# proto4-1pp.net
KiCad netlist of a schematic drawn in EAGLE
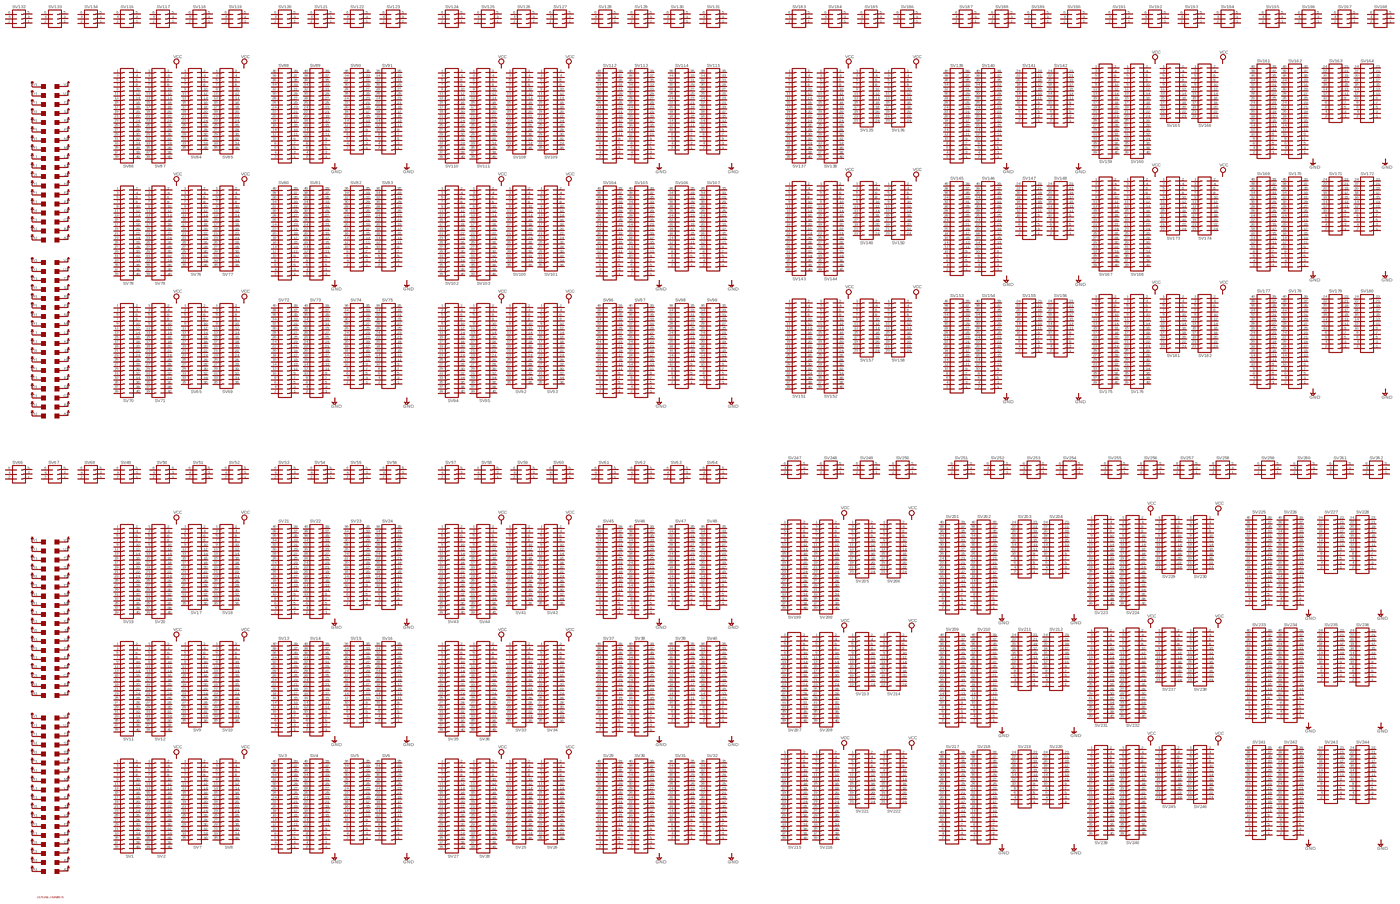
[diagram p0: schematic, sheet 1, overview]
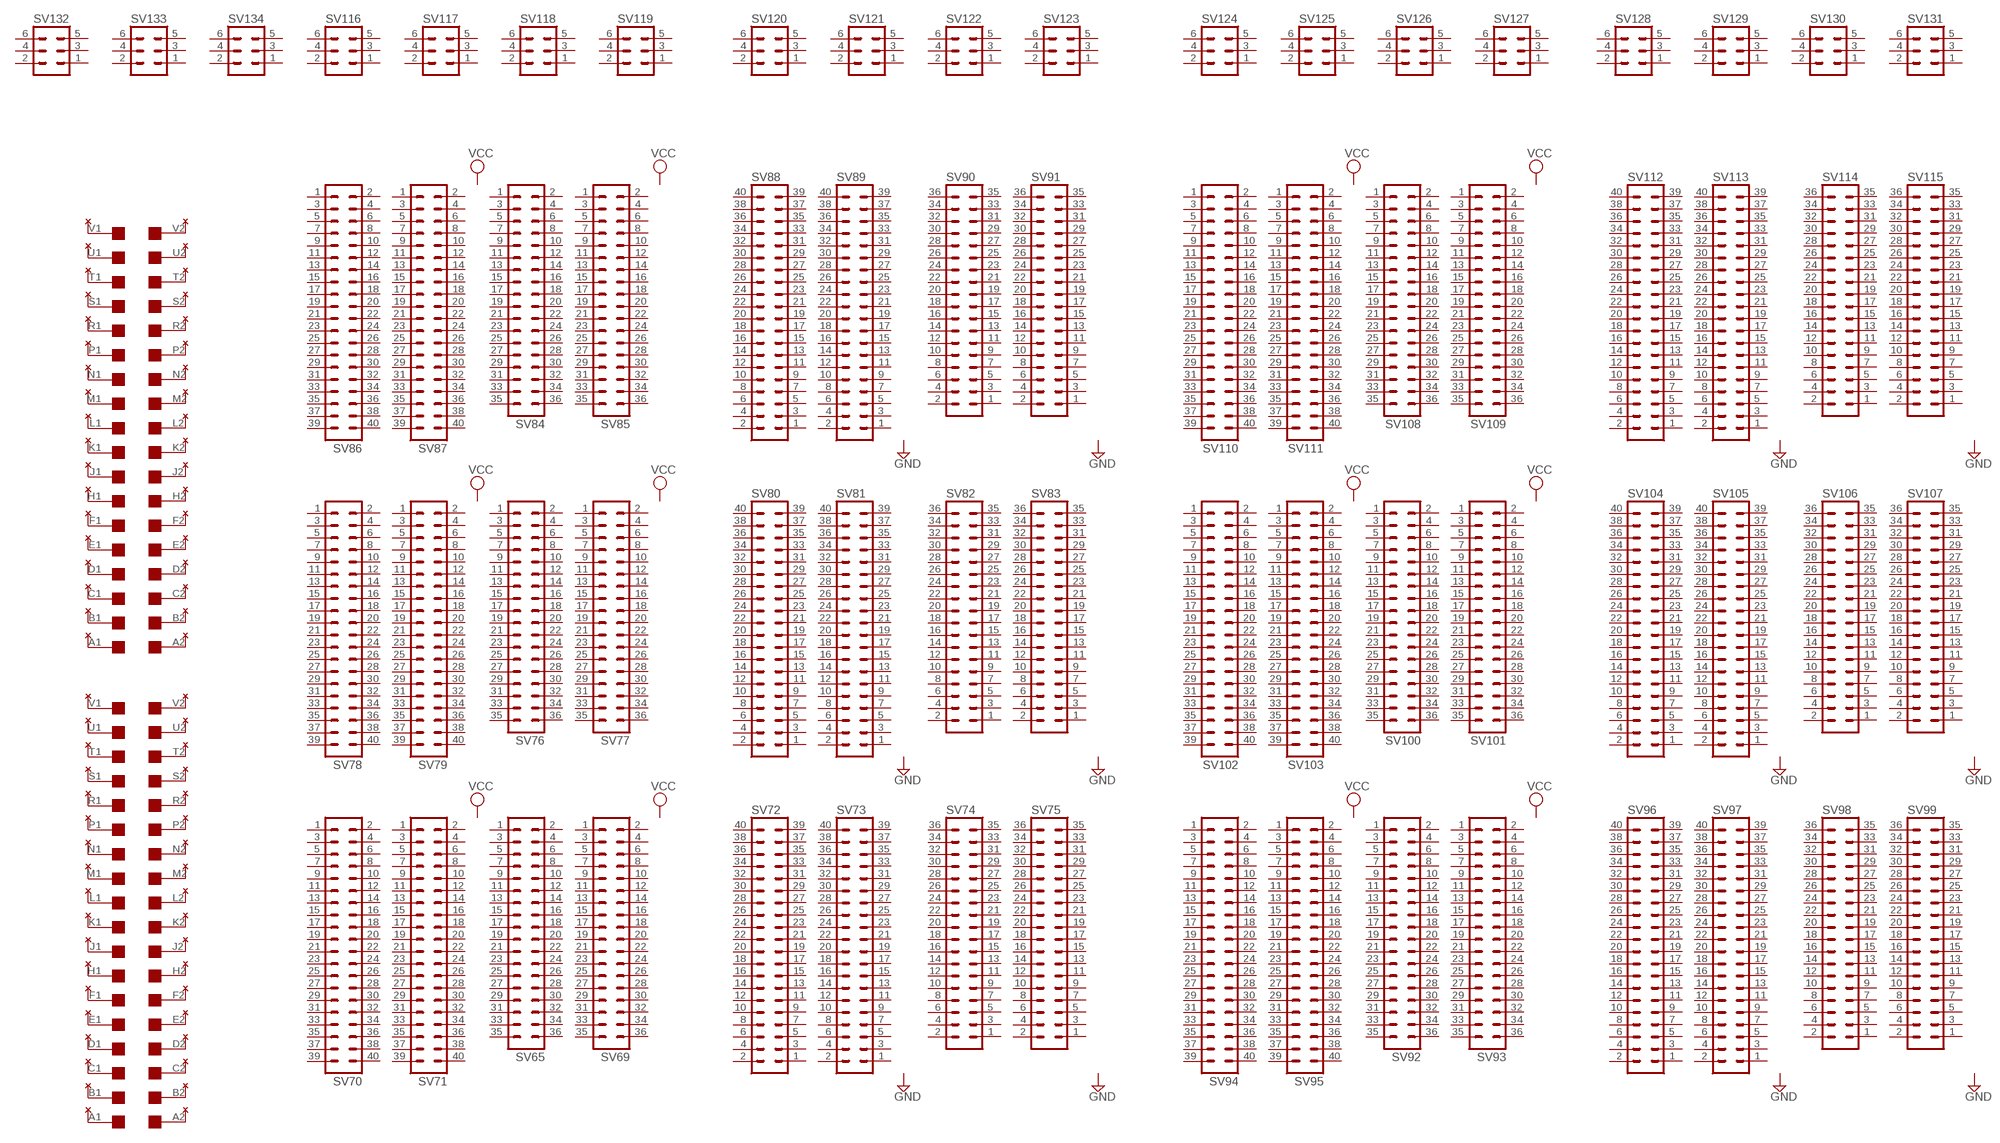
[diagram p1: schematic, sheet 1, part 1 of 4]
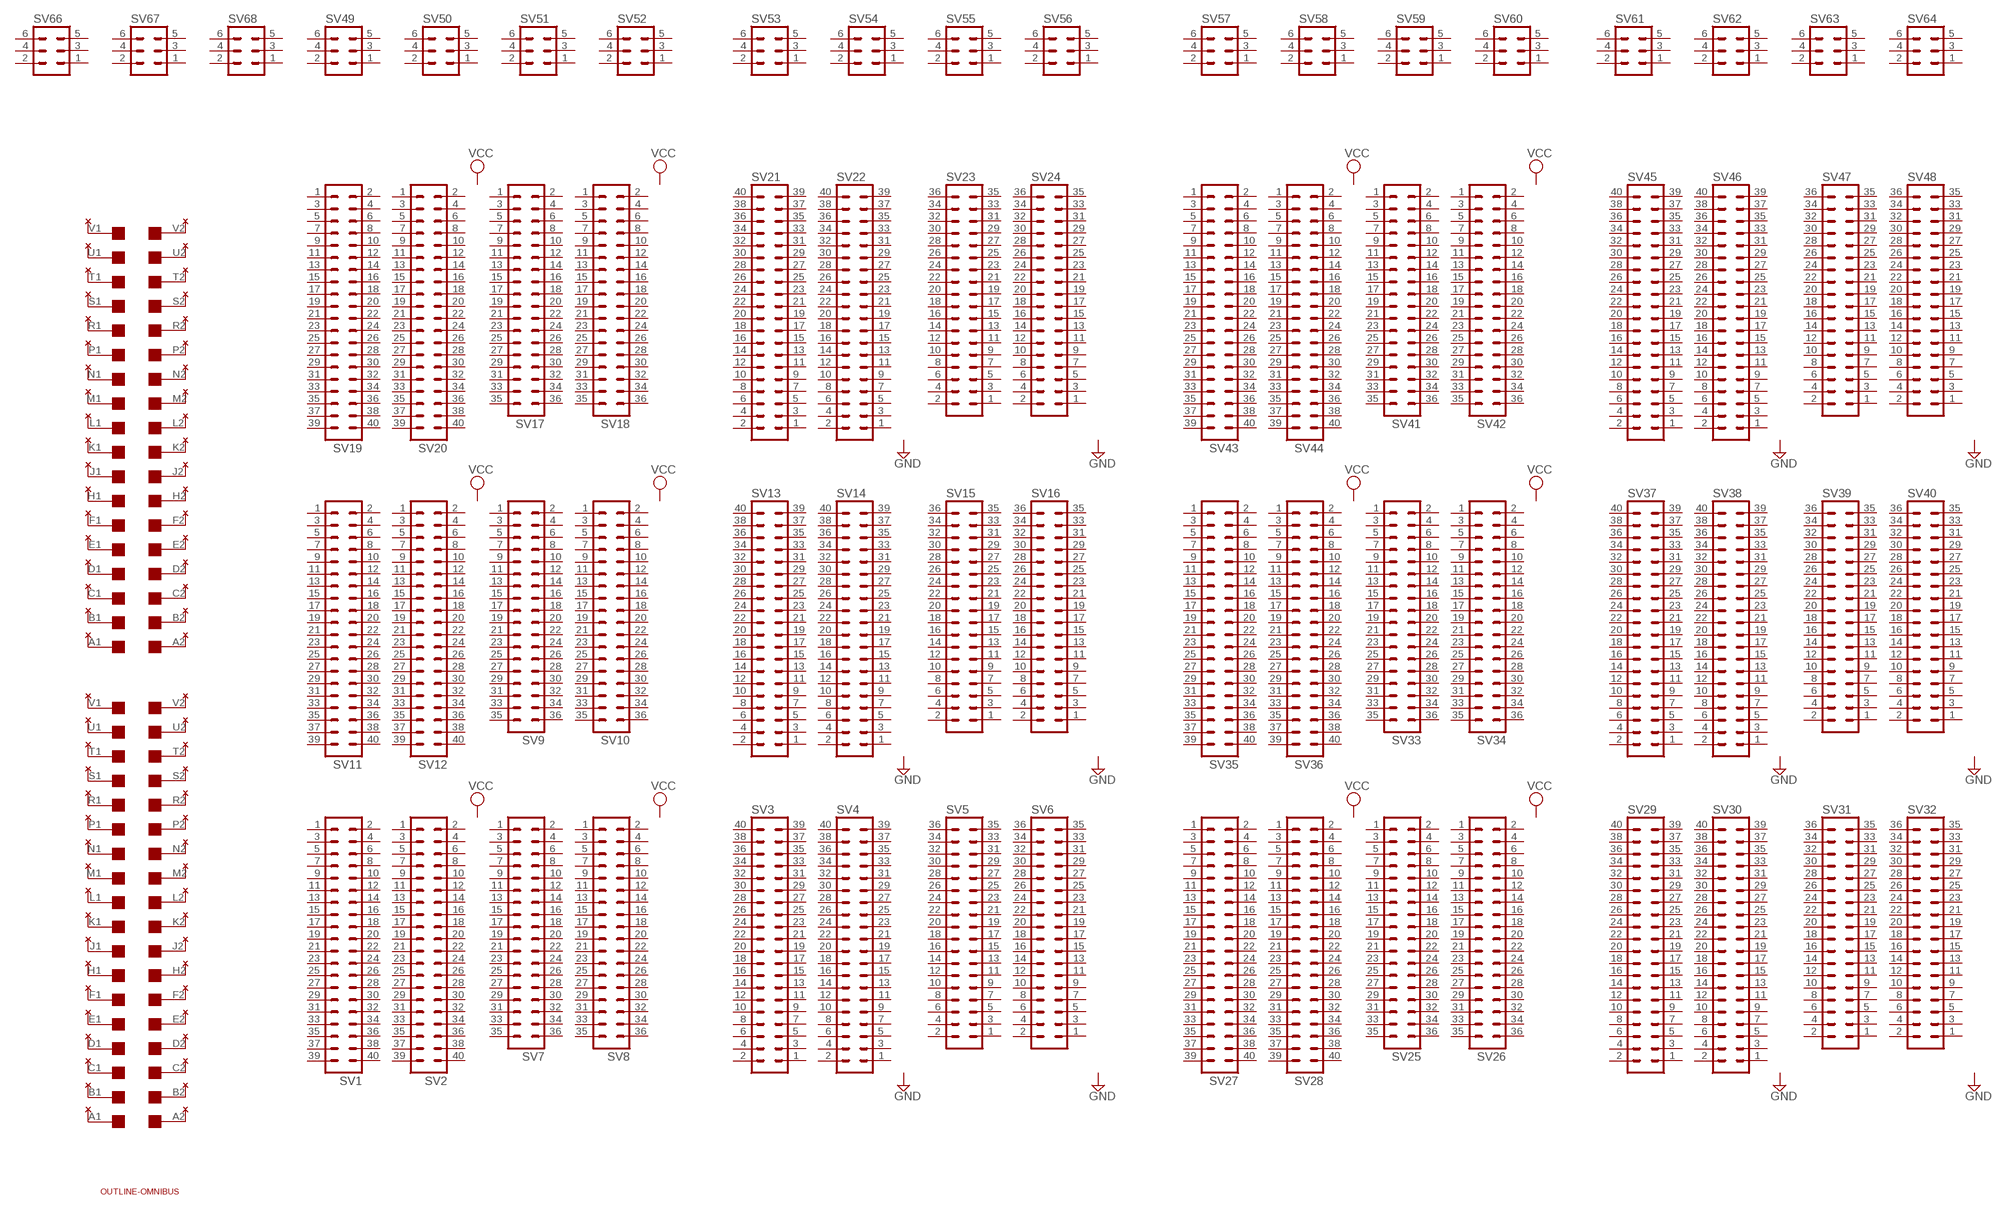
[diagram p2: schematic, sheet 1, part 2 of 4]
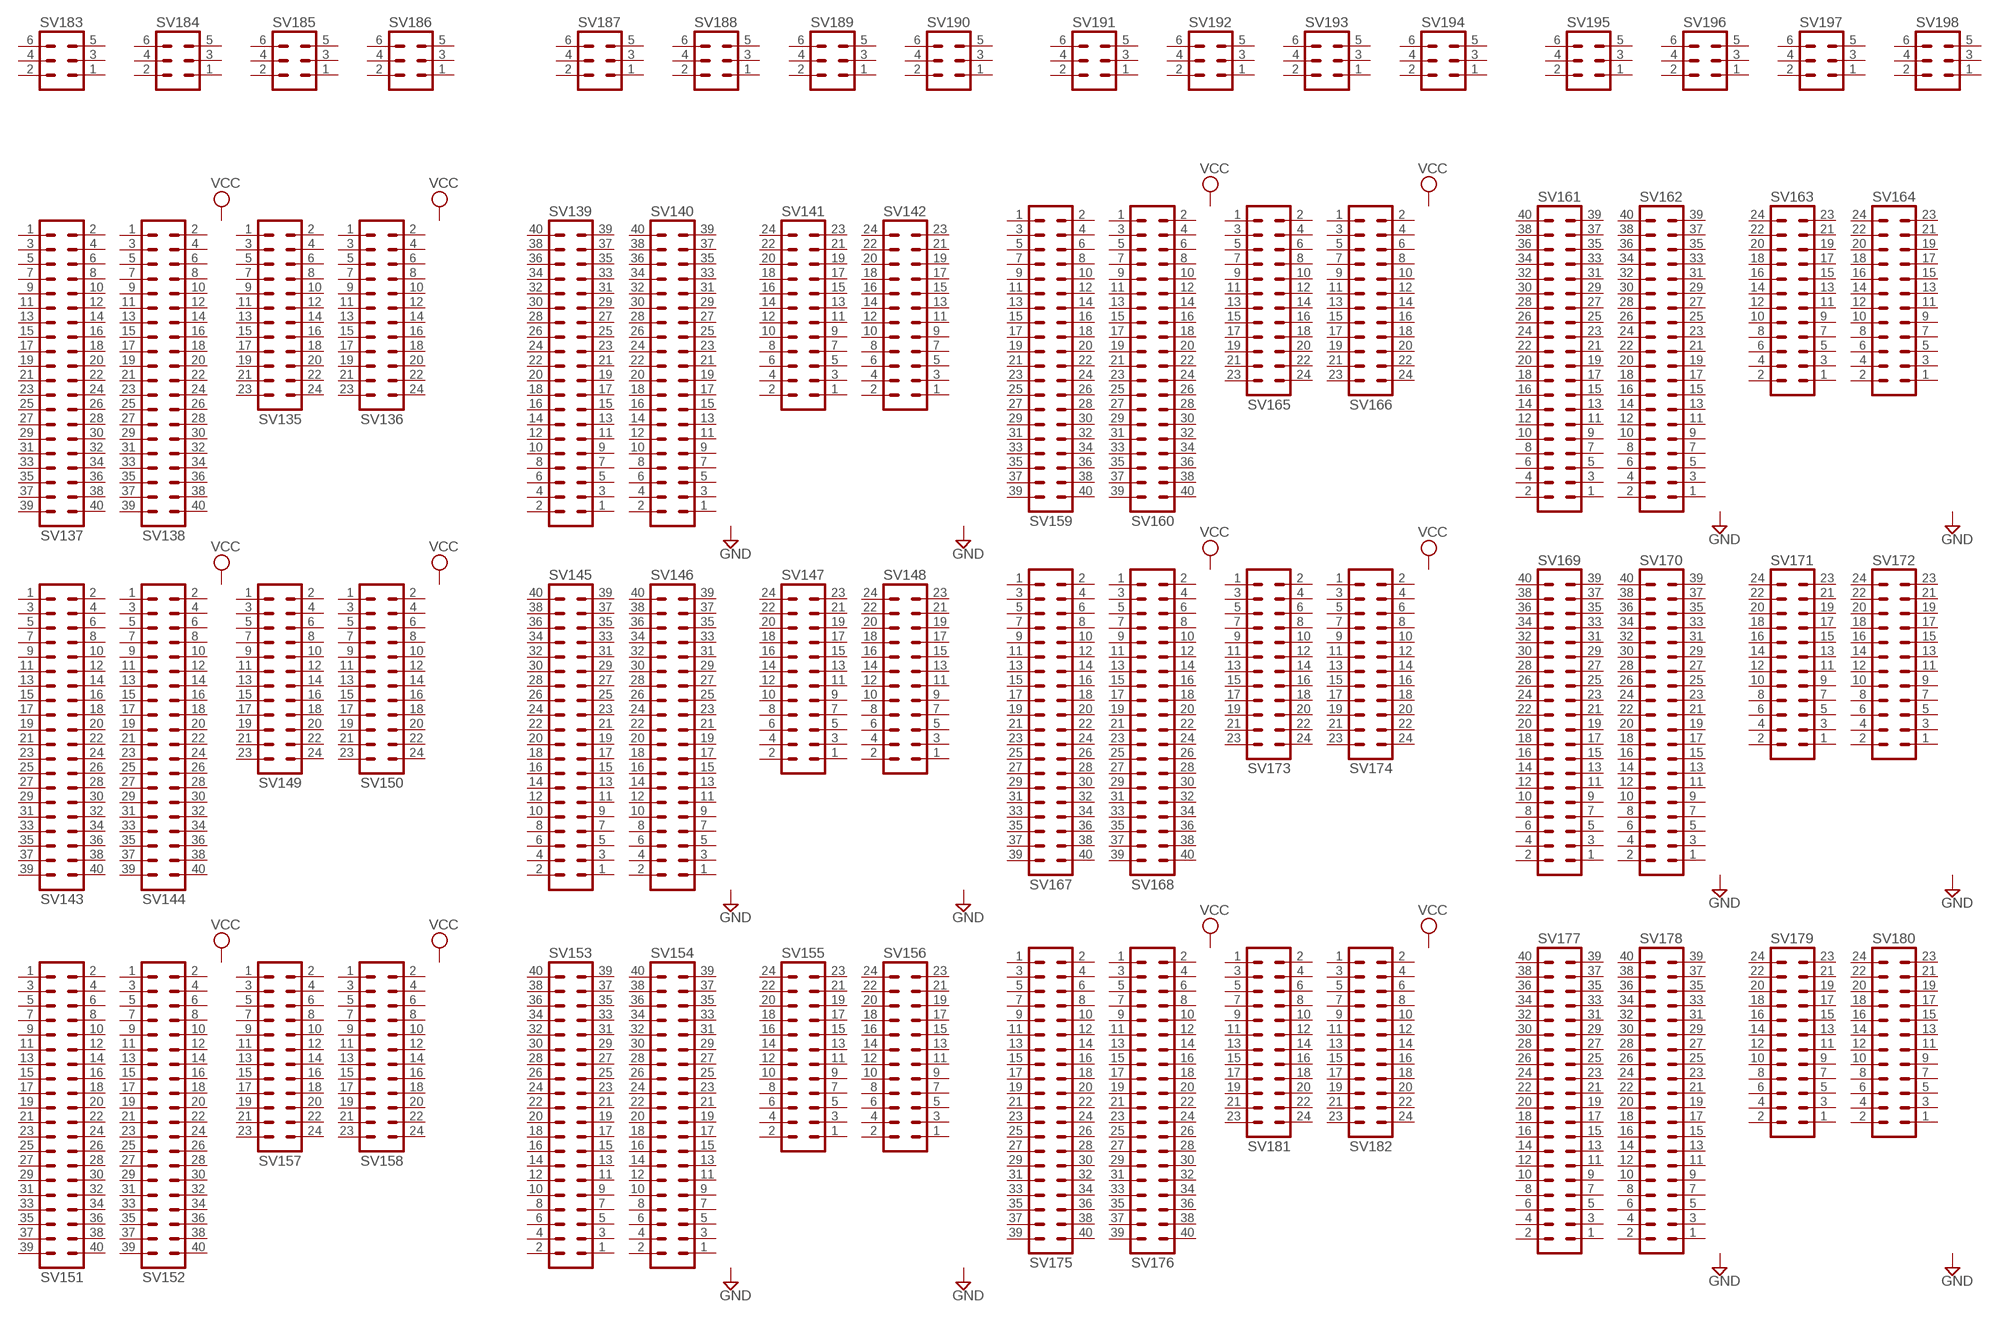
[diagram p3: schematic, sheet 1, part 3 of 4]
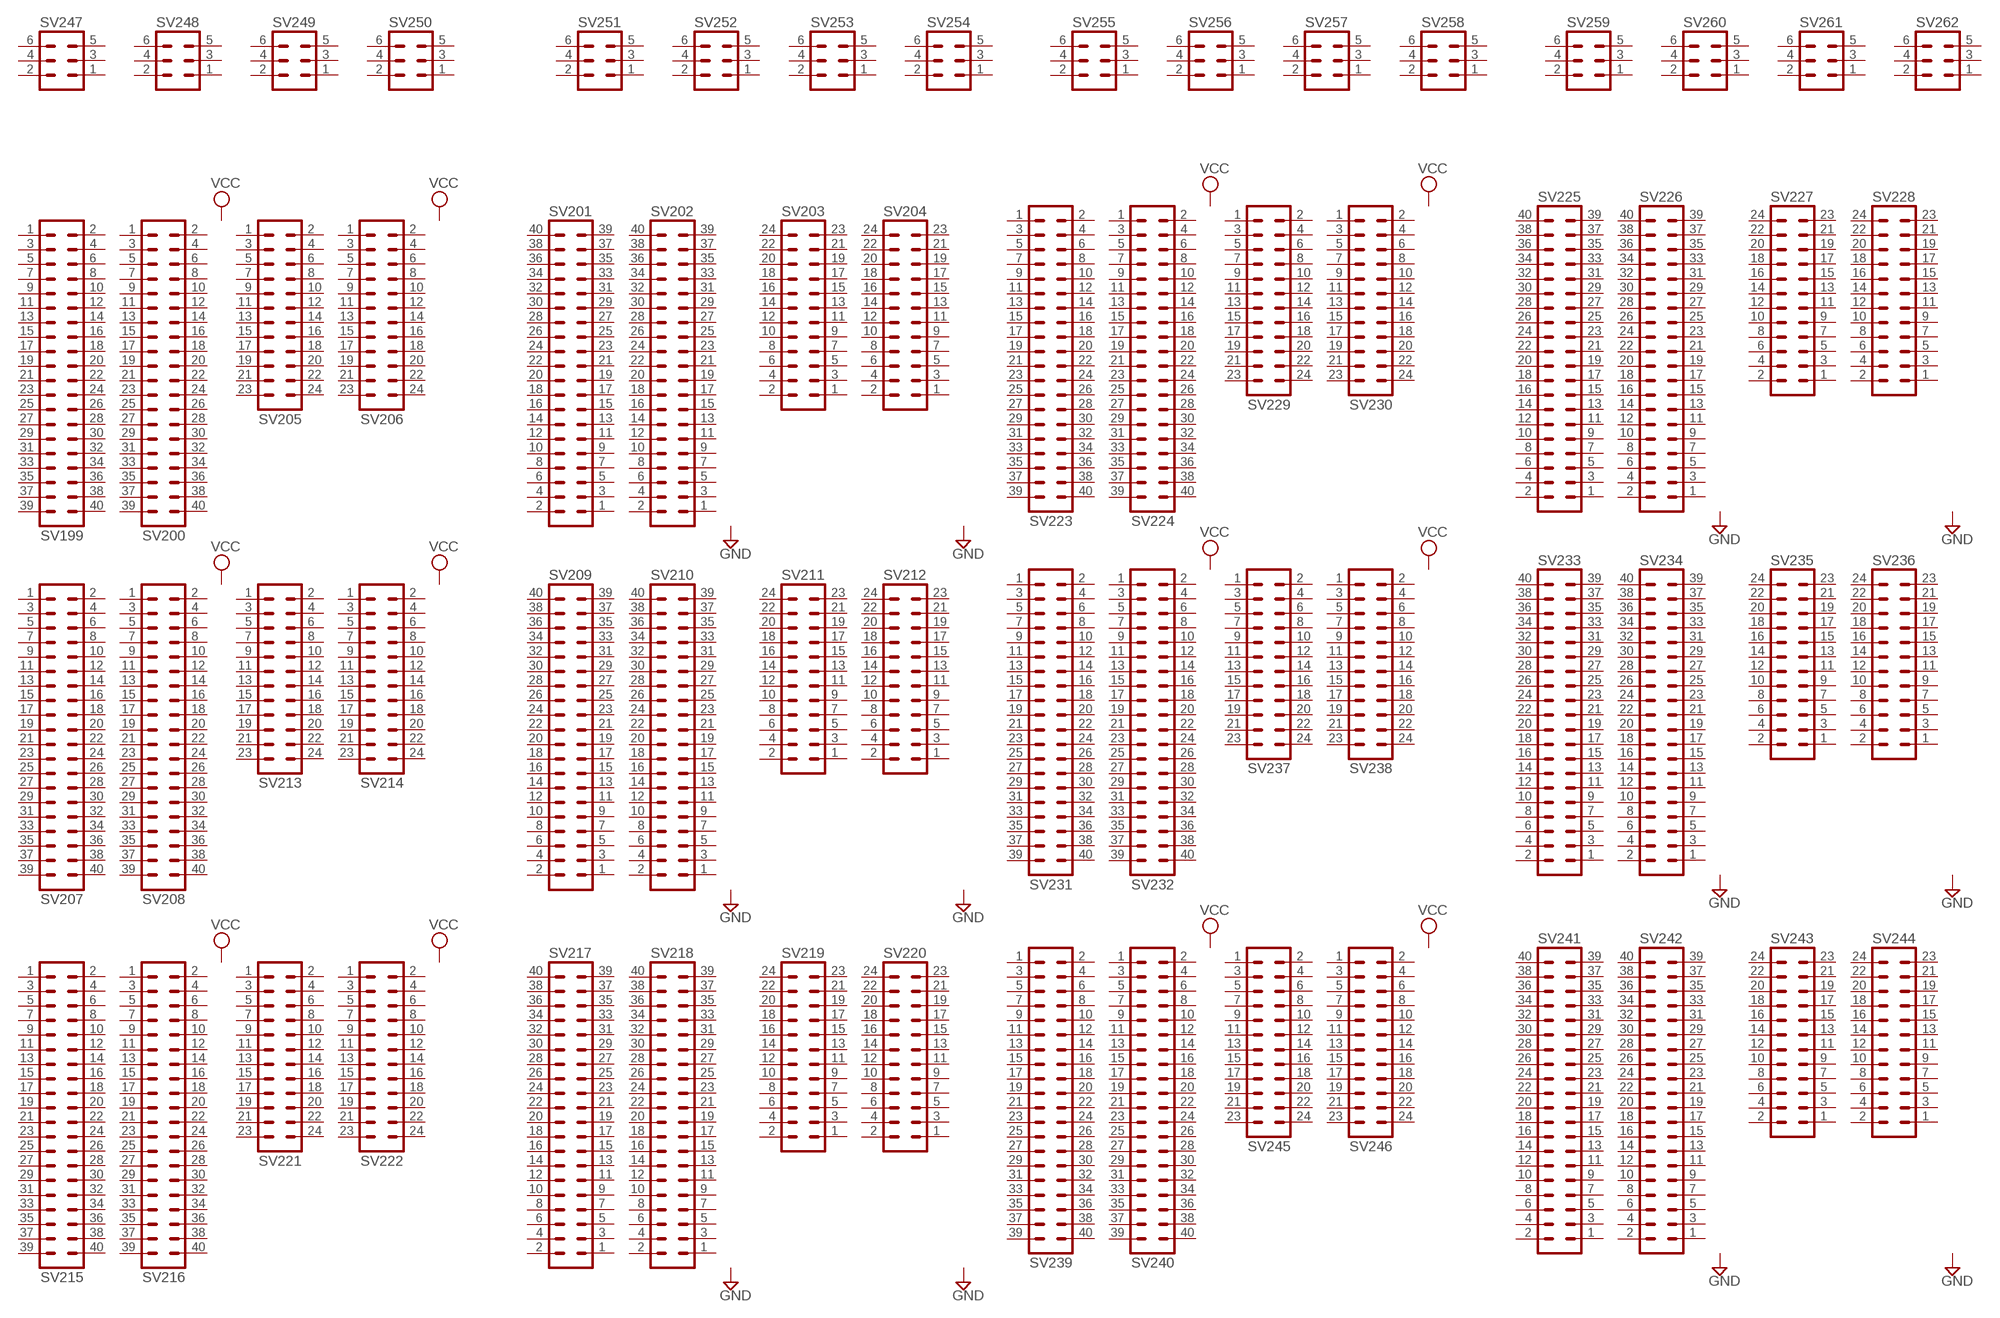
[diagram p4: schematic, sheet 1, part 4 of 4]

(export (version "E")
  (design (tool "Eeschema 10.0.6"))
  (components
    (comp (ref "A")
      (value "EDGE-2CONNECTOR")
      (footprint "eagle-import:EDGE-CON2")
      (libsource (lib "eagle-import") (part "EDGE-2CONNECTOR"))
    )
    (comp (ref "A1")
      (value "EDGE-2CONNECTOR")
      (footprint "eagle-import:EDGE-CON2")
      (libsource (lib "eagle-import") (part "EDGE-2CONNECTOR"))
    )
    (comp (ref "B")
      (value "EDGE-2CONNECTOR")
      (footprint "eagle-import:EDGE-CON2")
      (libsource (lib "eagle-import") (part "EDGE-2CONNECTOR"))
    )
    (comp (ref "B1")
      (value "EDGE-2CONNECTOR")
      (footprint "eagle-import:EDGE-CON2")
      (libsource (lib "eagle-import") (part "EDGE-2CONNECTOR"))
    )
    (comp (ref "SV1")
      (value "MA20-2")
      (footprint "eagle-import:MA20-2")
      (libsource (lib "eagle-import") (part "MA20-2"))
    )
    (comp (ref "SV2")
      (value "MA20-2")
      (footprint "eagle-import:MA20-2")
      (libsource (lib "eagle-import") (part "MA20-2"))
    )
    (comp (ref "SV3")
      (value "MA20-2")
      (footprint "eagle-import:MA20-2")
      (libsource (lib "eagle-import") (part "MA20-2"))
    )
    (comp (ref "SV4")
      (value "MA20-2")
      (footprint "eagle-import:MA20-2")
      (libsource (lib "eagle-import") (part "MA20-2"))
    )
    (comp (ref "SV5")
      (value "MA18-2")
      (footprint "eagle-import:MA18-2")
      (libsource (lib "eagle-import") (part "MA18-2"))
    )
    (comp (ref "SV6")
      (value "MA18-2")
      (footprint "eagle-import:MA18-2")
      (libsource (lib "eagle-import") (part "MA18-2"))
    )
    (comp (ref "SV7")
      (value "MA18-2")
      (footprint "eagle-import:MA18-2")
      (libsource (lib "eagle-import") (part "MA18-2"))
    )
    (comp (ref "SV8")
      (value "MA18-2")
      (footprint "eagle-import:MA18-2")
      (libsource (lib "eagle-import") (part "MA18-2"))
    )
    (comp (ref "SV9")
      (value "MA18-2")
      (footprint "eagle-import:MA18-2")
      (libsource (lib "eagle-import") (part "MA18-2"))
    )
    (comp (ref "SV10")
      (value "MA18-2")
      (footprint "eagle-import:MA18-2")
      (libsource (lib "eagle-import") (part "MA18-2"))
    )
    (comp (ref "SV11")
      (value "MA20-2")
      (footprint "eagle-import:MA20-2")
      (libsource (lib "eagle-import") (part "MA20-2"))
    )
    (comp (ref "SV12")
      (value "MA20-2")
      (footprint "eagle-import:MA20-2")
      (libsource (lib "eagle-import") (part "MA20-2"))
    )
    (comp (ref "SV13")
      (value "MA20-2")
      (footprint "eagle-import:MA20-2")
      (libsource (lib "eagle-import") (part "MA20-2"))
    )
    (comp (ref "SV14")
      (value "MA20-2")
      (footprint "eagle-import:MA20-2")
      (libsource (lib "eagle-import") (part "MA20-2"))
    )
    (comp (ref "SV15")
      (value "MA18-2")
      (footprint "eagle-import:MA18-2")
      (libsource (lib "eagle-import") (part "MA18-2"))
    )
    (comp (ref "SV16")
      (value "MA18-2")
      (footprint "eagle-import:MA18-2")
      (libsource (lib "eagle-import") (part "MA18-2"))
    )
    (comp (ref "SV17")
      (value "MA18-2")
      (footprint "eagle-import:MA18-2")
      (libsource (lib "eagle-import") (part "MA18-2"))
    )
    (comp (ref "SV18")
      (value "MA18-2")
      (footprint "eagle-import:MA18-2")
      (libsource (lib "eagle-import") (part "MA18-2"))
    )
    (comp (ref "SV19")
      (value "MA20-2")
      (footprint "eagle-import:MA20-2")
      (libsource (lib "eagle-import") (part "MA20-2"))
    )
    (comp (ref "SV20")
      (value "MA20-2")
      (footprint "eagle-import:MA20-2")
      (libsource (lib "eagle-import") (part "MA20-2"))
    )
    (comp (ref "SV21")
      (value "MA20-2")
      (footprint "eagle-import:MA20-2")
      (libsource (lib "eagle-import") (part "MA20-2"))
    )
    (comp (ref "SV22")
      (value "MA20-2")
      (footprint "eagle-import:MA20-2")
      (libsource (lib "eagle-import") (part "MA20-2"))
    )
    (comp (ref "SV23")
      (value "MA18-2")
      (footprint "eagle-import:MA18-2")
      (libsource (lib "eagle-import") (part "MA18-2"))
    )
    (comp (ref "SV24")
      (value "MA18-2")
      (footprint "eagle-import:MA18-2")
      (libsource (lib "eagle-import") (part "MA18-2"))
    )
    (comp (ref "SV25")
      (value "MA18-2")
      (footprint "eagle-import:MA18-2")
      (libsource (lib "eagle-import") (part "MA18-2"))
    )
    (comp (ref "SV26")
      (value "MA18-2")
      (footprint "eagle-import:MA18-2")
      (libsource (lib "eagle-import") (part "MA18-2"))
    )
    (comp (ref "SV27")
      (value "MA20-2")
      (footprint "eagle-import:MA20-2")
      (libsource (lib "eagle-import") (part "MA20-2"))
    )
    (comp (ref "SV28")
      (value "MA20-2")
      (footprint "eagle-import:MA20-2")
      (libsource (lib "eagle-import") (part "MA20-2"))
    )
    (comp (ref "SV29")
      (value "MA20-2")
      (footprint "eagle-import:MA20-2")
      (libsource (lib "eagle-import") (part "MA20-2"))
    )
    (comp (ref "SV30")
      (value "MA20-2")
      (footprint "eagle-import:MA20-2")
      (libsource (lib "eagle-import") (part "MA20-2"))
    )
    (comp (ref "SV31")
      (value "MA18-2")
      (footprint "eagle-import:MA18-2")
      (libsource (lib "eagle-import") (part "MA18-2"))
    )
    (comp (ref "SV32")
      (value "MA18-2")
      (footprint "eagle-import:MA18-2")
      (libsource (lib "eagle-import") (part "MA18-2"))
    )
    (comp (ref "SV33")
      (value "MA18-2")
      (footprint "eagle-import:MA18-2")
      (libsource (lib "eagle-import") (part "MA18-2"))
    )
    (comp (ref "SV34")
      (value "MA18-2")
      (footprint "eagle-import:MA18-2")
      (libsource (lib "eagle-import") (part "MA18-2"))
    )
    (comp (ref "SV35")
      (value "MA20-2")
      (footprint "eagle-import:MA20-2")
      (libsource (lib "eagle-import") (part "MA20-2"))
    )
    (comp (ref "SV36")
      (value "MA20-2")
      (footprint "eagle-import:MA20-2")
      (libsource (lib "eagle-import") (part "MA20-2"))
    )
    (comp (ref "SV37")
      (value "MA20-2")
      (footprint "eagle-import:MA20-2")
      (libsource (lib "eagle-import") (part "MA20-2"))
    )
    (comp (ref "SV38")
      (value "MA20-2")
      (footprint "eagle-import:MA20-2")
      (libsource (lib "eagle-import") (part "MA20-2"))
    )
    (comp (ref "SV39")
      (value "MA18-2")
      (footprint "eagle-import:MA18-2")
      (libsource (lib "eagle-import") (part "MA18-2"))
    )
    (comp (ref "SV40")
      (value "MA18-2")
      (footprint "eagle-import:MA18-2")
      (libsource (lib "eagle-import") (part "MA18-2"))
    )
    (comp (ref "SV41")
      (value "MA18-2")
      (footprint "eagle-import:MA18-2")
      (libsource (lib "eagle-import") (part "MA18-2"))
    )
    (comp (ref "SV42")
      (value "MA18-2")
      (footprint "eagle-import:MA18-2")
      (libsource (lib "eagle-import") (part "MA18-2"))
    )
    (comp (ref "SV43")
      (value "MA20-2")
      (footprint "eagle-import:MA20-2")
      (libsource (lib "eagle-import") (part "MA20-2"))
    )
    (comp (ref "SV44")
      (value "MA20-2")
      (footprint "eagle-import:MA20-2")
      (libsource (lib "eagle-import") (part "MA20-2"))
    )
    (comp (ref "SV45")
      (value "MA20-2")
      (footprint "eagle-import:MA20-2")
      (libsource (lib "eagle-import") (part "MA20-2"))
    )
    (comp (ref "SV46")
      (value "MA20-2")
      (footprint "eagle-import:MA20-2")
      (libsource (lib "eagle-import") (part "MA20-2"))
    )
    (comp (ref "SV47")
      (value "MA18-2")
      (footprint "eagle-import:MA18-2")
      (libsource (lib "eagle-import") (part "MA18-2"))
    )
    (comp (ref "SV48")
      (value "MA18-2")
      (footprint "eagle-import:MA18-2")
      (libsource (lib "eagle-import") (part "MA18-2"))
    )
    (comp (ref "SV49")
      (value "MA03-2")
      (footprint "eagle-import:MA03-2")
      (libsource (lib "eagle-import") (part "MA03-2"))
    )
    (comp (ref "SV50")
      (value "MA03-2")
      (footprint "eagle-import:MA03-2")
      (libsource (lib "eagle-import") (part "MA03-2"))
    )
    (comp (ref "SV51")
      (value "MA03-2")
      (footprint "eagle-import:MA03-2")
      (libsource (lib "eagle-import") (part "MA03-2"))
    )
    (comp (ref "SV52")
      (value "MA03-2")
      (footprint "eagle-import:MA03-2")
      (libsource (lib "eagle-import") (part "MA03-2"))
    )
    (comp (ref "SV53")
      (value "MA03-2")
      (footprint "eagle-import:MA03-2")
      (libsource (lib "eagle-import") (part "MA03-2"))
    )
    (comp (ref "SV54")
      (value "MA03-2")
      (footprint "eagle-import:MA03-2")
      (libsource (lib "eagle-import") (part "MA03-2"))
    )
    (comp (ref "SV55")
      (value "MA03-2")
      (footprint "eagle-import:MA03-2")
      (libsource (lib "eagle-import") (part "MA03-2"))
    )
    (comp (ref "SV56")
      (value "MA03-2")
      (footprint "eagle-import:MA03-2")
      (libsource (lib "eagle-import") (part "MA03-2"))
    )
    (comp (ref "SV57")
      (value "MA03-2")
      (footprint "eagle-import:MA03-2")
      (libsource (lib "eagle-import") (part "MA03-2"))
    )
    (comp (ref "SV58")
      (value "MA03-2")
      (footprint "eagle-import:MA03-2")
      (libsource (lib "eagle-import") (part "MA03-2"))
    )
    (comp (ref "SV59")
      (value "MA03-2")
      (footprint "eagle-import:MA03-2")
      (libsource (lib "eagle-import") (part "MA03-2"))
    )
    (comp (ref "SV60")
      (value "MA03-2")
      (footprint "eagle-import:MA03-2")
      (libsource (lib "eagle-import") (part "MA03-2"))
    )
    (comp (ref "SV61")
      (value "MA03-2")
      (footprint "eagle-import:MA03-2")
      (libsource (lib "eagle-import") (part "MA03-2"))
    )
    (comp (ref "SV62")
      (value "MA03-2")
      (footprint "eagle-import:MA03-2")
      (libsource (lib "eagle-import") (part "MA03-2"))
    )
    (comp (ref "SV63")
      (value "MA03-2")
      (footprint "eagle-import:MA03-2")
      (libsource (lib "eagle-import") (part "MA03-2"))
    )
    (comp (ref "SV64")
      (value "MA03-2")
      (footprint "eagle-import:MA03-2")
      (libsource (lib "eagle-import") (part "MA03-2"))
    )
    (comp (ref "SV65")
      (value "MA18-2")
      (footprint "eagle-import:MA18-2")
      (libsource (lib "eagle-import") (part "MA18-2"))
    )
    (comp (ref "SV66")
      (value "MA03-2")
      (footprint "eagle-import:MA03-2")
      (libsource (lib "eagle-import") (part "MA03-2"))
    )
    (comp (ref "SV67")
      (value "MA03-2")
      (footprint "eagle-import:MA03-2")
      (libsource (lib "eagle-import") (part "MA03-2"))
    )
    (comp (ref "SV68")
      (value "MA03-2")
      (footprint "eagle-import:MA03-2")
      (libsource (lib "eagle-import") (part "MA03-2"))
    )
    (comp (ref "SV69")
      (value "MA18-2")
      (footprint "eagle-import:MA18-2")
      (libsource (lib "eagle-import") (part "MA18-2"))
    )
    (comp (ref "SV70")
      (value "MA20-2")
      (footprint "eagle-import:MA20-2")
      (libsource (lib "eagle-import") (part "MA20-2"))
    )
    (comp (ref "SV71")
      (value "MA20-2")
      (footprint "eagle-import:MA20-2")
      (libsource (lib "eagle-import") (part "MA20-2"))
    )
    (comp (ref "SV72")
      (value "MA20-2")
      (footprint "eagle-import:MA20-2")
      (libsource (lib "eagle-import") (part "MA20-2"))
    )
    (comp (ref "SV73")
      (value "MA20-2")
      (footprint "eagle-import:MA20-2")
      (libsource (lib "eagle-import") (part "MA20-2"))
    )
    (comp (ref "SV74")
      (value "MA18-2")
      (footprint "eagle-import:MA18-2")
      (libsource (lib "eagle-import") (part "MA18-2"))
    )
    (comp (ref "SV75")
      (value "MA18-2")
      (footprint "eagle-import:MA18-2")
      (libsource (lib "eagle-import") (part "MA18-2"))
    )
    (comp (ref "SV76")
      (value "MA18-2")
      (footprint "eagle-import:MA18-2")
      (libsource (lib "eagle-import") (part "MA18-2"))
    )
    (comp (ref "SV77")
      (value "MA18-2")
      (footprint "eagle-import:MA18-2")
      (libsource (lib "eagle-import") (part "MA18-2"))
    )
    (comp (ref "SV78")
      (value "MA20-2")
      (footprint "eagle-import:MA20-2")
      (libsource (lib "eagle-import") (part "MA20-2"))
    )
    (comp (ref "SV79")
      (value "MA20-2")
      (footprint "eagle-import:MA20-2")
      (libsource (lib "eagle-import") (part "MA20-2"))
    )
    (comp (ref "SV80")
      (value "MA20-2")
      (footprint "eagle-import:MA20-2")
      (libsource (lib "eagle-import") (part "MA20-2"))
    )
    (comp (ref "SV81")
      (value "MA20-2")
      (footprint "eagle-import:MA20-2")
      (libsource (lib "eagle-import") (part "MA20-2"))
    )
    (comp (ref "SV82")
      (value "MA18-2")
      (footprint "eagle-import:MA18-2")
      (libsource (lib "eagle-import") (part "MA18-2"))
    )
    (comp (ref "SV83")
      (value "MA18-2")
      (footprint "eagle-import:MA18-2")
      (libsource (lib "eagle-import") (part "MA18-2"))
    )
    (comp (ref "SV84")
      (value "MA18-2")
      (footprint "eagle-import:MA18-2")
      (libsource (lib "eagle-import") (part "MA18-2"))
    )
    (comp (ref "SV85")
      (value "MA18-2")
      (footprint "eagle-import:MA18-2")
      (libsource (lib "eagle-import") (part "MA18-2"))
    )
    (comp (ref "SV86")
      (value "MA20-2")
      (footprint "eagle-import:MA20-2")
      (libsource (lib "eagle-import") (part "MA20-2"))
    )
    (comp (ref "SV87")
      (value "MA20-2")
      (footprint "eagle-import:MA20-2")
      (libsource (lib "eagle-import") (part "MA20-2"))
    )
    (comp (ref "SV88")
      (value "MA20-2")
      (footprint "eagle-import:MA20-2")
      (libsource (lib "eagle-import") (part "MA20-2"))
    )
    (comp (ref "SV89")
      (value "MA20-2")
      (footprint "eagle-import:MA20-2")
      (libsource (lib "eagle-import") (part "MA20-2"))
    )
    (comp (ref "SV90")
      (value "MA18-2")
      (footprint "eagle-import:MA18-2")
      (libsource (lib "eagle-import") (part "MA18-2"))
    )
    (comp (ref "SV91")
      (value "MA18-2")
      (footprint "eagle-import:MA18-2")
      (libsource (lib "eagle-import") (part "MA18-2"))
    )
    (comp (ref "SV92")
      (value "MA18-2")
      (footprint "eagle-import:MA18-2")
      (libsource (lib "eagle-import") (part "MA18-2"))
    )
    (comp (ref "SV93")
      (value "MA18-2")
      (footprint "eagle-import:MA18-2")
      (libsource (lib "eagle-import") (part "MA18-2"))
    )
    (comp (ref "SV94")
      (value "MA20-2")
      (footprint "eagle-import:MA20-2")
      (libsource (lib "eagle-import") (part "MA20-2"))
    )
    (comp (ref "SV95")
      (value "MA20-2")
      (footprint "eagle-import:MA20-2")
      (libsource (lib "eagle-import") (part "MA20-2"))
    )
    (comp (ref "SV96")
      (value "MA20-2")
      (footprint "eagle-import:MA20-2")
      (libsource (lib "eagle-import") (part "MA20-2"))
    )
    (comp (ref "SV97")
      (value "MA20-2")
      (footprint "eagle-import:MA20-2")
      (libsource (lib "eagle-import") (part "MA20-2"))
    )
    (comp (ref "SV98")
      (value "MA18-2")
      (footprint "eagle-import:MA18-2")
      (libsource (lib "eagle-import") (part "MA18-2"))
    )
    (comp (ref "SV99")
      (value "MA18-2")
      (footprint "eagle-import:MA18-2")
      (libsource (lib "eagle-import") (part "MA18-2"))
    )
    (comp (ref "SV100")
      (value "MA18-2")
      (footprint "eagle-import:MA18-2")
      (libsource (lib "eagle-import") (part "MA18-2"))
    )
    (comp (ref "SV101")
      (value "MA18-2")
      (footprint "eagle-import:MA18-2")
      (libsource (lib "eagle-import") (part "MA18-2"))
    )
    (comp (ref "SV102")
      (value "MA20-2")
      (footprint "eagle-import:MA20-2")
      (libsource (lib "eagle-import") (part "MA20-2"))
    )
    (comp (ref "SV103")
      (value "MA20-2")
      (footprint "eagle-import:MA20-2")
      (libsource (lib "eagle-import") (part "MA20-2"))
    )
    (comp (ref "SV104")
      (value "MA20-2")
      (footprint "eagle-import:MA20-2")
      (libsource (lib "eagle-import") (part "MA20-2"))
    )
    (comp (ref "SV105")
      (value "MA20-2")
      (footprint "eagle-import:MA20-2")
      (libsource (lib "eagle-import") (part "MA20-2"))
    )
    (comp (ref "SV106")
      (value "MA18-2")
      (footprint "eagle-import:MA18-2")
      (libsource (lib "eagle-import") (part "MA18-2"))
    )
    (comp (ref "SV107")
      (value "MA18-2")
      (footprint "eagle-import:MA18-2")
      (libsource (lib "eagle-import") (part "MA18-2"))
    )
    (comp (ref "SV108")
      (value "MA18-2")
      (footprint "eagle-import:MA18-2")
      (libsource (lib "eagle-import") (part "MA18-2"))
    )
    (comp (ref "SV109")
      (value "MA18-2")
      (footprint "eagle-import:MA18-2")
      (libsource (lib "eagle-import") (part "MA18-2"))
    )
    (comp (ref "SV110")
      (value "MA20-2")
      (footprint "eagle-import:MA20-2")
      (libsource (lib "eagle-import") (part "MA20-2"))
    )
    (comp (ref "SV111")
      (value "MA20-2")
      (footprint "eagle-import:MA20-2")
      (libsource (lib "eagle-import") (part "MA20-2"))
    )
    (comp (ref "SV112")
      (value "MA20-2")
      (footprint "eagle-import:MA20-2")
      (libsource (lib "eagle-import") (part "MA20-2"))
    )
    (comp (ref "SV113")
      (value "MA20-2")
      (footprint "eagle-import:MA20-2")
      (libsource (lib "eagle-import") (part "MA20-2"))
    )
    (comp (ref "SV114")
      (value "MA18-2")
      (footprint "eagle-import:MA18-2")
      (libsource (lib "eagle-import") (part "MA18-2"))
    )
    (comp (ref "SV115")
      (value "MA18-2")
      (footprint "eagle-import:MA18-2")
      (libsource (lib "eagle-import") (part "MA18-2"))
    )
    (comp (ref "SV116")
      (value "MA03-2")
      (footprint "eagle-import:MA03-2")
      (libsource (lib "eagle-import") (part "MA03-2"))
    )
    (comp (ref "SV117")
      (value "MA03-2")
      (footprint "eagle-import:MA03-2")
      (libsource (lib "eagle-import") (part "MA03-2"))
    )
    (comp (ref "SV118")
      (value "MA03-2")
      (footprint "eagle-import:MA03-2")
      (libsource (lib "eagle-import") (part "MA03-2"))
    )
    (comp (ref "SV119")
      (value "MA03-2")
      (footprint "eagle-import:MA03-2")
      (libsource (lib "eagle-import") (part "MA03-2"))
    )
    (comp (ref "SV120")
      (value "MA03-2")
      (footprint "eagle-import:MA03-2")
      (libsource (lib "eagle-import") (part "MA03-2"))
    )
    (comp (ref "SV121")
      (value "MA03-2")
      (footprint "eagle-import:MA03-2")
      (libsource (lib "eagle-import") (part "MA03-2"))
    )
    (comp (ref "SV122")
      (value "MA03-2")
      (footprint "eagle-import:MA03-2")
      (libsource (lib "eagle-import") (part "MA03-2"))
    )
    (comp (ref "SV123")
      (value "MA03-2")
      (footprint "eagle-import:MA03-2")
      (libsource (lib "eagle-import") (part "MA03-2"))
    )
    (comp (ref "SV124")
      (value "MA03-2")
      (footprint "eagle-import:MA03-2")
      (libsource (lib "eagle-import") (part "MA03-2"))
    )
    (comp (ref "SV125")
      (value "MA03-2")
      (footprint "eagle-import:MA03-2")
      (libsource (lib "eagle-import") (part "MA03-2"))
    )
    (comp (ref "SV126")
      (value "MA03-2")
      (footprint "eagle-import:MA03-2")
      (libsource (lib "eagle-import") (part "MA03-2"))
    )
    (comp (ref "SV127")
      (value "MA03-2")
      (footprint "eagle-import:MA03-2")
      (libsource (lib "eagle-import") (part "MA03-2"))
    )
    (comp (ref "SV128")
      (value "MA03-2")
      (footprint "eagle-import:MA03-2")
      (libsource (lib "eagle-import") (part "MA03-2"))
    )
    (comp (ref "SV129")
      (value "MA03-2")
      (footprint "eagle-import:MA03-2")
      (libsource (lib "eagle-import") (part "MA03-2"))
    )
    (comp (ref "SV130")
      (value "MA03-2")
      (footprint "eagle-import:MA03-2")
      (libsource (lib "eagle-import") (part "MA03-2"))
    )
    (comp (ref "SV131")
      (value "MA03-2")
      (footprint "eagle-import:MA03-2")
      (libsource (lib "eagle-import") (part "MA03-2"))
    )
    (comp (ref "SV132")
      (value "MA03-2")
      (footprint "eagle-import:MA03-2")
      (libsource (lib "eagle-import") (part "MA03-2"))
    )
    (comp (ref "SV133")
      (value "MA03-2")
      (footprint "eagle-import:MA03-2")
      (libsource (lib "eagle-import") (part "MA03-2"))
    )
    (comp (ref "SV134")
      (value "MA03-2")
      (footprint "eagle-import:MA03-2")
      (libsource (lib "eagle-import") (part "MA03-2"))
    )
    (comp (ref "SV135")
      (value "MA12-2")
      (footprint "eagle-import:MA12-2")
      (libsource (lib "eagle-import") (part "MA12-2"))
    )
    (comp (ref "SV136")
      (value "MA12-2")
      (footprint "eagle-import:MA12-2")
      (libsource (lib "eagle-import") (part "MA12-2"))
    )
    (comp (ref "SV137")
      (value "MA20-2")
      (footprint "eagle-import:MA20-2")
      (libsource (lib "eagle-import") (part "MA20-2"))
    )
    (comp (ref "SV138")
      (value "MA20-2")
      (footprint "eagle-import:MA20-2")
      (libsource (lib "eagle-import") (part "MA20-2"))
    )
    (comp (ref "SV139")
      (value "MA20-2")
      (footprint "eagle-import:MA20-2")
      (libsource (lib "eagle-import") (part "MA20-2"))
    )
    (comp (ref "SV140")
      (value "MA20-2")
      (footprint "eagle-import:MA20-2")
      (libsource (lib "eagle-import") (part "MA20-2"))
    )
    (comp (ref "SV141")
      (value "MA12-2")
      (footprint "eagle-import:MA12-2")
      (libsource (lib "eagle-import") (part "MA12-2"))
    )
    (comp (ref "SV142")
      (value "MA12-2")
      (footprint "eagle-import:MA12-2")
      (libsource (lib "eagle-import") (part "MA12-2"))
    )
    (comp (ref "SV143")
      (value "MA20-2")
      (footprint "eagle-import:MA20-2")
      (libsource (lib "eagle-import") (part "MA20-2"))
    )
    (comp (ref "SV144")
      (value "MA20-2")
      (footprint "eagle-import:MA20-2")
      (libsource (lib "eagle-import") (part "MA20-2"))
    )
    (comp (ref "SV145")
      (value "MA20-2")
      (footprint "eagle-import:MA20-2")
      (libsource (lib "eagle-import") (part "MA20-2"))
    )
    (comp (ref "SV146")
      (value "MA20-2")
      (footprint "eagle-import:MA20-2")
      (libsource (lib "eagle-import") (part "MA20-2"))
    )
    (comp (ref "SV147")
      (value "MA12-2")
      (footprint "eagle-import:MA12-2")
      (libsource (lib "eagle-import") (part "MA12-2"))
    )
    (comp (ref "SV148")
      (value "MA12-2")
      (footprint "eagle-import:MA12-2")
      (libsource (lib "eagle-import") (part "MA12-2"))
    )
    (comp (ref "SV149")
      (value "MA12-2")
      (footprint "eagle-import:MA12-2")
      (libsource (lib "eagle-import") (part "MA12-2"))
    )
    (comp (ref "SV150")
      (value "MA12-2")
      (footprint "eagle-import:MA12-2")
      (libsource (lib "eagle-import") (part "MA12-2"))
    )
    (comp (ref "SV151")
      (value "MA20-2")
      (footprint "eagle-import:MA20-2")
      (libsource (lib "eagle-import") (part "MA20-2"))
    )
    (comp (ref "SV152")
      (value "MA20-2")
      (footprint "eagle-import:MA20-2")
      (libsource (lib "eagle-import") (part "MA20-2"))
    )
    (comp (ref "SV153")
      (value "MA20-2")
      (footprint "eagle-import:MA20-2")
      (libsource (lib "eagle-import") (part "MA20-2"))
    )
    (comp (ref "SV154")
      (value "MA20-2")
      (footprint "eagle-import:MA20-2")
      (libsource (lib "eagle-import") (part "MA20-2"))
    )
    (comp (ref "SV155")
      (value "MA12-2")
      (footprint "eagle-import:MA12-2")
      (libsource (lib "eagle-import") (part "MA12-2"))
    )
    (comp (ref "SV156")
      (value "MA12-2")
      (footprint "eagle-import:MA12-2")
      (libsource (lib "eagle-import") (part "MA12-2"))
    )
    (comp (ref "SV157")
      (value "MA12-2")
      (footprint "eagle-import:MA12-2")
      (libsource (lib "eagle-import") (part "MA12-2"))
    )
    (comp (ref "SV158")
      (value "MA12-2")
      (footprint "eagle-import:MA12-2")
      (libsource (lib "eagle-import") (part "MA12-2"))
    )
    (comp (ref "SV159")
      (value "MA20-2")
      (footprint "eagle-import:MA20-2")
      (libsource (lib "eagle-import") (part "MA20-2"))
    )
    (comp (ref "SV160")
      (value "MA20-2")
      (footprint "eagle-import:MA20-2")
      (libsource (lib "eagle-import") (part "MA20-2"))
    )
    (comp (ref "SV161")
      (value "MA20-2")
      (footprint "eagle-import:MA20-2")
      (libsource (lib "eagle-import") (part "MA20-2"))
    )
    (comp (ref "SV162")
      (value "MA20-2")
      (footprint "eagle-import:MA20-2")
      (libsource (lib "eagle-import") (part "MA20-2"))
    )
    (comp (ref "SV163")
      (value "MA12-2")
      (footprint "eagle-import:MA12-2")
      (libsource (lib "eagle-import") (part "MA12-2"))
    )
    (comp (ref "SV164")
      (value "MA12-2")
      (footprint "eagle-import:MA12-2")
      (libsource (lib "eagle-import") (part "MA12-2"))
    )
    (comp (ref "SV165")
      (value "MA12-2")
      (footprint "eagle-import:MA12-2")
      (libsource (lib "eagle-import") (part "MA12-2"))
    )
    (comp (ref "SV166")
      (value "MA12-2")
      (footprint "eagle-import:MA12-2")
      (libsource (lib "eagle-import") (part "MA12-2"))
    )
    (comp (ref "SV167")
      (value "MA20-2")
      (footprint "eagle-import:MA20-2")
      (libsource (lib "eagle-import") (part "MA20-2"))
    )
    (comp (ref "SV168")
      (value "MA20-2")
      (footprint "eagle-import:MA20-2")
      (libsource (lib "eagle-import") (part "MA20-2"))
    )
    (comp (ref "SV169")
      (value "MA20-2")
      (footprint "eagle-import:MA20-2")
      (libsource (lib "eagle-import") (part "MA20-2"))
    )
    (comp (ref "SV170")
      (value "MA20-2")
      (footprint "eagle-import:MA20-2")
      (libsource (lib "eagle-import") (part "MA20-2"))
    )
    (comp (ref "SV171")
      (value "MA12-2")
      (footprint "eagle-import:MA12-2")
      (libsource (lib "eagle-import") (part "MA12-2"))
    )
    (comp (ref "SV172")
      (value "MA12-2")
      (footprint "eagle-import:MA12-2")
      (libsource (lib "eagle-import") (part "MA12-2"))
    )
    (comp (ref "SV173")
      (value "MA12-2")
      (footprint "eagle-import:MA12-2")
      (libsource (lib "eagle-import") (part "MA12-2"))
    )
    (comp (ref "SV174")
      (value "MA12-2")
      (footprint "eagle-import:MA12-2")
      (libsource (lib "eagle-import") (part "MA12-2"))
    )
    (comp (ref "SV175")
      (value "MA20-2")
      (footprint "eagle-import:MA20-2")
      (libsource (lib "eagle-import") (part "MA20-2"))
    )
    (comp (ref "SV176")
      (value "MA20-2")
      (footprint "eagle-import:MA20-2")
      (libsource (lib "eagle-import") (part "MA20-2"))
    )
    (comp (ref "SV177")
      (value "MA20-2")
      (footprint "eagle-import:MA20-2")
      (libsource (lib "eagle-import") (part "MA20-2"))
    )
    (comp (ref "SV178")
      (value "MA20-2")
      (footprint "eagle-import:MA20-2")
      (libsource (lib "eagle-import") (part "MA20-2"))
    )
    (comp (ref "SV179")
      (value "MA12-2")
      (footprint "eagle-import:MA12-2")
      (libsource (lib "eagle-import") (part "MA12-2"))
    )
    (comp (ref "SV180")
      (value "MA12-2")
      (footprint "eagle-import:MA12-2")
      (libsource (lib "eagle-import") (part "MA12-2"))
    )
    (comp (ref "SV181")
      (value "MA12-2")
      (footprint "eagle-import:MA12-2")
      (libsource (lib "eagle-import") (part "MA12-2"))
    )
    (comp (ref "SV182")
      (value "MA12-2")
      (footprint "eagle-import:MA12-2")
      (libsource (lib "eagle-import") (part "MA12-2"))
    )
    (comp (ref "SV183")
      (value "MA03-2")
      (footprint "eagle-import:MA03-2")
      (libsource (lib "eagle-import") (part "MA03-2"))
    )
    (comp (ref "SV184")
      (value "MA03-2")
      (footprint "eagle-import:MA03-2")
      (libsource (lib "eagle-import") (part "MA03-2"))
    )
    (comp (ref "SV185")
      (value "MA03-2")
      (footprint "eagle-import:MA03-2")
      (libsource (lib "eagle-import") (part "MA03-2"))
    )
    (comp (ref "SV186")
      (value "MA03-2")
      (footprint "eagle-import:MA03-2")
      (libsource (lib "eagle-import") (part "MA03-2"))
    )
    (comp (ref "SV187")
      (value "MA03-2")
      (footprint "eagle-import:MA03-2")
      (libsource (lib "eagle-import") (part "MA03-2"))
    )
    (comp (ref "SV188")
      (value "MA03-2")
      (footprint "eagle-import:MA03-2")
      (libsource (lib "eagle-import") (part "MA03-2"))
    )
    (comp (ref "SV189")
      (value "MA03-2")
      (footprint "eagle-import:MA03-2")
      (libsource (lib "eagle-import") (part "MA03-2"))
    )
    (comp (ref "SV190")
      (value "MA03-2")
      (footprint "eagle-import:MA03-2")
      (libsource (lib "eagle-import") (part "MA03-2"))
    )
    (comp (ref "SV191")
      (value "MA03-2")
      (footprint "eagle-import:MA03-2")
      (libsource (lib "eagle-import") (part "MA03-2"))
    )
    (comp (ref "SV192")
      (value "MA03-2")
      (footprint "eagle-import:MA03-2")
      (libsource (lib "eagle-import") (part "MA03-2"))
    )
    (comp (ref "SV193")
      (value "MA03-2")
      (footprint "eagle-import:MA03-2")
      (libsource (lib "eagle-import") (part "MA03-2"))
    )
    (comp (ref "SV194")
      (value "MA03-2")
      (footprint "eagle-import:MA03-2")
      (libsource (lib "eagle-import") (part "MA03-2"))
    )
    (comp (ref "SV195")
      (value "MA03-2")
      (footprint "eagle-import:MA03-2")
      (libsource (lib "eagle-import") (part "MA03-2"))
    )
    (comp (ref "SV196")
      (value "MA03-2")
      (footprint "eagle-import:MA03-2")
      (libsource (lib "eagle-import") (part "MA03-2"))
    )
    (comp (ref "SV197")
      (value "MA03-2")
      (footprint "eagle-import:MA03-2")
      (libsource (lib "eagle-import") (part "MA03-2"))
    )
    (comp (ref "SV198")
      (value "MA03-2")
      (footprint "eagle-import:MA03-2")
      (libsource (lib "eagle-import") (part "MA03-2"))
    )
    (comp (ref "SV199")
      (value "MA20-2")
      (footprint "eagle-import:MA20-2")
      (libsource (lib "eagle-import") (part "MA20-2"))
    )
    (comp (ref "SV200")
      (value "MA20-2")
      (footprint "eagle-import:MA20-2")
      (libsource (lib "eagle-import") (part "MA20-2"))
    )
    (comp (ref "SV201")
      (value "MA20-2")
      (footprint "eagle-import:MA20-2")
      (libsource (lib "eagle-import") (part "MA20-2"))
    )
    (comp (ref "SV202")
      (value "MA20-2")
      (footprint "eagle-import:MA20-2")
      (libsource (lib "eagle-import") (part "MA20-2"))
    )
    (comp (ref "SV203")
      (value "MA12-2")
      (footprint "eagle-import:MA12-2")
      (libsource (lib "eagle-import") (part "MA12-2"))
    )
    (comp (ref "SV204")
      (value "MA12-2")
      (footprint "eagle-import:MA12-2")
      (libsource (lib "eagle-import") (part "MA12-2"))
    )
    (comp (ref "SV205")
      (value "MA12-2")
      (footprint "eagle-import:MA12-2")
      (libsource (lib "eagle-import") (part "MA12-2"))
    )
    (comp (ref "SV206")
      (value "MA12-2")
      (footprint "eagle-import:MA12-2")
      (libsource (lib "eagle-import") (part "MA12-2"))
    )
    (comp (ref "SV207")
      (value "MA20-2")
      (footprint "eagle-import:MA20-2")
      (libsource (lib "eagle-import") (part "MA20-2"))
    )
    (comp (ref "SV208")
      (value "MA20-2")
      (footprint "eagle-import:MA20-2")
      (libsource (lib "eagle-import") (part "MA20-2"))
    )
    (comp (ref "SV209")
      (value "MA20-2")
      (footprint "eagle-import:MA20-2")
      (libsource (lib "eagle-import") (part "MA20-2"))
    )
    (comp (ref "SV210")
      (value "MA20-2")
      (footprint "eagle-import:MA20-2")
      (libsource (lib "eagle-import") (part "MA20-2"))
    )
    (comp (ref "SV211")
      (value "MA12-2")
      (footprint "eagle-import:MA12-2")
      (libsource (lib "eagle-import") (part "MA12-2"))
    )
    (comp (ref "SV212")
      (value "MA12-2")
      (footprint "eagle-import:MA12-2")
      (libsource (lib "eagle-import") (part "MA12-2"))
    )
    (comp (ref "SV213")
      (value "MA12-2")
      (footprint "eagle-import:MA12-2")
      (libsource (lib "eagle-import") (part "MA12-2"))
    )
    (comp (ref "SV214")
      (value "MA12-2")
      (footprint "eagle-import:MA12-2")
      (libsource (lib "eagle-import") (part "MA12-2"))
    )
    (comp (ref "SV215")
      (value "MA20-2")
      (footprint "eagle-import:MA20-2")
      (libsource (lib "eagle-import") (part "MA20-2"))
    )
    (comp (ref "SV216")
      (value "MA20-2")
      (footprint "eagle-import:MA20-2")
      (libsource (lib "eagle-import") (part "MA20-2"))
    )
    (comp (ref "SV217")
      (value "MA20-2")
      (footprint "eagle-import:MA20-2")
      (libsource (lib "eagle-import") (part "MA20-2"))
    )
    (comp (ref "SV218")
      (value "MA20-2")
      (footprint "eagle-import:MA20-2")
      (libsource (lib "eagle-import") (part "MA20-2"))
    )
    (comp (ref "SV219")
      (value "MA12-2")
      (footprint "eagle-import:MA12-2")
      (libsource (lib "eagle-import") (part "MA12-2"))
    )
    (comp (ref "SV220")
      (value "MA12-2")
      (footprint "eagle-import:MA12-2")
      (libsource (lib "eagle-import") (part "MA12-2"))
    )
    (comp (ref "SV221")
      (value "MA12-2")
      (footprint "eagle-import:MA12-2")
      (libsource (lib "eagle-import") (part "MA12-2"))
    )
    (comp (ref "SV222")
      (value "MA12-2")
      (footprint "eagle-import:MA12-2")
      (libsource (lib "eagle-import") (part "MA12-2"))
    )
    (comp (ref "SV223")
      (value "MA20-2")
      (footprint "eagle-import:MA20-2")
      (libsource (lib "eagle-import") (part "MA20-2"))
    )
    (comp (ref "SV224")
      (value "MA20-2")
      (footprint "eagle-import:MA20-2")
      (libsource (lib "eagle-import") (part "MA20-2"))
    )
    (comp (ref "SV225")
      (value "MA20-2")
      (footprint "eagle-import:MA20-2")
      (libsource (lib "eagle-import") (part "MA20-2"))
    )
    (comp (ref "SV226")
      (value "MA20-2")
      (footprint "eagle-import:MA20-2")
      (libsource (lib "eagle-import") (part "MA20-2"))
    )
    (comp (ref "SV227")
      (value "MA12-2")
      (footprint "eagle-import:MA12-2")
      (libsource (lib "eagle-import") (part "MA12-2"))
    )
    (comp (ref "SV228")
      (value "MA12-2")
      (footprint "eagle-import:MA12-2")
      (libsource (lib "eagle-import") (part "MA12-2"))
    )
    (comp (ref "SV229")
      (value "MA12-2")
      (footprint "eagle-import:MA12-2")
      (libsource (lib "eagle-import") (part "MA12-2"))
    )
    (comp (ref "SV230")
      (value "MA12-2")
      (footprint "eagle-import:MA12-2")
      (libsource (lib "eagle-import") (part "MA12-2"))
    )
    (comp (ref "SV231")
      (value "MA20-2")
      (footprint "eagle-import:MA20-2")
      (libsource (lib "eagle-import") (part "MA20-2"))
    )
    (comp (ref "SV232")
      (value "MA20-2")
      (footprint "eagle-import:MA20-2")
      (libsource (lib "eagle-import") (part "MA20-2"))
    )
    (comp (ref "SV233")
      (value "MA20-2")
      (footprint "eagle-import:MA20-2")
      (libsource (lib "eagle-import") (part "MA20-2"))
    )
    (comp (ref "SV234")
      (value "MA20-2")
      (footprint "eagle-import:MA20-2")
      (libsource (lib "eagle-import") (part "MA20-2"))
    )
    (comp (ref "SV235")
      (value "MA12-2")
      (footprint "eagle-import:MA12-2")
      (libsource (lib "eagle-import") (part "MA12-2"))
    )
    (comp (ref "SV236")
      (value "MA12-2")
      (footprint "eagle-import:MA12-2")
      (libsource (lib "eagle-import") (part "MA12-2"))
    )
    (comp (ref "SV237")
      (value "MA12-2")
      (footprint "eagle-import:MA12-2")
      (libsource (lib "eagle-import") (part "MA12-2"))
    )
    (comp (ref "SV238")
      (value "MA12-2")
      (footprint "eagle-import:MA12-2")
      (libsource (lib "eagle-import") (part "MA12-2"))
    )
    (comp (ref "SV239")
      (value "MA20-2")
      (footprint "eagle-import:MA20-2")
      (libsource (lib "eagle-import") (part "MA20-2"))
    )
    (comp (ref "SV240")
      (value "MA20-2")
      (footprint "eagle-import:MA20-2")
      (libsource (lib "eagle-import") (part "MA20-2"))
    )
    (comp (ref "SV241")
      (value "MA20-2")
      (footprint "eagle-import:MA20-2")
      (libsource (lib "eagle-import") (part "MA20-2"))
    )
    (comp (ref "SV242")
      (value "MA20-2")
      (footprint "eagle-import:MA20-2")
      (libsource (lib "eagle-import") (part "MA20-2"))
    )
    (comp (ref "SV243")
      (value "MA12-2")
      (footprint "eagle-import:MA12-2")
      (libsource (lib "eagle-import") (part "MA12-2"))
    )
    (comp (ref "SV244")
      (value "MA12-2")
      (footprint "eagle-import:MA12-2")
      (libsource (lib "eagle-import") (part "MA12-2"))
    )
    (comp (ref "SV245")
      (value "MA12-2")
      (footprint "eagle-import:MA12-2")
      (libsource (lib "eagle-import") (part "MA12-2"))
    )
    (comp (ref "SV246")
      (value "MA12-2")
      (footprint "eagle-import:MA12-2")
      (libsource (lib "eagle-import") (part "MA12-2"))
    )
    (comp (ref "SV247")
      (value "MA03-2")
      (footprint "eagle-import:MA03-2")
      (libsource (lib "eagle-import") (part "MA03-2"))
    )
    (comp (ref "SV248")
      (value "MA03-2")
      (footprint "eagle-import:MA03-2")
      (libsource (lib "eagle-import") (part "MA03-2"))
    )
    (comp (ref "SV249")
      (value "MA03-2")
      (footprint "eagle-import:MA03-2")
      (libsource (lib "eagle-import") (part "MA03-2"))
    )
    (comp (ref "SV250")
      (value "MA03-2")
      (footprint "eagle-import:MA03-2")
      (libsource (lib "eagle-import") (part "MA03-2"))
    )
    (comp (ref "SV251")
      (value "MA03-2")
      (footprint "eagle-import:MA03-2")
      (libsource (lib "eagle-import") (part "MA03-2"))
    )
    (comp (ref "SV252")
      (value "MA03-2")
      (footprint "eagle-import:MA03-2")
      (libsource (lib "eagle-import") (part "MA03-2"))
    )
    (comp (ref "SV253")
      (value "MA03-2")
      (footprint "eagle-import:MA03-2")
      (libsource (lib "eagle-import") (part "MA03-2"))
    )
    (comp (ref "SV254")
      (value "MA03-2")
      (footprint "eagle-import:MA03-2")
      (libsource (lib "eagle-import") (part "MA03-2"))
    )
    (comp (ref "SV255")
      (value "MA03-2")
      (footprint "eagle-import:MA03-2")
      (libsource (lib "eagle-import") (part "MA03-2"))
    )
    (comp (ref "SV256")
      (value "MA03-2")
      (footprint "eagle-import:MA03-2")
      (libsource (lib "eagle-import") (part "MA03-2"))
    )
    (comp (ref "SV257")
      (value "MA03-2")
      (footprint "eagle-import:MA03-2")
      (libsource (lib "eagle-import") (part "MA03-2"))
    )
    (comp (ref "SV258")
      (value "MA03-2")
      (footprint "eagle-import:MA03-2")
      (libsource (lib "eagle-import") (part "MA03-2"))
    )
    (comp (ref "SV259")
      (value "MA03-2")
      (footprint "eagle-import:MA03-2")
      (libsource (lib "eagle-import") (part "MA03-2"))
    )
    (comp (ref "SV260")
      (value "MA03-2")
      (footprint "eagle-import:MA03-2")
      (libsource (lib "eagle-import") (part "MA03-2"))
    )
    (comp (ref "SV261")
      (value "MA03-2")
      (footprint "eagle-import:MA03-2")
      (libsource (lib "eagle-import") (part "MA03-2"))
    )
    (comp (ref "SV262")
      (value "MA03-2")
      (footprint "eagle-import:MA03-2")
      (libsource (lib "eagle-import") (part "MA03-2"))
    )
    (comp (ref "U$1")
      (value "THRU-HOLE2A")
      (footprint "eagle-import:THRU-HOLEA")
      (libsource (lib "eagle-import") (part "THRU-HOLE2A"))
    )
    (comp (ref "U$3")
      (value "THRU-HOLE2A")
      (footprint "eagle-import:THRU-HOLEA")
      (libsource (lib "eagle-import") (part "THRU-HOLE2A"))
    )
    (comp (ref "U$5")
      (value "THRU-HOLE2A")
      (footprint "eagle-import:THRU-HOLEA")
      (libsource (lib "eagle-import") (part "THRU-HOLE2A"))
    )
    (comp (ref "U$6")
      (value "THRU-HOLE2A")
      (footprint "eagle-import:THRU-HOLEA")
      (libsource (lib "eagle-import") (part "THRU-HOLE2A"))
    )
    (comp (ref "U$7")
      (value "OUTLINE-OMNIBUS")
      (footprint "eagle-import:OMNIBUS")
      (libsource (lib "eagle-import") (part "OUTLINE-OMNIBUS"))
    )
  )
  (nets
    (net (code "2") (name "Net-(A1A-1)") (class "Default")
      (node (ref "A1") (pin "A1") (pinfunction "1_A1") (pintype "bidirectional"))
      (node (ref "U$1") (pin "A1") (pinfunction "P$1_A1") (pintype "passive"))
    )
    (net (code "3") (name "Net-(A1AA-1)") (class "Default")
      (node (ref "A1") (pin "R1") (pinfunction "1_R1") (pintype "bidirectional"))
      (node (ref "U$1") (pin "R1") (pinfunction "P$1_R1") (pintype "passive"))
    )
    (net (code "4") (name "Net-(A1AB-1)") (class "Default")
      (node (ref "A1") (pin "R2") (pinfunction "1_R2") (pintype "bidirectional"))
      (node (ref "U$1") (pin "R2") (pinfunction "P$1_R2") (pintype "passive"))
    )
    (net (code "5") (name "Net-(A1AC-1)") (class "Default")
      (node (ref "A1") (pin "S1") (pinfunction "1_S1") (pintype "bidirectional"))
      (node (ref "U$1") (pin "S1") (pinfunction "P$1_S1") (pintype "passive"))
    )
    (net (code "6") (name "Net-(A1AD-1)") (class "Default")
      (node (ref "A1") (pin "S2") (pinfunction "1_S2") (pintype "bidirectional"))
      (node (ref "U$1") (pin "S2") (pinfunction "P$1_S2") (pintype "passive"))
    )
    (net (code "7") (name "Net-(A1AE-1)") (class "Default")
      (node (ref "A1") (pin "T1") (pinfunction "1_T1") (pintype "bidirectional"))
      (node (ref "U$1") (pin "T1") (pinfunction "P$1_T1") (pintype "passive"))
    )
    (net (code "8") (name "Net-(A1AF-1)") (class "Default")
      (node (ref "A1") (pin "T2") (pinfunction "1_T2") (pintype "bidirectional"))
      (node (ref "U$1") (pin "T2") (pinfunction "P$1_T2") (pintype "passive"))
    )
    (net (code "9") (name "Net-(A1AG-1)") (class "Default")
      (node (ref "A1") (pin "U1") (pinfunction "1_U1") (pintype "bidirectional"))
      (node (ref "U$1") (pin "U1") (pinfunction "P$1_U1") (pintype "passive"))
    )
    (net (code "10") (name "Net-(A1AH-1)") (class "Default")
      (node (ref "A1") (pin "U2") (pinfunction "1_U2") (pintype "bidirectional"))
      (node (ref "U$1") (pin "U2") (pinfunction "P$1_U2") (pintype "passive"))
    )
    (net (code "11") (name "Net-(A1AI-1)") (class "Default")
      (node (ref "A1") (pin "V1") (pinfunction "1_V1") (pintype "bidirectional"))
      (node (ref "U$1") (pin "V1") (pinfunction "P$1_V1") (pintype "passive"))
    )
    (net (code "12") (name "Net-(A1AJ-1)") (class "Default")
      (node (ref "A1") (pin "V2") (pinfunction "1_V2") (pintype "bidirectional"))
      (node (ref "U$1") (pin "V2") (pinfunction "P$1_V2") (pintype "passive"))
    )
    (net (code "13") (name "Net-(A1B-1)") (class "Default")
      (node (ref "A1") (pin "A2") (pinfunction "1_A2") (pintype "bidirectional"))
      (node (ref "U$1") (pin "A2") (pinfunction "P$1_A2") (pintype "passive"))
    )
    (net (code "14") (name "Net-(A1C-1)") (class "Default")
      (node (ref "A1") (pin "B1") (pinfunction "1_B1") (pintype "bidirectional"))
      (node (ref "U$1") (pin "B1") (pinfunction "P$1_B1") (pintype "passive"))
    )
    (net (code "15") (name "Net-(A1D-1)") (class "Default")
      (node (ref "A1") (pin "B2") (pinfunction "1_B2") (pintype "bidirectional"))
      (node (ref "U$1") (pin "B2") (pinfunction "P$1_B2") (pintype "passive"))
    )
    (net (code "16") (name "Net-(A1E-1)") (class "Default")
      (node (ref "A1") (pin "C1") (pinfunction "1_C1") (pintype "bidirectional"))
      (node (ref "U$1") (pin "C1") (pinfunction "P$1_C1") (pintype "passive"))
    )
    (net (code "17") (name "Net-(A1F-1)") (class "Default")
      (node (ref "A1") (pin "C2") (pinfunction "1_C2") (pintype "bidirectional"))
      (node (ref "U$1") (pin "C2") (pinfunction "P$1_C2") (pintype "passive"))
    )
    (net (code "18") (name "Net-(A1G-1)") (class "Default")
      (node (ref "A1") (pin "D1") (pinfunction "1_D1") (pintype "bidirectional"))
      (node (ref "U$1") (pin "D1") (pinfunction "P$1_D1") (pintype "passive"))
    )
    (net (code "19") (name "Net-(A1H-1)") (class "Default")
      (node (ref "A1") (pin "D2") (pinfunction "1_D2") (pintype "bidirectional"))
      (node (ref "U$1") (pin "D2") (pinfunction "P$1_D2") (pintype "passive"))
    )
    (net (code "20") (name "Net-(A1I-1)") (class "Default")
      (node (ref "A1") (pin "E1") (pinfunction "1_E1") (pintype "bidirectional"))
      (node (ref "U$1") (pin "E1") (pinfunction "P$1_E1") (pintype "passive"))
    )
    (net (code "21") (name "Net-(A1J-1)") (class "Default")
      (node (ref "A1") (pin "E2") (pinfunction "1_E2") (pintype "bidirectional"))
      (node (ref "U$1") (pin "E2") (pinfunction "P$1_E2") (pintype "passive"))
    )
    (net (code "22") (name "Net-(A1K-1)") (class "Default")
      (node (ref "A1") (pin "F1") (pinfunction "1_F1") (pintype "bidirectional"))
      (node (ref "U$1") (pin "F1") (pinfunction "P$1_F1") (pintype "passive"))
    )
    (net (code "23") (name "Net-(A1L-1)") (class "Default")
      (node (ref "A1") (pin "F2") (pinfunction "1_F2") (pintype "bidirectional"))
      (node (ref "U$1") (pin "F2") (pinfunction "P$1_F2") (pintype "passive"))
    )
    (net (code "24") (name "Net-(A1M-1)") (class "Default")
      (node (ref "A1") (pin "H1") (pinfunction "1_H1") (pintype "bidirectional"))
      (node (ref "U$1") (pin "H1") (pinfunction "P$1_H1") (pintype "passive"))
    )
    (net (code "25") (name "Net-(A1N-1)") (class "Default")
      (node (ref "A1") (pin "H2") (pinfunction "1_H2") (pintype "bidirectional"))
      (node (ref "U$1") (pin "H2") (pinfunction "P$1_H2") (pintype "passive"))
    )
    (net (code "26") (name "Net-(A1O-1)") (class "Default")
      (node (ref "A1") (pin "J1") (pinfunction "1_J1") (pintype "bidirectional"))
      (node (ref "U$1") (pin "J1") (pinfunction "P$1_J1") (pintype "passive"))
    )
    (net (code "27") (name "Net-(A1P-1)") (class "Default")
      (node (ref "A1") (pin "J2") (pinfunction "1_J2") (pintype "bidirectional"))
      (node (ref "U$1") (pin "J2") (pinfunction "P$1_J2") (pintype "passive"))
    )
    (net (code "28") (name "Net-(A1Q-1)") (class "Default")
      (node (ref "A1") (pin "K1") (pinfunction "1_K1") (pintype "bidirectional"))
      (node (ref "U$1") (pin "K1") (pinfunction "P$1_K1") (pintype "passive"))
    )
    (net (code "29") (name "Net-(A1R-1)") (class "Default")
      (node (ref "A1") (pin "K2") (pinfunction "1_K2") (pintype "bidirectional"))
      (node (ref "U$1") (pin "K2") (pinfunction "P$1_K2") (pintype "passive"))
    )
    (net (code "30") (name "Net-(A1S-1)") (class "Default")
      (node (ref "A1") (pin "L1") (pinfunction "1_L1") (pintype "bidirectional"))
      (node (ref "U$1") (pin "L1") (pinfunction "P$1_L1") (pintype "passive"))
    )
    (net (code "31") (name "Net-(A1T-1)") (class "Default")
      (node (ref "A1") (pin "L2") (pinfunction "1_L2") (pintype "bidirectional"))
      (node (ref "U$1") (pin "L2") (pinfunction "P$1_L2") (pintype "passive"))
    )
    (net (code "32") (name "Net-(A1U-1)") (class "Default")
      (node (ref "A1") (pin "M1") (pinfunction "1_M1") (pintype "bidirectional"))
      (node (ref "U$1") (pin "M1") (pinfunction "P$1_M1") (pintype "passive"))
    )
    (net (code "33") (name "Net-(A1V-1)") (class "Default")
      (node (ref "A1") (pin "M2") (pinfunction "1_M2") (pintype "bidirectional"))
      (node (ref "U$1") (pin "M2") (pinfunction "P$1_M2") (pintype "passive"))
    )
    (net (code "34") (name "Net-(A1W-1)") (class "Default")
      (node (ref "A1") (pin "N1") (pinfunction "1_N1") (pintype "bidirectional"))
      (node (ref "U$1") (pin "N1") (pinfunction "P$1_N1") (pintype "passive"))
    )
    (net (code "35") (name "Net-(A1X-1)") (class "Default")
      (node (ref "A1") (pin "N2") (pinfunction "1_N2") (pintype "bidirectional"))
      (node (ref "U$1") (pin "N2") (pinfunction "P$1_N2") (pintype "passive"))
    )
    (net (code "36") (name "Net-(A1Y-1)") (class "Default")
      (node (ref "A1") (pin "P1") (pinfunction "1_P1") (pintype "bidirectional"))
      (node (ref "U$1") (pin "P1") (pinfunction "P$1_P1") (pintype "passive"))
    )
    (net (code "37") (name "Net-(A1Z-1)") (class "Default")
      (node (ref "A1") (pin "P2") (pinfunction "1_P2") (pintype "bidirectional"))
      (node (ref "U$1") (pin "P2") (pinfunction "P$1_P2") (pintype "passive"))
    )
    (net (code "38") (name "Net-(AA-1)") (class "Default")
      (node (ref "A") (pin "A1") (pinfunction "1_A1") (pintype "bidirectional"))
      (node (ref "U$3") (pin "A1") (pinfunction "P$1_A1") (pintype "passive"))
    )
    (net (code "39") (name "Net-(AAA-1)") (class "Default")
      (node (ref "A") (pin "R1") (pinfunction "1_R1") (pintype "bidirectional"))
      (node (ref "U$3") (pin "R1") (pinfunction "P$1_R1") (pintype "passive"))
    )
    (net (code "40") (name "Net-(AAB-1)") (class "Default")
      (node (ref "A") (pin "R2") (pinfunction "1_R2") (pintype "bidirectional"))
      (node (ref "U$3") (pin "R2") (pinfunction "P$1_R2") (pintype "passive"))
    )
    (net (code "41") (name "Net-(AAC-1)") (class "Default")
      (node (ref "A") (pin "S1") (pinfunction "1_S1") (pintype "bidirectional"))
      (node (ref "U$3") (pin "S1") (pinfunction "P$1_S1") (pintype "passive"))
    )
    (net (code "42") (name "Net-(AAD-1)") (class "Default")
      (node (ref "A") (pin "S2") (pinfunction "1_S2") (pintype "bidirectional"))
      (node (ref "U$3") (pin "S2") (pinfunction "P$1_S2") (pintype "passive"))
    )
    (net (code "43") (name "Net-(AAE-1)") (class "Default")
      (node (ref "A") (pin "T1") (pinfunction "1_T1") (pintype "bidirectional"))
      (node (ref "U$3") (pin "T1") (pinfunction "P$1_T1") (pintype "passive"))
    )
    (net (code "44") (name "Net-(AAF-1)") (class "Default")
      (node (ref "A") (pin "T2") (pinfunction "1_T2") (pintype "bidirectional"))
      (node (ref "U$3") (pin "T2") (pinfunction "P$1_T2") (pintype "passive"))
    )
    (net (code "45") (name "Net-(AAG-1)") (class "Default")
      (node (ref "A") (pin "U1") (pinfunction "1_U1") (pintype "bidirectional"))
      (node (ref "U$3") (pin "U1") (pinfunction "P$1_U1") (pintype "passive"))
    )
    (net (code "46") (name "Net-(AAH-1)") (class "Default")
      (node (ref "A") (pin "U2") (pinfunction "1_U2") (pintype "bidirectional"))
      (node (ref "U$3") (pin "U2") (pinfunction "P$1_U2") (pintype "passive"))
    )
    (net (code "47") (name "Net-(AAI-1)") (class "Default")
      (node (ref "A") (pin "V1") (pinfunction "1_V1") (pintype "bidirectional"))
      (node (ref "U$3") (pin "V1") (pinfunction "P$1_V1") (pintype "passive"))
    )
    (net (code "48") (name "Net-(AAJ-1)") (class "Default")
      (node (ref "A") (pin "V2") (pinfunction "1_V2") (pintype "bidirectional"))
      (node (ref "U$3") (pin "V2") (pinfunction "P$1_V2") (pintype "passive"))
    )
    (net (code "49") (name "Net-(AB-1)") (class "Default")
      (node (ref "A") (pin "A2") (pinfunction "1_A2") (pintype "bidirectional"))
      (node (ref "U$3") (pin "A2") (pinfunction "P$1_A2") (pintype "passive"))
    )
    (net (code "50") (name "Net-(AC-1)") (class "Default")
      (node (ref "A") (pin "B1") (pinfunction "1_B1") (pintype "bidirectional"))
      (node (ref "U$3") (pin "B1") (pinfunction "P$1_B1") (pintype "passive"))
    )
    (net (code "51") (name "Net-(AD-1)") (class "Default")
      (node (ref "A") (pin "B2") (pinfunction "1_B2") (pintype "bidirectional"))
      (node (ref "U$3") (pin "B2") (pinfunction "P$1_B2") (pintype "passive"))
    )
    (net (code "52") (name "Net-(AE-1)") (class "Default")
      (node (ref "A") (pin "C1") (pinfunction "1_C1") (pintype "bidirectional"))
      (node (ref "U$3") (pin "C1") (pinfunction "P$1_C1") (pintype "passive"))
    )
    (net (code "53") (name "Net-(AF-1)") (class "Default")
      (node (ref "A") (pin "C2") (pinfunction "1_C2") (pintype "bidirectional"))
      (node (ref "U$3") (pin "C2") (pinfunction "P$1_C2") (pintype "passive"))
    )
    (net (code "54") (name "Net-(AG-1)") (class "Default")
      (node (ref "A") (pin "D1") (pinfunction "1_D1") (pintype "bidirectional"))
      (node (ref "U$3") (pin "D1") (pinfunction "P$1_D1") (pintype "passive"))
    )
    (net (code "55") (name "Net-(AH-1)") (class "Default")
      (node (ref "A") (pin "D2") (pinfunction "1_D2") (pintype "bidirectional"))
      (node (ref "U$3") (pin "D2") (pinfunction "P$1_D2") (pintype "passive"))
    )
    (net (code "56") (name "Net-(AI-1)") (class "Default")
      (node (ref "A") (pin "E1") (pinfunction "1_E1") (pintype "bidirectional"))
      (node (ref "U$3") (pin "E1") (pinfunction "P$1_E1") (pintype "passive"))
    )
    (net (code "57") (name "Net-(AJ-1)") (class "Default")
      (node (ref "A") (pin "E2") (pinfunction "1_E2") (pintype "bidirectional"))
      (node (ref "U$3") (pin "E2") (pinfunction "P$1_E2") (pintype "passive"))
    )
    (net (code "58") (name "Net-(AK-1)") (class "Default")
      (node (ref "A") (pin "F1") (pinfunction "1_F1") (pintype "bidirectional"))
      (node (ref "U$3") (pin "F1") (pinfunction "P$1_F1") (pintype "passive"))
    )
    (net (code "59") (name "Net-(AL-1)") (class "Default")
      (node (ref "A") (pin "F2") (pinfunction "1_F2") (pintype "bidirectional"))
      (node (ref "U$3") (pin "F2") (pinfunction "P$1_F2") (pintype "passive"))
    )
    (net (code "60") (name "Net-(AM-1)") (class "Default")
      (node (ref "A") (pin "H1") (pinfunction "1_H1") (pintype "bidirectional"))
      (node (ref "U$3") (pin "H1") (pinfunction "P$1_H1") (pintype "passive"))
    )
    (net (code "61") (name "Net-(AN-1)") (class "Default")
      (node (ref "A") (pin "H2") (pinfunction "1_H2") (pintype "bidirectional"))
      (node (ref "U$3") (pin "H2") (pinfunction "P$1_H2") (pintype "passive"))
    )
    (net (code "62") (name "Net-(AO-1)") (class "Default")
      (node (ref "A") (pin "J1") (pinfunction "1_J1") (pintype "bidirectional"))
      (node (ref "U$3") (pin "J1") (pinfunction "P$1_J1") (pintype "passive"))
    )
    (net (code "63") (name "Net-(AP-1)") (class "Default")
      (node (ref "A") (pin "J2") (pinfunction "1_J2") (pintype "bidirectional"))
      (node (ref "U$3") (pin "J2") (pinfunction "P$1_J2") (pintype "passive"))
    )
    (net (code "64") (name "Net-(AQ-1)") (class "Default")
      (node (ref "A") (pin "K1") (pinfunction "1_K1") (pintype "bidirectional"))
      (node (ref "U$3") (pin "K1") (pinfunction "P$1_K1") (pintype "passive"))
    )
    (net (code "65") (name "Net-(AR-1)") (class "Default")
      (node (ref "A") (pin "K2") (pinfunction "1_K2") (pintype "bidirectional"))
      (node (ref "U$3") (pin "K2") (pinfunction "P$1_K2") (pintype "passive"))
    )
    (net (code "66") (name "Net-(AS-1)") (class "Default")
      (node (ref "A") (pin "L1") (pinfunction "1_L1") (pintype "bidirectional"))
      (node (ref "U$3") (pin "L1") (pinfunction "P$1_L1") (pintype "passive"))
    )
    (net (code "67") (name "Net-(AT-1)") (class "Default")
      (node (ref "A") (pin "L2") (pinfunction "1_L2") (pintype "bidirectional"))
      (node (ref "U$3") (pin "L2") (pinfunction "P$1_L2") (pintype "passive"))
    )
    (net (code "68") (name "Net-(AU-1)") (class "Default")
      (node (ref "A") (pin "M1") (pinfunction "1_M1") (pintype "bidirectional"))
      (node (ref "U$3") (pin "M1") (pinfunction "P$1_M1") (pintype "passive"))
    )
    (net (code "69") (name "Net-(AV-1)") (class "Default")
      (node (ref "A") (pin "M2") (pinfunction "1_M2") (pintype "bidirectional"))
      (node (ref "U$3") (pin "M2") (pinfunction "P$1_M2") (pintype "passive"))
    )
    (net (code "70") (name "Net-(AW-1)") (class "Default")
      (node (ref "A") (pin "N1") (pinfunction "1_N1") (pintype "bidirectional"))
      (node (ref "U$3") (pin "N1") (pinfunction "P$1_N1") (pintype "passive"))
    )
    (net (code "71") (name "Net-(AX-1)") (class "Default")
      (node (ref "A") (pin "N2") (pinfunction "1_N2") (pintype "bidirectional"))
      (node (ref "U$3") (pin "N2") (pinfunction "P$1_N2") (pintype "passive"))
    )
    (net (code "72") (name "Net-(AY-1)") (class "Default")
      (node (ref "A") (pin "P1") (pinfunction "1_P1") (pintype "bidirectional"))
      (node (ref "U$3") (pin "P1") (pinfunction "P$1_P1") (pintype "passive"))
    )
    (net (code "73") (name "Net-(AZ-1)") (class "Default")
      (node (ref "A") (pin "P2") (pinfunction "1_P2") (pintype "bidirectional"))
      (node (ref "U$3") (pin "P2") (pinfunction "P$1_P2") (pintype "passive"))
    )
    (net (code "74") (name "Net-(B1A-1)") (class "Default")
      (node (ref "B1") (pin "A1") (pinfunction "1_A1") (pintype "bidirectional"))
      (node (ref "U$6") (pin "A1") (pinfunction "P$1_A1") (pintype "passive"))
    )
    (net (code "75") (name "Net-(B1AA-1)") (class "Default")
      (node (ref "B1") (pin "R1") (pinfunction "1_R1") (pintype "bidirectional"))
      (node (ref "U$6") (pin "R1") (pinfunction "P$1_R1") (pintype "passive"))
    )
    (net (code "76") (name "Net-(B1AB-1)") (class "Default")
      (node (ref "B1") (pin "R2") (pinfunction "1_R2") (pintype "bidirectional"))
      (node (ref "U$6") (pin "R2") (pinfunction "P$1_R2") (pintype "passive"))
    )
    (net (code "77") (name "Net-(B1AC-1)") (class "Default")
      (node (ref "B1") (pin "S1") (pinfunction "1_S1") (pintype "bidirectional"))
      (node (ref "U$6") (pin "S1") (pinfunction "P$1_S1") (pintype "passive"))
    )
    (net (code "78") (name "Net-(B1AD-1)") (class "Default")
      (node (ref "B1") (pin "S2") (pinfunction "1_S2") (pintype "bidirectional"))
      (node (ref "U$6") (pin "S2") (pinfunction "P$1_S2") (pintype "passive"))
    )
    (net (code "79") (name "Net-(B1AE-1)") (class "Default")
      (node (ref "B1") (pin "T1") (pinfunction "1_T1") (pintype "bidirectional"))
      (node (ref "U$6") (pin "T1") (pinfunction "P$1_T1") (pintype "passive"))
    )
    (net (code "80") (name "Net-(B1AF-1)") (class "Default")
      (node (ref "B1") (pin "T2") (pinfunction "1_T2") (pintype "bidirectional"))
      (node (ref "U$6") (pin "T2") (pinfunction "P$1_T2") (pintype "passive"))
    )
    (net (code "81") (name "Net-(B1AG-1)") (class "Default")
      (node (ref "B1") (pin "U1") (pinfunction "1_U1") (pintype "bidirectional"))
      (node (ref "U$6") (pin "U1") (pinfunction "P$1_U1") (pintype "passive"))
    )
    (net (code "82") (name "Net-(B1AH-1)") (class "Default")
      (node (ref "B1") (pin "U2") (pinfunction "1_U2") (pintype "bidirectional"))
      (node (ref "U$6") (pin "U2") (pinfunction "P$1_U2") (pintype "passive"))
    )
    (net (code "83") (name "Net-(B1AI-1)") (class "Default")
      (node (ref "B1") (pin "V1") (pinfunction "1_V1") (pintype "bidirectional"))
      (node (ref "U$6") (pin "V1") (pinfunction "P$1_V1") (pintype "passive"))
    )
    (net (code "84") (name "Net-(B1AJ-1)") (class "Default")
      (node (ref "B1") (pin "V2") (pinfunction "1_V2") (pintype "bidirectional"))
      (node (ref "U$6") (pin "V2") (pinfunction "P$1_V2") (pintype "passive"))
    )
    (net (code "85") (name "Net-(B1B-1)") (class "Default")
      (node (ref "B1") (pin "A2") (pinfunction "1_A2") (pintype "bidirectional"))
      (node (ref "U$6") (pin "A2") (pinfunction "P$1_A2") (pintype "passive"))
    )
    (net (code "86") (name "Net-(B1C-1)") (class "Default")
      (node (ref "B1") (pin "B1") (pinfunction "1_B1") (pintype "bidirectional"))
      (node (ref "U$6") (pin "B1") (pinfunction "P$1_B1") (pintype "passive"))
    )
    (net (code "87") (name "Net-(B1D-1)") (class "Default")
      (node (ref "B1") (pin "B2") (pinfunction "1_B2") (pintype "bidirectional"))
      (node (ref "U$6") (pin "B2") (pinfunction "P$1_B2") (pintype "passive"))
    )
    (net (code "88") (name "Net-(B1E-1)") (class "Default")
      (node (ref "B1") (pin "C1") (pinfunction "1_C1") (pintype "bidirectional"))
      (node (ref "U$6") (pin "C1") (pinfunction "P$1_C1") (pintype "passive"))
    )
    (net (code "89") (name "Net-(B1F-1)") (class "Default")
      (node (ref "B1") (pin "C2") (pinfunction "1_C2") (pintype "bidirectional"))
      (node (ref "U$6") (pin "C2") (pinfunction "P$1_C2") (pintype "passive"))
    )
    (net (code "90") (name "Net-(B1G-1)") (class "Default")
      (node (ref "B1") (pin "D1") (pinfunction "1_D1") (pintype "bidirectional"))
      (node (ref "U$6") (pin "D1") (pinfunction "P$1_D1") (pintype "passive"))
    )
    (net (code "91") (name "Net-(B1H-1)") (class "Default")
      (node (ref "B1") (pin "D2") (pinfunction "1_D2") (pintype "bidirectional"))
      (node (ref "U$6") (pin "D2") (pinfunction "P$1_D2") (pintype "passive"))
    )
    (net (code "92") (name "Net-(B1I-1)") (class "Default")
      (node (ref "B1") (pin "E1") (pinfunction "1_E1") (pintype "bidirectional"))
      (node (ref "U$6") (pin "E1") (pinfunction "P$1_E1") (pintype "passive"))
    )
    (net (code "93") (name "Net-(B1J-1)") (class "Default")
      (node (ref "B1") (pin "E2") (pinfunction "1_E2") (pintype "bidirectional"))
      (node (ref "U$6") (pin "E2") (pinfunction "P$1_E2") (pintype "passive"))
    )
    (net (code "94") (name "Net-(B1K-1)") (class "Default")
      (node (ref "B1") (pin "F1") (pinfunction "1_F1") (pintype "bidirectional"))
      (node (ref "U$6") (pin "F1") (pinfunction "P$1_F1") (pintype "passive"))
    )
    (net (code "95") (name "Net-(B1L-1)") (class "Default")
      (node (ref "B1") (pin "F2") (pinfunction "1_F2") (pintype "bidirectional"))
      (node (ref "U$6") (pin "F2") (pinfunction "P$1_F2") (pintype "passive"))
    )
    (net (code "96") (name "Net-(B1M-1)") (class "Default")
      (node (ref "B1") (pin "H1") (pinfunction "1_H1") (pintype "bidirectional"))
      (node (ref "U$6") (pin "H1") (pinfunction "P$1_H1") (pintype "passive"))
    )
    (net (code "97") (name "Net-(B1N-1)") (class "Default")
      (node (ref "B1") (pin "H2") (pinfunction "1_H2") (pintype "bidirectional"))
      (node (ref "U$6") (pin "H2") (pinfunction "P$1_H2") (pintype "passive"))
    )
    (net (code "98") (name "Net-(B1O-1)") (class "Default")
      (node (ref "B1") (pin "J1") (pinfunction "1_J1") (pintype "bidirectional"))
      (node (ref "U$6") (pin "J1") (pinfunction "P$1_J1") (pintype "passive"))
    )
    (net (code "99") (name "Net-(B1P-1)") (class "Default")
      (node (ref "B1") (pin "J2") (pinfunction "1_J2") (pintype "bidirectional"))
      (node (ref "U$6") (pin "J2") (pinfunction "P$1_J2") (pintype "passive"))
    )
    (net (code "100") (name "Net-(B1Q-1)") (class "Default")
      (node (ref "B1") (pin "K1") (pinfunction "1_K1") (pintype "bidirectional"))
      (node (ref "U$6") (pin "K1") (pinfunction "P$1_K1") (pintype "passive"))
    )
    (net (code "101") (name "Net-(B1R-1)") (class "Default")
      (node (ref "B1") (pin "K2") (pinfunction "1_K2") (pintype "bidirectional"))
      (node (ref "U$6") (pin "K2") (pinfunction "P$1_K2") (pintype "passive"))
    )
    (net (code "102") (name "Net-(B1S-1)") (class "Default")
      (node (ref "B1") (pin "L1") (pinfunction "1_L1") (pintype "bidirectional"))
      (node (ref "U$6") (pin "L1") (pinfunction "P$1_L1") (pintype "passive"))
    )
    (net (code "103") (name "Net-(B1T-1)") (class "Default")
      (node (ref "B1") (pin "L2") (pinfunction "1_L2") (pintype "bidirectional"))
      (node (ref "U$6") (pin "L2") (pinfunction "P$1_L2") (pintype "passive"))
    )
    (net (code "104") (name "Net-(B1U-1)") (class "Default")
      (node (ref "B1") (pin "M1") (pinfunction "1_M1") (pintype "bidirectional"))
      (node (ref "U$6") (pin "M1") (pinfunction "P$1_M1") (pintype "passive"))
    )
    (net (code "105") (name "Net-(B1V-1)") (class "Default")
      (node (ref "B1") (pin "M2") (pinfunction "1_M2") (pintype "bidirectional"))
      (node (ref "U$6") (pin "M2") (pinfunction "P$1_M2") (pintype "passive"))
    )
    (net (code "106") (name "Net-(B1W-1)") (class "Default")
      (node (ref "B1") (pin "N1") (pinfunction "1_N1") (pintype "bidirectional"))
      (node (ref "U$6") (pin "N1") (pinfunction "P$1_N1") (pintype "passive"))
    )
    (net (code "107") (name "Net-(B1X-1)") (class "Default")
      (node (ref "B1") (pin "N2") (pinfunction "1_N2") (pintype "bidirectional"))
      (node (ref "U$6") (pin "N2") (pinfunction "P$1_N2") (pintype "passive"))
    )
    (net (code "108") (name "Net-(B1Y-1)") (class "Default")
      (node (ref "B1") (pin "P1") (pinfunction "1_P1") (pintype "bidirectional"))
      (node (ref "U$6") (pin "P1") (pinfunction "P$1_P1") (pintype "passive"))
    )
    (net (code "109") (name "Net-(B1Z-1)") (class "Default")
      (node (ref "B1") (pin "P2") (pinfunction "1_P2") (pintype "bidirectional"))
      (node (ref "U$6") (pin "P2") (pinfunction "P$1_P2") (pintype "passive"))
    )
    (net (code "110") (name "Net-(BA-1)") (class "Default")
      (node (ref "B") (pin "A1") (pinfunction "1_A1") (pintype "bidirectional"))
      (node (ref "U$5") (pin "A1") (pinfunction "P$1_A1") (pintype "passive"))
    )
    (net (code "111") (name "Net-(BAA-1)") (class "Default")
      (node (ref "B") (pin "R1") (pinfunction "1_R1") (pintype "bidirectional"))
      (node (ref "U$5") (pin "R1") (pinfunction "P$1_R1") (pintype "passive"))
    )
    (net (code "112") (name "Net-(BAB-1)") (class "Default")
      (node (ref "B") (pin "R2") (pinfunction "1_R2") (pintype "bidirectional"))
      (node (ref "U$5") (pin "R2") (pinfunction "P$1_R2") (pintype "passive"))
    )
    (net (code "113") (name "Net-(BAC-1)") (class "Default")
      (node (ref "B") (pin "S1") (pinfunction "1_S1") (pintype "bidirectional"))
      (node (ref "U$5") (pin "S1") (pinfunction "P$1_S1") (pintype "passive"))
    )
    (net (code "114") (name "Net-(BAD-1)") (class "Default")
      (node (ref "B") (pin "S2") (pinfunction "1_S2") (pintype "bidirectional"))
      (node (ref "U$5") (pin "S2") (pinfunction "P$1_S2") (pintype "passive"))
    )
    (net (code "115") (name "Net-(BAE-1)") (class "Default")
      (node (ref "B") (pin "T1") (pinfunction "1_T1") (pintype "bidirectional"))
      (node (ref "U$5") (pin "T1") (pinfunction "P$1_T1") (pintype "passive"))
    )
    (net (code "116") (name "Net-(BAF-1)") (class "Default")
      (node (ref "B") (pin "T2") (pinfunction "1_T2") (pintype "bidirectional"))
      (node (ref "U$5") (pin "T2") (pinfunction "P$1_T2") (pintype "passive"))
    )
    (net (code "117") (name "Net-(BAG-1)") (class "Default")
      (node (ref "B") (pin "U1") (pinfunction "1_U1") (pintype "bidirectional"))
      (node (ref "U$5") (pin "U1") (pinfunction "P$1_U1") (pintype "passive"))
    )
    (net (code "118") (name "Net-(BAH-1)") (class "Default")
      (node (ref "B") (pin "U2") (pinfunction "1_U2") (pintype "bidirectional"))
      (node (ref "U$5") (pin "U2") (pinfunction "P$1_U2") (pintype "passive"))
    )
    (net (code "119") (name "Net-(BAI-1)") (class "Default")
      (node (ref "B") (pin "V1") (pinfunction "1_V1") (pintype "bidirectional"))
      (node (ref "U$5") (pin "V1") (pinfunction "P$1_V1") (pintype "passive"))
    )
    (net (code "120") (name "Net-(BAJ-1)") (class "Default")
      (node (ref "B") (pin "V2") (pinfunction "1_V2") (pintype "bidirectional"))
      (node (ref "U$5") (pin "V2") (pinfunction "P$1_V2") (pintype "passive"))
    )
    (net (code "121") (name "Net-(BB-1)") (class "Default")
      (node (ref "B") (pin "A2") (pinfunction "1_A2") (pintype "bidirectional"))
      (node (ref "U$5") (pin "A2") (pinfunction "P$1_A2") (pintype "passive"))
    )
    (net (code "122") (name "Net-(BC-1)") (class "Default")
      (node (ref "B") (pin "B1") (pinfunction "1_B1") (pintype "bidirectional"))
      (node (ref "U$5") (pin "B1") (pinfunction "P$1_B1") (pintype "passive"))
    )
    (net (code "123") (name "Net-(BD-1)") (class "Default")
      (node (ref "B") (pin "B2") (pinfunction "1_B2") (pintype "bidirectional"))
      (node (ref "U$5") (pin "B2") (pinfunction "P$1_B2") (pintype "passive"))
    )
    (net (code "124") (name "Net-(BE-1)") (class "Default")
      (node (ref "B") (pin "C1") (pinfunction "1_C1") (pintype "bidirectional"))
      (node (ref "U$5") (pin "C1") (pinfunction "P$1_C1") (pintype "passive"))
    )
    (net (code "125") (name "Net-(BF-1)") (class "Default")
      (node (ref "B") (pin "C2") (pinfunction "1_C2") (pintype "bidirectional"))
      (node (ref "U$5") (pin "C2") (pinfunction "P$1_C2") (pintype "passive"))
    )
    (net (code "126") (name "Net-(BG-1)") (class "Default")
      (node (ref "B") (pin "D1") (pinfunction "1_D1") (pintype "bidirectional"))
      (node (ref "U$5") (pin "D1") (pinfunction "P$1_D1") (pintype "passive"))
    )
    (net (code "127") (name "Net-(BH-1)") (class "Default")
      (node (ref "B") (pin "D2") (pinfunction "1_D2") (pintype "bidirectional"))
      (node (ref "U$5") (pin "D2") (pinfunction "P$1_D2") (pintype "passive"))
    )
    (net (code "128") (name "Net-(BI-1)") (class "Default")
      (node (ref "B") (pin "E1") (pinfunction "1_E1") (pintype "bidirectional"))
      (node (ref "U$5") (pin "E1") (pinfunction "P$1_E1") (pintype "passive"))
    )
    (net (code "129") (name "Net-(BJ-1)") (class "Default")
      (node (ref "B") (pin "E2") (pinfunction "1_E2") (pintype "bidirectional"))
      (node (ref "U$5") (pin "E2") (pinfunction "P$1_E2") (pintype "passive"))
    )
    (net (code "130") (name "Net-(BK-1)") (class "Default")
      (node (ref "B") (pin "F1") (pinfunction "1_F1") (pintype "bidirectional"))
      (node (ref "U$5") (pin "F1") (pinfunction "P$1_F1") (pintype "passive"))
    )
    (net (code "131") (name "Net-(BL-1)") (class "Default")
      (node (ref "B") (pin "F2") (pinfunction "1_F2") (pintype "bidirectional"))
      (node (ref "U$5") (pin "F2") (pinfunction "P$1_F2") (pintype "passive"))
    )
    (net (code "132") (name "Net-(BM-1)") (class "Default")
      (node (ref "B") (pin "H1") (pinfunction "1_H1") (pintype "bidirectional"))
      (node (ref "U$5") (pin "H1") (pinfunction "P$1_H1") (pintype "passive"))
    )
    (net (code "133") (name "Net-(BN-1)") (class "Default")
      (node (ref "B") (pin "H2") (pinfunction "1_H2") (pintype "bidirectional"))
      (node (ref "U$5") (pin "H2") (pinfunction "P$1_H2") (pintype "passive"))
    )
    (net (code "134") (name "Net-(BO-1)") (class "Default")
      (node (ref "B") (pin "J1") (pinfunction "1_J1") (pintype "bidirectional"))
      (node (ref "U$5") (pin "J1") (pinfunction "P$1_J1") (pintype "passive"))
    )
    (net (code "135") (name "Net-(BP-1)") (class "Default")
      (node (ref "B") (pin "J2") (pinfunction "1_J2") (pintype "bidirectional"))
      (node (ref "U$5") (pin "J2") (pinfunction "P$1_J2") (pintype "passive"))
    )
    (net (code "136") (name "Net-(BQ-1)") (class "Default")
      (node (ref "B") (pin "K1") (pinfunction "1_K1") (pintype "bidirectional"))
      (node (ref "U$5") (pin "K1") (pinfunction "P$1_K1") (pintype "passive"))
    )
    (net (code "137") (name "Net-(BR-1)") (class "Default")
      (node (ref "B") (pin "K2") (pinfunction "1_K2") (pintype "bidirectional"))
      (node (ref "U$5") (pin "K2") (pinfunction "P$1_K2") (pintype "passive"))
    )
    (net (code "138") (name "Net-(BS-1)") (class "Default")
      (node (ref "B") (pin "L1") (pinfunction "1_L1") (pintype "bidirectional"))
      (node (ref "U$5") (pin "L1") (pinfunction "P$1_L1") (pintype "passive"))
    )
    (net (code "139") (name "Net-(BT-1)") (class "Default")
      (node (ref "B") (pin "L2") (pinfunction "1_L2") (pintype "bidirectional"))
      (node (ref "U$5") (pin "L2") (pinfunction "P$1_L2") (pintype "passive"))
    )
    (net (code "140") (name "Net-(BU-1)") (class "Default")
      (node (ref "B") (pin "M1") (pinfunction "1_M1") (pintype "bidirectional"))
      (node (ref "U$5") (pin "M1") (pinfunction "P$1_M1") (pintype "passive"))
    )
    (net (code "141") (name "Net-(BV-1)") (class "Default")
      (node (ref "B") (pin "M2") (pinfunction "1_M2") (pintype "bidirectional"))
      (node (ref "U$5") (pin "M2") (pinfunction "P$1_M2") (pintype "passive"))
    )
    (net (code "142") (name "Net-(BW-1)") (class "Default")
      (node (ref "B") (pin "N1") (pinfunction "1_N1") (pintype "bidirectional"))
      (node (ref "U$5") (pin "N1") (pinfunction "P$1_N1") (pintype "passive"))
    )
    (net (code "143") (name "Net-(BX-1)") (class "Default")
      (node (ref "B") (pin "N2") (pinfunction "1_N2") (pintype "bidirectional"))
      (node (ref "U$5") (pin "N2") (pinfunction "P$1_N2") (pintype "passive"))
    )
    (net (code "144") (name "Net-(BY-1)") (class "Default")
      (node (ref "B") (pin "P1") (pinfunction "1_P1") (pintype "bidirectional"))
      (node (ref "U$5") (pin "P1") (pinfunction "P$1_P1") (pintype "passive"))
    )
    (net (code "145") (name "Net-(BZ-1)") (class "Default")
      (node (ref "B") (pin "P2") (pinfunction "1_P2") (pintype "bidirectional"))
      (node (ref "U$5") (pin "P2") (pinfunction "P$1_P2") (pintype "passive"))
    )
    (net (code "147") (name "unconnected-(SV1-Pad1)") (class "Default")
      (node (ref "SV1") (pin "1") (pinfunction "1_1") (pintype "passive"))
    )
    (net (code "148") (name "unconnected-(SV1-Pad2)") (class "Default")
      (node (ref "SV1") (pin "2") (pinfunction "2_2") (pintype "passive"))
    )
    (net (code "149") (name "unconnected-(SV1-Pad3)") (class "Default")
      (node (ref "SV1") (pin "3") (pinfunction "3_3") (pintype "passive"))
    )
    (net (code "150") (name "unconnected-(SV1-Pad4)") (class "Default")
      (node (ref "SV1") (pin "4") (pinfunction "4_4") (pintype "passive"))
    )
    (net (code "151") (name "unconnected-(SV1-Pad5)") (class "Default")
      (node (ref "SV1") (pin "5") (pinfunction "5_5") (pintype "passive"))
    )
    (net (code "152") (name "unconnected-(SV1-Pad6)") (class "Default")
      (node (ref "SV1") (pin "6") (pinfunction "6_6") (pintype "passive"))
    )
    (net (code "153") (name "unconnected-(SV1-Pad7)") (class "Default")
      (node (ref "SV1") (pin "7") (pinfunction "7_7") (pintype "passive"))
    )
    (net (code "154") (name "unconnected-(SV1-Pad8)") (class "Default")
      (node (ref "SV1") (pin "8") (pinfunction "8_8") (pintype "passive"))
    )
    (net (code "155") (name "unconnected-(SV1-Pad9)") (class "Default")
      (node (ref "SV1") (pin "9") (pinfunction "9_9") (pintype "passive"))
    )
    (net (code "156") (name "unconnected-(SV1-Pad10)") (class "Default")
      (node (ref "SV1") (pin "10") (pinfunction "10_10") (pintype "passive"))
    )
    (net (code "157") (name "unconnected-(SV1-Pad11)") (class "Default")
      (node (ref "SV1") (pin "11") (pinfunction "11_11") (pintype "passive"))
    )
    (net (code "158") (name "unconnected-(SV1-Pad12)") (class "Default")
      (node (ref "SV1") (pin "12") (pinfunction "12_12") (pintype "passive"))
    )
    (net (code "159") (name "unconnected-(SV1-Pad13)") (class "Default")
      (node (ref "SV1") (pin "13") (pinfunction "13_13") (pintype "passive"))
    )
    (net (code "160") (name "unconnected-(SV1-Pad14)") (class "Default")
      (node (ref "SV1") (pin "14") (pinfunction "14_14") (pintype "passive"))
    )
    (net (code "161") (name "unconnected-(SV1-Pad15)") (class "Default")
      (node (ref "SV1") (pin "15") (pinfunction "15_15") (pintype "passive"))
    )
    (net (code "162") (name "unconnected-(SV1-Pad16)") (class "Default")
      (node (ref "SV1") (pin "16") (pinfunction "16_16") (pintype "passive"))
    )
    (net (code "163") (name "unconnected-(SV1-Pad17)") (class "Default")
      (node (ref "SV1") (pin "17") (pinfunction "17_17") (pintype "passive"))
    )
    (net (code "164") (name "unconnected-(SV1-Pad18)") (class "Default")
      (node (ref "SV1") (pin "18") (pinfunction "18_18") (pintype "passive"))
    )
    (net (code "165") (name "unconnected-(SV1-Pad19)") (class "Default")
      (node (ref "SV1") (pin "19") (pinfunction "19_19") (pintype "passive"))
    )
    (net (code "166") (name "unconnected-(SV1-Pad20)") (class "Default")
      (node (ref "SV1") (pin "20") (pinfunction "20_20") (pintype "passive"))
    )
    (net (code "167") (name "unconnected-(SV1-Pad21)") (class "Default")
      (node (ref "SV1") (pin "21") (pinfunction "21_21") (pintype "passive"))
    )
    (net (code "168") (name "unconnected-(SV1-Pad22)") (class "Default")
      (node (ref "SV1") (pin "22") (pinfunction "22_22") (pintype "passive"))
    )
    (net (code "169") (name "unconnected-(SV1-Pad23)") (class "Default")
      (node (ref "SV1") (pin "23") (pinfunction "23_23") (pintype "passive"))
    )
    (net (code "170") (name "unconnected-(SV1-Pad24)") (class "Default")
      (node (ref "SV1") (pin "24") (pinfunction "24_24") (pintype "passive"))
    )
    (net (code "171") (name "unconnected-(SV1-Pad25)") (class "Default")
      (node (ref "SV1") (pin "25") (pinfunction "25_25") (pintype "passive"))
    )
    (net (code "172") (name "unconnected-(SV1-Pad26)") (class "Default")
      (node (ref "SV1") (pin "26") (pinfunction "26_26") (pintype "passive"))
    )
    (net (code "173") (name "unconnected-(SV1-Pad27)") (class "Default")
      (node (ref "SV1") (pin "27") (pinfunction "27_27") (pintype "passive"))
    )
    (net (code "174") (name "unconnected-(SV1-Pad28)") (class "Default")
      (node (ref "SV1") (pin "28") (pinfunction "28_28") (pintype "passive"))
    )
    (net (code "175") (name "unconnected-(SV1-Pad29)") (class "Default")
      (node (ref "SV1") (pin "29") (pinfunction "29_29") (pintype "passive"))
    )
    (net (code "176") (name "unconnected-(SV1-Pad30)") (class "Default")
      (node (ref "SV1") (pin "30") (pinfunction "30_30") (pintype "passive"))
    )
    (net (code "177") (name "unconnected-(SV1-Pad31)") (class "Default")
      (node (ref "SV1") (pin "31") (pinfunction "31_31") (pintype "passive"))
    )
    (net (code "178") (name "unconnected-(SV1-Pad32)") (class "Default")
      (node (ref "SV1") (pin "32") (pinfunction "32_32") (pintype "passive"))
    )
    (net (code "179") (name "unconnected-(SV1-Pad33)") (class "Default")
      (node (ref "SV1") (pin "33") (pinfunction "33_33") (pintype "passive"))
    )
    (net (code "180") (name "unconnected-(SV1-Pad34)") (class "Default")
      (node (ref "SV1") (pin "34") (pinfunction "34_34") (pintype "passive"))
    )
    (net (code "181") (name "unconnected-(SV1-Pad35)") (class "Default")
      (node (ref "SV1") (pin "35") (pinfunction "35_35") (pintype "passive"))
    )
    (net (code "182") (name "unconnected-(SV1-Pad36)") (class "Default")
      (node (ref "SV1") (pin "36") (pinfunction "36_36") (pintype "passive"))
    )
    (net (code "183") (name "unconnected-(SV1-Pad37)") (class "Default")
      (node (ref "SV1") (pin "37") (pinfunction "37_37") (pintype "passive"))
    )
    (net (code "184") (name "unconnected-(SV1-Pad38)") (class "Default")
      (node (ref "SV1") (pin "38") (pinfunction "38_38") (pintype "passive"))
    )
    (net (code "185") (name "unconnected-(SV1-Pad39)") (class "Default")
      (node (ref "SV1") (pin "39") (pinfunction "39_39") (pintype "passive"))
    )
    (net (code "186") (name "unconnected-(SV1-Pad40)") (class "Default")
      (node (ref "SV1") (pin "40") (pinfunction "40_40") (pintype "passive"))
    )
    (net (code "187") (name "unconnected-(SV2-Pad1)") (class "Default")
      (node (ref "SV2") (pin "1") (pinfunction "1_1") (pintype "passive"))
    )
    (net (code "188") (name "unconnected-(SV2-Pad2)") (class "Default")
      (node (ref "SV2") (pin "2") (pinfunction "2_2") (pintype "passive"))
    )
    (net (code "189") (name "unconnected-(SV2-Pad3)") (class "Default")
      (node (ref "SV2") (pin "3") (pinfunction "3_3") (pintype "passive"))
    )
    (net (code "190") (name "unconnected-(SV2-Pad4)") (class "Default")
      (node (ref "SV2") (pin "4") (pinfunction "4_4") (pintype "passive"))
    )
    (net (code "191") (name "unconnected-(SV2-Pad5)") (class "Default")
      (node (ref "SV2") (pin "5") (pinfunction "5_5") (pintype "passive"))
    )
    (net (code "192") (name "unconnected-(SV2-Pad6)") (class "Default")
      (node (ref "SV2") (pin "6") (pinfunction "6_6") (pintype "passive"))
    )
    (net (code "193") (name "unconnected-(SV2-Pad7)") (class "Default")
      (node (ref "SV2") (pin "7") (pinfunction "7_7") (pintype "passive"))
    )
    (net (code "194") (name "unconnected-(SV2-Pad8)") (class "Default")
      (node (ref "SV2") (pin "8") (pinfunction "8_8") (pintype "passive"))
    )
    (net (code "195") (name "unconnected-(SV2-Pad9)") (class "Default")
      (node (ref "SV2") (pin "9") (pinfunction "9_9") (pintype "passive"))
    )
    (net (code "196") (name "unconnected-(SV2-Pad10)") (class "Default")
      (node (ref "SV2") (pin "10") (pinfunction "10_10") (pintype "passive"))
    )
    (net (code "197") (name "unconnected-(SV2-Pad11)") (class "Default")
      (node (ref "SV2") (pin "11") (pinfunction "11_11") (pintype "passive"))
    )
    (net (code "198") (name "unconnected-(SV2-Pad12)") (class "Default")
      (node (ref "SV2") (pin "12") (pinfunction "12_12") (pintype "passive"))
    )
    (net (code "199") (name "unconnected-(SV2-Pad13)") (class "Default")
      (node (ref "SV2") (pin "13") (pinfunction "13_13") (pintype "passive"))
    )
    (net (code "200") (name "unconnected-(SV2-Pad14)") (class "Default")
      (node (ref "SV2") (pin "14") (pinfunction "14_14") (pintype "passive"))
    )
    (net (code "201") (name "unconnected-(SV2-Pad15)") (class "Default")
      (node (ref "SV2") (pin "15") (pinfunction "15_15") (pintype "passive"))
    )
    (net (code "202") (name "unconnected-(SV2-Pad16)") (class "Default")
      (node (ref "SV2") (pin "16") (pinfunction "16_16") (pintype "passive"))
    )
    (net (code "203") (name "unconnected-(SV2-Pad17)") (class "Default")
      (node (ref "SV2") (pin "17") (pinfunction "17_17") (pintype "passive"))
    )
    (net (code "204") (name "unconnected-(SV2-Pad18)") (class "Default")
      (node (ref "SV2") (pin "18") (pinfunction "18_18") (pintype "passive"))
    )
    (net (code "205") (name "unconnected-(SV2-Pad19)") (class "Default")
      (node (ref "SV2") (pin "19") (pinfunction "19_19") (pintype "passive"))
    )
    (net (code "206") (name "unconnected-(SV2-Pad20)") (class "Default")
      (node (ref "SV2") (pin "20") (pinfunction "20_20") (pintype "passive"))
    )
    (net (code "207") (name "unconnected-(SV2-Pad21)") (class "Default")
      (node (ref "SV2") (pin "21") (pinfunction "21_21") (pintype "passive"))
    )
    (net (code "208") (name "unconnected-(SV2-Pad22)") (class "Default")
      (node (ref "SV2") (pin "22") (pinfunction "22_22") (pintype "passive"))
    )
    (net (code "209") (name "unconnected-(SV2-Pad23)") (class "Default")
      (node (ref "SV2") (pin "23") (pinfunction "23_23") (pintype "passive"))
    )
    (net (code "210") (name "unconnected-(SV2-Pad24)") (class "Default")
      (node (ref "SV2") (pin "24") (pinfunction "24_24") (pintype "passive"))
    )
    (net (code "211") (name "unconnected-(SV2-Pad25)") (class "Default")
      (node (ref "SV2") (pin "25") (pinfunction "25_25") (pintype "passive"))
    )
    (net (code "212") (name "unconnected-(SV2-Pad26)") (class "Default")
      (node (ref "SV2") (pin "26") (pinfunction "26_26") (pintype "passive"))
    )
    (net (code "213") (name "unconnected-(SV2-Pad27)") (class "Default")
      (node (ref "SV2") (pin "27") (pinfunction "27_27") (pintype "passive"))
    )
    (net (code "214") (name "unconnected-(SV2-Pad28)") (class "Default")
      (node (ref "SV2") (pin "28") (pinfunction "28_28") (pintype "passive"))
    )
    (net (code "215") (name "unconnected-(SV2-Pad29)") (class "Default")
      (node (ref "SV2") (pin "29") (pinfunction "29_29") (pintype "passive"))
    )
    (net (code "216") (name "unconnected-(SV2-Pad30)") (class "Default")
      (node (ref "SV2") (pin "30") (pinfunction "30_30") (pintype "passive"))
    )
    (net (code "217") (name "unconnected-(SV2-Pad31)") (class "Default")
      (node (ref "SV2") (pin "31") (pinfunction "31_31") (pintype "passive"))
    )
    (net (code "218") (name "unconnected-(SV2-Pad32)") (class "Default")
      (node (ref "SV2") (pin "32") (pinfunction "32_32") (pintype "passive"))
    )
    (net (code "219") (name "unconnected-(SV2-Pad33)") (class "Default")
      (node (ref "SV2") (pin "33") (pinfunction "33_33") (pintype "passive"))
    )
    (net (code "220") (name "unconnected-(SV2-Pad34)") (class "Default")
      (node (ref "SV2") (pin "34") (pinfunction "34_34") (pintype "passive"))
    )
    (net (code "221") (name "unconnected-(SV2-Pad35)") (class "Default")
      (node (ref "SV2") (pin "35") (pinfunction "35_35") (pintype "passive"))
    )
    (net (code "222") (name "unconnected-(SV2-Pad36)") (class "Default")
      (node (ref "SV2") (pin "36") (pinfunction "36_36") (pintype "passive"))
    )
    (net (code "223") (name "unconnected-(SV2-Pad37)") (class "Default")
      (node (ref "SV2") (pin "37") (pinfunction "37_37") (pintype "passive"))
    )
    (net (code "224") (name "unconnected-(SV2-Pad38)") (class "Default")
      (node (ref "SV2") (pin "38") (pinfunction "38_38") (pintype "passive"))
    )
    (net (code "225") (name "unconnected-(SV2-Pad39)") (class "Default")
      (node (ref "SV2") (pin "39") (pinfunction "39_39") (pintype "passive"))
    )
    (net (code "226") (name "unconnected-(SV2-Pad40)") (class "Default")
      (node (ref "SV2") (pin "40") (pinfunction "40_40") (pintype "passive"))
    )
    (net (code "227") (name "unconnected-(SV3-Pad1)") (class "Default")
      (node (ref "SV3") (pin "1") (pinfunction "1_1") (pintype "passive"))
    )
    (net (code "228") (name "unconnected-(SV3-Pad2)") (class "Default")
      (node (ref "SV3") (pin "2") (pinfunction "2_2") (pintype "passive"))
    )
    (net (code "229") (name "unconnected-(SV3-Pad3)") (class "Default")
      (node (ref "SV3") (pin "3") (pinfunction "3_3") (pintype "passive"))
    )
    (net (code "230") (name "unconnected-(SV3-Pad4)") (class "Default")
      (node (ref "SV3") (pin "4") (pinfunction "4_4") (pintype "passive"))
    )
    (net (code "231") (name "unconnected-(SV3-Pad5)") (class "Default")
      (node (ref "SV3") (pin "5") (pinfunction "5_5") (pintype "passive"))
    )
    (net (code "232") (name "unconnected-(SV3-Pad6)") (class "Default")
      (node (ref "SV3") (pin "6") (pinfunction "6_6") (pintype "passive"))
    )
    (net (code "233") (name "unconnected-(SV3-Pad7)") (class "Default")
      (node (ref "SV3") (pin "7") (pinfunction "7_7") (pintype "passive"))
    )
    (net (code "234") (name "unconnected-(SV3-Pad8)") (class "Default")
      (node (ref "SV3") (pin "8") (pinfunction "8_8") (pintype "passive"))
    )
    (net (code "235") (name "unconnected-(SV3-Pad9)") (class "Default")
      (node (ref "SV3") (pin "9") (pinfunction "9_9") (pintype "passive"))
    )
    (net (code "236") (name "unconnected-(SV3-Pad10)") (class "Default")
      (node (ref "SV3") (pin "10") (pinfunction "10_10") (pintype "passive"))
    )
    (net (code "237") (name "unconnected-(SV3-Pad11)") (class "Default")
      (node (ref "SV3") (pin "11") (pinfunction "11_11") (pintype "passive"))
    )
    (net (code "238") (name "unconnected-(SV3-Pad12)") (class "Default")
      (node (ref "SV3") (pin "12") (pinfunction "12_12") (pintype "passive"))
    )
    (net (code "239") (name "unconnected-(SV3-Pad13)") (class "Default")
      (node (ref "SV3") (pin "13") (pinfunction "13_13") (pintype "passive"))
    )
    (net (code "240") (name "unconnected-(SV3-Pad14)") (class "Default")
      (node (ref "SV3") (pin "14") (pinfunction "14_14") (pintype "passive"))
    )
    (net (code "241") (name "unconnected-(SV3-Pad15)") (class "Default")
      (node (ref "SV3") (pin "15") (pinfunction "15_15") (pintype "passive"))
    )
    (net (code "242") (name "unconnected-(SV3-Pad16)") (class "Default")
      (node (ref "SV3") (pin "16") (pinfunction "16_16") (pintype "passive"))
    )
    (net (code "243") (name "unconnected-(SV3-Pad17)") (class "Default")
      (node (ref "SV3") (pin "17") (pinfunction "17_17") (pintype "passive"))
    )
    (net (code "244") (name "unconnected-(SV3-Pad18)") (class "Default")
      (node (ref "SV3") (pin "18") (pinfunction "18_18") (pintype "passive"))
    )
    (net (code "245") (name "unconnected-(SV3-Pad19)") (class "Default")
      (node (ref "SV3") (pin "19") (pinfunction "19_19") (pintype "passive"))
    )
    (net (code "246") (name "unconnected-(SV3-Pad20)") (class "Default")
      (node (ref "SV3") (pin "20") (pinfunction "20_20") (pintype "passive"))
    )
    (net (code "247") (name "unconnected-(SV3-Pad21)") (class "Default")
      (node (ref "SV3") (pin "21") (pinfunction "21_21") (pintype "passive"))
    )
    (net (code "248") (name "unconnected-(SV3-Pad22)") (class "Default")
      (node (ref "SV3") (pin "22") (pinfunction "22_22") (pintype "passive"))
    )
    (net (code "249") (name "unconnected-(SV3-Pad23)") (class "Default")
      (node (ref "SV3") (pin "23") (pinfunction "23_23") (pintype "passive"))
    )
    (net (code "250") (name "unconnected-(SV3-Pad24)") (class "Default")
      (node (ref "SV3") (pin "24") (pinfunction "24_24") (pintype "passive"))
    )
    (net (code "251") (name "unconnected-(SV3-Pad25)") (class "Default")
      (node (ref "SV3") (pin "25") (pinfunction "25_25") (pintype "passive"))
    )
    (net (code "252") (name "unconnected-(SV3-Pad26)") (class "Default")
      (node (ref "SV3") (pin "26") (pinfunction "26_26") (pintype "passive"))
    )
    (net (code "253") (name "unconnected-(SV3-Pad27)") (class "Default")
      (node (ref "SV3") (pin "27") (pinfunction "27_27") (pintype "passive"))
    )
    (net (code "254") (name "unconnected-(SV3-Pad28)") (class "Default")
      (node (ref "SV3") (pin "28") (pinfunction "28_28") (pintype "passive"))
    )
    (net (code "255") (name "unconnected-(SV3-Pad29)") (class "Default")
      (node (ref "SV3") (pin "29") (pinfunction "29_29") (pintype "passive"))
    )
    (net (code "256") (name "unconnected-(SV3-Pad30)") (class "Default")
      (node (ref "SV3") (pin "30") (pinfunction "30_30") (pintype "passive"))
    )
    (net (code "257") (name "unconnected-(SV3-Pad31)") (class "Default")
      (node (ref "SV3") (pin "31") (pinfunction "31_31") (pintype "passive"))
    )
    (net (code "258") (name "unconnected-(SV3-Pad32)") (class "Default")
      (node (ref "SV3") (pin "32") (pinfunction "32_32") (pintype "passive"))
    )
    (net (code "259") (name "unconnected-(SV3-Pad33)") (class "Default")
      (node (ref "SV3") (pin "33") (pinfunction "33_33") (pintype "passive"))
    )
    (net (code "260") (name "unconnected-(SV3-Pad34)") (class "Default")
      (node (ref "SV3") (pin "34") (pinfunction "34_34") (pintype "passive"))
    )
    (net (code "261") (name "unconnected-(SV3-Pad35)") (class "Default")
      (node (ref "SV3") (pin "35") (pinfunction "35_35") (pintype "passive"))
    )
    (net (code "262") (name "unconnected-(SV3-Pad36)") (class "Default")
      (node (ref "SV3") (pin "36") (pinfunction "36_36") (pintype "passive"))
    )
    (net (code "263") (name "unconnected-(SV3-Pad37)") (class "Default")
      (node (ref "SV3") (pin "37") (pinfunction "37_37") (pintype "passive"))
    )
    (net (code "264") (name "unconnected-(SV3-Pad38)") (class "Default")
      (node (ref "SV3") (pin "38") (pinfunction "38_38") (pintype "passive"))
    )
    (net (code "265") (name "unconnected-(SV3-Pad39)") (class "Default")
      (node (ref "SV3") (pin "39") (pinfunction "39_39") (pintype "passive"))
    )
    (net (code "266") (name "unconnected-(SV3-Pad40)") (class "Default")
      (node (ref "SV3") (pin "40") (pinfunction "40_40") (pintype "passive"))
    )
    (net (code "267") (name "unconnected-(SV4-Pad1)") (class "Default")
      (node (ref "SV4") (pin "1") (pinfunction "1_1") (pintype "passive"))
    )
    (net (code "268") (name "unconnected-(SV4-Pad2)") (class "Default")
      (node (ref "SV4") (pin "2") (pinfunction "2_2") (pintype "passive"))
    )
    (net (code "269") (name "unconnected-(SV4-Pad3)") (class "Default")
      (node (ref "SV4") (pin "3") (pinfunction "3_3") (pintype "passive"))
    )
    (net (code "270") (name "unconnected-(SV4-Pad4)") (class "Default")
      (node (ref "SV4") (pin "4") (pinfunction "4_4") (pintype "passive"))
    )
    (net (code "271") (name "unconnected-(SV4-Pad5)") (class "Default")
      (node (ref "SV4") (pin "5") (pinfunction "5_5") (pintype "passive"))
    )
    (net (code "272") (name "unconnected-(SV4-Pad6)") (class "Default")
      (node (ref "SV4") (pin "6") (pinfunction "6_6") (pintype "passive"))
    )
    (net (code "273") (name "unconnected-(SV4-Pad7)") (class "Default")
      (node (ref "SV4") (pin "7") (pinfunction "7_7") (pintype "passive"))
    )
    (net (code "274") (name "unconnected-(SV4-Pad8)") (class "Default")
      (node (ref "SV4") (pin "8") (pinfunction "8_8") (pintype "passive"))
    )
    (net (code "275") (name "unconnected-(SV4-Pad9)") (class "Default")
      (node (ref "SV4") (pin "9") (pinfunction "9_9") (pintype "passive"))
    )
    (net (code "276") (name "unconnected-(SV4-Pad10)") (class "Default")
      (node (ref "SV4") (pin "10") (pinfunction "10_10") (pintype "passive"))
    )
    (net (code "277") (name "unconnected-(SV4-Pad11)") (class "Default")
      (node (ref "SV4") (pin "11") (pinfunction "11_11") (pintype "passive"))
    )
    (net (code "278") (name "unconnected-(SV4-Pad12)") (class "Default")
      (node (ref "SV4") (pin "12") (pinfunction "12_12") (pintype "passive"))
    )
    (net (code "279") (name "unconnected-(SV4-Pad13)") (class "Default")
      (node (ref "SV4") (pin "13") (pinfunction "13_13") (pintype "passive"))
    )
    (net (code "280") (name "unconnected-(SV4-Pad14)") (class "Default")
      (node (ref "SV4") (pin "14") (pinfunction "14_14") (pintype "passive"))
    )
    (net (code "281") (name "unconnected-(SV4-Pad15)") (class "Default")
      (node (ref "SV4") (pin "15") (pinfunction "15_15") (pintype "passive"))
    )
    (net (code "282") (name "unconnected-(SV4-Pad16)") (class "Default")
      (node (ref "SV4") (pin "16") (pinfunction "16_16") (pintype "passive"))
    )
    (net (code "283") (name "unconnected-(SV4-Pad17)") (class "Default")
      (node (ref "SV4") (pin "17") (pinfunction "17_17") (pintype "passive"))
    )
    (net (code "284") (name "unconnected-(SV4-Pad18)") (class "Default")
      (node (ref "SV4") (pin "18") (pinfunction "18_18") (pintype "passive"))
    )
    (net (code "285") (name "unconnected-(SV4-Pad19)") (class "Default")
      (node (ref "SV4") (pin "19") (pinfunction "19_19") (pintype "passive"))
    )
    (net (code "286") (name "unconnected-(SV4-Pad20)") (class "Default")
      (node (ref "SV4") (pin "20") (pinfunction "20_20") (pintype "passive"))
    )
    (net (code "287") (name "unconnected-(SV4-Pad21)") (class "Default")
      (node (ref "SV4") (pin "21") (pinfunction "21_21") (pintype "passive"))
    )
    (net (code "288") (name "unconnected-(SV4-Pad22)") (class "Default")
      (node (ref "SV4") (pin "22") (pinfunction "22_22") (pintype "passive"))
    )
    (net (code "289") (name "unconnected-(SV4-Pad23)") (class "Default")
      (node (ref "SV4") (pin "23") (pinfunction "23_23") (pintype "passive"))
    )
    (net (code "290") (name "unconnected-(SV4-Pad24)") (class "Default")
      (node (ref "SV4") (pin "24") (pinfunction "24_24") (pintype "passive"))
    )
    (net (code "291") (name "unconnected-(SV4-Pad25)") (class "Default")
      (node (ref "SV4") (pin "25") (pinfunction "25_25") (pintype "passive"))
    )
    (net (code "292") (name "unconnected-(SV4-Pad26)") (class "Default")
      (node (ref "SV4") (pin "26") (pinfunction "26_26") (pintype "passive"))
    )
    (net (code "293") (name "unconnected-(SV4-Pad27)") (class "Default")
      (node (ref "SV4") (pin "27") (pinfunction "27_27") (pintype "passive"))
    )
    (net (code "294") (name "unconnected-(SV4-Pad28)") (class "Default")
      (node (ref "SV4") (pin "28") (pinfunction "28_28") (pintype "passive"))
    )
    (net (code "295") (name "unconnected-(SV4-Pad29)") (class "Default")
      (node (ref "SV4") (pin "29") (pinfunction "29_29") (pintype "passive"))
    )
    (net (code "296") (name "unconnected-(SV4-Pad30)") (class "Default")
      (node (ref "SV4") (pin "30") (pinfunction "30_30") (pintype "passive"))
    )
    (net (code "297") (name "unconnected-(SV4-Pad31)") (class "Default")
      (node (ref "SV4") (pin "31") (pinfunction "31_31") (pintype "passive"))
    )
    (net (code "298") (name "unconnected-(SV4-Pad32)") (class "Default")
      (node (ref "SV4") (pin "32") (pinfunction "32_32") (pintype "passive"))
    )
    (net (code "299") (name "unconnected-(SV4-Pad33)") (class "Default")
      (node (ref "SV4") (pin "33") (pinfunction "33_33") (pintype "passive"))
    )
    (net (code "300") (name "unconnected-(SV4-Pad34)") (class "Default")
      (node (ref "SV4") (pin "34") (pinfunction "34_34") (pintype "passive"))
    )
    (net (code "301") (name "unconnected-(SV4-Pad35)") (class "Default")
      (node (ref "SV4") (pin "35") (pinfunction "35_35") (pintype "passive"))
    )
    (net (code "302") (name "unconnected-(SV4-Pad36)") (class "Default")
      (node (ref "SV4") (pin "36") (pinfunction "36_36") (pintype "passive"))
    )
    (net (code "303") (name "unconnected-(SV4-Pad37)") (class "Default")
      (node (ref "SV4") (pin "37") (pinfunction "37_37") (pintype "passive"))
    )
    (net (code "304") (name "unconnected-(SV4-Pad38)") (class "Default")
      (node (ref "SV4") (pin "38") (pinfunction "38_38") (pintype "passive"))
    )
    (net (code "305") (name "unconnected-(SV4-Pad39)") (class "Default")
      (node (ref "SV4") (pin "39") (pinfunction "39_39") (pintype "passive"))
    )
    (net (code "306") (name "unconnected-(SV4-Pad40)") (class "Default")
      (node (ref "SV4") (pin "40") (pinfunction "40_40") (pintype "passive"))
    )
    (net (code "307") (name "unconnected-(SV5-Pad1)") (class "Default")
      (node (ref "SV5") (pin "1") (pinfunction "1_1") (pintype "passive"))
    )
    (net (code "308") (name "unconnected-(SV5-Pad2)") (class "Default")
      (node (ref "SV5") (pin "2") (pinfunction "2_2") (pintype "passive"))
    )
    (net (code "309") (name "unconnected-(SV5-Pad3)") (class "Default")
      (node (ref "SV5") (pin "3") (pinfunction "3_3") (pintype "passive"))
    )
    (net (code "310") (name "unconnected-(SV5-Pad4)") (class "Default")
      (node (ref "SV5") (pin "4") (pinfunction "4_4") (pintype "passive"))
    )
    (net (code "311") (name "unconnected-(SV5-Pad5)") (class "Default")
      (node (ref "SV5") (pin "5") (pinfunction "5_5") (pintype "passive"))
    )
    (net (code "312") (name "unconnected-(SV5-Pad6)") (class "Default")
      (node (ref "SV5") (pin "6") (pinfunction "6_6") (pintype "passive"))
    )
    (net (code "313") (name "unconnected-(SV5-Pad7)") (class "Default")
      (node (ref "SV5") (pin "7") (pinfunction "7_7") (pintype "passive"))
    )
    (net (code "314") (name "unconnected-(SV5-Pad8)") (class "Default")
      (node (ref "SV5") (pin "8") (pinfunction "8_8") (pintype "passive"))
    )
    (net (code "315") (name "unconnected-(SV5-Pad9)") (class "Default")
      (node (ref "SV5") (pin "9") (pinfunction "9_9") (pintype "passive"))
    )
    (net (code "316") (name "unconnected-(SV5-Pad10)") (class "Default")
      (node (ref "SV5") (pin "10") (pinfunction "10_10") (pintype "passive"))
    )
    (net (code "317") (name "unconnected-(SV5-Pad11)") (class "Default")
      (node (ref "SV5") (pin "11") (pinfunction "11_11") (pintype "passive"))
    )
    (net (code "318") (name "unconnected-(SV5-Pad12)") (class "Default")
      (node (ref "SV5") (pin "12") (pinfunction "12_12") (pintype "passive"))
    )
    (net (code "319") (name "unconnected-(SV5-Pad13)") (class "Default")
      (node (ref "SV5") (pin "13") (pinfunction "13_13") (pintype "passive"))
    )
    (net (code "320") (name "unconnected-(SV5-Pad14)") (class "Default")
      (node (ref "SV5") (pin "14") (pinfunction "14_14") (pintype "passive"))
    )
    (net (code "321") (name "unconnected-(SV5-Pad15)") (class "Default")
      (node (ref "SV5") (pin "15") (pinfunction "15_15") (pintype "passive"))
    )
    (net (code "322") (name "unconnected-(SV5-Pad16)") (class "Default")
      (node (ref "SV5") (pin "16") (pinfunction "16_16") (pintype "passive"))
    )
    (net (code "323") (name "unconnected-(SV5-Pad17)") (class "Default")
      (node (ref "SV5") (pin "17") (pinfunction "17_17") (pintype "passive"))
    )
    (net (code "324") (name "unconnected-(SV5-Pad18)") (class "Default")
      (node (ref "SV5") (pin "18") (pinfunction "18_18") (pintype "passive"))
    )
    (net (code "325") (name "unconnected-(SV5-Pad19)") (class "Default")
      (node (ref "SV5") (pin "19") (pinfunction "19_19") (pintype "passive"))
    )
    (net (code "326") (name "unconnected-(SV5-Pad20)") (class "Default")
      (node (ref "SV5") (pin "20") (pinfunction "20_20") (pintype "passive"))
    )
    (net (code "327") (name "unconnected-(SV5-Pad21)") (class "Default")
      (node (ref "SV5") (pin "21") (pinfunction "21_21") (pintype "passive"))
    )
    (net (code "328") (name "unconnected-(SV5-Pad22)") (class "Default")
      (node (ref "SV5") (pin "22") (pinfunction "22_22") (pintype "passive"))
    )
    (net (code "329") (name "unconnected-(SV5-Pad23)") (class "Default")
      (node (ref "SV5") (pin "23") (pinfunction "23_23") (pintype "passive"))
    )
    (net (code "330") (name "unconnected-(SV5-Pad24)") (class "Default")
      (node (ref "SV5") (pin "24") (pinfunction "24_24") (pintype "passive"))
    )
    (net (code "331") (name "unconnected-(SV5-Pad25)") (class "Default")
      (node (ref "SV5") (pin "25") (pinfunction "25_25") (pintype "passive"))
    )
    (net (code "332") (name "unconnected-(SV5-Pad26)") (class "Default")
      (node (ref "SV5") (pin "26") (pinfunction "26_26") (pintype "passive"))
    )
    (net (code "333") (name "unconnected-(SV5-Pad27)") (class "Default")
      (node (ref "SV5") (pin "27") (pinfunction "27_27") (pintype "passive"))
    )
    (net (code "334") (name "unconnected-(SV5-Pad28)") (class "Default")
      (node (ref "SV5") (pin "28") (pinfunction "28_28") (pintype "passive"))
    )
    (net (code "335") (name "unconnected-(SV5-Pad29)") (class "Default")
      (node (ref "SV5") (pin "29") (pinfunction "29_29") (pintype "passive"))
    )
    (net (code "336") (name "unconnected-(SV5-Pad30)") (class "Default")
      (node (ref "SV5") (pin "30") (pinfunction "30_30") (pintype "passive"))
    )
    (net (code "337") (name "unconnected-(SV5-Pad31)") (class "Default")
      (node (ref "SV5") (pin "31") (pinfunction "31_31") (pintype "passive"))
    )
    (net (code "338") (name "unconnected-(SV5-Pad32)") (class "Default")
      (node (ref "SV5") (pin "32") (pinfunction "32_32") (pintype "passive"))
    )
    (net (code "339") (name "unconnected-(SV5-Pad33)") (class "Default")
      (node (ref "SV5") (pin "33") (pinfunction "33_33") (pintype "passive"))
    )
    (net (code "340") (name "unconnected-(SV5-Pad34)") (class "Default")
      (node (ref "SV5") (pin "34") (pinfunction "34_34") (pintype "passive"))
    )
    (net (code "341") (name "unconnected-(SV5-Pad35)") (class "Default")
      (node (ref "SV5") (pin "35") (pinfunction "35_35") (pintype "passive"))
    )
    (net (code "342") (name "unconnected-(SV5-Pad36)") (class "Default")
      (node (ref "SV5") (pin "36") (pinfunction "36_36") (pintype "passive"))
    )
    (net (code "343") (name "unconnected-(SV6-Pad1)") (class "Default")
      (node (ref "SV6") (pin "1") (pinfunction "1_1") (pintype "passive"))
    )
    (net (code "344") (name "unconnected-(SV6-Pad2)") (class "Default")
      (node (ref "SV6") (pin "2") (pinfunction "2_2") (pintype "passive"))
    )
    (net (code "345") (name "unconnected-(SV6-Pad3)") (class "Default")
      (node (ref "SV6") (pin "3") (pinfunction "3_3") (pintype "passive"))
    )
    (net (code "346") (name "unconnected-(SV6-Pad4)") (class "Default")
      (node (ref "SV6") (pin "4") (pinfunction "4_4") (pintype "passive"))
    )
    (net (code "347") (name "unconnected-(SV6-Pad5)") (class "Default")
      (node (ref "SV6") (pin "5") (pinfunction "5_5") (pintype "passive"))
    )
    (net (code "348") (name "unconnected-(SV6-Pad6)") (class "Default")
      (node (ref "SV6") (pin "6") (pinfunction "6_6") (pintype "passive"))
    )
    (net (code "349") (name "unconnected-(SV6-Pad7)") (class "Default")
      (node (ref "SV6") (pin "7") (pinfunction "7_7") (pintype "passive"))
    )
    (net (code "350") (name "unconnected-(SV6-Pad8)") (class "Default")
      (node (ref "SV6") (pin "8") (pinfunction "8_8") (pintype "passive"))
    )
    (net (code "351") (name "unconnected-(SV6-Pad9)") (class "Default")
      (node (ref "SV6") (pin "9") (pinfunction "9_9") (pintype "passive"))
    )
    (net (code "352") (name "unconnected-(SV6-Pad10)") (class "Default")
      (node (ref "SV6") (pin "10") (pinfunction "10_10") (pintype "passive"))
    )
    (net (code "353") (name "unconnected-(SV6-Pad11)") (class "Default")
      (node (ref "SV6") (pin "11") (pinfunction "11_11") (pintype "passive"))
    )
    (net (code "354") (name "unconnected-(SV6-Pad12)") (class "Default")
      (node (ref "SV6") (pin "12") (pinfunction "12_12") (pintype "passive"))
    )
    (net (code "355") (name "unconnected-(SV6-Pad13)") (class "Default")
      (node (ref "SV6") (pin "13") (pinfunction "13_13") (pintype "passive"))
    )
    (net (code "356") (name "unconnected-(SV6-Pad14)") (class "Default")
      (node (ref "SV6") (pin "14") (pinfunction "14_14") (pintype "passive"))
    )
    (net (code "357") (name "unconnected-(SV6-Pad15)") (class "Default")
      (node (ref "SV6") (pin "15") (pinfunction "15_15") (pintype "passive"))
    )
    (net (code "358") (name "unconnected-(SV6-Pad16)") (class "Default")
      (node (ref "SV6") (pin "16") (pinfunction "16_16") (pintype "passive"))
    )
    (net (code "359") (name "unconnected-(SV6-Pad17)") (class "Default")
      (node (ref "SV6") (pin "17") (pinfunction "17_17") (pintype "passive"))
    )
    (net (code "360") (name "unconnected-(SV6-Pad18)") (class "Default")
      (node (ref "SV6") (pin "18") (pinfunction "18_18") (pintype "passive"))
    )
    (net (code "361") (name "unconnected-(SV6-Pad19)") (class "Default")
      (node (ref "SV6") (pin "19") (pinfunction "19_19") (pintype "passive"))
    )
    (net (code "362") (name "unconnected-(SV6-Pad20)") (class "Default")
      (node (ref "SV6") (pin "20") (pinfunction "20_20") (pintype "passive"))
    )
    (net (code "363") (name "unconnected-(SV6-Pad21)") (class "Default")
      (node (ref "SV6") (pin "21") (pinfunction "21_21") (pintype "passive"))
    )
    (net (code "364") (name "unconnected-(SV6-Pad22)") (class "Default")
      (node (ref "SV6") (pin "22") (pinfunction "22_22") (pintype "passive"))
    )
    (net (code "365") (name "unconnected-(SV6-Pad23)") (class "Default")
      (node (ref "SV6") (pin "23") (pinfunction "23_23") (pintype "passive"))
    )
    (net (code "366") (name "unconnected-(SV6-Pad24)") (class "Default")
      (node (ref "SV6") (pin "24") (pinfunction "24_24") (pintype "passive"))
    )
    (net (code "367") (name "unconnected-(SV6-Pad25)") (class "Default")
      (node (ref "SV6") (pin "25") (pinfunction "25_25") (pintype "passive"))
    )
    (net (code "368") (name "unconnected-(SV6-Pad26)") (class "Default")
      (node (ref "SV6") (pin "26") (pinfunction "26_26") (pintype "passive"))
    )
    (net (code "369") (name "unconnected-(SV6-Pad27)") (class "Default")
      (node (ref "SV6") (pin "27") (pinfunction "27_27") (pintype "passive"))
    )
    (net (code "370") (name "unconnected-(SV6-Pad28)") (class "Default")
      (node (ref "SV6") (pin "28") (pinfunction "28_28") (pintype "passive"))
    )
    (net (code "371") (name "unconnected-(SV6-Pad29)") (class "Default")
      (node (ref "SV6") (pin "29") (pinfunction "29_29") (pintype "passive"))
    )
    (net (code "372") (name "unconnected-(SV6-Pad30)") (class "Default")
      (node (ref "SV6") (pin "30") (pinfunction "30_30") (pintype "passive"))
    )
    (net (code "373") (name "unconnected-(SV6-Pad31)") (class "Default")
      (node (ref "SV6") (pin "31") (pinfunction "31_31") (pintype "passive"))
    )
    (net (code "374") (name "unconnected-(SV6-Pad32)") (class "Default")
      (node (ref "SV6") (pin "32") (pinfunction "32_32") (pintype "passive"))
    )
    (net (code "375") (name "unconnected-(SV6-Pad33)") (class "Default")
      (node (ref "SV6") (pin "33") (pinfunction "33_33") (pintype "passive"))
    )
    (net (code "376") (name "unconnected-(SV6-Pad34)") (class "Default")
      (node (ref "SV6") (pin "34") (pinfunction "34_34") (pintype "passive"))
    )
    (net (code "377") (name "unconnected-(SV6-Pad35)") (class "Default")
      (node (ref "SV6") (pin "35") (pinfunction "35_35") (pintype "passive"))
    )
    (net (code "378") (name "unconnected-(SV6-Pad36)") (class "Default")
      (node (ref "SV6") (pin "36") (pinfunction "36_36") (pintype "passive"))
    )
    (net (code "379") (name "unconnected-(SV7-Pad1)") (class "Default")
      (node (ref "SV7") (pin "1") (pinfunction "1_1") (pintype "passive"))
    )
    (net (code "380") (name "unconnected-(SV7-Pad2)") (class "Default")
      (node (ref "SV7") (pin "2") (pinfunction "2_2") (pintype "passive"))
    )
    (net (code "381") (name "unconnected-(SV7-Pad3)") (class "Default")
      (node (ref "SV7") (pin "3") (pinfunction "3_3") (pintype "passive"))
    )
    (net (code "382") (name "unconnected-(SV7-Pad4)") (class "Default")
      (node (ref "SV7") (pin "4") (pinfunction "4_4") (pintype "passive"))
    )
    (net (code "383") (name "unconnected-(SV7-Pad5)") (class "Default")
      (node (ref "SV7") (pin "5") (pinfunction "5_5") (pintype "passive"))
    )
    (net (code "384") (name "unconnected-(SV7-Pad6)") (class "Default")
      (node (ref "SV7") (pin "6") (pinfunction "6_6") (pintype "passive"))
    )
    (net (code "385") (name "unconnected-(SV7-Pad7)") (class "Default")
      (node (ref "SV7") (pin "7") (pinfunction "7_7") (pintype "passive"))
    )
    (net (code "386") (name "unconnected-(SV7-Pad8)") (class "Default")
      (node (ref "SV7") (pin "8") (pinfunction "8_8") (pintype "passive"))
    )
    (net (code "387") (name "unconnected-(SV7-Pad9)") (class "Default")
      (node (ref "SV7") (pin "9") (pinfunction "9_9") (pintype "passive"))
    )
    (net (code "388") (name "unconnected-(SV7-Pad10)") (class "Default")
      (node (ref "SV7") (pin "10") (pinfunction "10_10") (pintype "passive"))
    )
    (net (code "389") (name "unconnected-(SV7-Pad11)") (class "Default")
      (node (ref "SV7") (pin "11") (pinfunction "11_11") (pintype "passive"))
    )
    (net (code "390") (name "unconnected-(SV7-Pad12)") (class "Default")
      (node (ref "SV7") (pin "12") (pinfunction "12_12") (pintype "passive"))
    )
    (net (code "391") (name "unconnected-(SV7-Pad13)") (class "Default")
      (node (ref "SV7") (pin "13") (pinfunction "13_13") (pintype "passive"))
    )
    (net (code "392") (name "unconnected-(SV7-Pad14)") (class "Default")
      (node (ref "SV7") (pin "14") (pinfunction "14_14") (pintype "passive"))
    )
    (net (code "393") (name "unconnected-(SV7-Pad15)") (class "Default")
      (node (ref "SV7") (pin "15") (pinfunction "15_15") (pintype "passive"))
    )
    (net (code "394") (name "unconnected-(SV7-Pad16)") (class "Default")
      (node (ref "SV7") (pin "16") (pinfunction "16_16") (pintype "passive"))
    )
    (net (code "395") (name "unconnected-(SV7-Pad17)") (class "Default")
      (node (ref "SV7") (pin "17") (pinfunction "17_17") (pintype "passive"))
    )
    (net (code "396") (name "unconnected-(SV7-Pad18)") (class "Default")
      (node (ref "SV7") (pin "18") (pinfunction "18_18") (pintype "passive"))
    )
    (net (code "397") (name "unconnected-(SV7-Pad19)") (class "Default")
      (node (ref "SV7") (pin "19") (pinfunction "19_19") (pintype "passive"))
    )
    (net (code "398") (name "unconnected-(SV7-Pad20)") (class "Default")
      (node (ref "SV7") (pin "20") (pinfunction "20_20") (pintype "passive"))
    )
    (net (code "399") (name "unconnected-(SV7-Pad21)") (class "Default")
      (node (ref "SV7") (pin "21") (pinfunction "21_21") (pintype "passive"))
    )
    (net (code "400") (name "unconnected-(SV7-Pad22)") (class "Default")
      (node (ref "SV7") (pin "22") (pinfunction "22_22") (pintype "passive"))
    )
    (net (code "401") (name "unconnected-(SV7-Pad23)") (class "Default")
      (node (ref "SV7") (pin "23") (pinfunction "23_23") (pintype "passive"))
    )
    (net (code "402") (name "unconnected-(SV7-Pad24)") (class "Default")
      (node (ref "SV7") (pin "24") (pinfunction "24_24") (pintype "passive"))
    )
    (net (code "403") (name "unconnected-(SV7-Pad25)") (class "Default")
      (node (ref "SV7") (pin "25") (pinfunction "25_25") (pintype "passive"))
    )
    (net (code "404") (name "unconnected-(SV7-Pad26)") (class "Default")
      (node (ref "SV7") (pin "26") (pinfunction "26_26") (pintype "passive"))
    )
    (net (code "405") (name "unconnected-(SV7-Pad27)") (class "Default")
      (node (ref "SV7") (pin "27") (pinfunction "27_27") (pintype "passive"))
    )
    (net (code "406") (name "unconnected-(SV7-Pad28)") (class "Default")
      (node (ref "SV7") (pin "28") (pinfunction "28_28") (pintype "passive"))
    )
    (net (code "407") (name "unconnected-(SV7-Pad29)") (class "Default")
      (node (ref "SV7") (pin "29") (pinfunction "29_29") (pintype "passive"))
    )
    (net (code "408") (name "unconnected-(SV7-Pad30)") (class "Default")
      (node (ref "SV7") (pin "30") (pinfunction "30_30") (pintype "passive"))
    )
    (net (code "409") (name "unconnected-(SV7-Pad31)") (class "Default")
      (node (ref "SV7") (pin "31") (pinfunction "31_31") (pintype "passive"))
    )
    (net (code "410") (name "unconnected-(SV7-Pad32)") (class "Default")
      (node (ref "SV7") (pin "32") (pinfunction "32_32") (pintype "passive"))
    )
    (net (code "411") (name "unconnected-(SV7-Pad33)") (class "Default")
      (node (ref "SV7") (pin "33") (pinfunction "33_33") (pintype "passive"))
    )
    (net (code "412") (name "unconnected-(SV7-Pad34)") (class "Default")
      (node (ref "SV7") (pin "34") (pinfunction "34_34") (pintype "passive"))
    )
    (net (code "413") (name "unconnected-(SV7-Pad35)") (class "Default")
      (node (ref "SV7") (pin "35") (pinfunction "35_35") (pintype "passive"))
    )
    (net (code "414") (name "unconnected-(SV7-Pad36)") (class "Default")
      (node (ref "SV7") (pin "36") (pinfunction "36_36") (pintype "passive"))
    )
    (net (code "415") (name "unconnected-(SV8-Pad1)") (class "Default")
      (node (ref "SV8") (pin "1") (pinfunction "1_1") (pintype "passive"))
    )
    (net (code "416") (name "unconnected-(SV8-Pad2)") (class "Default")
      (node (ref "SV8") (pin "2") (pinfunction "2_2") (pintype "passive"))
    )
    (net (code "417") (name "unconnected-(SV8-Pad3)") (class "Default")
      (node (ref "SV8") (pin "3") (pinfunction "3_3") (pintype "passive"))
    )
    (net (code "418") (name "unconnected-(SV8-Pad4)") (class "Default")
      (node (ref "SV8") (pin "4") (pinfunction "4_4") (pintype "passive"))
    )
    (net (code "419") (name "unconnected-(SV8-Pad5)") (class "Default")
      (node (ref "SV8") (pin "5") (pinfunction "5_5") (pintype "passive"))
    )
    (net (code "420") (name "unconnected-(SV8-Pad6)") (class "Default")
      (node (ref "SV8") (pin "6") (pinfunction "6_6") (pintype "passive"))
    )
    (net (code "421") (name "unconnected-(SV8-Pad7)") (class "Default")
      (node (ref "SV8") (pin "7") (pinfunction "7_7") (pintype "passive"))
    )
    (net (code "422") (name "unconnected-(SV8-Pad8)") (class "Default")
      (node (ref "SV8") (pin "8") (pinfunction "8_8") (pintype "passive"))
    )
    (net (code "423") (name "unconnected-(SV8-Pad9)") (class "Default")
      (node (ref "SV8") (pin "9") (pinfunction "9_9") (pintype "passive"))
    )
    (net (code "424") (name "unconnected-(SV8-Pad10)") (class "Default")
      (node (ref "SV8") (pin "10") (pinfunction "10_10") (pintype "passive"))
    )
    (net (code "425") (name "unconnected-(SV8-Pad11)") (class "Default")
      (node (ref "SV8") (pin "11") (pinfunction "11_11") (pintype "passive"))
    )
    (net (code "426") (name "unconnected-(SV8-Pad12)") (class "Default")
      (node (ref "SV8") (pin "12") (pinfunction "12_12") (pintype "passive"))
    )
    (net (code "427") (name "unconnected-(SV8-Pad13)") (class "Default")
      (node (ref "SV8") (pin "13") (pinfunction "13_13") (pintype "passive"))
    )
    (net (code "428") (name "unconnected-(SV8-Pad14)") (class "Default")
      (node (ref "SV8") (pin "14") (pinfunction "14_14") (pintype "passive"))
    )
    (net (code "429") (name "unconnected-(SV8-Pad15)") (class "Default")
      (node (ref "SV8") (pin "15") (pinfunction "15_15") (pintype "passive"))
    )
    (net (code "430") (name "unconnected-(SV8-Pad16)") (class "Default")
      (node (ref "SV8") (pin "16") (pinfunction "16_16") (pintype "passive"))
    )
    (net (code "431") (name "unconnected-(SV8-Pad17)") (class "Default")
      (node (ref "SV8") (pin "17") (pinfunction "17_17") (pintype "passive"))
    )
    (net (code "432") (name "unconnected-(SV8-Pad18)") (class "Default")
      (node (ref "SV8") (pin "18") (pinfunction "18_18") (pintype "passive"))
    )
    (net (code "433") (name "unconnected-(SV8-Pad19)") (class "Default")
      (node (ref "SV8") (pin "19") (pinfunction "19_19") (pintype "passive"))
    )
    (net (code "434") (name "unconnected-(SV8-Pad20)") (class "Default")
      (node (ref "SV8") (pin "20") (pinfunction "20_20") (pintype "passive"))
    )
    (net (code "435") (name "unconnected-(SV8-Pad21)") (class "Default")
      (node (ref "SV8") (pin "21") (pinfunction "21_21") (pintype "passive"))
    )
    (net (code "436") (name "unconnected-(SV8-Pad22)") (class "Default")
      (node (ref "SV8") (pin "22") (pinfunction "22_22") (pintype "passive"))
    )
    (net (code "437") (name "unconnected-(SV8-Pad23)") (class "Default")
      (node (ref "SV8") (pin "23") (pinfunction "23_23") (pintype "passive"))
    )
    (net (code "438") (name "unconnected-(SV8-Pad24)") (class "Default")
      (node (ref "SV8") (pin "24") (pinfunction "24_24") (pintype "passive"))
    )
    (net (code "439") (name "unconnected-(SV8-Pad25)") (class "Default")
      (node (ref "SV8") (pin "25") (pinfunction "25_25") (pintype "passive"))
    )
    (net (code "440") (name "unconnected-(SV8-Pad26)") (class "Default")
      (node (ref "SV8") (pin "26") (pinfunction "26_26") (pintype "passive"))
    )
    (net (code "441") (name "unconnected-(SV8-Pad27)") (class "Default")
      (node (ref "SV8") (pin "27") (pinfunction "27_27") (pintype "passive"))
    )
    (net (code "442") (name "unconnected-(SV8-Pad28)") (class "Default")
      (node (ref "SV8") (pin "28") (pinfunction "28_28") (pintype "passive"))
    )
    (net (code "443") (name "unconnected-(SV8-Pad29)") (class "Default")
      (node (ref "SV8") (pin "29") (pinfunction "29_29") (pintype "passive"))
    )
    (net (code "444") (name "unconnected-(SV8-Pad30)") (class "Default")
      (node (ref "SV8") (pin "30") (pinfunction "30_30") (pintype "passive"))
    )
    (net (code "445") (name "unconnected-(SV8-Pad31)") (class "Default")
      (node (ref "SV8") (pin "31") (pinfunction "31_31") (pintype "passive"))
    )
    (net (code "446") (name "unconnected-(SV8-Pad32)") (class "Default")
      (node (ref "SV8") (pin "32") (pinfunction "32_32") (pintype "passive"))
    )
    (net (code "447") (name "unconnected-(SV8-Pad33)") (class "Default")
      (node (ref "SV8") (pin "33") (pinfunction "33_33") (pintype "passive"))
    )
    (net (code "448") (name "unconnected-(SV8-Pad34)") (class "Default")
      (node (ref "SV8") (pin "34") (pinfunction "34_34") (pintype "passive"))
    )
    (net (code "449") (name "unconnected-(SV8-Pad35)") (class "Default")
      (node (ref "SV8") (pin "35") (pinfunction "35_35") (pintype "passive"))
    )
    (net (code "450") (name "unconnected-(SV8-Pad36)") (class "Default")
      (node (ref "SV8") (pin "36") (pinfunction "36_36") (pintype "passive"))
    )
    (net (code "451") (name "unconnected-(SV9-Pad1)") (class "Default")
      (node (ref "SV9") (pin "1") (pinfunction "1_1") (pintype "passive"))
    )
    (net (code "452") (name "unconnected-(SV9-Pad2)") (class "Default")
      (node (ref "SV9") (pin "2") (pinfunction "2_2") (pintype "passive"))
    )
    (net (code "453") (name "unconnected-(SV9-Pad3)") (class "Default")
      (node (ref "SV9") (pin "3") (pinfunction "3_3") (pintype "passive"))
    )
    (net (code "454") (name "unconnected-(SV9-Pad4)") (class "Default")
      (node (ref "SV9") (pin "4") (pinfunction "4_4") (pintype "passive"))
    )
    (net (code "455") (name "unconnected-(SV9-Pad5)") (class "Default")
      (node (ref "SV9") (pin "5") (pinfunction "5_5") (pintype "passive"))
    )
    (net (code "456") (name "unconnected-(SV9-Pad6)") (class "Default")
      (node (ref "SV9") (pin "6") (pinfunction "6_6") (pintype "passive"))
    )
    (net (code "457") (name "unconnected-(SV9-Pad7)") (class "Default")
      (node (ref "SV9") (pin "7") (pinfunction "7_7") (pintype "passive"))
    )
    (net (code "458") (name "unconnected-(SV9-Pad8)") (class "Default")
      (node (ref "SV9") (pin "8") (pinfunction "8_8") (pintype "passive"))
    )
    (net (code "459") (name "unconnected-(SV9-Pad9)") (class "Default")
      (node (ref "SV9") (pin "9") (pinfunction "9_9") (pintype "passive"))
    )
    (net (code "460") (name "unconnected-(SV9-Pad10)") (class "Default")
      (node (ref "SV9") (pin "10") (pinfunction "10_10") (pintype "passive"))
    )
    (net (code "461") (name "unconnected-(SV9-Pad11)") (class "Default")
      (node (ref "SV9") (pin "11") (pinfunction "11_11") (pintype "passive"))
    )
    (net (code "462") (name "unconnected-(SV9-Pad12)") (class "Default")
      (node (ref "SV9") (pin "12") (pinfunction "12_12") (pintype "passive"))
    )
    (net (code "463") (name "unconnected-(SV9-Pad13)") (class "Default")
      (node (ref "SV9") (pin "13") (pinfunction "13_13") (pintype "passive"))
    )
    (net (code "464") (name "unconnected-(SV9-Pad14)") (class "Default")
      (node (ref "SV9") (pin "14") (pinfunction "14_14") (pintype "passive"))
    )
    (net (code "465") (name "unconnected-(SV9-Pad15)") (class "Default")
      (node (ref "SV9") (pin "15") (pinfunction "15_15") (pintype "passive"))
    )
    (net (code "466") (name "unconnected-(SV9-Pad16)") (class "Default")
      (node (ref "SV9") (pin "16") (pinfunction "16_16") (pintype "passive"))
    )
    (net (code "467") (name "unconnected-(SV9-Pad17)") (class "Default")
      (node (ref "SV9") (pin "17") (pinfunction "17_17") (pintype "passive"))
    )
    (net (code "468") (name "unconnected-(SV9-Pad18)") (class "Default")
      (node (ref "SV9") (pin "18") (pinfunction "18_18") (pintype "passive"))
    )
    (net (code "469") (name "unconnected-(SV9-Pad19)") (class "Default")
      (node (ref "SV9") (pin "19") (pinfunction "19_19") (pintype "passive"))
    )
    (net (code "470") (name "unconnected-(SV9-Pad20)") (class "Default")
      (node (ref "SV9") (pin "20") (pinfunction "20_20") (pintype "passive"))
    )
    (net (code "471") (name "unconnected-(SV9-Pad21)") (class "Default")
      (node (ref "SV9") (pin "21") (pinfunction "21_21") (pintype "passive"))
    )
    (net (code "472") (name "unconnected-(SV9-Pad22)") (class "Default")
      (node (ref "SV9") (pin "22") (pinfunction "22_22") (pintype "passive"))
    )
    (net (code "473") (name "unconnected-(SV9-Pad23)") (class "Default")
      (node (ref "SV9") (pin "23") (pinfunction "23_23") (pintype "passive"))
    )
    (net (code "474") (name "unconnected-(SV9-Pad24)") (class "Default")
      (node (ref "SV9") (pin "24") (pinfunction "24_24") (pintype "passive"))
    )
    (net (code "475") (name "unconnected-(SV9-Pad25)") (class "Default")
      (node (ref "SV9") (pin "25") (pinfunction "25_25") (pintype "passive"))
    )
    (net (code "476") (name "unconnected-(SV9-Pad26)") (class "Default")
      (node (ref "SV9") (pin "26") (pinfunction "26_26") (pintype "passive"))
    )
    (net (code "477") (name "unconnected-(SV9-Pad27)") (class "Default")
      (node (ref "SV9") (pin "27") (pinfunction "27_27") (pintype "passive"))
    )
    (net (code "478") (name "unconnected-(SV9-Pad28)") (class "Default")
      (node (ref "SV9") (pin "28") (pinfunction "28_28") (pintype "passive"))
    )
    (net (code "479") (name "unconnected-(SV9-Pad29)") (class "Default")
      (node (ref "SV9") (pin "29") (pinfunction "29_29") (pintype "passive"))
    )
    (net (code "480") (name "unconnected-(SV9-Pad30)") (class "Default")
      (node (ref "SV9") (pin "30") (pinfunction "30_30") (pintype "passive"))
    )
    (net (code "481") (name "unconnected-(SV9-Pad31)") (class "Default")
      (node (ref "SV9") (pin "31") (pinfunction "31_31") (pintype "passive"))
    )
    (net (code "482") (name "unconnected-(SV9-Pad32)") (class "Default")
      (node (ref "SV9") (pin "32") (pinfunction "32_32") (pintype "passive"))
    )
    (net (code "483") (name "unconnected-(SV9-Pad33)") (class "Default")
      (node (ref "SV9") (pin "33") (pinfunction "33_33") (pintype "passive"))
    )
    (net (code "484") (name "unconnected-(SV9-Pad34)") (class "Default")
      (node (ref "SV9") (pin "34") (pinfunction "34_34") (pintype "passive"))
    )
    (net (code "485") (name "unconnected-(SV9-Pad35)") (class "Default")
      (node (ref "SV9") (pin "35") (pinfunction "35_35") (pintype "passive"))
    )
    (net (code "486") (name "unconnected-(SV9-Pad36)") (class "Default")
      (node (ref "SV9") (pin "36") (pinfunction "36_36") (pintype "passive"))
    )
    (net (code "487") (name "unconnected-(SV10-Pad1)") (class "Default")
      (node (ref "SV10") (pin "1") (pinfunction "1_1") (pintype "passive"))
    )
    (net (code "488") (name "unconnected-(SV10-Pad2)") (class "Default")
      (node (ref "SV10") (pin "2") (pinfunction "2_2") (pintype "passive"))
    )
    (net (code "489") (name "unconnected-(SV10-Pad3)") (class "Default")
      (node (ref "SV10") (pin "3") (pinfunction "3_3") (pintype "passive"))
    )
    (net (code "490") (name "unconnected-(SV10-Pad4)") (class "Default")
      (node (ref "SV10") (pin "4") (pinfunction "4_4") (pintype "passive"))
    )
    (net (code "491") (name "unconnected-(SV10-Pad5)") (class "Default")
      (node (ref "SV10") (pin "5") (pinfunction "5_5") (pintype "passive"))
    )
    (net (code "492") (name "unconnected-(SV10-Pad6)") (class "Default")
      (node (ref "SV10") (pin "6") (pinfunction "6_6") (pintype "passive"))
    )
    (net (code "493") (name "unconnected-(SV10-Pad7)") (class "Default")
      (node (ref "SV10") (pin "7") (pinfunction "7_7") (pintype "passive"))
    )
    (net (code "494") (name "unconnected-(SV10-Pad8)") (class "Default")
      (node (ref "SV10") (pin "8") (pinfunction "8_8") (pintype "passive"))
    )
    (net (code "495") (name "unconnected-(SV10-Pad9)") (class "Default")
      (node (ref "SV10") (pin "9") (pinfunction "9_9") (pintype "passive"))
    )
    (net (code "496") (name "unconnected-(SV10-Pad10)") (class "Default")
      (node (ref "SV10") (pin "10") (pinfunction "10_10") (pintype "passive"))
    )
    (net (code "497") (name "unconnected-(SV10-Pad11)") (class "Default")
      (node (ref "SV10") (pin "11") (pinfunction "11_11") (pintype "passive"))
    )
    (net (code "498") (name "unconnected-(SV10-Pad12)") (class "Default")
      (node (ref "SV10") (pin "12") (pinfunction "12_12") (pintype "passive"))
    )
    (net (code "499") (name "unconnected-(SV10-Pad13)") (class "Default")
      (node (ref "SV10") (pin "13") (pinfunction "13_13") (pintype "passive"))
    )
    (net (code "500") (name "unconnected-(SV10-Pad14)") (class "Default")
      (node (ref "SV10") (pin "14") (pinfunction "14_14") (pintype "passive"))
    )
    (net (code "501") (name "unconnected-(SV10-Pad15)") (class "Default")
      (node (ref "SV10") (pin "15") (pinfunction "15_15") (pintype "passive"))
    )
    (net (code "502") (name "unconnected-(SV10-Pad16)") (class "Default")
      (node (ref "SV10") (pin "16") (pinfunction "16_16") (pintype "passive"))
    )
    (net (code "503") (name "unconnected-(SV10-Pad17)") (class "Default")
      (node (ref "SV10") (pin "17") (pinfunction "17_17") (pintype "passive"))
    )
    (net (code "504") (name "unconnected-(SV10-Pad18)") (class "Default")
      (node (ref "SV10") (pin "18") (pinfunction "18_18") (pintype "passive"))
    )
    (net (code "505") (name "unconnected-(SV10-Pad19)") (class "Default")
      (node (ref "SV10") (pin "19") (pinfunction "19_19") (pintype "passive"))
    )
    (net (code "506") (name "unconnected-(SV10-Pad20)") (class "Default")
      (node (ref "SV10") (pin "20") (pinfunction "20_20") (pintype "passive"))
    )
    (net (code "507") (name "unconnected-(SV10-Pad21)") (class "Default")
      (node (ref "SV10") (pin "21") (pinfunction "21_21") (pintype "passive"))
    )
    (net (code "508") (name "unconnected-(SV10-Pad22)") (class "Default")
      (node (ref "SV10") (pin "22") (pinfunction "22_22") (pintype "passive"))
    )
    (net (code "509") (name "unconnected-(SV10-Pad23)") (class "Default")
      (node (ref "SV10") (pin "23") (pinfunction "23_23") (pintype "passive"))
    )
    (net (code "510") (name "unconnected-(SV10-Pad24)") (class "Default")
      (node (ref "SV10") (pin "24") (pinfunction "24_24") (pintype "passive"))
    )
    (net (code "511") (name "unconnected-(SV10-Pad25)") (class "Default")
      (node (ref "SV10") (pin "25") (pinfunction "25_25") (pintype "passive"))
    )
    (net (code "512") (name "unconnected-(SV10-Pad26)") (class "Default")
      (node (ref "SV10") (pin "26") (pinfunction "26_26") (pintype "passive"))
    )
    (net (code "513") (name "unconnected-(SV10-Pad27)") (class "Default")
      (node (ref "SV10") (pin "27") (pinfunction "27_27") (pintype "passive"))
    )
    (net (code "514") (name "unconnected-(SV10-Pad28)") (class "Default")
      (node (ref "SV10") (pin "28") (pinfunction "28_28") (pintype "passive"))
    )
    (net (code "515") (name "unconnected-(SV10-Pad29)") (class "Default")
      (node (ref "SV10") (pin "29") (pinfunction "29_29") (pintype "passive"))
    )
    (net (code "516") (name "unconnected-(SV10-Pad30)") (class "Default")
      (node (ref "SV10") (pin "30") (pinfunction "30_30") (pintype "passive"))
    )
    (net (code "517") (name "unconnected-(SV10-Pad31)") (class "Default")
      (node (ref "SV10") (pin "31") (pinfunction "31_31") (pintype "passive"))
    )
    (net (code "518") (name "unconnected-(SV10-Pad32)") (class "Default")
      (node (ref "SV10") (pin "32") (pinfunction "32_32") (pintype "passive"))
    )
    (net (code "519") (name "unconnected-(SV10-Pad33)") (class "Default")
      (node (ref "SV10") (pin "33") (pinfunction "33_33") (pintype "passive"))
    )
    (net (code "520") (name "unconnected-(SV10-Pad34)") (class "Default")
      (node (ref "SV10") (pin "34") (pinfunction "34_34") (pintype "passive"))
    )
    (net (code "521") (name "unconnected-(SV10-Pad35)") (class "Default")
      (node (ref "SV10") (pin "35") (pinfunction "35_35") (pintype "passive"))
    )
    (net (code "522") (name "unconnected-(SV10-Pad36)") (class "Default")
      (node (ref "SV10") (pin "36") (pinfunction "36_36") (pintype "passive"))
    )
    (net (code "523") (name "unconnected-(SV11-Pad1)") (class "Default")
      (node (ref "SV11") (pin "1") (pinfunction "1_1") (pintype "passive"))
    )
    (net (code "524") (name "unconnected-(SV11-Pad2)") (class "Default")
      (node (ref "SV11") (pin "2") (pinfunction "2_2") (pintype "passive"))
    )
    (net (code "525") (name "unconnected-(SV11-Pad3)") (class "Default")
      (node (ref "SV11") (pin "3") (pinfunction "3_3") (pintype "passive"))
    )
    (net (code "526") (name "unconnected-(SV11-Pad4)") (class "Default")
      (node (ref "SV11") (pin "4") (pinfunction "4_4") (pintype "passive"))
    )
    (net (code "527") (name "unconnected-(SV11-Pad5)") (class "Default")
      (node (ref "SV11") (pin "5") (pinfunction "5_5") (pintype "passive"))
    )
    (net (code "528") (name "unconnected-(SV11-Pad6)") (class "Default")
      (node (ref "SV11") (pin "6") (pinfunction "6_6") (pintype "passive"))
    )
    (net (code "529") (name "unconnected-(SV11-Pad7)") (class "Default")
      (node (ref "SV11") (pin "7") (pinfunction "7_7") (pintype "passive"))
    )
    (net (code "530") (name "unconnected-(SV11-Pad8)") (class "Default")
      (node (ref "SV11") (pin "8") (pinfunction "8_8") (pintype "passive"))
    )
    (net (code "531") (name "unconnected-(SV11-Pad9)") (class "Default")
      (node (ref "SV11") (pin "9") (pinfunction "9_9") (pintype "passive"))
    )
    (net (code "532") (name "unconnected-(SV11-Pad10)") (class "Default")
      (node (ref "SV11") (pin "10") (pinfunction "10_10") (pintype "passive"))
    )
    (net (code "533") (name "unconnected-(SV11-Pad11)") (class "Default")
      (node (ref "SV11") (pin "11") (pinfunction "11_11") (pintype "passive"))
    )
    (net (code "534") (name "unconnected-(SV11-Pad12)") (class "Default")
      (node (ref "SV11") (pin "12") (pinfunction "12_12") (pintype "passive"))
    )
    (net (code "535") (name "unconnected-(SV11-Pad13)") (class "Default")
      (node (ref "SV11") (pin "13") (pinfunction "13_13") (pintype "passive"))
    )
    (net (code "536") (name "unconnected-(SV11-Pad14)") (class "Default")
      (node (ref "SV11") (pin "14") (pinfunction "14_14") (pintype "passive"))
    )
    (net (code "537") (name "unconnected-(SV11-Pad15)") (class "Default")
      (node (ref "SV11") (pin "15") (pinfunction "15_15") (pintype "passive"))
    )
    (net (code "538") (name "unconnected-(SV11-Pad16)") (class "Default")
      (node (ref "SV11") (pin "16") (pinfunction "16_16") (pintype "passive"))
    )
    (net (code "539") (name "unconnected-(SV11-Pad17)") (class "Default")
      (node (ref "SV11") (pin "17") (pinfunction "17_17") (pintype "passive"))
    )
    (net (code "540") (name "unconnected-(SV11-Pad18)") (class "Default")
      (node (ref "SV11") (pin "18") (pinfunction "18_18") (pintype "passive"))
    )
    (net (code "541") (name "unconnected-(SV11-Pad19)") (class "Default")
      (node (ref "SV11") (pin "19") (pinfunction "19_19") (pintype "passive"))
    )
    (net (code "542") (name "unconnected-(SV11-Pad20)") (class "Default")
      (node (ref "SV11") (pin "20") (pinfunction "20_20") (pintype "passive"))
    )
    (net (code "543") (name "unconnected-(SV11-Pad21)") (class "Default")
      (node (ref "SV11") (pin "21") (pinfunction "21_21") (pintype "passive"))
    )
    (net (code "544") (name "unconnected-(SV11-Pad22)") (class "Default")
      (node (ref "SV11") (pin "22") (pinfunction "22_22") (pintype "passive"))
    )
    (net (code "545") (name "unconnected-(SV11-Pad23)") (class "Default")
      (node (ref "SV11") (pin "23") (pinfunction "23_23") (pintype "passive"))
    )
    (net (code "546") (name "unconnected-(SV11-Pad24)") (class "Default")
      (node (ref "SV11") (pin "24") (pinfunction "24_24") (pintype "passive"))
    )
    (net (code "547") (name "unconnected-(SV11-Pad25)") (class "Default")
      (node (ref "SV11") (pin "25") (pinfunction "25_25") (pintype "passive"))
    )
    (net (code "548") (name "unconnected-(SV11-Pad26)") (class "Default")
      (node (ref "SV11") (pin "26") (pinfunction "26_26") (pintype "passive"))
    )
    (net (code "549") (name "unconnected-(SV11-Pad27)") (class "Default")
      (node (ref "SV11") (pin "27") (pinfunction "27_27") (pintype "passive"))
    )
    (net (code "550") (name "unconnected-(SV11-Pad28)") (class "Default")
      (node (ref "SV11") (pin "28") (pinfunction "28_28") (pintype "passive"))
    )
    (net (code "551") (name "unconnected-(SV11-Pad29)") (class "Default")
      (node (ref "SV11") (pin "29") (pinfunction "29_29") (pintype "passive"))
    )
    (net (code "552") (name "unconnected-(SV11-Pad30)") (class "Default")
      (node (ref "SV11") (pin "30") (pinfunction "30_30") (pintype "passive"))
    )
    (net (code "553") (name "unconnected-(SV11-Pad31)") (class "Default")
      (node (ref "SV11") (pin "31") (pinfunction "31_31") (pintype "passive"))
    )
    (net (code "554") (name "unconnected-(SV11-Pad32)") (class "Default")
      (node (ref "SV11") (pin "32") (pinfunction "32_32") (pintype "passive"))
    )
    (net (code "555") (name "unconnected-(SV11-Pad33)") (class "Default")
      (node (ref "SV11") (pin "33") (pinfunction "33_33") (pintype "passive"))
    )
    (net (code "556") (name "unconnected-(SV11-Pad34)") (class "Default")
      (node (ref "SV11") (pin "34") (pinfunction "34_34") (pintype "passive"))
    )
    (net (code "557") (name "unconnected-(SV11-Pad35)") (class "Default")
      (node (ref "SV11") (pin "35") (pinfunction "35_35") (pintype "passive"))
    )
    (net (code "558") (name "unconnected-(SV11-Pad36)") (class "Default")
      (node (ref "SV11") (pin "36") (pinfunction "36_36") (pintype "passive"))
    )
    (net (code "559") (name "unconnected-(SV11-Pad37)") (class "Default")
      (node (ref "SV11") (pin "37") (pinfunction "37_37") (pintype "passive"))
    )
    (net (code "560") (name "unconnected-(SV11-Pad38)") (class "Default")
      (node (ref "SV11") (pin "38") (pinfunction "38_38") (pintype "passive"))
    )
    (net (code "561") (name "unconnected-(SV11-Pad39)") (class "Default")
      (node (ref "SV11") (pin "39") (pinfunction "39_39") (pintype "passive"))
    )
    (net (code "562") (name "unconnected-(SV11-Pad40)") (class "Default")
      (node (ref "SV11") (pin "40") (pinfunction "40_40") (pintype "passive"))
    )
    (net (code "563") (name "unconnected-(SV12-Pad1)") (class "Default")
      (node (ref "SV12") (pin "1") (pinfunction "1_1") (pintype "passive"))
    )
    (net (code "564") (name "unconnected-(SV12-Pad2)") (class "Default")
      (node (ref "SV12") (pin "2") (pinfunction "2_2") (pintype "passive"))
    )
    (net (code "565") (name "unconnected-(SV12-Pad3)") (class "Default")
      (node (ref "SV12") (pin "3") (pinfunction "3_3") (pintype "passive"))
    )
    (net (code "566") (name "unconnected-(SV12-Pad4)") (class "Default")
      (node (ref "SV12") (pin "4") (pinfunction "4_4") (pintype "passive"))
    )
    (net (code "567") (name "unconnected-(SV12-Pad5)") (class "Default")
      (node (ref "SV12") (pin "5") (pinfunction "5_5") (pintype "passive"))
    )
    (net (code "568") (name "unconnected-(SV12-Pad6)") (class "Default")
      (node (ref "SV12") (pin "6") (pinfunction "6_6") (pintype "passive"))
    )
    (net (code "569") (name "unconnected-(SV12-Pad7)") (class "Default")
      (node (ref "SV12") (pin "7") (pinfunction "7_7") (pintype "passive"))
    )
    (net (code "570") (name "unconnected-(SV12-Pad8)") (class "Default")
      (node (ref "SV12") (pin "8") (pinfunction "8_8") (pintype "passive"))
    )
    (net (code "571") (name "unconnected-(SV12-Pad9)") (class "Default")
      (node (ref "SV12") (pin "9") (pinfunction "9_9") (pintype "passive"))
    )
    (net (code "572") (name "unconnected-(SV12-Pad10)") (class "Default")
      (node (ref "SV12") (pin "10") (pinfunction "10_10") (pintype "passive"))
    )
    (net (code "573") (name "unconnected-(SV12-Pad11)") (class "Default")
      (node (ref "SV12") (pin "11") (pinfunction "11_11") (pintype "passive"))
    )
    (net (code "574") (name "unconnected-(SV12-Pad12)") (class "Default")
      (node (ref "SV12") (pin "12") (pinfunction "12_12") (pintype "passive"))
    )
    (net (code "575") (name "unconnected-(SV12-Pad13)") (class "Default")
      (node (ref "SV12") (pin "13") (pinfunction "13_13") (pintype "passive"))
    )
    (net (code "576") (name "unconnected-(SV12-Pad14)") (class "Default")
      (node (ref "SV12") (pin "14") (pinfunction "14_14") (pintype "passive"))
    )
    (net (code "577") (name "unconnected-(SV12-Pad15)") (class "Default")
      (node (ref "SV12") (pin "15") (pinfunction "15_15") (pintype "passive"))
    )
    (net (code "578") (name "unconnected-(SV12-Pad16)") (class "Default")
      (node (ref "SV12") (pin "16") (pinfunction "16_16") (pintype "passive"))
    )
    (net (code "579") (name "unconnected-(SV12-Pad17)") (class "Default")
      (node (ref "SV12") (pin "17") (pinfunction "17_17") (pintype "passive"))
    )
    (net (code "580") (name "unconnected-(SV12-Pad18)") (class "Default")
      (node (ref "SV12") (pin "18") (pinfunction "18_18") (pintype "passive"))
    )
    (net (code "581") (name "unconnected-(SV12-Pad19)") (class "Default")
      (node (ref "SV12") (pin "19") (pinfunction "19_19") (pintype "passive"))
    )
    (net (code "582") (name "unconnected-(SV12-Pad20)") (class "Default")
      (node (ref "SV12") (pin "20") (pinfunction "20_20") (pintype "passive"))
    )
    (net (code "583") (name "unconnected-(SV12-Pad21)") (class "Default")
      (node (ref "SV12") (pin "21") (pinfunction "21_21") (pintype "passive"))
    )
    (net (code "584") (name "unconnected-(SV12-Pad22)") (class "Default")
      (node (ref "SV12") (pin "22") (pinfunction "22_22") (pintype "passive"))
    )
    (net (code "585") (name "unconnected-(SV12-Pad23)") (class "Default")
      (node (ref "SV12") (pin "23") (pinfunction "23_23") (pintype "passive"))
    )
    (net (code "586") (name "unconnected-(SV12-Pad24)") (class "Default")
      (node (ref "SV12") (pin "24") (pinfunction "24_24") (pintype "passive"))
    )
    (net (code "587") (name "unconnected-(SV12-Pad25)") (class "Default")
      (node (ref "SV12") (pin "25") (pinfunction "25_25") (pintype "passive"))
    )
    (net (code "588") (name "unconnected-(SV12-Pad26)") (class "Default")
      (node (ref "SV12") (pin "26") (pinfunction "26_26") (pintype "passive"))
    )
    (net (code "589") (name "unconnected-(SV12-Pad27)") (class "Default")
      (node (ref "SV12") (pin "27") (pinfunction "27_27") (pintype "passive"))
    )
    (net (code "590") (name "unconnected-(SV12-Pad28)") (class "Default")
      (node (ref "SV12") (pin "28") (pinfunction "28_28") (pintype "passive"))
    )
    (net (code "591") (name "unconnected-(SV12-Pad29)") (class "Default")
      (node (ref "SV12") (pin "29") (pinfunction "29_29") (pintype "passive"))
    )
    (net (code "592") (name "unconnected-(SV12-Pad30)") (class "Default")
      (node (ref "SV12") (pin "30") (pinfunction "30_30") (pintype "passive"))
    )
    (net (code "593") (name "unconnected-(SV12-Pad31)") (class "Default")
      (node (ref "SV12") (pin "31") (pinfunction "31_31") (pintype "passive"))
    )
    (net (code "594") (name "unconnected-(SV12-Pad32)") (class "Default")
      (node (ref "SV12") (pin "32") (pinfunction "32_32") (pintype "passive"))
    )
    (net (code "595") (name "unconnected-(SV12-Pad33)") (class "Default")
      (node (ref "SV12") (pin "33") (pinfunction "33_33") (pintype "passive"))
    )
    (net (code "596") (name "unconnected-(SV12-Pad34)") (class "Default")
      (node (ref "SV12") (pin "34") (pinfunction "34_34") (pintype "passive"))
    )
    (net (code "597") (name "unconnected-(SV12-Pad35)") (class "Default")
      (node (ref "SV12") (pin "35") (pinfunction "35_35") (pintype "passive"))
    )
    (net (code "598") (name "unconnected-(SV12-Pad36)") (class "Default")
      (node (ref "SV12") (pin "36") (pinfunction "36_36") (pintype "passive"))
    )
    (net (code "599") (name "unconnected-(SV12-Pad37)") (class "Default")
      (node (ref "SV12") (pin "37") (pinfunction "37_37") (pintype "passive"))
    )
    (net (code "600") (name "unconnected-(SV12-Pad38)") (class "Default")
      (node (ref "SV12") (pin "38") (pinfunction "38_38") (pintype "passive"))
    )
    (net (code "601") (name "unconnected-(SV12-Pad39)") (class "Default")
      (node (ref "SV12") (pin "39") (pinfunction "39_39") (pintype "passive"))
    )
    (net (code "602") (name "unconnected-(SV12-Pad40)") (class "Default")
      (node (ref "SV12") (pin "40") (pinfunction "40_40") (pintype "passive"))
    )
    (net (code "603") (name "unconnected-(SV13-Pad1)") (class "Default")
      (node (ref "SV13") (pin "1") (pinfunction "1_1") (pintype "passive"))
    )
    (net (code "604") (name "unconnected-(SV13-Pad2)") (class "Default")
      (node (ref "SV13") (pin "2") (pinfunction "2_2") (pintype "passive"))
    )
    (net (code "605") (name "unconnected-(SV13-Pad3)") (class "Default")
      (node (ref "SV13") (pin "3") (pinfunction "3_3") (pintype "passive"))
    )
    (net (code "606") (name "unconnected-(SV13-Pad4)") (class "Default")
      (node (ref "SV13") (pin "4") (pinfunction "4_4") (pintype "passive"))
    )
    (net (code "607") (name "unconnected-(SV13-Pad5)") (class "Default")
      (node (ref "SV13") (pin "5") (pinfunction "5_5") (pintype "passive"))
    )
    (net (code "608") (name "unconnected-(SV13-Pad6)") (class "Default")
      (node (ref "SV13") (pin "6") (pinfunction "6_6") (pintype "passive"))
    )
    (net (code "609") (name "unconnected-(SV13-Pad7)") (class "Default")
      (node (ref "SV13") (pin "7") (pinfunction "7_7") (pintype "passive"))
    )
    (net (code "610") (name "unconnected-(SV13-Pad8)") (class "Default")
      (node (ref "SV13") (pin "8") (pinfunction "8_8") (pintype "passive"))
    )
    (net (code "611") (name "unconnected-(SV13-Pad9)") (class "Default")
      (node (ref "SV13") (pin "9") (pinfunction "9_9") (pintype "passive"))
    )
    (net (code "612") (name "unconnected-(SV13-Pad10)") (class "Default")
      (node (ref "SV13") (pin "10") (pinfunction "10_10") (pintype "passive"))
    )
    (net (code "613") (name "unconnected-(SV13-Pad11)") (class "Default")
      (node (ref "SV13") (pin "11") (pinfunction "11_11") (pintype "passive"))
    )
    (net (code "614") (name "unconnected-(SV13-Pad12)") (class "Default")
      (node (ref "SV13") (pin "12") (pinfunction "12_12") (pintype "passive"))
    )
    (net (code "615") (name "unconnected-(SV13-Pad13)") (class "Default")
      (node (ref "SV13") (pin "13") (pinfunction "13_13") (pintype "passive"))
    )
    (net (code "616") (name "unconnected-(SV13-Pad14)") (class "Default")
      (node (ref "SV13") (pin "14") (pinfunction "14_14") (pintype "passive"))
    )
    (net (code "617") (name "unconnected-(SV13-Pad15)") (class "Default")
      (node (ref "SV13") (pin "15") (pinfunction "15_15") (pintype "passive"))
    )
    (net (code "618") (name "unconnected-(SV13-Pad16)") (class "Default")
      (node (ref "SV13") (pin "16") (pinfunction "16_16") (pintype "passive"))
    )
    (net (code "619") (name "unconnected-(SV13-Pad17)") (class "Default")
      (node (ref "SV13") (pin "17") (pinfunction "17_17") (pintype "passive"))
    )
    (net (code "620") (name "unconnected-(SV13-Pad18)") (class "Default")
      (node (ref "SV13") (pin "18") (pinfunction "18_18") (pintype "passive"))
    )
    (net (code "621") (name "unconnected-(SV13-Pad19)") (class "Default")
      (node (ref "SV13") (pin "19") (pinfunction "19_19") (pintype "passive"))
    )
    (net (code "622") (name "unconnected-(SV13-Pad20)") (class "Default")
      (node (ref "SV13") (pin "20") (pinfunction "20_20") (pintype "passive"))
    )
    (net (code "623") (name "unconnected-(SV13-Pad21)") (class "Default")
      (node (ref "SV13") (pin "21") (pinfunction "21_21") (pintype "passive"))
    )
    (net (code "624") (name "unconnected-(SV13-Pad22)") (class "Default")
      (node (ref "SV13") (pin "22") (pinfunction "22_22") (pintype "passive"))
    )
    (net (code "625") (name "unconnected-(SV13-Pad23)") (class "Default")
      (node (ref "SV13") (pin "23") (pinfunction "23_23") (pintype "passive"))
    )
    (net (code "626") (name "unconnected-(SV13-Pad24)") (class "Default")
      (node (ref "SV13") (pin "24") (pinfunction "24_24") (pintype "passive"))
    )
    (net (code "627") (name "unconnected-(SV13-Pad25)") (class "Default")
      (node (ref "SV13") (pin "25") (pinfunction "25_25") (pintype "passive"))
    )
    (net (code "628") (name "unconnected-(SV13-Pad26)") (class "Default")
      (node (ref "SV13") (pin "26") (pinfunction "26_26") (pintype "passive"))
    )
    (net (code "629") (name "unconnected-(SV13-Pad27)") (class "Default")
      (node (ref "SV13") (pin "27") (pinfunction "27_27") (pintype "passive"))
    )
    (net (code "630") (name "unconnected-(SV13-Pad28)") (class "Default")
      (node (ref "SV13") (pin "28") (pinfunction "28_28") (pintype "passive"))
    )
    (net (code "631") (name "unconnected-(SV13-Pad29)") (class "Default")
      (node (ref "SV13") (pin "29") (pinfunction "29_29") (pintype "passive"))
    )
    (net (code "632") (name "unconnected-(SV13-Pad30)") (class "Default")
      (node (ref "SV13") (pin "30") (pinfunction "30_30") (pintype "passive"))
    )
    (net (code "633") (name "unconnected-(SV13-Pad31)") (class "Default")
      (node (ref "SV13") (pin "31") (pinfunction "31_31") (pintype "passive"))
    )
    (net (code "634") (name "unconnected-(SV13-Pad32)") (class "Default")
      (node (ref "SV13") (pin "32") (pinfunction "32_32") (pintype "passive"))
    )
    (net (code "635") (name "unconnected-(SV13-Pad33)") (class "Default")
      (node (ref "SV13") (pin "33") (pinfunction "33_33") (pintype "passive"))
    )
    (net (code "636") (name "unconnected-(SV13-Pad34)") (class "Default")
      (node (ref "SV13") (pin "34") (pinfunction "34_34") (pintype "passive"))
    )
    (net (code "637") (name "unconnected-(SV13-Pad35)") (class "Default")
      (node (ref "SV13") (pin "35") (pinfunction "35_35") (pintype "passive"))
    )
    (net (code "638") (name "unconnected-(SV13-Pad36)") (class "Default")
      (node (ref "SV13") (pin "36") (pinfunction "36_36") (pintype "passive"))
    )
    (net (code "639") (name "unconnected-(SV13-Pad37)") (class "Default")
      (node (ref "SV13") (pin "37") (pinfunction "37_37") (pintype "passive"))
    )
    (net (code "640") (name "unconnected-(SV13-Pad38)") (class "Default")
      (node (ref "SV13") (pin "38") (pinfunction "38_38") (pintype "passive"))
    )
    (net (code "641") (name "unconnected-(SV13-Pad39)") (class "Default")
      (node (ref "SV13") (pin "39") (pinfunction "39_39") (pintype "passive"))
    )
    (net (code "642") (name "unconnected-(SV13-Pad40)") (class "Default")
      (node (ref "SV13") (pin "40") (pinfunction "40_40") (pintype "passive"))
    )
    (net (code "643") (name "unconnected-(SV14-Pad1)") (class "Default")
      (node (ref "SV14") (pin "1") (pinfunction "1_1") (pintype "passive"))
    )
    (net (code "644") (name "unconnected-(SV14-Pad2)") (class "Default")
      (node (ref "SV14") (pin "2") (pinfunction "2_2") (pintype "passive"))
    )
    (net (code "645") (name "unconnected-(SV14-Pad3)") (class "Default")
      (node (ref "SV14") (pin "3") (pinfunction "3_3") (pintype "passive"))
    )
    (net (code "646") (name "unconnected-(SV14-Pad4)") (class "Default")
      (node (ref "SV14") (pin "4") (pinfunction "4_4") (pintype "passive"))
    )
    (net (code "647") (name "unconnected-(SV14-Pad5)") (class "Default")
      (node (ref "SV14") (pin "5") (pinfunction "5_5") (pintype "passive"))
    )
    (net (code "648") (name "unconnected-(SV14-Pad6)") (class "Default")
      (node (ref "SV14") (pin "6") (pinfunction "6_6") (pintype "passive"))
    )
    (net (code "649") (name "unconnected-(SV14-Pad7)") (class "Default")
      (node (ref "SV14") (pin "7") (pinfunction "7_7") (pintype "passive"))
    )
    (net (code "650") (name "unconnected-(SV14-Pad8)") (class "Default")
      (node (ref "SV14") (pin "8") (pinfunction "8_8") (pintype "passive"))
    )
    (net (code "651") (name "unconnected-(SV14-Pad9)") (class "Default")
      (node (ref "SV14") (pin "9") (pinfunction "9_9") (pintype "passive"))
    )
    (net (code "652") (name "unconnected-(SV14-Pad10)") (class "Default")
      (node (ref "SV14") (pin "10") (pinfunction "10_10") (pintype "passive"))
    )
    (net (code "653") (name "unconnected-(SV14-Pad11)") (class "Default")
      (node (ref "SV14") (pin "11") (pinfunction "11_11") (pintype "passive"))
    )
    (net (code "654") (name "unconnected-(SV14-Pad12)") (class "Default")
      (node (ref "SV14") (pin "12") (pinfunction "12_12") (pintype "passive"))
    )
    (net (code "655") (name "unconnected-(SV14-Pad13)") (class "Default")
      (node (ref "SV14") (pin "13") (pinfunction "13_13") (pintype "passive"))
    )
    (net (code "656") (name "unconnected-(SV14-Pad14)") (class "Default")
      (node (ref "SV14") (pin "14") (pinfunction "14_14") (pintype "passive"))
    )
    (net (code "657") (name "unconnected-(SV14-Pad15)") (class "Default")
      (node (ref "SV14") (pin "15") (pinfunction "15_15") (pintype "passive"))
    )
    (net (code "658") (name "unconnected-(SV14-Pad16)") (class "Default")
      (node (ref "SV14") (pin "16") (pinfunction "16_16") (pintype "passive"))
    )
    (net (code "659") (name "unconnected-(SV14-Pad17)") (class "Default")
      (node (ref "SV14") (pin "17") (pinfunction "17_17") (pintype "passive"))
    )
    (net (code "660") (name "unconnected-(SV14-Pad18)") (class "Default")
      (node (ref "SV14") (pin "18") (pinfunction "18_18") (pintype "passive"))
    )
    (net (code "661") (name "unconnected-(SV14-Pad19)") (class "Default")
      (node (ref "SV14") (pin "19") (pinfunction "19_19") (pintype "passive"))
    )
    (net (code "662") (name "unconnected-(SV14-Pad20)") (class "Default")
      (node (ref "SV14") (pin "20") (pinfunction "20_20") (pintype "passive"))
    )
    (net (code "663") (name "unconnected-(SV14-Pad21)") (class "Default")
      (node (ref "SV14") (pin "21") (pinfunction "21_21") (pintype "passive"))
    )
    (net (code "664") (name "unconnected-(SV14-Pad22)") (class "Default")
      (node (ref "SV14") (pin "22") (pinfunction "22_22") (pintype "passive"))
    )
    (net (code "665") (name "unconnected-(SV14-Pad23)") (class "Default")
      (node (ref "SV14") (pin "23") (pinfunction "23_23") (pintype "passive"))
    )
    (net (code "666") (name "unconnected-(SV14-Pad24)") (class "Default")
      (node (ref "SV14") (pin "24") (pinfunction "24_24") (pintype "passive"))
    )
    (net (code "667") (name "unconnected-(SV14-Pad25)") (class "Default")
      (node (ref "SV14") (pin "25") (pinfunction "25_25") (pintype "passive"))
    )
    (net (code "668") (name "unconnected-(SV14-Pad26)") (class "Default")
      (node (ref "SV14") (pin "26") (pinfunction "26_26") (pintype "passive"))
    )
    (net (code "669") (name "unconnected-(SV14-Pad27)") (class "Default")
      (node (ref "SV14") (pin "27") (pinfunction "27_27") (pintype "passive"))
    )
    (net (code "670") (name "unconnected-(SV14-Pad28)") (class "Default")
      (node (ref "SV14") (pin "28") (pinfunction "28_28") (pintype "passive"))
    )
    (net (code "671") (name "unconnected-(SV14-Pad29)") (class "Default")
      (node (ref "SV14") (pin "29") (pinfunction "29_29") (pintype "passive"))
    )
    (net (code "672") (name "unconnected-(SV14-Pad30)") (class "Default")
      (node (ref "SV14") (pin "30") (pinfunction "30_30") (pintype "passive"))
    )
    (net (code "673") (name "unconnected-(SV14-Pad31)") (class "Default")
      (node (ref "SV14") (pin "31") (pinfunction "31_31") (pintype "passive"))
    )
    (net (code "674") (name "unconnected-(SV14-Pad32)") (class "Default")
      (node (ref "SV14") (pin "32") (pinfunction "32_32") (pintype "passive"))
    )
    (net (code "675") (name "unconnected-(SV14-Pad33)") (class "Default")
      (node (ref "SV14") (pin "33") (pinfunction "33_33") (pintype "passive"))
    )
    (net (code "676") (name "unconnected-(SV14-Pad34)") (class "Default")
      (node (ref "SV14") (pin "34") (pinfunction "34_34") (pintype "passive"))
    )
    (net (code "677") (name "unconnected-(SV14-Pad35)") (class "Default")
      (node (ref "SV14") (pin "35") (pinfunction "35_35") (pintype "passive"))
    )
    (net (code "678") (name "unconnected-(SV14-Pad36)") (class "Default")
      (node (ref "SV14") (pin "36") (pinfunction "36_36") (pintype "passive"))
    )
    (net (code "679") (name "unconnected-(SV14-Pad37)") (class "Default")
      (node (ref "SV14") (pin "37") (pinfunction "37_37") (pintype "passive"))
    )
    (net (code "680") (name "unconnected-(SV14-Pad38)") (class "Default")
      (node (ref "SV14") (pin "38") (pinfunction "38_38") (pintype "passive"))
    )
    (net (code "681") (name "unconnected-(SV14-Pad39)") (class "Default")
      (node (ref "SV14") (pin "39") (pinfunction "39_39") (pintype "passive"))
    )
    (net (code "682") (name "unconnected-(SV14-Pad40)") (class "Default")
      (node (ref "SV14") (pin "40") (pinfunction "40_40") (pintype "passive"))
    )
    (net (code "683") (name "unconnected-(SV15-Pad1)") (class "Default")
      (node (ref "SV15") (pin "1") (pinfunction "1_1") (pintype "passive"))
    )
    (net (code "684") (name "unconnected-(SV15-Pad2)") (class "Default")
      (node (ref "SV15") (pin "2") (pinfunction "2_2") (pintype "passive"))
    )
    (net (code "685") (name "unconnected-(SV15-Pad3)") (class "Default")
      (node (ref "SV15") (pin "3") (pinfunction "3_3") (pintype "passive"))
    )
    (net (code "686") (name "unconnected-(SV15-Pad4)") (class "Default")
      (node (ref "SV15") (pin "4") (pinfunction "4_4") (pintype "passive"))
    )
    (net (code "687") (name "unconnected-(SV15-Pad5)") (class "Default")
      (node (ref "SV15") (pin "5") (pinfunction "5_5") (pintype "passive"))
    )
    (net (code "688") (name "unconnected-(SV15-Pad6)") (class "Default")
      (node (ref "SV15") (pin "6") (pinfunction "6_6") (pintype "passive"))
    )
    (net (code "689") (name "unconnected-(SV15-Pad7)") (class "Default")
      (node (ref "SV15") (pin "7") (pinfunction "7_7") (pintype "passive"))
    )
    (net (code "690") (name "unconnected-(SV15-Pad8)") (class "Default")
      (node (ref "SV15") (pin "8") (pinfunction "8_8") (pintype "passive"))
    )
    (net (code "691") (name "unconnected-(SV15-Pad9)") (class "Default")
      (node (ref "SV15") (pin "9") (pinfunction "9_9") (pintype "passive"))
    )
    (net (code "692") (name "unconnected-(SV15-Pad10)") (class "Default")
      (node (ref "SV15") (pin "10") (pinfunction "10_10") (pintype "passive"))
    )
    (net (code "693") (name "unconnected-(SV15-Pad11)") (class "Default")
      (node (ref "SV15") (pin "11") (pinfunction "11_11") (pintype "passive"))
    )
    (net (code "694") (name "unconnected-(SV15-Pad12)") (class "Default")
      (node (ref "SV15") (pin "12") (pinfunction "12_12") (pintype "passive"))
    )
    (net (code "695") (name "unconnected-(SV15-Pad13)") (class "Default")
      (node (ref "SV15") (pin "13") (pinfunction "13_13") (pintype "passive"))
    )
    (net (code "696") (name "unconnected-(SV15-Pad14)") (class "Default")
      (node (ref "SV15") (pin "14") (pinfunction "14_14") (pintype "passive"))
    )
    (net (code "697") (name "unconnected-(SV15-Pad15)") (class "Default")
      (node (ref "SV15") (pin "15") (pinfunction "15_15") (pintype "passive"))
    )
    (net (code "698") (name "unconnected-(SV15-Pad16)") (class "Default")
      (node (ref "SV15") (pin "16") (pinfunction "16_16") (pintype "passive"))
    )
    (net (code "699") (name "unconnected-(SV15-Pad17)") (class "Default")
      (node (ref "SV15") (pin "17") (pinfunction "17_17") (pintype "passive"))
    )
    (net (code "700") (name "unconnected-(SV15-Pad18)") (class "Default")
      (node (ref "SV15") (pin "18") (pinfunction "18_18") (pintype "passive"))
    )
    (net (code "701") (name "unconnected-(SV15-Pad19)") (class "Default")
      (node (ref "SV15") (pin "19") (pinfunction "19_19") (pintype "passive"))
    )
    (net (code "702") (name "unconnected-(SV15-Pad20)") (class "Default")
      (node (ref "SV15") (pin "20") (pinfunction "20_20") (pintype "passive"))
    )
    (net (code "703") (name "unconnected-(SV15-Pad21)") (class "Default")
      (node (ref "SV15") (pin "21") (pinfunction "21_21") (pintype "passive"))
    )
    (net (code "704") (name "unconnected-(SV15-Pad22)") (class "Default")
      (node (ref "SV15") (pin "22") (pinfunction "22_22") (pintype "passive"))
    )
    (net (code "705") (name "unconnected-(SV15-Pad23)") (class "Default")
      (node (ref "SV15") (pin "23") (pinfunction "23_23") (pintype "passive"))
    )
    (net (code "706") (name "unconnected-(SV15-Pad24)") (class "Default")
      (node (ref "SV15") (pin "24") (pinfunction "24_24") (pintype "passive"))
    )
    (net (code "707") (name "unconnected-(SV15-Pad25)") (class "Default")
      (node (ref "SV15") (pin "25") (pinfunction "25_25") (pintype "passive"))
    )
    (net (code "708") (name "unconnected-(SV15-Pad26)") (class "Default")
      (node (ref "SV15") (pin "26") (pinfunction "26_26") (pintype "passive"))
    )
    (net (code "709") (name "unconnected-(SV15-Pad27)") (class "Default")
      (node (ref "SV15") (pin "27") (pinfunction "27_27") (pintype "passive"))
    )
    (net (code "710") (name "unconnected-(SV15-Pad28)") (class "Default")
      (node (ref "SV15") (pin "28") (pinfunction "28_28") (pintype "passive"))
    )
    (net (code "711") (name "unconnected-(SV15-Pad29)") (class "Default")
      (node (ref "SV15") (pin "29") (pinfunction "29_29") (pintype "passive"))
    )
    (net (code "712") (name "unconnected-(SV15-Pad30)") (class "Default")
      (node (ref "SV15") (pin "30") (pinfunction "30_30") (pintype "passive"))
    )
    (net (code "713") (name "unconnected-(SV15-Pad31)") (class "Default")
      (node (ref "SV15") (pin "31") (pinfunction "31_31") (pintype "passive"))
    )
    (net (code "714") (name "unconnected-(SV15-Pad32)") (class "Default")
      (node (ref "SV15") (pin "32") (pinfunction "32_32") (pintype "passive"))
    )
    (net (code "715") (name "unconnected-(SV15-Pad33)") (class "Default")
      (node (ref "SV15") (pin "33") (pinfunction "33_33") (pintype "passive"))
    )
    (net (code "716") (name "unconnected-(SV15-Pad34)") (class "Default")
      (node (ref "SV15") (pin "34") (pinfunction "34_34") (pintype "passive"))
    )
    (net (code "717") (name "unconnected-(SV15-Pad35)") (class "Default")
      (node (ref "SV15") (pin "35") (pinfunction "35_35") (pintype "passive"))
    )
    (net (code "718") (name "unconnected-(SV15-Pad36)") (class "Default")
      (node (ref "SV15") (pin "36") (pinfunction "36_36") (pintype "passive"))
    )
    (net (code "719") (name "unconnected-(SV16-Pad1)") (class "Default")
      (node (ref "SV16") (pin "1") (pinfunction "1_1") (pintype "passive"))
    )
    (net (code "720") (name "unconnected-(SV16-Pad2)") (class "Default")
      (node (ref "SV16") (pin "2") (pinfunction "2_2") (pintype "passive"))
    )
    (net (code "721") (name "unconnected-(SV16-Pad3)") (class "Default")
      (node (ref "SV16") (pin "3") (pinfunction "3_3") (pintype "passive"))
    )
    (net (code "722") (name "unconnected-(SV16-Pad4)") (class "Default")
      (node (ref "SV16") (pin "4") (pinfunction "4_4") (pintype "passive"))
    )
    (net (code "723") (name "unconnected-(SV16-Pad5)") (class "Default")
      (node (ref "SV16") (pin "5") (pinfunction "5_5") (pintype "passive"))
    )
    (net (code "724") (name "unconnected-(SV16-Pad6)") (class "Default")
      (node (ref "SV16") (pin "6") (pinfunction "6_6") (pintype "passive"))
    )
    (net (code "725") (name "unconnected-(SV16-Pad7)") (class "Default")
      (node (ref "SV16") (pin "7") (pinfunction "7_7") (pintype "passive"))
    )
    (net (code "726") (name "unconnected-(SV16-Pad8)") (class "Default")
      (node (ref "SV16") (pin "8") (pinfunction "8_8") (pintype "passive"))
    )
    (net (code "727") (name "unconnected-(SV16-Pad9)") (class "Default")
      (node (ref "SV16") (pin "9") (pinfunction "9_9") (pintype "passive"))
    )
    (net (code "728") (name "unconnected-(SV16-Pad10)") (class "Default")
      (node (ref "SV16") (pin "10") (pinfunction "10_10") (pintype "passive"))
    )
    (net (code "729") (name "unconnected-(SV16-Pad11)") (class "Default")
      (node (ref "SV16") (pin "11") (pinfunction "11_11") (pintype "passive"))
    )
    (net (code "730") (name "unconnected-(SV16-Pad12)") (class "Default")
      (node (ref "SV16") (pin "12") (pinfunction "12_12") (pintype "passive"))
    )
    (net (code "731") (name "unconnected-(SV16-Pad13)") (class "Default")
      (node (ref "SV16") (pin "13") (pinfunction "13_13") (pintype "passive"))
    )
    (net (code "732") (name "unconnected-(SV16-Pad14)") (class "Default")
      (node (ref "SV16") (pin "14") (pinfunction "14_14") (pintype "passive"))
    )
    (net (code "733") (name "unconnected-(SV16-Pad15)") (class "Default")
      (node (ref "SV16") (pin "15") (pinfunction "15_15") (pintype "passive"))
    )
    (net (code "734") (name "unconnected-(SV16-Pad16)") (class "Default")
      (node (ref "SV16") (pin "16") (pinfunction "16_16") (pintype "passive"))
    )
    (net (code "735") (name "unconnected-(SV16-Pad17)") (class "Default")
      (node (ref "SV16") (pin "17") (pinfunction "17_17") (pintype "passive"))
    )
    (net (code "736") (name "unconnected-(SV16-Pad18)") (class "Default")
      (node (ref "SV16") (pin "18") (pinfunction "18_18") (pintype "passive"))
    )
    (net (code "737") (name "unconnected-(SV16-Pad19)") (class "Default")
      (node (ref "SV16") (pin "19") (pinfunction "19_19") (pintype "passive"))
    )
    (net (code "738") (name "unconnected-(SV16-Pad20)") (class "Default")
      (node (ref "SV16") (pin "20") (pinfunction "20_20") (pintype "passive"))
    )
    (net (code "739") (name "unconnected-(SV16-Pad21)") (class "Default")
      (node (ref "SV16") (pin "21") (pinfunction "21_21") (pintype "passive"))
    )
    (net (code "740") (name "unconnected-(SV16-Pad22)") (class "Default")
      (node (ref "SV16") (pin "22") (pinfunction "22_22") (pintype "passive"))
    )
    (net (code "741") (name "unconnected-(SV16-Pad23)") (class "Default")
      (node (ref "SV16") (pin "23") (pinfunction "23_23") (pintype "passive"))
    )
    (net (code "742") (name "unconnected-(SV16-Pad24)") (class "Default")
      (node (ref "SV16") (pin "24") (pinfunction "24_24") (pintype "passive"))
    )
    (net (code "743") (name "unconnected-(SV16-Pad25)") (class "Default")
      (node (ref "SV16") (pin "25") (pinfunction "25_25") (pintype "passive"))
    )
    (net (code "744") (name "unconnected-(SV16-Pad26)") (class "Default")
      (node (ref "SV16") (pin "26") (pinfunction "26_26") (pintype "passive"))
    )
    (net (code "745") (name "unconnected-(SV16-Pad27)") (class "Default")
      (node (ref "SV16") (pin "27") (pinfunction "27_27") (pintype "passive"))
    )
    (net (code "746") (name "unconnected-(SV16-Pad28)") (class "Default")
      (node (ref "SV16") (pin "28") (pinfunction "28_28") (pintype "passive"))
    )
    (net (code "747") (name "unconnected-(SV16-Pad29)") (class "Default")
      (node (ref "SV16") (pin "29") (pinfunction "29_29") (pintype "passive"))
    )
    (net (code "748") (name "unconnected-(SV16-Pad30)") (class "Default")
      (node (ref "SV16") (pin "30") (pinfunction "30_30") (pintype "passive"))
    )
    (net (code "749") (name "unconnected-(SV16-Pad31)") (class "Default")
      (node (ref "SV16") (pin "31") (pinfunction "31_31") (pintype "passive"))
    )
    (net (code "750") (name "unconnected-(SV16-Pad32)") (class "Default")
      (node (ref "SV16") (pin "32") (pinfunction "32_32") (pintype "passive"))
    )
    (net (code "751") (name "unconnected-(SV16-Pad33)") (class "Default")
      (node (ref "SV16") (pin "33") (pinfunction "33_33") (pintype "passive"))
    )
    (net (code "752") (name "unconnected-(SV16-Pad34)") (class "Default")
      (node (ref "SV16") (pin "34") (pinfunction "34_34") (pintype "passive"))
    )
    (net (code "753") (name "unconnected-(SV16-Pad35)") (class "Default")
      (node (ref "SV16") (pin "35") (pinfunction "35_35") (pintype "passive"))
    )
    (net (code "754") (name "unconnected-(SV16-Pad36)") (class "Default")
      (node (ref "SV16") (pin "36") (pinfunction "36_36") (pintype "passive"))
    )
    (net (code "755") (name "unconnected-(SV17-Pad1)") (class "Default")
      (node (ref "SV17") (pin "1") (pinfunction "1_1") (pintype "passive"))
    )
    (net (code "756") (name "unconnected-(SV17-Pad2)") (class "Default")
      (node (ref "SV17") (pin "2") (pinfunction "2_2") (pintype "passive"))
    )
    (net (code "757") (name "unconnected-(SV17-Pad3)") (class "Default")
      (node (ref "SV17") (pin "3") (pinfunction "3_3") (pintype "passive"))
    )
    (net (code "758") (name "unconnected-(SV17-Pad4)") (class "Default")
      (node (ref "SV17") (pin "4") (pinfunction "4_4") (pintype "passive"))
    )
    (net (code "759") (name "unconnected-(SV17-Pad5)") (class "Default")
      (node (ref "SV17") (pin "5") (pinfunction "5_5") (pintype "passive"))
    )
    (net (code "760") (name "unconnected-(SV17-Pad6)") (class "Default")
      (node (ref "SV17") (pin "6") (pinfunction "6_6") (pintype "passive"))
    )
    (net (code "761") (name "unconnected-(SV17-Pad7)") (class "Default")
      (node (ref "SV17") (pin "7") (pinfunction "7_7") (pintype "passive"))
    )
    (net (code "762") (name "unconnected-(SV17-Pad8)") (class "Default")
      (node (ref "SV17") (pin "8") (pinfunction "8_8") (pintype "passive"))
    )
    (net (code "763") (name "unconnected-(SV17-Pad9)") (class "Default")
      (node (ref "SV17") (pin "9") (pinfunction "9_9") (pintype "passive"))
    )
    (net (code "764") (name "unconnected-(SV17-Pad10)") (class "Default")
      (node (ref "SV17") (pin "10") (pinfunction "10_10") (pintype "passive"))
    )
    (net (code "765") (name "unconnected-(SV17-Pad11)") (class "Default")
      (node (ref "SV17") (pin "11") (pinfunction "11_11") (pintype "passive"))
    )
    (net (code "766") (name "unconnected-(SV17-Pad12)") (class "Default")
      (node (ref "SV17") (pin "12") (pinfunction "12_12") (pintype "passive"))
    )
    (net (code "767") (name "unconnected-(SV17-Pad13)") (class "Default")
      (node (ref "SV17") (pin "13") (pinfunction "13_13") (pintype "passive"))
    )
    (net (code "768") (name "unconnected-(SV17-Pad14)") (class "Default")
      (node (ref "SV17") (pin "14") (pinfunction "14_14") (pintype "passive"))
    )
    (net (code "769") (name "unconnected-(SV17-Pad15)") (class "Default")
      (node (ref "SV17") (pin "15") (pinfunction "15_15") (pintype "passive"))
    )
    (net (code "770") (name "unconnected-(SV17-Pad16)") (class "Default")
      (node (ref "SV17") (pin "16") (pinfunction "16_16") (pintype "passive"))
    )
    (net (code "771") (name "unconnected-(SV17-Pad17)") (class "Default")
      (node (ref "SV17") (pin "17") (pinfunction "17_17") (pintype "passive"))
    )
    (net (code "772") (name "unconnected-(SV17-Pad18)") (class "Default")
      (node (ref "SV17") (pin "18") (pinfunction "18_18") (pintype "passive"))
    )
    (net (code "773") (name "unconnected-(SV17-Pad19)") (class "Default")
      (node (ref "SV17") (pin "19") (pinfunction "19_19") (pintype "passive"))
    )
    (net (code "774") (name "unconnected-(SV17-Pad20)") (class "Default")
      (node (ref "SV17") (pin "20") (pinfunction "20_20") (pintype "passive"))
    )
    (net (code "775") (name "unconnected-(SV17-Pad21)") (class "Default")
      (node (ref "SV17") (pin "21") (pinfunction "21_21") (pintype "passive"))
    )
    (net (code "776") (name "unconnected-(SV17-Pad22)") (class "Default")
      (node (ref "SV17") (pin "22") (pinfunction "22_22") (pintype "passive"))
    )
    (net (code "777") (name "unconnected-(SV17-Pad23)") (class "Default")
      (node (ref "SV17") (pin "23") (pinfunction "23_23") (pintype "passive"))
    )
    (net (code "778") (name "unconnected-(SV17-Pad24)") (class "Default")
      (node (ref "SV17") (pin "24") (pinfunction "24_24") (pintype "passive"))
    )
    (net (code "779") (name "unconnected-(SV17-Pad25)") (class "Default")
      (node (ref "SV17") (pin "25") (pinfunction "25_25") (pintype "passive"))
    )
    (net (code "780") (name "unconnected-(SV17-Pad26)") (class "Default")
      (node (ref "SV17") (pin "26") (pinfunction "26_26") (pintype "passive"))
    )
    (net (code "781") (name "unconnected-(SV17-Pad27)") (class "Default")
      (node (ref "SV17") (pin "27") (pinfunction "27_27") (pintype "passive"))
    )
    (net (code "782") (name "unconnected-(SV17-Pad28)") (class "Default")
      (node (ref "SV17") (pin "28") (pinfunction "28_28") (pintype "passive"))
    )
    (net (code "783") (name "unconnected-(SV17-Pad29)") (class "Default")
      (node (ref "SV17") (pin "29") (pinfunction "29_29") (pintype "passive"))
    )
    (net (code "784") (name "unconnected-(SV17-Pad30)") (class "Default")
      (node (ref "SV17") (pin "30") (pinfunction "30_30") (pintype "passive"))
    )
    (net (code "785") (name "unconnected-(SV17-Pad31)") (class "Default")
      (node (ref "SV17") (pin "31") (pinfunction "31_31") (pintype "passive"))
    )
    (net (code "786") (name "unconnected-(SV17-Pad32)") (class "Default")
      (node (ref "SV17") (pin "32") (pinfunction "32_32") (pintype "passive"))
    )
    (net (code "787") (name "unconnected-(SV17-Pad33)") (class "Default")
      (node (ref "SV17") (pin "33") (pinfunction "33_33") (pintype "passive"))
    )
    (net (code "788") (name "unconnected-(SV17-Pad34)") (class "Default")
      (node (ref "SV17") (pin "34") (pinfunction "34_34") (pintype "passive"))
    )
    (net (code "789") (name "unconnected-(SV17-Pad35)") (class "Default")
      (node (ref "SV17") (pin "35") (pinfunction "35_35") (pintype "passive"))
    )
    (net (code "790") (name "unconnected-(SV17-Pad36)") (class "Default")
      (node (ref "SV17") (pin "36") (pinfunction "36_36") (pintype "passive"))
    )
    (net (code "791") (name "unconnected-(SV18-Pad1)") (class "Default")
      (node (ref "SV18") (pin "1") (pinfunction "1_1") (pintype "passive"))
    )
    (net (code "792") (name "unconnected-(SV18-Pad2)") (class "Default")
      (node (ref "SV18") (pin "2") (pinfunction "2_2") (pintype "passive"))
    )
    (net (code "793") (name "unconnected-(SV18-Pad3)") (class "Default")
      (node (ref "SV18") (pin "3") (pinfunction "3_3") (pintype "passive"))
    )
    (net (code "794") (name "unconnected-(SV18-Pad4)") (class "Default")
      (node (ref "SV18") (pin "4") (pinfunction "4_4") (pintype "passive"))
    )
    (net (code "795") (name "unconnected-(SV18-Pad5)") (class "Default")
      (node (ref "SV18") (pin "5") (pinfunction "5_5") (pintype "passive"))
    )
    (net (code "796") (name "unconnected-(SV18-Pad6)") (class "Default")
      (node (ref "SV18") (pin "6") (pinfunction "6_6") (pintype "passive"))
    )
    (net (code "797") (name "unconnected-(SV18-Pad7)") (class "Default")
      (node (ref "SV18") (pin "7") (pinfunction "7_7") (pintype "passive"))
    )
    (net (code "798") (name "unconnected-(SV18-Pad8)") (class "Default")
      (node (ref "SV18") (pin "8") (pinfunction "8_8") (pintype "passive"))
    )
    (net (code "799") (name "unconnected-(SV18-Pad9)") (class "Default")
      (node (ref "SV18") (pin "9") (pinfunction "9_9") (pintype "passive"))
    )
    (net (code "800") (name "unconnected-(SV18-Pad10)") (class "Default")
      (node (ref "SV18") (pin "10") (pinfunction "10_10") (pintype "passive"))
    )
    (net (code "801") (name "unconnected-(SV18-Pad11)") (class "Default")
      (node (ref "SV18") (pin "11") (pinfunction "11_11") (pintype "passive"))
    )
    (net (code "802") (name "unconnected-(SV18-Pad12)") (class "Default")
      (node (ref "SV18") (pin "12") (pinfunction "12_12") (pintype "passive"))
    )
    (net (code "803") (name "unconnected-(SV18-Pad13)") (class "Default")
      (node (ref "SV18") (pin "13") (pinfunction "13_13") (pintype "passive"))
    )
    (net (code "804") (name "unconnected-(SV18-Pad14)") (class "Default")
      (node (ref "SV18") (pin "14") (pinfunction "14_14") (pintype "passive"))
    )
    (net (code "805") (name "unconnected-(SV18-Pad15)") (class "Default")
      (node (ref "SV18") (pin "15") (pinfunction "15_15") (pintype "passive"))
    )
    (net (code "806") (name "unconnected-(SV18-Pad16)") (class "Default")
      (node (ref "SV18") (pin "16") (pinfunction "16_16") (pintype "passive"))
    )
    (net (code "807") (name "unconnected-(SV18-Pad17)") (class "Default")
      (node (ref "SV18") (pin "17") (pinfunction "17_17") (pintype "passive"))
    )
    (net (code "808") (name "unconnected-(SV18-Pad18)") (class "Default")
      (node (ref "SV18") (pin "18") (pinfunction "18_18") (pintype "passive"))
    )
    (net (code "809") (name "unconnected-(SV18-Pad19)") (class "Default")
      (node (ref "SV18") (pin "19") (pinfunction "19_19") (pintype "passive"))
    )
    (net (code "810") (name "unconnected-(SV18-Pad20)") (class "Default")
      (node (ref "SV18") (pin "20") (pinfunction "20_20") (pintype "passive"))
    )
    (net (code "811") (name "unconnected-(SV18-Pad21)") (class "Default")
      (node (ref "SV18") (pin "21") (pinfunction "21_21") (pintype "passive"))
    )
    (net (code "812") (name "unconnected-(SV18-Pad22)") (class "Default")
      (node (ref "SV18") (pin "22") (pinfunction "22_22") (pintype "passive"))
    )
    (net (code "813") (name "unconnected-(SV18-Pad23)") (class "Default")
      (node (ref "SV18") (pin "23") (pinfunction "23_23") (pintype "passive"))
    )
    (net (code "814") (name "unconnected-(SV18-Pad24)") (class "Default")
      (node (ref "SV18") (pin "24") (pinfunction "24_24") (pintype "passive"))
    )
    (net (code "815") (name "unconnected-(SV18-Pad25)") (class "Default")
      (node (ref "SV18") (pin "25") (pinfunction "25_25") (pintype "passive"))
    )
    (net (code "816") (name "unconnected-(SV18-Pad26)") (class "Default")
      (node (ref "SV18") (pin "26") (pinfunction "26_26") (pintype "passive"))
    )
    (net (code "817") (name "unconnected-(SV18-Pad27)") (class "Default")
      (node (ref "SV18") (pin "27") (pinfunction "27_27") (pintype "passive"))
    )
    (net (code "818") (name "unconnected-(SV18-Pad28)") (class "Default")
      (node (ref "SV18") (pin "28") (pinfunction "28_28") (pintype "passive"))
    )
    (net (code "819") (name "unconnected-(SV18-Pad29)") (class "Default")
      (node (ref "SV18") (pin "29") (pinfunction "29_29") (pintype "passive"))
    )
    (net (code "820") (name "unconnected-(SV18-Pad30)") (class "Default")
      (node (ref "SV18") (pin "30") (pinfunction "30_30") (pintype "passive"))
    )
    (net (code "821") (name "unconnected-(SV18-Pad31)") (class "Default")
      (node (ref "SV18") (pin "31") (pinfunction "31_31") (pintype "passive"))
    )
    (net (code "822") (name "unconnected-(SV18-Pad32)") (class "Default")
      (node (ref "SV18") (pin "32") (pinfunction "32_32") (pintype "passive"))
    )
    (net (code "823") (name "unconnected-(SV18-Pad33)") (class "Default")
      (node (ref "SV18") (pin "33") (pinfunction "33_33") (pintype "passive"))
    )
    (net (code "824") (name "unconnected-(SV18-Pad34)") (class "Default")
      (node (ref "SV18") (pin "34") (pinfunction "34_34") (pintype "passive"))
    )
    (net (code "825") (name "unconnected-(SV18-Pad35)") (class "Default")
      (node (ref "SV18") (pin "35") (pinfunction "35_35") (pintype "passive"))
    )
    (net (code "826") (name "unconnected-(SV18-Pad36)") (class "Default")
      (node (ref "SV18") (pin "36") (pinfunction "36_36") (pintype "passive"))
    )
    (net (code "827") (name "unconnected-(SV19-Pad1)") (class "Default")
      (node (ref "SV19") (pin "1") (pinfunction "1_1") (pintype "passive"))
    )
    (net (code "828") (name "unconnected-(SV19-Pad2)") (class "Default")
      (node (ref "SV19") (pin "2") (pinfunction "2_2") (pintype "passive"))
    )
    (net (code "829") (name "unconnected-(SV19-Pad3)") (class "Default")
      (node (ref "SV19") (pin "3") (pinfunction "3_3") (pintype "passive"))
    )
    (net (code "830") (name "unconnected-(SV19-Pad4)") (class "Default")
      (node (ref "SV19") (pin "4") (pinfunction "4_4") (pintype "passive"))
    )
    (net (code "831") (name "unconnected-(SV19-Pad5)") (class "Default")
      (node (ref "SV19") (pin "5") (pinfunction "5_5") (pintype "passive"))
    )
    (net (code "832") (name "unconnected-(SV19-Pad6)") (class "Default")
      (node (ref "SV19") (pin "6") (pinfunction "6_6") (pintype "passive"))
    )
    (net (code "833") (name "unconnected-(SV19-Pad7)") (class "Default")
      (node (ref "SV19") (pin "7") (pinfunction "7_7") (pintype "passive"))
    )
    (net (code "834") (name "unconnected-(SV19-Pad8)") (class "Default")
      (node (ref "SV19") (pin "8") (pinfunction "8_8") (pintype "passive"))
    )
    (net (code "835") (name "unconnected-(SV19-Pad9)") (class "Default")
      (node (ref "SV19") (pin "9") (pinfunction "9_9") (pintype "passive"))
    )
    (net (code "836") (name "unconnected-(SV19-Pad10)") (class "Default")
      (node (ref "SV19") (pin "10") (pinfunction "10_10") (pintype "passive"))
    )
    (net (code "837") (name "unconnected-(SV19-Pad11)") (class "Default")
      (node (ref "SV19") (pin "11") (pinfunction "11_11") (pintype "passive"))
    )
    (net (code "838") (name "unconnected-(SV19-Pad12)") (class "Default")
      (node (ref "SV19") (pin "12") (pinfunction "12_12") (pintype "passive"))
    )
    (net (code "839") (name "unconnected-(SV19-Pad13)") (class "Default")
      (node (ref "SV19") (pin "13") (pinfunction "13_13") (pintype "passive"))
    )
    (net (code "840") (name "unconnected-(SV19-Pad14)") (class "Default")
      (node (ref "SV19") (pin "14") (pinfunction "14_14") (pintype "passive"))
    )
    (net (code "841") (name "unconnected-(SV19-Pad15)") (class "Default")
      (node (ref "SV19") (pin "15") (pinfunction "15_15") (pintype "passive"))
    )
    (net (code "842") (name "unconnected-(SV19-Pad16)") (class "Default")
      (node (ref "SV19") (pin "16") (pinfunction "16_16") (pintype "passive"))
    )
    (net (code "843") (name "unconnected-(SV19-Pad17)") (class "Default")
      (node (ref "SV19") (pin "17") (pinfunction "17_17") (pintype "passive"))
    )
    (net (code "844") (name "unconnected-(SV19-Pad18)") (class "Default")
      (node (ref "SV19") (pin "18") (pinfunction "18_18") (pintype "passive"))
    )
    (net (code "845") (name "unconnected-(SV19-Pad19)") (class "Default")
      (node (ref "SV19") (pin "19") (pinfunction "19_19") (pintype "passive"))
    )
    (net (code "846") (name "unconnected-(SV19-Pad20)") (class "Default")
      (node (ref "SV19") (pin "20") (pinfunction "20_20") (pintype "passive"))
    )
    (net (code "847") (name "unconnected-(SV19-Pad21)") (class "Default")
      (node (ref "SV19") (pin "21") (pinfunction "21_21") (pintype "passive"))
    )
    (net (code "848") (name "unconnected-(SV19-Pad22)") (class "Default")
      (node (ref "SV19") (pin "22") (pinfunction "22_22") (pintype "passive"))
    )
    (net (code "849") (name "unconnected-(SV19-Pad23)") (class "Default")
      (node (ref "SV19") (pin "23") (pinfunction "23_23") (pintype "passive"))
    )
    (net (code "850") (name "unconnected-(SV19-Pad24)") (class "Default")
      (node (ref "SV19") (pin "24") (pinfunction "24_24") (pintype "passive"))
    )
    (net (code "851") (name "unconnected-(SV19-Pad25)") (class "Default")
      (node (ref "SV19") (pin "25") (pinfunction "25_25") (pintype "passive"))
    )
    (net (code "852") (name "unconnected-(SV19-Pad26)") (class "Default")
      (node (ref "SV19") (pin "26") (pinfunction "26_26") (pintype "passive"))
    )
    (net (code "853") (name "unconnected-(SV19-Pad27)") (class "Default")
      (node (ref "SV19") (pin "27") (pinfunction "27_27") (pintype "passive"))
    )
    (net (code "854") (name "unconnected-(SV19-Pad28)") (class "Default")
      (node (ref "SV19") (pin "28") (pinfunction "28_28") (pintype "passive"))
    )
    (net (code "855") (name "unconnected-(SV19-Pad29)") (class "Default")
      (node (ref "SV19") (pin "29") (pinfunction "29_29") (pintype "passive"))
    )
    (net (code "856") (name "unconnected-(SV19-Pad30)") (class "Default")
      (node (ref "SV19") (pin "30") (pinfunction "30_30") (pintype "passive"))
    )
    (net (code "857") (name "unconnected-(SV19-Pad31)") (class "Default")
      (node (ref "SV19") (pin "31") (pinfunction "31_31") (pintype "passive"))
    )
    (net (code "858") (name "unconnected-(SV19-Pad32)") (class "Default")
      (node (ref "SV19") (pin "32") (pinfunction "32_32") (pintype "passive"))
    )
    (net (code "859") (name "unconnected-(SV19-Pad33)") (class "Default")
      (node (ref "SV19") (pin "33") (pinfunction "33_33") (pintype "passive"))
    )
    (net (code "860") (name "unconnected-(SV19-Pad34)") (class "Default")
      (node (ref "SV19") (pin "34") (pinfunction "34_34") (pintype "passive"))
    )
    (net (code "861") (name "unconnected-(SV19-Pad35)") (class "Default")
      (node (ref "SV19") (pin "35") (pinfunction "35_35") (pintype "passive"))
    )
    (net (code "862") (name "unconnected-(SV19-Pad36)") (class "Default")
      (node (ref "SV19") (pin "36") (pinfunction "36_36") (pintype "passive"))
    )
    (net (code "863") (name "unconnected-(SV19-Pad37)") (class "Default")
      (node (ref "SV19") (pin "37") (pinfunction "37_37") (pintype "passive"))
    )
    (net (code "864") (name "unconnected-(SV19-Pad38)") (class "Default")
      (node (ref "SV19") (pin "38") (pinfunction "38_38") (pintype "passive"))
    )
    (net (code "865") (name "unconnected-(SV19-Pad39)") (class "Default")
      (node (ref "SV19") (pin "39") (pinfunction "39_39") (pintype "passive"))
    )
    (net (code "866") (name "unconnected-(SV19-Pad40)") (class "Default")
      (node (ref "SV19") (pin "40") (pinfunction "40_40") (pintype "passive"))
    )
    (net (code "867") (name "unconnected-(SV20-Pad1)") (class "Default")
      (node (ref "SV20") (pin "1") (pinfunction "1_1") (pintype "passive"))
    )
    (net (code "868") (name "unconnected-(SV20-Pad2)") (class "Default")
      (node (ref "SV20") (pin "2") (pinfunction "2_2") (pintype "passive"))
    )
    (net (code "869") (name "unconnected-(SV20-Pad3)") (class "Default")
      (node (ref "SV20") (pin "3") (pinfunction "3_3") (pintype "passive"))
    )
    (net (code "870") (name "unconnected-(SV20-Pad4)") (class "Default")
      (node (ref "SV20") (pin "4") (pinfunction "4_4") (pintype "passive"))
    )
    (net (code "871") (name "unconnected-(SV20-Pad5)") (class "Default")
      (node (ref "SV20") (pin "5") (pinfunction "5_5") (pintype "passive"))
    )
    (net (code "872") (name "unconnected-(SV20-Pad6)") (class "Default")
      (node (ref "SV20") (pin "6") (pinfunction "6_6") (pintype "passive"))
    )
    (net (code "873") (name "unconnected-(SV20-Pad7)") (class "Default")
      (node (ref "SV20") (pin "7") (pinfunction "7_7") (pintype "passive"))
    )
    (net (code "874") (name "unconnected-(SV20-Pad8)") (class "Default")
      (node (ref "SV20") (pin "8") (pinfunction "8_8") (pintype "passive"))
    )
    (net (code "875") (name "unconnected-(SV20-Pad9)") (class "Default")
      (node (ref "SV20") (pin "9") (pinfunction "9_9") (pintype "passive"))
    )
    (net (code "876") (name "unconnected-(SV20-Pad10)") (class "Default")
      (node (ref "SV20") (pin "10") (pinfunction "10_10") (pintype "passive"))
    )
    (net (code "877") (name "unconnected-(SV20-Pad11)") (class "Default")
      (node (ref "SV20") (pin "11") (pinfunction "11_11") (pintype "passive"))
    )
    (net (code "878") (name "unconnected-(SV20-Pad12)") (class "Default")
      (node (ref "SV20") (pin "12") (pinfunction "12_12") (pintype "passive"))
    )
    (net (code "879") (name "unconnected-(SV20-Pad13)") (class "Default")
      (node (ref "SV20") (pin "13") (pinfunction "13_13") (pintype "passive"))
    )
    (net (code "880") (name "unconnected-(SV20-Pad14)") (class "Default")
      (node (ref "SV20") (pin "14") (pinfunction "14_14") (pintype "passive"))
    )
    (net (code "881") (name "unconnected-(SV20-Pad15)") (class "Default")
      (node (ref "SV20") (pin "15") (pinfunction "15_15") (pintype "passive"))
    )
    (net (code "882") (name "unconnected-(SV20-Pad16)") (class "Default")
      (node (ref "SV20") (pin "16") (pinfunction "16_16") (pintype "passive"))
    )
    (net (code "883") (name "unconnected-(SV20-Pad17)") (class "Default")
      (node (ref "SV20") (pin "17") (pinfunction "17_17") (pintype "passive"))
    )
    (net (code "884") (name "unconnected-(SV20-Pad18)") (class "Default")
      (node (ref "SV20") (pin "18") (pinfunction "18_18") (pintype "passive"))
    )
    (net (code "885") (name "unconnected-(SV20-Pad19)") (class "Default")
      (node (ref "SV20") (pin "19") (pinfunction "19_19") (pintype "passive"))
    )
    (net (code "886") (name "unconnected-(SV20-Pad20)") (class "Default")
      (node (ref "SV20") (pin "20") (pinfunction "20_20") (pintype "passive"))
    )
    (net (code "887") (name "unconnected-(SV20-Pad21)") (class "Default")
      (node (ref "SV20") (pin "21") (pinfunction "21_21") (pintype "passive"))
    )
    (net (code "888") (name "unconnected-(SV20-Pad22)") (class "Default")
      (node (ref "SV20") (pin "22") (pinfunction "22_22") (pintype "passive"))
    )
    (net (code "889") (name "unconnected-(SV20-Pad23)") (class "Default")
      (node (ref "SV20") (pin "23") (pinfunction "23_23") (pintype "passive"))
    )
    (net (code "890") (name "unconnected-(SV20-Pad24)") (class "Default")
      (node (ref "SV20") (pin "24") (pinfunction "24_24") (pintype "passive"))
    )
    (net (code "891") (name "unconnected-(SV20-Pad25)") (class "Default")
      (node (ref "SV20") (pin "25") (pinfunction "25_25") (pintype "passive"))
    )
    (net (code "892") (name "unconnected-(SV20-Pad26)") (class "Default")
      (node (ref "SV20") (pin "26") (pinfunction "26_26") (pintype "passive"))
    )
    (net (code "893") (name "unconnected-(SV20-Pad27)") (class "Default")
      (node (ref "SV20") (pin "27") (pinfunction "27_27") (pintype "passive"))
    )
    (net (code "894") (name "unconnected-(SV20-Pad28)") (class "Default")
      (node (ref "SV20") (pin "28") (pinfunction "28_28") (pintype "passive"))
    )
    (net (code "895") (name "unconnected-(SV20-Pad29)") (class "Default")
      (node (ref "SV20") (pin "29") (pinfunction "29_29") (pintype "passive"))
    )
    (net (code "896") (name "unconnected-(SV20-Pad30)") (class "Default")
      (node (ref "SV20") (pin "30") (pinfunction "30_30") (pintype "passive"))
    )
    (net (code "897") (name "unconnected-(SV20-Pad31)") (class "Default")
      (node (ref "SV20") (pin "31") (pinfunction "31_31") (pintype "passive"))
    )
    (net (code "898") (name "unconnected-(SV20-Pad32)") (class "Default")
      (node (ref "SV20") (pin "32") (pinfunction "32_32") (pintype "passive"))
    )
    (net (code "899") (name "unconnected-(SV20-Pad33)") (class "Default")
      (node (ref "SV20") (pin "33") (pinfunction "33_33") (pintype "passive"))
    )
    (net (code "900") (name "unconnected-(SV20-Pad34)") (class "Default")
      (node (ref "SV20") (pin "34") (pinfunction "34_34") (pintype "passive"))
    )
    (net (code "901") (name "unconnected-(SV20-Pad35)") (class "Default")
      (node (ref "SV20") (pin "35") (pinfunction "35_35") (pintype "passive"))
    )
    (net (code "902") (name "unconnected-(SV20-Pad36)") (class "Default")
      (node (ref "SV20") (pin "36") (pinfunction "36_36") (pintype "passive"))
    )
    (net (code "903") (name "unconnected-(SV20-Pad37)") (class "Default")
      (node (ref "SV20") (pin "37") (pinfunction "37_37") (pintype "passive"))
    )
    (net (code "904") (name "unconnected-(SV20-Pad38)") (class "Default")
      (node (ref "SV20") (pin "38") (pinfunction "38_38") (pintype "passive"))
    )
    (net (code "905") (name "unconnected-(SV20-Pad39)") (class "Default")
      (node (ref "SV20") (pin "39") (pinfunction "39_39") (pintype "passive"))
    )
    (net (code "906") (name "unconnected-(SV20-Pad40)") (class "Default")
      (node (ref "SV20") (pin "40") (pinfunction "40_40") (pintype "passive"))
    )
    (net (code "907") (name "unconnected-(SV21-Pad1)") (class "Default")
      (node (ref "SV21") (pin "1") (pinfunction "1_1") (pintype "passive"))
    )
    (net (code "908") (name "unconnected-(SV21-Pad2)") (class "Default")
      (node (ref "SV21") (pin "2") (pinfunction "2_2") (pintype "passive"))
    )
    (net (code "909") (name "unconnected-(SV21-Pad3)") (class "Default")
      (node (ref "SV21") (pin "3") (pinfunction "3_3") (pintype "passive"))
    )
    (net (code "910") (name "unconnected-(SV21-Pad4)") (class "Default")
      (node (ref "SV21") (pin "4") (pinfunction "4_4") (pintype "passive"))
    )
    (net (code "911") (name "unconnected-(SV21-Pad5)") (class "Default")
      (node (ref "SV21") (pin "5") (pinfunction "5_5") (pintype "passive"))
    )
    (net (code "912") (name "unconnected-(SV21-Pad6)") (class "Default")
      (node (ref "SV21") (pin "6") (pinfunction "6_6") (pintype "passive"))
    )
    (net (code "913") (name "unconnected-(SV21-Pad7)") (class "Default")
      (node (ref "SV21") (pin "7") (pinfunction "7_7") (pintype "passive"))
    )
    (net (code "914") (name "unconnected-(SV21-Pad8)") (class "Default")
      (node (ref "SV21") (pin "8") (pinfunction "8_8") (pintype "passive"))
    )
    (net (code "915") (name "unconnected-(SV21-Pad9)") (class "Default")
      (node (ref "SV21") (pin "9") (pinfunction "9_9") (pintype "passive"))
    )
    (net (code "916") (name "unconnected-(SV21-Pad10)") (class "Default")
      (node (ref "SV21") (pin "10") (pinfunction "10_10") (pintype "passive"))
    )
    (net (code "917") (name "unconnected-(SV21-Pad11)") (class "Default")
      (node (ref "SV21") (pin "11") (pinfunction "11_11") (pintype "passive"))
    )
    (net (code "918") (name "unconnected-(SV21-Pad12)") (class "Default")
      (node (ref "SV21") (pin "12") (pinfunction "12_12") (pintype "passive"))
    )
    (net (code "919") (name "unconnected-(SV21-Pad13)") (class "Default")
      (node (ref "SV21") (pin "13") (pinfunction "13_13") (pintype "passive"))
    )
    (net (code "920") (name "unconnected-(SV21-Pad14)") (class "Default")
      (node (ref "SV21") (pin "14") (pinfunction "14_14") (pintype "passive"))
    )
    (net (code "921") (name "unconnected-(SV21-Pad15)") (class "Default")
      (node (ref "SV21") (pin "15") (pinfunction "15_15") (pintype "passive"))
    )
    (net (code "922") (name "unconnected-(SV21-Pad16)") (class "Default")
      (node (ref "SV21") (pin "16") (pinfunction "16_16") (pintype "passive"))
    )
    (net (code "923") (name "unconnected-(SV21-Pad17)") (class "Default")
      (node (ref "SV21") (pin "17") (pinfunction "17_17") (pintype "passive"))
    )
    (net (code "924") (name "unconnected-(SV21-Pad18)") (class "Default")
      (node (ref "SV21") (pin "18") (pinfunction "18_18") (pintype "passive"))
    )
    (net (code "925") (name "unconnected-(SV21-Pad19)") (class "Default")
      (node (ref "SV21") (pin "19") (pinfunction "19_19") (pintype "passive"))
    )
    (net (code "926") (name "unconnected-(SV21-Pad20)") (class "Default")
      (node (ref "SV21") (pin "20") (pinfunction "20_20") (pintype "passive"))
    )
    (net (code "927") (name "unconnected-(SV21-Pad21)") (class "Default")
      (node (ref "SV21") (pin "21") (pinfunction "21_21") (pintype "passive"))
    )
    (net (code "928") (name "unconnected-(SV21-Pad22)") (class "Default")
      (node (ref "SV21") (pin "22") (pinfunction "22_22") (pintype "passive"))
    )
    (net (code "929") (name "unconnected-(SV21-Pad23)") (class "Default")
      (node (ref "SV21") (pin "23") (pinfunction "23_23") (pintype "passive"))
    )
    (net (code "930") (name "unconnected-(SV21-Pad24)") (class "Default")
      (node (ref "SV21") (pin "24") (pinfunction "24_24") (pintype "passive"))
    )
    (net (code "931") (name "unconnected-(SV21-Pad25)") (class "Default")
      (node (ref "SV21") (pin "25") (pinfunction "25_25") (pintype "passive"))
    )
    (net (code "932") (name "unconnected-(SV21-Pad26)") (class "Default")
      (node (ref "SV21") (pin "26") (pinfunction "26_26") (pintype "passive"))
    )
    (net (code "933") (name "unconnected-(SV21-Pad27)") (class "Default")
      (node (ref "SV21") (pin "27") (pinfunction "27_27") (pintype "passive"))
    )
    (net (code "934") (name "unconnected-(SV21-Pad28)") (class "Default")
      (node (ref "SV21") (pin "28") (pinfunction "28_28") (pintype "passive"))
    )
    (net (code "935") (name "unconnected-(SV21-Pad29)") (class "Default")
      (node (ref "SV21") (pin "29") (pinfunction "29_29") (pintype "passive"))
    )
    (net (code "936") (name "unconnected-(SV21-Pad30)") (class "Default")
      (node (ref "SV21") (pin "30") (pinfunction "30_30") (pintype "passive"))
    )
    (net (code "937") (name "unconnected-(SV21-Pad31)") (class "Default")
      (node (ref "SV21") (pin "31") (pinfunction "31_31") (pintype "passive"))
    )
    (net (code "938") (name "unconnected-(SV21-Pad32)") (class "Default")
      (node (ref "SV21") (pin "32") (pinfunction "32_32") (pintype "passive"))
    )
    (net (code "939") (name "unconnected-(SV21-Pad33)") (class "Default")
      (node (ref "SV21") (pin "33") (pinfunction "33_33") (pintype "passive"))
    )
    (net (code "940") (name "unconnected-(SV21-Pad34)") (class "Default")
      (node (ref "SV21") (pin "34") (pinfunction "34_34") (pintype "passive"))
    )
    (net (code "941") (name "unconnected-(SV21-Pad35)") (class "Default")
      (node (ref "SV21") (pin "35") (pinfunction "35_35") (pintype "passive"))
    )
    (net (code "942") (name "unconnected-(SV21-Pad36)") (class "Default")
      (node (ref "SV21") (pin "36") (pinfunction "36_36") (pintype "passive"))
    )
    (net (code "943") (name "unconnected-(SV21-Pad37)") (class "Default")
      (node (ref "SV21") (pin "37") (pinfunction "37_37") (pintype "passive"))
    )
    (net (code "944") (name "unconnected-(SV21-Pad38)") (class "Default")
      (node (ref "SV21") (pin "38") (pinfunction "38_38") (pintype "passive"))
    )
    (net (code "945") (name "unconnected-(SV21-Pad39)") (class "Default")
      (node (ref "SV21") (pin "39") (pinfunction "39_39") (pintype "passive"))
    )
    (net (code "946") (name "unconnected-(SV21-Pad40)") (class "Default")
      (node (ref "SV21") (pin "40") (pinfunction "40_40") (pintype "passive"))
    )
    (net (code "947") (name "unconnected-(SV22-Pad1)") (class "Default")
      (node (ref "SV22") (pin "1") (pinfunction "1_1") (pintype "passive"))
    )
    (net (code "948") (name "unconnected-(SV22-Pad2)") (class "Default")
      (node (ref "SV22") (pin "2") (pinfunction "2_2") (pintype "passive"))
    )
    (net (code "949") (name "unconnected-(SV22-Pad3)") (class "Default")
      (node (ref "SV22") (pin "3") (pinfunction "3_3") (pintype "passive"))
    )
    (net (code "950") (name "unconnected-(SV22-Pad4)") (class "Default")
      (node (ref "SV22") (pin "4") (pinfunction "4_4") (pintype "passive"))
    )
    (net (code "951") (name "unconnected-(SV22-Pad5)") (class "Default")
      (node (ref "SV22") (pin "5") (pinfunction "5_5") (pintype "passive"))
    )
    (net (code "952") (name "unconnected-(SV22-Pad6)") (class "Default")
      (node (ref "SV22") (pin "6") (pinfunction "6_6") (pintype "passive"))
    )
    (net (code "953") (name "unconnected-(SV22-Pad7)") (class "Default")
      (node (ref "SV22") (pin "7") (pinfunction "7_7") (pintype "passive"))
    )
    (net (code "954") (name "unconnected-(SV22-Pad8)") (class "Default")
      (node (ref "SV22") (pin "8") (pinfunction "8_8") (pintype "passive"))
    )
    (net (code "955") (name "unconnected-(SV22-Pad9)") (class "Default")
      (node (ref "SV22") (pin "9") (pinfunction "9_9") (pintype "passive"))
    )
    (net (code "956") (name "unconnected-(SV22-Pad10)") (class "Default")
      (node (ref "SV22") (pin "10") (pinfunction "10_10") (pintype "passive"))
    )
    (net (code "957") (name "unconnected-(SV22-Pad11)") (class "Default")
      (node (ref "SV22") (pin "11") (pinfunction "11_11") (pintype "passive"))
    )
    (net (code "958") (name "unconnected-(SV22-Pad12)") (class "Default")
      (node (ref "SV22") (pin "12") (pinfunction "12_12") (pintype "passive"))
    )
    (net (code "959") (name "unconnected-(SV22-Pad13)") (class "Default")
      (node (ref "SV22") (pin "13") (pinfunction "13_13") (pintype "passive"))
    )
    (net (code "960") (name "unconnected-(SV22-Pad14)") (class "Default")
      (node (ref "SV22") (pin "14") (pinfunction "14_14") (pintype "passive"))
    )
    (net (code "961") (name "unconnected-(SV22-Pad15)") (class "Default")
      (node (ref "SV22") (pin "15") (pinfunction "15_15") (pintype "passive"))
    )
    (net (code "962") (name "unconnected-(SV22-Pad16)") (class "Default")
      (node (ref "SV22") (pin "16") (pinfunction "16_16") (pintype "passive"))
    )
    (net (code "963") (name "unconnected-(SV22-Pad17)") (class "Default")
      (node (ref "SV22") (pin "17") (pinfunction "17_17") (pintype "passive"))
    )
    (net (code "964") (name "unconnected-(SV22-Pad18)") (class "Default")
      (node (ref "SV22") (pin "18") (pinfunction "18_18") (pintype "passive"))
    )
    (net (code "965") (name "unconnected-(SV22-Pad19)") (class "Default")
      (node (ref "SV22") (pin "19") (pinfunction "19_19") (pintype "passive"))
    )
    (net (code "966") (name "unconnected-(SV22-Pad20)") (class "Default")
      (node (ref "SV22") (pin "20") (pinfunction "20_20") (pintype "passive"))
    )
    (net (code "967") (name "unconnected-(SV22-Pad21)") (class "Default")
      (node (ref "SV22") (pin "21") (pinfunction "21_21") (pintype "passive"))
    )
    (net (code "968") (name "unconnected-(SV22-Pad22)") (class "Default")
      (node (ref "SV22") (pin "22") (pinfunction "22_22") (pintype "passive"))
    )
    (net (code "969") (name "unconnected-(SV22-Pad23)") (class "Default")
      (node (ref "SV22") (pin "23") (pinfunction "23_23") (pintype "passive"))
    )
    (net (code "970") (name "unconnected-(SV22-Pad24)") (class "Default")
      (node (ref "SV22") (pin "24") (pinfunction "24_24") (pintype "passive"))
    )
    (net (code "971") (name "unconnected-(SV22-Pad25)") (class "Default")
      (node (ref "SV22") (pin "25") (pinfunction "25_25") (pintype "passive"))
    )
    (net (code "972") (name "unconnected-(SV22-Pad26)") (class "Default")
      (node (ref "SV22") (pin "26") (pinfunction "26_26") (pintype "passive"))
    )
    (net (code "973") (name "unconnected-(SV22-Pad27)") (class "Default")
      (node (ref "SV22") (pin "27") (pinfunction "27_27") (pintype "passive"))
    )
    (net (code "974") (name "unconnected-(SV22-Pad28)") (class "Default")
      (node (ref "SV22") (pin "28") (pinfunction "28_28") (pintype "passive"))
    )
    (net (code "975") (name "unconnected-(SV22-Pad29)") (class "Default")
      (node (ref "SV22") (pin "29") (pinfunction "29_29") (pintype "passive"))
    )
    (net (code "976") (name "unconnected-(SV22-Pad30)") (class "Default")
      (node (ref "SV22") (pin "30") (pinfunction "30_30") (pintype "passive"))
    )
    (net (code "977") (name "unconnected-(SV22-Pad31)") (class "Default")
      (node (ref "SV22") (pin "31") (pinfunction "31_31") (pintype "passive"))
    )
    (net (code "978") (name "unconnected-(SV22-Pad32)") (class "Default")
      (node (ref "SV22") (pin "32") (pinfunction "32_32") (pintype "passive"))
    )
    (net (code "979") (name "unconnected-(SV22-Pad33)") (class "Default")
      (node (ref "SV22") (pin "33") (pinfunction "33_33") (pintype "passive"))
    )
    (net (code "980") (name "unconnected-(SV22-Pad34)") (class "Default")
      (node (ref "SV22") (pin "34") (pinfunction "34_34") (pintype "passive"))
    )
    (net (code "981") (name "unconnected-(SV22-Pad35)") (class "Default")
      (node (ref "SV22") (pin "35") (pinfunction "35_35") (pintype "passive"))
    )
    (net (code "982") (name "unconnected-(SV22-Pad36)") (class "Default")
      (node (ref "SV22") (pin "36") (pinfunction "36_36") (pintype "passive"))
    )
    (net (code "983") (name "unconnected-(SV22-Pad37)") (class "Default")
      (node (ref "SV22") (pin "37") (pinfunction "37_37") (pintype "passive"))
    )
    (net (code "984") (name "unconnected-(SV22-Pad38)") (class "Default")
      (node (ref "SV22") (pin "38") (pinfunction "38_38") (pintype "passive"))
    )
    (net (code "985") (name "unconnected-(SV22-Pad39)") (class "Default")
      (node (ref "SV22") (pin "39") (pinfunction "39_39") (pintype "passive"))
    )
    (net (code "986") (name "unconnected-(SV22-Pad40)") (class "Default")
      (node (ref "SV22") (pin "40") (pinfunction "40_40") (pintype "passive"))
    )
    (net (code "987") (name "unconnected-(SV23-Pad1)") (class "Default")
      (node (ref "SV23") (pin "1") (pinfunction "1_1") (pintype "passive"))
    )
    (net (code "988") (name "unconnected-(SV23-Pad2)") (class "Default")
      (node (ref "SV23") (pin "2") (pinfunction "2_2") (pintype "passive"))
    )
    (net (code "989") (name "unconnected-(SV23-Pad3)") (class "Default")
      (node (ref "SV23") (pin "3") (pinfunction "3_3") (pintype "passive"))
    )
    (net (code "990") (name "unconnected-(SV23-Pad4)") (class "Default")
      (node (ref "SV23") (pin "4") (pinfunction "4_4") (pintype "passive"))
    )
    (net (code "991") (name "unconnected-(SV23-Pad5)") (class "Default")
      (node (ref "SV23") (pin "5") (pinfunction "5_5") (pintype "passive"))
    )
    (net (code "992") (name "unconnected-(SV23-Pad6)") (class "Default")
      (node (ref "SV23") (pin "6") (pinfunction "6_6") (pintype "passive"))
    )
    (net (code "993") (name "unconnected-(SV23-Pad7)") (class "Default")
      (node (ref "SV23") (pin "7") (pinfunction "7_7") (pintype "passive"))
    )
    (net (code "994") (name "unconnected-(SV23-Pad8)") (class "Default")
      (node (ref "SV23") (pin "8") (pinfunction "8_8") (pintype "passive"))
    )
    (net (code "995") (name "unconnected-(SV23-Pad9)") (class "Default")
      (node (ref "SV23") (pin "9") (pinfunction "9_9") (pintype "passive"))
    )
    (net (code "996") (name "unconnected-(SV23-Pad10)") (class "Default")
      (node (ref "SV23") (pin "10") (pinfunction "10_10") (pintype "passive"))
    )
    (net (code "997") (name "unconnected-(SV23-Pad11)") (class "Default")
      (node (ref "SV23") (pin "11") (pinfunction "11_11") (pintype "passive"))
    )
    (net (code "998") (name "unconnected-(SV23-Pad12)") (class "Default")
      (node (ref "SV23") (pin "12") (pinfunction "12_12") (pintype "passive"))
    )
    (net (code "999") (name "unconnected-(SV23-Pad13)") (class "Default")
      (node (ref "SV23") (pin "13") (pinfunction "13_13") (pintype "passive"))
    )
    (net (code "1000") (name "unconnected-(SV23-Pad14)") (class "Default")
      (node (ref "SV23") (pin "14") (pinfunction "14_14") (pintype "passive"))
    )
    (net (code "1001") (name "unconnected-(SV23-Pad15)") (class "Default")
      (node (ref "SV23") (pin "15") (pinfunction "15_15") (pintype "passive"))
    )
    (net (code "1002") (name "unconnected-(SV23-Pad16)") (class "Default")
      (node (ref "SV23") (pin "16") (pinfunction "16_16") (pintype "passive"))
    )
    (net (code "1003") (name "unconnected-(SV23-Pad17)") (class "Default")
      (node (ref "SV23") (pin "17") (pinfunction "17_17") (pintype "passive"))
    )
    (net (code "1004") (name "unconnected-(SV23-Pad18)") (class "Default")
      (node (ref "SV23") (pin "18") (pinfunction "18_18") (pintype "passive"))
    )
    (net (code "1005") (name "unconnected-(SV23-Pad19)") (class "Default")
      (node (ref "SV23") (pin "19") (pinfunction "19_19") (pintype "passive"))
    )
    (net (code "1006") (name "unconnected-(SV23-Pad20)") (class "Default")
      (node (ref "SV23") (pin "20") (pinfunction "20_20") (pintype "passive"))
    )
    (net (code "1007") (name "unconnected-(SV23-Pad21)") (class "Default")
      (node (ref "SV23") (pin "21") (pinfunction "21_21") (pintype "passive"))
    )
    (net (code "1008") (name "unconnected-(SV23-Pad22)") (class "Default")
      (node (ref "SV23") (pin "22") (pinfunction "22_22") (pintype "passive"))
    )
    (net (code "1009") (name "unconnected-(SV23-Pad23)") (class "Default")
      (node (ref "SV23") (pin "23") (pinfunction "23_23") (pintype "passive"))
    )
    (net (code "1010") (name "unconnected-(SV23-Pad24)") (class "Default")
      (node (ref "SV23") (pin "24") (pinfunction "24_24") (pintype "passive"))
    )
    (net (code "1011") (name "unconnected-(SV23-Pad25)") (class "Default")
      (node (ref "SV23") (pin "25") (pinfunction "25_25") (pintype "passive"))
    )
    (net (code "1012") (name "unconnected-(SV23-Pad26)") (class "Default")
      (node (ref "SV23") (pin "26") (pinfunction "26_26") (pintype "passive"))
    )
    (net (code "1013") (name "unconnected-(SV23-Pad27)") (class "Default")
      (node (ref "SV23") (pin "27") (pinfunction "27_27") (pintype "passive"))
    )
    (net (code "1014") (name "unconnected-(SV23-Pad28)") (class "Default")
      (node (ref "SV23") (pin "28") (pinfunction "28_28") (pintype "passive"))
    )
    (net (code "1015") (name "unconnected-(SV23-Pad29)") (class "Default")
      (node (ref "SV23") (pin "29") (pinfunction "29_29") (pintype "passive"))
    )
    (net (code "1016") (name "unconnected-(SV23-Pad30)") (class "Default")
      (node (ref "SV23") (pin "30") (pinfunction "30_30") (pintype "passive"))
    )
    (net (code "1017") (name "unconnected-(SV23-Pad31)") (class "Default")
      (node (ref "SV23") (pin "31") (pinfunction "31_31") (pintype "passive"))
    )
    (net (code "1018") (name "unconnected-(SV23-Pad32)") (class "Default")
      (node (ref "SV23") (pin "32") (pinfunction "32_32") (pintype "passive"))
    )
    (net (code "1019") (name "unconnected-(SV23-Pad33)") (class "Default")
      (node (ref "SV23") (pin "33") (pinfunction "33_33") (pintype "passive"))
    )
    (net (code "1020") (name "unconnected-(SV23-Pad34)") (class "Default")
      (node (ref "SV23") (pin "34") (pinfunction "34_34") (pintype "passive"))
    )
    (net (code "1021") (name "unconnected-(SV23-Pad35)") (class "Default")
      (node (ref "SV23") (pin "35") (pinfunction "35_35") (pintype "passive"))
    )
    (net (code "1022") (name "unconnected-(SV23-Pad36)") (class "Default")
      (node (ref "SV23") (pin "36") (pinfunction "36_36") (pintype "passive"))
    )
    (net (code "1023") (name "unconnected-(SV24-Pad1)") (class "Default")
      (node (ref "SV24") (pin "1") (pinfunction "1_1") (pintype "passive"))
    )
    (net (code "1024") (name "unconnected-(SV24-Pad2)") (class "Default")
      (node (ref "SV24") (pin "2") (pinfunction "2_2") (pintype "passive"))
    )
    (net (code "1025") (name "unconnected-(SV24-Pad3)") (class "Default")
      (node (ref "SV24") (pin "3") (pinfunction "3_3") (pintype "passive"))
    )
    (net (code "1026") (name "unconnected-(SV24-Pad4)") (class "Default")
      (node (ref "SV24") (pin "4") (pinfunction "4_4") (pintype "passive"))
    )
    (net (code "1027") (name "unconnected-(SV24-Pad5)") (class "Default")
      (node (ref "SV24") (pin "5") (pinfunction "5_5") (pintype "passive"))
    )
    (net (code "1028") (name "unconnected-(SV24-Pad6)") (class "Default")
      (node (ref "SV24") (pin "6") (pinfunction "6_6") (pintype "passive"))
    )
    (net (code "1029") (name "unconnected-(SV24-Pad7)") (class "Default")
      (node (ref "SV24") (pin "7") (pinfunction "7_7") (pintype "passive"))
    )
    (net (code "1030") (name "unconnected-(SV24-Pad8)") (class "Default")
      (node (ref "SV24") (pin "8") (pinfunction "8_8") (pintype "passive"))
    )
    (net (code "1031") (name "unconnected-(SV24-Pad9)") (class "Default")
      (node (ref "SV24") (pin "9") (pinfunction "9_9") (pintype "passive"))
    )
    (net (code "1032") (name "unconnected-(SV24-Pad10)") (class "Default")
      (node (ref "SV24") (pin "10") (pinfunction "10_10") (pintype "passive"))
    )
    (net (code "1033") (name "unconnected-(SV24-Pad11)") (class "Default")
      (node (ref "SV24") (pin "11") (pinfunction "11_11") (pintype "passive"))
    )
    (net (code "1034") (name "unconnected-(SV24-Pad12)") (class "Default")
      (node (ref "SV24") (pin "12") (pinfunction "12_12") (pintype "passive"))
    )
    (net (code "1035") (name "unconnected-(SV24-Pad13)") (class "Default")
      (node (ref "SV24") (pin "13") (pinfunction "13_13") (pintype "passive"))
    )
    (net (code "1036") (name "unconnected-(SV24-Pad14)") (class "Default")
      (node (ref "SV24") (pin "14") (pinfunction "14_14") (pintype "passive"))
    )
    (net (code "1037") (name "unconnected-(SV24-Pad15)") (class "Default")
      (node (ref "SV24") (pin "15") (pinfunction "15_15") (pintype "passive"))
    )
    (net (code "1038") (name "unconnected-(SV24-Pad16)") (class "Default")
      (node (ref "SV24") (pin "16") (pinfunction "16_16") (pintype "passive"))
    )
    (net (code "1039") (name "unconnected-(SV24-Pad17)") (class "Default")
      (node (ref "SV24") (pin "17") (pinfunction "17_17") (pintype "passive"))
    )
    (net (code "1040") (name "unconnected-(SV24-Pad18)") (class "Default")
      (node (ref "SV24") (pin "18") (pinfunction "18_18") (pintype "passive"))
    )
    (net (code "1041") (name "unconnected-(SV24-Pad19)") (class "Default")
      (node (ref "SV24") (pin "19") (pinfunction "19_19") (pintype "passive"))
    )
    (net (code "1042") (name "unconnected-(SV24-Pad20)") (class "Default")
      (node (ref "SV24") (pin "20") (pinfunction "20_20") (pintype "passive"))
    )
    (net (code "1043") (name "unconnected-(SV24-Pad21)") (class "Default")
      (node (ref "SV24") (pin "21") (pinfunction "21_21") (pintype "passive"))
    )
    (net (code "1044") (name "unconnected-(SV24-Pad22)") (class "Default")
      (node (ref "SV24") (pin "22") (pinfunction "22_22") (pintype "passive"))
    )
    (net (code "1045") (name "unconnected-(SV24-Pad23)") (class "Default")
      (node (ref "SV24") (pin "23") (pinfunction "23_23") (pintype "passive"))
    )
    (net (code "1046") (name "unconnected-(SV24-Pad24)") (class "Default")
      (node (ref "SV24") (pin "24") (pinfunction "24_24") (pintype "passive"))
    )
    (net (code "1047") (name "unconnected-(SV24-Pad25)") (class "Default")
      (node (ref "SV24") (pin "25") (pinfunction "25_25") (pintype "passive"))
    )
    (net (code "1048") (name "unconnected-(SV24-Pad26)") (class "Default")
      (node (ref "SV24") (pin "26") (pinfunction "26_26") (pintype "passive"))
    )
    (net (code "1049") (name "unconnected-(SV24-Pad27)") (class "Default")
      (node (ref "SV24") (pin "27") (pinfunction "27_27") (pintype "passive"))
    )
    (net (code "1050") (name "unconnected-(SV24-Pad28)") (class "Default")
      (node (ref "SV24") (pin "28") (pinfunction "28_28") (pintype "passive"))
    )
    (net (code "1051") (name "unconnected-(SV24-Pad29)") (class "Default")
      (node (ref "SV24") (pin "29") (pinfunction "29_29") (pintype "passive"))
    )
    (net (code "1052") (name "unconnected-(SV24-Pad30)") (class "Default")
      (node (ref "SV24") (pin "30") (pinfunction "30_30") (pintype "passive"))
    )
    (net (code "1053") (name "unconnected-(SV24-Pad31)") (class "Default")
      (node (ref "SV24") (pin "31") (pinfunction "31_31") (pintype "passive"))
    )
    (net (code "1054") (name "unconnected-(SV24-Pad32)") (class "Default")
      (node (ref "SV24") (pin "32") (pinfunction "32_32") (pintype "passive"))
    )
    (net (code "1055") (name "unconnected-(SV24-Pad33)") (class "Default")
      (node (ref "SV24") (pin "33") (pinfunction "33_33") (pintype "passive"))
    )
    (net (code "1056") (name "unconnected-(SV24-Pad34)") (class "Default")
      (node (ref "SV24") (pin "34") (pinfunction "34_34") (pintype "passive"))
    )
    (net (code "1057") (name "unconnected-(SV24-Pad35)") (class "Default")
      (node (ref "SV24") (pin "35") (pinfunction "35_35") (pintype "passive"))
    )
    (net (code "1058") (name "unconnected-(SV24-Pad36)") (class "Default")
      (node (ref "SV24") (pin "36") (pinfunction "36_36") (pintype "passive"))
    )
    (net (code "1059") (name "unconnected-(SV25-Pad1)") (class "Default")
      (node (ref "SV25") (pin "1") (pinfunction "1_1") (pintype "passive"))
    )
    (net (code "1060") (name "unconnected-(SV25-Pad2)") (class "Default")
      (node (ref "SV25") (pin "2") (pinfunction "2_2") (pintype "passive"))
    )
    (net (code "1061") (name "unconnected-(SV25-Pad3)") (class "Default")
      (node (ref "SV25") (pin "3") (pinfunction "3_3") (pintype "passive"))
    )
    (net (code "1062") (name "unconnected-(SV25-Pad4)") (class "Default")
      (node (ref "SV25") (pin "4") (pinfunction "4_4") (pintype "passive"))
    )
    (net (code "1063") (name "unconnected-(SV25-Pad5)") (class "Default")
      (node (ref "SV25") (pin "5") (pinfunction "5_5") (pintype "passive"))
    )
    (net (code "1064") (name "unconnected-(SV25-Pad6)") (class "Default")
      (node (ref "SV25") (pin "6") (pinfunction "6_6") (pintype "passive"))
    )
    (net (code "1065") (name "unconnected-(SV25-Pad7)") (class "Default")
      (node (ref "SV25") (pin "7") (pinfunction "7_7") (pintype "passive"))
    )
    (net (code "1066") (name "unconnected-(SV25-Pad8)") (class "Default")
      (node (ref "SV25") (pin "8") (pinfunction "8_8") (pintype "passive"))
    )
    (net (code "1067") (name "unconnected-(SV25-Pad9)") (class "Default")
      (node (ref "SV25") (pin "9") (pinfunction "9_9") (pintype "passive"))
    )
    (net (code "1068") (name "unconnected-(SV25-Pad10)") (class "Default")
      (node (ref "SV25") (pin "10") (pinfunction "10_10") (pintype "passive"))
    )
    (net (code "1069") (name "unconnected-(SV25-Pad11)") (class "Default")
      (node (ref "SV25") (pin "11") (pinfunction "11_11") (pintype "passive"))
    )
    (net (code "1070") (name "unconnected-(SV25-Pad12)") (class "Default")
      (node (ref "SV25") (pin "12") (pinfunction "12_12") (pintype "passive"))
    )
    (net (code "1071") (name "unconnected-(SV25-Pad13)") (class "Default")
      (node (ref "SV25") (pin "13") (pinfunction "13_13") (pintype "passive"))
    )
    (net (code "1072") (name "unconnected-(SV25-Pad14)") (class "Default")
      (node (ref "SV25") (pin "14") (pinfunction "14_14") (pintype "passive"))
    )
    (net (code "1073") (name "unconnected-(SV25-Pad15)") (class "Default")
      (node (ref "SV25") (pin "15") (pinfunction "15_15") (pintype "passive"))
    )
    (net (code "1074") (name "unconnected-(SV25-Pad16)") (class "Default")
      (node (ref "SV25") (pin "16") (pinfunction "16_16") (pintype "passive"))
    )
    (net (code "1075") (name "unconnected-(SV25-Pad17)") (class "Default")
      (node (ref "SV25") (pin "17") (pinfunction "17_17") (pintype "passive"))
    )
    (net (code "1076") (name "unconnected-(SV25-Pad18)") (class "Default")
      (node (ref "SV25") (pin "18") (pinfunction "18_18") (pintype "passive"))
    )
    (net (code "1077") (name "unconnected-(SV25-Pad19)") (class "Default")
      (node (ref "SV25") (pin "19") (pinfunction "19_19") (pintype "passive"))
    )
    (net (code "1078") (name "unconnected-(SV25-Pad20)") (class "Default")
      (node (ref "SV25") (pin "20") (pinfunction "20_20") (pintype "passive"))
    )
    (net (code "1079") (name "unconnected-(SV25-Pad21)") (class "Default")
      (node (ref "SV25") (pin "21") (pinfunction "21_21") (pintype "passive"))
    )
    (net (code "1080") (name "unconnected-(SV25-Pad22)") (class "Default")
      (node (ref "SV25") (pin "22") (pinfunction "22_22") (pintype "passive"))
    )
    (net (code "1081") (name "unconnected-(SV25-Pad23)") (class "Default")
      (node (ref "SV25") (pin "23") (pinfunction "23_23") (pintype "passive"))
    )
    (net (code "1082") (name "unconnected-(SV25-Pad24)") (class "Default")
      (node (ref "SV25") (pin "24") (pinfunction "24_24") (pintype "passive"))
    )
    (net (code "1083") (name "unconnected-(SV25-Pad25)") (class "Default")
      (node (ref "SV25") (pin "25") (pinfunction "25_25") (pintype "passive"))
    )
    (net (code "1084") (name "unconnected-(SV25-Pad26)") (class "Default")
      (node (ref "SV25") (pin "26") (pinfunction "26_26") (pintype "passive"))
    )
    (net (code "1085") (name "unconnected-(SV25-Pad27)") (class "Default")
      (node (ref "SV25") (pin "27") (pinfunction "27_27") (pintype "passive"))
    )
    (net (code "1086") (name "unconnected-(SV25-Pad28)") (class "Default")
      (node (ref "SV25") (pin "28") (pinfunction "28_28") (pintype "passive"))
    )
    (net (code "1087") (name "unconnected-(SV25-Pad29)") (class "Default")
      (node (ref "SV25") (pin "29") (pinfunction "29_29") (pintype "passive"))
    )
    (net (code "1088") (name "unconnected-(SV25-Pad30)") (class "Default")
      (node (ref "SV25") (pin "30") (pinfunction "30_30") (pintype "passive"))
    )
    (net (code "1089") (name "unconnected-(SV25-Pad31)") (class "Default")
      (node (ref "SV25") (pin "31") (pinfunction "31_31") (pintype "passive"))
    )
    (net (code "1090") (name "unconnected-(SV25-Pad32)") (class "Default")
      (node (ref "SV25") (pin "32") (pinfunction "32_32") (pintype "passive"))
    )
    (net (code "1091") (name "unconnected-(SV25-Pad33)") (class "Default")
      (node (ref "SV25") (pin "33") (pinfunction "33_33") (pintype "passive"))
    )
    (net (code "1092") (name "unconnected-(SV25-Pad34)") (class "Default")
      (node (ref "SV25") (pin "34") (pinfunction "34_34") (pintype "passive"))
    )
    (net (code "1093") (name "unconnected-(SV25-Pad35)") (class "Default")
      (node (ref "SV25") (pin "35") (pinfunction "35_35") (pintype "passive"))
    )
    (net (code "1094") (name "unconnected-(SV25-Pad36)") (class "Default")
      (node (ref "SV25") (pin "36") (pinfunction "36_36") (pintype "passive"))
    )
    (net (code "1095") (name "unconnected-(SV26-Pad1)") (class "Default")
      (node (ref "SV26") (pin "1") (pinfunction "1_1") (pintype "passive"))
    )
    (net (code "1096") (name "unconnected-(SV26-Pad2)") (class "Default")
      (node (ref "SV26") (pin "2") (pinfunction "2_2") (pintype "passive"))
    )
    (net (code "1097") (name "unconnected-(SV26-Pad3)") (class "Default")
      (node (ref "SV26") (pin "3") (pinfunction "3_3") (pintype "passive"))
    )
    (net (code "1098") (name "unconnected-(SV26-Pad4)") (class "Default")
      (node (ref "SV26") (pin "4") (pinfunction "4_4") (pintype "passive"))
    )
    (net (code "1099") (name "unconnected-(SV26-Pad5)") (class "Default")
      (node (ref "SV26") (pin "5") (pinfunction "5_5") (pintype "passive"))
    )
    (net (code "1100") (name "unconnected-(SV26-Pad6)") (class "Default")
      (node (ref "SV26") (pin "6") (pinfunction "6_6") (pintype "passive"))
    )
    (net (code "1101") (name "unconnected-(SV26-Pad7)") (class "Default")
      (node (ref "SV26") (pin "7") (pinfunction "7_7") (pintype "passive"))
    )
    (net (code "1102") (name "unconnected-(SV26-Pad8)") (class "Default")
      (node (ref "SV26") (pin "8") (pinfunction "8_8") (pintype "passive"))
    )
    (net (code "1103") (name "unconnected-(SV26-Pad9)") (class "Default")
      (node (ref "SV26") (pin "9") (pinfunction "9_9") (pintype "passive"))
    )
    (net (code "1104") (name "unconnected-(SV26-Pad10)") (class "Default")
      (node (ref "SV26") (pin "10") (pinfunction "10_10") (pintype "passive"))
    )
    (net (code "1105") (name "unconnected-(SV26-Pad11)") (class "Default")
      (node (ref "SV26") (pin "11") (pinfunction "11_11") (pintype "passive"))
    )
    (net (code "1106") (name "unconnected-(SV26-Pad12)") (class "Default")
      (node (ref "SV26") (pin "12") (pinfunction "12_12") (pintype "passive"))
    )
    (net (code "1107") (name "unconnected-(SV26-Pad13)") (class "Default")
      (node (ref "SV26") (pin "13") (pinfunction "13_13") (pintype "passive"))
    )
    (net (code "1108") (name "unconnected-(SV26-Pad14)") (class "Default")
      (node (ref "SV26") (pin "14") (pinfunction "14_14") (pintype "passive"))
    )
    (net (code "1109") (name "unconnected-(SV26-Pad15)") (class "Default")
      (node (ref "SV26") (pin "15") (pinfunction "15_15") (pintype "passive"))
    )
    (net (code "1110") (name "unconnected-(SV26-Pad16)") (class "Default")
      (node (ref "SV26") (pin "16") (pinfunction "16_16") (pintype "passive"))
    )
    (net (code "1111") (name "unconnected-(SV26-Pad17)") (class "Default")
      (node (ref "SV26") (pin "17") (pinfunction "17_17") (pintype "passive"))
    )
    (net (code "1112") (name "unconnected-(SV26-Pad18)") (class "Default")
      (node (ref "SV26") (pin "18") (pinfunction "18_18") (pintype "passive"))
    )
    (net (code "1113") (name "unconnected-(SV26-Pad19)") (class "Default")
      (node (ref "SV26") (pin "19") (pinfunction "19_19") (pintype "passive"))
    )
    (net (code "1114") (name "unconnected-(SV26-Pad20)") (class "Default")
      (node (ref "SV26") (pin "20") (pinfunction "20_20") (pintype "passive"))
    )
    (net (code "1115") (name "unconnected-(SV26-Pad21)") (class "Default")
      (node (ref "SV26") (pin "21") (pinfunction "21_21") (pintype "passive"))
    )
    (net (code "1116") (name "unconnected-(SV26-Pad22)") (class "Default")
      (node (ref "SV26") (pin "22") (pinfunction "22_22") (pintype "passive"))
    )
    (net (code "1117") (name "unconnected-(SV26-Pad23)") (class "Default")
      (node (ref "SV26") (pin "23") (pinfunction "23_23") (pintype "passive"))
    )
    (net (code "1118") (name "unconnected-(SV26-Pad24)") (class "Default")
      (node (ref "SV26") (pin "24") (pinfunction "24_24") (pintype "passive"))
    )
    (net (code "1119") (name "unconnected-(SV26-Pad25)") (class "Default")
      (node (ref "SV26") (pin "25") (pinfunction "25_25") (pintype "passive"))
    )
    (net (code "1120") (name "unconnected-(SV26-Pad26)") (class "Default")
      (node (ref "SV26") (pin "26") (pinfunction "26_26") (pintype "passive"))
    )
    (net (code "1121") (name "unconnected-(SV26-Pad27)") (class "Default")
      (node (ref "SV26") (pin "27") (pinfunction "27_27") (pintype "passive"))
    )
    (net (code "1122") (name "unconnected-(SV26-Pad28)") (class "Default")
      (node (ref "SV26") (pin "28") (pinfunction "28_28") (pintype "passive"))
    )
    (net (code "1123") (name "unconnected-(SV26-Pad29)") (class "Default")
      (node (ref "SV26") (pin "29") (pinfunction "29_29") (pintype "passive"))
    )
    (net (code "1124") (name "unconnected-(SV26-Pad30)") (class "Default")
      (node (ref "SV26") (pin "30") (pinfunction "30_30") (pintype "passive"))
    )
    (net (code "1125") (name "unconnected-(SV26-Pad31)") (class "Default")
      (node (ref "SV26") (pin "31") (pinfunction "31_31") (pintype "passive"))
    )
    (net (code "1126") (name "unconnected-(SV26-Pad32)") (class "Default")
      (node (ref "SV26") (pin "32") (pinfunction "32_32") (pintype "passive"))
    )
    (net (code "1127") (name "unconnected-(SV26-Pad33)") (class "Default")
      (node (ref "SV26") (pin "33") (pinfunction "33_33") (pintype "passive"))
    )
    (net (code "1128") (name "unconnected-(SV26-Pad34)") (class "Default")
      (node (ref "SV26") (pin "34") (pinfunction "34_34") (pintype "passive"))
    )
    (net (code "1129") (name "unconnected-(SV26-Pad35)") (class "Default")
      (node (ref "SV26") (pin "35") (pinfunction "35_35") (pintype "passive"))
    )
    (net (code "1130") (name "unconnected-(SV26-Pad36)") (class "Default")
      (node (ref "SV26") (pin "36") (pinfunction "36_36") (pintype "passive"))
    )
    (net (code "1131") (name "unconnected-(SV27-Pad1)") (class "Default")
      (node (ref "SV27") (pin "1") (pinfunction "1_1") (pintype "passive"))
    )
    (net (code "1132") (name "unconnected-(SV27-Pad2)") (class "Default")
      (node (ref "SV27") (pin "2") (pinfunction "2_2") (pintype "passive"))
    )
    (net (code "1133") (name "unconnected-(SV27-Pad3)") (class "Default")
      (node (ref "SV27") (pin "3") (pinfunction "3_3") (pintype "passive"))
    )
    (net (code "1134") (name "unconnected-(SV27-Pad4)") (class "Default")
      (node (ref "SV27") (pin "4") (pinfunction "4_4") (pintype "passive"))
    )
    (net (code "1135") (name "unconnected-(SV27-Pad5)") (class "Default")
      (node (ref "SV27") (pin "5") (pinfunction "5_5") (pintype "passive"))
    )
    (net (code "1136") (name "unconnected-(SV27-Pad6)") (class "Default")
      (node (ref "SV27") (pin "6") (pinfunction "6_6") (pintype "passive"))
    )
    (net (code "1137") (name "unconnected-(SV27-Pad7)") (class "Default")
      (node (ref "SV27") (pin "7") (pinfunction "7_7") (pintype "passive"))
    )
    (net (code "1138") (name "unconnected-(SV27-Pad8)") (class "Default")
      (node (ref "SV27") (pin "8") (pinfunction "8_8") (pintype "passive"))
    )
    (net (code "1139") (name "unconnected-(SV27-Pad9)") (class "Default")
      (node (ref "SV27") (pin "9") (pinfunction "9_9") (pintype "passive"))
    )
    (net (code "1140") (name "unconnected-(SV27-Pad10)") (class "Default")
      (node (ref "SV27") (pin "10") (pinfunction "10_10") (pintype "passive"))
    )
    (net (code "1141") (name "unconnected-(SV27-Pad11)") (class "Default")
      (node (ref "SV27") (pin "11") (pinfunction "11_11") (pintype "passive"))
    )
    (net (code "1142") (name "unconnected-(SV27-Pad12)") (class "Default")
      (node (ref "SV27") (pin "12") (pinfunction "12_12") (pintype "passive"))
    )
    (net (code "1143") (name "unconnected-(SV27-Pad13)") (class "Default")
      (node (ref "SV27") (pin "13") (pinfunction "13_13") (pintype "passive"))
    )
    (net (code "1144") (name "unconnected-(SV27-Pad14)") (class "Default")
      (node (ref "SV27") (pin "14") (pinfunction "14_14") (pintype "passive"))
    )
    (net (code "1145") (name "unconnected-(SV27-Pad15)") (class "Default")
      (node (ref "SV27") (pin "15") (pinfunction "15_15") (pintype "passive"))
    )
    (net (code "1146") (name "unconnected-(SV27-Pad16)") (class "Default")
      (node (ref "SV27") (pin "16") (pinfunction "16_16") (pintype "passive"))
    )
    (net (code "1147") (name "unconnected-(SV27-Pad17)") (class "Default")
      (node (ref "SV27") (pin "17") (pinfunction "17_17") (pintype "passive"))
    )
    (net (code "1148") (name "unconnected-(SV27-Pad18)") (class "Default")
      (node (ref "SV27") (pin "18") (pinfunction "18_18") (pintype "passive"))
    )
    (net (code "1149") (name "unconnected-(SV27-Pad19)") (class "Default")
      (node (ref "SV27") (pin "19") (pinfunction "19_19") (pintype "passive"))
    )
    (net (code "1150") (name "unconnected-(SV27-Pad20)") (class "Default")
      (node (ref "SV27") (pin "20") (pinfunction "20_20") (pintype "passive"))
    )
    (net (code "1151") (name "unconnected-(SV27-Pad21)") (class "Default")
      (node (ref "SV27") (pin "21") (pinfunction "21_21") (pintype "passive"))
    )
    (net (code "1152") (name "unconnected-(SV27-Pad22)") (class "Default")
      (node (ref "SV27") (pin "22") (pinfunction "22_22") (pintype "passive"))
    )
    (net (code "1153") (name "unconnected-(SV27-Pad23)") (class "Default")
      (node (ref "SV27") (pin "23") (pinfunction "23_23") (pintype "passive"))
    )
    (net (code "1154") (name "unconnected-(SV27-Pad24)") (class "Default")
      (node (ref "SV27") (pin "24") (pinfunction "24_24") (pintype "passive"))
    )
    (net (code "1155") (name "unconnected-(SV27-Pad25)") (class "Default")
      (node (ref "SV27") (pin "25") (pinfunction "25_25") (pintype "passive"))
    )
    (net (code "1156") (name "unconnected-(SV27-Pad26)") (class "Default")
      (node (ref "SV27") (pin "26") (pinfunction "26_26") (pintype "passive"))
    )
    (net (code "1157") (name "unconnected-(SV27-Pad27)") (class "Default")
      (node (ref "SV27") (pin "27") (pinfunction "27_27") (pintype "passive"))
    )
    (net (code "1158") (name "unconnected-(SV27-Pad28)") (class "Default")
      (node (ref "SV27") (pin "28") (pinfunction "28_28") (pintype "passive"))
    )
    (net (code "1159") (name "unconnected-(SV27-Pad29)") (class "Default")
      (node (ref "SV27") (pin "29") (pinfunction "29_29") (pintype "passive"))
    )
    (net (code "1160") (name "unconnected-(SV27-Pad30)") (class "Default")
      (node (ref "SV27") (pin "30") (pinfunction "30_30") (pintype "passive"))
    )
    (net (code "1161") (name "unconnected-(SV27-Pad31)") (class "Default")
      (node (ref "SV27") (pin "31") (pinfunction "31_31") (pintype "passive"))
    )
    (net (code "1162") (name "unconnected-(SV27-Pad32)") (class "Default")
      (node (ref "SV27") (pin "32") (pinfunction "32_32") (pintype "passive"))
    )
    (net (code "1163") (name "unconnected-(SV27-Pad33)") (class "Default")
      (node (ref "SV27") (pin "33") (pinfunction "33_33") (pintype "passive"))
    )
    (net (code "1164") (name "unconnected-(SV27-Pad34)") (class "Default")
      (node (ref "SV27") (pin "34") (pinfunction "34_34") (pintype "passive"))
    )
    (net (code "1165") (name "unconnected-(SV27-Pad35)") (class "Default")
      (node (ref "SV27") (pin "35") (pinfunction "35_35") (pintype "passive"))
    )
    (net (code "1166") (name "unconnected-(SV27-Pad36)") (class "Default")
      (node (ref "SV27") (pin "36") (pinfunction "36_36") (pintype "passive"))
    )
    (net (code "1167") (name "unconnected-(SV27-Pad37)") (class "Default")
      (node (ref "SV27") (pin "37") (pinfunction "37_37") (pintype "passive"))
    )
    (net (code "1168") (name "unconnected-(SV27-Pad38)") (class "Default")
      (node (ref "SV27") (pin "38") (pinfunction "38_38") (pintype "passive"))
    )
    (net (code "1169") (name "unconnected-(SV27-Pad39)") (class "Default")
      (node (ref "SV27") (pin "39") (pinfunction "39_39") (pintype "passive"))
    )
    (net (code "1170") (name "unconnected-(SV27-Pad40)") (class "Default")
      (node (ref "SV27") (pin "40") (pinfunction "40_40") (pintype "passive"))
    )
    (net (code "1171") (name "unconnected-(SV28-Pad1)") (class "Default")
      (node (ref "SV28") (pin "1") (pinfunction "1_1") (pintype "passive"))
    )
    (net (code "1172") (name "unconnected-(SV28-Pad2)") (class "Default")
      (node (ref "SV28") (pin "2") (pinfunction "2_2") (pintype "passive"))
    )
    (net (code "1173") (name "unconnected-(SV28-Pad3)") (class "Default")
      (node (ref "SV28") (pin "3") (pinfunction "3_3") (pintype "passive"))
    )
    (net (code "1174") (name "unconnected-(SV28-Pad4)") (class "Default")
      (node (ref "SV28") (pin "4") (pinfunction "4_4") (pintype "passive"))
    )
    (net (code "1175") (name "unconnected-(SV28-Pad5)") (class "Default")
      (node (ref "SV28") (pin "5") (pinfunction "5_5") (pintype "passive"))
    )
    (net (code "1176") (name "unconnected-(SV28-Pad6)") (class "Default")
      (node (ref "SV28") (pin "6") (pinfunction "6_6") (pintype "passive"))
    )
    (net (code "1177") (name "unconnected-(SV28-Pad7)") (class "Default")
      (node (ref "SV28") (pin "7") (pinfunction "7_7") (pintype "passive"))
    )
    (net (code "1178") (name "unconnected-(SV28-Pad8)") (class "Default")
      (node (ref "SV28") (pin "8") (pinfunction "8_8") (pintype "passive"))
    )
    (net (code "1179") (name "unconnected-(SV28-Pad9)") (class "Default")
      (node (ref "SV28") (pin "9") (pinfunction "9_9") (pintype "passive"))
    )
    (net (code "1180") (name "unconnected-(SV28-Pad10)") (class "Default")
      (node (ref "SV28") (pin "10") (pinfunction "10_10") (pintype "passive"))
    )
    (net (code "1181") (name "unconnected-(SV28-Pad11)") (class "Default")
      (node (ref "SV28") (pin "11") (pinfunction "11_11") (pintype "passive"))
    )
    (net (code "1182") (name "unconnected-(SV28-Pad12)") (class "Default")
      (node (ref "SV28") (pin "12") (pinfunction "12_12") (pintype "passive"))
    )
    (net (code "1183") (name "unconnected-(SV28-Pad13)") (class "Default")
      (node (ref "SV28") (pin "13") (pinfunction "13_13") (pintype "passive"))
    )
    (net (code "1184") (name "unconnected-(SV28-Pad14)") (class "Default")
      (node (ref "SV28") (pin "14") (pinfunction "14_14") (pintype "passive"))
    )
    (net (code "1185") (name "unconnected-(SV28-Pad15)") (class "Default")
      (node (ref "SV28") (pin "15") (pinfunction "15_15") (pintype "passive"))
    )
    (net (code "1186") (name "unconnected-(SV28-Pad16)") (class "Default")
      (node (ref "SV28") (pin "16") (pinfunction "16_16") (pintype "passive"))
    )
    (net (code "1187") (name "unconnected-(SV28-Pad17)") (class "Default")
      (node (ref "SV28") (pin "17") (pinfunction "17_17") (pintype "passive"))
    )
    (net (code "1188") (name "unconnected-(SV28-Pad18)") (class "Default")
      (node (ref "SV28") (pin "18") (pinfunction "18_18") (pintype "passive"))
    )
    (net (code "1189") (name "unconnected-(SV28-Pad19)") (class "Default")
      (node (ref "SV28") (pin "19") (pinfunction "19_19") (pintype "passive"))
    )
    (net (code "1190") (name "unconnected-(SV28-Pad20)") (class "Default")
      (node (ref "SV28") (pin "20") (pinfunction "20_20") (pintype "passive"))
    )
    (net (code "1191") (name "unconnected-(SV28-Pad21)") (class "Default")
      (node (ref "SV28") (pin "21") (pinfunction "21_21") (pintype "passive"))
    )
    (net (code "1192") (name "unconnected-(SV28-Pad22)") (class "Default")
      (node (ref "SV28") (pin "22") (pinfunction "22_22") (pintype "passive"))
    )
    (net (code "1193") (name "unconnected-(SV28-Pad23)") (class "Default")
      (node (ref "SV28") (pin "23") (pinfunction "23_23") (pintype "passive"))
    )
    (net (code "1194") (name "unconnected-(SV28-Pad24)") (class "Default")
      (node (ref "SV28") (pin "24") (pinfunction "24_24") (pintype "passive"))
    )
    (net (code "1195") (name "unconnected-(SV28-Pad25)") (class "Default")
      (node (ref "SV28") (pin "25") (pinfunction "25_25") (pintype "passive"))
    )
    (net (code "1196") (name "unconnected-(SV28-Pad26)") (class "Default")
      (node (ref "SV28") (pin "26") (pinfunction "26_26") (pintype "passive"))
    )
    (net (code "1197") (name "unconnected-(SV28-Pad27)") (class "Default")
      (node (ref "SV28") (pin "27") (pinfunction "27_27") (pintype "passive"))
    )
    (net (code "1198") (name "unconnected-(SV28-Pad28)") (class "Default")
      (node (ref "SV28") (pin "28") (pinfunction "28_28") (pintype "passive"))
    )
    (net (code "1199") (name "unconnected-(SV28-Pad29)") (class "Default")
      (node (ref "SV28") (pin "29") (pinfunction "29_29") (pintype "passive"))
    )
    (net (code "1200") (name "unconnected-(SV28-Pad30)") (class "Default")
      (node (ref "SV28") (pin "30") (pinfunction "30_30") (pintype "passive"))
    )
    (net (code "1201") (name "unconnected-(SV28-Pad31)") (class "Default")
      (node (ref "SV28") (pin "31") (pinfunction "31_31") (pintype "passive"))
    )
    (net (code "1202") (name "unconnected-(SV28-Pad32)") (class "Default")
      (node (ref "SV28") (pin "32") (pinfunction "32_32") (pintype "passive"))
    )
    (net (code "1203") (name "unconnected-(SV28-Pad33)") (class "Default")
      (node (ref "SV28") (pin "33") (pinfunction "33_33") (pintype "passive"))
    )
    (net (code "1204") (name "unconnected-(SV28-Pad34)") (class "Default")
      (node (ref "SV28") (pin "34") (pinfunction "34_34") (pintype "passive"))
    )
    (net (code "1205") (name "unconnected-(SV28-Pad35)") (class "Default")
      (node (ref "SV28") (pin "35") (pinfunction "35_35") (pintype "passive"))
    )
    (net (code "1206") (name "unconnected-(SV28-Pad36)") (class "Default")
      (node (ref "SV28") (pin "36") (pinfunction "36_36") (pintype "passive"))
    )
    (net (code "1207") (name "unconnected-(SV28-Pad37)") (class "Default")
      (node (ref "SV28") (pin "37") (pinfunction "37_37") (pintype "passive"))
    )
    (net (code "1208") (name "unconnected-(SV28-Pad38)") (class "Default")
      (node (ref "SV28") (pin "38") (pinfunction "38_38") (pintype "passive"))
    )
    (net (code "1209") (name "unconnected-(SV28-Pad39)") (class "Default")
      (node (ref "SV28") (pin "39") (pinfunction "39_39") (pintype "passive"))
    )
    (net (code "1210") (name "unconnected-(SV28-Pad40)") (class "Default")
      (node (ref "SV28") (pin "40") (pinfunction "40_40") (pintype "passive"))
    )
    (net (code "1211") (name "unconnected-(SV29-Pad1)") (class "Default")
      (node (ref "SV29") (pin "1") (pinfunction "1_1") (pintype "passive"))
    )
    (net (code "1212") (name "unconnected-(SV29-Pad2)") (class "Default")
      (node (ref "SV29") (pin "2") (pinfunction "2_2") (pintype "passive"))
    )
    (net (code "1213") (name "unconnected-(SV29-Pad3)") (class "Default")
      (node (ref "SV29") (pin "3") (pinfunction "3_3") (pintype "passive"))
    )
    (net (code "1214") (name "unconnected-(SV29-Pad4)") (class "Default")
      (node (ref "SV29") (pin "4") (pinfunction "4_4") (pintype "passive"))
    )
    (net (code "1215") (name "unconnected-(SV29-Pad5)") (class "Default")
      (node (ref "SV29") (pin "5") (pinfunction "5_5") (pintype "passive"))
    )
    (net (code "1216") (name "unconnected-(SV29-Pad6)") (class "Default")
      (node (ref "SV29") (pin "6") (pinfunction "6_6") (pintype "passive"))
    )
    (net (code "1217") (name "unconnected-(SV29-Pad7)") (class "Default")
      (node (ref "SV29") (pin "7") (pinfunction "7_7") (pintype "passive"))
    )
    (net (code "1218") (name "unconnected-(SV29-Pad8)") (class "Default")
      (node (ref "SV29") (pin "8") (pinfunction "8_8") (pintype "passive"))
    )
    (net (code "1219") (name "unconnected-(SV29-Pad9)") (class "Default")
      (node (ref "SV29") (pin "9") (pinfunction "9_9") (pintype "passive"))
    )
    (net (code "1220") (name "unconnected-(SV29-Pad10)") (class "Default")
      (node (ref "SV29") (pin "10") (pinfunction "10_10") (pintype "passive"))
    )
    (net (code "1221") (name "unconnected-(SV29-Pad11)") (class "Default")
      (node (ref "SV29") (pin "11") (pinfunction "11_11") (pintype "passive"))
    )
    (net (code "1222") (name "unconnected-(SV29-Pad12)") (class "Default")
      (node (ref "SV29") (pin "12") (pinfunction "12_12") (pintype "passive"))
    )
    (net (code "1223") (name "unconnected-(SV29-Pad13)") (class "Default")
      (node (ref "SV29") (pin "13") (pinfunction "13_13") (pintype "passive"))
    )
    (net (code "1224") (name "unconnected-(SV29-Pad14)") (class "Default")
      (node (ref "SV29") (pin "14") (pinfunction "14_14") (pintype "passive"))
    )
    (net (code "1225") (name "unconnected-(SV29-Pad15)") (class "Default")
      (node (ref "SV29") (pin "15") (pinfunction "15_15") (pintype "passive"))
    )
    (net (code "1226") (name "unconnected-(SV29-Pad16)") (class "Default")
      (node (ref "SV29") (pin "16") (pinfunction "16_16") (pintype "passive"))
    )
    (net (code "1227") (name "unconnected-(SV29-Pad17)") (class "Default")
      (node (ref "SV29") (pin "17") (pinfunction "17_17") (pintype "passive"))
    )
    (net (code "1228") (name "unconnected-(SV29-Pad18)") (class "Default")
      (node (ref "SV29") (pin "18") (pinfunction "18_18") (pintype "passive"))
    )
    (net (code "1229") (name "unconnected-(SV29-Pad19)") (class "Default")
      (node (ref "SV29") (pin "19") (pinfunction "19_19") (pintype "passive"))
    )
    (net (code "1230") (name "unconnected-(SV29-Pad20)") (class "Default")
      (node (ref "SV29") (pin "20") (pinfunction "20_20") (pintype "passive"))
    )
    (net (code "1231") (name "unconnected-(SV29-Pad21)") (class "Default")
      (node (ref "SV29") (pin "21") (pinfunction "21_21") (pintype "passive"))
    )
    (net (code "1232") (name "unconnected-(SV29-Pad22)") (class "Default")
      (node (ref "SV29") (pin "22") (pinfunction "22_22") (pintype "passive"))
    )
    (net (code "1233") (name "unconnected-(SV29-Pad23)") (class "Default")
      (node (ref "SV29") (pin "23") (pinfunction "23_23") (pintype "passive"))
    )
    (net (code "1234") (name "unconnected-(SV29-Pad24)") (class "Default")
      (node (ref "SV29") (pin "24") (pinfunction "24_24") (pintype "passive"))
    )
    (net (code "1235") (name "unconnected-(SV29-Pad25)") (class "Default")
      (node (ref "SV29") (pin "25") (pinfunction "25_25") (pintype "passive"))
    )
    (net (code "1236") (name "unconnected-(SV29-Pad26)") (class "Default")
      (node (ref "SV29") (pin "26") (pinfunction "26_26") (pintype "passive"))
    )
    (net (code "1237") (name "unconnected-(SV29-Pad27)") (class "Default")
      (node (ref "SV29") (pin "27") (pinfunction "27_27") (pintype "passive"))
    )
    (net (code "1238") (name "unconnected-(SV29-Pad28)") (class "Default")
      (node (ref "SV29") (pin "28") (pinfunction "28_28") (pintype "passive"))
    )
    (net (code "1239") (name "unconnected-(SV29-Pad29)") (class "Default")
      (node (ref "SV29") (pin "29") (pinfunction "29_29") (pintype "passive"))
    )
    (net (code "1240") (name "unconnected-(SV29-Pad30)") (class "Default")
      (node (ref "SV29") (pin "30") (pinfunction "30_30") (pintype "passive"))
    )
    (net (code "1241") (name "unconnected-(SV29-Pad31)") (class "Default")
      (node (ref "SV29") (pin "31") (pinfunction "31_31") (pintype "passive"))
    )
    (net (code "1242") (name "unconnected-(SV29-Pad32)") (class "Default")
      (node (ref "SV29") (pin "32") (pinfunction "32_32") (pintype "passive"))
    )
    (net (code "1243") (name "unconnected-(SV29-Pad33)") (class "Default")
      (node (ref "SV29") (pin "33") (pinfunction "33_33") (pintype "passive"))
    )
    (net (code "1244") (name "unconnected-(SV29-Pad34)") (class "Default")
      (node (ref "SV29") (pin "34") (pinfunction "34_34") (pintype "passive"))
    )
    (net (code "1245") (name "unconnected-(SV29-Pad35)") (class "Default")
      (node (ref "SV29") (pin "35") (pinfunction "35_35") (pintype "passive"))
    )
    (net (code "1246") (name "unconnected-(SV29-Pad36)") (class "Default")
      (node (ref "SV29") (pin "36") (pinfunction "36_36") (pintype "passive"))
    )
    (net (code "1247") (name "unconnected-(SV29-Pad37)") (class "Default")
      (node (ref "SV29") (pin "37") (pinfunction "37_37") (pintype "passive"))
    )
    (net (code "1248") (name "unconnected-(SV29-Pad38)") (class "Default")
      (node (ref "SV29") (pin "38") (pinfunction "38_38") (pintype "passive"))
    )
    (net (code "1249") (name "unconnected-(SV29-Pad39)") (class "Default")
      (node (ref "SV29") (pin "39") (pinfunction "39_39") (pintype "passive"))
    )
    (net (code "1250") (name "unconnected-(SV29-Pad40)") (class "Default")
      (node (ref "SV29") (pin "40") (pinfunction "40_40") (pintype "passive"))
    )
    (net (code "1251") (name "unconnected-(SV30-Pad1)") (class "Default")
      (node (ref "SV30") (pin "1") (pinfunction "1_1") (pintype "passive"))
    )
    (net (code "1252") (name "unconnected-(SV30-Pad2)") (class "Default")
      (node (ref "SV30") (pin "2") (pinfunction "2_2") (pintype "passive"))
    )
    (net (code "1253") (name "unconnected-(SV30-Pad3)") (class "Default")
      (node (ref "SV30") (pin "3") (pinfunction "3_3") (pintype "passive"))
    )
    (net (code "1254") (name "unconnected-(SV30-Pad4)") (class "Default")
      (node (ref "SV30") (pin "4") (pinfunction "4_4") (pintype "passive"))
    )
    (net (code "1255") (name "unconnected-(SV30-Pad5)") (class "Default")
      (node (ref "SV30") (pin "5") (pinfunction "5_5") (pintype "passive"))
    )
    (net (code "1256") (name "unconnected-(SV30-Pad6)") (class "Default")
      (node (ref "SV30") (pin "6") (pinfunction "6_6") (pintype "passive"))
    )
    (net (code "1257") (name "unconnected-(SV30-Pad7)") (class "Default")
      (node (ref "SV30") (pin "7") (pinfunction "7_7") (pintype "passive"))
    )
    (net (code "1258") (name "unconnected-(SV30-Pad8)") (class "Default")
      (node (ref "SV30") (pin "8") (pinfunction "8_8") (pintype "passive"))
    )
    (net (code "1259") (name "unconnected-(SV30-Pad9)") (class "Default")
      (node (ref "SV30") (pin "9") (pinfunction "9_9") (pintype "passive"))
    )
    (net (code "1260") (name "unconnected-(SV30-Pad10)") (class "Default")
      (node (ref "SV30") (pin "10") (pinfunction "10_10") (pintype "passive"))
    )
    (net (code "1261") (name "unconnected-(SV30-Pad11)") (class "Default")
      (node (ref "SV30") (pin "11") (pinfunction "11_11") (pintype "passive"))
    )
    (net (code "1262") (name "unconnected-(SV30-Pad12)") (class "Default")
      (node (ref "SV30") (pin "12") (pinfunction "12_12") (pintype "passive"))
    )
    (net (code "1263") (name "unconnected-(SV30-Pad13)") (class "Default")
      (node (ref "SV30") (pin "13") (pinfunction "13_13") (pintype "passive"))
    )
    (net (code "1264") (name "unconnected-(SV30-Pad14)") (class "Default")
      (node (ref "SV30") (pin "14") (pinfunction "14_14") (pintype "passive"))
    )
    (net (code "1265") (name "unconnected-(SV30-Pad15)") (class "Default")
      (node (ref "SV30") (pin "15") (pinfunction "15_15") (pintype "passive"))
    )
    (net (code "1266") (name "unconnected-(SV30-Pad16)") (class "Default")
      (node (ref "SV30") (pin "16") (pinfunction "16_16") (pintype "passive"))
    )
    (net (code "1267") (name "unconnected-(SV30-Pad17)") (class "Default")
      (node (ref "SV30") (pin "17") (pinfunction "17_17") (pintype "passive"))
    )
    (net (code "1268") (name "unconnected-(SV30-Pad18)") (class "Default")
      (node (ref "SV30") (pin "18") (pinfunction "18_18") (pintype "passive"))
    )
    (net (code "1269") (name "unconnected-(SV30-Pad19)") (class "Default")
      (node (ref "SV30") (pin "19") (pinfunction "19_19") (pintype "passive"))
    )
    (net (code "1270") (name "unconnected-(SV30-Pad20)") (class "Default")
      (node (ref "SV30") (pin "20") (pinfunction "20_20") (pintype "passive"))
    )
    (net (code "1271") (name "unconnected-(SV30-Pad21)") (class "Default")
      (node (ref "SV30") (pin "21") (pinfunction "21_21") (pintype "passive"))
    )
    (net (code "1272") (name "unconnected-(SV30-Pad22)") (class "Default")
      (node (ref "SV30") (pin "22") (pinfunction "22_22") (pintype "passive"))
    )
    (net (code "1273") (name "unconnected-(SV30-Pad23)") (class "Default")
      (node (ref "SV30") (pin "23") (pinfunction "23_23") (pintype "passive"))
    )
    (net (code "1274") (name "unconnected-(SV30-Pad24)") (class "Default")
      (node (ref "SV30") (pin "24") (pinfunction "24_24") (pintype "passive"))
    )
    (net (code "1275") (name "unconnected-(SV30-Pad25)") (class "Default")
      (node (ref "SV30") (pin "25") (pinfunction "25_25") (pintype "passive"))
    )
    (net (code "1276") (name "unconnected-(SV30-Pad26)") (class "Default")
      (node (ref "SV30") (pin "26") (pinfunction "26_26") (pintype "passive"))
    )
    (net (code "1277") (name "unconnected-(SV30-Pad27)") (class "Default")
      (node (ref "SV30") (pin "27") (pinfunction "27_27") (pintype "passive"))
    )
    (net (code "1278") (name "unconnected-(SV30-Pad28)") (class "Default")
      (node (ref "SV30") (pin "28") (pinfunction "28_28") (pintype "passive"))
    )
    (net (code "1279") (name "unconnected-(SV30-Pad29)") (class "Default")
      (node (ref "SV30") (pin "29") (pinfunction "29_29") (pintype "passive"))
    )
    (net (code "1280") (name "unconnected-(SV30-Pad30)") (class "Default")
      (node (ref "SV30") (pin "30") (pinfunction "30_30") (pintype "passive"))
    )
    (net (code "1281") (name "unconnected-(SV30-Pad31)") (class "Default")
      (node (ref "SV30") (pin "31") (pinfunction "31_31") (pintype "passive"))
    )
    (net (code "1282") (name "unconnected-(SV30-Pad32)") (class "Default")
      (node (ref "SV30") (pin "32") (pinfunction "32_32") (pintype "passive"))
    )
    (net (code "1283") (name "unconnected-(SV30-Pad33)") (class "Default")
      (node (ref "SV30") (pin "33") (pinfunction "33_33") (pintype "passive"))
    )
    (net (code "1284") (name "unconnected-(SV30-Pad34)") (class "Default")
      (node (ref "SV30") (pin "34") (pinfunction "34_34") (pintype "passive"))
    )
    (net (code "1285") (name "unconnected-(SV30-Pad35)") (class "Default")
      (node (ref "SV30") (pin "35") (pinfunction "35_35") (pintype "passive"))
    )
    (net (code "1286") (name "unconnected-(SV30-Pad36)") (class "Default")
      (node (ref "SV30") (pin "36") (pinfunction "36_36") (pintype "passive"))
    )
    (net (code "1287") (name "unconnected-(SV30-Pad37)") (class "Default")
      (node (ref "SV30") (pin "37") (pinfunction "37_37") (pintype "passive"))
    )
    (net (code "1288") (name "unconnected-(SV30-Pad38)") (class "Default")
      (node (ref "SV30") (pin "38") (pinfunction "38_38") (pintype "passive"))
    )
    (net (code "1289") (name "unconnected-(SV30-Pad39)") (class "Default")
      (node (ref "SV30") (pin "39") (pinfunction "39_39") (pintype "passive"))
    )
    (net (code "1290") (name "unconnected-(SV30-Pad40)") (class "Default")
      (node (ref "SV30") (pin "40") (pinfunction "40_40") (pintype "passive"))
    )
    (net (code "1291") (name "unconnected-(SV31-Pad1)") (class "Default")
      (node (ref "SV31") (pin "1") (pinfunction "1_1") (pintype "passive"))
    )
    (net (code "1292") (name "unconnected-(SV31-Pad2)") (class "Default")
      (node (ref "SV31") (pin "2") (pinfunction "2_2") (pintype "passive"))
    )
    (net (code "1293") (name "unconnected-(SV31-Pad3)") (class "Default")
      (node (ref "SV31") (pin "3") (pinfunction "3_3") (pintype "passive"))
    )
    (net (code "1294") (name "unconnected-(SV31-Pad4)") (class "Default")
      (node (ref "SV31") (pin "4") (pinfunction "4_4") (pintype "passive"))
    )
    (net (code "1295") (name "unconnected-(SV31-Pad5)") (class "Default")
      (node (ref "SV31") (pin "5") (pinfunction "5_5") (pintype "passive"))
    )
    (net (code "1296") (name "unconnected-(SV31-Pad6)") (class "Default")
      (node (ref "SV31") (pin "6") (pinfunction "6_6") (pintype "passive"))
    )
    (net (code "1297") (name "unconnected-(SV31-Pad7)") (class "Default")
      (node (ref "SV31") (pin "7") (pinfunction "7_7") (pintype "passive"))
    )
    (net (code "1298") (name "unconnected-(SV31-Pad8)") (class "Default")
      (node (ref "SV31") (pin "8") (pinfunction "8_8") (pintype "passive"))
    )
    (net (code "1299") (name "unconnected-(SV31-Pad9)") (class "Default")
      (node (ref "SV31") (pin "9") (pinfunction "9_9") (pintype "passive"))
    )
    (net (code "1300") (name "unconnected-(SV31-Pad10)") (class "Default")
      (node (ref "SV31") (pin "10") (pinfunction "10_10") (pintype "passive"))
    )
    (net (code "1301") (name "unconnected-(SV31-Pad11)") (class "Default")
      (node (ref "SV31") (pin "11") (pinfunction "11_11") (pintype "passive"))
    )
    (net (code "1302") (name "unconnected-(SV31-Pad12)") (class "Default")
      (node (ref "SV31") (pin "12") (pinfunction "12_12") (pintype "passive"))
    )
    (net (code "1303") (name "unconnected-(SV31-Pad13)") (class "Default")
      (node (ref "SV31") (pin "13") (pinfunction "13_13") (pintype "passive"))
    )
    (net (code "1304") (name "unconnected-(SV31-Pad14)") (class "Default")
      (node (ref "SV31") (pin "14") (pinfunction "14_14") (pintype "passive"))
    )
    (net (code "1305") (name "unconnected-(SV31-Pad15)") (class "Default")
      (node (ref "SV31") (pin "15") (pinfunction "15_15") (pintype "passive"))
    )
    (net (code "1306") (name "unconnected-(SV31-Pad16)") (class "Default")
      (node (ref "SV31") (pin "16") (pinfunction "16_16") (pintype "passive"))
    )
    (net (code "1307") (name "unconnected-(SV31-Pad17)") (class "Default")
      (node (ref "SV31") (pin "17") (pinfunction "17_17") (pintype "passive"))
    )
    (net (code "1308") (name "unconnected-(SV31-Pad18)") (class "Default")
      (node (ref "SV31") (pin "18") (pinfunction "18_18") (pintype "passive"))
    )
    (net (code "1309") (name "unconnected-(SV31-Pad19)") (class "Default")
      (node (ref "SV31") (pin "19") (pinfunction "19_19") (pintype "passive"))
    )
    (net (code "1310") (name "unconnected-(SV31-Pad20)") (class "Default")
      (node (ref "SV31") (pin "20") (pinfunction "20_20") (pintype "passive"))
    )
    (net (code "1311") (name "unconnected-(SV31-Pad21)") (class "Default")
      (node (ref "SV31") (pin "21") (pinfunction "21_21") (pintype "passive"))
    )
    (net (code "1312") (name "unconnected-(SV31-Pad22)") (class "Default")
      (node (ref "SV31") (pin "22") (pinfunction "22_22") (pintype "passive"))
    )
    (net (code "1313") (name "unconnected-(SV31-Pad23)") (class "Default")
      (node (ref "SV31") (pin "23") (pinfunction "23_23") (pintype "passive"))
    )
    (net (code "1314") (name "unconnected-(SV31-Pad24)") (class "Default")
      (node (ref "SV31") (pin "24") (pinfunction "24_24") (pintype "passive"))
    )
    (net (code "1315") (name "unconnected-(SV31-Pad25)") (class "Default")
      (node (ref "SV31") (pin "25") (pinfunction "25_25") (pintype "passive"))
    )
    (net (code "1316") (name "unconnected-(SV31-Pad26)") (class "Default")
      (node (ref "SV31") (pin "26") (pinfunction "26_26") (pintype "passive"))
    )
    (net (code "1317") (name "unconnected-(SV31-Pad27)") (class "Default")
      (node (ref "SV31") (pin "27") (pinfunction "27_27") (pintype "passive"))
    )
    (net (code "1318") (name "unconnected-(SV31-Pad28)") (class "Default")
      (node (ref "SV31") (pin "28") (pinfunction "28_28") (pintype "passive"))
    )
    (net (code "1319") (name "unconnected-(SV31-Pad29)") (class "Default")
      (node (ref "SV31") (pin "29") (pinfunction "29_29") (pintype "passive"))
    )
    (net (code "1320") (name "unconnected-(SV31-Pad30)") (class "Default")
      (node (ref "SV31") (pin "30") (pinfunction "30_30") (pintype "passive"))
    )
    (net (code "1321") (name "unconnected-(SV31-Pad31)") (class "Default")
      (node (ref "SV31") (pin "31") (pinfunction "31_31") (pintype "passive"))
    )
    (net (code "1322") (name "unconnected-(SV31-Pad32)") (class "Default")
      (node (ref "SV31") (pin "32") (pinfunction "32_32") (pintype "passive"))
    )
    (net (code "1323") (name "unconnected-(SV31-Pad33)") (class "Default")
      (node (ref "SV31") (pin "33") (pinfunction "33_33") (pintype "passive"))
    )
    (net (code "1324") (name "unconnected-(SV31-Pad34)") (class "Default")
      (node (ref "SV31") (pin "34") (pinfunction "34_34") (pintype "passive"))
    )
    (net (code "1325") (name "unconnected-(SV31-Pad35)") (class "Default")
      (node (ref "SV31") (pin "35") (pinfunction "35_35") (pintype "passive"))
    )
    (net (code "1326") (name "unconnected-(SV31-Pad36)") (class "Default")
      (node (ref "SV31") (pin "36") (pinfunction "36_36") (pintype "passive"))
    )
    (net (code "1327") (name "unconnected-(SV32-Pad1)") (class "Default")
      (node (ref "SV32") (pin "1") (pinfunction "1_1") (pintype "passive"))
    )
    (net (code "1328") (name "unconnected-(SV32-Pad2)") (class "Default")
      (node (ref "SV32") (pin "2") (pinfunction "2_2") (pintype "passive"))
    )
    (net (code "1329") (name "unconnected-(SV32-Pad3)") (class "Default")
      (node (ref "SV32") (pin "3") (pinfunction "3_3") (pintype "passive"))
    )
    (net (code "1330") (name "unconnected-(SV32-Pad4)") (class "Default")
      (node (ref "SV32") (pin "4") (pinfunction "4_4") (pintype "passive"))
    )
    (net (code "1331") (name "unconnected-(SV32-Pad5)") (class "Default")
      (node (ref "SV32") (pin "5") (pinfunction "5_5") (pintype "passive"))
    )
    (net (code "1332") (name "unconnected-(SV32-Pad6)") (class "Default")
      (node (ref "SV32") (pin "6") (pinfunction "6_6") (pintype "passive"))
    )
    (net (code "1333") (name "unconnected-(SV32-Pad7)") (class "Default")
      (node (ref "SV32") (pin "7") (pinfunction "7_7") (pintype "passive"))
    )
    (net (code "1334") (name "unconnected-(SV32-Pad8)") (class "Default")
      (node (ref "SV32") (pin "8") (pinfunction "8_8") (pintype "passive"))
    )
    (net (code "1335") (name "unconnected-(SV32-Pad9)") (class "Default")
      (node (ref "SV32") (pin "9") (pinfunction "9_9") (pintype "passive"))
    )
    (net (code "1336") (name "unconnected-(SV32-Pad10)") (class "Default")
      (node (ref "SV32") (pin "10") (pinfunction "10_10") (pintype "passive"))
    )
    (net (code "1337") (name "unconnected-(SV32-Pad11)") (class "Default")
      (node (ref "SV32") (pin "11") (pinfunction "11_11") (pintype "passive"))
    )
    (net (code "1338") (name "unconnected-(SV32-Pad12)") (class "Default")
      (node (ref "SV32") (pin "12") (pinfunction "12_12") (pintype "passive"))
    )
    (net (code "1339") (name "unconnected-(SV32-Pad13)") (class "Default")
      (node (ref "SV32") (pin "13") (pinfunction "13_13") (pintype "passive"))
    )
    (net (code "1340") (name "unconnected-(SV32-Pad14)") (class "Default")
      (node (ref "SV32") (pin "14") (pinfunction "14_14") (pintype "passive"))
    )
    (net (code "1341") (name "unconnected-(SV32-Pad15)") (class "Default")
      (node (ref "SV32") (pin "15") (pinfunction "15_15") (pintype "passive"))
    )
    (net (code "1342") (name "unconnected-(SV32-Pad16)") (class "Default")
      (node (ref "SV32") (pin "16") (pinfunction "16_16") (pintype "passive"))
    )
    (net (code "1343") (name "unconnected-(SV32-Pad17)") (class "Default")
      (node (ref "SV32") (pin "17") (pinfunction "17_17") (pintype "passive"))
    )
    (net (code "1344") (name "unconnected-(SV32-Pad18)") (class "Default")
      (node (ref "SV32") (pin "18") (pinfunction "18_18") (pintype "passive"))
    )
    (net (code "1345") (name "unconnected-(SV32-Pad19)") (class "Default")
      (node (ref "SV32") (pin "19") (pinfunction "19_19") (pintype "passive"))
    )
    (net (code "1346") (name "unconnected-(SV32-Pad20)") (class "Default")
      (node (ref "SV32") (pin "20") (pinfunction "20_20") (pintype "passive"))
    )
    (net (code "1347") (name "unconnected-(SV32-Pad21)") (class "Default")
      (node (ref "SV32") (pin "21") (pinfunction "21_21") (pintype "passive"))
    )
    (net (code "1348") (name "unconnected-(SV32-Pad22)") (class "Default")
      (node (ref "SV32") (pin "22") (pinfunction "22_22") (pintype "passive"))
    )
    (net (code "1349") (name "unconnected-(SV32-Pad23)") (class "Default")
      (node (ref "SV32") (pin "23") (pinfunction "23_23") (pintype "passive"))
    )
    (net (code "1350") (name "unconnected-(SV32-Pad24)") (class "Default")
      (node (ref "SV32") (pin "24") (pinfunction "24_24") (pintype "passive"))
    )
    (net (code "1351") (name "unconnected-(SV32-Pad25)") (class "Default")
      (node (ref "SV32") (pin "25") (pinfunction "25_25") (pintype "passive"))
    )
    (net (code "1352") (name "unconnected-(SV32-Pad26)") (class "Default")
      (node (ref "SV32") (pin "26") (pinfunction "26_26") (pintype "passive"))
    )
    (net (code "1353") (name "unconnected-(SV32-Pad27)") (class "Default")
      (node (ref "SV32") (pin "27") (pinfunction "27_27") (pintype "passive"))
    )
    (net (code "1354") (name "unconnected-(SV32-Pad28)") (class "Default")
      (node (ref "SV32") (pin "28") (pinfunction "28_28") (pintype "passive"))
    )
    (net (code "1355") (name "unconnected-(SV32-Pad29)") (class "Default")
      (node (ref "SV32") (pin "29") (pinfunction "29_29") (pintype "passive"))
    )
    (net (code "1356") (name "unconnected-(SV32-Pad30)") (class "Default")
      (node (ref "SV32") (pin "30") (pinfunction "30_30") (pintype "passive"))
    )
    (net (code "1357") (name "unconnected-(SV32-Pad31)") (class "Default")
      (node (ref "SV32") (pin "31") (pinfunction "31_31") (pintype "passive"))
    )
    (net (code "1358") (name "unconnected-(SV32-Pad32)") (class "Default")
      (node (ref "SV32") (pin "32") (pinfunction "32_32") (pintype "passive"))
    )
    (net (code "1359") (name "unconnected-(SV32-Pad33)") (class "Default")
      (node (ref "SV32") (pin "33") (pinfunction "33_33") (pintype "passive"))
    )
    (net (code "1360") (name "unconnected-(SV32-Pad34)") (class "Default")
      (node (ref "SV32") (pin "34") (pinfunction "34_34") (pintype "passive"))
    )
    (net (code "1361") (name "unconnected-(SV32-Pad35)") (class "Default")
      (node (ref "SV32") (pin "35") (pinfunction "35_35") (pintype "passive"))
    )
    (net (code "1362") (name "unconnected-(SV32-Pad36)") (class "Default")
      (node (ref "SV32") (pin "36") (pinfunction "36_36") (pintype "passive"))
    )
    (net (code "1363") (name "unconnected-(SV33-Pad1)") (class "Default")
      (node (ref "SV33") (pin "1") (pinfunction "1_1") (pintype "passive"))
    )
    (net (code "1364") (name "unconnected-(SV33-Pad2)") (class "Default")
      (node (ref "SV33") (pin "2") (pinfunction "2_2") (pintype "passive"))
    )
    (net (code "1365") (name "unconnected-(SV33-Pad3)") (class "Default")
      (node (ref "SV33") (pin "3") (pinfunction "3_3") (pintype "passive"))
    )
    (net (code "1366") (name "unconnected-(SV33-Pad4)") (class "Default")
      (node (ref "SV33") (pin "4") (pinfunction "4_4") (pintype "passive"))
    )
    (net (code "1367") (name "unconnected-(SV33-Pad5)") (class "Default")
      (node (ref "SV33") (pin "5") (pinfunction "5_5") (pintype "passive"))
    )
    (net (code "1368") (name "unconnected-(SV33-Pad6)") (class "Default")
      (node (ref "SV33") (pin "6") (pinfunction "6_6") (pintype "passive"))
    )
    (net (code "1369") (name "unconnected-(SV33-Pad7)") (class "Default")
      (node (ref "SV33") (pin "7") (pinfunction "7_7") (pintype "passive"))
    )
    (net (code "1370") (name "unconnected-(SV33-Pad8)") (class "Default")
      (node (ref "SV33") (pin "8") (pinfunction "8_8") (pintype "passive"))
    )
    (net (code "1371") (name "unconnected-(SV33-Pad9)") (class "Default")
      (node (ref "SV33") (pin "9") (pinfunction "9_9") (pintype "passive"))
    )
    (net (code "1372") (name "unconnected-(SV33-Pad10)") (class "Default")
      (node (ref "SV33") (pin "10") (pinfunction "10_10") (pintype "passive"))
    )
    (net (code "1373") (name "unconnected-(SV33-Pad11)") (class "Default")
      (node (ref "SV33") (pin "11") (pinfunction "11_11") (pintype "passive"))
    )
    (net (code "1374") (name "unconnected-(SV33-Pad12)") (class "Default")
      (node (ref "SV33") (pin "12") (pinfunction "12_12") (pintype "passive"))
    )
    (net (code "1375") (name "unconnected-(SV33-Pad13)") (class "Default")
      (node (ref "SV33") (pin "13") (pinfunction "13_13") (pintype "passive"))
    )
    (net (code "1376") (name "unconnected-(SV33-Pad14)") (class "Default")
      (node (ref "SV33") (pin "14") (pinfunction "14_14") (pintype "passive"))
    )
    (net (code "1377") (name "unconnected-(SV33-Pad15)") (class "Default")
      (node (ref "SV33") (pin "15") (pinfunction "15_15") (pintype "passive"))
    )
    (net (code "1378") (name "unconnected-(SV33-Pad16)") (class "Default")
      (node (ref "SV33") (pin "16") (pinfunction "16_16") (pintype "passive"))
    )
    (net (code "1379") (name "unconnected-(SV33-Pad17)") (class "Default")
      (node (ref "SV33") (pin "17") (pinfunction "17_17") (pintype "passive"))
    )
    (net (code "1380") (name "unconnected-(SV33-Pad18)") (class "Default")
      (node (ref "SV33") (pin "18") (pinfunction "18_18") (pintype "passive"))
    )
    (net (code "1381") (name "unconnected-(SV33-Pad19)") (class "Default")
      (node (ref "SV33") (pin "19") (pinfunction "19_19") (pintype "passive"))
    )
    (net (code "1382") (name "unconnected-(SV33-Pad20)") (class "Default")
      (node (ref "SV33") (pin "20") (pinfunction "20_20") (pintype "passive"))
    )
    (net (code "1383") (name "unconnected-(SV33-Pad21)") (class "Default")
      (node (ref "SV33") (pin "21") (pinfunction "21_21") (pintype "passive"))
    )
    (net (code "1384") (name "unconnected-(SV33-Pad22)") (class "Default")
      (node (ref "SV33") (pin "22") (pinfunction "22_22") (pintype "passive"))
    )
    (net (code "1385") (name "unconnected-(SV33-Pad23)") (class "Default")
      (node (ref "SV33") (pin "23") (pinfunction "23_23") (pintype "passive"))
    )
    (net (code "1386") (name "unconnected-(SV33-Pad24)") (class "Default")
      (node (ref "SV33") (pin "24") (pinfunction "24_24") (pintype "passive"))
    )
    (net (code "1387") (name "unconnected-(SV33-Pad25)") (class "Default")
      (node (ref "SV33") (pin "25") (pinfunction "25_25") (pintype "passive"))
    )
    (net (code "1388") (name "unconnected-(SV33-Pad26)") (class "Default")
      (node (ref "SV33") (pin "26") (pinfunction "26_26") (pintype "passive"))
    )
    (net (code "1389") (name "unconnected-(SV33-Pad27)") (class "Default")
      (node (ref "SV33") (pin "27") (pinfunction "27_27") (pintype "passive"))
    )
    (net (code "1390") (name "unconnected-(SV33-Pad28)") (class "Default")
      (node (ref "SV33") (pin "28") (pinfunction "28_28") (pintype "passive"))
    )
    (net (code "1391") (name "unconnected-(SV33-Pad29)") (class "Default")
      (node (ref "SV33") (pin "29") (pinfunction "29_29") (pintype "passive"))
    )
    (net (code "1392") (name "unconnected-(SV33-Pad30)") (class "Default")
      (node (ref "SV33") (pin "30") (pinfunction "30_30") (pintype "passive"))
    )
    (net (code "1393") (name "unconnected-(SV33-Pad31)") (class "Default")
      (node (ref "SV33") (pin "31") (pinfunction "31_31") (pintype "passive"))
    )
    (net (code "1394") (name "unconnected-(SV33-Pad32)") (class "Default")
      (node (ref "SV33") (pin "32") (pinfunction "32_32") (pintype "passive"))
    )
    (net (code "1395") (name "unconnected-(SV33-Pad33)") (class "Default")
      (node (ref "SV33") (pin "33") (pinfunction "33_33") (pintype "passive"))
    )
    (net (code "1396") (name "unconnected-(SV33-Pad34)") (class "Default")
      (node (ref "SV33") (pin "34") (pinfunction "34_34") (pintype "passive"))
    )
    (net (code "1397") (name "unconnected-(SV33-Pad35)") (class "Default")
      (node (ref "SV33") (pin "35") (pinfunction "35_35") (pintype "passive"))
    )
    (net (code "1398") (name "unconnected-(SV33-Pad36)") (class "Default")
      (node (ref "SV33") (pin "36") (pinfunction "36_36") (pintype "passive"))
    )
    (net (code "1399") (name "unconnected-(SV34-Pad1)") (class "Default")
      (node (ref "SV34") (pin "1") (pinfunction "1_1") (pintype "passive"))
    )
    (net (code "1400") (name "unconnected-(SV34-Pad2)") (class "Default")
      (node (ref "SV34") (pin "2") (pinfunction "2_2") (pintype "passive"))
    )
    (net (code "1401") (name "unconnected-(SV34-Pad3)") (class "Default")
      (node (ref "SV34") (pin "3") (pinfunction "3_3") (pintype "passive"))
    )
    (net (code "1402") (name "unconnected-(SV34-Pad4)") (class "Default")
      (node (ref "SV34") (pin "4") (pinfunction "4_4") (pintype "passive"))
    )
    (net (code "1403") (name "unconnected-(SV34-Pad5)") (class "Default")
      (node (ref "SV34") (pin "5") (pinfunction "5_5") (pintype "passive"))
    )
    (net (code "1404") (name "unconnected-(SV34-Pad6)") (class "Default")
      (node (ref "SV34") (pin "6") (pinfunction "6_6") (pintype "passive"))
    )
    (net (code "1405") (name "unconnected-(SV34-Pad7)") (class "Default")
      (node (ref "SV34") (pin "7") (pinfunction "7_7") (pintype "passive"))
    )
    (net (code "1406") (name "unconnected-(SV34-Pad8)") (class "Default")
      (node (ref "SV34") (pin "8") (pinfunction "8_8") (pintype "passive"))
    )
    (net (code "1407") (name "unconnected-(SV34-Pad9)") (class "Default")
      (node (ref "SV34") (pin "9") (pinfunction "9_9") (pintype "passive"))
    )
    (net (code "1408") (name "unconnected-(SV34-Pad10)") (class "Default")
      (node (ref "SV34") (pin "10") (pinfunction "10_10") (pintype "passive"))
    )
    (net (code "1409") (name "unconnected-(SV34-Pad11)") (class "Default")
      (node (ref "SV34") (pin "11") (pinfunction "11_11") (pintype "passive"))
    )
    (net (code "1410") (name "unconnected-(SV34-Pad12)") (class "Default")
      (node (ref "SV34") (pin "12") (pinfunction "12_12") (pintype "passive"))
    )
    (net (code "1411") (name "unconnected-(SV34-Pad13)") (class "Default")
      (node (ref "SV34") (pin "13") (pinfunction "13_13") (pintype "passive"))
    )
    (net (code "1412") (name "unconnected-(SV34-Pad14)") (class "Default")
      (node (ref "SV34") (pin "14") (pinfunction "14_14") (pintype "passive"))
    )
    (net (code "1413") (name "unconnected-(SV34-Pad15)") (class "Default")
      (node (ref "SV34") (pin "15") (pinfunction "15_15") (pintype "passive"))
    )
    (net (code "1414") (name "unconnected-(SV34-Pad16)") (class "Default")
      (node (ref "SV34") (pin "16") (pinfunction "16_16") (pintype "passive"))
    )
    (net (code "1415") (name "unconnected-(SV34-Pad17)") (class "Default")
      (node (ref "SV34") (pin "17") (pinfunction "17_17") (pintype "passive"))
    )
    (net (code "1416") (name "unconnected-(SV34-Pad18)") (class "Default")
      (node (ref "SV34") (pin "18") (pinfunction "18_18") (pintype "passive"))
    )
    (net (code "1417") (name "unconnected-(SV34-Pad19)") (class "Default")
      (node (ref "SV34") (pin "19") (pinfunction "19_19") (pintype "passive"))
    )
    (net (code "1418") (name "unconnected-(SV34-Pad20)") (class "Default")
      (node (ref "SV34") (pin "20") (pinfunction "20_20") (pintype "passive"))
    )
    (net (code "1419") (name "unconnected-(SV34-Pad21)") (class "Default")
      (node (ref "SV34") (pin "21") (pinfunction "21_21") (pintype "passive"))
    )
    (net (code "1420") (name "unconnected-(SV34-Pad22)") (class "Default")
      (node (ref "SV34") (pin "22") (pinfunction "22_22") (pintype "passive"))
    )
    (net (code "1421") (name "unconnected-(SV34-Pad23)") (class "Default")
      (node (ref "SV34") (pin "23") (pinfunction "23_23") (pintype "passive"))
    )
    (net (code "1422") (name "unconnected-(SV34-Pad24)") (class "Default")
      (node (ref "SV34") (pin "24") (pinfunction "24_24") (pintype "passive"))
    )
    (net (code "1423") (name "unconnected-(SV34-Pad25)") (class "Default")
      (node (ref "SV34") (pin "25") (pinfunction "25_25") (pintype "passive"))
    )
    (net (code "1424") (name "unconnected-(SV34-Pad26)") (class "Default")
      (node (ref "SV34") (pin "26") (pinfunction "26_26") (pintype "passive"))
    )
    (net (code "1425") (name "unconnected-(SV34-Pad27)") (class "Default")
      (node (ref "SV34") (pin "27") (pinfunction "27_27") (pintype "passive"))
    )
    (net (code "1426") (name "unconnected-(SV34-Pad28)") (class "Default")
      (node (ref "SV34") (pin "28") (pinfunction "28_28") (pintype "passive"))
    )
    (net (code "1427") (name "unconnected-(SV34-Pad29)") (class "Default")
      (node (ref "SV34") (pin "29") (pinfunction "29_29") (pintype "passive"))
    )
    (net (code "1428") (name "unconnected-(SV34-Pad30)") (class "Default")
      (node (ref "SV34") (pin "30") (pinfunction "30_30") (pintype "passive"))
    )
    (net (code "1429") (name "unconnected-(SV34-Pad31)") (class "Default")
      (node (ref "SV34") (pin "31") (pinfunction "31_31") (pintype "passive"))
    )
    (net (code "1430") (name "unconnected-(SV34-Pad32)") (class "Default")
      (node (ref "SV34") (pin "32") (pinfunction "32_32") (pintype "passive"))
    )
    (net (code "1431") (name "unconnected-(SV34-Pad33)") (class "Default")
      (node (ref "SV34") (pin "33") (pinfunction "33_33") (pintype "passive"))
    )
    (net (code "1432") (name "unconnected-(SV34-Pad34)") (class "Default")
      (node (ref "SV34") (pin "34") (pinfunction "34_34") (pintype "passive"))
    )
    (net (code "1433") (name "unconnected-(SV34-Pad35)") (class "Default")
      (node (ref "SV34") (pin "35") (pinfunction "35_35") (pintype "passive"))
    )
    (net (code "1434") (name "unconnected-(SV34-Pad36)") (class "Default")
      (node (ref "SV34") (pin "36") (pinfunction "36_36") (pintype "passive"))
    )
    (net (code "1435") (name "unconnected-(SV35-Pad1)") (class "Default")
      (node (ref "SV35") (pin "1") (pinfunction "1_1") (pintype "passive"))
    )
    (net (code "1436") (name "unconnected-(SV35-Pad2)") (class "Default")
      (node (ref "SV35") (pin "2") (pinfunction "2_2") (pintype "passive"))
    )
    (net (code "1437") (name "unconnected-(SV35-Pad3)") (class "Default")
      (node (ref "SV35") (pin "3") (pinfunction "3_3") (pintype "passive"))
    )
    (net (code "1438") (name "unconnected-(SV35-Pad4)") (class "Default")
      (node (ref "SV35") (pin "4") (pinfunction "4_4") (pintype "passive"))
    )
    (net (code "1439") (name "unconnected-(SV35-Pad5)") (class "Default")
      (node (ref "SV35") (pin "5") (pinfunction "5_5") (pintype "passive"))
    )
    (net (code "1440") (name "unconnected-(SV35-Pad6)") (class "Default")
      (node (ref "SV35") (pin "6") (pinfunction "6_6") (pintype "passive"))
    )
    (net (code "1441") (name "unconnected-(SV35-Pad7)") (class "Default")
      (node (ref "SV35") (pin "7") (pinfunction "7_7") (pintype "passive"))
    )
    (net (code "1442") (name "unconnected-(SV35-Pad8)") (class "Default")
      (node (ref "SV35") (pin "8") (pinfunction "8_8") (pintype "passive"))
    )
    (net (code "1443") (name "unconnected-(SV35-Pad9)") (class "Default")
      (node (ref "SV35") (pin "9") (pinfunction "9_9") (pintype "passive"))
    )
    (net (code "1444") (name "unconnected-(SV35-Pad10)") (class "Default")
      (node (ref "SV35") (pin "10") (pinfunction "10_10") (pintype "passive"))
    )
    (net (code "1445") (name "unconnected-(SV35-Pad11)") (class "Default")
      (node (ref "SV35") (pin "11") (pinfunction "11_11") (pintype "passive"))
    )
    (net (code "1446") (name "unconnected-(SV35-Pad12)") (class "Default")
      (node (ref "SV35") (pin "12") (pinfunction "12_12") (pintype "passive"))
    )
    (net (code "1447") (name "unconnected-(SV35-Pad13)") (class "Default")
      (node (ref "SV35") (pin "13") (pinfunction "13_13") (pintype "passive"))
    )
    (net (code "1448") (name "unconnected-(SV35-Pad14)") (class "Default")
      (node (ref "SV35") (pin "14") (pinfunction "14_14") (pintype "passive"))
    )
    (net (code "1449") (name "unconnected-(SV35-Pad15)") (class "Default")
      (node (ref "SV35") (pin "15") (pinfunction "15_15") (pintype "passive"))
    )
    (net (code "1450") (name "unconnected-(SV35-Pad16)") (class "Default")
      (node (ref "SV35") (pin "16") (pinfunction "16_16") (pintype "passive"))
    )
    (net (code "1451") (name "unconnected-(SV35-Pad17)") (class "Default")
      (node (ref "SV35") (pin "17") (pinfunction "17_17") (pintype "passive"))
    )
    (net (code "1452") (name "unconnected-(SV35-Pad18)") (class "Default")
      (node (ref "SV35") (pin "18") (pinfunction "18_18") (pintype "passive"))
    )
    (net (code "1453") (name "unconnected-(SV35-Pad19)") (class "Default")
      (node (ref "SV35") (pin "19") (pinfunction "19_19") (pintype "passive"))
    )
    (net (code "1454") (name "unconnected-(SV35-Pad20)") (class "Default")
      (node (ref "SV35") (pin "20") (pinfunction "20_20") (pintype "passive"))
    )
    (net (code "1455") (name "unconnected-(SV35-Pad21)") (class "Default")
      (node (ref "SV35") (pin "21") (pinfunction "21_21") (pintype "passive"))
    )
    (net (code "1456") (name "unconnected-(SV35-Pad22)") (class "Default")
      (node (ref "SV35") (pin "22") (pinfunction "22_22") (pintype "passive"))
    )
    (net (code "1457") (name "unconnected-(SV35-Pad23)") (class "Default")
      (node (ref "SV35") (pin "23") (pinfunction "23_23") (pintype "passive"))
    )
    (net (code "1458") (name "unconnected-(SV35-Pad24)") (class "Default")
      (node (ref "SV35") (pin "24") (pinfunction "24_24") (pintype "passive"))
    )
    (net (code "1459") (name "unconnected-(SV35-Pad25)") (class "Default")
      (node (ref "SV35") (pin "25") (pinfunction "25_25") (pintype "passive"))
    )
    (net (code "1460") (name "unconnected-(SV35-Pad26)") (class "Default")
      (node (ref "SV35") (pin "26") (pinfunction "26_26") (pintype "passive"))
    )
    (net (code "1461") (name "unconnected-(SV35-Pad27)") (class "Default")
      (node (ref "SV35") (pin "27") (pinfunction "27_27") (pintype "passive"))
    )
    (net (code "1462") (name "unconnected-(SV35-Pad28)") (class "Default")
      (node (ref "SV35") (pin "28") (pinfunction "28_28") (pintype "passive"))
    )
    (net (code "1463") (name "unconnected-(SV35-Pad29)") (class "Default")
      (node (ref "SV35") (pin "29") (pinfunction "29_29") (pintype "passive"))
    )
    (net (code "1464") (name "unconnected-(SV35-Pad30)") (class "Default")
      (node (ref "SV35") (pin "30") (pinfunction "30_30") (pintype "passive"))
    )
    (net (code "1465") (name "unconnected-(SV35-Pad31)") (class "Default")
      (node (ref "SV35") (pin "31") (pinfunction "31_31") (pintype "passive"))
    )
    (net (code "1466") (name "unconnected-(SV35-Pad32)") (class "Default")
      (node (ref "SV35") (pin "32") (pinfunction "32_32") (pintype "passive"))
    )
    (net (code "1467") (name "unconnected-(SV35-Pad33)") (class "Default")
      (node (ref "SV35") (pin "33") (pinfunction "33_33") (pintype "passive"))
    )
    (net (code "1468") (name "unconnected-(SV35-Pad34)") (class "Default")
      (node (ref "SV35") (pin "34") (pinfunction "34_34") (pintype "passive"))
    )
    (net (code "1469") (name "unconnected-(SV35-Pad35)") (class "Default")
      (node (ref "SV35") (pin "35") (pinfunction "35_35") (pintype "passive"))
    )
    (net (code "1470") (name "unconnected-(SV35-Pad36)") (class "Default")
      (node (ref "SV35") (pin "36") (pinfunction "36_36") (pintype "passive"))
    )
    (net (code "1471") (name "unconnected-(SV35-Pad37)") (class "Default")
      (node (ref "SV35") (pin "37") (pinfunction "37_37") (pintype "passive"))
    )
    (net (code "1472") (name "unconnected-(SV35-Pad38)") (class "Default")
      (node (ref "SV35") (pin "38") (pinfunction "38_38") (pintype "passive"))
    )
    (net (code "1473") (name "unconnected-(SV35-Pad39)") (class "Default")
      (node (ref "SV35") (pin "39") (pinfunction "39_39") (pintype "passive"))
    )
    (net (code "1474") (name "unconnected-(SV35-Pad40)") (class "Default")
      (node (ref "SV35") (pin "40") (pinfunction "40_40") (pintype "passive"))
    )
    (net (code "1475") (name "unconnected-(SV36-Pad1)") (class "Default")
      (node (ref "SV36") (pin "1") (pinfunction "1_1") (pintype "passive"))
    )
    (net (code "1476") (name "unconnected-(SV36-Pad2)") (class "Default")
      (node (ref "SV36") (pin "2") (pinfunction "2_2") (pintype "passive"))
    )
    (net (code "1477") (name "unconnected-(SV36-Pad3)") (class "Default")
      (node (ref "SV36") (pin "3") (pinfunction "3_3") (pintype "passive"))
    )
    (net (code "1478") (name "unconnected-(SV36-Pad4)") (class "Default")
      (node (ref "SV36") (pin "4") (pinfunction "4_4") (pintype "passive"))
    )
    (net (code "1479") (name "unconnected-(SV36-Pad5)") (class "Default")
      (node (ref "SV36") (pin "5") (pinfunction "5_5") (pintype "passive"))
    )
    (net (code "1480") (name "unconnected-(SV36-Pad6)") (class "Default")
      (node (ref "SV36") (pin "6") (pinfunction "6_6") (pintype "passive"))
    )
    (net (code "1481") (name "unconnected-(SV36-Pad7)") (class "Default")
      (node (ref "SV36") (pin "7") (pinfunction "7_7") (pintype "passive"))
    )
    (net (code "1482") (name "unconnected-(SV36-Pad8)") (class "Default")
      (node (ref "SV36") (pin "8") (pinfunction "8_8") (pintype "passive"))
    )
    (net (code "1483") (name "unconnected-(SV36-Pad9)") (class "Default")
      (node (ref "SV36") (pin "9") (pinfunction "9_9") (pintype "passive"))
    )
    (net (code "1484") (name "unconnected-(SV36-Pad10)") (class "Default")
      (node (ref "SV36") (pin "10") (pinfunction "10_10") (pintype "passive"))
    )
    (net (code "1485") (name "unconnected-(SV36-Pad11)") (class "Default")
      (node (ref "SV36") (pin "11") (pinfunction "11_11") (pintype "passive"))
    )
    (net (code "1486") (name "unconnected-(SV36-Pad12)") (class "Default")
      (node (ref "SV36") (pin "12") (pinfunction "12_12") (pintype "passive"))
    )
    (net (code "1487") (name "unconnected-(SV36-Pad13)") (class "Default")
      (node (ref "SV36") (pin "13") (pinfunction "13_13") (pintype "passive"))
    )
    (net (code "1488") (name "unconnected-(SV36-Pad14)") (class "Default")
      (node (ref "SV36") (pin "14") (pinfunction "14_14") (pintype "passive"))
    )
    (net (code "1489") (name "unconnected-(SV36-Pad15)") (class "Default")
      (node (ref "SV36") (pin "15") (pinfunction "15_15") (pintype "passive"))
    )
    (net (code "1490") (name "unconnected-(SV36-Pad16)") (class "Default")
      (node (ref "SV36") (pin "16") (pinfunction "16_16") (pintype "passive"))
    )
    (net (code "1491") (name "unconnected-(SV36-Pad17)") (class "Default")
      (node (ref "SV36") (pin "17") (pinfunction "17_17") (pintype "passive"))
    )
    (net (code "1492") (name "unconnected-(SV36-Pad18)") (class "Default")
      (node (ref "SV36") (pin "18") (pinfunction "18_18") (pintype "passive"))
    )
    (net (code "1493") (name "unconnected-(SV36-Pad19)") (class "Default")
      (node (ref "SV36") (pin "19") (pinfunction "19_19") (pintype "passive"))
    )
    (net (code "1494") (name "unconnected-(SV36-Pad20)") (class "Default")
      (node (ref "SV36") (pin "20") (pinfunction "20_20") (pintype "passive"))
    )
    (net (code "1495") (name "unconnected-(SV36-Pad21)") (class "Default")
      (node (ref "SV36") (pin "21") (pinfunction "21_21") (pintype "passive"))
    )
    (net (code "1496") (name "unconnected-(SV36-Pad22)") (class "Default")
      (node (ref "SV36") (pin "22") (pinfunction "22_22") (pintype "passive"))
    )
    (net (code "1497") (name "unconnected-(SV36-Pad23)") (class "Default")
      (node (ref "SV36") (pin "23") (pinfunction "23_23") (pintype "passive"))
    )
    (net (code "1498") (name "unconnected-(SV36-Pad24)") (class "Default")
      (node (ref "SV36") (pin "24") (pinfunction "24_24") (pintype "passive"))
    )
    (net (code "1499") (name "unconnected-(SV36-Pad25)") (class "Default")
      (node (ref "SV36") (pin "25") (pinfunction "25_25") (pintype "passive"))
    )
    (net (code "1500") (name "unconnected-(SV36-Pad26)") (class "Default")
      (node (ref "SV36") (pin "26") (pinfunction "26_26") (pintype "passive"))
    )
    (net (code "1501") (name "unconnected-(SV36-Pad27)") (class "Default")
      (node (ref "SV36") (pin "27") (pinfunction "27_27") (pintype "passive"))
    )
    (net (code "1502") (name "unconnected-(SV36-Pad28)") (class "Default")
      (node (ref "SV36") (pin "28") (pinfunction "28_28") (pintype "passive"))
    )
    (net (code "1503") (name "unconnected-(SV36-Pad29)") (class "Default")
      (node (ref "SV36") (pin "29") (pinfunction "29_29") (pintype "passive"))
    )
    (net (code "1504") (name "unconnected-(SV36-Pad30)") (class "Default")
      (node (ref "SV36") (pin "30") (pinfunction "30_30") (pintype "passive"))
    )
    (net (code "1505") (name "unconnected-(SV36-Pad31)") (class "Default")
      (node (ref "SV36") (pin "31") (pinfunction "31_31") (pintype "passive"))
    )
    (net (code "1506") (name "unconnected-(SV36-Pad32)") (class "Default")
      (node (ref "SV36") (pin "32") (pinfunction "32_32") (pintype "passive"))
    )
    (net (code "1507") (name "unconnected-(SV36-Pad33)") (class "Default")
      (node (ref "SV36") (pin "33") (pinfunction "33_33") (pintype "passive"))
    )
    (net (code "1508") (name "unconnected-(SV36-Pad34)") (class "Default")
      (node (ref "SV36") (pin "34") (pinfunction "34_34") (pintype "passive"))
    )
    (net (code "1509") (name "unconnected-(SV36-Pad35)") (class "Default")
      (node (ref "SV36") (pin "35") (pinfunction "35_35") (pintype "passive"))
    )
    (net (code "1510") (name "unconnected-(SV36-Pad36)") (class "Default")
      (node (ref "SV36") (pin "36") (pinfunction "36_36") (pintype "passive"))
    )
    (net (code "1511") (name "unconnected-(SV36-Pad37)") (class "Default")
      (node (ref "SV36") (pin "37") (pinfunction "37_37") (pintype "passive"))
    )
    (net (code "1512") (name "unconnected-(SV36-Pad38)") (class "Default")
      (node (ref "SV36") (pin "38") (pinfunction "38_38") (pintype "passive"))
    )
    (net (code "1513") (name "unconnected-(SV36-Pad39)") (class "Default")
      (node (ref "SV36") (pin "39") (pinfunction "39_39") (pintype "passive"))
    )
    (net (code "1514") (name "unconnected-(SV36-Pad40)") (class "Default")
      (node (ref "SV36") (pin "40") (pinfunction "40_40") (pintype "passive"))
    )
    (net (code "1515") (name "unconnected-(SV37-Pad1)") (class "Default")
      (node (ref "SV37") (pin "1") (pinfunction "1_1") (pintype "passive"))
    )
    (net (code "1516") (name "unconnected-(SV37-Pad2)") (class "Default")
      (node (ref "SV37") (pin "2") (pinfunction "2_2") (pintype "passive"))
    )
    (net (code "1517") (name "unconnected-(SV37-Pad3)") (class "Default")
      (node (ref "SV37") (pin "3") (pinfunction "3_3") (pintype "passive"))
    )
    (net (code "1518") (name "unconnected-(SV37-Pad4)") (class "Default")
      (node (ref "SV37") (pin "4") (pinfunction "4_4") (pintype "passive"))
    )
    (net (code "1519") (name "unconnected-(SV37-Pad5)") (class "Default")
      (node (ref "SV37") (pin "5") (pinfunction "5_5") (pintype "passive"))
    )
    (net (code "1520") (name "unconnected-(SV37-Pad6)") (class "Default")
      (node (ref "SV37") (pin "6") (pinfunction "6_6") (pintype "passive"))
    )
    (net (code "1521") (name "unconnected-(SV37-Pad7)") (class "Default")
      (node (ref "SV37") (pin "7") (pinfunction "7_7") (pintype "passive"))
    )
    (net (code "1522") (name "unconnected-(SV37-Pad8)") (class "Default")
      (node (ref "SV37") (pin "8") (pinfunction "8_8") (pintype "passive"))
    )
    (net (code "1523") (name "unconnected-(SV37-Pad9)") (class "Default")
      (node (ref "SV37") (pin "9") (pinfunction "9_9") (pintype "passive"))
    )
    (net (code "1524") (name "unconnected-(SV37-Pad10)") (class "Default")
      (node (ref "SV37") (pin "10") (pinfunction "10_10") (pintype "passive"))
    )
    (net (code "1525") (name "unconnected-(SV37-Pad11)") (class "Default")
      (node (ref "SV37") (pin "11") (pinfunction "11_11") (pintype "passive"))
    )
    (net (code "1526") (name "unconnected-(SV37-Pad12)") (class "Default")
      (node (ref "SV37") (pin "12") (pinfunction "12_12") (pintype "passive"))
    )
    (net (code "1527") (name "unconnected-(SV37-Pad13)") (class "Default")
      (node (ref "SV37") (pin "13") (pinfunction "13_13") (pintype "passive"))
    )
    (net (code "1528") (name "unconnected-(SV37-Pad14)") (class "Default")
      (node (ref "SV37") (pin "14") (pinfunction "14_14") (pintype "passive"))
    )
    (net (code "1529") (name "unconnected-(SV37-Pad15)") (class "Default")
      (node (ref "SV37") (pin "15") (pinfunction "15_15") (pintype "passive"))
    )
    (net (code "1530") (name "unconnected-(SV37-Pad16)") (class "Default")
      (node (ref "SV37") (pin "16") (pinfunction "16_16") (pintype "passive"))
    )
    (net (code "1531") (name "unconnected-(SV37-Pad17)") (class "Default")
      (node (ref "SV37") (pin "17") (pinfunction "17_17") (pintype "passive"))
    )
    (net (code "1532") (name "unconnected-(SV37-Pad18)") (class "Default")
      (node (ref "SV37") (pin "18") (pinfunction "18_18") (pintype "passive"))
    )
    (net (code "1533") (name "unconnected-(SV37-Pad19)") (class "Default")
      (node (ref "SV37") (pin "19") (pinfunction "19_19") (pintype "passive"))
    )
    (net (code "1534") (name "unconnected-(SV37-Pad20)") (class "Default")
      (node (ref "SV37") (pin "20") (pinfunction "20_20") (pintype "passive"))
    )
    (net (code "1535") (name "unconnected-(SV37-Pad21)") (class "Default")
      (node (ref "SV37") (pin "21") (pinfunction "21_21") (pintype "passive"))
    )
    (net (code "1536") (name "unconnected-(SV37-Pad22)") (class "Default")
      (node (ref "SV37") (pin "22") (pinfunction "22_22") (pintype "passive"))
    )
    (net (code "1537") (name "unconnected-(SV37-Pad23)") (class "Default")
      (node (ref "SV37") (pin "23") (pinfunction "23_23") (pintype "passive"))
    )
    (net (code "1538") (name "unconnected-(SV37-Pad24)") (class "Default")
      (node (ref "SV37") (pin "24") (pinfunction "24_24") (pintype "passive"))
    )
    (net (code "1539") (name "unconnected-(SV37-Pad25)") (class "Default")
      (node (ref "SV37") (pin "25") (pinfunction "25_25") (pintype "passive"))
    )
    (net (code "1540") (name "unconnected-(SV37-Pad26)") (class "Default")
      (node (ref "SV37") (pin "26") (pinfunction "26_26") (pintype "passive"))
    )
    (net (code "1541") (name "unconnected-(SV37-Pad27)") (class "Default")
      (node (ref "SV37") (pin "27") (pinfunction "27_27") (pintype "passive"))
    )
    (net (code "1542") (name "unconnected-(SV37-Pad28)") (class "Default")
      (node (ref "SV37") (pin "28") (pinfunction "28_28") (pintype "passive"))
    )
    (net (code "1543") (name "unconnected-(SV37-Pad29)") (class "Default")
      (node (ref "SV37") (pin "29") (pinfunction "29_29") (pintype "passive"))
    )
    (net (code "1544") (name "unconnected-(SV37-Pad30)") (class "Default")
      (node (ref "SV37") (pin "30") (pinfunction "30_30") (pintype "passive"))
    )
    (net (code "1545") (name "unconnected-(SV37-Pad31)") (class "Default")
      (node (ref "SV37") (pin "31") (pinfunction "31_31") (pintype "passive"))
    )
    (net (code "1546") (name "unconnected-(SV37-Pad32)") (class "Default")
      (node (ref "SV37") (pin "32") (pinfunction "32_32") (pintype "passive"))
    )
    (net (code "1547") (name "unconnected-(SV37-Pad33)") (class "Default")
      (node (ref "SV37") (pin "33") (pinfunction "33_33") (pintype "passive"))
    )
    (net (code "1548") (name "unconnected-(SV37-Pad34)") (class "Default")
      (node (ref "SV37") (pin "34") (pinfunction "34_34") (pintype "passive"))
    )
    (net (code "1549") (name "unconnected-(SV37-Pad35)") (class "Default")
      (node (ref "SV37") (pin "35") (pinfunction "35_35") (pintype "passive"))
    )
    (net (code "1550") (name "unconnected-(SV37-Pad36)") (class "Default")
      (node (ref "SV37") (pin "36") (pinfunction "36_36") (pintype "passive"))
    )
    (net (code "1551") (name "unconnected-(SV37-Pad37)") (class "Default")
      (node (ref "SV37") (pin "37") (pinfunction "37_37") (pintype "passive"))
    )
    (net (code "1552") (name "unconnected-(SV37-Pad38)") (class "Default")
      (node (ref "SV37") (pin "38") (pinfunction "38_38") (pintype "passive"))
    )
    (net (code "1553") (name "unconnected-(SV37-Pad39)") (class "Default")
      (node (ref "SV37") (pin "39") (pinfunction "39_39") (pintype "passive"))
    )
    (net (code "1554") (name "unconnected-(SV37-Pad40)") (class "Default")
      (node (ref "SV37") (pin "40") (pinfunction "40_40") (pintype "passive"))
    )
    (net (code "1555") (name "unconnected-(SV38-Pad1)") (class "Default")
      (node (ref "SV38") (pin "1") (pinfunction "1_1") (pintype "passive"))
    )
    (net (code "1556") (name "unconnected-(SV38-Pad2)") (class "Default")
      (node (ref "SV38") (pin "2") (pinfunction "2_2") (pintype "passive"))
    )
    (net (code "1557") (name "unconnected-(SV38-Pad3)") (class "Default")
      (node (ref "SV38") (pin "3") (pinfunction "3_3") (pintype "passive"))
    )
    (net (code "1558") (name "unconnected-(SV38-Pad4)") (class "Default")
      (node (ref "SV38") (pin "4") (pinfunction "4_4") (pintype "passive"))
    )
    (net (code "1559") (name "unconnected-(SV38-Pad5)") (class "Default")
      (node (ref "SV38") (pin "5") (pinfunction "5_5") (pintype "passive"))
    )
    (net (code "1560") (name "unconnected-(SV38-Pad6)") (class "Default")
      (node (ref "SV38") (pin "6") (pinfunction "6_6") (pintype "passive"))
    )
    (net (code "1561") (name "unconnected-(SV38-Pad7)") (class "Default")
      (node (ref "SV38") (pin "7") (pinfunction "7_7") (pintype "passive"))
    )
    (net (code "1562") (name "unconnected-(SV38-Pad8)") (class "Default")
      (node (ref "SV38") (pin "8") (pinfunction "8_8") (pintype "passive"))
    )
    (net (code "1563") (name "unconnected-(SV38-Pad9)") (class "Default")
      (node (ref "SV38") (pin "9") (pinfunction "9_9") (pintype "passive"))
    )
    (net (code "1564") (name "unconnected-(SV38-Pad10)") (class "Default")
      (node (ref "SV38") (pin "10") (pinfunction "10_10") (pintype "passive"))
    )
    (net (code "1565") (name "unconnected-(SV38-Pad11)") (class "Default")
      (node (ref "SV38") (pin "11") (pinfunction "11_11") (pintype "passive"))
    )
    (net (code "1566") (name "unconnected-(SV38-Pad12)") (class "Default")
      (node (ref "SV38") (pin "12") (pinfunction "12_12") (pintype "passive"))
    )
    (net (code "1567") (name "unconnected-(SV38-Pad13)") (class "Default")
      (node (ref "SV38") (pin "13") (pinfunction "13_13") (pintype "passive"))
    )
    (net (code "1568") (name "unconnected-(SV38-Pad14)") (class "Default")
      (node (ref "SV38") (pin "14") (pinfunction "14_14") (pintype "passive"))
    )
    (net (code "1569") (name "unconnected-(SV38-Pad15)") (class "Default")
      (node (ref "SV38") (pin "15") (pinfunction "15_15") (pintype "passive"))
    )
    (net (code "1570") (name "unconnected-(SV38-Pad16)") (class "Default")
      (node (ref "SV38") (pin "16") (pinfunction "16_16") (pintype "passive"))
    )
    (net (code "1571") (name "unconnected-(SV38-Pad17)") (class "Default")
      (node (ref "SV38") (pin "17") (pinfunction "17_17") (pintype "passive"))
    )
    (net (code "1572") (name "unconnected-(SV38-Pad18)") (class "Default")
      (node (ref "SV38") (pin "18") (pinfunction "18_18") (pintype "passive"))
    )
    (net (code "1573") (name "unconnected-(SV38-Pad19)") (class "Default")
      (node (ref "SV38") (pin "19") (pinfunction "19_19") (pintype "passive"))
    )
    (net (code "1574") (name "unconnected-(SV38-Pad20)") (class "Default")
      (node (ref "SV38") (pin "20") (pinfunction "20_20") (pintype "passive"))
    )
    (net (code "1575") (name "unconnected-(SV38-Pad21)") (class "Default")
      (node (ref "SV38") (pin "21") (pinfunction "21_21") (pintype "passive"))
    )
    (net (code "1576") (name "unconnected-(SV38-Pad22)") (class "Default")
      (node (ref "SV38") (pin "22") (pinfunction "22_22") (pintype "passive"))
    )
    (net (code "1577") (name "unconnected-(SV38-Pad23)") (class "Default")
      (node (ref "SV38") (pin "23") (pinfunction "23_23") (pintype "passive"))
    )
    (net (code "1578") (name "unconnected-(SV38-Pad24)") (class "Default")
      (node (ref "SV38") (pin "24") (pinfunction "24_24") (pintype "passive"))
    )
    (net (code "1579") (name "unconnected-(SV38-Pad25)") (class "Default")
      (node (ref "SV38") (pin "25") (pinfunction "25_25") (pintype "passive"))
    )
    (net (code "1580") (name "unconnected-(SV38-Pad26)") (class "Default")
      (node (ref "SV38") (pin "26") (pinfunction "26_26") (pintype "passive"))
    )
    (net (code "1581") (name "unconnected-(SV38-Pad27)") (class "Default")
      (node (ref "SV38") (pin "27") (pinfunction "27_27") (pintype "passive"))
    )
    (net (code "1582") (name "unconnected-(SV38-Pad28)") (class "Default")
      (node (ref "SV38") (pin "28") (pinfunction "28_28") (pintype "passive"))
    )
    (net (code "1583") (name "unconnected-(SV38-Pad29)") (class "Default")
      (node (ref "SV38") (pin "29") (pinfunction "29_29") (pintype "passive"))
    )
    (net (code "1584") (name "unconnected-(SV38-Pad30)") (class "Default")
      (node (ref "SV38") (pin "30") (pinfunction "30_30") (pintype "passive"))
    )
    (net (code "1585") (name "unconnected-(SV38-Pad31)") (class "Default")
      (node (ref "SV38") (pin "31") (pinfunction "31_31") (pintype "passive"))
    )
    (net (code "1586") (name "unconnected-(SV38-Pad32)") (class "Default")
      (node (ref "SV38") (pin "32") (pinfunction "32_32") (pintype "passive"))
    )
    (net (code "1587") (name "unconnected-(SV38-Pad33)") (class "Default")
      (node (ref "SV38") (pin "33") (pinfunction "33_33") (pintype "passive"))
    )
    (net (code "1588") (name "unconnected-(SV38-Pad34)") (class "Default")
      (node (ref "SV38") (pin "34") (pinfunction "34_34") (pintype "passive"))
    )
    (net (code "1589") (name "unconnected-(SV38-Pad35)") (class "Default")
      (node (ref "SV38") (pin "35") (pinfunction "35_35") (pintype "passive"))
    )
    (net (code "1590") (name "unconnected-(SV38-Pad36)") (class "Default")
      (node (ref "SV38") (pin "36") (pinfunction "36_36") (pintype "passive"))
    )
    (net (code "1591") (name "unconnected-(SV38-Pad37)") (class "Default")
      (node (ref "SV38") (pin "37") (pinfunction "37_37") (pintype "passive"))
    )
    (net (code "1592") (name "unconnected-(SV38-Pad38)") (class "Default")
      (node (ref "SV38") (pin "38") (pinfunction "38_38") (pintype "passive"))
    )
    (net (code "1593") (name "unconnected-(SV38-Pad39)") (class "Default")
      (node (ref "SV38") (pin "39") (pinfunction "39_39") (pintype "passive"))
    )
    (net (code "1594") (name "unconnected-(SV38-Pad40)") (class "Default")
      (node (ref "SV38") (pin "40") (pinfunction "40_40") (pintype "passive"))
    )
    (net (code "1595") (name "unconnected-(SV39-Pad1)") (class "Default")
      (node (ref "SV39") (pin "1") (pinfunction "1_1") (pintype "passive"))
    )
    (net (code "1596") (name "unconnected-(SV39-Pad2)") (class "Default")
      (node (ref "SV39") (pin "2") (pinfunction "2_2") (pintype "passive"))
    )
    (net (code "1597") (name "unconnected-(SV39-Pad3)") (class "Default")
      (node (ref "SV39") (pin "3") (pinfunction "3_3") (pintype "passive"))
    )
    (net (code "1598") (name "unconnected-(SV39-Pad4)") (class "Default")
      (node (ref "SV39") (pin "4") (pinfunction "4_4") (pintype "passive"))
    )
    (net (code "1599") (name "unconnected-(SV39-Pad5)") (class "Default")
      (node (ref "SV39") (pin "5") (pinfunction "5_5") (pintype "passive"))
    )
    (net (code "1600") (name "unconnected-(SV39-Pad6)") (class "Default")
      (node (ref "SV39") (pin "6") (pinfunction "6_6") (pintype "passive"))
    )
    (net (code "1601") (name "unconnected-(SV39-Pad7)") (class "Default")
      (node (ref "SV39") (pin "7") (pinfunction "7_7") (pintype "passive"))
    )
    (net (code "1602") (name "unconnected-(SV39-Pad8)") (class "Default")
      (node (ref "SV39") (pin "8") (pinfunction "8_8") (pintype "passive"))
    )
    (net (code "1603") (name "unconnected-(SV39-Pad9)") (class "Default")
      (node (ref "SV39") (pin "9") (pinfunction "9_9") (pintype "passive"))
    )
    (net (code "1604") (name "unconnected-(SV39-Pad10)") (class "Default")
      (node (ref "SV39") (pin "10") (pinfunction "10_10") (pintype "passive"))
    )
    (net (code "1605") (name "unconnected-(SV39-Pad11)") (class "Default")
      (node (ref "SV39") (pin "11") (pinfunction "11_11") (pintype "passive"))
    )
    (net (code "1606") (name "unconnected-(SV39-Pad12)") (class "Default")
      (node (ref "SV39") (pin "12") (pinfunction "12_12") (pintype "passive"))
    )
    (net (code "1607") (name "unconnected-(SV39-Pad13)") (class "Default")
      (node (ref "SV39") (pin "13") (pinfunction "13_13") (pintype "passive"))
    )
    (net (code "1608") (name "unconnected-(SV39-Pad14)") (class "Default")
      (node (ref "SV39") (pin "14") (pinfunction "14_14") (pintype "passive"))
    )
    (net (code "1609") (name "unconnected-(SV39-Pad15)") (class "Default")
      (node (ref "SV39") (pin "15") (pinfunction "15_15") (pintype "passive"))
    )
    (net (code "1610") (name "unconnected-(SV39-Pad16)") (class "Default")
      (node (ref "SV39") (pin "16") (pinfunction "16_16") (pintype "passive"))
    )
    (net (code "1611") (name "unconnected-(SV39-Pad17)") (class "Default")
      (node (ref "SV39") (pin "17") (pinfunction "17_17") (pintype "passive"))
    )
    (net (code "1612") (name "unconnected-(SV39-Pad18)") (class "Default")
      (node (ref "SV39") (pin "18") (pinfunction "18_18") (pintype "passive"))
    )
    (net (code "1613") (name "unconnected-(SV39-Pad19)") (class "Default")
      (node (ref "SV39") (pin "19") (pinfunction "19_19") (pintype "passive"))
    )
    (net (code "1614") (name "unconnected-(SV39-Pad20)") (class "Default")
      (node (ref "SV39") (pin "20") (pinfunction "20_20") (pintype "passive"))
    )
    (net (code "1615") (name "unconnected-(SV39-Pad21)") (class "Default")
      (node (ref "SV39") (pin "21") (pinfunction "21_21") (pintype "passive"))
    )
    (net (code "1616") (name "unconnected-(SV39-Pad22)") (class "Default")
      (node (ref "SV39") (pin "22") (pinfunction "22_22") (pintype "passive"))
    )
    (net (code "1617") (name "unconnected-(SV39-Pad23)") (class "Default")
      (node (ref "SV39") (pin "23") (pinfunction "23_23") (pintype "passive"))
    )
    (net (code "1618") (name "unconnected-(SV39-Pad24)") (class "Default")
      (node (ref "SV39") (pin "24") (pinfunction "24_24") (pintype "passive"))
    )
    (net (code "1619") (name "unconnected-(SV39-Pad25)") (class "Default")
      (node (ref "SV39") (pin "25") (pinfunction "25_25") (pintype "passive"))
    )
    (net (code "1620") (name "unconnected-(SV39-Pad26)") (class "Default")
      (node (ref "SV39") (pin "26") (pinfunction "26_26") (pintype "passive"))
    )
    (net (code "1621") (name "unconnected-(SV39-Pad27)") (class "Default")
      (node (ref "SV39") (pin "27") (pinfunction "27_27") (pintype "passive"))
    )
    (net (code "1622") (name "unconnected-(SV39-Pad28)") (class "Default")
      (node (ref "SV39") (pin "28") (pinfunction "28_28") (pintype "passive"))
    )
    (net (code "1623") (name "unconnected-(SV39-Pad29)") (class "Default")
      (node (ref "SV39") (pin "29") (pinfunction "29_29") (pintype "passive"))
    )
    (net (code "1624") (name "unconnected-(SV39-Pad30)") (class "Default")
      (node (ref "SV39") (pin "30") (pinfunction "30_30") (pintype "passive"))
    )
    (net (code "1625") (name "unconnected-(SV39-Pad31)") (class "Default")
      (node (ref "SV39") (pin "31") (pinfunction "31_31") (pintype "passive"))
    )
    (net (code "1626") (name "unconnected-(SV39-Pad32)") (class "Default")
      (node (ref "SV39") (pin "32") (pinfunction "32_32") (pintype "passive"))
    )
    (net (code "1627") (name "unconnected-(SV39-Pad33)") (class "Default")
      (node (ref "SV39") (pin "33") (pinfunction "33_33") (pintype "passive"))
    )
    (net (code "1628") (name "unconnected-(SV39-Pad34)") (class "Default")
      (node (ref "SV39") (pin "34") (pinfunction "34_34") (pintype "passive"))
    )
    (net (code "1629") (name "unconnected-(SV39-Pad35)") (class "Default")
      (node (ref "SV39") (pin "35") (pinfunction "35_35") (pintype "passive"))
    )
    (net (code "1630") (name "unconnected-(SV39-Pad36)") (class "Default")
      (node (ref "SV39") (pin "36") (pinfunction "36_36") (pintype "passive"))
    )
    (net (code "1631") (name "unconnected-(SV40-Pad1)") (class "Default")
      (node (ref "SV40") (pin "1") (pinfunction "1_1") (pintype "passive"))
    )
    (net (code "1632") (name "unconnected-(SV40-Pad2)") (class "Default")
      (node (ref "SV40") (pin "2") (pinfunction "2_2") (pintype "passive"))
    )
    (net (code "1633") (name "unconnected-(SV40-Pad3)") (class "Default")
      (node (ref "SV40") (pin "3") (pinfunction "3_3") (pintype "passive"))
    )
    (net (code "1634") (name "unconnected-(SV40-Pad4)") (class "Default")
      (node (ref "SV40") (pin "4") (pinfunction "4_4") (pintype "passive"))
    )
    (net (code "1635") (name "unconnected-(SV40-Pad5)") (class "Default")
      (node (ref "SV40") (pin "5") (pinfunction "5_5") (pintype "passive"))
    )
    (net (code "1636") (name "unconnected-(SV40-Pad6)") (class "Default")
      (node (ref "SV40") (pin "6") (pinfunction "6_6") (pintype "passive"))
    )
    (net (code "1637") (name "unconnected-(SV40-Pad7)") (class "Default")
      (node (ref "SV40") (pin "7") (pinfunction "7_7") (pintype "passive"))
    )
    (net (code "1638") (name "unconnected-(SV40-Pad8)") (class "Default")
      (node (ref "SV40") (pin "8") (pinfunction "8_8") (pintype "passive"))
    )
    (net (code "1639") (name "unconnected-(SV40-Pad9)") (class "Default")
      (node (ref "SV40") (pin "9") (pinfunction "9_9") (pintype "passive"))
    )
    (net (code "1640") (name "unconnected-(SV40-Pad10)") (class "Default")
      (node (ref "SV40") (pin "10") (pinfunction "10_10") (pintype "passive"))
    )
    (net (code "1641") (name "unconnected-(SV40-Pad11)") (class "Default")
      (node (ref "SV40") (pin "11") (pinfunction "11_11") (pintype "passive"))
    )
    (net (code "1642") (name "unconnected-(SV40-Pad12)") (class "Default")
      (node (ref "SV40") (pin "12") (pinfunction "12_12") (pintype "passive"))
    )
    (net (code "1643") (name "unconnected-(SV40-Pad13)") (class "Default")
      (node (ref "SV40") (pin "13") (pinfunction "13_13") (pintype "passive"))
    )
    (net (code "1644") (name "unconnected-(SV40-Pad14)") (class "Default")
      (node (ref "SV40") (pin "14") (pinfunction "14_14") (pintype "passive"))
    )
    (net (code "1645") (name "unconnected-(SV40-Pad15)") (class "Default")
      (node (ref "SV40") (pin "15") (pinfunction "15_15") (pintype "passive"))
    )
    (net (code "1646") (name "unconnected-(SV40-Pad16)") (class "Default")
      (node (ref "SV40") (pin "16") (pinfunction "16_16") (pintype "passive"))
    )
    (net (code "1647") (name "unconnected-(SV40-Pad17)") (class "Default")
      (node (ref "SV40") (pin "17") (pinfunction "17_17") (pintype "passive"))
    )
    (net (code "1648") (name "unconnected-(SV40-Pad18)") (class "Default")
      (node (ref "SV40") (pin "18") (pinfunction "18_18") (pintype "passive"))
    )
    (net (code "1649") (name "unconnected-(SV40-Pad19)") (class "Default")
      (node (ref "SV40") (pin "19") (pinfunction "19_19") (pintype "passive"))
    )
    (net (code "1650") (name "unconnected-(SV40-Pad20)") (class "Default")
      (node (ref "SV40") (pin "20") (pinfunction "20_20") (pintype "passive"))
    )
    (net (code "1651") (name "unconnected-(SV40-Pad21)") (class "Default")
      (node (ref "SV40") (pin "21") (pinfunction "21_21") (pintype "passive"))
    )
    (net (code "1652") (name "unconnected-(SV40-Pad22)") (class "Default")
      (node (ref "SV40") (pin "22") (pinfunction "22_22") (pintype "passive"))
    )
    (net (code "1653") (name "unconnected-(SV40-Pad23)") (class "Default")
      (node (ref "SV40") (pin "23") (pinfunction "23_23") (pintype "passive"))
    )
    (net (code "1654") (name "unconnected-(SV40-Pad24)") (class "Default")
      (node (ref "SV40") (pin "24") (pinfunction "24_24") (pintype "passive"))
    )
    (net (code "1655") (name "unconnected-(SV40-Pad25)") (class "Default")
      (node (ref "SV40") (pin "25") (pinfunction "25_25") (pintype "passive"))
    )
    (net (code "1656") (name "unconnected-(SV40-Pad26)") (class "Default")
      (node (ref "SV40") (pin "26") (pinfunction "26_26") (pintype "passive"))
    )
    (net (code "1657") (name "unconnected-(SV40-Pad27)") (class "Default")
      (node (ref "SV40") (pin "27") (pinfunction "27_27") (pintype "passive"))
    )
    (net (code "1658") (name "unconnected-(SV40-Pad28)") (class "Default")
      (node (ref "SV40") (pin "28") (pinfunction "28_28") (pintype "passive"))
    )
    (net (code "1659") (name "unconnected-(SV40-Pad29)") (class "Default")
      (node (ref "SV40") (pin "29") (pinfunction "29_29") (pintype "passive"))
    )
    (net (code "1660") (name "unconnected-(SV40-Pad30)") (class "Default")
      (node (ref "SV40") (pin "30") (pinfunction "30_30") (pintype "passive"))
    )
    (net (code "1661") (name "unconnected-(SV40-Pad31)") (class "Default")
      (node (ref "SV40") (pin "31") (pinfunction "31_31") (pintype "passive"))
    )
    (net (code "1662") (name "unconnected-(SV40-Pad32)") (class "Default")
      (node (ref "SV40") (pin "32") (pinfunction "32_32") (pintype "passive"))
    )
    (net (code "1663") (name "unconnected-(SV40-Pad33)") (class "Default")
      (node (ref "SV40") (pin "33") (pinfunction "33_33") (pintype "passive"))
    )
    (net (code "1664") (name "unconnected-(SV40-Pad34)") (class "Default")
      (node (ref "SV40") (pin "34") (pinfunction "34_34") (pintype "passive"))
    )
    (net (code "1665") (name "unconnected-(SV40-Pad35)") (class "Default")
      (node (ref "SV40") (pin "35") (pinfunction "35_35") (pintype "passive"))
    )
    (net (code "1666") (name "unconnected-(SV40-Pad36)") (class "Default")
      (node (ref "SV40") (pin "36") (pinfunction "36_36") (pintype "passive"))
    )
    (net (code "1667") (name "unconnected-(SV41-Pad1)") (class "Default")
      (node (ref "SV41") (pin "1") (pinfunction "1_1") (pintype "passive"))
    )
    (net (code "1668") (name "unconnected-(SV41-Pad2)") (class "Default")
      (node (ref "SV41") (pin "2") (pinfunction "2_2") (pintype "passive"))
    )
    (net (code "1669") (name "unconnected-(SV41-Pad3)") (class "Default")
      (node (ref "SV41") (pin "3") (pinfunction "3_3") (pintype "passive"))
    )
    (net (code "1670") (name "unconnected-(SV41-Pad4)") (class "Default")
      (node (ref "SV41") (pin "4") (pinfunction "4_4") (pintype "passive"))
    )
    (net (code "1671") (name "unconnected-(SV41-Pad5)") (class "Default")
      (node (ref "SV41") (pin "5") (pinfunction "5_5") (pintype "passive"))
    )
    (net (code "1672") (name "unconnected-(SV41-Pad6)") (class "Default")
      (node (ref "SV41") (pin "6") (pinfunction "6_6") (pintype "passive"))
    )
    (net (code "1673") (name "unconnected-(SV41-Pad7)") (class "Default")
      (node (ref "SV41") (pin "7") (pinfunction "7_7") (pintype "passive"))
    )
    (net (code "1674") (name "unconnected-(SV41-Pad8)") (class "Default")
      (node (ref "SV41") (pin "8") (pinfunction "8_8") (pintype "passive"))
    )
    (net (code "1675") (name "unconnected-(SV41-Pad9)") (class "Default")
      (node (ref "SV41") (pin "9") (pinfunction "9_9") (pintype "passive"))
    )
    (net (code "1676") (name "unconnected-(SV41-Pad10)") (class "Default")
      (node (ref "SV41") (pin "10") (pinfunction "10_10") (pintype "passive"))
    )
    (net (code "1677") (name "unconnected-(SV41-Pad11)") (class "Default")
      (node (ref "SV41") (pin "11") (pinfunction "11_11") (pintype "passive"))
    )
    (net (code "1678") (name "unconnected-(SV41-Pad12)") (class "Default")
      (node (ref "SV41") (pin "12") (pinfunction "12_12") (pintype "passive"))
    )
    (net (code "1679") (name "unconnected-(SV41-Pad13)") (class "Default")
      (node (ref "SV41") (pin "13") (pinfunction "13_13") (pintype "passive"))
    )
    (net (code "1680") (name "unconnected-(SV41-Pad14)") (class "Default")
      (node (ref "SV41") (pin "14") (pinfunction "14_14") (pintype "passive"))
    )
    (net (code "1681") (name "unconnected-(SV41-Pad15)") (class "Default")
      (node (ref "SV41") (pin "15") (pinfunction "15_15") (pintype "passive"))
    )
    (net (code "1682") (name "unconnected-(SV41-Pad16)") (class "Default")
      (node (ref "SV41") (pin "16") (pinfunction "16_16") (pintype "passive"))
    )
    (net (code "1683") (name "unconnected-(SV41-Pad17)") (class "Default")
      (node (ref "SV41") (pin "17") (pinfunction "17_17") (pintype "passive"))
    )
    (net (code "1684") (name "unconnected-(SV41-Pad18)") (class "Default")
      (node (ref "SV41") (pin "18") (pinfunction "18_18") (pintype "passive"))
    )
    (net (code "1685") (name "unconnected-(SV41-Pad19)") (class "Default")
      (node (ref "SV41") (pin "19") (pinfunction "19_19") (pintype "passive"))
    )
    (net (code "1686") (name "unconnected-(SV41-Pad20)") (class "Default")
      (node (ref "SV41") (pin "20") (pinfunction "20_20") (pintype "passive"))
    )
    (net (code "1687") (name "unconnected-(SV41-Pad21)") (class "Default")
      (node (ref "SV41") (pin "21") (pinfunction "21_21") (pintype "passive"))
    )
    (net (code "1688") (name "unconnected-(SV41-Pad22)") (class "Default")
      (node (ref "SV41") (pin "22") (pinfunction "22_22") (pintype "passive"))
    )
    (net (code "1689") (name "unconnected-(SV41-Pad23)") (class "Default")
      (node (ref "SV41") (pin "23") (pinfunction "23_23") (pintype "passive"))
    )
    (net (code "1690") (name "unconnected-(SV41-Pad24)") (class "Default")
      (node (ref "SV41") (pin "24") (pinfunction "24_24") (pintype "passive"))
    )
    (net (code "1691") (name "unconnected-(SV41-Pad25)") (class "Default")
      (node (ref "SV41") (pin "25") (pinfunction "25_25") (pintype "passive"))
    )
    (net (code "1692") (name "unconnected-(SV41-Pad26)") (class "Default")
      (node (ref "SV41") (pin "26") (pinfunction "26_26") (pintype "passive"))
    )
    (net (code "1693") (name "unconnected-(SV41-Pad27)") (class "Default")
      (node (ref "SV41") (pin "27") (pinfunction "27_27") (pintype "passive"))
    )
    (net (code "1694") (name "unconnected-(SV41-Pad28)") (class "Default")
      (node (ref "SV41") (pin "28") (pinfunction "28_28") (pintype "passive"))
    )
    (net (code "1695") (name "unconnected-(SV41-Pad29)") (class "Default")
      (node (ref "SV41") (pin "29") (pinfunction "29_29") (pintype "passive"))
    )
    (net (code "1696") (name "unconnected-(SV41-Pad30)") (class "Default")
      (node (ref "SV41") (pin "30") (pinfunction "30_30") (pintype "passive"))
    )
    (net (code "1697") (name "unconnected-(SV41-Pad31)") (class "Default")
      (node (ref "SV41") (pin "31") (pinfunction "31_31") (pintype "passive"))
    )
    (net (code "1698") (name "unconnected-(SV41-Pad32)") (class "Default")
      (node (ref "SV41") (pin "32") (pinfunction "32_32") (pintype "passive"))
    )
    (net (code "1699") (name "unconnected-(SV41-Pad33)") (class "Default")
      (node (ref "SV41") (pin "33") (pinfunction "33_33") (pintype "passive"))
    )
    (net (code "1700") (name "unconnected-(SV41-Pad34)") (class "Default")
      (node (ref "SV41") (pin "34") (pinfunction "34_34") (pintype "passive"))
    )
    (net (code "1701") (name "unconnected-(SV41-Pad35)") (class "Default")
      (node (ref "SV41") (pin "35") (pinfunction "35_35") (pintype "passive"))
    )
    (net (code "1702") (name "unconnected-(SV41-Pad36)") (class "Default")
      (node (ref "SV41") (pin "36") (pinfunction "36_36") (pintype "passive"))
    )
    (net (code "1703") (name "unconnected-(SV42-Pad1)") (class "Default")
      (node (ref "SV42") (pin "1") (pinfunction "1_1") (pintype "passive"))
    )
    (net (code "1704") (name "unconnected-(SV42-Pad2)") (class "Default")
      (node (ref "SV42") (pin "2") (pinfunction "2_2") (pintype "passive"))
    )
    (net (code "1705") (name "unconnected-(SV42-Pad3)") (class "Default")
      (node (ref "SV42") (pin "3") (pinfunction "3_3") (pintype "passive"))
    )
    (net (code "1706") (name "unconnected-(SV42-Pad4)") (class "Default")
      (node (ref "SV42") (pin "4") (pinfunction "4_4") (pintype "passive"))
    )
    (net (code "1707") (name "unconnected-(SV42-Pad5)") (class "Default")
      (node (ref "SV42") (pin "5") (pinfunction "5_5") (pintype "passive"))
    )
    (net (code "1708") (name "unconnected-(SV42-Pad6)") (class "Default")
      (node (ref "SV42") (pin "6") (pinfunction "6_6") (pintype "passive"))
    )
    (net (code "1709") (name "unconnected-(SV42-Pad7)") (class "Default")
      (node (ref "SV42") (pin "7") (pinfunction "7_7") (pintype "passive"))
    )
    (net (code "1710") (name "unconnected-(SV42-Pad8)") (class "Default")
      (node (ref "SV42") (pin "8") (pinfunction "8_8") (pintype "passive"))
    )
    (net (code "1711") (name "unconnected-(SV42-Pad9)") (class "Default")
      (node (ref "SV42") (pin "9") (pinfunction "9_9") (pintype "passive"))
    )
    (net (code "1712") (name "unconnected-(SV42-Pad10)") (class "Default")
      (node (ref "SV42") (pin "10") (pinfunction "10_10") (pintype "passive"))
    )
    (net (code "1713") (name "unconnected-(SV42-Pad11)") (class "Default")
      (node (ref "SV42") (pin "11") (pinfunction "11_11") (pintype "passive"))
    )
    (net (code "1714") (name "unconnected-(SV42-Pad12)") (class "Default")
      (node (ref "SV42") (pin "12") (pinfunction "12_12") (pintype "passive"))
    )
    (net (code "1715") (name "unconnected-(SV42-Pad13)") (class "Default")
      (node (ref "SV42") (pin "13") (pinfunction "13_13") (pintype "passive"))
    )
    (net (code "1716") (name "unconnected-(SV42-Pad14)") (class "Default")
      (node (ref "SV42") (pin "14") (pinfunction "14_14") (pintype "passive"))
    )
    (net (code "1717") (name "unconnected-(SV42-Pad15)") (class "Default")
      (node (ref "SV42") (pin "15") (pinfunction "15_15") (pintype "passive"))
    )
    (net (code "1718") (name "unconnected-(SV42-Pad16)") (class "Default")
      (node (ref "SV42") (pin "16") (pinfunction "16_16") (pintype "passive"))
    )
    (net (code "1719") (name "unconnected-(SV42-Pad17)") (class "Default")
      (node (ref "SV42") (pin "17") (pinfunction "17_17") (pintype "passive"))
    )
    (net (code "1720") (name "unconnected-(SV42-Pad18)") (class "Default")
      (node (ref "SV42") (pin "18") (pinfunction "18_18") (pintype "passive"))
    )
    (net (code "1721") (name "unconnected-(SV42-Pad19)") (class "Default")
      (node (ref "SV42") (pin "19") (pinfunction "19_19") (pintype "passive"))
    )
    (net (code "1722") (name "unconnected-(SV42-Pad20)") (class "Default")
      (node (ref "SV42") (pin "20") (pinfunction "20_20") (pintype "passive"))
    )
    (net (code "1723") (name "unconnected-(SV42-Pad21)") (class "Default")
      (node (ref "SV42") (pin "21") (pinfunction "21_21") (pintype "passive"))
    )
    (net (code "1724") (name "unconnected-(SV42-Pad22)") (class "Default")
      (node (ref "SV42") (pin "22") (pinfunction "22_22") (pintype "passive"))
    )
    (net (code "1725") (name "unconnected-(SV42-Pad23)") (class "Default")
      (node (ref "SV42") (pin "23") (pinfunction "23_23") (pintype "passive"))
    )
    (net (code "1726") (name "unconnected-(SV42-Pad24)") (class "Default")
      (node (ref "SV42") (pin "24") (pinfunction "24_24") (pintype "passive"))
    )
    (net (code "1727") (name "unconnected-(SV42-Pad25)") (class "Default")
      (node (ref "SV42") (pin "25") (pinfunction "25_25") (pintype "passive"))
    )
    (net (code "1728") (name "unconnected-(SV42-Pad26)") (class "Default")
      (node (ref "SV42") (pin "26") (pinfunction "26_26") (pintype "passive"))
    )
    (net (code "1729") (name "unconnected-(SV42-Pad27)") (class "Default")
      (node (ref "SV42") (pin "27") (pinfunction "27_27") (pintype "passive"))
    )
    (net (code "1730") (name "unconnected-(SV42-Pad28)") (class "Default")
      (node (ref "SV42") (pin "28") (pinfunction "28_28") (pintype "passive"))
    )
    (net (code "1731") (name "unconnected-(SV42-Pad29)") (class "Default")
      (node (ref "SV42") (pin "29") (pinfunction "29_29") (pintype "passive"))
    )
    (net (code "1732") (name "unconnected-(SV42-Pad30)") (class "Default")
      (node (ref "SV42") (pin "30") (pinfunction "30_30") (pintype "passive"))
    )
    (net (code "1733") (name "unconnected-(SV42-Pad31)") (class "Default")
      (node (ref "SV42") (pin "31") (pinfunction "31_31") (pintype "passive"))
    )
    (net (code "1734") (name "unconnected-(SV42-Pad32)") (class "Default")
      (node (ref "SV42") (pin "32") (pinfunction "32_32") (pintype "passive"))
    )
    (net (code "1735") (name "unconnected-(SV42-Pad33)") (class "Default")
      (node (ref "SV42") (pin "33") (pinfunction "33_33") (pintype "passive"))
    )
    (net (code "1736") (name "unconnected-(SV42-Pad34)") (class "Default")
      (node (ref "SV42") (pin "34") (pinfunction "34_34") (pintype "passive"))
    )
    (net (code "1737") (name "unconnected-(SV42-Pad35)") (class "Default")
      (node (ref "SV42") (pin "35") (pinfunction "35_35") (pintype "passive"))
    )
    (net (code "1738") (name "unconnected-(SV42-Pad36)") (class "Default")
      (node (ref "SV42") (pin "36") (pinfunction "36_36") (pintype "passive"))
    )
    (net (code "1739") (name "unconnected-(SV43-Pad1)") (class "Default")
      (node (ref "SV43") (pin "1") (pinfunction "1_1") (pintype "passive"))
    )
    (net (code "1740") (name "unconnected-(SV43-Pad2)") (class "Default")
      (node (ref "SV43") (pin "2") (pinfunction "2_2") (pintype "passive"))
    )
    (net (code "1741") (name "unconnected-(SV43-Pad3)") (class "Default")
      (node (ref "SV43") (pin "3") (pinfunction "3_3") (pintype "passive"))
    )
    (net (code "1742") (name "unconnected-(SV43-Pad4)") (class "Default")
      (node (ref "SV43") (pin "4") (pinfunction "4_4") (pintype "passive"))
    )
    (net (code "1743") (name "unconnected-(SV43-Pad5)") (class "Default")
      (node (ref "SV43") (pin "5") (pinfunction "5_5") (pintype "passive"))
    )
    (net (code "1744") (name "unconnected-(SV43-Pad6)") (class "Default")
      (node (ref "SV43") (pin "6") (pinfunction "6_6") (pintype "passive"))
    )
    (net (code "1745") (name "unconnected-(SV43-Pad7)") (class "Default")
      (node (ref "SV43") (pin "7") (pinfunction "7_7") (pintype "passive"))
    )
    (net (code "1746") (name "unconnected-(SV43-Pad8)") (class "Default")
      (node (ref "SV43") (pin "8") (pinfunction "8_8") (pintype "passive"))
    )
    (net (code "1747") (name "unconnected-(SV43-Pad9)") (class "Default")
      (node (ref "SV43") (pin "9") (pinfunction "9_9") (pintype "passive"))
    )
    (net (code "1748") (name "unconnected-(SV43-Pad10)") (class "Default")
      (node (ref "SV43") (pin "10") (pinfunction "10_10") (pintype "passive"))
    )
    (net (code "1749") (name "unconnected-(SV43-Pad11)") (class "Default")
      (node (ref "SV43") (pin "11") (pinfunction "11_11") (pintype "passive"))
    )
    (net (code "1750") (name "unconnected-(SV43-Pad12)") (class "Default")
      (node (ref "SV43") (pin "12") (pinfunction "12_12") (pintype "passive"))
    )
    (net (code "1751") (name "unconnected-(SV43-Pad13)") (class "Default")
      (node (ref "SV43") (pin "13") (pinfunction "13_13") (pintype "passive"))
    )
    (net (code "1752") (name "unconnected-(SV43-Pad14)") (class "Default")
      (node (ref "SV43") (pin "14") (pinfunction "14_14") (pintype "passive"))
    )
    (net (code "1753") (name "unconnected-(SV43-Pad15)") (class "Default")
      (node (ref "SV43") (pin "15") (pinfunction "15_15") (pintype "passive"))
    )
    (net (code "1754") (name "unconnected-(SV43-Pad16)") (class "Default")
      (node (ref "SV43") (pin "16") (pinfunction "16_16") (pintype "passive"))
    )
    (net (code "1755") (name "unconnected-(SV43-Pad17)") (class "Default")
      (node (ref "SV43") (pin "17") (pinfunction "17_17") (pintype "passive"))
    )
    (net (code "1756") (name "unconnected-(SV43-Pad18)") (class "Default")
      (node (ref "SV43") (pin "18") (pinfunction "18_18") (pintype "passive"))
    )
    (net (code "1757") (name "unconnected-(SV43-Pad19)") (class "Default")
      (node (ref "SV43") (pin "19") (pinfunction "19_19") (pintype "passive"))
    )
    (net (code "1758") (name "unconnected-(SV43-Pad20)") (class "Default")
      (node (ref "SV43") (pin "20") (pinfunction "20_20") (pintype "passive"))
    )
    (net (code "1759") (name "unconnected-(SV43-Pad21)") (class "Default")
      (node (ref "SV43") (pin "21") (pinfunction "21_21") (pintype "passive"))
    )
    (net (code "1760") (name "unconnected-(SV43-Pad22)") (class "Default")
      (node (ref "SV43") (pin "22") (pinfunction "22_22") (pintype "passive"))
    )
    (net (code "1761") (name "unconnected-(SV43-Pad23)") (class "Default")
      (node (ref "SV43") (pin "23") (pinfunction "23_23") (pintype "passive"))
    )
    (net (code "1762") (name "unconnected-(SV43-Pad24)") (class "Default")
      (node (ref "SV43") (pin "24") (pinfunction "24_24") (pintype "passive"))
    )
    (net (code "1763") (name "unconnected-(SV43-Pad25)") (class "Default")
      (node (ref "SV43") (pin "25") (pinfunction "25_25") (pintype "passive"))
    )
    (net (code "1764") (name "unconnected-(SV43-Pad26)") (class "Default")
      (node (ref "SV43") (pin "26") (pinfunction "26_26") (pintype "passive"))
    )
    (net (code "1765") (name "unconnected-(SV43-Pad27)") (class "Default")
      (node (ref "SV43") (pin "27") (pinfunction "27_27") (pintype "passive"))
    )
    (net (code "1766") (name "unconnected-(SV43-Pad28)") (class "Default")
      (node (ref "SV43") (pin "28") (pinfunction "28_28") (pintype "passive"))
    )
    (net (code "1767") (name "unconnected-(SV43-Pad29)") (class "Default")
      (node (ref "SV43") (pin "29") (pinfunction "29_29") (pintype "passive"))
    )
    (net (code "1768") (name "unconnected-(SV43-Pad30)") (class "Default")
      (node (ref "SV43") (pin "30") (pinfunction "30_30") (pintype "passive"))
    )
    (net (code "1769") (name "unconnected-(SV43-Pad31)") (class "Default")
      (node (ref "SV43") (pin "31") (pinfunction "31_31") (pintype "passive"))
    )
    (net (code "1770") (name "unconnected-(SV43-Pad32)") (class "Default")
      (node (ref "SV43") (pin "32") (pinfunction "32_32") (pintype "passive"))
    )
    (net (code "1771") (name "unconnected-(SV43-Pad33)") (class "Default")
      (node (ref "SV43") (pin "33") (pinfunction "33_33") (pintype "passive"))
    )
    (net (code "1772") (name "unconnected-(SV43-Pad34)") (class "Default")
      (node (ref "SV43") (pin "34") (pinfunction "34_34") (pintype "passive"))
    )
    (net (code "1773") (name "unconnected-(SV43-Pad35)") (class "Default")
      (node (ref "SV43") (pin "35") (pinfunction "35_35") (pintype "passive"))
    )
    (net (code "1774") (name "unconnected-(SV43-Pad36)") (class "Default")
      (node (ref "SV43") (pin "36") (pinfunction "36_36") (pintype "passive"))
    )
    (net (code "1775") (name "unconnected-(SV43-Pad37)") (class "Default")
      (node (ref "SV43") (pin "37") (pinfunction "37_37") (pintype "passive"))
    )
    (net (code "1776") (name "unconnected-(SV43-Pad38)") (class "Default")
      (node (ref "SV43") (pin "38") (pinfunction "38_38") (pintype "passive"))
    )
    (net (code "1777") (name "unconnected-(SV43-Pad39)") (class "Default")
      (node (ref "SV43") (pin "39") (pinfunction "39_39") (pintype "passive"))
    )
    (net (code "1778") (name "unconnected-(SV43-Pad40)") (class "Default")
      (node (ref "SV43") (pin "40") (pinfunction "40_40") (pintype "passive"))
    )
    (net (code "1779") (name "unconnected-(SV44-Pad1)") (class "Default")
      (node (ref "SV44") (pin "1") (pinfunction "1_1") (pintype "passive"))
    )
    (net (code "1780") (name "unconnected-(SV44-Pad2)") (class "Default")
      (node (ref "SV44") (pin "2") (pinfunction "2_2") (pintype "passive"))
    )
    (net (code "1781") (name "unconnected-(SV44-Pad3)") (class "Default")
      (node (ref "SV44") (pin "3") (pinfunction "3_3") (pintype "passive"))
    )
    (net (code "1782") (name "unconnected-(SV44-Pad4)") (class "Default")
      (node (ref "SV44") (pin "4") (pinfunction "4_4") (pintype "passive"))
    )
    (net (code "1783") (name "unconnected-(SV44-Pad5)") (class "Default")
      (node (ref "SV44") (pin "5") (pinfunction "5_5") (pintype "passive"))
    )
    (net (code "1784") (name "unconnected-(SV44-Pad6)") (class "Default")
      (node (ref "SV44") (pin "6") (pinfunction "6_6") (pintype "passive"))
    )
    (net (code "1785") (name "unconnected-(SV44-Pad7)") (class "Default")
      (node (ref "SV44") (pin "7") (pinfunction "7_7") (pintype "passive"))
    )
    (net (code "1786") (name "unconnected-(SV44-Pad8)") (class "Default")
      (node (ref "SV44") (pin "8") (pinfunction "8_8") (pintype "passive"))
    )
    (net (code "1787") (name "unconnected-(SV44-Pad9)") (class "Default")
      (node (ref "SV44") (pin "9") (pinfunction "9_9") (pintype "passive"))
    )
    (net (code "1788") (name "unconnected-(SV44-Pad10)") (class "Default")
      (node (ref "SV44") (pin "10") (pinfunction "10_10") (pintype "passive"))
    )
    (net (code "1789") (name "unconnected-(SV44-Pad11)") (class "Default")
      (node (ref "SV44") (pin "11") (pinfunction "11_11") (pintype "passive"))
    )
    (net (code "1790") (name "unconnected-(SV44-Pad12)") (class "Default")
      (node (ref "SV44") (pin "12") (pinfunction "12_12") (pintype "passive"))
    )
    (net (code "1791") (name "unconnected-(SV44-Pad13)") (class "Default")
      (node (ref "SV44") (pin "13") (pinfunction "13_13") (pintype "passive"))
    )
    (net (code "1792") (name "unconnected-(SV44-Pad14)") (class "Default")
      (node (ref "SV44") (pin "14") (pinfunction "14_14") (pintype "passive"))
    )
    (net (code "1793") (name "unconnected-(SV44-Pad15)") (class "Default")
      (node (ref "SV44") (pin "15") (pinfunction "15_15") (pintype "passive"))
    )
    (net (code "1794") (name "unconnected-(SV44-Pad16)") (class "Default")
      (node (ref "SV44") (pin "16") (pinfunction "16_16") (pintype "passive"))
    )
    (net (code "1795") (name "unconnected-(SV44-Pad17)") (class "Default")
      (node (ref "SV44") (pin "17") (pinfunction "17_17") (pintype "passive"))
    )
    (net (code "1796") (name "unconnected-(SV44-Pad18)") (class "Default")
      (node (ref "SV44") (pin "18") (pinfunction "18_18") (pintype "passive"))
    )
    (net (code "1797") (name "unconnected-(SV44-Pad19)") (class "Default")
      (node (ref "SV44") (pin "19") (pinfunction "19_19") (pintype "passive"))
    )
    (net (code "1798") (name "unconnected-(SV44-Pad20)") (class "Default")
      (node (ref "SV44") (pin "20") (pinfunction "20_20") (pintype "passive"))
    )
    (net (code "1799") (name "unconnected-(SV44-Pad21)") (class "Default")
      (node (ref "SV44") (pin "21") (pinfunction "21_21") (pintype "passive"))
    )
    (net (code "1800") (name "unconnected-(SV44-Pad22)") (class "Default")
      (node (ref "SV44") (pin "22") (pinfunction "22_22") (pintype "passive"))
    )
    (net (code "1801") (name "unconnected-(SV44-Pad23)") (class "Default")
      (node (ref "SV44") (pin "23") (pinfunction "23_23") (pintype "passive"))
    )
    (net (code "1802") (name "unconnected-(SV44-Pad24)") (class "Default")
      (node (ref "SV44") (pin "24") (pinfunction "24_24") (pintype "passive"))
    )
    (net (code "1803") (name "unconnected-(SV44-Pad25)") (class "Default")
      (node (ref "SV44") (pin "25") (pinfunction "25_25") (pintype "passive"))
    )
    (net (code "1804") (name "unconnected-(SV44-Pad26)") (class "Default")
      (node (ref "SV44") (pin "26") (pinfunction "26_26") (pintype "passive"))
    )
    (net (code "1805") (name "unconnected-(SV44-Pad27)") (class "Default")
      (node (ref "SV44") (pin "27") (pinfunction "27_27") (pintype "passive"))
    )
    (net (code "1806") (name "unconnected-(SV44-Pad28)") (class "Default")
      (node (ref "SV44") (pin "28") (pinfunction "28_28") (pintype "passive"))
    )
    (net (code "1807") (name "unconnected-(SV44-Pad29)") (class "Default")
      (node (ref "SV44") (pin "29") (pinfunction "29_29") (pintype "passive"))
    )
    (net (code "1808") (name "unconnected-(SV44-Pad30)") (class "Default")
      (node (ref "SV44") (pin "30") (pinfunction "30_30") (pintype "passive"))
    )
    (net (code "1809") (name "unconnected-(SV44-Pad31)") (class "Default")
      (node (ref "SV44") (pin "31") (pinfunction "31_31") (pintype "passive"))
    )
    (net (code "1810") (name "unconnected-(SV44-Pad32)") (class "Default")
      (node (ref "SV44") (pin "32") (pinfunction "32_32") (pintype "passive"))
    )
    (net (code "1811") (name "unconnected-(SV44-Pad33)") (class "Default")
      (node (ref "SV44") (pin "33") (pinfunction "33_33") (pintype "passive"))
    )
    (net (code "1812") (name "unconnected-(SV44-Pad34)") (class "Default")
      (node (ref "SV44") (pin "34") (pinfunction "34_34") (pintype "passive"))
    )
    (net (code "1813") (name "unconnected-(SV44-Pad35)") (class "Default")
      (node (ref "SV44") (pin "35") (pinfunction "35_35") (pintype "passive"))
    )
    (net (code "1814") (name "unconnected-(SV44-Pad36)") (class "Default")
      (node (ref "SV44") (pin "36") (pinfunction "36_36") (pintype "passive"))
    )
    (net (code "1815") (name "unconnected-(SV44-Pad37)") (class "Default")
      (node (ref "SV44") (pin "37") (pinfunction "37_37") (pintype "passive"))
    )
    (net (code "1816") (name "unconnected-(SV44-Pad38)") (class "Default")
      (node (ref "SV44") (pin "38") (pinfunction "38_38") (pintype "passive"))
    )
    (net (code "1817") (name "unconnected-(SV44-Pad39)") (class "Default")
      (node (ref "SV44") (pin "39") (pinfunction "39_39") (pintype "passive"))
    )
    (net (code "1818") (name "unconnected-(SV44-Pad40)") (class "Default")
      (node (ref "SV44") (pin "40") (pinfunction "40_40") (pintype "passive"))
    )
    (net (code "1819") (name "unconnected-(SV45-Pad1)") (class "Default")
      (node (ref "SV45") (pin "1") (pinfunction "1_1") (pintype "passive"))
    )
    (net (code "1820") (name "unconnected-(SV45-Pad2)") (class "Default")
      (node (ref "SV45") (pin "2") (pinfunction "2_2") (pintype "passive"))
    )
    (net (code "1821") (name "unconnected-(SV45-Pad3)") (class "Default")
      (node (ref "SV45") (pin "3") (pinfunction "3_3") (pintype "passive"))
    )
    (net (code "1822") (name "unconnected-(SV45-Pad4)") (class "Default")
      (node (ref "SV45") (pin "4") (pinfunction "4_4") (pintype "passive"))
    )
    (net (code "1823") (name "unconnected-(SV45-Pad5)") (class "Default")
      (node (ref "SV45") (pin "5") (pinfunction "5_5") (pintype "passive"))
    )
    (net (code "1824") (name "unconnected-(SV45-Pad6)") (class "Default")
      (node (ref "SV45") (pin "6") (pinfunction "6_6") (pintype "passive"))
    )
    (net (code "1825") (name "unconnected-(SV45-Pad7)") (class "Default")
      (node (ref "SV45") (pin "7") (pinfunction "7_7") (pintype "passive"))
    )
    (net (code "1826") (name "unconnected-(SV45-Pad8)") (class "Default")
      (node (ref "SV45") (pin "8") (pinfunction "8_8") (pintype "passive"))
    )
    (net (code "1827") (name "unconnected-(SV45-Pad9)") (class "Default")
      (node (ref "SV45") (pin "9") (pinfunction "9_9") (pintype "passive"))
    )
    (net (code "1828") (name "unconnected-(SV45-Pad10)") (class "Default")
      (node (ref "SV45") (pin "10") (pinfunction "10_10") (pintype "passive"))
    )
    (net (code "1829") (name "unconnected-(SV45-Pad11)") (class "Default")
      (node (ref "SV45") (pin "11") (pinfunction "11_11") (pintype "passive"))
    )
    (net (code "1830") (name "unconnected-(SV45-Pad12)") (class "Default")
      (node (ref "SV45") (pin "12") (pinfunction "12_12") (pintype "passive"))
    )
    (net (code "1831") (name "unconnected-(SV45-Pad13)") (class "Default")
      (node (ref "SV45") (pin "13") (pinfunction "13_13") (pintype "passive"))
    )
    (net (code "1832") (name "unconnected-(SV45-Pad14)") (class "Default")
      (node (ref "SV45") (pin "14") (pinfunction "14_14") (pintype "passive"))
    )
    (net (code "1833") (name "unconnected-(SV45-Pad15)") (class "Default")
      (node (ref "SV45") (pin "15") (pinfunction "15_15") (pintype "passive"))
    )
    (net (code "1834") (name "unconnected-(SV45-Pad16)") (class "Default")
      (node (ref "SV45") (pin "16") (pinfunction "16_16") (pintype "passive"))
    )
    (net (code "1835") (name "unconnected-(SV45-Pad17)") (class "Default")
      (node (ref "SV45") (pin "17") (pinfunction "17_17") (pintype "passive"))
    )
    (net (code "1836") (name "unconnected-(SV45-Pad18)") (class "Default")
      (node (ref "SV45") (pin "18") (pinfunction "18_18") (pintype "passive"))
    )
    (net (code "1837") (name "unconnected-(SV45-Pad19)") (class "Default")
      (node (ref "SV45") (pin "19") (pinfunction "19_19") (pintype "passive"))
    )
    (net (code "1838") (name "unconnected-(SV45-Pad20)") (class "Default")
      (node (ref "SV45") (pin "20") (pinfunction "20_20") (pintype "passive"))
    )
    (net (code "1839") (name "unconnected-(SV45-Pad21)") (class "Default")
      (node (ref "SV45") (pin "21") (pinfunction "21_21") (pintype "passive"))
    )
    (net (code "1840") (name "unconnected-(SV45-Pad22)") (class "Default")
      (node (ref "SV45") (pin "22") (pinfunction "22_22") (pintype "passive"))
    )
    (net (code "1841") (name "unconnected-(SV45-Pad23)") (class "Default")
      (node (ref "SV45") (pin "23") (pinfunction "23_23") (pintype "passive"))
    )
    (net (code "1842") (name "unconnected-(SV45-Pad24)") (class "Default")
      (node (ref "SV45") (pin "24") (pinfunction "24_24") (pintype "passive"))
    )
    (net (code "1843") (name "unconnected-(SV45-Pad25)") (class "Default")
      (node (ref "SV45") (pin "25") (pinfunction "25_25") (pintype "passive"))
    )
    (net (code "1844") (name "unconnected-(SV45-Pad26)") (class "Default")
      (node (ref "SV45") (pin "26") (pinfunction "26_26") (pintype "passive"))
    )
    (net (code "1845") (name "unconnected-(SV45-Pad27)") (class "Default")
      (node (ref "SV45") (pin "27") (pinfunction "27_27") (pintype "passive"))
    )
    (net (code "1846") (name "unconnected-(SV45-Pad28)") (class "Default")
      (node (ref "SV45") (pin "28") (pinfunction "28_28") (pintype "passive"))
    )
    (net (code "1847") (name "unconnected-(SV45-Pad29)") (class "Default")
      (node (ref "SV45") (pin "29") (pinfunction "29_29") (pintype "passive"))
    )
    (net (code "1848") (name "unconnected-(SV45-Pad30)") (class "Default")
      (node (ref "SV45") (pin "30") (pinfunction "30_30") (pintype "passive"))
    )
    (net (code "1849") (name "unconnected-(SV45-Pad31)") (class "Default")
      (node (ref "SV45") (pin "31") (pinfunction "31_31") (pintype "passive"))
    )
    (net (code "1850") (name "unconnected-(SV45-Pad32)") (class "Default")
      (node (ref "SV45") (pin "32") (pinfunction "32_32") (pintype "passive"))
    )
    (net (code "1851") (name "unconnected-(SV45-Pad33)") (class "Default")
      (node (ref "SV45") (pin "33") (pinfunction "33_33") (pintype "passive"))
    )
    (net (code "1852") (name "unconnected-(SV45-Pad34)") (class "Default")
      (node (ref "SV45") (pin "34") (pinfunction "34_34") (pintype "passive"))
    )
    (net (code "1853") (name "unconnected-(SV45-Pad35)") (class "Default")
      (node (ref "SV45") (pin "35") (pinfunction "35_35") (pintype "passive"))
    )
    (net (code "1854") (name "unconnected-(SV45-Pad36)") (class "Default")
      (node (ref "SV45") (pin "36") (pinfunction "36_36") (pintype "passive"))
    )
    (net (code "1855") (name "unconnected-(SV45-Pad37)") (class "Default")
      (node (ref "SV45") (pin "37") (pinfunction "37_37") (pintype "passive"))
    )
    (net (code "1856") (name "unconnected-(SV45-Pad38)") (class "Default")
      (node (ref "SV45") (pin "38") (pinfunction "38_38") (pintype "passive"))
    )
    (net (code "1857") (name "unconnected-(SV45-Pad39)") (class "Default")
      (node (ref "SV45") (pin "39") (pinfunction "39_39") (pintype "passive"))
    )
    (net (code "1858") (name "unconnected-(SV45-Pad40)") (class "Default")
      (node (ref "SV45") (pin "40") (pinfunction "40_40") (pintype "passive"))
    )
    (net (code "1859") (name "unconnected-(SV46-Pad1)") (class "Default")
      (node (ref "SV46") (pin "1") (pinfunction "1_1") (pintype "passive"))
    )
    (net (code "1860") (name "unconnected-(SV46-Pad2)") (class "Default")
      (node (ref "SV46") (pin "2") (pinfunction "2_2") (pintype "passive"))
    )
    (net (code "1861") (name "unconnected-(SV46-Pad3)") (class "Default")
      (node (ref "SV46") (pin "3") (pinfunction "3_3") (pintype "passive"))
    )
    (net (code "1862") (name "unconnected-(SV46-Pad4)") (class "Default")
      (node (ref "SV46") (pin "4") (pinfunction "4_4") (pintype "passive"))
    )
    (net (code "1863") (name "unconnected-(SV46-Pad5)") (class "Default")
      (node (ref "SV46") (pin "5") (pinfunction "5_5") (pintype "passive"))
    )
    (net (code "1864") (name "unconnected-(SV46-Pad6)") (class "Default")
      (node (ref "SV46") (pin "6") (pinfunction "6_6") (pintype "passive"))
    )
    (net (code "1865") (name "unconnected-(SV46-Pad7)") (class "Default")
      (node (ref "SV46") (pin "7") (pinfunction "7_7") (pintype "passive"))
    )
    (net (code "1866") (name "unconnected-(SV46-Pad8)") (class "Default")
      (node (ref "SV46") (pin "8") (pinfunction "8_8") (pintype "passive"))
    )
    (net (code "1867") (name "unconnected-(SV46-Pad9)") (class "Default")
      (node (ref "SV46") (pin "9") (pinfunction "9_9") (pintype "passive"))
    )
    (net (code "1868") (name "unconnected-(SV46-Pad10)") (class "Default")
      (node (ref "SV46") (pin "10") (pinfunction "10_10") (pintype "passive"))
    )
    (net (code "1869") (name "unconnected-(SV46-Pad11)") (class "Default")
      (node (ref "SV46") (pin "11") (pinfunction "11_11") (pintype "passive"))
    )
    (net (code "1870") (name "unconnected-(SV46-Pad12)") (class "Default")
      (node (ref "SV46") (pin "12") (pinfunction "12_12") (pintype "passive"))
    )
    (net (code "1871") (name "unconnected-(SV46-Pad13)") (class "Default")
      (node (ref "SV46") (pin "13") (pinfunction "13_13") (pintype "passive"))
    )
    (net (code "1872") (name "unconnected-(SV46-Pad14)") (class "Default")
      (node (ref "SV46") (pin "14") (pinfunction "14_14") (pintype "passive"))
    )
    (net (code "1873") (name "unconnected-(SV46-Pad15)") (class "Default")
      (node (ref "SV46") (pin "15") (pinfunction "15_15") (pintype "passive"))
    )
    (net (code "1874") (name "unconnected-(SV46-Pad16)") (class "Default")
      (node (ref "SV46") (pin "16") (pinfunction "16_16") (pintype "passive"))
    )
    (net (code "1875") (name "unconnected-(SV46-Pad17)") (class "Default")
      (node (ref "SV46") (pin "17") (pinfunction "17_17") (pintype "passive"))
    )
    (net (code "1876") (name "unconnected-(SV46-Pad18)") (class "Default")
      (node (ref "SV46") (pin "18") (pinfunction "18_18") (pintype "passive"))
    )
    (net (code "1877") (name "unconnected-(SV46-Pad19)") (class "Default")
      (node (ref "SV46") (pin "19") (pinfunction "19_19") (pintype "passive"))
    )
    (net (code "1878") (name "unconnected-(SV46-Pad20)") (class "Default")
      (node (ref "SV46") (pin "20") (pinfunction "20_20") (pintype "passive"))
    )
    (net (code "1879") (name "unconnected-(SV46-Pad21)") (class "Default")
      (node (ref "SV46") (pin "21") (pinfunction "21_21") (pintype "passive"))
    )
    (net (code "1880") (name "unconnected-(SV46-Pad22)") (class "Default")
      (node (ref "SV46") (pin "22") (pinfunction "22_22") (pintype "passive"))
    )
    (net (code "1881") (name "unconnected-(SV46-Pad23)") (class "Default")
      (node (ref "SV46") (pin "23") (pinfunction "23_23") (pintype "passive"))
    )
    (net (code "1882") (name "unconnected-(SV46-Pad24)") (class "Default")
      (node (ref "SV46") (pin "24") (pinfunction "24_24") (pintype "passive"))
    )
    (net (code "1883") (name "unconnected-(SV46-Pad25)") (class "Default")
      (node (ref "SV46") (pin "25") (pinfunction "25_25") (pintype "passive"))
    )
    (net (code "1884") (name "unconnected-(SV46-Pad26)") (class "Default")
      (node (ref "SV46") (pin "26") (pinfunction "26_26") (pintype "passive"))
    )
    (net (code "1885") (name "unconnected-(SV46-Pad27)") (class "Default")
      (node (ref "SV46") (pin "27") (pinfunction "27_27") (pintype "passive"))
    )
    (net (code "1886") (name "unconnected-(SV46-Pad28)") (class "Default")
      (node (ref "SV46") (pin "28") (pinfunction "28_28") (pintype "passive"))
    )
    (net (code "1887") (name "unconnected-(SV46-Pad29)") (class "Default")
      (node (ref "SV46") (pin "29") (pinfunction "29_29") (pintype "passive"))
    )
    (net (code "1888") (name "unconnected-(SV46-Pad30)") (class "Default")
      (node (ref "SV46") (pin "30") (pinfunction "30_30") (pintype "passive"))
    )
    (net (code "1889") (name "unconnected-(SV46-Pad31)") (class "Default")
      (node (ref "SV46") (pin "31") (pinfunction "31_31") (pintype "passive"))
    )
    (net (code "1890") (name "unconnected-(SV46-Pad32)") (class "Default")
      (node (ref "SV46") (pin "32") (pinfunction "32_32") (pintype "passive"))
    )
    (net (code "1891") (name "unconnected-(SV46-Pad33)") (class "Default")
      (node (ref "SV46") (pin "33") (pinfunction "33_33") (pintype "passive"))
    )
    (net (code "1892") (name "unconnected-(SV46-Pad34)") (class "Default")
      (node (ref "SV46") (pin "34") (pinfunction "34_34") (pintype "passive"))
    )
    (net (code "1893") (name "unconnected-(SV46-Pad35)") (class "Default")
      (node (ref "SV46") (pin "35") (pinfunction "35_35") (pintype "passive"))
    )
    (net (code "1894") (name "unconnected-(SV46-Pad36)") (class "Default")
      (node (ref "SV46") (pin "36") (pinfunction "36_36") (pintype "passive"))
    )
    (net (code "1895") (name "unconnected-(SV46-Pad37)") (class "Default")
      (node (ref "SV46") (pin "37") (pinfunction "37_37") (pintype "passive"))
    )
    (net (code "1896") (name "unconnected-(SV46-Pad38)") (class "Default")
      (node (ref "SV46") (pin "38") (pinfunction "38_38") (pintype "passive"))
    )
    (net (code "1897") (name "unconnected-(SV46-Pad39)") (class "Default")
      (node (ref "SV46") (pin "39") (pinfunction "39_39") (pintype "passive"))
    )
    (net (code "1898") (name "unconnected-(SV46-Pad40)") (class "Default")
      (node (ref "SV46") (pin "40") (pinfunction "40_40") (pintype "passive"))
    )
    (net (code "1899") (name "unconnected-(SV47-Pad1)") (class "Default")
      (node (ref "SV47") (pin "1") (pinfunction "1_1") (pintype "passive"))
    )
    (net (code "1900") (name "unconnected-(SV47-Pad2)") (class "Default")
      (node (ref "SV47") (pin "2") (pinfunction "2_2") (pintype "passive"))
    )
    (net (code "1901") (name "unconnected-(SV47-Pad3)") (class "Default")
      (node (ref "SV47") (pin "3") (pinfunction "3_3") (pintype "passive"))
    )
    (net (code "1902") (name "unconnected-(SV47-Pad4)") (class "Default")
      (node (ref "SV47") (pin "4") (pinfunction "4_4") (pintype "passive"))
    )
    (net (code "1903") (name "unconnected-(SV47-Pad5)") (class "Default")
      (node (ref "SV47") (pin "5") (pinfunction "5_5") (pintype "passive"))
    )
    (net (code "1904") (name "unconnected-(SV47-Pad6)") (class "Default")
      (node (ref "SV47") (pin "6") (pinfunction "6_6") (pintype "passive"))
    )
    (net (code "1905") (name "unconnected-(SV47-Pad7)") (class "Default")
      (node (ref "SV47") (pin "7") (pinfunction "7_7") (pintype "passive"))
    )
    (net (code "1906") (name "unconnected-(SV47-Pad8)") (class "Default")
      (node (ref "SV47") (pin "8") (pinfunction "8_8") (pintype "passive"))
    )
    (net (code "1907") (name "unconnected-(SV47-Pad9)") (class "Default")
      (node (ref "SV47") (pin "9") (pinfunction "9_9") (pintype "passive"))
    )
    (net (code "1908") (name "unconnected-(SV47-Pad10)") (class "Default")
      (node (ref "SV47") (pin "10") (pinfunction "10_10") (pintype "passive"))
    )
    (net (code "1909") (name "unconnected-(SV47-Pad11)") (class "Default")
      (node (ref "SV47") (pin "11") (pinfunction "11_11") (pintype "passive"))
    )
    (net (code "1910") (name "unconnected-(SV47-Pad12)") (class "Default")
      (node (ref "SV47") (pin "12") (pinfunction "12_12") (pintype "passive"))
    )
    (net (code "1911") (name "unconnected-(SV47-Pad13)") (class "Default")
      (node (ref "SV47") (pin "13") (pinfunction "13_13") (pintype "passive"))
    )
    (net (code "1912") (name "unconnected-(SV47-Pad14)") (class "Default")
      (node (ref "SV47") (pin "14") (pinfunction "14_14") (pintype "passive"))
    )
    (net (code "1913") (name "unconnected-(SV47-Pad15)") (class "Default")
      (node (ref "SV47") (pin "15") (pinfunction "15_15") (pintype "passive"))
    )
    (net (code "1914") (name "unconnected-(SV47-Pad16)") (class "Default")
      (node (ref "SV47") (pin "16") (pinfunction "16_16") (pintype "passive"))
    )
    (net (code "1915") (name "unconnected-(SV47-Pad17)") (class "Default")
      (node (ref "SV47") (pin "17") (pinfunction "17_17") (pintype "passive"))
    )
    (net (code "1916") (name "unconnected-(SV47-Pad18)") (class "Default")
      (node (ref "SV47") (pin "18") (pinfunction "18_18") (pintype "passive"))
    )
    (net (code "1917") (name "unconnected-(SV47-Pad19)") (class "Default")
      (node (ref "SV47") (pin "19") (pinfunction "19_19") (pintype "passive"))
    )
    (net (code "1918") (name "unconnected-(SV47-Pad20)") (class "Default")
      (node (ref "SV47") (pin "20") (pinfunction "20_20") (pintype "passive"))
    )
    (net (code "1919") (name "unconnected-(SV47-Pad21)") (class "Default")
      (node (ref "SV47") (pin "21") (pinfunction "21_21") (pintype "passive"))
    )
    (net (code "1920") (name "unconnected-(SV47-Pad22)") (class "Default")
      (node (ref "SV47") (pin "22") (pinfunction "22_22") (pintype "passive"))
    )
    (net (code "1921") (name "unconnected-(SV47-Pad23)") (class "Default")
      (node (ref "SV47") (pin "23") (pinfunction "23_23") (pintype "passive"))
    )
    (net (code "1922") (name "unconnected-(SV47-Pad24)") (class "Default")
      (node (ref "SV47") (pin "24") (pinfunction "24_24") (pintype "passive"))
    )
    (net (code "1923") (name "unconnected-(SV47-Pad25)") (class "Default")
      (node (ref "SV47") (pin "25") (pinfunction "25_25") (pintype "passive"))
    )
    (net (code "1924") (name "unconnected-(SV47-Pad26)") (class "Default")
      (node (ref "SV47") (pin "26") (pinfunction "26_26") (pintype "passive"))
    )
    (net (code "1925") (name "unconnected-(SV47-Pad27)") (class "Default")
      (node (ref "SV47") (pin "27") (pinfunction "27_27") (pintype "passive"))
    )
    (net (code "1926") (name "unconnected-(SV47-Pad28)") (class "Default")
      (node (ref "SV47") (pin "28") (pinfunction "28_28") (pintype "passive"))
    )
    (net (code "1927") (name "unconnected-(SV47-Pad29)") (class "Default")
      (node (ref "SV47") (pin "29") (pinfunction "29_29") (pintype "passive"))
    )
    (net (code "1928") (name "unconnected-(SV47-Pad30)") (class "Default")
      (node (ref "SV47") (pin "30") (pinfunction "30_30") (pintype "passive"))
    )
    (net (code "1929") (name "unconnected-(SV47-Pad31)") (class "Default")
      (node (ref "SV47") (pin "31") (pinfunction "31_31") (pintype "passive"))
    )
    (net (code "1930") (name "unconnected-(SV47-Pad32)") (class "Default")
      (node (ref "SV47") (pin "32") (pinfunction "32_32") (pintype "passive"))
    )
    (net (code "1931") (name "unconnected-(SV47-Pad33)") (class "Default")
      (node (ref "SV47") (pin "33") (pinfunction "33_33") (pintype "passive"))
    )
    (net (code "1932") (name "unconnected-(SV47-Pad34)") (class "Default")
      (node (ref "SV47") (pin "34") (pinfunction "34_34") (pintype "passive"))
    )
    (net (code "1933") (name "unconnected-(SV47-Pad35)") (class "Default")
      (node (ref "SV47") (pin "35") (pinfunction "35_35") (pintype "passive"))
    )
    (net (code "1934") (name "unconnected-(SV47-Pad36)") (class "Default")
      (node (ref "SV47") (pin "36") (pinfunction "36_36") (pintype "passive"))
    )
    (net (code "1935") (name "unconnected-(SV48-Pad1)") (class "Default")
      (node (ref "SV48") (pin "1") (pinfunction "1_1") (pintype "passive"))
    )
    (net (code "1936") (name "unconnected-(SV48-Pad2)") (class "Default")
      (node (ref "SV48") (pin "2") (pinfunction "2_2") (pintype "passive"))
    )
    (net (code "1937") (name "unconnected-(SV48-Pad3)") (class "Default")
      (node (ref "SV48") (pin "3") (pinfunction "3_3") (pintype "passive"))
    )
    (net (code "1938") (name "unconnected-(SV48-Pad4)") (class "Default")
      (node (ref "SV48") (pin "4") (pinfunction "4_4") (pintype "passive"))
    )
    (net (code "1939") (name "unconnected-(SV48-Pad5)") (class "Default")
      (node (ref "SV48") (pin "5") (pinfunction "5_5") (pintype "passive"))
    )
    (net (code "1940") (name "unconnected-(SV48-Pad6)") (class "Default")
      (node (ref "SV48") (pin "6") (pinfunction "6_6") (pintype "passive"))
    )
    (net (code "1941") (name "unconnected-(SV48-Pad7)") (class "Default")
      (node (ref "SV48") (pin "7") (pinfunction "7_7") (pintype "passive"))
    )
    (net (code "1942") (name "unconnected-(SV48-Pad8)") (class "Default")
      (node (ref "SV48") (pin "8") (pinfunction "8_8") (pintype "passive"))
    )
    (net (code "1943") (name "unconnected-(SV48-Pad9)") (class "Default")
      (node (ref "SV48") (pin "9") (pinfunction "9_9") (pintype "passive"))
    )
    (net (code "1944") (name "unconnected-(SV48-Pad10)") (class "Default")
      (node (ref "SV48") (pin "10") (pinfunction "10_10") (pintype "passive"))
    )
    (net (code "1945") (name "unconnected-(SV48-Pad11)") (class "Default")
      (node (ref "SV48") (pin "11") (pinfunction "11_11") (pintype "passive"))
    )
    (net (code "1946") (name "unconnected-(SV48-Pad12)") (class "Default")
      (node (ref "SV48") (pin "12") (pinfunction "12_12") (pintype "passive"))
    )
    (net (code "1947") (name "unconnected-(SV48-Pad13)") (class "Default")
      (node (ref "SV48") (pin "13") (pinfunction "13_13") (pintype "passive"))
    )
    (net (code "1948") (name "unconnected-(SV48-Pad14)") (class "Default")
      (node (ref "SV48") (pin "14") (pinfunction "14_14") (pintype "passive"))
    )
    (net (code "1949") (name "unconnected-(SV48-Pad15)") (class "Default")
      (node (ref "SV48") (pin "15") (pinfunction "15_15") (pintype "passive"))
    )
    (net (code "1950") (name "unconnected-(SV48-Pad16)") (class "Default")
      (node (ref "SV48") (pin "16") (pinfunction "16_16") (pintype "passive"))
    )
    (net (code "1951") (name "unconnected-(SV48-Pad17)") (class "Default")
      (node (ref "SV48") (pin "17") (pinfunction "17_17") (pintype "passive"))
    )
    (net (code "1952") (name "unconnected-(SV48-Pad18)") (class "Default")
      (node (ref "SV48") (pin "18") (pinfunction "18_18") (pintype "passive"))
    )
    (net (code "1953") (name "unconnected-(SV48-Pad19)") (class "Default")
      (node (ref "SV48") (pin "19") (pinfunction "19_19") (pintype "passive"))
    )
    (net (code "1954") (name "unconnected-(SV48-Pad20)") (class "Default")
      (node (ref "SV48") (pin "20") (pinfunction "20_20") (pintype "passive"))
    )
    (net (code "1955") (name "unconnected-(SV48-Pad21)") (class "Default")
      (node (ref "SV48") (pin "21") (pinfunction "21_21") (pintype "passive"))
    )
    (net (code "1956") (name "unconnected-(SV48-Pad22)") (class "Default")
      (node (ref "SV48") (pin "22") (pinfunction "22_22") (pintype "passive"))
    )
    (net (code "1957") (name "unconnected-(SV48-Pad23)") (class "Default")
      (node (ref "SV48") (pin "23") (pinfunction "23_23") (pintype "passive"))
    )
    (net (code "1958") (name "unconnected-(SV48-Pad24)") (class "Default")
      (node (ref "SV48") (pin "24") (pinfunction "24_24") (pintype "passive"))
    )
    (net (code "1959") (name "unconnected-(SV48-Pad25)") (class "Default")
      (node (ref "SV48") (pin "25") (pinfunction "25_25") (pintype "passive"))
    )
    (net (code "1960") (name "unconnected-(SV48-Pad26)") (class "Default")
      (node (ref "SV48") (pin "26") (pinfunction "26_26") (pintype "passive"))
    )
    (net (code "1961") (name "unconnected-(SV48-Pad27)") (class "Default")
      (node (ref "SV48") (pin "27") (pinfunction "27_27") (pintype "passive"))
    )
    (net (code "1962") (name "unconnected-(SV48-Pad28)") (class "Default")
      (node (ref "SV48") (pin "28") (pinfunction "28_28") (pintype "passive"))
    )
    (net (code "1963") (name "unconnected-(SV48-Pad29)") (class "Default")
      (node (ref "SV48") (pin "29") (pinfunction "29_29") (pintype "passive"))
    )
    (net (code "1964") (name "unconnected-(SV48-Pad30)") (class "Default")
      (node (ref "SV48") (pin "30") (pinfunction "30_30") (pintype "passive"))
    )
    (net (code "1965") (name "unconnected-(SV48-Pad31)") (class "Default")
      (node (ref "SV48") (pin "31") (pinfunction "31_31") (pintype "passive"))
    )
    (net (code "1966") (name "unconnected-(SV48-Pad32)") (class "Default")
      (node (ref "SV48") (pin "32") (pinfunction "32_32") (pintype "passive"))
    )
    (net (code "1967") (name "unconnected-(SV48-Pad33)") (class "Default")
      (node (ref "SV48") (pin "33") (pinfunction "33_33") (pintype "passive"))
    )
    (net (code "1968") (name "unconnected-(SV48-Pad34)") (class "Default")
      (node (ref "SV48") (pin "34") (pinfunction "34_34") (pintype "passive"))
    )
    (net (code "1969") (name "unconnected-(SV48-Pad35)") (class "Default")
      (node (ref "SV48") (pin "35") (pinfunction "35_35") (pintype "passive"))
    )
    (net (code "1970") (name "unconnected-(SV48-Pad36)") (class "Default")
      (node (ref "SV48") (pin "36") (pinfunction "36_36") (pintype "passive"))
    )
    (net (code "1971") (name "unconnected-(SV49-Pad1)") (class "Default")
      (node (ref "SV49") (pin "1") (pinfunction "1_1") (pintype "passive"))
    )
    (net (code "1972") (name "unconnected-(SV49-Pad2)") (class "Default")
      (node (ref "SV49") (pin "2") (pinfunction "2_2") (pintype "passive"))
    )
    (net (code "1973") (name "unconnected-(SV49-Pad3)") (class "Default")
      (node (ref "SV49") (pin "3") (pinfunction "3_3") (pintype "passive"))
    )
    (net (code "1974") (name "unconnected-(SV49-Pad4)") (class "Default")
      (node (ref "SV49") (pin "4") (pinfunction "4_4") (pintype "passive"))
    )
    (net (code "1975") (name "unconnected-(SV49-Pad5)") (class "Default")
      (node (ref "SV49") (pin "5") (pinfunction "5_5") (pintype "passive"))
    )
    (net (code "1976") (name "unconnected-(SV49-Pad6)") (class "Default")
      (node (ref "SV49") (pin "6") (pinfunction "6_6") (pintype "passive"))
    )
    (net (code "1977") (name "unconnected-(SV50-Pad1)") (class "Default")
      (node (ref "SV50") (pin "1") (pinfunction "1_1") (pintype "passive"))
    )
    (net (code "1978") (name "unconnected-(SV50-Pad2)") (class "Default")
      (node (ref "SV50") (pin "2") (pinfunction "2_2") (pintype "passive"))
    )
    (net (code "1979") (name "unconnected-(SV50-Pad3)") (class "Default")
      (node (ref "SV50") (pin "3") (pinfunction "3_3") (pintype "passive"))
    )
    (net (code "1980") (name "unconnected-(SV50-Pad4)") (class "Default")
      (node (ref "SV50") (pin "4") (pinfunction "4_4") (pintype "passive"))
    )
    (net (code "1981") (name "unconnected-(SV50-Pad5)") (class "Default")
      (node (ref "SV50") (pin "5") (pinfunction "5_5") (pintype "passive"))
    )
    (net (code "1982") (name "unconnected-(SV50-Pad6)") (class "Default")
      (node (ref "SV50") (pin "6") (pinfunction "6_6") (pintype "passive"))
    )
    (net (code "1983") (name "unconnected-(SV51-Pad1)") (class "Default")
      (node (ref "SV51") (pin "1") (pinfunction "1_1") (pintype "passive"))
    )
    (net (code "1984") (name "unconnected-(SV51-Pad2)") (class "Default")
      (node (ref "SV51") (pin "2") (pinfunction "2_2") (pintype "passive"))
    )
    (net (code "1985") (name "unconnected-(SV51-Pad3)") (class "Default")
      (node (ref "SV51") (pin "3") (pinfunction "3_3") (pintype "passive"))
    )
    (net (code "1986") (name "unconnected-(SV51-Pad4)") (class "Default")
      (node (ref "SV51") (pin "4") (pinfunction "4_4") (pintype "passive"))
    )
    (net (code "1987") (name "unconnected-(SV51-Pad5)") (class "Default")
      (node (ref "SV51") (pin "5") (pinfunction "5_5") (pintype "passive"))
    )
    (net (code "1988") (name "unconnected-(SV51-Pad6)") (class "Default")
      (node (ref "SV51") (pin "6") (pinfunction "6_6") (pintype "passive"))
    )
    (net (code "1989") (name "unconnected-(SV52-Pad1)") (class "Default")
      (node (ref "SV52") (pin "1") (pinfunction "1_1") (pintype "passive"))
    )
    (net (code "1990") (name "unconnected-(SV52-Pad2)") (class "Default")
      (node (ref "SV52") (pin "2") (pinfunction "2_2") (pintype "passive"))
    )
    (net (code "1991") (name "unconnected-(SV52-Pad3)") (class "Default")
      (node (ref "SV52") (pin "3") (pinfunction "3_3") (pintype "passive"))
    )
    (net (code "1992") (name "unconnected-(SV52-Pad4)") (class "Default")
      (node (ref "SV52") (pin "4") (pinfunction "4_4") (pintype "passive"))
    )
    (net (code "1993") (name "unconnected-(SV52-Pad5)") (class "Default")
      (node (ref "SV52") (pin "5") (pinfunction "5_5") (pintype "passive"))
    )
    (net (code "1994") (name "unconnected-(SV52-Pad6)") (class "Default")
      (node (ref "SV52") (pin "6") (pinfunction "6_6") (pintype "passive"))
    )
    (net (code "1995") (name "unconnected-(SV53-Pad1)") (class "Default")
      (node (ref "SV53") (pin "1") (pinfunction "1_1") (pintype "passive"))
    )
    (net (code "1996") (name "unconnected-(SV53-Pad2)") (class "Default")
      (node (ref "SV53") (pin "2") (pinfunction "2_2") (pintype "passive"))
    )
    (net (code "1997") (name "unconnected-(SV53-Pad3)") (class "Default")
      (node (ref "SV53") (pin "3") (pinfunction "3_3") (pintype "passive"))
    )
    (net (code "1998") (name "unconnected-(SV53-Pad4)") (class "Default")
      (node (ref "SV53") (pin "4") (pinfunction "4_4") (pintype "passive"))
    )
    (net (code "1999") (name "unconnected-(SV53-Pad5)") (class "Default")
      (node (ref "SV53") (pin "5") (pinfunction "5_5") (pintype "passive"))
    )
    (net (code "2000") (name "unconnected-(SV53-Pad6)") (class "Default")
      (node (ref "SV53") (pin "6") (pinfunction "6_6") (pintype "passive"))
    )
    (net (code "2001") (name "unconnected-(SV54-Pad1)") (class "Default")
      (node (ref "SV54") (pin "1") (pinfunction "1_1") (pintype "passive"))
    )
    (net (code "2002") (name "unconnected-(SV54-Pad2)") (class "Default")
      (node (ref "SV54") (pin "2") (pinfunction "2_2") (pintype "passive"))
    )
    (net (code "2003") (name "unconnected-(SV54-Pad3)") (class "Default")
      (node (ref "SV54") (pin "3") (pinfunction "3_3") (pintype "passive"))
    )
    (net (code "2004") (name "unconnected-(SV54-Pad4)") (class "Default")
      (node (ref "SV54") (pin "4") (pinfunction "4_4") (pintype "passive"))
    )
    (net (code "2005") (name "unconnected-(SV54-Pad5)") (class "Default")
      (node (ref "SV54") (pin "5") (pinfunction "5_5") (pintype "passive"))
    )
    (net (code "2006") (name "unconnected-(SV54-Pad6)") (class "Default")
      (node (ref "SV54") (pin "6") (pinfunction "6_6") (pintype "passive"))
    )
    (net (code "2007") (name "unconnected-(SV55-Pad1)") (class "Default")
      (node (ref "SV55") (pin "1") (pinfunction "1_1") (pintype "passive"))
    )
    (net (code "2008") (name "unconnected-(SV55-Pad2)") (class "Default")
      (node (ref "SV55") (pin "2") (pinfunction "2_2") (pintype "passive"))
    )
    (net (code "2009") (name "unconnected-(SV55-Pad3)") (class "Default")
      (node (ref "SV55") (pin "3") (pinfunction "3_3") (pintype "passive"))
    )
    (net (code "2010") (name "unconnected-(SV55-Pad4)") (class "Default")
      (node (ref "SV55") (pin "4") (pinfunction "4_4") (pintype "passive"))
    )
    (net (code "2011") (name "unconnected-(SV55-Pad5)") (class "Default")
      (node (ref "SV55") (pin "5") (pinfunction "5_5") (pintype "passive"))
    )
    (net (code "2012") (name "unconnected-(SV55-Pad6)") (class "Default")
      (node (ref "SV55") (pin "6") (pinfunction "6_6") (pintype "passive"))
    )
    (net (code "2013") (name "unconnected-(SV56-Pad1)") (class "Default")
      (node (ref "SV56") (pin "1") (pinfunction "1_1") (pintype "passive"))
    )
    (net (code "2014") (name "unconnected-(SV56-Pad2)") (class "Default")
      (node (ref "SV56") (pin "2") (pinfunction "2_2") (pintype "passive"))
    )
    (net (code "2015") (name "unconnected-(SV56-Pad3)") (class "Default")
      (node (ref "SV56") (pin "3") (pinfunction "3_3") (pintype "passive"))
    )
    (net (code "2016") (name "unconnected-(SV56-Pad4)") (class "Default")
      (node (ref "SV56") (pin "4") (pinfunction "4_4") (pintype "passive"))
    )
    (net (code "2017") (name "unconnected-(SV56-Pad5)") (class "Default")
      (node (ref "SV56") (pin "5") (pinfunction "5_5") (pintype "passive"))
    )
    (net (code "2018") (name "unconnected-(SV56-Pad6)") (class "Default")
      (node (ref "SV56") (pin "6") (pinfunction "6_6") (pintype "passive"))
    )
    (net (code "2019") (name "unconnected-(SV57-Pad1)") (class "Default")
      (node (ref "SV57") (pin "1") (pinfunction "1_1") (pintype "passive"))
    )
    (net (code "2020") (name "unconnected-(SV57-Pad2)") (class "Default")
      (node (ref "SV57") (pin "2") (pinfunction "2_2") (pintype "passive"))
    )
    (net (code "2021") (name "unconnected-(SV57-Pad3)") (class "Default")
      (node (ref "SV57") (pin "3") (pinfunction "3_3") (pintype "passive"))
    )
    (net (code "2022") (name "unconnected-(SV57-Pad4)") (class "Default")
      (node (ref "SV57") (pin "4") (pinfunction "4_4") (pintype "passive"))
    )
    (net (code "2023") (name "unconnected-(SV57-Pad5)") (class "Default")
      (node (ref "SV57") (pin "5") (pinfunction "5_5") (pintype "passive"))
    )
    (net (code "2024") (name "unconnected-(SV57-Pad6)") (class "Default")
      (node (ref "SV57") (pin "6") (pinfunction "6_6") (pintype "passive"))
    )
    (net (code "2025") (name "unconnected-(SV58-Pad1)") (class "Default")
      (node (ref "SV58") (pin "1") (pinfunction "1_1") (pintype "passive"))
    )
    (net (code "2026") (name "unconnected-(SV58-Pad2)") (class "Default")
      (node (ref "SV58") (pin "2") (pinfunction "2_2") (pintype "passive"))
    )
    (net (code "2027") (name "unconnected-(SV58-Pad3)") (class "Default")
      (node (ref "SV58") (pin "3") (pinfunction "3_3") (pintype "passive"))
    )
    (net (code "2028") (name "unconnected-(SV58-Pad4)") (class "Default")
      (node (ref "SV58") (pin "4") (pinfunction "4_4") (pintype "passive"))
    )
    (net (code "2029") (name "unconnected-(SV58-Pad5)") (class "Default")
      (node (ref "SV58") (pin "5") (pinfunction "5_5") (pintype "passive"))
    )
    (net (code "2030") (name "unconnected-(SV58-Pad6)") (class "Default")
      (node (ref "SV58") (pin "6") (pinfunction "6_6") (pintype "passive"))
    )
    (net (code "2031") (name "unconnected-(SV59-Pad1)") (class "Default")
      (node (ref "SV59") (pin "1") (pinfunction "1_1") (pintype "passive"))
    )
    (net (code "2032") (name "unconnected-(SV59-Pad2)") (class "Default")
      (node (ref "SV59") (pin "2") (pinfunction "2_2") (pintype "passive"))
    )
    (net (code "2033") (name "unconnected-(SV59-Pad3)") (class "Default")
      (node (ref "SV59") (pin "3") (pinfunction "3_3") (pintype "passive"))
    )
    (net (code "2034") (name "unconnected-(SV59-Pad4)") (class "Default")
      (node (ref "SV59") (pin "4") (pinfunction "4_4") (pintype "passive"))
    )
    (net (code "2035") (name "unconnected-(SV59-Pad5)") (class "Default")
      (node (ref "SV59") (pin "5") (pinfunction "5_5") (pintype "passive"))
    )
    (net (code "2036") (name "unconnected-(SV59-Pad6)") (class "Default")
      (node (ref "SV59") (pin "6") (pinfunction "6_6") (pintype "passive"))
    )
    (net (code "2037") (name "unconnected-(SV60-Pad1)") (class "Default")
      (node (ref "SV60") (pin "1") (pinfunction "1_1") (pintype "passive"))
    )
    (net (code "2038") (name "unconnected-(SV60-Pad2)") (class "Default")
      (node (ref "SV60") (pin "2") (pinfunction "2_2") (pintype "passive"))
    )
    (net (code "2039") (name "unconnected-(SV60-Pad3)") (class "Default")
      (node (ref "SV60") (pin "3") (pinfunction "3_3") (pintype "passive"))
    )
    (net (code "2040") (name "unconnected-(SV60-Pad4)") (class "Default")
      (node (ref "SV60") (pin "4") (pinfunction "4_4") (pintype "passive"))
    )
    (net (code "2041") (name "unconnected-(SV60-Pad5)") (class "Default")
      (node (ref "SV60") (pin "5") (pinfunction "5_5") (pintype "passive"))
    )
    (net (code "2042") (name "unconnected-(SV60-Pad6)") (class "Default")
      (node (ref "SV60") (pin "6") (pinfunction "6_6") (pintype "passive"))
    )
    (net (code "2043") (name "unconnected-(SV61-Pad1)") (class "Default")
      (node (ref "SV61") (pin "1") (pinfunction "1_1") (pintype "passive"))
    )
    (net (code "2044") (name "unconnected-(SV61-Pad2)") (class "Default")
      (node (ref "SV61") (pin "2") (pinfunction "2_2") (pintype "passive"))
    )
    (net (code "2045") (name "unconnected-(SV61-Pad3)") (class "Default")
      (node (ref "SV61") (pin "3") (pinfunction "3_3") (pintype "passive"))
    )
    (net (code "2046") (name "unconnected-(SV61-Pad4)") (class "Default")
      (node (ref "SV61") (pin "4") (pinfunction "4_4") (pintype "passive"))
    )
    (net (code "2047") (name "unconnected-(SV61-Pad5)") (class "Default")
      (node (ref "SV61") (pin "5") (pinfunction "5_5") (pintype "passive"))
    )
    (net (code "2048") (name "unconnected-(SV61-Pad6)") (class "Default")
      (node (ref "SV61") (pin "6") (pinfunction "6_6") (pintype "passive"))
    )
    (net (code "2049") (name "unconnected-(SV62-Pad1)") (class "Default")
      (node (ref "SV62") (pin "1") (pinfunction "1_1") (pintype "passive"))
    )
    (net (code "2050") (name "unconnected-(SV62-Pad2)") (class "Default")
      (node (ref "SV62") (pin "2") (pinfunction "2_2") (pintype "passive"))
    )
    (net (code "2051") (name "unconnected-(SV62-Pad3)") (class "Default")
      (node (ref "SV62") (pin "3") (pinfunction "3_3") (pintype "passive"))
    )
    (net (code "2052") (name "unconnected-(SV62-Pad4)") (class "Default")
      (node (ref "SV62") (pin "4") (pinfunction "4_4") (pintype "passive"))
    )
    (net (code "2053") (name "unconnected-(SV62-Pad5)") (class "Default")
      (node (ref "SV62") (pin "5") (pinfunction "5_5") (pintype "passive"))
    )
    (net (code "2054") (name "unconnected-(SV62-Pad6)") (class "Default")
      (node (ref "SV62") (pin "6") (pinfunction "6_6") (pintype "passive"))
    )
    (net (code "2055") (name "unconnected-(SV63-Pad1)") (class "Default")
      (node (ref "SV63") (pin "1") (pinfunction "1_1") (pintype "passive"))
    )
    (net (code "2056") (name "unconnected-(SV63-Pad2)") (class "Default")
      (node (ref "SV63") (pin "2") (pinfunction "2_2") (pintype "passive"))
    )
    (net (code "2057") (name "unconnected-(SV63-Pad3)") (class "Default")
      (node (ref "SV63") (pin "3") (pinfunction "3_3") (pintype "passive"))
    )
    (net (code "2058") (name "unconnected-(SV63-Pad4)") (class "Default")
      (node (ref "SV63") (pin "4") (pinfunction "4_4") (pintype "passive"))
    )
    (net (code "2059") (name "unconnected-(SV63-Pad5)") (class "Default")
      (node (ref "SV63") (pin "5") (pinfunction "5_5") (pintype "passive"))
    )
    (net (code "2060") (name "unconnected-(SV63-Pad6)") (class "Default")
      (node (ref "SV63") (pin "6") (pinfunction "6_6") (pintype "passive"))
    )
    (net (code "2061") (name "unconnected-(SV64-Pad1)") (class "Default")
      (node (ref "SV64") (pin "1") (pinfunction "1_1") (pintype "passive"))
    )
    (net (code "2062") (name "unconnected-(SV64-Pad2)") (class "Default")
      (node (ref "SV64") (pin "2") (pinfunction "2_2") (pintype "passive"))
    )
    (net (code "2063") (name "unconnected-(SV64-Pad3)") (class "Default")
      (node (ref "SV64") (pin "3") (pinfunction "3_3") (pintype "passive"))
    )
    (net (code "2064") (name "unconnected-(SV64-Pad4)") (class "Default")
      (node (ref "SV64") (pin "4") (pinfunction "4_4") (pintype "passive"))
    )
    (net (code "2065") (name "unconnected-(SV64-Pad5)") (class "Default")
      (node (ref "SV64") (pin "5") (pinfunction "5_5") (pintype "passive"))
    )
    (net (code "2066") (name "unconnected-(SV64-Pad6)") (class "Default")
      (node (ref "SV64") (pin "6") (pinfunction "6_6") (pintype "passive"))
    )
    (net (code "2067") (name "unconnected-(SV65-Pad1)") (class "Default")
      (node (ref "SV65") (pin "1") (pinfunction "1_1") (pintype "passive"))
    )
    (net (code "2068") (name "unconnected-(SV65-Pad2)") (class "Default")
      (node (ref "SV65") (pin "2") (pinfunction "2_2") (pintype "passive"))
    )
    (net (code "2069") (name "unconnected-(SV65-Pad3)") (class "Default")
      (node (ref "SV65") (pin "3") (pinfunction "3_3") (pintype "passive"))
    )
    (net (code "2070") (name "unconnected-(SV65-Pad4)") (class "Default")
      (node (ref "SV65") (pin "4") (pinfunction "4_4") (pintype "passive"))
    )
    (net (code "2071") (name "unconnected-(SV65-Pad5)") (class "Default")
      (node (ref "SV65") (pin "5") (pinfunction "5_5") (pintype "passive"))
    )
    (net (code "2072") (name "unconnected-(SV65-Pad6)") (class "Default")
      (node (ref "SV65") (pin "6") (pinfunction "6_6") (pintype "passive"))
    )
    (net (code "2073") (name "unconnected-(SV65-Pad7)") (class "Default")
      (node (ref "SV65") (pin "7") (pinfunction "7_7") (pintype "passive"))
    )
    (net (code "2074") (name "unconnected-(SV65-Pad8)") (class "Default")
      (node (ref "SV65") (pin "8") (pinfunction "8_8") (pintype "passive"))
    )
    (net (code "2075") (name "unconnected-(SV65-Pad9)") (class "Default")
      (node (ref "SV65") (pin "9") (pinfunction "9_9") (pintype "passive"))
    )
    (net (code "2076") (name "unconnected-(SV65-Pad10)") (class "Default")
      (node (ref "SV65") (pin "10") (pinfunction "10_10") (pintype "passive"))
    )
    (net (code "2077") (name "unconnected-(SV65-Pad11)") (class "Default")
      (node (ref "SV65") (pin "11") (pinfunction "11_11") (pintype "passive"))
    )
    (net (code "2078") (name "unconnected-(SV65-Pad12)") (class "Default")
      (node (ref "SV65") (pin "12") (pinfunction "12_12") (pintype "passive"))
    )
    (net (code "2079") (name "unconnected-(SV65-Pad13)") (class "Default")
      (node (ref "SV65") (pin "13") (pinfunction "13_13") (pintype "passive"))
    )
    (net (code "2080") (name "unconnected-(SV65-Pad14)") (class "Default")
      (node (ref "SV65") (pin "14") (pinfunction "14_14") (pintype "passive"))
    )
    (net (code "2081") (name "unconnected-(SV65-Pad15)") (class "Default")
      (node (ref "SV65") (pin "15") (pinfunction "15_15") (pintype "passive"))
    )
    (net (code "2082") (name "unconnected-(SV65-Pad16)") (class "Default")
      (node (ref "SV65") (pin "16") (pinfunction "16_16") (pintype "passive"))
    )
    (net (code "2083") (name "unconnected-(SV65-Pad17)") (class "Default")
      (node (ref "SV65") (pin "17") (pinfunction "17_17") (pintype "passive"))
    )
    (net (code "2084") (name "unconnected-(SV65-Pad18)") (class "Default")
      (node (ref "SV65") (pin "18") (pinfunction "18_18") (pintype "passive"))
    )
    (net (code "2085") (name "unconnected-(SV65-Pad19)") (class "Default")
      (node (ref "SV65") (pin "19") (pinfunction "19_19") (pintype "passive"))
    )
    (net (code "2086") (name "unconnected-(SV65-Pad20)") (class "Default")
      (node (ref "SV65") (pin "20") (pinfunction "20_20") (pintype "passive"))
    )
    (net (code "2087") (name "unconnected-(SV65-Pad21)") (class "Default")
      (node (ref "SV65") (pin "21") (pinfunction "21_21") (pintype "passive"))
    )
    (net (code "2088") (name "unconnected-(SV65-Pad22)") (class "Default")
      (node (ref "SV65") (pin "22") (pinfunction "22_22") (pintype "passive"))
    )
    (net (code "2089") (name "unconnected-(SV65-Pad23)") (class "Default")
      (node (ref "SV65") (pin "23") (pinfunction "23_23") (pintype "passive"))
    )
    (net (code "2090") (name "unconnected-(SV65-Pad24)") (class "Default")
      (node (ref "SV65") (pin "24") (pinfunction "24_24") (pintype "passive"))
    )
    (net (code "2091") (name "unconnected-(SV65-Pad25)") (class "Default")
      (node (ref "SV65") (pin "25") (pinfunction "25_25") (pintype "passive"))
    )
    (net (code "2092") (name "unconnected-(SV65-Pad26)") (class "Default")
      (node (ref "SV65") (pin "26") (pinfunction "26_26") (pintype "passive"))
    )
    (net (code "2093") (name "unconnected-(SV65-Pad27)") (class "Default")
      (node (ref "SV65") (pin "27") (pinfunction "27_27") (pintype "passive"))
    )
    (net (code "2094") (name "unconnected-(SV65-Pad28)") (class "Default")
      (node (ref "SV65") (pin "28") (pinfunction "28_28") (pintype "passive"))
    )
    (net (code "2095") (name "unconnected-(SV65-Pad29)") (class "Default")
      (node (ref "SV65") (pin "29") (pinfunction "29_29") (pintype "passive"))
    )
    (net (code "2096") (name "unconnected-(SV65-Pad30)") (class "Default")
      (node (ref "SV65") (pin "30") (pinfunction "30_30") (pintype "passive"))
    )
    (net (code "2097") (name "unconnected-(SV65-Pad31)") (class "Default")
      (node (ref "SV65") (pin "31") (pinfunction "31_31") (pintype "passive"))
    )
    (net (code "2098") (name "unconnected-(SV65-Pad32)") (class "Default")
      (node (ref "SV65") (pin "32") (pinfunction "32_32") (pintype "passive"))
    )
    (net (code "2099") (name "unconnected-(SV65-Pad33)") (class "Default")
      (node (ref "SV65") (pin "33") (pinfunction "33_33") (pintype "passive"))
    )
    (net (code "2100") (name "unconnected-(SV65-Pad34)") (class "Default")
      (node (ref "SV65") (pin "34") (pinfunction "34_34") (pintype "passive"))
    )
    (net (code "2101") (name "unconnected-(SV65-Pad35)") (class "Default")
      (node (ref "SV65") (pin "35") (pinfunction "35_35") (pintype "passive"))
    )
    (net (code "2102") (name "unconnected-(SV65-Pad36)") (class "Default")
      (node (ref "SV65") (pin "36") (pinfunction "36_36") (pintype "passive"))
    )
    (net (code "2103") (name "unconnected-(SV66-Pad1)") (class "Default")
      (node (ref "SV66") (pin "1") (pinfunction "1_1") (pintype "passive"))
    )
    (net (code "2104") (name "unconnected-(SV66-Pad2)") (class "Default")
      (node (ref "SV66") (pin "2") (pinfunction "2_2") (pintype "passive"))
    )
    (net (code "2105") (name "unconnected-(SV66-Pad3)") (class "Default")
      (node (ref "SV66") (pin "3") (pinfunction "3_3") (pintype "passive"))
    )
    (net (code "2106") (name "unconnected-(SV66-Pad4)") (class "Default")
      (node (ref "SV66") (pin "4") (pinfunction "4_4") (pintype "passive"))
    )
    (net (code "2107") (name "unconnected-(SV66-Pad5)") (class "Default")
      (node (ref "SV66") (pin "5") (pinfunction "5_5") (pintype "passive"))
    )
    (net (code "2108") (name "unconnected-(SV66-Pad6)") (class "Default")
      (node (ref "SV66") (pin "6") (pinfunction "6_6") (pintype "passive"))
    )
    (net (code "2109") (name "unconnected-(SV67-Pad1)") (class "Default")
      (node (ref "SV67") (pin "1") (pinfunction "1_1") (pintype "passive"))
    )
    (net (code "2110") (name "unconnected-(SV67-Pad2)") (class "Default")
      (node (ref "SV67") (pin "2") (pinfunction "2_2") (pintype "passive"))
    )
    (net (code "2111") (name "unconnected-(SV67-Pad3)") (class "Default")
      (node (ref "SV67") (pin "3") (pinfunction "3_3") (pintype "passive"))
    )
    (net (code "2112") (name "unconnected-(SV67-Pad4)") (class "Default")
      (node (ref "SV67") (pin "4") (pinfunction "4_4") (pintype "passive"))
    )
    (net (code "2113") (name "unconnected-(SV67-Pad5)") (class "Default")
      (node (ref "SV67") (pin "5") (pinfunction "5_5") (pintype "passive"))
    )
    (net (code "2114") (name "unconnected-(SV67-Pad6)") (class "Default")
      (node (ref "SV67") (pin "6") (pinfunction "6_6") (pintype "passive"))
    )
    (net (code "2115") (name "unconnected-(SV68-Pad1)") (class "Default")
      (node (ref "SV68") (pin "1") (pinfunction "1_1") (pintype "passive"))
    )
    (net (code "2116") (name "unconnected-(SV68-Pad2)") (class "Default")
      (node (ref "SV68") (pin "2") (pinfunction "2_2") (pintype "passive"))
    )
    (net (code "2117") (name "unconnected-(SV68-Pad3)") (class "Default")
      (node (ref "SV68") (pin "3") (pinfunction "3_3") (pintype "passive"))
    )
    (net (code "2118") (name "unconnected-(SV68-Pad4)") (class "Default")
      (node (ref "SV68") (pin "4") (pinfunction "4_4") (pintype "passive"))
    )
    (net (code "2119") (name "unconnected-(SV68-Pad5)") (class "Default")
      (node (ref "SV68") (pin "5") (pinfunction "5_5") (pintype "passive"))
    )
    (net (code "2120") (name "unconnected-(SV68-Pad6)") (class "Default")
      (node (ref "SV68") (pin "6") (pinfunction "6_6") (pintype "passive"))
    )
    (net (code "2121") (name "unconnected-(SV69-Pad1)") (class "Default")
      (node (ref "SV69") (pin "1") (pinfunction "1_1") (pintype "passive"))
    )
    (net (code "2122") (name "unconnected-(SV69-Pad2)") (class "Default")
      (node (ref "SV69") (pin "2") (pinfunction "2_2") (pintype "passive"))
    )
    (net (code "2123") (name "unconnected-(SV69-Pad3)") (class "Default")
      (node (ref "SV69") (pin "3") (pinfunction "3_3") (pintype "passive"))
    )
    (net (code "2124") (name "unconnected-(SV69-Pad4)") (class "Default")
      (node (ref "SV69") (pin "4") (pinfunction "4_4") (pintype "passive"))
    )
    (net (code "2125") (name "unconnected-(SV69-Pad5)") (class "Default")
      (node (ref "SV69") (pin "5") (pinfunction "5_5") (pintype "passive"))
    )
    (net (code "2126") (name "unconnected-(SV69-Pad6)") (class "Default")
      (node (ref "SV69") (pin "6") (pinfunction "6_6") (pintype "passive"))
    )
    (net (code "2127") (name "unconnected-(SV69-Pad7)") (class "Default")
      (node (ref "SV69") (pin "7") (pinfunction "7_7") (pintype "passive"))
    )
    (net (code "2128") (name "unconnected-(SV69-Pad8)") (class "Default")
      (node (ref "SV69") (pin "8") (pinfunction "8_8") (pintype "passive"))
    )
    (net (code "2129") (name "unconnected-(SV69-Pad9)") (class "Default")
      (node (ref "SV69") (pin "9") (pinfunction "9_9") (pintype "passive"))
    )
    (net (code "2130") (name "unconnected-(SV69-Pad10)") (class "Default")
      (node (ref "SV69") (pin "10") (pinfunction "10_10") (pintype "passive"))
    )
    (net (code "2131") (name "unconnected-(SV69-Pad11)") (class "Default")
      (node (ref "SV69") (pin "11") (pinfunction "11_11") (pintype "passive"))
    )
    (net (code "2132") (name "unconnected-(SV69-Pad12)") (class "Default")
      (node (ref "SV69") (pin "12") (pinfunction "12_12") (pintype "passive"))
    )
    (net (code "2133") (name "unconnected-(SV69-Pad13)") (class "Default")
      (node (ref "SV69") (pin "13") (pinfunction "13_13") (pintype "passive"))
    )
    (net (code "2134") (name "unconnected-(SV69-Pad14)") (class "Default")
      (node (ref "SV69") (pin "14") (pinfunction "14_14") (pintype "passive"))
    )
    (net (code "2135") (name "unconnected-(SV69-Pad15)") (class "Default")
      (node (ref "SV69") (pin "15") (pinfunction "15_15") (pintype "passive"))
    )
    (net (code "2136") (name "unconnected-(SV69-Pad16)") (class "Default")
      (node (ref "SV69") (pin "16") (pinfunction "16_16") (pintype "passive"))
    )
    (net (code "2137") (name "unconnected-(SV69-Pad17)") (class "Default")
      (node (ref "SV69") (pin "17") (pinfunction "17_17") (pintype "passive"))
    )
    (net (code "2138") (name "unconnected-(SV69-Pad18)") (class "Default")
      (node (ref "SV69") (pin "18") (pinfunction "18_18") (pintype "passive"))
    )
    (net (code "2139") (name "unconnected-(SV69-Pad19)") (class "Default")
      (node (ref "SV69") (pin "19") (pinfunction "19_19") (pintype "passive"))
    )
    (net (code "2140") (name "unconnected-(SV69-Pad20)") (class "Default")
      (node (ref "SV69") (pin "20") (pinfunction "20_20") (pintype "passive"))
    )
    (net (code "2141") (name "unconnected-(SV69-Pad21)") (class "Default")
      (node (ref "SV69") (pin "21") (pinfunction "21_21") (pintype "passive"))
    )
    (net (code "2142") (name "unconnected-(SV69-Pad22)") (class "Default")
      (node (ref "SV69") (pin "22") (pinfunction "22_22") (pintype "passive"))
    )
    (net (code "2143") (name "unconnected-(SV69-Pad23)") (class "Default")
      (node (ref "SV69") (pin "23") (pinfunction "23_23") (pintype "passive"))
    )
    (net (code "2144") (name "unconnected-(SV69-Pad24)") (class "Default")
      (node (ref "SV69") (pin "24") (pinfunction "24_24") (pintype "passive"))
    )
    (net (code "2145") (name "unconnected-(SV69-Pad25)") (class "Default")
      (node (ref "SV69") (pin "25") (pinfunction "25_25") (pintype "passive"))
    )
    (net (code "2146") (name "unconnected-(SV69-Pad26)") (class "Default")
      (node (ref "SV69") (pin "26") (pinfunction "26_26") (pintype "passive"))
    )
    (net (code "2147") (name "unconnected-(SV69-Pad27)") (class "Default")
      (node (ref "SV69") (pin "27") (pinfunction "27_27") (pintype "passive"))
    )
    (net (code "2148") (name "unconnected-(SV69-Pad28)") (class "Default")
      (node (ref "SV69") (pin "28") (pinfunction "28_28") (pintype "passive"))
    )
    (net (code "2149") (name "unconnected-(SV69-Pad29)") (class "Default")
      (node (ref "SV69") (pin "29") (pinfunction "29_29") (pintype "passive"))
    )
    (net (code "2150") (name "unconnected-(SV69-Pad30)") (class "Default")
      (node (ref "SV69") (pin "30") (pinfunction "30_30") (pintype "passive"))
    )
    (net (code "2151") (name "unconnected-(SV69-Pad31)") (class "Default")
      (node (ref "SV69") (pin "31") (pinfunction "31_31") (pintype "passive"))
    )
    (net (code "2152") (name "unconnected-(SV69-Pad32)") (class "Default")
      (node (ref "SV69") (pin "32") (pinfunction "32_32") (pintype "passive"))
    )
    (net (code "2153") (name "unconnected-(SV69-Pad33)") (class "Default")
      (node (ref "SV69") (pin "33") (pinfunction "33_33") (pintype "passive"))
    )
    (net (code "2154") (name "unconnected-(SV69-Pad34)") (class "Default")
      (node (ref "SV69") (pin "34") (pinfunction "34_34") (pintype "passive"))
    )
    (net (code "2155") (name "unconnected-(SV69-Pad35)") (class "Default")
      (node (ref "SV69") (pin "35") (pinfunction "35_35") (pintype "passive"))
    )
    (net (code "2156") (name "unconnected-(SV69-Pad36)") (class "Default")
      (node (ref "SV69") (pin "36") (pinfunction "36_36") (pintype "passive"))
    )
    (net (code "2157") (name "unconnected-(SV70-Pad1)") (class "Default")
      (node (ref "SV70") (pin "1") (pinfunction "1_1") (pintype "passive"))
    )
    (net (code "2158") (name "unconnected-(SV70-Pad2)") (class "Default")
      (node (ref "SV70") (pin "2") (pinfunction "2_2") (pintype "passive"))
    )
    (net (code "2159") (name "unconnected-(SV70-Pad3)") (class "Default")
      (node (ref "SV70") (pin "3") (pinfunction "3_3") (pintype "passive"))
    )
    (net (code "2160") (name "unconnected-(SV70-Pad4)") (class "Default")
      (node (ref "SV70") (pin "4") (pinfunction "4_4") (pintype "passive"))
    )
    (net (code "2161") (name "unconnected-(SV70-Pad5)") (class "Default")
      (node (ref "SV70") (pin "5") (pinfunction "5_5") (pintype "passive"))
    )
    (net (code "2162") (name "unconnected-(SV70-Pad6)") (class "Default")
      (node (ref "SV70") (pin "6") (pinfunction "6_6") (pintype "passive"))
    )
    (net (code "2163") (name "unconnected-(SV70-Pad7)") (class "Default")
      (node (ref "SV70") (pin "7") (pinfunction "7_7") (pintype "passive"))
    )
    (net (code "2164") (name "unconnected-(SV70-Pad8)") (class "Default")
      (node (ref "SV70") (pin "8") (pinfunction "8_8") (pintype "passive"))
    )
    (net (code "2165") (name "unconnected-(SV70-Pad9)") (class "Default")
      (node (ref "SV70") (pin "9") (pinfunction "9_9") (pintype "passive"))
    )
    (net (code "2166") (name "unconnected-(SV70-Pad10)") (class "Default")
      (node (ref "SV70") (pin "10") (pinfunction "10_10") (pintype "passive"))
    )
    (net (code "2167") (name "unconnected-(SV70-Pad11)") (class "Default")
      (node (ref "SV70") (pin "11") (pinfunction "11_11") (pintype "passive"))
    )
    (net (code "2168") (name "unconnected-(SV70-Pad12)") (class "Default")
      (node (ref "SV70") (pin "12") (pinfunction "12_12") (pintype "passive"))
    )
    (net (code "2169") (name "unconnected-(SV70-Pad13)") (class "Default")
      (node (ref "SV70") (pin "13") (pinfunction "13_13") (pintype "passive"))
    )
    (net (code "2170") (name "unconnected-(SV70-Pad14)") (class "Default")
      (node (ref "SV70") (pin "14") (pinfunction "14_14") (pintype "passive"))
    )
    (net (code "2171") (name "unconnected-(SV70-Pad15)") (class "Default")
      (node (ref "SV70") (pin "15") (pinfunction "15_15") (pintype "passive"))
    )
    (net (code "2172") (name "unconnected-(SV70-Pad16)") (class "Default")
      (node (ref "SV70") (pin "16") (pinfunction "16_16") (pintype "passive"))
    )
    (net (code "2173") (name "unconnected-(SV70-Pad17)") (class "Default")
      (node (ref "SV70") (pin "17") (pinfunction "17_17") (pintype "passive"))
    )
    (net (code "2174") (name "unconnected-(SV70-Pad18)") (class "Default")
      (node (ref "SV70") (pin "18") (pinfunction "18_18") (pintype "passive"))
    )
    (net (code "2175") (name "unconnected-(SV70-Pad19)") (class "Default")
      (node (ref "SV70") (pin "19") (pinfunction "19_19") (pintype "passive"))
    )
    (net (code "2176") (name "unconnected-(SV70-Pad20)") (class "Default")
      (node (ref "SV70") (pin "20") (pinfunction "20_20") (pintype "passive"))
    )
    (net (code "2177") (name "unconnected-(SV70-Pad21)") (class "Default")
      (node (ref "SV70") (pin "21") (pinfunction "21_21") (pintype "passive"))
    )
    (net (code "2178") (name "unconnected-(SV70-Pad22)") (class "Default")
      (node (ref "SV70") (pin "22") (pinfunction "22_22") (pintype "passive"))
    )
    (net (code "2179") (name "unconnected-(SV70-Pad23)") (class "Default")
      (node (ref "SV70") (pin "23") (pinfunction "23_23") (pintype "passive"))
    )
    (net (code "2180") (name "unconnected-(SV70-Pad24)") (class "Default")
      (node (ref "SV70") (pin "24") (pinfunction "24_24") (pintype "passive"))
    )
    (net (code "2181") (name "unconnected-(SV70-Pad25)") (class "Default")
      (node (ref "SV70") (pin "25") (pinfunction "25_25") (pintype "passive"))
    )
    (net (code "2182") (name "unconnected-(SV70-Pad26)") (class "Default")
      (node (ref "SV70") (pin "26") (pinfunction "26_26") (pintype "passive"))
    )
    (net (code "2183") (name "unconnected-(SV70-Pad27)") (class "Default")
      (node (ref "SV70") (pin "27") (pinfunction "27_27") (pintype "passive"))
    )
    (net (code "2184") (name "unconnected-(SV70-Pad28)") (class "Default")
      (node (ref "SV70") (pin "28") (pinfunction "28_28") (pintype "passive"))
    )
    (net (code "2185") (name "unconnected-(SV70-Pad29)") (class "Default")
      (node (ref "SV70") (pin "29") (pinfunction "29_29") (pintype "passive"))
    )
    (net (code "2186") (name "unconnected-(SV70-Pad30)") (class "Default")
      (node (ref "SV70") (pin "30") (pinfunction "30_30") (pintype "passive"))
    )
    (net (code "2187") (name "unconnected-(SV70-Pad31)") (class "Default")
      (node (ref "SV70") (pin "31") (pinfunction "31_31") (pintype "passive"))
    )
    (net (code "2188") (name "unconnected-(SV70-Pad32)") (class "Default")
      (node (ref "SV70") (pin "32") (pinfunction "32_32") (pintype "passive"))
    )
    (net (code "2189") (name "unconnected-(SV70-Pad33)") (class "Default")
      (node (ref "SV70") (pin "33") (pinfunction "33_33") (pintype "passive"))
    )
    (net (code "2190") (name "unconnected-(SV70-Pad34)") (class "Default")
      (node (ref "SV70") (pin "34") (pinfunction "34_34") (pintype "passive"))
    )
    (net (code "2191") (name "unconnected-(SV70-Pad35)") (class "Default")
      (node (ref "SV70") (pin "35") (pinfunction "35_35") (pintype "passive"))
    )
    (net (code "2192") (name "unconnected-(SV70-Pad36)") (class "Default")
      (node (ref "SV70") (pin "36") (pinfunction "36_36") (pintype "passive"))
    )
    (net (code "2193") (name "unconnected-(SV70-Pad37)") (class "Default")
      (node (ref "SV70") (pin "37") (pinfunction "37_37") (pintype "passive"))
    )
    (net (code "2194") (name "unconnected-(SV70-Pad38)") (class "Default")
      (node (ref "SV70") (pin "38") (pinfunction "38_38") (pintype "passive"))
    )
    (net (code "2195") (name "unconnected-(SV70-Pad39)") (class "Default")
      (node (ref "SV70") (pin "39") (pinfunction "39_39") (pintype "passive"))
    )
    (net (code "2196") (name "unconnected-(SV70-Pad40)") (class "Default")
      (node (ref "SV70") (pin "40") (pinfunction "40_40") (pintype "passive"))
    )
    (net (code "2197") (name "unconnected-(SV71-Pad1)") (class "Default")
      (node (ref "SV71") (pin "1") (pinfunction "1_1") (pintype "passive"))
    )
    (net (code "2198") (name "unconnected-(SV71-Pad2)") (class "Default")
      (node (ref "SV71") (pin "2") (pinfunction "2_2") (pintype "passive"))
    )
    (net (code "2199") (name "unconnected-(SV71-Pad3)") (class "Default")
      (node (ref "SV71") (pin "3") (pinfunction "3_3") (pintype "passive"))
    )
    (net (code "2200") (name "unconnected-(SV71-Pad4)") (class "Default")
      (node (ref "SV71") (pin "4") (pinfunction "4_4") (pintype "passive"))
    )
    (net (code "2201") (name "unconnected-(SV71-Pad5)") (class "Default")
      (node (ref "SV71") (pin "5") (pinfunction "5_5") (pintype "passive"))
    )
    (net (code "2202") (name "unconnected-(SV71-Pad6)") (class "Default")
      (node (ref "SV71") (pin "6") (pinfunction "6_6") (pintype "passive"))
    )
    (net (code "2203") (name "unconnected-(SV71-Pad7)") (class "Default")
      (node (ref "SV71") (pin "7") (pinfunction "7_7") (pintype "passive"))
    )
    (net (code "2204") (name "unconnected-(SV71-Pad8)") (class "Default")
      (node (ref "SV71") (pin "8") (pinfunction "8_8") (pintype "passive"))
    )
    (net (code "2205") (name "unconnected-(SV71-Pad9)") (class "Default")
      (node (ref "SV71") (pin "9") (pinfunction "9_9") (pintype "passive"))
    )
    (net (code "2206") (name "unconnected-(SV71-Pad10)") (class "Default")
      (node (ref "SV71") (pin "10") (pinfunction "10_10") (pintype "passive"))
    )
    (net (code "2207") (name "unconnected-(SV71-Pad11)") (class "Default")
      (node (ref "SV71") (pin "11") (pinfunction "11_11") (pintype "passive"))
    )
    (net (code "2208") (name "unconnected-(SV71-Pad12)") (class "Default")
      (node (ref "SV71") (pin "12") (pinfunction "12_12") (pintype "passive"))
    )
    (net (code "2209") (name "unconnected-(SV71-Pad13)") (class "Default")
      (node (ref "SV71") (pin "13") (pinfunction "13_13") (pintype "passive"))
    )
    (net (code "2210") (name "unconnected-(SV71-Pad14)") (class "Default")
      (node (ref "SV71") (pin "14") (pinfunction "14_14") (pintype "passive"))
    )
    (net (code "2211") (name "unconnected-(SV71-Pad15)") (class "Default")
      (node (ref "SV71") (pin "15") (pinfunction "15_15") (pintype "passive"))
    )
    (net (code "2212") (name "unconnected-(SV71-Pad16)") (class "Default")
      (node (ref "SV71") (pin "16") (pinfunction "16_16") (pintype "passive"))
    )
    (net (code "2213") (name "unconnected-(SV71-Pad17)") (class "Default")
      (node (ref "SV71") (pin "17") (pinfunction "17_17") (pintype "passive"))
    )
    (net (code "2214") (name "unconnected-(SV71-Pad18)") (class "Default")
      (node (ref "SV71") (pin "18") (pinfunction "18_18") (pintype "passive"))
    )
    (net (code "2215") (name "unconnected-(SV71-Pad19)") (class "Default")
      (node (ref "SV71") (pin "19") (pinfunction "19_19") (pintype "passive"))
    )
    (net (code "2216") (name "unconnected-(SV71-Pad20)") (class "Default")
      (node (ref "SV71") (pin "20") (pinfunction "20_20") (pintype "passive"))
    )
    (net (code "2217") (name "unconnected-(SV71-Pad21)") (class "Default")
      (node (ref "SV71") (pin "21") (pinfunction "21_21") (pintype "passive"))
    )
    (net (code "2218") (name "unconnected-(SV71-Pad22)") (class "Default")
      (node (ref "SV71") (pin "22") (pinfunction "22_22") (pintype "passive"))
    )
    (net (code "2219") (name "unconnected-(SV71-Pad23)") (class "Default")
      (node (ref "SV71") (pin "23") (pinfunction "23_23") (pintype "passive"))
    )
    (net (code "2220") (name "unconnected-(SV71-Pad24)") (class "Default")
      (node (ref "SV71") (pin "24") (pinfunction "24_24") (pintype "passive"))
    )
    (net (code "2221") (name "unconnected-(SV71-Pad25)") (class "Default")
      (node (ref "SV71") (pin "25") (pinfunction "25_25") (pintype "passive"))
    )
    (net (code "2222") (name "unconnected-(SV71-Pad26)") (class "Default")
      (node (ref "SV71") (pin "26") (pinfunction "26_26") (pintype "passive"))
    )
    (net (code "2223") (name "unconnected-(SV71-Pad27)") (class "Default")
      (node (ref "SV71") (pin "27") (pinfunction "27_27") (pintype "passive"))
    )
    (net (code "2224") (name "unconnected-(SV71-Pad28)") (class "Default")
      (node (ref "SV71") (pin "28") (pinfunction "28_28") (pintype "passive"))
    )
    (net (code "2225") (name "unconnected-(SV71-Pad29)") (class "Default")
      (node (ref "SV71") (pin "29") (pinfunction "29_29") (pintype "passive"))
    )
    (net (code "2226") (name "unconnected-(SV71-Pad30)") (class "Default")
      (node (ref "SV71") (pin "30") (pinfunction "30_30") (pintype "passive"))
    )
    (net (code "2227") (name "unconnected-(SV71-Pad31)") (class "Default")
      (node (ref "SV71") (pin "31") (pinfunction "31_31") (pintype "passive"))
    )
    (net (code "2228") (name "unconnected-(SV71-Pad32)") (class "Default")
      (node (ref "SV71") (pin "32") (pinfunction "32_32") (pintype "passive"))
    )
    (net (code "2229") (name "unconnected-(SV71-Pad33)") (class "Default")
      (node (ref "SV71") (pin "33") (pinfunction "33_33") (pintype "passive"))
    )
    (net (code "2230") (name "unconnected-(SV71-Pad34)") (class "Default")
      (node (ref "SV71") (pin "34") (pinfunction "34_34") (pintype "passive"))
    )
    (net (code "2231") (name "unconnected-(SV71-Pad35)") (class "Default")
      (node (ref "SV71") (pin "35") (pinfunction "35_35") (pintype "passive"))
    )
    (net (code "2232") (name "unconnected-(SV71-Pad36)") (class "Default")
      (node (ref "SV71") (pin "36") (pinfunction "36_36") (pintype "passive"))
    )
    (net (code "2233") (name "unconnected-(SV71-Pad37)") (class "Default")
      (node (ref "SV71") (pin "37") (pinfunction "37_37") (pintype "passive"))
    )
    (net (code "2234") (name "unconnected-(SV71-Pad38)") (class "Default")
      (node (ref "SV71") (pin "38") (pinfunction "38_38") (pintype "passive"))
    )
    (net (code "2235") (name "unconnected-(SV71-Pad39)") (class "Default")
      (node (ref "SV71") (pin "39") (pinfunction "39_39") (pintype "passive"))
    )
    (net (code "2236") (name "unconnected-(SV71-Pad40)") (class "Default")
      (node (ref "SV71") (pin "40") (pinfunction "40_40") (pintype "passive"))
    )
    (net (code "2237") (name "unconnected-(SV72-Pad1)") (class "Default")
      (node (ref "SV72") (pin "1") (pinfunction "1_1") (pintype "passive"))
    )
    (net (code "2238") (name "unconnected-(SV72-Pad2)") (class "Default")
      (node (ref "SV72") (pin "2") (pinfunction "2_2") (pintype "passive"))
    )
    (net (code "2239") (name "unconnected-(SV72-Pad3)") (class "Default")
      (node (ref "SV72") (pin "3") (pinfunction "3_3") (pintype "passive"))
    )
    (net (code "2240") (name "unconnected-(SV72-Pad4)") (class "Default")
      (node (ref "SV72") (pin "4") (pinfunction "4_4") (pintype "passive"))
    )
    (net (code "2241") (name "unconnected-(SV72-Pad5)") (class "Default")
      (node (ref "SV72") (pin "5") (pinfunction "5_5") (pintype "passive"))
    )
    (net (code "2242") (name "unconnected-(SV72-Pad6)") (class "Default")
      (node (ref "SV72") (pin "6") (pinfunction "6_6") (pintype "passive"))
    )
    (net (code "2243") (name "unconnected-(SV72-Pad7)") (class "Default")
      (node (ref "SV72") (pin "7") (pinfunction "7_7") (pintype "passive"))
    )
    (net (code "2244") (name "unconnected-(SV72-Pad8)") (class "Default")
      (node (ref "SV72") (pin "8") (pinfunction "8_8") (pintype "passive"))
    )
    (net (code "2245") (name "unconnected-(SV72-Pad9)") (class "Default")
      (node (ref "SV72") (pin "9") (pinfunction "9_9") (pintype "passive"))
    )
    (net (code "2246") (name "unconnected-(SV72-Pad10)") (class "Default")
      (node (ref "SV72") (pin "10") (pinfunction "10_10") (pintype "passive"))
    )
    (net (code "2247") (name "unconnected-(SV72-Pad11)") (class "Default")
      (node (ref "SV72") (pin "11") (pinfunction "11_11") (pintype "passive"))
    )
    (net (code "2248") (name "unconnected-(SV72-Pad12)") (class "Default")
      (node (ref "SV72") (pin "12") (pinfunction "12_12") (pintype "passive"))
    )
    (net (code "2249") (name "unconnected-(SV72-Pad13)") (class "Default")
      (node (ref "SV72") (pin "13") (pinfunction "13_13") (pintype "passive"))
    )
    (net (code "2250") (name "unconnected-(SV72-Pad14)") (class "Default")
      (node (ref "SV72") (pin "14") (pinfunction "14_14") (pintype "passive"))
    )
    (net (code "2251") (name "unconnected-(SV72-Pad15)") (class "Default")
      (node (ref "SV72") (pin "15") (pinfunction "15_15") (pintype "passive"))
    )
    (net (code "2252") (name "unconnected-(SV72-Pad16)") (class "Default")
      (node (ref "SV72") (pin "16") (pinfunction "16_16") (pintype "passive"))
    )
    (net (code "2253") (name "unconnected-(SV72-Pad17)") (class "Default")
      (node (ref "SV72") (pin "17") (pinfunction "17_17") (pintype "passive"))
    )
    (net (code "2254") (name "unconnected-(SV72-Pad18)") (class "Default")
      (node (ref "SV72") (pin "18") (pinfunction "18_18") (pintype "passive"))
    )
    (net (code "2255") (name "unconnected-(SV72-Pad19)") (class "Default")
      (node (ref "SV72") (pin "19") (pinfunction "19_19") (pintype "passive"))
    )
    (net (code "2256") (name "unconnected-(SV72-Pad20)") (class "Default")
      (node (ref "SV72") (pin "20") (pinfunction "20_20") (pintype "passive"))
    )
    (net (code "2257") (name "unconnected-(SV72-Pad21)") (class "Default")
      (node (ref "SV72") (pin "21") (pinfunction "21_21") (pintype "passive"))
    )
    (net (code "2258") (name "unconnected-(SV72-Pad22)") (class "Default")
      (node (ref "SV72") (pin "22") (pinfunction "22_22") (pintype "passive"))
    )
    (net (code "2259") (name "unconnected-(SV72-Pad23)") (class "Default")
      (node (ref "SV72") (pin "23") (pinfunction "23_23") (pintype "passive"))
    )
    (net (code "2260") (name "unconnected-(SV72-Pad24)") (class "Default")
      (node (ref "SV72") (pin "24") (pinfunction "24_24") (pintype "passive"))
    )
    (net (code "2261") (name "unconnected-(SV72-Pad25)") (class "Default")
      (node (ref "SV72") (pin "25") (pinfunction "25_25") (pintype "passive"))
    )
    (net (code "2262") (name "unconnected-(SV72-Pad26)") (class "Default")
      (node (ref "SV72") (pin "26") (pinfunction "26_26") (pintype "passive"))
    )
    (net (code "2263") (name "unconnected-(SV72-Pad27)") (class "Default")
      (node (ref "SV72") (pin "27") (pinfunction "27_27") (pintype "passive"))
    )
    (net (code "2264") (name "unconnected-(SV72-Pad28)") (class "Default")
      (node (ref "SV72") (pin "28") (pinfunction "28_28") (pintype "passive"))
    )
    (net (code "2265") (name "unconnected-(SV72-Pad29)") (class "Default")
      (node (ref "SV72") (pin "29") (pinfunction "29_29") (pintype "passive"))
    )
    (net (code "2266") (name "unconnected-(SV72-Pad30)") (class "Default")
      (node (ref "SV72") (pin "30") (pinfunction "30_30") (pintype "passive"))
    )
    (net (code "2267") (name "unconnected-(SV72-Pad31)") (class "Default")
      (node (ref "SV72") (pin "31") (pinfunction "31_31") (pintype "passive"))
    )
    (net (code "2268") (name "unconnected-(SV72-Pad32)") (class "Default")
      (node (ref "SV72") (pin "32") (pinfunction "32_32") (pintype "passive"))
    )
    (net (code "2269") (name "unconnected-(SV72-Pad33)") (class "Default")
      (node (ref "SV72") (pin "33") (pinfunction "33_33") (pintype "passive"))
    )
    (net (code "2270") (name "unconnected-(SV72-Pad34)") (class "Default")
      (node (ref "SV72") (pin "34") (pinfunction "34_34") (pintype "passive"))
    )
    (net (code "2271") (name "unconnected-(SV72-Pad35)") (class "Default")
      (node (ref "SV72") (pin "35") (pinfunction "35_35") (pintype "passive"))
    )
    (net (code "2272") (name "unconnected-(SV72-Pad36)") (class "Default")
      (node (ref "SV72") (pin "36") (pinfunction "36_36") (pintype "passive"))
    )
    (net (code "2273") (name "unconnected-(SV72-Pad37)") (class "Default")
      (node (ref "SV72") (pin "37") (pinfunction "37_37") (pintype "passive"))
    )
    (net (code "2274") (name "unconnected-(SV72-Pad38)") (class "Default")
      (node (ref "SV72") (pin "38") (pinfunction "38_38") (pintype "passive"))
    )
    (net (code "2275") (name "unconnected-(SV72-Pad39)") (class "Default")
      (node (ref "SV72") (pin "39") (pinfunction "39_39") (pintype "passive"))
    )
    (net (code "2276") (name "unconnected-(SV72-Pad40)") (class "Default")
      (node (ref "SV72") (pin "40") (pinfunction "40_40") (pintype "passive"))
    )
    (net (code "2277") (name "unconnected-(SV73-Pad1)") (class "Default")
      (node (ref "SV73") (pin "1") (pinfunction "1_1") (pintype "passive"))
    )
    (net (code "2278") (name "unconnected-(SV73-Pad2)") (class "Default")
      (node (ref "SV73") (pin "2") (pinfunction "2_2") (pintype "passive"))
    )
    (net (code "2279") (name "unconnected-(SV73-Pad3)") (class "Default")
      (node (ref "SV73") (pin "3") (pinfunction "3_3") (pintype "passive"))
    )
    (net (code "2280") (name "unconnected-(SV73-Pad4)") (class "Default")
      (node (ref "SV73") (pin "4") (pinfunction "4_4") (pintype "passive"))
    )
    (net (code "2281") (name "unconnected-(SV73-Pad5)") (class "Default")
      (node (ref "SV73") (pin "5") (pinfunction "5_5") (pintype "passive"))
    )
    (net (code "2282") (name "unconnected-(SV73-Pad6)") (class "Default")
      (node (ref "SV73") (pin "6") (pinfunction "6_6") (pintype "passive"))
    )
    (net (code "2283") (name "unconnected-(SV73-Pad7)") (class "Default")
      (node (ref "SV73") (pin "7") (pinfunction "7_7") (pintype "passive"))
    )
    (net (code "2284") (name "unconnected-(SV73-Pad8)") (class "Default")
      (node (ref "SV73") (pin "8") (pinfunction "8_8") (pintype "passive"))
    )
    (net (code "2285") (name "unconnected-(SV73-Pad9)") (class "Default")
      (node (ref "SV73") (pin "9") (pinfunction "9_9") (pintype "passive"))
    )
    (net (code "2286") (name "unconnected-(SV73-Pad10)") (class "Default")
      (node (ref "SV73") (pin "10") (pinfunction "10_10") (pintype "passive"))
    )
    (net (code "2287") (name "unconnected-(SV73-Pad11)") (class "Default")
      (node (ref "SV73") (pin "11") (pinfunction "11_11") (pintype "passive"))
    )
    (net (code "2288") (name "unconnected-(SV73-Pad12)") (class "Default")
      (node (ref "SV73") (pin "12") (pinfunction "12_12") (pintype "passive"))
    )
    (net (code "2289") (name "unconnected-(SV73-Pad13)") (class "Default")
      (node (ref "SV73") (pin "13") (pinfunction "13_13") (pintype "passive"))
    )
    (net (code "2290") (name "unconnected-(SV73-Pad14)") (class "Default")
      (node (ref "SV73") (pin "14") (pinfunction "14_14") (pintype "passive"))
    )
    (net (code "2291") (name "unconnected-(SV73-Pad15)") (class "Default")
      (node (ref "SV73") (pin "15") (pinfunction "15_15") (pintype "passive"))
    )
    (net (code "2292") (name "unconnected-(SV73-Pad16)") (class "Default")
      (node (ref "SV73") (pin "16") (pinfunction "16_16") (pintype "passive"))
    )
    (net (code "2293") (name "unconnected-(SV73-Pad17)") (class "Default")
      (node (ref "SV73") (pin "17") (pinfunction "17_17") (pintype "passive"))
    )
    (net (code "2294") (name "unconnected-(SV73-Pad18)") (class "Default")
      (node (ref "SV73") (pin "18") (pinfunction "18_18") (pintype "passive"))
    )
    (net (code "2295") (name "unconnected-(SV73-Pad19)") (class "Default")
      (node (ref "SV73") (pin "19") (pinfunction "19_19") (pintype "passive"))
    )
    (net (code "2296") (name "unconnected-(SV73-Pad20)") (class "Default")
      (node (ref "SV73") (pin "20") (pinfunction "20_20") (pintype "passive"))
    )
    (net (code "2297") (name "unconnected-(SV73-Pad21)") (class "Default")
      (node (ref "SV73") (pin "21") (pinfunction "21_21") (pintype "passive"))
    )
    (net (code "2298") (name "unconnected-(SV73-Pad22)") (class "Default")
      (node (ref "SV73") (pin "22") (pinfunction "22_22") (pintype "passive"))
    )
    (net (code "2299") (name "unconnected-(SV73-Pad23)") (class "Default")
      (node (ref "SV73") (pin "23") (pinfunction "23_23") (pintype "passive"))
    )
    (net (code "2300") (name "unconnected-(SV73-Pad24)") (class "Default")
      (node (ref "SV73") (pin "24") (pinfunction "24_24") (pintype "passive"))
    )
    (net (code "2301") (name "unconnected-(SV73-Pad25)") (class "Default")
      (node (ref "SV73") (pin "25") (pinfunction "25_25") (pintype "passive"))
    )
    (net (code "2302") (name "unconnected-(SV73-Pad26)") (class "Default")
      (node (ref "SV73") (pin "26") (pinfunction "26_26") (pintype "passive"))
    )
    (net (code "2303") (name "unconnected-(SV73-Pad27)") (class "Default")
      (node (ref "SV73") (pin "27") (pinfunction "27_27") (pintype "passive"))
    )
    (net (code "2304") (name "unconnected-(SV73-Pad28)") (class "Default")
      (node (ref "SV73") (pin "28") (pinfunction "28_28") (pintype "passive"))
    )
    (net (code "2305") (name "unconnected-(SV73-Pad29)") (class "Default")
      (node (ref "SV73") (pin "29") (pinfunction "29_29") (pintype "passive"))
    )
    (net (code "2306") (name "unconnected-(SV73-Pad30)") (class "Default")
      (node (ref "SV73") (pin "30") (pinfunction "30_30") (pintype "passive"))
    )
    (net (code "2307") (name "unconnected-(SV73-Pad31)") (class "Default")
      (node (ref "SV73") (pin "31") (pinfunction "31_31") (pintype "passive"))
    )
    (net (code "2308") (name "unconnected-(SV73-Pad32)") (class "Default")
      (node (ref "SV73") (pin "32") (pinfunction "32_32") (pintype "passive"))
    )
    (net (code "2309") (name "unconnected-(SV73-Pad33)") (class "Default")
      (node (ref "SV73") (pin "33") (pinfunction "33_33") (pintype "passive"))
    )
    (net (code "2310") (name "unconnected-(SV73-Pad34)") (class "Default")
      (node (ref "SV73") (pin "34") (pinfunction "34_34") (pintype "passive"))
    )
    (net (code "2311") (name "unconnected-(SV73-Pad35)") (class "Default")
      (node (ref "SV73") (pin "35") (pinfunction "35_35") (pintype "passive"))
    )
    (net (code "2312") (name "unconnected-(SV73-Pad36)") (class "Default")
      (node (ref "SV73") (pin "36") (pinfunction "36_36") (pintype "passive"))
    )
    (net (code "2313") (name "unconnected-(SV73-Pad37)") (class "Default")
      (node (ref "SV73") (pin "37") (pinfunction "37_37") (pintype "passive"))
    )
    (net (code "2314") (name "unconnected-(SV73-Pad38)") (class "Default")
      (node (ref "SV73") (pin "38") (pinfunction "38_38") (pintype "passive"))
    )
    (net (code "2315") (name "unconnected-(SV73-Pad39)") (class "Default")
      (node (ref "SV73") (pin "39") (pinfunction "39_39") (pintype "passive"))
    )
    (net (code "2316") (name "unconnected-(SV73-Pad40)") (class "Default")
      (node (ref "SV73") (pin "40") (pinfunction "40_40") (pintype "passive"))
    )
    (net (code "2317") (name "unconnected-(SV74-Pad1)") (class "Default")
      (node (ref "SV74") (pin "1") (pinfunction "1_1") (pintype "passive"))
    )
    (net (code "2318") (name "unconnected-(SV74-Pad2)") (class "Default")
      (node (ref "SV74") (pin "2") (pinfunction "2_2") (pintype "passive"))
    )
    (net (code "2319") (name "unconnected-(SV74-Pad3)") (class "Default")
      (node (ref "SV74") (pin "3") (pinfunction "3_3") (pintype "passive"))
    )
    (net (code "2320") (name "unconnected-(SV74-Pad4)") (class "Default")
      (node (ref "SV74") (pin "4") (pinfunction "4_4") (pintype "passive"))
    )
    (net (code "2321") (name "unconnected-(SV74-Pad5)") (class "Default")
      (node (ref "SV74") (pin "5") (pinfunction "5_5") (pintype "passive"))
    )
    (net (code "2322") (name "unconnected-(SV74-Pad6)") (class "Default")
      (node (ref "SV74") (pin "6") (pinfunction "6_6") (pintype "passive"))
    )
    (net (code "2323") (name "unconnected-(SV74-Pad7)") (class "Default")
      (node (ref "SV74") (pin "7") (pinfunction "7_7") (pintype "passive"))
    )
    (net (code "2324") (name "unconnected-(SV74-Pad8)") (class "Default")
      (node (ref "SV74") (pin "8") (pinfunction "8_8") (pintype "passive"))
    )
    (net (code "2325") (name "unconnected-(SV74-Pad9)") (class "Default")
      (node (ref "SV74") (pin "9") (pinfunction "9_9") (pintype "passive"))
    )
    (net (code "2326") (name "unconnected-(SV74-Pad10)") (class "Default")
      (node (ref "SV74") (pin "10") (pinfunction "10_10") (pintype "passive"))
    )
    (net (code "2327") (name "unconnected-(SV74-Pad11)") (class "Default")
      (node (ref "SV74") (pin "11") (pinfunction "11_11") (pintype "passive"))
    )
    (net (code "2328") (name "unconnected-(SV74-Pad12)") (class "Default")
      (node (ref "SV74") (pin "12") (pinfunction "12_12") (pintype "passive"))
    )
    (net (code "2329") (name "unconnected-(SV74-Pad13)") (class "Default")
      (node (ref "SV74") (pin "13") (pinfunction "13_13") (pintype "passive"))
    )
    (net (code "2330") (name "unconnected-(SV74-Pad14)") (class "Default")
      (node (ref "SV74") (pin "14") (pinfunction "14_14") (pintype "passive"))
    )
    (net (code "2331") (name "unconnected-(SV74-Pad15)") (class "Default")
      (node (ref "SV74") (pin "15") (pinfunction "15_15") (pintype "passive"))
    )
    (net (code "2332") (name "unconnected-(SV74-Pad16)") (class "Default")
      (node (ref "SV74") (pin "16") (pinfunction "16_16") (pintype "passive"))
    )
    (net (code "2333") (name "unconnected-(SV74-Pad17)") (class "Default")
      (node (ref "SV74") (pin "17") (pinfunction "17_17") (pintype "passive"))
    )
    (net (code "2334") (name "unconnected-(SV74-Pad18)") (class "Default")
      (node (ref "SV74") (pin "18") (pinfunction "18_18") (pintype "passive"))
    )
    (net (code "2335") (name "unconnected-(SV74-Pad19)") (class "Default")
      (node (ref "SV74") (pin "19") (pinfunction "19_19") (pintype "passive"))
    )
    (net (code "2336") (name "unconnected-(SV74-Pad20)") (class "Default")
      (node (ref "SV74") (pin "20") (pinfunction "20_20") (pintype "passive"))
    )
    (net (code "2337") (name "unconnected-(SV74-Pad21)") (class "Default")
      (node (ref "SV74") (pin "21") (pinfunction "21_21") (pintype "passive"))
    )
    (net (code "2338") (name "unconnected-(SV74-Pad22)") (class "Default")
      (node (ref "SV74") (pin "22") (pinfunction "22_22") (pintype "passive"))
    )
    (net (code "2339") (name "unconnected-(SV74-Pad23)") (class "Default")
      (node (ref "SV74") (pin "23") (pinfunction "23_23") (pintype "passive"))
    )
    (net (code "2340") (name "unconnected-(SV74-Pad24)") (class "Default")
      (node (ref "SV74") (pin "24") (pinfunction "24_24") (pintype "passive"))
    )
    (net (code "2341") (name "unconnected-(SV74-Pad25)") (class "Default")
      (node (ref "SV74") (pin "25") (pinfunction "25_25") (pintype "passive"))
    )
    (net (code "2342") (name "unconnected-(SV74-Pad26)") (class "Default")
      (node (ref "SV74") (pin "26") (pinfunction "26_26") (pintype "passive"))
    )
    (net (code "2343") (name "unconnected-(SV74-Pad27)") (class "Default")
      (node (ref "SV74") (pin "27") (pinfunction "27_27") (pintype "passive"))
    )
    (net (code "2344") (name "unconnected-(SV74-Pad28)") (class "Default")
      (node (ref "SV74") (pin "28") (pinfunction "28_28") (pintype "passive"))
    )
    (net (code "2345") (name "unconnected-(SV74-Pad29)") (class "Default")
      (node (ref "SV74") (pin "29") (pinfunction "29_29") (pintype "passive"))
    )
    (net (code "2346") (name "unconnected-(SV74-Pad30)") (class "Default")
      (node (ref "SV74") (pin "30") (pinfunction "30_30") (pintype "passive"))
    )
    (net (code "2347") (name "unconnected-(SV74-Pad31)") (class "Default")
      (node (ref "SV74") (pin "31") (pinfunction "31_31") (pintype "passive"))
    )
    (net (code "2348") (name "unconnected-(SV74-Pad32)") (class "Default")
      (node (ref "SV74") (pin "32") (pinfunction "32_32") (pintype "passive"))
    )
    (net (code "2349") (name "unconnected-(SV74-Pad33)") (class "Default")
      (node (ref "SV74") (pin "33") (pinfunction "33_33") (pintype "passive"))
    )
    (net (code "2350") (name "unconnected-(SV74-Pad34)") (class "Default")
      (node (ref "SV74") (pin "34") (pinfunction "34_34") (pintype "passive"))
    )
    (net (code "2351") (name "unconnected-(SV74-Pad35)") (class "Default")
      (node (ref "SV74") (pin "35") (pinfunction "35_35") (pintype "passive"))
    )
    (net (code "2352") (name "unconnected-(SV74-Pad36)") (class "Default")
      (node (ref "SV74") (pin "36") (pinfunction "36_36") (pintype "passive"))
    )
    (net (code "2353") (name "unconnected-(SV75-Pad1)") (class "Default")
      (node (ref "SV75") (pin "1") (pinfunction "1_1") (pintype "passive"))
    )
    (net (code "2354") (name "unconnected-(SV75-Pad2)") (class "Default")
      (node (ref "SV75") (pin "2") (pinfunction "2_2") (pintype "passive"))
    )
    (net (code "2355") (name "unconnected-(SV75-Pad3)") (class "Default")
      (node (ref "SV75") (pin "3") (pinfunction "3_3") (pintype "passive"))
    )
    (net (code "2356") (name "unconnected-(SV75-Pad4)") (class "Default")
      (node (ref "SV75") (pin "4") (pinfunction "4_4") (pintype "passive"))
    )
    (net (code "2357") (name "unconnected-(SV75-Pad5)") (class "Default")
      (node (ref "SV75") (pin "5") (pinfunction "5_5") (pintype "passive"))
    )
    (net (code "2358") (name "unconnected-(SV75-Pad6)") (class "Default")
      (node (ref "SV75") (pin "6") (pinfunction "6_6") (pintype "passive"))
    )
    (net (code "2359") (name "unconnected-(SV75-Pad7)") (class "Default")
      (node (ref "SV75") (pin "7") (pinfunction "7_7") (pintype "passive"))
    )
    (net (code "2360") (name "unconnected-(SV75-Pad8)") (class "Default")
      (node (ref "SV75") (pin "8") (pinfunction "8_8") (pintype "passive"))
    )
    (net (code "2361") (name "unconnected-(SV75-Pad9)") (class "Default")
      (node (ref "SV75") (pin "9") (pinfunction "9_9") (pintype "passive"))
    )
    (net (code "2362") (name "unconnected-(SV75-Pad10)") (class "Default")
      (node (ref "SV75") (pin "10") (pinfunction "10_10") (pintype "passive"))
    )
    (net (code "2363") (name "unconnected-(SV75-Pad11)") (class "Default")
      (node (ref "SV75") (pin "11") (pinfunction "11_11") (pintype "passive"))
    )
    (net (code "2364") (name "unconnected-(SV75-Pad12)") (class "Default")
      (node (ref "SV75") (pin "12") (pinfunction "12_12") (pintype "passive"))
    )
    (net (code "2365") (name "unconnected-(SV75-Pad13)") (class "Default")
      (node (ref "SV75") (pin "13") (pinfunction "13_13") (pintype "passive"))
    )
    (net (code "2366") (name "unconnected-(SV75-Pad14)") (class "Default")
      (node (ref "SV75") (pin "14") (pinfunction "14_14") (pintype "passive"))
    )
    (net (code "2367") (name "unconnected-(SV75-Pad15)") (class "Default")
      (node (ref "SV75") (pin "15") (pinfunction "15_15") (pintype "passive"))
    )
    (net (code "2368") (name "unconnected-(SV75-Pad16)") (class "Default")
      (node (ref "SV75") (pin "16") (pinfunction "16_16") (pintype "passive"))
    )
    (net (code "2369") (name "unconnected-(SV75-Pad17)") (class "Default")
      (node (ref "SV75") (pin "17") (pinfunction "17_17") (pintype "passive"))
    )
    (net (code "2370") (name "unconnected-(SV75-Pad18)") (class "Default")
      (node (ref "SV75") (pin "18") (pinfunction "18_18") (pintype "passive"))
    )
    (net (code "2371") (name "unconnected-(SV75-Pad19)") (class "Default")
      (node (ref "SV75") (pin "19") (pinfunction "19_19") (pintype "passive"))
    )
    (net (code "2372") (name "unconnected-(SV75-Pad20)") (class "Default")
      (node (ref "SV75") (pin "20") (pinfunction "20_20") (pintype "passive"))
    )
    (net (code "2373") (name "unconnected-(SV75-Pad21)") (class "Default")
      (node (ref "SV75") (pin "21") (pinfunction "21_21") (pintype "passive"))
    )
    (net (code "2374") (name "unconnected-(SV75-Pad22)") (class "Default")
      (node (ref "SV75") (pin "22") (pinfunction "22_22") (pintype "passive"))
    )
    (net (code "2375") (name "unconnected-(SV75-Pad23)") (class "Default")
      (node (ref "SV75") (pin "23") (pinfunction "23_23") (pintype "passive"))
    )
    (net (code "2376") (name "unconnected-(SV75-Pad24)") (class "Default")
      (node (ref "SV75") (pin "24") (pinfunction "24_24") (pintype "passive"))
    )
    (net (code "2377") (name "unconnected-(SV75-Pad25)") (class "Default")
      (node (ref "SV75") (pin "25") (pinfunction "25_25") (pintype "passive"))
    )
    (net (code "2378") (name "unconnected-(SV75-Pad26)") (class "Default")
      (node (ref "SV75") (pin "26") (pinfunction "26_26") (pintype "passive"))
    )
    (net (code "2379") (name "unconnected-(SV75-Pad27)") (class "Default")
      (node (ref "SV75") (pin "27") (pinfunction "27_27") (pintype "passive"))
    )
    (net (code "2380") (name "unconnected-(SV75-Pad28)") (class "Default")
      (node (ref "SV75") (pin "28") (pinfunction "28_28") (pintype "passive"))
    )
    (net (code "2381") (name "unconnected-(SV75-Pad29)") (class "Default")
      (node (ref "SV75") (pin "29") (pinfunction "29_29") (pintype "passive"))
    )
    (net (code "2382") (name "unconnected-(SV75-Pad30)") (class "Default")
      (node (ref "SV75") (pin "30") (pinfunction "30_30") (pintype "passive"))
    )
    (net (code "2383") (name "unconnected-(SV75-Pad31)") (class "Default")
      (node (ref "SV75") (pin "31") (pinfunction "31_31") (pintype "passive"))
    )
    (net (code "2384") (name "unconnected-(SV75-Pad32)") (class "Default")
      (node (ref "SV75") (pin "32") (pinfunction "32_32") (pintype "passive"))
    )
    (net (code "2385") (name "unconnected-(SV75-Pad33)") (class "Default")
      (node (ref "SV75") (pin "33") (pinfunction "33_33") (pintype "passive"))
    )
    (net (code "2386") (name "unconnected-(SV75-Pad34)") (class "Default")
      (node (ref "SV75") (pin "34") (pinfunction "34_34") (pintype "passive"))
    )
    (net (code "2387") (name "unconnected-(SV75-Pad35)") (class "Default")
      (node (ref "SV75") (pin "35") (pinfunction "35_35") (pintype "passive"))
    )
    (net (code "2388") (name "unconnected-(SV75-Pad36)") (class "Default")
      (node (ref "SV75") (pin "36") (pinfunction "36_36") (pintype "passive"))
    )
    (net (code "2389") (name "unconnected-(SV76-Pad1)") (class "Default")
      (node (ref "SV76") (pin "1") (pinfunction "1_1") (pintype "passive"))
    )
    (net (code "2390") (name "unconnected-(SV76-Pad2)") (class "Default")
      (node (ref "SV76") (pin "2") (pinfunction "2_2") (pintype "passive"))
    )
    (net (code "2391") (name "unconnected-(SV76-Pad3)") (class "Default")
      (node (ref "SV76") (pin "3") (pinfunction "3_3") (pintype "passive"))
    )
    (net (code "2392") (name "unconnected-(SV76-Pad4)") (class "Default")
      (node (ref "SV76") (pin "4") (pinfunction "4_4") (pintype "passive"))
    )
    (net (code "2393") (name "unconnected-(SV76-Pad5)") (class "Default")
      (node (ref "SV76") (pin "5") (pinfunction "5_5") (pintype "passive"))
    )
    (net (code "2394") (name "unconnected-(SV76-Pad6)") (class "Default")
      (node (ref "SV76") (pin "6") (pinfunction "6_6") (pintype "passive"))
    )
    (net (code "2395") (name "unconnected-(SV76-Pad7)") (class "Default")
      (node (ref "SV76") (pin "7") (pinfunction "7_7") (pintype "passive"))
    )
    (net (code "2396") (name "unconnected-(SV76-Pad8)") (class "Default")
      (node (ref "SV76") (pin "8") (pinfunction "8_8") (pintype "passive"))
    )
    (net (code "2397") (name "unconnected-(SV76-Pad9)") (class "Default")
      (node (ref "SV76") (pin "9") (pinfunction "9_9") (pintype "passive"))
    )
    (net (code "2398") (name "unconnected-(SV76-Pad10)") (class "Default")
      (node (ref "SV76") (pin "10") (pinfunction "10_10") (pintype "passive"))
    )
    (net (code "2399") (name "unconnected-(SV76-Pad11)") (class "Default")
      (node (ref "SV76") (pin "11") (pinfunction "11_11") (pintype "passive"))
    )
    (net (code "2400") (name "unconnected-(SV76-Pad12)") (class "Default")
      (node (ref "SV76") (pin "12") (pinfunction "12_12") (pintype "passive"))
    )
    (net (code "2401") (name "unconnected-(SV76-Pad13)") (class "Default")
      (node (ref "SV76") (pin "13") (pinfunction "13_13") (pintype "passive"))
    )
    (net (code "2402") (name "unconnected-(SV76-Pad14)") (class "Default")
      (node (ref "SV76") (pin "14") (pinfunction "14_14") (pintype "passive"))
    )
    (net (code "2403") (name "unconnected-(SV76-Pad15)") (class "Default")
      (node (ref "SV76") (pin "15") (pinfunction "15_15") (pintype "passive"))
    )
    (net (code "2404") (name "unconnected-(SV76-Pad16)") (class "Default")
      (node (ref "SV76") (pin "16") (pinfunction "16_16") (pintype "passive"))
    )
    (net (code "2405") (name "unconnected-(SV76-Pad17)") (class "Default")
      (node (ref "SV76") (pin "17") (pinfunction "17_17") (pintype "passive"))
    )
    (net (code "2406") (name "unconnected-(SV76-Pad18)") (class "Default")
      (node (ref "SV76") (pin "18") (pinfunction "18_18") (pintype "passive"))
    )
    (net (code "2407") (name "unconnected-(SV76-Pad19)") (class "Default")
      (node (ref "SV76") (pin "19") (pinfunction "19_19") (pintype "passive"))
    )
    (net (code "2408") (name "unconnected-(SV76-Pad20)") (class "Default")
      (node (ref "SV76") (pin "20") (pinfunction "20_20") (pintype "passive"))
    )
    (net (code "2409") (name "unconnected-(SV76-Pad21)") (class "Default")
      (node (ref "SV76") (pin "21") (pinfunction "21_21") (pintype "passive"))
    )
    (net (code "2410") (name "unconnected-(SV76-Pad22)") (class "Default")
      (node (ref "SV76") (pin "22") (pinfunction "22_22") (pintype "passive"))
    )
    (net (code "2411") (name "unconnected-(SV76-Pad23)") (class "Default")
      (node (ref "SV76") (pin "23") (pinfunction "23_23") (pintype "passive"))
    )
    (net (code "2412") (name "unconnected-(SV76-Pad24)") (class "Default")
      (node (ref "SV76") (pin "24") (pinfunction "24_24") (pintype "passive"))
    )
    (net (code "2413") (name "unconnected-(SV76-Pad25)") (class "Default")
      (node (ref "SV76") (pin "25") (pinfunction "25_25") (pintype "passive"))
    )
    (net (code "2414") (name "unconnected-(SV76-Pad26)") (class "Default")
      (node (ref "SV76") (pin "26") (pinfunction "26_26") (pintype "passive"))
    )
    (net (code "2415") (name "unconnected-(SV76-Pad27)") (class "Default")
      (node (ref "SV76") (pin "27") (pinfunction "27_27") (pintype "passive"))
    )
    (net (code "2416") (name "unconnected-(SV76-Pad28)") (class "Default")
      (node (ref "SV76") (pin "28") (pinfunction "28_28") (pintype "passive"))
    )
    (net (code "2417") (name "unconnected-(SV76-Pad29)") (class "Default")
      (node (ref "SV76") (pin "29") (pinfunction "29_29") (pintype "passive"))
    )
    (net (code "2418") (name "unconnected-(SV76-Pad30)") (class "Default")
      (node (ref "SV76") (pin "30") (pinfunction "30_30") (pintype "passive"))
    )
    (net (code "2419") (name "unconnected-(SV76-Pad31)") (class "Default")
      (node (ref "SV76") (pin "31") (pinfunction "31_31") (pintype "passive"))
    )
    (net (code "2420") (name "unconnected-(SV76-Pad32)") (class "Default")
      (node (ref "SV76") (pin "32") (pinfunction "32_32") (pintype "passive"))
    )
    (net (code "2421") (name "unconnected-(SV76-Pad33)") (class "Default")
      (node (ref "SV76") (pin "33") (pinfunction "33_33") (pintype "passive"))
    )
    (net (code "2422") (name "unconnected-(SV76-Pad34)") (class "Default")
      (node (ref "SV76") (pin "34") (pinfunction "34_34") (pintype "passive"))
    )
    (net (code "2423") (name "unconnected-(SV76-Pad35)") (class "Default")
      (node (ref "SV76") (pin "35") (pinfunction "35_35") (pintype "passive"))
    )
    (net (code "2424") (name "unconnected-(SV76-Pad36)") (class "Default")
      (node (ref "SV76") (pin "36") (pinfunction "36_36") (pintype "passive"))
    )
    (net (code "2425") (name "unconnected-(SV77-Pad1)") (class "Default")
      (node (ref "SV77") (pin "1") (pinfunction "1_1") (pintype "passive"))
    )
    (net (code "2426") (name "unconnected-(SV77-Pad2)") (class "Default")
      (node (ref "SV77") (pin "2") (pinfunction "2_2") (pintype "passive"))
    )
    (net (code "2427") (name "unconnected-(SV77-Pad3)") (class "Default")
      (node (ref "SV77") (pin "3") (pinfunction "3_3") (pintype "passive"))
    )
    (net (code "2428") (name "unconnected-(SV77-Pad4)") (class "Default")
      (node (ref "SV77") (pin "4") (pinfunction "4_4") (pintype "passive"))
    )
    (net (code "2429") (name "unconnected-(SV77-Pad5)") (class "Default")
      (node (ref "SV77") (pin "5") (pinfunction "5_5") (pintype "passive"))
    )
    (net (code "2430") (name "unconnected-(SV77-Pad6)") (class "Default")
      (node (ref "SV77") (pin "6") (pinfunction "6_6") (pintype "passive"))
    )
    (net (code "2431") (name "unconnected-(SV77-Pad7)") (class "Default")
      (node (ref "SV77") (pin "7") (pinfunction "7_7") (pintype "passive"))
    )
    (net (code "2432") (name "unconnected-(SV77-Pad8)") (class "Default")
      (node (ref "SV77") (pin "8") (pinfunction "8_8") (pintype "passive"))
    )
    (net (code "2433") (name "unconnected-(SV77-Pad9)") (class "Default")
      (node (ref "SV77") (pin "9") (pinfunction "9_9") (pintype "passive"))
    )
    (net (code "2434") (name "unconnected-(SV77-Pad10)") (class "Default")
      (node (ref "SV77") (pin "10") (pinfunction "10_10") (pintype "passive"))
    )
    (net (code "2435") (name "unconnected-(SV77-Pad11)") (class "Default")
      (node (ref "SV77") (pin "11") (pinfunction "11_11") (pintype "passive"))
    )
    (net (code "2436") (name "unconnected-(SV77-Pad12)") (class "Default")
      (node (ref "SV77") (pin "12") (pinfunction "12_12") (pintype "passive"))
    )
    (net (code "2437") (name "unconnected-(SV77-Pad13)") (class "Default")
      (node (ref "SV77") (pin "13") (pinfunction "13_13") (pintype "passive"))
    )
    (net (code "2438") (name "unconnected-(SV77-Pad14)") (class "Default")
      (node (ref "SV77") (pin "14") (pinfunction "14_14") (pintype "passive"))
    )
    (net (code "2439") (name "unconnected-(SV77-Pad15)") (class "Default")
      (node (ref "SV77") (pin "15") (pinfunction "15_15") (pintype "passive"))
    )
    (net (code "2440") (name "unconnected-(SV77-Pad16)") (class "Default")
      (node (ref "SV77") (pin "16") (pinfunction "16_16") (pintype "passive"))
    )
    (net (code "2441") (name "unconnected-(SV77-Pad17)") (class "Default")
      (node (ref "SV77") (pin "17") (pinfunction "17_17") (pintype "passive"))
    )
    (net (code "2442") (name "unconnected-(SV77-Pad18)") (class "Default")
      (node (ref "SV77") (pin "18") (pinfunction "18_18") (pintype "passive"))
    )
    (net (code "2443") (name "unconnected-(SV77-Pad19)") (class "Default")
      (node (ref "SV77") (pin "19") (pinfunction "19_19") (pintype "passive"))
    )
    (net (code "2444") (name "unconnected-(SV77-Pad20)") (class "Default")
      (node (ref "SV77") (pin "20") (pinfunction "20_20") (pintype "passive"))
    )
    (net (code "2445") (name "unconnected-(SV77-Pad21)") (class "Default")
      (node (ref "SV77") (pin "21") (pinfunction "21_21") (pintype "passive"))
    )
    (net (code "2446") (name "unconnected-(SV77-Pad22)") (class "Default")
      (node (ref "SV77") (pin "22") (pinfunction "22_22") (pintype "passive"))
    )
    (net (code "2447") (name "unconnected-(SV77-Pad23)") (class "Default")
      (node (ref "SV77") (pin "23") (pinfunction "23_23") (pintype "passive"))
    )
    (net (code "2448") (name "unconnected-(SV77-Pad24)") (class "Default")
      (node (ref "SV77") (pin "24") (pinfunction "24_24") (pintype "passive"))
    )
    (net (code "2449") (name "unconnected-(SV77-Pad25)") (class "Default")
      (node (ref "SV77") (pin "25") (pinfunction "25_25") (pintype "passive"))
    )
    (net (code "2450") (name "unconnected-(SV77-Pad26)") (class "Default")
      (node (ref "SV77") (pin "26") (pinfunction "26_26") (pintype "passive"))
    )
    (net (code "2451") (name "unconnected-(SV77-Pad27)") (class "Default")
      (node (ref "SV77") (pin "27") (pinfunction "27_27") (pintype "passive"))
    )
    (net (code "2452") (name "unconnected-(SV77-Pad28)") (class "Default")
      (node (ref "SV77") (pin "28") (pinfunction "28_28") (pintype "passive"))
    )
    (net (code "2453") (name "unconnected-(SV77-Pad29)") (class "Default")
      (node (ref "SV77") (pin "29") (pinfunction "29_29") (pintype "passive"))
    )
    (net (code "2454") (name "unconnected-(SV77-Pad30)") (class "Default")
      (node (ref "SV77") (pin "30") (pinfunction "30_30") (pintype "passive"))
    )
    (net (code "2455") (name "unconnected-(SV77-Pad31)") (class "Default")
      (node (ref "SV77") (pin "31") (pinfunction "31_31") (pintype "passive"))
    )
    (net (code "2456") (name "unconnected-(SV77-Pad32)") (class "Default")
      (node (ref "SV77") (pin "32") (pinfunction "32_32") (pintype "passive"))
    )
    (net (code "2457") (name "unconnected-(SV77-Pad33)") (class "Default")
      (node (ref "SV77") (pin "33") (pinfunction "33_33") (pintype "passive"))
    )
    (net (code "2458") (name "unconnected-(SV77-Pad34)") (class "Default")
      (node (ref "SV77") (pin "34") (pinfunction "34_34") (pintype "passive"))
    )
    (net (code "2459") (name "unconnected-(SV77-Pad35)") (class "Default")
      (node (ref "SV77") (pin "35") (pinfunction "35_35") (pintype "passive"))
    )
    (net (code "2460") (name "unconnected-(SV77-Pad36)") (class "Default")
      (node (ref "SV77") (pin "36") (pinfunction "36_36") (pintype "passive"))
    )
    (net (code "2461") (name "unconnected-(SV78-Pad1)") (class "Default")
      (node (ref "SV78") (pin "1") (pinfunction "1_1") (pintype "passive"))
    )
    (net (code "2462") (name "unconnected-(SV78-Pad2)") (class "Default")
      (node (ref "SV78") (pin "2") (pinfunction "2_2") (pintype "passive"))
    )
    (net (code "2463") (name "unconnected-(SV78-Pad3)") (class "Default")
      (node (ref "SV78") (pin "3") (pinfunction "3_3") (pintype "passive"))
    )
    (net (code "2464") (name "unconnected-(SV78-Pad4)") (class "Default")
      (node (ref "SV78") (pin "4") (pinfunction "4_4") (pintype "passive"))
    )
    (net (code "2465") (name "unconnected-(SV78-Pad5)") (class "Default")
      (node (ref "SV78") (pin "5") (pinfunction "5_5") (pintype "passive"))
    )
    (net (code "2466") (name "unconnected-(SV78-Pad6)") (class "Default")
      (node (ref "SV78") (pin "6") (pinfunction "6_6") (pintype "passive"))
    )
    (net (code "2467") (name "unconnected-(SV78-Pad7)") (class "Default")
      (node (ref "SV78") (pin "7") (pinfunction "7_7") (pintype "passive"))
    )
    (net (code "2468") (name "unconnected-(SV78-Pad8)") (class "Default")
      (node (ref "SV78") (pin "8") (pinfunction "8_8") (pintype "passive"))
    )
    (net (code "2469") (name "unconnected-(SV78-Pad9)") (class "Default")
      (node (ref "SV78") (pin "9") (pinfunction "9_9") (pintype "passive"))
    )
    (net (code "2470") (name "unconnected-(SV78-Pad10)") (class "Default")
      (node (ref "SV78") (pin "10") (pinfunction "10_10") (pintype "passive"))
    )
    (net (code "2471") (name "unconnected-(SV78-Pad11)") (class "Default")
      (node (ref "SV78") (pin "11") (pinfunction "11_11") (pintype "passive"))
    )
    (net (code "2472") (name "unconnected-(SV78-Pad12)") (class "Default")
      (node (ref "SV78") (pin "12") (pinfunction "12_12") (pintype "passive"))
    )
    (net (code "2473") (name "unconnected-(SV78-Pad13)") (class "Default")
      (node (ref "SV78") (pin "13") (pinfunction "13_13") (pintype "passive"))
    )
    (net (code "2474") (name "unconnected-(SV78-Pad14)") (class "Default")
      (node (ref "SV78") (pin "14") (pinfunction "14_14") (pintype "passive"))
    )
    (net (code "2475") (name "unconnected-(SV78-Pad15)") (class "Default")
      (node (ref "SV78") (pin "15") (pinfunction "15_15") (pintype "passive"))
    )
    (net (code "2476") (name "unconnected-(SV78-Pad16)") (class "Default")
      (node (ref "SV78") (pin "16") (pinfunction "16_16") (pintype "passive"))
    )
    (net (code "2477") (name "unconnected-(SV78-Pad17)") (class "Default")
      (node (ref "SV78") (pin "17") (pinfunction "17_17") (pintype "passive"))
    )
    (net (code "2478") (name "unconnected-(SV78-Pad18)") (class "Default")
      (node (ref "SV78") (pin "18") (pinfunction "18_18") (pintype "passive"))
    )
    (net (code "2479") (name "unconnected-(SV78-Pad19)") (class "Default")
      (node (ref "SV78") (pin "19") (pinfunction "19_19") (pintype "passive"))
    )
    (net (code "2480") (name "unconnected-(SV78-Pad20)") (class "Default")
      (node (ref "SV78") (pin "20") (pinfunction "20_20") (pintype "passive"))
    )
    (net (code "2481") (name "unconnected-(SV78-Pad21)") (class "Default")
      (node (ref "SV78") (pin "21") (pinfunction "21_21") (pintype "passive"))
    )
    (net (code "2482") (name "unconnected-(SV78-Pad22)") (class "Default")
      (node (ref "SV78") (pin "22") (pinfunction "22_22") (pintype "passive"))
    )
    (net (code "2483") (name "unconnected-(SV78-Pad23)") (class "Default")
      (node (ref "SV78") (pin "23") (pinfunction "23_23") (pintype "passive"))
    )
    (net (code "2484") (name "unconnected-(SV78-Pad24)") (class "Default")
      (node (ref "SV78") (pin "24") (pinfunction "24_24") (pintype "passive"))
    )
    (net (code "2485") (name "unconnected-(SV78-Pad25)") (class "Default")
      (node (ref "SV78") (pin "25") (pinfunction "25_25") (pintype "passive"))
    )
    (net (code "2486") (name "unconnected-(SV78-Pad26)") (class "Default")
      (node (ref "SV78") (pin "26") (pinfunction "26_26") (pintype "passive"))
    )
    (net (code "2487") (name "unconnected-(SV78-Pad27)") (class "Default")
      (node (ref "SV78") (pin "27") (pinfunction "27_27") (pintype "passive"))
    )
    (net (code "2488") (name "unconnected-(SV78-Pad28)") (class "Default")
      (node (ref "SV78") (pin "28") (pinfunction "28_28") (pintype "passive"))
    )
    (net (code "2489") (name "unconnected-(SV78-Pad29)") (class "Default")
      (node (ref "SV78") (pin "29") (pinfunction "29_29") (pintype "passive"))
    )
    (net (code "2490") (name "unconnected-(SV78-Pad30)") (class "Default")
      (node (ref "SV78") (pin "30") (pinfunction "30_30") (pintype "passive"))
    )
    (net (code "2491") (name "unconnected-(SV78-Pad31)") (class "Default")
      (node (ref "SV78") (pin "31") (pinfunction "31_31") (pintype "passive"))
    )
    (net (code "2492") (name "unconnected-(SV78-Pad32)") (class "Default")
      (node (ref "SV78") (pin "32") (pinfunction "32_32") (pintype "passive"))
    )
    (net (code "2493") (name "unconnected-(SV78-Pad33)") (class "Default")
      (node (ref "SV78") (pin "33") (pinfunction "33_33") (pintype "passive"))
    )
    (net (code "2494") (name "unconnected-(SV78-Pad34)") (class "Default")
      (node (ref "SV78") (pin "34") (pinfunction "34_34") (pintype "passive"))
    )
    (net (code "2495") (name "unconnected-(SV78-Pad35)") (class "Default")
      (node (ref "SV78") (pin "35") (pinfunction "35_35") (pintype "passive"))
    )
    (net (code "2496") (name "unconnected-(SV78-Pad36)") (class "Default")
      (node (ref "SV78") (pin "36") (pinfunction "36_36") (pintype "passive"))
    )
    (net (code "2497") (name "unconnected-(SV78-Pad37)") (class "Default")
      (node (ref "SV78") (pin "37") (pinfunction "37_37") (pintype "passive"))
    )
    (net (code "2498") (name "unconnected-(SV78-Pad38)") (class "Default")
      (node (ref "SV78") (pin "38") (pinfunction "38_38") (pintype "passive"))
    )
    (net (code "2499") (name "unconnected-(SV78-Pad39)") (class "Default")
      (node (ref "SV78") (pin "39") (pinfunction "39_39") (pintype "passive"))
    )
    (net (code "2500") (name "unconnected-(SV78-Pad40)") (class "Default")
      (node (ref "SV78") (pin "40") (pinfunction "40_40") (pintype "passive"))
    )
    (net (code "2501") (name "unconnected-(SV79-Pad1)") (class "Default")
      (node (ref "SV79") (pin "1") (pinfunction "1_1") (pintype "passive"))
    )
    (net (code "2502") (name "unconnected-(SV79-Pad2)") (class "Default")
      (node (ref "SV79") (pin "2") (pinfunction "2_2") (pintype "passive"))
    )
    (net (code "2503") (name "unconnected-(SV79-Pad3)") (class "Default")
      (node (ref "SV79") (pin "3") (pinfunction "3_3") (pintype "passive"))
    )
    (net (code "2504") (name "unconnected-(SV79-Pad4)") (class "Default")
      (node (ref "SV79") (pin "4") (pinfunction "4_4") (pintype "passive"))
    )
    (net (code "2505") (name "unconnected-(SV79-Pad5)") (class "Default")
      (node (ref "SV79") (pin "5") (pinfunction "5_5") (pintype "passive"))
    )
    (net (code "2506") (name "unconnected-(SV79-Pad6)") (class "Default")
      (node (ref "SV79") (pin "6") (pinfunction "6_6") (pintype "passive"))
    )
    (net (code "2507") (name "unconnected-(SV79-Pad7)") (class "Default")
      (node (ref "SV79") (pin "7") (pinfunction "7_7") (pintype "passive"))
    )
    (net (code "2508") (name "unconnected-(SV79-Pad8)") (class "Default")
      (node (ref "SV79") (pin "8") (pinfunction "8_8") (pintype "passive"))
    )
    (net (code "2509") (name "unconnected-(SV79-Pad9)") (class "Default")
      (node (ref "SV79") (pin "9") (pinfunction "9_9") (pintype "passive"))
    )
    (net (code "2510") (name "unconnected-(SV79-Pad10)") (class "Default")
      (node (ref "SV79") (pin "10") (pinfunction "10_10") (pintype "passive"))
    )
    (net (code "2511") (name "unconnected-(SV79-Pad11)") (class "Default")
      (node (ref "SV79") (pin "11") (pinfunction "11_11") (pintype "passive"))
    )
    (net (code "2512") (name "unconnected-(SV79-Pad12)") (class "Default")
      (node (ref "SV79") (pin "12") (pinfunction "12_12") (pintype "passive"))
    )
    (net (code "2513") (name "unconnected-(SV79-Pad13)") (class "Default")
      (node (ref "SV79") (pin "13") (pinfunction "13_13") (pintype "passive"))
    )
    (net (code "2514") (name "unconnected-(SV79-Pad14)") (class "Default")
      (node (ref "SV79") (pin "14") (pinfunction "14_14") (pintype "passive"))
    )
    (net (code "2515") (name "unconnected-(SV79-Pad15)") (class "Default")
      (node (ref "SV79") (pin "15") (pinfunction "15_15") (pintype "passive"))
    )
    (net (code "2516") (name "unconnected-(SV79-Pad16)") (class "Default")
      (node (ref "SV79") (pin "16") (pinfunction "16_16") (pintype "passive"))
    )
    (net (code "2517") (name "unconnected-(SV79-Pad17)") (class "Default")
      (node (ref "SV79") (pin "17") (pinfunction "17_17") (pintype "passive"))
    )
    (net (code "2518") (name "unconnected-(SV79-Pad18)") (class "Default")
      (node (ref "SV79") (pin "18") (pinfunction "18_18") (pintype "passive"))
    )
    (net (code "2519") (name "unconnected-(SV79-Pad19)") (class "Default")
      (node (ref "SV79") (pin "19") (pinfunction "19_19") (pintype "passive"))
    )
    (net (code "2520") (name "unconnected-(SV79-Pad20)") (class "Default")
      (node (ref "SV79") (pin "20") (pinfunction "20_20") (pintype "passive"))
    )
    (net (code "2521") (name "unconnected-(SV79-Pad21)") (class "Default")
      (node (ref "SV79") (pin "21") (pinfunction "21_21") (pintype "passive"))
    )
    (net (code "2522") (name "unconnected-(SV79-Pad22)") (class "Default")
      (node (ref "SV79") (pin "22") (pinfunction "22_22") (pintype "passive"))
    )
    (net (code "2523") (name "unconnected-(SV79-Pad23)") (class "Default")
      (node (ref "SV79") (pin "23") (pinfunction "23_23") (pintype "passive"))
    )
    (net (code "2524") (name "unconnected-(SV79-Pad24)") (class "Default")
      (node (ref "SV79") (pin "24") (pinfunction "24_24") (pintype "passive"))
    )
    (net (code "2525") (name "unconnected-(SV79-Pad25)") (class "Default")
      (node (ref "SV79") (pin "25") (pinfunction "25_25") (pintype "passive"))
    )
    (net (code "2526") (name "unconnected-(SV79-Pad26)") (class "Default")
      (node (ref "SV79") (pin "26") (pinfunction "26_26") (pintype "passive"))
    )
    (net (code "2527") (name "unconnected-(SV79-Pad27)") (class "Default")
      (node (ref "SV79") (pin "27") (pinfunction "27_27") (pintype "passive"))
    )
    (net (code "2528") (name "unconnected-(SV79-Pad28)") (class "Default")
      (node (ref "SV79") (pin "28") (pinfunction "28_28") (pintype "passive"))
    )
    (net (code "2529") (name "unconnected-(SV79-Pad29)") (class "Default")
      (node (ref "SV79") (pin "29") (pinfunction "29_29") (pintype "passive"))
    )
    (net (code "2530") (name "unconnected-(SV79-Pad30)") (class "Default")
      (node (ref "SV79") (pin "30") (pinfunction "30_30") (pintype "passive"))
    )
    (net (code "2531") (name "unconnected-(SV79-Pad31)") (class "Default")
      (node (ref "SV79") (pin "31") (pinfunction "31_31") (pintype "passive"))
    )
    (net (code "2532") (name "unconnected-(SV79-Pad32)") (class "Default")
      (node (ref "SV79") (pin "32") (pinfunction "32_32") (pintype "passive"))
    )
    (net (code "2533") (name "unconnected-(SV79-Pad33)") (class "Default")
      (node (ref "SV79") (pin "33") (pinfunction "33_33") (pintype "passive"))
    )
    (net (code "2534") (name "unconnected-(SV79-Pad34)") (class "Default")
      (node (ref "SV79") (pin "34") (pinfunction "34_34") (pintype "passive"))
    )
    (net (code "2535") (name "unconnected-(SV79-Pad35)") (class "Default")
      (node (ref "SV79") (pin "35") (pinfunction "35_35") (pintype "passive"))
    )
    (net (code "2536") (name "unconnected-(SV79-Pad36)") (class "Default")
      (node (ref "SV79") (pin "36") (pinfunction "36_36") (pintype "passive"))
    )
    (net (code "2537") (name "unconnected-(SV79-Pad37)") (class "Default")
      (node (ref "SV79") (pin "37") (pinfunction "37_37") (pintype "passive"))
    )
    (net (code "2538") (name "unconnected-(SV79-Pad38)") (class "Default")
      (node (ref "SV79") (pin "38") (pinfunction "38_38") (pintype "passive"))
    )
    (net (code "2539") (name "unconnected-(SV79-Pad39)") (class "Default")
      (node (ref "SV79") (pin "39") (pinfunction "39_39") (pintype "passive"))
    )
    (net (code "2540") (name "unconnected-(SV79-Pad40)") (class "Default")
      (node (ref "SV79") (pin "40") (pinfunction "40_40") (pintype "passive"))
    )
    (net (code "2541") (name "unconnected-(SV80-Pad1)") (class "Default")
      (node (ref "SV80") (pin "1") (pinfunction "1_1") (pintype "passive"))
    )
    (net (code "2542") (name "unconnected-(SV80-Pad2)") (class "Default")
      (node (ref "SV80") (pin "2") (pinfunction "2_2") (pintype "passive"))
    )
    (net (code "2543") (name "unconnected-(SV80-Pad3)") (class "Default")
      (node (ref "SV80") (pin "3") (pinfunction "3_3") (pintype "passive"))
    )
    (net (code "2544") (name "unconnected-(SV80-Pad4)") (class "Default")
      (node (ref "SV80") (pin "4") (pinfunction "4_4") (pintype "passive"))
    )
    (net (code "2545") (name "unconnected-(SV80-Pad5)") (class "Default")
      (node (ref "SV80") (pin "5") (pinfunction "5_5") (pintype "passive"))
    )
    (net (code "2546") (name "unconnected-(SV80-Pad6)") (class "Default")
      (node (ref "SV80") (pin "6") (pinfunction "6_6") (pintype "passive"))
    )
    (net (code "2547") (name "unconnected-(SV80-Pad7)") (class "Default")
      (node (ref "SV80") (pin "7") (pinfunction "7_7") (pintype "passive"))
    )
    (net (code "2548") (name "unconnected-(SV80-Pad8)") (class "Default")
      (node (ref "SV80") (pin "8") (pinfunction "8_8") (pintype "passive"))
    )
    (net (code "2549") (name "unconnected-(SV80-Pad9)") (class "Default")
      (node (ref "SV80") (pin "9") (pinfunction "9_9") (pintype "passive"))
    )
    (net (code "2550") (name "unconnected-(SV80-Pad10)") (class "Default")
      (node (ref "SV80") (pin "10") (pinfunction "10_10") (pintype "passive"))
    )
    (net (code "2551") (name "unconnected-(SV80-Pad11)") (class "Default")
      (node (ref "SV80") (pin "11") (pinfunction "11_11") (pintype "passive"))
    )
    (net (code "2552") (name "unconnected-(SV80-Pad12)") (class "Default")
      (node (ref "SV80") (pin "12") (pinfunction "12_12") (pintype "passive"))
    )
    (net (code "2553") (name "unconnected-(SV80-Pad13)") (class "Default")
      (node (ref "SV80") (pin "13") (pinfunction "13_13") (pintype "passive"))
    )
    (net (code "2554") (name "unconnected-(SV80-Pad14)") (class "Default")
      (node (ref "SV80") (pin "14") (pinfunction "14_14") (pintype "passive"))
    )
    (net (code "2555") (name "unconnected-(SV80-Pad15)") (class "Default")
      (node (ref "SV80") (pin "15") (pinfunction "15_15") (pintype "passive"))
    )
    (net (code "2556") (name "unconnected-(SV80-Pad16)") (class "Default")
      (node (ref "SV80") (pin "16") (pinfunction "16_16") (pintype "passive"))
    )
    (net (code "2557") (name "unconnected-(SV80-Pad17)") (class "Default")
      (node (ref "SV80") (pin "17") (pinfunction "17_17") (pintype "passive"))
    )
    (net (code "2558") (name "unconnected-(SV80-Pad18)") (class "Default")
      (node (ref "SV80") (pin "18") (pinfunction "18_18") (pintype "passive"))
    )
    (net (code "2559") (name "unconnected-(SV80-Pad19)") (class "Default")
      (node (ref "SV80") (pin "19") (pinfunction "19_19") (pintype "passive"))
    )
    (net (code "2560") (name "unconnected-(SV80-Pad20)") (class "Default")
      (node (ref "SV80") (pin "20") (pinfunction "20_20") (pintype "passive"))
    )
    (net (code "2561") (name "unconnected-(SV80-Pad21)") (class "Default")
      (node (ref "SV80") (pin "21") (pinfunction "21_21") (pintype "passive"))
    )
    (net (code "2562") (name "unconnected-(SV80-Pad22)") (class "Default")
      (node (ref "SV80") (pin "22") (pinfunction "22_22") (pintype "passive"))
    )
    (net (code "2563") (name "unconnected-(SV80-Pad23)") (class "Default")
      (node (ref "SV80") (pin "23") (pinfunction "23_23") (pintype "passive"))
    )
    (net (code "2564") (name "unconnected-(SV80-Pad24)") (class "Default")
      (node (ref "SV80") (pin "24") (pinfunction "24_24") (pintype "passive"))
    )
    (net (code "2565") (name "unconnected-(SV80-Pad25)") (class "Default")
      (node (ref "SV80") (pin "25") (pinfunction "25_25") (pintype "passive"))
    )
    (net (code "2566") (name "unconnected-(SV80-Pad26)") (class "Default")
      (node (ref "SV80") (pin "26") (pinfunction "26_26") (pintype "passive"))
    )
    (net (code "2567") (name "unconnected-(SV80-Pad27)") (class "Default")
      (node (ref "SV80") (pin "27") (pinfunction "27_27") (pintype "passive"))
    )
    (net (code "2568") (name "unconnected-(SV80-Pad28)") (class "Default")
      (node (ref "SV80") (pin "28") (pinfunction "28_28") (pintype "passive"))
    )
    (net (code "2569") (name "unconnected-(SV80-Pad29)") (class "Default")
      (node (ref "SV80") (pin "29") (pinfunction "29_29") (pintype "passive"))
    )
    (net (code "2570") (name "unconnected-(SV80-Pad30)") (class "Default")
      (node (ref "SV80") (pin "30") (pinfunction "30_30") (pintype "passive"))
    )
    (net (code "2571") (name "unconnected-(SV80-Pad31)") (class "Default")
      (node (ref "SV80") (pin "31") (pinfunction "31_31") (pintype "passive"))
    )
    (net (code "2572") (name "unconnected-(SV80-Pad32)") (class "Default")
      (node (ref "SV80") (pin "32") (pinfunction "32_32") (pintype "passive"))
    )
    (net (code "2573") (name "unconnected-(SV80-Pad33)") (class "Default")
      (node (ref "SV80") (pin "33") (pinfunction "33_33") (pintype "passive"))
    )
    (net (code "2574") (name "unconnected-(SV80-Pad34)") (class "Default")
      (node (ref "SV80") (pin "34") (pinfunction "34_34") (pintype "passive"))
    )
    (net (code "2575") (name "unconnected-(SV80-Pad35)") (class "Default")
      (node (ref "SV80") (pin "35") (pinfunction "35_35") (pintype "passive"))
    )
    (net (code "2576") (name "unconnected-(SV80-Pad36)") (class "Default")
      (node (ref "SV80") (pin "36") (pinfunction "36_36") (pintype "passive"))
    )
    (net (code "2577") (name "unconnected-(SV80-Pad37)") (class "Default")
      (node (ref "SV80") (pin "37") (pinfunction "37_37") (pintype "passive"))
    )
    (net (code "2578") (name "unconnected-(SV80-Pad38)") (class "Default")
      (node (ref "SV80") (pin "38") (pinfunction "38_38") (pintype "passive"))
    )
    (net (code "2579") (name "unconnected-(SV80-Pad39)") (class "Default")
      (node (ref "SV80") (pin "39") (pinfunction "39_39") (pintype "passive"))
    )
    (net (code "2580") (name "unconnected-(SV80-Pad40)") (class "Default")
      (node (ref "SV80") (pin "40") (pinfunction "40_40") (pintype "passive"))
    )
    (net (code "2581") (name "unconnected-(SV81-Pad1)") (class "Default")
      (node (ref "SV81") (pin "1") (pinfunction "1_1") (pintype "passive"))
    )
    (net (code "2582") (name "unconnected-(SV81-Pad2)") (class "Default")
      (node (ref "SV81") (pin "2") (pinfunction "2_2") (pintype "passive"))
    )
    (net (code "2583") (name "unconnected-(SV81-Pad3)") (class "Default")
      (node (ref "SV81") (pin "3") (pinfunction "3_3") (pintype "passive"))
    )
    (net (code "2584") (name "unconnected-(SV81-Pad4)") (class "Default")
      (node (ref "SV81") (pin "4") (pinfunction "4_4") (pintype "passive"))
    )
    (net (code "2585") (name "unconnected-(SV81-Pad5)") (class "Default")
      (node (ref "SV81") (pin "5") (pinfunction "5_5") (pintype "passive"))
    )
    (net (code "2586") (name "unconnected-(SV81-Pad6)") (class "Default")
      (node (ref "SV81") (pin "6") (pinfunction "6_6") (pintype "passive"))
    )
    (net (code "2587") (name "unconnected-(SV81-Pad7)") (class "Default")
      (node (ref "SV81") (pin "7") (pinfunction "7_7") (pintype "passive"))
    )
    (net (code "2588") (name "unconnected-(SV81-Pad8)") (class "Default")
      (node (ref "SV81") (pin "8") (pinfunction "8_8") (pintype "passive"))
    )
    (net (code "2589") (name "unconnected-(SV81-Pad9)") (class "Default")
      (node (ref "SV81") (pin "9") (pinfunction "9_9") (pintype "passive"))
    )
    (net (code "2590") (name "unconnected-(SV81-Pad10)") (class "Default")
      (node (ref "SV81") (pin "10") (pinfunction "10_10") (pintype "passive"))
    )
    (net (code "2591") (name "unconnected-(SV81-Pad11)") (class "Default")
      (node (ref "SV81") (pin "11") (pinfunction "11_11") (pintype "passive"))
    )
    (net (code "2592") (name "unconnected-(SV81-Pad12)") (class "Default")
      (node (ref "SV81") (pin "12") (pinfunction "12_12") (pintype "passive"))
    )
    (net (code "2593") (name "unconnected-(SV81-Pad13)") (class "Default")
      (node (ref "SV81") (pin "13") (pinfunction "13_13") (pintype "passive"))
    )
    (net (code "2594") (name "unconnected-(SV81-Pad14)") (class "Default")
      (node (ref "SV81") (pin "14") (pinfunction "14_14") (pintype "passive"))
    )
    (net (code "2595") (name "unconnected-(SV81-Pad15)") (class "Default")
      (node (ref "SV81") (pin "15") (pinfunction "15_15") (pintype "passive"))
    )
    (net (code "2596") (name "unconnected-(SV81-Pad16)") (class "Default")
      (node (ref "SV81") (pin "16") (pinfunction "16_16") (pintype "passive"))
    )
    (net (code "2597") (name "unconnected-(SV81-Pad17)") (class "Default")
      (node (ref "SV81") (pin "17") (pinfunction "17_17") (pintype "passive"))
    )
    (net (code "2598") (name "unconnected-(SV81-Pad18)") (class "Default")
      (node (ref "SV81") (pin "18") (pinfunction "18_18") (pintype "passive"))
    )
    (net (code "2599") (name "unconnected-(SV81-Pad19)") (class "Default")
      (node (ref "SV81") (pin "19") (pinfunction "19_19") (pintype "passive"))
    )
    (net (code "2600") (name "unconnected-(SV81-Pad20)") (class "Default")
      (node (ref "SV81") (pin "20") (pinfunction "20_20") (pintype "passive"))
    )
    (net (code "2601") (name "unconnected-(SV81-Pad21)") (class "Default")
      (node (ref "SV81") (pin "21") (pinfunction "21_21") (pintype "passive"))
    )
    (net (code "2602") (name "unconnected-(SV81-Pad22)") (class "Default")
      (node (ref "SV81") (pin "22") (pinfunction "22_22") (pintype "passive"))
    )
    (net (code "2603") (name "unconnected-(SV81-Pad23)") (class "Default")
      (node (ref "SV81") (pin "23") (pinfunction "23_23") (pintype "passive"))
    )
    (net (code "2604") (name "unconnected-(SV81-Pad24)") (class "Default")
      (node (ref "SV81") (pin "24") (pinfunction "24_24") (pintype "passive"))
    )
    (net (code "2605") (name "unconnected-(SV81-Pad25)") (class "Default")
      (node (ref "SV81") (pin "25") (pinfunction "25_25") (pintype "passive"))
    )
    (net (code "2606") (name "unconnected-(SV81-Pad26)") (class "Default")
      (node (ref "SV81") (pin "26") (pinfunction "26_26") (pintype "passive"))
    )
    (net (code "2607") (name "unconnected-(SV81-Pad27)") (class "Default")
      (node (ref "SV81") (pin "27") (pinfunction "27_27") (pintype "passive"))
    )
    (net (code "2608") (name "unconnected-(SV81-Pad28)") (class "Default")
      (node (ref "SV81") (pin "28") (pinfunction "28_28") (pintype "passive"))
    )
    (net (code "2609") (name "unconnected-(SV81-Pad29)") (class "Default")
      (node (ref "SV81") (pin "29") (pinfunction "29_29") (pintype "passive"))
    )
    (net (code "2610") (name "unconnected-(SV81-Pad30)") (class "Default")
      (node (ref "SV81") (pin "30") (pinfunction "30_30") (pintype "passive"))
    )
    (net (code "2611") (name "unconnected-(SV81-Pad31)") (class "Default")
      (node (ref "SV81") (pin "31") (pinfunction "31_31") (pintype "passive"))
    )
    (net (code "2612") (name "unconnected-(SV81-Pad32)") (class "Default")
      (node (ref "SV81") (pin "32") (pinfunction "32_32") (pintype "passive"))
    )
    (net (code "2613") (name "unconnected-(SV81-Pad33)") (class "Default")
      (node (ref "SV81") (pin "33") (pinfunction "33_33") (pintype "passive"))
    )
    (net (code "2614") (name "unconnected-(SV81-Pad34)") (class "Default")
      (node (ref "SV81") (pin "34") (pinfunction "34_34") (pintype "passive"))
    )
    (net (code "2615") (name "unconnected-(SV81-Pad35)") (class "Default")
      (node (ref "SV81") (pin "35") (pinfunction "35_35") (pintype "passive"))
    )
    (net (code "2616") (name "unconnected-(SV81-Pad36)") (class "Default")
      (node (ref "SV81") (pin "36") (pinfunction "36_36") (pintype "passive"))
    )
    (net (code "2617") (name "unconnected-(SV81-Pad37)") (class "Default")
      (node (ref "SV81") (pin "37") (pinfunction "37_37") (pintype "passive"))
    )
    (net (code "2618") (name "unconnected-(SV81-Pad38)") (class "Default")
      (node (ref "SV81") (pin "38") (pinfunction "38_38") (pintype "passive"))
    )
    (net (code "2619") (name "unconnected-(SV81-Pad39)") (class "Default")
      (node (ref "SV81") (pin "39") (pinfunction "39_39") (pintype "passive"))
    )
    (net (code "2620") (name "unconnected-(SV81-Pad40)") (class "Default")
      (node (ref "SV81") (pin "40") (pinfunction "40_40") (pintype "passive"))
    )
    (net (code "2621") (name "unconnected-(SV82-Pad1)") (class "Default")
      (node (ref "SV82") (pin "1") (pinfunction "1_1") (pintype "passive"))
    )
    (net (code "2622") (name "unconnected-(SV82-Pad2)") (class "Default")
      (node (ref "SV82") (pin "2") (pinfunction "2_2") (pintype "passive"))
    )
    (net (code "2623") (name "unconnected-(SV82-Pad3)") (class "Default")
      (node (ref "SV82") (pin "3") (pinfunction "3_3") (pintype "passive"))
    )
    (net (code "2624") (name "unconnected-(SV82-Pad4)") (class "Default")
      (node (ref "SV82") (pin "4") (pinfunction "4_4") (pintype "passive"))
    )
    (net (code "2625") (name "unconnected-(SV82-Pad5)") (class "Default")
      (node (ref "SV82") (pin "5") (pinfunction "5_5") (pintype "passive"))
    )
    (net (code "2626") (name "unconnected-(SV82-Pad6)") (class "Default")
      (node (ref "SV82") (pin "6") (pinfunction "6_6") (pintype "passive"))
    )
    (net (code "2627") (name "unconnected-(SV82-Pad7)") (class "Default")
      (node (ref "SV82") (pin "7") (pinfunction "7_7") (pintype "passive"))
    )
    (net (code "2628") (name "unconnected-(SV82-Pad8)") (class "Default")
      (node (ref "SV82") (pin "8") (pinfunction "8_8") (pintype "passive"))
    )
    (net (code "2629") (name "unconnected-(SV82-Pad9)") (class "Default")
      (node (ref "SV82") (pin "9") (pinfunction "9_9") (pintype "passive"))
    )
    (net (code "2630") (name "unconnected-(SV82-Pad10)") (class "Default")
      (node (ref "SV82") (pin "10") (pinfunction "10_10") (pintype "passive"))
    )
    (net (code "2631") (name "unconnected-(SV82-Pad11)") (class "Default")
      (node (ref "SV82") (pin "11") (pinfunction "11_11") (pintype "passive"))
    )
    (net (code "2632") (name "unconnected-(SV82-Pad12)") (class "Default")
      (node (ref "SV82") (pin "12") (pinfunction "12_12") (pintype "passive"))
    )
    (net (code "2633") (name "unconnected-(SV82-Pad13)") (class "Default")
      (node (ref "SV82") (pin "13") (pinfunction "13_13") (pintype "passive"))
    )
    (net (code "2634") (name "unconnected-(SV82-Pad14)") (class "Default")
      (node (ref "SV82") (pin "14") (pinfunction "14_14") (pintype "passive"))
    )
    (net (code "2635") (name "unconnected-(SV82-Pad15)") (class "Default")
      (node (ref "SV82") (pin "15") (pinfunction "15_15") (pintype "passive"))
    )
    (net (code "2636") (name "unconnected-(SV82-Pad16)") (class "Default")
      (node (ref "SV82") (pin "16") (pinfunction "16_16") (pintype "passive"))
    )
    (net (code "2637") (name "unconnected-(SV82-Pad17)") (class "Default")
      (node (ref "SV82") (pin "17") (pinfunction "17_17") (pintype "passive"))
    )
    (net (code "2638") (name "unconnected-(SV82-Pad18)") (class "Default")
      (node (ref "SV82") (pin "18") (pinfunction "18_18") (pintype "passive"))
    )
    (net (code "2639") (name "unconnected-(SV82-Pad19)") (class "Default")
      (node (ref "SV82") (pin "19") (pinfunction "19_19") (pintype "passive"))
    )
    (net (code "2640") (name "unconnected-(SV82-Pad20)") (class "Default")
      (node (ref "SV82") (pin "20") (pinfunction "20_20") (pintype "passive"))
    )
    (net (code "2641") (name "unconnected-(SV82-Pad21)") (class "Default")
      (node (ref "SV82") (pin "21") (pinfunction "21_21") (pintype "passive"))
    )
    (net (code "2642") (name "unconnected-(SV82-Pad22)") (class "Default")
      (node (ref "SV82") (pin "22") (pinfunction "22_22") (pintype "passive"))
    )
    (net (code "2643") (name "unconnected-(SV82-Pad23)") (class "Default")
      (node (ref "SV82") (pin "23") (pinfunction "23_23") (pintype "passive"))
    )
    (net (code "2644") (name "unconnected-(SV82-Pad24)") (class "Default")
      (node (ref "SV82") (pin "24") (pinfunction "24_24") (pintype "passive"))
    )
    (net (code "2645") (name "unconnected-(SV82-Pad25)") (class "Default")
      (node (ref "SV82") (pin "25") (pinfunction "25_25") (pintype "passive"))
    )
    (net (code "2646") (name "unconnected-(SV82-Pad26)") (class "Default")
      (node (ref "SV82") (pin "26") (pinfunction "26_26") (pintype "passive"))
    )
    (net (code "2647") (name "unconnected-(SV82-Pad27)") (class "Default")
      (node (ref "SV82") (pin "27") (pinfunction "27_27") (pintype "passive"))
    )
    (net (code "2648") (name "unconnected-(SV82-Pad28)") (class "Default")
      (node (ref "SV82") (pin "28") (pinfunction "28_28") (pintype "passive"))
    )
    (net (code "2649") (name "unconnected-(SV82-Pad29)") (class "Default")
      (node (ref "SV82") (pin "29") (pinfunction "29_29") (pintype "passive"))
    )
    (net (code "2650") (name "unconnected-(SV82-Pad30)") (class "Default")
      (node (ref "SV82") (pin "30") (pinfunction "30_30") (pintype "passive"))
    )
    (net (code "2651") (name "unconnected-(SV82-Pad31)") (class "Default")
      (node (ref "SV82") (pin "31") (pinfunction "31_31") (pintype "passive"))
    )
    (net (code "2652") (name "unconnected-(SV82-Pad32)") (class "Default")
      (node (ref "SV82") (pin "32") (pinfunction "32_32") (pintype "passive"))
    )
    (net (code "2653") (name "unconnected-(SV82-Pad33)") (class "Default")
      (node (ref "SV82") (pin "33") (pinfunction "33_33") (pintype "passive"))
    )
    (net (code "2654") (name "unconnected-(SV82-Pad34)") (class "Default")
      (node (ref "SV82") (pin "34") (pinfunction "34_34") (pintype "passive"))
    )
    (net (code "2655") (name "unconnected-(SV82-Pad35)") (class "Default")
      (node (ref "SV82") (pin "35") (pinfunction "35_35") (pintype "passive"))
    )
    (net (code "2656") (name "unconnected-(SV82-Pad36)") (class "Default")
      (node (ref "SV82") (pin "36") (pinfunction "36_36") (pintype "passive"))
    )
    (net (code "2657") (name "unconnected-(SV83-Pad1)") (class "Default")
      (node (ref "SV83") (pin "1") (pinfunction "1_1") (pintype "passive"))
    )
    (net (code "2658") (name "unconnected-(SV83-Pad2)") (class "Default")
      (node (ref "SV83") (pin "2") (pinfunction "2_2") (pintype "passive"))
    )
    (net (code "2659") (name "unconnected-(SV83-Pad3)") (class "Default")
      (node (ref "SV83") (pin "3") (pinfunction "3_3") (pintype "passive"))
    )
    (net (code "2660") (name "unconnected-(SV83-Pad4)") (class "Default")
      (node (ref "SV83") (pin "4") (pinfunction "4_4") (pintype "passive"))
    )
    (net (code "2661") (name "unconnected-(SV83-Pad5)") (class "Default")
      (node (ref "SV83") (pin "5") (pinfunction "5_5") (pintype "passive"))
    )
    (net (code "2662") (name "unconnected-(SV83-Pad6)") (class "Default")
      (node (ref "SV83") (pin "6") (pinfunction "6_6") (pintype "passive"))
    )
    (net (code "2663") (name "unconnected-(SV83-Pad7)") (class "Default")
      (node (ref "SV83") (pin "7") (pinfunction "7_7") (pintype "passive"))
    )
    (net (code "2664") (name "unconnected-(SV83-Pad8)") (class "Default")
      (node (ref "SV83") (pin "8") (pinfunction "8_8") (pintype "passive"))
    )
    (net (code "2665") (name "unconnected-(SV83-Pad9)") (class "Default")
      (node (ref "SV83") (pin "9") (pinfunction "9_9") (pintype "passive"))
    )
    (net (code "2666") (name "unconnected-(SV83-Pad10)") (class "Default")
      (node (ref "SV83") (pin "10") (pinfunction "10_10") (pintype "passive"))
    )
    (net (code "2667") (name "unconnected-(SV83-Pad11)") (class "Default")
      (node (ref "SV83") (pin "11") (pinfunction "11_11") (pintype "passive"))
    )
    (net (code "2668") (name "unconnected-(SV83-Pad12)") (class "Default")
      (node (ref "SV83") (pin "12") (pinfunction "12_12") (pintype "passive"))
    )
    (net (code "2669") (name "unconnected-(SV83-Pad13)") (class "Default")
      (node (ref "SV83") (pin "13") (pinfunction "13_13") (pintype "passive"))
    )
    (net (code "2670") (name "unconnected-(SV83-Pad14)") (class "Default")
      (node (ref "SV83") (pin "14") (pinfunction "14_14") (pintype "passive"))
    )
    (net (code "2671") (name "unconnected-(SV83-Pad15)") (class "Default")
      (node (ref "SV83") (pin "15") (pinfunction "15_15") (pintype "passive"))
    )
    (net (code "2672") (name "unconnected-(SV83-Pad16)") (class "Default")
      (node (ref "SV83") (pin "16") (pinfunction "16_16") (pintype "passive"))
    )
    (net (code "2673") (name "unconnected-(SV83-Pad17)") (class "Default")
      (node (ref "SV83") (pin "17") (pinfunction "17_17") (pintype "passive"))
    )
    (net (code "2674") (name "unconnected-(SV83-Pad18)") (class "Default")
      (node (ref "SV83") (pin "18") (pinfunction "18_18") (pintype "passive"))
    )
    (net (code "2675") (name "unconnected-(SV83-Pad19)") (class "Default")
      (node (ref "SV83") (pin "19") (pinfunction "19_19") (pintype "passive"))
    )
    (net (code "2676") (name "unconnected-(SV83-Pad20)") (class "Default")
      (node (ref "SV83") (pin "20") (pinfunction "20_20") (pintype "passive"))
    )
    (net (code "2677") (name "unconnected-(SV83-Pad21)") (class "Default")
      (node (ref "SV83") (pin "21") (pinfunction "21_21") (pintype "passive"))
    )
    (net (code "2678") (name "unconnected-(SV83-Pad22)") (class "Default")
      (node (ref "SV83") (pin "22") (pinfunction "22_22") (pintype "passive"))
    )
    (net (code "2679") (name "unconnected-(SV83-Pad23)") (class "Default")
      (node (ref "SV83") (pin "23") (pinfunction "23_23") (pintype "passive"))
    )
    (net (code "2680") (name "unconnected-(SV83-Pad24)") (class "Default")
      (node (ref "SV83") (pin "24") (pinfunction "24_24") (pintype "passive"))
    )
    (net (code "2681") (name "unconnected-(SV83-Pad25)") (class "Default")
      (node (ref "SV83") (pin "25") (pinfunction "25_25") (pintype "passive"))
    )
    (net (code "2682") (name "unconnected-(SV83-Pad26)") (class "Default")
      (node (ref "SV83") (pin "26") (pinfunction "26_26") (pintype "passive"))
    )
    (net (code "2683") (name "unconnected-(SV83-Pad27)") (class "Default")
      (node (ref "SV83") (pin "27") (pinfunction "27_27") (pintype "passive"))
    )
    (net (code "2684") (name "unconnected-(SV83-Pad28)") (class "Default")
      (node (ref "SV83") (pin "28") (pinfunction "28_28") (pintype "passive"))
    )
    (net (code "2685") (name "unconnected-(SV83-Pad29)") (class "Default")
      (node (ref "SV83") (pin "29") (pinfunction "29_29") (pintype "passive"))
    )
    (net (code "2686") (name "unconnected-(SV83-Pad30)") (class "Default")
      (node (ref "SV83") (pin "30") (pinfunction "30_30") (pintype "passive"))
    )
    (net (code "2687") (name "unconnected-(SV83-Pad31)") (class "Default")
      (node (ref "SV83") (pin "31") (pinfunction "31_31") (pintype "passive"))
    )
    (net (code "2688") (name "unconnected-(SV83-Pad32)") (class "Default")
      (node (ref "SV83") (pin "32") (pinfunction "32_32") (pintype "passive"))
    )
    (net (code "2689") (name "unconnected-(SV83-Pad33)") (class "Default")
      (node (ref "SV83") (pin "33") (pinfunction "33_33") (pintype "passive"))
    )
    (net (code "2690") (name "unconnected-(SV83-Pad34)") (class "Default")
      (node (ref "SV83") (pin "34") (pinfunction "34_34") (pintype "passive"))
    )
    (net (code "2691") (name "unconnected-(SV83-Pad35)") (class "Default")
      (node (ref "SV83") (pin "35") (pinfunction "35_35") (pintype "passive"))
    )
    (net (code "2692") (name "unconnected-(SV83-Pad36)") (class "Default")
      (node (ref "SV83") (pin "36") (pinfunction "36_36") (pintype "passive"))
    )
    (net (code "2693") (name "unconnected-(SV84-Pad1)") (class "Default")
      (node (ref "SV84") (pin "1") (pinfunction "1_1") (pintype "passive"))
    )
    (net (code "2694") (name "unconnected-(SV84-Pad2)") (class "Default")
      (node (ref "SV84") (pin "2") (pinfunction "2_2") (pintype "passive"))
    )
    (net (code "2695") (name "unconnected-(SV84-Pad3)") (class "Default")
      (node (ref "SV84") (pin "3") (pinfunction "3_3") (pintype "passive"))
    )
    (net (code "2696") (name "unconnected-(SV84-Pad4)") (class "Default")
      (node (ref "SV84") (pin "4") (pinfunction "4_4") (pintype "passive"))
    )
    (net (code "2697") (name "unconnected-(SV84-Pad5)") (class "Default")
      (node (ref "SV84") (pin "5") (pinfunction "5_5") (pintype "passive"))
    )
    (net (code "2698") (name "unconnected-(SV84-Pad6)") (class "Default")
      (node (ref "SV84") (pin "6") (pinfunction "6_6") (pintype "passive"))
    )
    (net (code "2699") (name "unconnected-(SV84-Pad7)") (class "Default")
      (node (ref "SV84") (pin "7") (pinfunction "7_7") (pintype "passive"))
    )
    (net (code "2700") (name "unconnected-(SV84-Pad8)") (class "Default")
      (node (ref "SV84") (pin "8") (pinfunction "8_8") (pintype "passive"))
    )
    (net (code "2701") (name "unconnected-(SV84-Pad9)") (class "Default")
      (node (ref "SV84") (pin "9") (pinfunction "9_9") (pintype "passive"))
    )
    (net (code "2702") (name "unconnected-(SV84-Pad10)") (class "Default")
      (node (ref "SV84") (pin "10") (pinfunction "10_10") (pintype "passive"))
    )
    (net (code "2703") (name "unconnected-(SV84-Pad11)") (class "Default")
      (node (ref "SV84") (pin "11") (pinfunction "11_11") (pintype "passive"))
    )
    (net (code "2704") (name "unconnected-(SV84-Pad12)") (class "Default")
      (node (ref "SV84") (pin "12") (pinfunction "12_12") (pintype "passive"))
    )
    (net (code "2705") (name "unconnected-(SV84-Pad13)") (class "Default")
      (node (ref "SV84") (pin "13") (pinfunction "13_13") (pintype "passive"))
    )
    (net (code "2706") (name "unconnected-(SV84-Pad14)") (class "Default")
      (node (ref "SV84") (pin "14") (pinfunction "14_14") (pintype "passive"))
    )
    (net (code "2707") (name "unconnected-(SV84-Pad15)") (class "Default")
      (node (ref "SV84") (pin "15") (pinfunction "15_15") (pintype "passive"))
    )
    (net (code "2708") (name "unconnected-(SV84-Pad16)") (class "Default")
      (node (ref "SV84") (pin "16") (pinfunction "16_16") (pintype "passive"))
    )
    (net (code "2709") (name "unconnected-(SV84-Pad17)") (class "Default")
      (node (ref "SV84") (pin "17") (pinfunction "17_17") (pintype "passive"))
    )
    (net (code "2710") (name "unconnected-(SV84-Pad18)") (class "Default")
      (node (ref "SV84") (pin "18") (pinfunction "18_18") (pintype "passive"))
    )
    (net (code "2711") (name "unconnected-(SV84-Pad19)") (class "Default")
      (node (ref "SV84") (pin "19") (pinfunction "19_19") (pintype "passive"))
    )
    (net (code "2712") (name "unconnected-(SV84-Pad20)") (class "Default")
      (node (ref "SV84") (pin "20") (pinfunction "20_20") (pintype "passive"))
    )
    (net (code "2713") (name "unconnected-(SV84-Pad21)") (class "Default")
      (node (ref "SV84") (pin "21") (pinfunction "21_21") (pintype "passive"))
    )
    (net (code "2714") (name "unconnected-(SV84-Pad22)") (class "Default")
      (node (ref "SV84") (pin "22") (pinfunction "22_22") (pintype "passive"))
    )
    (net (code "2715") (name "unconnected-(SV84-Pad23)") (class "Default")
      (node (ref "SV84") (pin "23") (pinfunction "23_23") (pintype "passive"))
    )
    (net (code "2716") (name "unconnected-(SV84-Pad24)") (class "Default")
      (node (ref "SV84") (pin "24") (pinfunction "24_24") (pintype "passive"))
    )
    (net (code "2717") (name "unconnected-(SV84-Pad25)") (class "Default")
      (node (ref "SV84") (pin "25") (pinfunction "25_25") (pintype "passive"))
    )
    (net (code "2718") (name "unconnected-(SV84-Pad26)") (class "Default")
      (node (ref "SV84") (pin "26") (pinfunction "26_26") (pintype "passive"))
    )
    (net (code "2719") (name "unconnected-(SV84-Pad27)") (class "Default")
      (node (ref "SV84") (pin "27") (pinfunction "27_27") (pintype "passive"))
    )
    (net (code "2720") (name "unconnected-(SV84-Pad28)") (class "Default")
      (node (ref "SV84") (pin "28") (pinfunction "28_28") (pintype "passive"))
    )
    (net (code "2721") (name "unconnected-(SV84-Pad29)") (class "Default")
      (node (ref "SV84") (pin "29") (pinfunction "29_29") (pintype "passive"))
    )
    (net (code "2722") (name "unconnected-(SV84-Pad30)") (class "Default")
      (node (ref "SV84") (pin "30") (pinfunction "30_30") (pintype "passive"))
    )
    (net (code "2723") (name "unconnected-(SV84-Pad31)") (class "Default")
      (node (ref "SV84") (pin "31") (pinfunction "31_31") (pintype "passive"))
    )
    (net (code "2724") (name "unconnected-(SV84-Pad32)") (class "Default")
      (node (ref "SV84") (pin "32") (pinfunction "32_32") (pintype "passive"))
    )
    (net (code "2725") (name "unconnected-(SV84-Pad33)") (class "Default")
      (node (ref "SV84") (pin "33") (pinfunction "33_33") (pintype "passive"))
    )
    (net (code "2726") (name "unconnected-(SV84-Pad34)") (class "Default")
      (node (ref "SV84") (pin "34") (pinfunction "34_34") (pintype "passive"))
    )
    (net (code "2727") (name "unconnected-(SV84-Pad35)") (class "Default")
      (node (ref "SV84") (pin "35") (pinfunction "35_35") (pintype "passive"))
    )
    (net (code "2728") (name "unconnected-(SV84-Pad36)") (class "Default")
      (node (ref "SV84") (pin "36") (pinfunction "36_36") (pintype "passive"))
    )
    (net (code "2729") (name "unconnected-(SV85-Pad1)") (class "Default")
      (node (ref "SV85") (pin "1") (pinfunction "1_1") (pintype "passive"))
    )
    (net (code "2730") (name "unconnected-(SV85-Pad2)") (class "Default")
      (node (ref "SV85") (pin "2") (pinfunction "2_2") (pintype "passive"))
    )
    (net (code "2731") (name "unconnected-(SV85-Pad3)") (class "Default")
      (node (ref "SV85") (pin "3") (pinfunction "3_3") (pintype "passive"))
    )
    (net (code "2732") (name "unconnected-(SV85-Pad4)") (class "Default")
      (node (ref "SV85") (pin "4") (pinfunction "4_4") (pintype "passive"))
    )
    (net (code "2733") (name "unconnected-(SV85-Pad5)") (class "Default")
      (node (ref "SV85") (pin "5") (pinfunction "5_5") (pintype "passive"))
    )
    (net (code "2734") (name "unconnected-(SV85-Pad6)") (class "Default")
      (node (ref "SV85") (pin "6") (pinfunction "6_6") (pintype "passive"))
    )
    (net (code "2735") (name "unconnected-(SV85-Pad7)") (class "Default")
      (node (ref "SV85") (pin "7") (pinfunction "7_7") (pintype "passive"))
    )
    (net (code "2736") (name "unconnected-(SV85-Pad8)") (class "Default")
      (node (ref "SV85") (pin "8") (pinfunction "8_8") (pintype "passive"))
    )
    (net (code "2737") (name "unconnected-(SV85-Pad9)") (class "Default")
      (node (ref "SV85") (pin "9") (pinfunction "9_9") (pintype "passive"))
    )
    (net (code "2738") (name "unconnected-(SV85-Pad10)") (class "Default")
      (node (ref "SV85") (pin "10") (pinfunction "10_10") (pintype "passive"))
    )
    (net (code "2739") (name "unconnected-(SV85-Pad11)") (class "Default")
      (node (ref "SV85") (pin "11") (pinfunction "11_11") (pintype "passive"))
    )
    (net (code "2740") (name "unconnected-(SV85-Pad12)") (class "Default")
      (node (ref "SV85") (pin "12") (pinfunction "12_12") (pintype "passive"))
    )
    (net (code "2741") (name "unconnected-(SV85-Pad13)") (class "Default")
      (node (ref "SV85") (pin "13") (pinfunction "13_13") (pintype "passive"))
    )
    (net (code "2742") (name "unconnected-(SV85-Pad14)") (class "Default")
      (node (ref "SV85") (pin "14") (pinfunction "14_14") (pintype "passive"))
    )
    (net (code "2743") (name "unconnected-(SV85-Pad15)") (class "Default")
      (node (ref "SV85") (pin "15") (pinfunction "15_15") (pintype "passive"))
    )
    (net (code "2744") (name "unconnected-(SV85-Pad16)") (class "Default")
      (node (ref "SV85") (pin "16") (pinfunction "16_16") (pintype "passive"))
    )
    (net (code "2745") (name "unconnected-(SV85-Pad17)") (class "Default")
      (node (ref "SV85") (pin "17") (pinfunction "17_17") (pintype "passive"))
    )
    (net (code "2746") (name "unconnected-(SV85-Pad18)") (class "Default")
      (node (ref "SV85") (pin "18") (pinfunction "18_18") (pintype "passive"))
    )
    (net (code "2747") (name "unconnected-(SV85-Pad19)") (class "Default")
      (node (ref "SV85") (pin "19") (pinfunction "19_19") (pintype "passive"))
    )
    (net (code "2748") (name "unconnected-(SV85-Pad20)") (class "Default")
      (node (ref "SV85") (pin "20") (pinfunction "20_20") (pintype "passive"))
    )
    (net (code "2749") (name "unconnected-(SV85-Pad21)") (class "Default")
      (node (ref "SV85") (pin "21") (pinfunction "21_21") (pintype "passive"))
    )
    (net (code "2750") (name "unconnected-(SV85-Pad22)") (class "Default")
      (node (ref "SV85") (pin "22") (pinfunction "22_22") (pintype "passive"))
    )
    (net (code "2751") (name "unconnected-(SV85-Pad23)") (class "Default")
      (node (ref "SV85") (pin "23") (pinfunction "23_23") (pintype "passive"))
    )
    (net (code "2752") (name "unconnected-(SV85-Pad24)") (class "Default")
      (node (ref "SV85") (pin "24") (pinfunction "24_24") (pintype "passive"))
    )
    (net (code "2753") (name "unconnected-(SV85-Pad25)") (class "Default")
      (node (ref "SV85") (pin "25") (pinfunction "25_25") (pintype "passive"))
    )
    (net (code "2754") (name "unconnected-(SV85-Pad26)") (class "Default")
      (node (ref "SV85") (pin "26") (pinfunction "26_26") (pintype "passive"))
    )
    (net (code "2755") (name "unconnected-(SV85-Pad27)") (class "Default")
      (node (ref "SV85") (pin "27") (pinfunction "27_27") (pintype "passive"))
    )
    (net (code "2756") (name "unconnected-(SV85-Pad28)") (class "Default")
      (node (ref "SV85") (pin "28") (pinfunction "28_28") (pintype "passive"))
    )
    (net (code "2757") (name "unconnected-(SV85-Pad29)") (class "Default")
      (node (ref "SV85") (pin "29") (pinfunction "29_29") (pintype "passive"))
    )
    (net (code "2758") (name "unconnected-(SV85-Pad30)") (class "Default")
      (node (ref "SV85") (pin "30") (pinfunction "30_30") (pintype "passive"))
    )
    (net (code "2759") (name "unconnected-(SV85-Pad31)") (class "Default")
      (node (ref "SV85") (pin "31") (pinfunction "31_31") (pintype "passive"))
    )
    (net (code "2760") (name "unconnected-(SV85-Pad32)") (class "Default")
      (node (ref "SV85") (pin "32") (pinfunction "32_32") (pintype "passive"))
    )
    (net (code "2761") (name "unconnected-(SV85-Pad33)") (class "Default")
      (node (ref "SV85") (pin "33") (pinfunction "33_33") (pintype "passive"))
    )
    (net (code "2762") (name "unconnected-(SV85-Pad34)") (class "Default")
      (node (ref "SV85") (pin "34") (pinfunction "34_34") (pintype "passive"))
    )
    (net (code "2763") (name "unconnected-(SV85-Pad35)") (class "Default")
      (node (ref "SV85") (pin "35") (pinfunction "35_35") (pintype "passive"))
    )
    (net (code "2764") (name "unconnected-(SV85-Pad36)") (class "Default")
      (node (ref "SV85") (pin "36") (pinfunction "36_36") (pintype "passive"))
    )
    (net (code "2765") (name "unconnected-(SV86-Pad1)") (class "Default")
      (node (ref "SV86") (pin "1") (pinfunction "1_1") (pintype "passive"))
    )
    (net (code "2766") (name "unconnected-(SV86-Pad2)") (class "Default")
      (node (ref "SV86") (pin "2") (pinfunction "2_2") (pintype "passive"))
    )
    (net (code "2767") (name "unconnected-(SV86-Pad3)") (class "Default")
      (node (ref "SV86") (pin "3") (pinfunction "3_3") (pintype "passive"))
    )
    (net (code "2768") (name "unconnected-(SV86-Pad4)") (class "Default")
      (node (ref "SV86") (pin "4") (pinfunction "4_4") (pintype "passive"))
    )
    (net (code "2769") (name "unconnected-(SV86-Pad5)") (class "Default")
      (node (ref "SV86") (pin "5") (pinfunction "5_5") (pintype "passive"))
    )
    (net (code "2770") (name "unconnected-(SV86-Pad6)") (class "Default")
      (node (ref "SV86") (pin "6") (pinfunction "6_6") (pintype "passive"))
    )
    (net (code "2771") (name "unconnected-(SV86-Pad7)") (class "Default")
      (node (ref "SV86") (pin "7") (pinfunction "7_7") (pintype "passive"))
    )
    (net (code "2772") (name "unconnected-(SV86-Pad8)") (class "Default")
      (node (ref "SV86") (pin "8") (pinfunction "8_8") (pintype "passive"))
    )
    (net (code "2773") (name "unconnected-(SV86-Pad9)") (class "Default")
      (node (ref "SV86") (pin "9") (pinfunction "9_9") (pintype "passive"))
    )
    (net (code "2774") (name "unconnected-(SV86-Pad10)") (class "Default")
      (node (ref "SV86") (pin "10") (pinfunction "10_10") (pintype "passive"))
    )
    (net (code "2775") (name "unconnected-(SV86-Pad11)") (class "Default")
      (node (ref "SV86") (pin "11") (pinfunction "11_11") (pintype "passive"))
    )
    (net (code "2776") (name "unconnected-(SV86-Pad12)") (class "Default")
      (node (ref "SV86") (pin "12") (pinfunction "12_12") (pintype "passive"))
    )
    (net (code "2777") (name "unconnected-(SV86-Pad13)") (class "Default")
      (node (ref "SV86") (pin "13") (pinfunction "13_13") (pintype "passive"))
    )
    (net (code "2778") (name "unconnected-(SV86-Pad14)") (class "Default")
      (node (ref "SV86") (pin "14") (pinfunction "14_14") (pintype "passive"))
    )
    (net (code "2779") (name "unconnected-(SV86-Pad15)") (class "Default")
      (node (ref "SV86") (pin "15") (pinfunction "15_15") (pintype "passive"))
    )
    (net (code "2780") (name "unconnected-(SV86-Pad16)") (class "Default")
      (node (ref "SV86") (pin "16") (pinfunction "16_16") (pintype "passive"))
    )
    (net (code "2781") (name "unconnected-(SV86-Pad17)") (class "Default")
      (node (ref "SV86") (pin "17") (pinfunction "17_17") (pintype "passive"))
    )
    (net (code "2782") (name "unconnected-(SV86-Pad18)") (class "Default")
      (node (ref "SV86") (pin "18") (pinfunction "18_18") (pintype "passive"))
    )
    (net (code "2783") (name "unconnected-(SV86-Pad19)") (class "Default")
      (node (ref "SV86") (pin "19") (pinfunction "19_19") (pintype "passive"))
    )
    (net (code "2784") (name "unconnected-(SV86-Pad20)") (class "Default")
      (node (ref "SV86") (pin "20") (pinfunction "20_20") (pintype "passive"))
    )
    (net (code "2785") (name "unconnected-(SV86-Pad21)") (class "Default")
      (node (ref "SV86") (pin "21") (pinfunction "21_21") (pintype "passive"))
    )
    (net (code "2786") (name "unconnected-(SV86-Pad22)") (class "Default")
      (node (ref "SV86") (pin "22") (pinfunction "22_22") (pintype "passive"))
    )
    (net (code "2787") (name "unconnected-(SV86-Pad23)") (class "Default")
      (node (ref "SV86") (pin "23") (pinfunction "23_23") (pintype "passive"))
    )
    (net (code "2788") (name "unconnected-(SV86-Pad24)") (class "Default")
      (node (ref "SV86") (pin "24") (pinfunction "24_24") (pintype "passive"))
    )
    (net (code "2789") (name "unconnected-(SV86-Pad25)") (class "Default")
      (node (ref "SV86") (pin "25") (pinfunction "25_25") (pintype "passive"))
    )
    (net (code "2790") (name "unconnected-(SV86-Pad26)") (class "Default")
      (node (ref "SV86") (pin "26") (pinfunction "26_26") (pintype "passive"))
    )
    (net (code "2791") (name "unconnected-(SV86-Pad27)") (class "Default")
      (node (ref "SV86") (pin "27") (pinfunction "27_27") (pintype "passive"))
    )
    (net (code "2792") (name "unconnected-(SV86-Pad28)") (class "Default")
      (node (ref "SV86") (pin "28") (pinfunction "28_28") (pintype "passive"))
    )
    (net (code "2793") (name "unconnected-(SV86-Pad29)") (class "Default")
      (node (ref "SV86") (pin "29") (pinfunction "29_29") (pintype "passive"))
    )
    (net (code "2794") (name "unconnected-(SV86-Pad30)") (class "Default")
      (node (ref "SV86") (pin "30") (pinfunction "30_30") (pintype "passive"))
    )
    (net (code "2795") (name "unconnected-(SV86-Pad31)") (class "Default")
      (node (ref "SV86") (pin "31") (pinfunction "31_31") (pintype "passive"))
    )
    (net (code "2796") (name "unconnected-(SV86-Pad32)") (class "Default")
      (node (ref "SV86") (pin "32") (pinfunction "32_32") (pintype "passive"))
    )
    (net (code "2797") (name "unconnected-(SV86-Pad33)") (class "Default")
      (node (ref "SV86") (pin "33") (pinfunction "33_33") (pintype "passive"))
    )
    (net (code "2798") (name "unconnected-(SV86-Pad34)") (class "Default")
      (node (ref "SV86") (pin "34") (pinfunction "34_34") (pintype "passive"))
    )
    (net (code "2799") (name "unconnected-(SV86-Pad35)") (class "Default")
      (node (ref "SV86") (pin "35") (pinfunction "35_35") (pintype "passive"))
    )
    (net (code "2800") (name "unconnected-(SV86-Pad36)") (class "Default")
      (node (ref "SV86") (pin "36") (pinfunction "36_36") (pintype "passive"))
    )
    (net (code "2801") (name "unconnected-(SV86-Pad37)") (class "Default")
      (node (ref "SV86") (pin "37") (pinfunction "37_37") (pintype "passive"))
    )
    (net (code "2802") (name "unconnected-(SV86-Pad38)") (class "Default")
      (node (ref "SV86") (pin "38") (pinfunction "38_38") (pintype "passive"))
    )
    (net (code "2803") (name "unconnected-(SV86-Pad39)") (class "Default")
      (node (ref "SV86") (pin "39") (pinfunction "39_39") (pintype "passive"))
    )
    (net (code "2804") (name "unconnected-(SV86-Pad40)") (class "Default")
      (node (ref "SV86") (pin "40") (pinfunction "40_40") (pintype "passive"))
    )
    (net (code "2805") (name "unconnected-(SV87-Pad1)") (class "Default")
      (node (ref "SV87") (pin "1") (pinfunction "1_1") (pintype "passive"))
    )
    (net (code "2806") (name "unconnected-(SV87-Pad2)") (class "Default")
      (node (ref "SV87") (pin "2") (pinfunction "2_2") (pintype "passive"))
    )
    (net (code "2807") (name "unconnected-(SV87-Pad3)") (class "Default")
      (node (ref "SV87") (pin "3") (pinfunction "3_3") (pintype "passive"))
    )
    (net (code "2808") (name "unconnected-(SV87-Pad4)") (class "Default")
      (node (ref "SV87") (pin "4") (pinfunction "4_4") (pintype "passive"))
    )
    (net (code "2809") (name "unconnected-(SV87-Pad5)") (class "Default")
      (node (ref "SV87") (pin "5") (pinfunction "5_5") (pintype "passive"))
    )
    (net (code "2810") (name "unconnected-(SV87-Pad6)") (class "Default")
      (node (ref "SV87") (pin "6") (pinfunction "6_6") (pintype "passive"))
    )
    (net (code "2811") (name "unconnected-(SV87-Pad7)") (class "Default")
      (node (ref "SV87") (pin "7") (pinfunction "7_7") (pintype "passive"))
    )
    (net (code "2812") (name "unconnected-(SV87-Pad8)") (class "Default")
      (node (ref "SV87") (pin "8") (pinfunction "8_8") (pintype "passive"))
    )
    (net (code "2813") (name "unconnected-(SV87-Pad9)") (class "Default")
      (node (ref "SV87") (pin "9") (pinfunction "9_9") (pintype "passive"))
    )
    (net (code "2814") (name "unconnected-(SV87-Pad10)") (class "Default")
      (node (ref "SV87") (pin "10") (pinfunction "10_10") (pintype "passive"))
    )
    (net (code "2815") (name "unconnected-(SV87-Pad11)") (class "Default")
      (node (ref "SV87") (pin "11") (pinfunction "11_11") (pintype "passive"))
    )
    (net (code "2816") (name "unconnected-(SV87-Pad12)") (class "Default")
      (node (ref "SV87") (pin "12") (pinfunction "12_12") (pintype "passive"))
    )
    (net (code "2817") (name "unconnected-(SV87-Pad13)") (class "Default")
      (node (ref "SV87") (pin "13") (pinfunction "13_13") (pintype "passive"))
    )
    (net (code "2818") (name "unconnected-(SV87-Pad14)") (class "Default")
      (node (ref "SV87") (pin "14") (pinfunction "14_14") (pintype "passive"))
    )
    (net (code "2819") (name "unconnected-(SV87-Pad15)") (class "Default")
      (node (ref "SV87") (pin "15") (pinfunction "15_15") (pintype "passive"))
    )
    (net (code "2820") (name "unconnected-(SV87-Pad16)") (class "Default")
      (node (ref "SV87") (pin "16") (pinfunction "16_16") (pintype "passive"))
    )
    (net (code "2821") (name "unconnected-(SV87-Pad17)") (class "Default")
      (node (ref "SV87") (pin "17") (pinfunction "17_17") (pintype "passive"))
    )
    (net (code "2822") (name "unconnected-(SV87-Pad18)") (class "Default")
      (node (ref "SV87") (pin "18") (pinfunction "18_18") (pintype "passive"))
    )
    (net (code "2823") (name "unconnected-(SV87-Pad19)") (class "Default")
      (node (ref "SV87") (pin "19") (pinfunction "19_19") (pintype "passive"))
    )
    (net (code "2824") (name "unconnected-(SV87-Pad20)") (class "Default")
      (node (ref "SV87") (pin "20") (pinfunction "20_20") (pintype "passive"))
    )
    (net (code "2825") (name "unconnected-(SV87-Pad21)") (class "Default")
      (node (ref "SV87") (pin "21") (pinfunction "21_21") (pintype "passive"))
    )
    (net (code "2826") (name "unconnected-(SV87-Pad22)") (class "Default")
      (node (ref "SV87") (pin "22") (pinfunction "22_22") (pintype "passive"))
    )
    (net (code "2827") (name "unconnected-(SV87-Pad23)") (class "Default")
      (node (ref "SV87") (pin "23") (pinfunction "23_23") (pintype "passive"))
    )
    (net (code "2828") (name "unconnected-(SV87-Pad24)") (class "Default")
      (node (ref "SV87") (pin "24") (pinfunction "24_24") (pintype "passive"))
    )
    (net (code "2829") (name "unconnected-(SV87-Pad25)") (class "Default")
      (node (ref "SV87") (pin "25") (pinfunction "25_25") (pintype "passive"))
    )
    (net (code "2830") (name "unconnected-(SV87-Pad26)") (class "Default")
      (node (ref "SV87") (pin "26") (pinfunction "26_26") (pintype "passive"))
    )
    (net (code "2831") (name "unconnected-(SV87-Pad27)") (class "Default")
      (node (ref "SV87") (pin "27") (pinfunction "27_27") (pintype "passive"))
    )
    (net (code "2832") (name "unconnected-(SV87-Pad28)") (class "Default")
      (node (ref "SV87") (pin "28") (pinfunction "28_28") (pintype "passive"))
    )
    (net (code "2833") (name "unconnected-(SV87-Pad29)") (class "Default")
      (node (ref "SV87") (pin "29") (pinfunction "29_29") (pintype "passive"))
    )
    (net (code "2834") (name "unconnected-(SV87-Pad30)") (class "Default")
      (node (ref "SV87") (pin "30") (pinfunction "30_30") (pintype "passive"))
    )
    (net (code "2835") (name "unconnected-(SV87-Pad31)") (class "Default")
      (node (ref "SV87") (pin "31") (pinfunction "31_31") (pintype "passive"))
    )
    (net (code "2836") (name "unconnected-(SV87-Pad32)") (class "Default")
      (node (ref "SV87") (pin "32") (pinfunction "32_32") (pintype "passive"))
    )
    (net (code "2837") (name "unconnected-(SV87-Pad33)") (class "Default")
      (node (ref "SV87") (pin "33") (pinfunction "33_33") (pintype "passive"))
    )
    (net (code "2838") (name "unconnected-(SV87-Pad34)") (class "Default")
      (node (ref "SV87") (pin "34") (pinfunction "34_34") (pintype "passive"))
    )
    (net (code "2839") (name "unconnected-(SV87-Pad35)") (class "Default")
      (node (ref "SV87") (pin "35") (pinfunction "35_35") (pintype "passive"))
    )
    (net (code "2840") (name "unconnected-(SV87-Pad36)") (class "Default")
      (node (ref "SV87") (pin "36") (pinfunction "36_36") (pintype "passive"))
    )
    (net (code "2841") (name "unconnected-(SV87-Pad37)") (class "Default")
      (node (ref "SV87") (pin "37") (pinfunction "37_37") (pintype "passive"))
    )
    (net (code "2842") (name "unconnected-(SV87-Pad38)") (class "Default")
      (node (ref "SV87") (pin "38") (pinfunction "38_38") (pintype "passive"))
    )
    (net (code "2843") (name "unconnected-(SV87-Pad39)") (class "Default")
      (node (ref "SV87") (pin "39") (pinfunction "39_39") (pintype "passive"))
    )
    (net (code "2844") (name "unconnected-(SV87-Pad40)") (class "Default")
      (node (ref "SV87") (pin "40") (pinfunction "40_40") (pintype "passive"))
    )
    (net (code "2845") (name "unconnected-(SV88-Pad1)") (class "Default")
      (node (ref "SV88") (pin "1") (pinfunction "1_1") (pintype "passive"))
    )
    (net (code "2846") (name "unconnected-(SV88-Pad2)") (class "Default")
      (node (ref "SV88") (pin "2") (pinfunction "2_2") (pintype "passive"))
    )
    (net (code "2847") (name "unconnected-(SV88-Pad3)") (class "Default")
      (node (ref "SV88") (pin "3") (pinfunction "3_3") (pintype "passive"))
    )
    (net (code "2848") (name "unconnected-(SV88-Pad4)") (class "Default")
      (node (ref "SV88") (pin "4") (pinfunction "4_4") (pintype "passive"))
    )
    (net (code "2849") (name "unconnected-(SV88-Pad5)") (class "Default")
      (node (ref "SV88") (pin "5") (pinfunction "5_5") (pintype "passive"))
    )
    (net (code "2850") (name "unconnected-(SV88-Pad6)") (class "Default")
      (node (ref "SV88") (pin "6") (pinfunction "6_6") (pintype "passive"))
    )
    (net (code "2851") (name "unconnected-(SV88-Pad7)") (class "Default")
      (node (ref "SV88") (pin "7") (pinfunction "7_7") (pintype "passive"))
    )
    (net (code "2852") (name "unconnected-(SV88-Pad8)") (class "Default")
      (node (ref "SV88") (pin "8") (pinfunction "8_8") (pintype "passive"))
    )
    (net (code "2853") (name "unconnected-(SV88-Pad9)") (class "Default")
      (node (ref "SV88") (pin "9") (pinfunction "9_9") (pintype "passive"))
    )
    (net (code "2854") (name "unconnected-(SV88-Pad10)") (class "Default")
      (node (ref "SV88") (pin "10") (pinfunction "10_10") (pintype "passive"))
    )
    (net (code "2855") (name "unconnected-(SV88-Pad11)") (class "Default")
      (node (ref "SV88") (pin "11") (pinfunction "11_11") (pintype "passive"))
    )
    (net (code "2856") (name "unconnected-(SV88-Pad12)") (class "Default")
      (node (ref "SV88") (pin "12") (pinfunction "12_12") (pintype "passive"))
    )
    (net (code "2857") (name "unconnected-(SV88-Pad13)") (class "Default")
      (node (ref "SV88") (pin "13") (pinfunction "13_13") (pintype "passive"))
    )
    (net (code "2858") (name "unconnected-(SV88-Pad14)") (class "Default")
      (node (ref "SV88") (pin "14") (pinfunction "14_14") (pintype "passive"))
    )
    (net (code "2859") (name "unconnected-(SV88-Pad15)") (class "Default")
      (node (ref "SV88") (pin "15") (pinfunction "15_15") (pintype "passive"))
    )
    (net (code "2860") (name "unconnected-(SV88-Pad16)") (class "Default")
      (node (ref "SV88") (pin "16") (pinfunction "16_16") (pintype "passive"))
    )
    (net (code "2861") (name "unconnected-(SV88-Pad17)") (class "Default")
      (node (ref "SV88") (pin "17") (pinfunction "17_17") (pintype "passive"))
    )
    (net (code "2862") (name "unconnected-(SV88-Pad18)") (class "Default")
      (node (ref "SV88") (pin "18") (pinfunction "18_18") (pintype "passive"))
    )
    (net (code "2863") (name "unconnected-(SV88-Pad19)") (class "Default")
      (node (ref "SV88") (pin "19") (pinfunction "19_19") (pintype "passive"))
    )
    (net (code "2864") (name "unconnected-(SV88-Pad20)") (class "Default")
      (node (ref "SV88") (pin "20") (pinfunction "20_20") (pintype "passive"))
    )
    (net (code "2865") (name "unconnected-(SV88-Pad21)") (class "Default")
      (node (ref "SV88") (pin "21") (pinfunction "21_21") (pintype "passive"))
    )
    (net (code "2866") (name "unconnected-(SV88-Pad22)") (class "Default")
      (node (ref "SV88") (pin "22") (pinfunction "22_22") (pintype "passive"))
    )
    (net (code "2867") (name "unconnected-(SV88-Pad23)") (class "Default")
      (node (ref "SV88") (pin "23") (pinfunction "23_23") (pintype "passive"))
    )
    (net (code "2868") (name "unconnected-(SV88-Pad24)") (class "Default")
      (node (ref "SV88") (pin "24") (pinfunction "24_24") (pintype "passive"))
    )
    (net (code "2869") (name "unconnected-(SV88-Pad25)") (class "Default")
      (node (ref "SV88") (pin "25") (pinfunction "25_25") (pintype "passive"))
    )
    (net (code "2870") (name "unconnected-(SV88-Pad26)") (class "Default")
      (node (ref "SV88") (pin "26") (pinfunction "26_26") (pintype "passive"))
    )
    (net (code "2871") (name "unconnected-(SV88-Pad27)") (class "Default")
      (node (ref "SV88") (pin "27") (pinfunction "27_27") (pintype "passive"))
    )
    (net (code "2872") (name "unconnected-(SV88-Pad28)") (class "Default")
      (node (ref "SV88") (pin "28") (pinfunction "28_28") (pintype "passive"))
    )
    (net (code "2873") (name "unconnected-(SV88-Pad29)") (class "Default")
      (node (ref "SV88") (pin "29") (pinfunction "29_29") (pintype "passive"))
    )
    (net (code "2874") (name "unconnected-(SV88-Pad30)") (class "Default")
      (node (ref "SV88") (pin "30") (pinfunction "30_30") (pintype "passive"))
    )
    (net (code "2875") (name "unconnected-(SV88-Pad31)") (class "Default")
      (node (ref "SV88") (pin "31") (pinfunction "31_31") (pintype "passive"))
    )
    (net (code "2876") (name "unconnected-(SV88-Pad32)") (class "Default")
      (node (ref "SV88") (pin "32") (pinfunction "32_32") (pintype "passive"))
    )
    (net (code "2877") (name "unconnected-(SV88-Pad33)") (class "Default")
      (node (ref "SV88") (pin "33") (pinfunction "33_33") (pintype "passive"))
    )
    (net (code "2878") (name "unconnected-(SV88-Pad34)") (class "Default")
      (node (ref "SV88") (pin "34") (pinfunction "34_34") (pintype "passive"))
    )
    (net (code "2879") (name "unconnected-(SV88-Pad35)") (class "Default")
      (node (ref "SV88") (pin "35") (pinfunction "35_35") (pintype "passive"))
    )
    (net (code "2880") (name "unconnected-(SV88-Pad36)") (class "Default")
      (node (ref "SV88") (pin "36") (pinfunction "36_36") (pintype "passive"))
    )
    (net (code "2881") (name "unconnected-(SV88-Pad37)") (class "Default")
      (node (ref "SV88") (pin "37") (pinfunction "37_37") (pintype "passive"))
    )
    (net (code "2882") (name "unconnected-(SV88-Pad38)") (class "Default")
      (node (ref "SV88") (pin "38") (pinfunction "38_38") (pintype "passive"))
    )
    (net (code "2883") (name "unconnected-(SV88-Pad39)") (class "Default")
      (node (ref "SV88") (pin "39") (pinfunction "39_39") (pintype "passive"))
    )
    (net (code "2884") (name "unconnected-(SV88-Pad40)") (class "Default")
      (node (ref "SV88") (pin "40") (pinfunction "40_40") (pintype "passive"))
    )
    (net (code "2885") (name "unconnected-(SV89-Pad1)") (class "Default")
      (node (ref "SV89") (pin "1") (pinfunction "1_1") (pintype "passive"))
    )
    (net (code "2886") (name "unconnected-(SV89-Pad2)") (class "Default")
      (node (ref "SV89") (pin "2") (pinfunction "2_2") (pintype "passive"))
    )
    (net (code "2887") (name "unconnected-(SV89-Pad3)") (class "Default")
      (node (ref "SV89") (pin "3") (pinfunction "3_3") (pintype "passive"))
    )
    (net (code "2888") (name "unconnected-(SV89-Pad4)") (class "Default")
      (node (ref "SV89") (pin "4") (pinfunction "4_4") (pintype "passive"))
    )
    (net (code "2889") (name "unconnected-(SV89-Pad5)") (class "Default")
      (node (ref "SV89") (pin "5") (pinfunction "5_5") (pintype "passive"))
    )
    (net (code "2890") (name "unconnected-(SV89-Pad6)") (class "Default")
      (node (ref "SV89") (pin "6") (pinfunction "6_6") (pintype "passive"))
    )
    (net (code "2891") (name "unconnected-(SV89-Pad7)") (class "Default")
      (node (ref "SV89") (pin "7") (pinfunction "7_7") (pintype "passive"))
    )
    (net (code "2892") (name "unconnected-(SV89-Pad8)") (class "Default")
      (node (ref "SV89") (pin "8") (pinfunction "8_8") (pintype "passive"))
    )
    (net (code "2893") (name "unconnected-(SV89-Pad9)") (class "Default")
      (node (ref "SV89") (pin "9") (pinfunction "9_9") (pintype "passive"))
    )
    (net (code "2894") (name "unconnected-(SV89-Pad10)") (class "Default")
      (node (ref "SV89") (pin "10") (pinfunction "10_10") (pintype "passive"))
    )
    (net (code "2895") (name "unconnected-(SV89-Pad11)") (class "Default")
      (node (ref "SV89") (pin "11") (pinfunction "11_11") (pintype "passive"))
    )
    (net (code "2896") (name "unconnected-(SV89-Pad12)") (class "Default")
      (node (ref "SV89") (pin "12") (pinfunction "12_12") (pintype "passive"))
    )
    (net (code "2897") (name "unconnected-(SV89-Pad13)") (class "Default")
      (node (ref "SV89") (pin "13") (pinfunction "13_13") (pintype "passive"))
    )
    (net (code "2898") (name "unconnected-(SV89-Pad14)") (class "Default")
      (node (ref "SV89") (pin "14") (pinfunction "14_14") (pintype "passive"))
    )
    (net (code "2899") (name "unconnected-(SV89-Pad15)") (class "Default")
      (node (ref "SV89") (pin "15") (pinfunction "15_15") (pintype "passive"))
    )
    (net (code "2900") (name "unconnected-(SV89-Pad16)") (class "Default")
      (node (ref "SV89") (pin "16") (pinfunction "16_16") (pintype "passive"))
    )
    (net (code "2901") (name "unconnected-(SV89-Pad17)") (class "Default")
      (node (ref "SV89") (pin "17") (pinfunction "17_17") (pintype "passive"))
    )
    (net (code "2902") (name "unconnected-(SV89-Pad18)") (class "Default")
      (node (ref "SV89") (pin "18") (pinfunction "18_18") (pintype "passive"))
    )
    (net (code "2903") (name "unconnected-(SV89-Pad19)") (class "Default")
      (node (ref "SV89") (pin "19") (pinfunction "19_19") (pintype "passive"))
    )
    (net (code "2904") (name "unconnected-(SV89-Pad20)") (class "Default")
      (node (ref "SV89") (pin "20") (pinfunction "20_20") (pintype "passive"))
    )
    (net (code "2905") (name "unconnected-(SV89-Pad21)") (class "Default")
      (node (ref "SV89") (pin "21") (pinfunction "21_21") (pintype "passive"))
    )
    (net (code "2906") (name "unconnected-(SV89-Pad22)") (class "Default")
      (node (ref "SV89") (pin "22") (pinfunction "22_22") (pintype "passive"))
    )
    (net (code "2907") (name "unconnected-(SV89-Pad23)") (class "Default")
      (node (ref "SV89") (pin "23") (pinfunction "23_23") (pintype "passive"))
    )
    (net (code "2908") (name "unconnected-(SV89-Pad24)") (class "Default")
      (node (ref "SV89") (pin "24") (pinfunction "24_24") (pintype "passive"))
    )
    (net (code "2909") (name "unconnected-(SV89-Pad25)") (class "Default")
      (node (ref "SV89") (pin "25") (pinfunction "25_25") (pintype "passive"))
    )
    (net (code "2910") (name "unconnected-(SV89-Pad26)") (class "Default")
      (node (ref "SV89") (pin "26") (pinfunction "26_26") (pintype "passive"))
    )
    (net (code "2911") (name "unconnected-(SV89-Pad27)") (class "Default")
      (node (ref "SV89") (pin "27") (pinfunction "27_27") (pintype "passive"))
    )
    (net (code "2912") (name "unconnected-(SV89-Pad28)") (class "Default")
      (node (ref "SV89") (pin "28") (pinfunction "28_28") (pintype "passive"))
    )
    (net (code "2913") (name "unconnected-(SV89-Pad29)") (class "Default")
      (node (ref "SV89") (pin "29") (pinfunction "29_29") (pintype "passive"))
    )
    (net (code "2914") (name "unconnected-(SV89-Pad30)") (class "Default")
      (node (ref "SV89") (pin "30") (pinfunction "30_30") (pintype "passive"))
    )
    (net (code "2915") (name "unconnected-(SV89-Pad31)") (class "Default")
      (node (ref "SV89") (pin "31") (pinfunction "31_31") (pintype "passive"))
    )
    (net (code "2916") (name "unconnected-(SV89-Pad32)") (class "Default")
      (node (ref "SV89") (pin "32") (pinfunction "32_32") (pintype "passive"))
    )
    (net (code "2917") (name "unconnected-(SV89-Pad33)") (class "Default")
      (node (ref "SV89") (pin "33") (pinfunction "33_33") (pintype "passive"))
    )
    (net (code "2918") (name "unconnected-(SV89-Pad34)") (class "Default")
      (node (ref "SV89") (pin "34") (pinfunction "34_34") (pintype "passive"))
    )
    (net (code "2919") (name "unconnected-(SV89-Pad35)") (class "Default")
      (node (ref "SV89") (pin "35") (pinfunction "35_35") (pintype "passive"))
    )
    (net (code "2920") (name "unconnected-(SV89-Pad36)") (class "Default")
      (node (ref "SV89") (pin "36") (pinfunction "36_36") (pintype "passive"))
    )
    (net (code "2921") (name "unconnected-(SV89-Pad37)") (class "Default")
      (node (ref "SV89") (pin "37") (pinfunction "37_37") (pintype "passive"))
    )
    (net (code "2922") (name "unconnected-(SV89-Pad38)") (class "Default")
      (node (ref "SV89") (pin "38") (pinfunction "38_38") (pintype "passive"))
    )
    (net (code "2923") (name "unconnected-(SV89-Pad39)") (class "Default")
      (node (ref "SV89") (pin "39") (pinfunction "39_39") (pintype "passive"))
    )
    (net (code "2924") (name "unconnected-(SV89-Pad40)") (class "Default")
      (node (ref "SV89") (pin "40") (pinfunction "40_40") (pintype "passive"))
    )
    (net (code "2925") (name "unconnected-(SV90-Pad1)") (class "Default")
      (node (ref "SV90") (pin "1") (pinfunction "1_1") (pintype "passive"))
    )
    (net (code "2926") (name "unconnected-(SV90-Pad2)") (class "Default")
      (node (ref "SV90") (pin "2") (pinfunction "2_2") (pintype "passive"))
    )
    (net (code "2927") (name "unconnected-(SV90-Pad3)") (class "Default")
      (node (ref "SV90") (pin "3") (pinfunction "3_3") (pintype "passive"))
    )
    (net (code "2928") (name "unconnected-(SV90-Pad4)") (class "Default")
      (node (ref "SV90") (pin "4") (pinfunction "4_4") (pintype "passive"))
    )
    (net (code "2929") (name "unconnected-(SV90-Pad5)") (class "Default")
      (node (ref "SV90") (pin "5") (pinfunction "5_5") (pintype "passive"))
    )
    (net (code "2930") (name "unconnected-(SV90-Pad6)") (class "Default")
      (node (ref "SV90") (pin "6") (pinfunction "6_6") (pintype "passive"))
    )
    (net (code "2931") (name "unconnected-(SV90-Pad7)") (class "Default")
      (node (ref "SV90") (pin "7") (pinfunction "7_7") (pintype "passive"))
    )
    (net (code "2932") (name "unconnected-(SV90-Pad8)") (class "Default")
      (node (ref "SV90") (pin "8") (pinfunction "8_8") (pintype "passive"))
    )
    (net (code "2933") (name "unconnected-(SV90-Pad9)") (class "Default")
      (node (ref "SV90") (pin "9") (pinfunction "9_9") (pintype "passive"))
    )
    (net (code "2934") (name "unconnected-(SV90-Pad10)") (class "Default")
      (node (ref "SV90") (pin "10") (pinfunction "10_10") (pintype "passive"))
    )
    (net (code "2935") (name "unconnected-(SV90-Pad11)") (class "Default")
      (node (ref "SV90") (pin "11") (pinfunction "11_11") (pintype "passive"))
    )
    (net (code "2936") (name "unconnected-(SV90-Pad12)") (class "Default")
      (node (ref "SV90") (pin "12") (pinfunction "12_12") (pintype "passive"))
    )
    (net (code "2937") (name "unconnected-(SV90-Pad13)") (class "Default")
      (node (ref "SV90") (pin "13") (pinfunction "13_13") (pintype "passive"))
    )
    (net (code "2938") (name "unconnected-(SV90-Pad14)") (class "Default")
      (node (ref "SV90") (pin "14") (pinfunction "14_14") (pintype "passive"))
    )
    (net (code "2939") (name "unconnected-(SV90-Pad15)") (class "Default")
      (node (ref "SV90") (pin "15") (pinfunction "15_15") (pintype "passive"))
    )
    (net (code "2940") (name "unconnected-(SV90-Pad16)") (class "Default")
      (node (ref "SV90") (pin "16") (pinfunction "16_16") (pintype "passive"))
    )
    (net (code "2941") (name "unconnected-(SV90-Pad17)") (class "Default")
      (node (ref "SV90") (pin "17") (pinfunction "17_17") (pintype "passive"))
    )
    (net (code "2942") (name "unconnected-(SV90-Pad18)") (class "Default")
      (node (ref "SV90") (pin "18") (pinfunction "18_18") (pintype "passive"))
    )
    (net (code "2943") (name "unconnected-(SV90-Pad19)") (class "Default")
      (node (ref "SV90") (pin "19") (pinfunction "19_19") (pintype "passive"))
    )
    (net (code "2944") (name "unconnected-(SV90-Pad20)") (class "Default")
      (node (ref "SV90") (pin "20") (pinfunction "20_20") (pintype "passive"))
    )
    (net (code "2945") (name "unconnected-(SV90-Pad21)") (class "Default")
      (node (ref "SV90") (pin "21") (pinfunction "21_21") (pintype "passive"))
    )
    (net (code "2946") (name "unconnected-(SV90-Pad22)") (class "Default")
      (node (ref "SV90") (pin "22") (pinfunction "22_22") (pintype "passive"))
    )
    (net (code "2947") (name "unconnected-(SV90-Pad23)") (class "Default")
      (node (ref "SV90") (pin "23") (pinfunction "23_23") (pintype "passive"))
    )
    (net (code "2948") (name "unconnected-(SV90-Pad24)") (class "Default")
      (node (ref "SV90") (pin "24") (pinfunction "24_24") (pintype "passive"))
    )
    (net (code "2949") (name "unconnected-(SV90-Pad25)") (class "Default")
      (node (ref "SV90") (pin "25") (pinfunction "25_25") (pintype "passive"))
    )
    (net (code "2950") (name "unconnected-(SV90-Pad26)") (class "Default")
      (node (ref "SV90") (pin "26") (pinfunction "26_26") (pintype "passive"))
    )
    (net (code "2951") (name "unconnected-(SV90-Pad27)") (class "Default")
      (node (ref "SV90") (pin "27") (pinfunction "27_27") (pintype "passive"))
    )
    (net (code "2952") (name "unconnected-(SV90-Pad28)") (class "Default")
      (node (ref "SV90") (pin "28") (pinfunction "28_28") (pintype "passive"))
    )
    (net (code "2953") (name "unconnected-(SV90-Pad29)") (class "Default")
      (node (ref "SV90") (pin "29") (pinfunction "29_29") (pintype "passive"))
    )
    (net (code "2954") (name "unconnected-(SV90-Pad30)") (class "Default")
      (node (ref "SV90") (pin "30") (pinfunction "30_30") (pintype "passive"))
    )
    (net (code "2955") (name "unconnected-(SV90-Pad31)") (class "Default")
      (node (ref "SV90") (pin "31") (pinfunction "31_31") (pintype "passive"))
    )
    (net (code "2956") (name "unconnected-(SV90-Pad32)") (class "Default")
      (node (ref "SV90") (pin "32") (pinfunction "32_32") (pintype "passive"))
    )
    (net (code "2957") (name "unconnected-(SV90-Pad33)") (class "Default")
      (node (ref "SV90") (pin "33") (pinfunction "33_33") (pintype "passive"))
    )
    (net (code "2958") (name "unconnected-(SV90-Pad34)") (class "Default")
      (node (ref "SV90") (pin "34") (pinfunction "34_34") (pintype "passive"))
    )
    (net (code "2959") (name "unconnected-(SV90-Pad35)") (class "Default")
      (node (ref "SV90") (pin "35") (pinfunction "35_35") (pintype "passive"))
    )
    (net (code "2960") (name "unconnected-(SV90-Pad36)") (class "Default")
      (node (ref "SV90") (pin "36") (pinfunction "36_36") (pintype "passive"))
    )
    (net (code "2961") (name "unconnected-(SV91-Pad1)") (class "Default")
      (node (ref "SV91") (pin "1") (pinfunction "1_1") (pintype "passive"))
    )
    (net (code "2962") (name "unconnected-(SV91-Pad2)") (class "Default")
      (node (ref "SV91") (pin "2") (pinfunction "2_2") (pintype "passive"))
    )
    (net (code "2963") (name "unconnected-(SV91-Pad3)") (class "Default")
      (node (ref "SV91") (pin "3") (pinfunction "3_3") (pintype "passive"))
    )
    (net (code "2964") (name "unconnected-(SV91-Pad4)") (class "Default")
      (node (ref "SV91") (pin "4") (pinfunction "4_4") (pintype "passive"))
    )
    (net (code "2965") (name "unconnected-(SV91-Pad5)") (class "Default")
      (node (ref "SV91") (pin "5") (pinfunction "5_5") (pintype "passive"))
    )
    (net (code "2966") (name "unconnected-(SV91-Pad6)") (class "Default")
      (node (ref "SV91") (pin "6") (pinfunction "6_6") (pintype "passive"))
    )
    (net (code "2967") (name "unconnected-(SV91-Pad7)") (class "Default")
      (node (ref "SV91") (pin "7") (pinfunction "7_7") (pintype "passive"))
    )
    (net (code "2968") (name "unconnected-(SV91-Pad8)") (class "Default")
      (node (ref "SV91") (pin "8") (pinfunction "8_8") (pintype "passive"))
    )
    (net (code "2969") (name "unconnected-(SV91-Pad9)") (class "Default")
      (node (ref "SV91") (pin "9") (pinfunction "9_9") (pintype "passive"))
    )
    (net (code "2970") (name "unconnected-(SV91-Pad10)") (class "Default")
      (node (ref "SV91") (pin "10") (pinfunction "10_10") (pintype "passive"))
    )
    (net (code "2971") (name "unconnected-(SV91-Pad11)") (class "Default")
      (node (ref "SV91") (pin "11") (pinfunction "11_11") (pintype "passive"))
    )
    (net (code "2972") (name "unconnected-(SV91-Pad12)") (class "Default")
      (node (ref "SV91") (pin "12") (pinfunction "12_12") (pintype "passive"))
    )
    (net (code "2973") (name "unconnected-(SV91-Pad13)") (class "Default")
      (node (ref "SV91") (pin "13") (pinfunction "13_13") (pintype "passive"))
    )
    (net (code "2974") (name "unconnected-(SV91-Pad14)") (class "Default")
      (node (ref "SV91") (pin "14") (pinfunction "14_14") (pintype "passive"))
    )
    (net (code "2975") (name "unconnected-(SV91-Pad15)") (class "Default")
      (node (ref "SV91") (pin "15") (pinfunction "15_15") (pintype "passive"))
    )
    (net (code "2976") (name "unconnected-(SV91-Pad16)") (class "Default")
      (node (ref "SV91") (pin "16") (pinfunction "16_16") (pintype "passive"))
    )
    (net (code "2977") (name "unconnected-(SV91-Pad17)") (class "Default")
      (node (ref "SV91") (pin "17") (pinfunction "17_17") (pintype "passive"))
    )
    (net (code "2978") (name "unconnected-(SV91-Pad18)") (class "Default")
      (node (ref "SV91") (pin "18") (pinfunction "18_18") (pintype "passive"))
    )
    (net (code "2979") (name "unconnected-(SV91-Pad19)") (class "Default")
      (node (ref "SV91") (pin "19") (pinfunction "19_19") (pintype "passive"))
    )
    (net (code "2980") (name "unconnected-(SV91-Pad20)") (class "Default")
      (node (ref "SV91") (pin "20") (pinfunction "20_20") (pintype "passive"))
    )
    (net (code "2981") (name "unconnected-(SV91-Pad21)") (class "Default")
      (node (ref "SV91") (pin "21") (pinfunction "21_21") (pintype "passive"))
    )
    (net (code "2982") (name "unconnected-(SV91-Pad22)") (class "Default")
      (node (ref "SV91") (pin "22") (pinfunction "22_22") (pintype "passive"))
    )
    (net (code "2983") (name "unconnected-(SV91-Pad23)") (class "Default")
      (node (ref "SV91") (pin "23") (pinfunction "23_23") (pintype "passive"))
    )
    (net (code "2984") (name "unconnected-(SV91-Pad24)") (class "Default")
      (node (ref "SV91") (pin "24") (pinfunction "24_24") (pintype "passive"))
    )
    (net (code "2985") (name "unconnected-(SV91-Pad25)") (class "Default")
      (node (ref "SV91") (pin "25") (pinfunction "25_25") (pintype "passive"))
    )
    (net (code "2986") (name "unconnected-(SV91-Pad26)") (class "Default")
      (node (ref "SV91") (pin "26") (pinfunction "26_26") (pintype "passive"))
    )
    (net (code "2987") (name "unconnected-(SV91-Pad27)") (class "Default")
      (node (ref "SV91") (pin "27") (pinfunction "27_27") (pintype "passive"))
    )
    (net (code "2988") (name "unconnected-(SV91-Pad28)") (class "Default")
      (node (ref "SV91") (pin "28") (pinfunction "28_28") (pintype "passive"))
    )
    (net (code "2989") (name "unconnected-(SV91-Pad29)") (class "Default")
      (node (ref "SV91") (pin "29") (pinfunction "29_29") (pintype "passive"))
    )
    (net (code "2990") (name "unconnected-(SV91-Pad30)") (class "Default")
      (node (ref "SV91") (pin "30") (pinfunction "30_30") (pintype "passive"))
    )
    (net (code "2991") (name "unconnected-(SV91-Pad31)") (class "Default")
      (node (ref "SV91") (pin "31") (pinfunction "31_31") (pintype "passive"))
    )
    (net (code "2992") (name "unconnected-(SV91-Pad32)") (class "Default")
      (node (ref "SV91") (pin "32") (pinfunction "32_32") (pintype "passive"))
    )
    (net (code "2993") (name "unconnected-(SV91-Pad33)") (class "Default")
      (node (ref "SV91") (pin "33") (pinfunction "33_33") (pintype "passive"))
    )
    (net (code "2994") (name "unconnected-(SV91-Pad34)") (class "Default")
      (node (ref "SV91") (pin "34") (pinfunction "34_34") (pintype "passive"))
    )
    (net (code "2995") (name "unconnected-(SV91-Pad35)") (class "Default")
      (node (ref "SV91") (pin "35") (pinfunction "35_35") (pintype "passive"))
    )
    (net (code "2996") (name "unconnected-(SV91-Pad36)") (class "Default")
      (node (ref "SV91") (pin "36") (pinfunction "36_36") (pintype "passive"))
    )
    (net (code "2997") (name "unconnected-(SV92-Pad1)") (class "Default")
      (node (ref "SV92") (pin "1") (pinfunction "1_1") (pintype "passive"))
    )
    (net (code "2998") (name "unconnected-(SV92-Pad2)") (class "Default")
      (node (ref "SV92") (pin "2") (pinfunction "2_2") (pintype "passive"))
    )
    (net (code "2999") (name "unconnected-(SV92-Pad3)") (class "Default")
      (node (ref "SV92") (pin "3") (pinfunction "3_3") (pintype "passive"))
    )
    (net (code "3000") (name "unconnected-(SV92-Pad4)") (class "Default")
      (node (ref "SV92") (pin "4") (pinfunction "4_4") (pintype "passive"))
    )
    (net (code "3001") (name "unconnected-(SV92-Pad5)") (class "Default")
      (node (ref "SV92") (pin "5") (pinfunction "5_5") (pintype "passive"))
    )
    (net (code "3002") (name "unconnected-(SV92-Pad6)") (class "Default")
      (node (ref "SV92") (pin "6") (pinfunction "6_6") (pintype "passive"))
    )
    (net (code "3003") (name "unconnected-(SV92-Pad7)") (class "Default")
      (node (ref "SV92") (pin "7") (pinfunction "7_7") (pintype "passive"))
    )
    (net (code "3004") (name "unconnected-(SV92-Pad8)") (class "Default")
      (node (ref "SV92") (pin "8") (pinfunction "8_8") (pintype "passive"))
    )
    (net (code "3005") (name "unconnected-(SV92-Pad9)") (class "Default")
      (node (ref "SV92") (pin "9") (pinfunction "9_9") (pintype "passive"))
    )
    (net (code "3006") (name "unconnected-(SV92-Pad10)") (class "Default")
      (node (ref "SV92") (pin "10") (pinfunction "10_10") (pintype "passive"))
    )
    (net (code "3007") (name "unconnected-(SV92-Pad11)") (class "Default")
      (node (ref "SV92") (pin "11") (pinfunction "11_11") (pintype "passive"))
    )
    (net (code "3008") (name "unconnected-(SV92-Pad12)") (class "Default")
      (node (ref "SV92") (pin "12") (pinfunction "12_12") (pintype "passive"))
    )
    (net (code "3009") (name "unconnected-(SV92-Pad13)") (class "Default")
      (node (ref "SV92") (pin "13") (pinfunction "13_13") (pintype "passive"))
    )
    (net (code "3010") (name "unconnected-(SV92-Pad14)") (class "Default")
      (node (ref "SV92") (pin "14") (pinfunction "14_14") (pintype "passive"))
    )
    (net (code "3011") (name "unconnected-(SV92-Pad15)") (class "Default")
      (node (ref "SV92") (pin "15") (pinfunction "15_15") (pintype "passive"))
    )
    (net (code "3012") (name "unconnected-(SV92-Pad16)") (class "Default")
      (node (ref "SV92") (pin "16") (pinfunction "16_16") (pintype "passive"))
    )
    (net (code "3013") (name "unconnected-(SV92-Pad17)") (class "Default")
      (node (ref "SV92") (pin "17") (pinfunction "17_17") (pintype "passive"))
    )
    (net (code "3014") (name "unconnected-(SV92-Pad18)") (class "Default")
      (node (ref "SV92") (pin "18") (pinfunction "18_18") (pintype "passive"))
    )
    (net (code "3015") (name "unconnected-(SV92-Pad19)") (class "Default")
      (node (ref "SV92") (pin "19") (pinfunction "19_19") (pintype "passive"))
    )
    (net (code "3016") (name "unconnected-(SV92-Pad20)") (class "Default")
      (node (ref "SV92") (pin "20") (pinfunction "20_20") (pintype "passive"))
    )
    (net (code "3017") (name "unconnected-(SV92-Pad21)") (class "Default")
      (node (ref "SV92") (pin "21") (pinfunction "21_21") (pintype "passive"))
    )
    (net (code "3018") (name "unconnected-(SV92-Pad22)") (class "Default")
      (node (ref "SV92") (pin "22") (pinfunction "22_22") (pintype "passive"))
    )
    (net (code "3019") (name "unconnected-(SV92-Pad23)") (class "Default")
      (node (ref "SV92") (pin "23") (pinfunction "23_23") (pintype "passive"))
    )
    (net (code "3020") (name "unconnected-(SV92-Pad24)") (class "Default")
      (node (ref "SV92") (pin "24") (pinfunction "24_24") (pintype "passive"))
    )
    (net (code "3021") (name "unconnected-(SV92-Pad25)") (class "Default")
      (node (ref "SV92") (pin "25") (pinfunction "25_25") (pintype "passive"))
    )
    (net (code "3022") (name "unconnected-(SV92-Pad26)") (class "Default")
      (node (ref "SV92") (pin "26") (pinfunction "26_26") (pintype "passive"))
    )
    (net (code "3023") (name "unconnected-(SV92-Pad27)") (class "Default")
      (node (ref "SV92") (pin "27") (pinfunction "27_27") (pintype "passive"))
    )
    (net (code "3024") (name "unconnected-(SV92-Pad28)") (class "Default")
      (node (ref "SV92") (pin "28") (pinfunction "28_28") (pintype "passive"))
    )
    (net (code "3025") (name "unconnected-(SV92-Pad29)") (class "Default")
      (node (ref "SV92") (pin "29") (pinfunction "29_29") (pintype "passive"))
    )
    (net (code "3026") (name "unconnected-(SV92-Pad30)") (class "Default")
      (node (ref "SV92") (pin "30") (pinfunction "30_30") (pintype "passive"))
    )
    (net (code "3027") (name "unconnected-(SV92-Pad31)") (class "Default")
      (node (ref "SV92") (pin "31") (pinfunction "31_31") (pintype "passive"))
    )
    (net (code "3028") (name "unconnected-(SV92-Pad32)") (class "Default")
      (node (ref "SV92") (pin "32") (pinfunction "32_32") (pintype "passive"))
    )
    (net (code "3029") (name "unconnected-(SV92-Pad33)") (class "Default")
      (node (ref "SV92") (pin "33") (pinfunction "33_33") (pintype "passive"))
    )
    (net (code "3030") (name "unconnected-(SV92-Pad34)") (class "Default")
      (node (ref "SV92") (pin "34") (pinfunction "34_34") (pintype "passive"))
    )
    (net (code "3031") (name "unconnected-(SV92-Pad35)") (class "Default")
      (node (ref "SV92") (pin "35") (pinfunction "35_35") (pintype "passive"))
    )
    (net (code "3032") (name "unconnected-(SV92-Pad36)") (class "Default")
      (node (ref "SV92") (pin "36") (pinfunction "36_36") (pintype "passive"))
    )
    (net (code "3033") (name "unconnected-(SV93-Pad1)") (class "Default")
      (node (ref "SV93") (pin "1") (pinfunction "1_1") (pintype "passive"))
    )
    (net (code "3034") (name "unconnected-(SV93-Pad2)") (class "Default")
      (node (ref "SV93") (pin "2") (pinfunction "2_2") (pintype "passive"))
    )
    (net (code "3035") (name "unconnected-(SV93-Pad3)") (class "Default")
      (node (ref "SV93") (pin "3") (pinfunction "3_3") (pintype "passive"))
    )
    (net (code "3036") (name "unconnected-(SV93-Pad4)") (class "Default")
      (node (ref "SV93") (pin "4") (pinfunction "4_4") (pintype "passive"))
    )
    (net (code "3037") (name "unconnected-(SV93-Pad5)") (class "Default")
      (node (ref "SV93") (pin "5") (pinfunction "5_5") (pintype "passive"))
    )
    (net (code "3038") (name "unconnected-(SV93-Pad6)") (class "Default")
      (node (ref "SV93") (pin "6") (pinfunction "6_6") (pintype "passive"))
    )
    (net (code "3039") (name "unconnected-(SV93-Pad7)") (class "Default")
      (node (ref "SV93") (pin "7") (pinfunction "7_7") (pintype "passive"))
    )
    (net (code "3040") (name "unconnected-(SV93-Pad8)") (class "Default")
      (node (ref "SV93") (pin "8") (pinfunction "8_8") (pintype "passive"))
    )
    (net (code "3041") (name "unconnected-(SV93-Pad9)") (class "Default")
      (node (ref "SV93") (pin "9") (pinfunction "9_9") (pintype "passive"))
    )
    (net (code "3042") (name "unconnected-(SV93-Pad10)") (class "Default")
      (node (ref "SV93") (pin "10") (pinfunction "10_10") (pintype "passive"))
    )
    (net (code "3043") (name "unconnected-(SV93-Pad11)") (class "Default")
      (node (ref "SV93") (pin "11") (pinfunction "11_11") (pintype "passive"))
    )
    (net (code "3044") (name "unconnected-(SV93-Pad12)") (class "Default")
      (node (ref "SV93") (pin "12") (pinfunction "12_12") (pintype "passive"))
    )
    (net (code "3045") (name "unconnected-(SV93-Pad13)") (class "Default")
      (node (ref "SV93") (pin "13") (pinfunction "13_13") (pintype "passive"))
    )
    (net (code "3046") (name "unconnected-(SV93-Pad14)") (class "Default")
      (node (ref "SV93") (pin "14") (pinfunction "14_14") (pintype "passive"))
    )
    (net (code "3047") (name "unconnected-(SV93-Pad15)") (class "Default")
      (node (ref "SV93") (pin "15") (pinfunction "15_15") (pintype "passive"))
    )
    (net (code "3048") (name "unconnected-(SV93-Pad16)") (class "Default")
      (node (ref "SV93") (pin "16") (pinfunction "16_16") (pintype "passive"))
    )
    (net (code "3049") (name "unconnected-(SV93-Pad17)") (class "Default")
      (node (ref "SV93") (pin "17") (pinfunction "17_17") (pintype "passive"))
    )
    (net (code "3050") (name "unconnected-(SV93-Pad18)") (class "Default")
      (node (ref "SV93") (pin "18") (pinfunction "18_18") (pintype "passive"))
    )
    (net (code "3051") (name "unconnected-(SV93-Pad19)") (class "Default")
      (node (ref "SV93") (pin "19") (pinfunction "19_19") (pintype "passive"))
    )
    (net (code "3052") (name "unconnected-(SV93-Pad20)") (class "Default")
      (node (ref "SV93") (pin "20") (pinfunction "20_20") (pintype "passive"))
    )
    (net (code "3053") (name "unconnected-(SV93-Pad21)") (class "Default")
      (node (ref "SV93") (pin "21") (pinfunction "21_21") (pintype "passive"))
    )
    (net (code "3054") (name "unconnected-(SV93-Pad22)") (class "Default")
      (node (ref "SV93") (pin "22") (pinfunction "22_22") (pintype "passive"))
    )
    (net (code "3055") (name "unconnected-(SV93-Pad23)") (class "Default")
      (node (ref "SV93") (pin "23") (pinfunction "23_23") (pintype "passive"))
    )
    (net (code "3056") (name "unconnected-(SV93-Pad24)") (class "Default")
      (node (ref "SV93") (pin "24") (pinfunction "24_24") (pintype "passive"))
    )
    (net (code "3057") (name "unconnected-(SV93-Pad25)") (class "Default")
      (node (ref "SV93") (pin "25") (pinfunction "25_25") (pintype "passive"))
    )
    (net (code "3058") (name "unconnected-(SV93-Pad26)") (class "Default")
      (node (ref "SV93") (pin "26") (pinfunction "26_26") (pintype "passive"))
    )
    (net (code "3059") (name "unconnected-(SV93-Pad27)") (class "Default")
      (node (ref "SV93") (pin "27") (pinfunction "27_27") (pintype "passive"))
    )
    (net (code "3060") (name "unconnected-(SV93-Pad28)") (class "Default")
      (node (ref "SV93") (pin "28") (pinfunction "28_28") (pintype "passive"))
    )
    (net (code "3061") (name "unconnected-(SV93-Pad29)") (class "Default")
      (node (ref "SV93") (pin "29") (pinfunction "29_29") (pintype "passive"))
    )
    (net (code "3062") (name "unconnected-(SV93-Pad30)") (class "Default")
      (node (ref "SV93") (pin "30") (pinfunction "30_30") (pintype "passive"))
    )
    (net (code "3063") (name "unconnected-(SV93-Pad31)") (class "Default")
      (node (ref "SV93") (pin "31") (pinfunction "31_31") (pintype "passive"))
    )
    (net (code "3064") (name "unconnected-(SV93-Pad32)") (class "Default")
      (node (ref "SV93") (pin "32") (pinfunction "32_32") (pintype "passive"))
    )
    (net (code "3065") (name "unconnected-(SV93-Pad33)") (class "Default")
      (node (ref "SV93") (pin "33") (pinfunction "33_33") (pintype "passive"))
    )
    (net (code "3066") (name "unconnected-(SV93-Pad34)") (class "Default")
      (node (ref "SV93") (pin "34") (pinfunction "34_34") (pintype "passive"))
    )
    (net (code "3067") (name "unconnected-(SV93-Pad35)") (class "Default")
      (node (ref "SV93") (pin "35") (pinfunction "35_35") (pintype "passive"))
    )
    (net (code "3068") (name "unconnected-(SV93-Pad36)") (class "Default")
      (node (ref "SV93") (pin "36") (pinfunction "36_36") (pintype "passive"))
    )
    (net (code "3069") (name "unconnected-(SV94-Pad1)") (class "Default")
      (node (ref "SV94") (pin "1") (pinfunction "1_1") (pintype "passive"))
    )
    (net (code "3070") (name "unconnected-(SV94-Pad2)") (class "Default")
      (node (ref "SV94") (pin "2") (pinfunction "2_2") (pintype "passive"))
    )
    (net (code "3071") (name "unconnected-(SV94-Pad3)") (class "Default")
      (node (ref "SV94") (pin "3") (pinfunction "3_3") (pintype "passive"))
    )
    (net (code "3072") (name "unconnected-(SV94-Pad4)") (class "Default")
      (node (ref "SV94") (pin "4") (pinfunction "4_4") (pintype "passive"))
    )
    (net (code "3073") (name "unconnected-(SV94-Pad5)") (class "Default")
      (node (ref "SV94") (pin "5") (pinfunction "5_5") (pintype "passive"))
    )
    (net (code "3074") (name "unconnected-(SV94-Pad6)") (class "Default")
      (node (ref "SV94") (pin "6") (pinfunction "6_6") (pintype "passive"))
    )
    (net (code "3075") (name "unconnected-(SV94-Pad7)") (class "Default")
      (node (ref "SV94") (pin "7") (pinfunction "7_7") (pintype "passive"))
    )
    (net (code "3076") (name "unconnected-(SV94-Pad8)") (class "Default")
      (node (ref "SV94") (pin "8") (pinfunction "8_8") (pintype "passive"))
    )
    (net (code "3077") (name "unconnected-(SV94-Pad9)") (class "Default")
      (node (ref "SV94") (pin "9") (pinfunction "9_9") (pintype "passive"))
    )
    (net (code "3078") (name "unconnected-(SV94-Pad10)") (class "Default")
      (node (ref "SV94") (pin "10") (pinfunction "10_10") (pintype "passive"))
    )
    (net (code "3079") (name "unconnected-(SV94-Pad11)") (class "Default")
      (node (ref "SV94") (pin "11") (pinfunction "11_11") (pintype "passive"))
    )
    (net (code "3080") (name "unconnected-(SV94-Pad12)") (class "Default")
      (node (ref "SV94") (pin "12") (pinfunction "12_12") (pintype "passive"))
    )
    (net (code "3081") (name "unconnected-(SV94-Pad13)") (class "Default")
      (node (ref "SV94") (pin "13") (pinfunction "13_13") (pintype "passive"))
    )
    (net (code "3082") (name "unconnected-(SV94-Pad14)") (class "Default")
      (node (ref "SV94") (pin "14") (pinfunction "14_14") (pintype "passive"))
    )
    (net (code "3083") (name "unconnected-(SV94-Pad15)") (class "Default")
      (node (ref "SV94") (pin "15") (pinfunction "15_15") (pintype "passive"))
    )
    (net (code "3084") (name "unconnected-(SV94-Pad16)") (class "Default")
      (node (ref "SV94") (pin "16") (pinfunction "16_16") (pintype "passive"))
    )
    (net (code "3085") (name "unconnected-(SV94-Pad17)") (class "Default")
      (node (ref "SV94") (pin "17") (pinfunction "17_17") (pintype "passive"))
    )
    (net (code "3086") (name "unconnected-(SV94-Pad18)") (class "Default")
      (node (ref "SV94") (pin "18") (pinfunction "18_18") (pintype "passive"))
    )
    (net (code "3087") (name "unconnected-(SV94-Pad19)") (class "Default")
      (node (ref "SV94") (pin "19") (pinfunction "19_19") (pintype "passive"))
    )
    (net (code "3088") (name "unconnected-(SV94-Pad20)") (class "Default")
      (node (ref "SV94") (pin "20") (pinfunction "20_20") (pintype "passive"))
    )
    (net (code "3089") (name "unconnected-(SV94-Pad21)") (class "Default")
      (node (ref "SV94") (pin "21") (pinfunction "21_21") (pintype "passive"))
    )
    (net (code "3090") (name "unconnected-(SV94-Pad22)") (class "Default")
      (node (ref "SV94") (pin "22") (pinfunction "22_22") (pintype "passive"))
    )
    (net (code "3091") (name "unconnected-(SV94-Pad23)") (class "Default")
      (node (ref "SV94") (pin "23") (pinfunction "23_23") (pintype "passive"))
    )
    (net (code "3092") (name "unconnected-(SV94-Pad24)") (class "Default")
      (node (ref "SV94") (pin "24") (pinfunction "24_24") (pintype "passive"))
    )
    (net (code "3093") (name "unconnected-(SV94-Pad25)") (class "Default")
      (node (ref "SV94") (pin "25") (pinfunction "25_25") (pintype "passive"))
    )
    (net (code "3094") (name "unconnected-(SV94-Pad26)") (class "Default")
      (node (ref "SV94") (pin "26") (pinfunction "26_26") (pintype "passive"))
    )
    (net (code "3095") (name "unconnected-(SV94-Pad27)") (class "Default")
      (node (ref "SV94") (pin "27") (pinfunction "27_27") (pintype "passive"))
    )
    (net (code "3096") (name "unconnected-(SV94-Pad28)") (class "Default")
      (node (ref "SV94") (pin "28") (pinfunction "28_28") (pintype "passive"))
    )
    (net (code "3097") (name "unconnected-(SV94-Pad29)") (class "Default")
      (node (ref "SV94") (pin "29") (pinfunction "29_29") (pintype "passive"))
    )
    (net (code "3098") (name "unconnected-(SV94-Pad30)") (class "Default")
      (node (ref "SV94") (pin "30") (pinfunction "30_30") (pintype "passive"))
    )
    (net (code "3099") (name "unconnected-(SV94-Pad31)") (class "Default")
      (node (ref "SV94") (pin "31") (pinfunction "31_31") (pintype "passive"))
    )
    (net (code "3100") (name "unconnected-(SV94-Pad32)") (class "Default")
      (node (ref "SV94") (pin "32") (pinfunction "32_32") (pintype "passive"))
    )
    (net (code "3101") (name "unconnected-(SV94-Pad33)") (class "Default")
      (node (ref "SV94") (pin "33") (pinfunction "33_33") (pintype "passive"))
    )
    (net (code "3102") (name "unconnected-(SV94-Pad34)") (class "Default")
      (node (ref "SV94") (pin "34") (pinfunction "34_34") (pintype "passive"))
    )
    (net (code "3103") (name "unconnected-(SV94-Pad35)") (class "Default")
      (node (ref "SV94") (pin "35") (pinfunction "35_35") (pintype "passive"))
    )
    (net (code "3104") (name "unconnected-(SV94-Pad36)") (class "Default")
      (node (ref "SV94") (pin "36") (pinfunction "36_36") (pintype "passive"))
    )
    (net (code "3105") (name "unconnected-(SV94-Pad37)") (class "Default")
      (node (ref "SV94") (pin "37") (pinfunction "37_37") (pintype "passive"))
    )
    (net (code "3106") (name "unconnected-(SV94-Pad38)") (class "Default")
      (node (ref "SV94") (pin "38") (pinfunction "38_38") (pintype "passive"))
    )
    (net (code "3107") (name "unconnected-(SV94-Pad39)") (class "Default")
      (node (ref "SV94") (pin "39") (pinfunction "39_39") (pintype "passive"))
    )
    (net (code "3108") (name "unconnected-(SV94-Pad40)") (class "Default")
      (node (ref "SV94") (pin "40") (pinfunction "40_40") (pintype "passive"))
    )
    (net (code "3109") (name "unconnected-(SV95-Pad1)") (class "Default")
      (node (ref "SV95") (pin "1") (pinfunction "1_1") (pintype "passive"))
    )
    (net (code "3110") (name "unconnected-(SV95-Pad2)") (class "Default")
      (node (ref "SV95") (pin "2") (pinfunction "2_2") (pintype "passive"))
    )
    (net (code "3111") (name "unconnected-(SV95-Pad3)") (class "Default")
      (node (ref "SV95") (pin "3") (pinfunction "3_3") (pintype "passive"))
    )
    (net (code "3112") (name "unconnected-(SV95-Pad4)") (class "Default")
      (node (ref "SV95") (pin "4") (pinfunction "4_4") (pintype "passive"))
    )
    (net (code "3113") (name "unconnected-(SV95-Pad5)") (class "Default")
      (node (ref "SV95") (pin "5") (pinfunction "5_5") (pintype "passive"))
    )
    (net (code "3114") (name "unconnected-(SV95-Pad6)") (class "Default")
      (node (ref "SV95") (pin "6") (pinfunction "6_6") (pintype "passive"))
    )
    (net (code "3115") (name "unconnected-(SV95-Pad7)") (class "Default")
      (node (ref "SV95") (pin "7") (pinfunction "7_7") (pintype "passive"))
    )
    (net (code "3116") (name "unconnected-(SV95-Pad8)") (class "Default")
      (node (ref "SV95") (pin "8") (pinfunction "8_8") (pintype "passive"))
    )
    (net (code "3117") (name "unconnected-(SV95-Pad9)") (class "Default")
      (node (ref "SV95") (pin "9") (pinfunction "9_9") (pintype "passive"))
    )
    (net (code "3118") (name "unconnected-(SV95-Pad10)") (class "Default")
      (node (ref "SV95") (pin "10") (pinfunction "10_10") (pintype "passive"))
    )
    (net (code "3119") (name "unconnected-(SV95-Pad11)") (class "Default")
      (node (ref "SV95") (pin "11") (pinfunction "11_11") (pintype "passive"))
    )
    (net (code "3120") (name "unconnected-(SV95-Pad12)") (class "Default")
      (node (ref "SV95") (pin "12") (pinfunction "12_12") (pintype "passive"))
    )
    (net (code "3121") (name "unconnected-(SV95-Pad13)") (class "Default")
      (node (ref "SV95") (pin "13") (pinfunction "13_13") (pintype "passive"))
    )
    (net (code "3122") (name "unconnected-(SV95-Pad14)") (class "Default")
      (node (ref "SV95") (pin "14") (pinfunction "14_14") (pintype "passive"))
    )
    (net (code "3123") (name "unconnected-(SV95-Pad15)") (class "Default")
      (node (ref "SV95") (pin "15") (pinfunction "15_15") (pintype "passive"))
    )
    (net (code "3124") (name "unconnected-(SV95-Pad16)") (class "Default")
      (node (ref "SV95") (pin "16") (pinfunction "16_16") (pintype "passive"))
    )
    (net (code "3125") (name "unconnected-(SV95-Pad17)") (class "Default")
      (node (ref "SV95") (pin "17") (pinfunction "17_17") (pintype "passive"))
    )
    (net (code "3126") (name "unconnected-(SV95-Pad18)") (class "Default")
      (node (ref "SV95") (pin "18") (pinfunction "18_18") (pintype "passive"))
    )
    (net (code "3127") (name "unconnected-(SV95-Pad19)") (class "Default")
      (node (ref "SV95") (pin "19") (pinfunction "19_19") (pintype "passive"))
    )
    (net (code "3128") (name "unconnected-(SV95-Pad20)") (class "Default")
      (node (ref "SV95") (pin "20") (pinfunction "20_20") (pintype "passive"))
    )
    (net (code "3129") (name "unconnected-(SV95-Pad21)") (class "Default")
      (node (ref "SV95") (pin "21") (pinfunction "21_21") (pintype "passive"))
    )
    (net (code "3130") (name "unconnected-(SV95-Pad22)") (class "Default")
      (node (ref "SV95") (pin "22") (pinfunction "22_22") (pintype "passive"))
    )
    (net (code "3131") (name "unconnected-(SV95-Pad23)") (class "Default")
      (node (ref "SV95") (pin "23") (pinfunction "23_23") (pintype "passive"))
    )
    (net (code "3132") (name "unconnected-(SV95-Pad24)") (class "Default")
      (node (ref "SV95") (pin "24") (pinfunction "24_24") (pintype "passive"))
    )
    (net (code "3133") (name "unconnected-(SV95-Pad25)") (class "Default")
      (node (ref "SV95") (pin "25") (pinfunction "25_25") (pintype "passive"))
    )
    (net (code "3134") (name "unconnected-(SV95-Pad26)") (class "Default")
      (node (ref "SV95") (pin "26") (pinfunction "26_26") (pintype "passive"))
    )
    (net (code "3135") (name "unconnected-(SV95-Pad27)") (class "Default")
      (node (ref "SV95") (pin "27") (pinfunction "27_27") (pintype "passive"))
    )
    (net (code "3136") (name "unconnected-(SV95-Pad28)") (class "Default")
      (node (ref "SV95") (pin "28") (pinfunction "28_28") (pintype "passive"))
    )
    (net (code "3137") (name "unconnected-(SV95-Pad29)") (class "Default")
      (node (ref "SV95") (pin "29") (pinfunction "29_29") (pintype "passive"))
    )
    (net (code "3138") (name "unconnected-(SV95-Pad30)") (class "Default")
      (node (ref "SV95") (pin "30") (pinfunction "30_30") (pintype "passive"))
    )
    (net (code "3139") (name "unconnected-(SV95-Pad31)") (class "Default")
      (node (ref "SV95") (pin "31") (pinfunction "31_31") (pintype "passive"))
    )
    (net (code "3140") (name "unconnected-(SV95-Pad32)") (class "Default")
      (node (ref "SV95") (pin "32") (pinfunction "32_32") (pintype "passive"))
    )
    (net (code "3141") (name "unconnected-(SV95-Pad33)") (class "Default")
      (node (ref "SV95") (pin "33") (pinfunction "33_33") (pintype "passive"))
    )
    (net (code "3142") (name "unconnected-(SV95-Pad34)") (class "Default")
      (node (ref "SV95") (pin "34") (pinfunction "34_34") (pintype "passive"))
    )
    (net (code "3143") (name "unconnected-(SV95-Pad35)") (class "Default")
      (node (ref "SV95") (pin "35") (pinfunction "35_35") (pintype "passive"))
    )
    (net (code "3144") (name "unconnected-(SV95-Pad36)") (class "Default")
      (node (ref "SV95") (pin "36") (pinfunction "36_36") (pintype "passive"))
    )
    (net (code "3145") (name "unconnected-(SV95-Pad37)") (class "Default")
      (node (ref "SV95") (pin "37") (pinfunction "37_37") (pintype "passive"))
    )
    (net (code "3146") (name "unconnected-(SV95-Pad38)") (class "Default")
      (node (ref "SV95") (pin "38") (pinfunction "38_38") (pintype "passive"))
    )
    (net (code "3147") (name "unconnected-(SV95-Pad39)") (class "Default")
      (node (ref "SV95") (pin "39") (pinfunction "39_39") (pintype "passive"))
    )
    (net (code "3148") (name "unconnected-(SV95-Pad40)") (class "Default")
      (node (ref "SV95") (pin "40") (pinfunction "40_40") (pintype "passive"))
    )
    (net (code "3149") (name "unconnected-(SV96-Pad1)") (class "Default")
      (node (ref "SV96") (pin "1") (pinfunction "1_1") (pintype "passive"))
    )
    (net (code "3150") (name "unconnected-(SV96-Pad2)") (class "Default")
      (node (ref "SV96") (pin "2") (pinfunction "2_2") (pintype "passive"))
    )
    (net (code "3151") (name "unconnected-(SV96-Pad3)") (class "Default")
      (node (ref "SV96") (pin "3") (pinfunction "3_3") (pintype "passive"))
    )
    (net (code "3152") (name "unconnected-(SV96-Pad4)") (class "Default")
      (node (ref "SV96") (pin "4") (pinfunction "4_4") (pintype "passive"))
    )
    (net (code "3153") (name "unconnected-(SV96-Pad5)") (class "Default")
      (node (ref "SV96") (pin "5") (pinfunction "5_5") (pintype "passive"))
    )
    (net (code "3154") (name "unconnected-(SV96-Pad6)") (class "Default")
      (node (ref "SV96") (pin "6") (pinfunction "6_6") (pintype "passive"))
    )
    (net (code "3155") (name "unconnected-(SV96-Pad7)") (class "Default")
      (node (ref "SV96") (pin "7") (pinfunction "7_7") (pintype "passive"))
    )
    (net (code "3156") (name "unconnected-(SV96-Pad8)") (class "Default")
      (node (ref "SV96") (pin "8") (pinfunction "8_8") (pintype "passive"))
    )
    (net (code "3157") (name "unconnected-(SV96-Pad9)") (class "Default")
      (node (ref "SV96") (pin "9") (pinfunction "9_9") (pintype "passive"))
    )
    (net (code "3158") (name "unconnected-(SV96-Pad10)") (class "Default")
      (node (ref "SV96") (pin "10") (pinfunction "10_10") (pintype "passive"))
    )
    (net (code "3159") (name "unconnected-(SV96-Pad11)") (class "Default")
      (node (ref "SV96") (pin "11") (pinfunction "11_11") (pintype "passive"))
    )
    (net (code "3160") (name "unconnected-(SV96-Pad12)") (class "Default")
      (node (ref "SV96") (pin "12") (pinfunction "12_12") (pintype "passive"))
    )
    (net (code "3161") (name "unconnected-(SV96-Pad13)") (class "Default")
      (node (ref "SV96") (pin "13") (pinfunction "13_13") (pintype "passive"))
    )
    (net (code "3162") (name "unconnected-(SV96-Pad14)") (class "Default")
      (node (ref "SV96") (pin "14") (pinfunction "14_14") (pintype "passive"))
    )
    (net (code "3163") (name "unconnected-(SV96-Pad15)") (class "Default")
      (node (ref "SV96") (pin "15") (pinfunction "15_15") (pintype "passive"))
    )
    (net (code "3164") (name "unconnected-(SV96-Pad16)") (class "Default")
      (node (ref "SV96") (pin "16") (pinfunction "16_16") (pintype "passive"))
    )
    (net (code "3165") (name "unconnected-(SV96-Pad17)") (class "Default")
      (node (ref "SV96") (pin "17") (pinfunction "17_17") (pintype "passive"))
    )
    (net (code "3166") (name "unconnected-(SV96-Pad18)") (class "Default")
      (node (ref "SV96") (pin "18") (pinfunction "18_18") (pintype "passive"))
    )
    (net (code "3167") (name "unconnected-(SV96-Pad19)") (class "Default")
      (node (ref "SV96") (pin "19") (pinfunction "19_19") (pintype "passive"))
    )
    (net (code "3168") (name "unconnected-(SV96-Pad20)") (class "Default")
      (node (ref "SV96") (pin "20") (pinfunction "20_20") (pintype "passive"))
    )
    (net (code "3169") (name "unconnected-(SV96-Pad21)") (class "Default")
      (node (ref "SV96") (pin "21") (pinfunction "21_21") (pintype "passive"))
    )
    (net (code "3170") (name "unconnected-(SV96-Pad22)") (class "Default")
      (node (ref "SV96") (pin "22") (pinfunction "22_22") (pintype "passive"))
    )
    (net (code "3171") (name "unconnected-(SV96-Pad23)") (class "Default")
      (node (ref "SV96") (pin "23") (pinfunction "23_23") (pintype "passive"))
    )
    (net (code "3172") (name "unconnected-(SV96-Pad24)") (class "Default")
      (node (ref "SV96") (pin "24") (pinfunction "24_24") (pintype "passive"))
    )
    (net (code "3173") (name "unconnected-(SV96-Pad25)") (class "Default")
      (node (ref "SV96") (pin "25") (pinfunction "25_25") (pintype "passive"))
    )
    (net (code "3174") (name "unconnected-(SV96-Pad26)") (class "Default")
      (node (ref "SV96") (pin "26") (pinfunction "26_26") (pintype "passive"))
    )
    (net (code "3175") (name "unconnected-(SV96-Pad27)") (class "Default")
      (node (ref "SV96") (pin "27") (pinfunction "27_27") (pintype "passive"))
    )
    (net (code "3176") (name "unconnected-(SV96-Pad28)") (class "Default")
      (node (ref "SV96") (pin "28") (pinfunction "28_28") (pintype "passive"))
    )
    (net (code "3177") (name "unconnected-(SV96-Pad29)") (class "Default")
      (node (ref "SV96") (pin "29") (pinfunction "29_29") (pintype "passive"))
    )
    (net (code "3178") (name "unconnected-(SV96-Pad30)") (class "Default")
      (node (ref "SV96") (pin "30") (pinfunction "30_30") (pintype "passive"))
    )
    (net (code "3179") (name "unconnected-(SV96-Pad31)") (class "Default")
      (node (ref "SV96") (pin "31") (pinfunction "31_31") (pintype "passive"))
    )
    (net (code "3180") (name "unconnected-(SV96-Pad32)") (class "Default")
      (node (ref "SV96") (pin "32") (pinfunction "32_32") (pintype "passive"))
    )
    (net (code "3181") (name "unconnected-(SV96-Pad33)") (class "Default")
      (node (ref "SV96") (pin "33") (pinfunction "33_33") (pintype "passive"))
    )
    (net (code "3182") (name "unconnected-(SV96-Pad34)") (class "Default")
      (node (ref "SV96") (pin "34") (pinfunction "34_34") (pintype "passive"))
    )
    (net (code "3183") (name "unconnected-(SV96-Pad35)") (class "Default")
      (node (ref "SV96") (pin "35") (pinfunction "35_35") (pintype "passive"))
    )
    (net (code "3184") (name "unconnected-(SV96-Pad36)") (class "Default")
      (node (ref "SV96") (pin "36") (pinfunction "36_36") (pintype "passive"))
    )
    (net (code "3185") (name "unconnected-(SV96-Pad37)") (class "Default")
      (node (ref "SV96") (pin "37") (pinfunction "37_37") (pintype "passive"))
    )
    (net (code "3186") (name "unconnected-(SV96-Pad38)") (class "Default")
      (node (ref "SV96") (pin "38") (pinfunction "38_38") (pintype "passive"))
    )
    (net (code "3187") (name "unconnected-(SV96-Pad39)") (class "Default")
      (node (ref "SV96") (pin "39") (pinfunction "39_39") (pintype "passive"))
    )
    (net (code "3188") (name "unconnected-(SV96-Pad40)") (class "Default")
      (node (ref "SV96") (pin "40") (pinfunction "40_40") (pintype "passive"))
    )
    (net (code "3189") (name "unconnected-(SV97-Pad1)") (class "Default")
      (node (ref "SV97") (pin "1") (pinfunction "1_1") (pintype "passive"))
    )
    (net (code "3190") (name "unconnected-(SV97-Pad2)") (class "Default")
      (node (ref "SV97") (pin "2") (pinfunction "2_2") (pintype "passive"))
    )
    (net (code "3191") (name "unconnected-(SV97-Pad3)") (class "Default")
      (node (ref "SV97") (pin "3") (pinfunction "3_3") (pintype "passive"))
    )
    (net (code "3192") (name "unconnected-(SV97-Pad4)") (class "Default")
      (node (ref "SV97") (pin "4") (pinfunction "4_4") (pintype "passive"))
    )
    (net (code "3193") (name "unconnected-(SV97-Pad5)") (class "Default")
      (node (ref "SV97") (pin "5") (pinfunction "5_5") (pintype "passive"))
    )
    (net (code "3194") (name "unconnected-(SV97-Pad6)") (class "Default")
      (node (ref "SV97") (pin "6") (pinfunction "6_6") (pintype "passive"))
    )
    (net (code "3195") (name "unconnected-(SV97-Pad7)") (class "Default")
      (node (ref "SV97") (pin "7") (pinfunction "7_7") (pintype "passive"))
    )
    (net (code "3196") (name "unconnected-(SV97-Pad8)") (class "Default")
      (node (ref "SV97") (pin "8") (pinfunction "8_8") (pintype "passive"))
    )
    (net (code "3197") (name "unconnected-(SV97-Pad9)") (class "Default")
      (node (ref "SV97") (pin "9") (pinfunction "9_9") (pintype "passive"))
    )
    (net (code "3198") (name "unconnected-(SV97-Pad10)") (class "Default")
      (node (ref "SV97") (pin "10") (pinfunction "10_10") (pintype "passive"))
    )
    (net (code "3199") (name "unconnected-(SV97-Pad11)") (class "Default")
      (node (ref "SV97") (pin "11") (pinfunction "11_11") (pintype "passive"))
    )
    (net (code "3200") (name "unconnected-(SV97-Pad12)") (class "Default")
      (node (ref "SV97") (pin "12") (pinfunction "12_12") (pintype "passive"))
    )
    (net (code "3201") (name "unconnected-(SV97-Pad13)") (class "Default")
      (node (ref "SV97") (pin "13") (pinfunction "13_13") (pintype "passive"))
    )
    (net (code "3202") (name "unconnected-(SV97-Pad14)") (class "Default")
      (node (ref "SV97") (pin "14") (pinfunction "14_14") (pintype "passive"))
    )
    (net (code "3203") (name "unconnected-(SV97-Pad15)") (class "Default")
      (node (ref "SV97") (pin "15") (pinfunction "15_15") (pintype "passive"))
    )
    (net (code "3204") (name "unconnected-(SV97-Pad16)") (class "Default")
      (node (ref "SV97") (pin "16") (pinfunction "16_16") (pintype "passive"))
    )
    (net (code "3205") (name "unconnected-(SV97-Pad17)") (class "Default")
      (node (ref "SV97") (pin "17") (pinfunction "17_17") (pintype "passive"))
    )
    (net (code "3206") (name "unconnected-(SV97-Pad18)") (class "Default")
      (node (ref "SV97") (pin "18") (pinfunction "18_18") (pintype "passive"))
    )
    (net (code "3207") (name "unconnected-(SV97-Pad19)") (class "Default")
      (node (ref "SV97") (pin "19") (pinfunction "19_19") (pintype "passive"))
    )
    (net (code "3208") (name "unconnected-(SV97-Pad20)") (class "Default")
      (node (ref "SV97") (pin "20") (pinfunction "20_20") (pintype "passive"))
    )
    (net (code "3209") (name "unconnected-(SV97-Pad21)") (class "Default")
      (node (ref "SV97") (pin "21") (pinfunction "21_21") (pintype "passive"))
    )
    (net (code "3210") (name "unconnected-(SV97-Pad22)") (class "Default")
      (node (ref "SV97") (pin "22") (pinfunction "22_22") (pintype "passive"))
    )
    (net (code "3211") (name "unconnected-(SV97-Pad23)") (class "Default")
      (node (ref "SV97") (pin "23") (pinfunction "23_23") (pintype "passive"))
    )
    (net (code "3212") (name "unconnected-(SV97-Pad24)") (class "Default")
      (node (ref "SV97") (pin "24") (pinfunction "24_24") (pintype "passive"))
    )
    (net (code "3213") (name "unconnected-(SV97-Pad25)") (class "Default")
      (node (ref "SV97") (pin "25") (pinfunction "25_25") (pintype "passive"))
    )
    (net (code "3214") (name "unconnected-(SV97-Pad26)") (class "Default")
      (node (ref "SV97") (pin "26") (pinfunction "26_26") (pintype "passive"))
    )
    (net (code "3215") (name "unconnected-(SV97-Pad27)") (class "Default")
      (node (ref "SV97") (pin "27") (pinfunction "27_27") (pintype "passive"))
    )
    (net (code "3216") (name "unconnected-(SV97-Pad28)") (class "Default")
      (node (ref "SV97") (pin "28") (pinfunction "28_28") (pintype "passive"))
    )
    (net (code "3217") (name "unconnected-(SV97-Pad29)") (class "Default")
      (node (ref "SV97") (pin "29") (pinfunction "29_29") (pintype "passive"))
    )
    (net (code "3218") (name "unconnected-(SV97-Pad30)") (class "Default")
      (node (ref "SV97") (pin "30") (pinfunction "30_30") (pintype "passive"))
    )
    (net (code "3219") (name "unconnected-(SV97-Pad31)") (class "Default")
      (node (ref "SV97") (pin "31") (pinfunction "31_31") (pintype "passive"))
    )
    (net (code "3220") (name "unconnected-(SV97-Pad32)") (class "Default")
      (node (ref "SV97") (pin "32") (pinfunction "32_32") (pintype "passive"))
    )
    (net (code "3221") (name "unconnected-(SV97-Pad33)") (class "Default")
      (node (ref "SV97") (pin "33") (pinfunction "33_33") (pintype "passive"))
    )
    (net (code "3222") (name "unconnected-(SV97-Pad34)") (class "Default")
      (node (ref "SV97") (pin "34") (pinfunction "34_34") (pintype "passive"))
    )
    (net (code "3223") (name "unconnected-(SV97-Pad35)") (class "Default")
      (node (ref "SV97") (pin "35") (pinfunction "35_35") (pintype "passive"))
    )
    (net (code "3224") (name "unconnected-(SV97-Pad36)") (class "Default")
      (node (ref "SV97") (pin "36") (pinfunction "36_36") (pintype "passive"))
    )
    (net (code "3225") (name "unconnected-(SV97-Pad37)") (class "Default")
      (node (ref "SV97") (pin "37") (pinfunction "37_37") (pintype "passive"))
    )
    (net (code "3226") (name "unconnected-(SV97-Pad38)") (class "Default")
      (node (ref "SV97") (pin "38") (pinfunction "38_38") (pintype "passive"))
    )
    (net (code "3227") (name "unconnected-(SV97-Pad39)") (class "Default")
      (node (ref "SV97") (pin "39") (pinfunction "39_39") (pintype "passive"))
    )
    (net (code "3228") (name "unconnected-(SV97-Pad40)") (class "Default")
      (node (ref "SV97") (pin "40") (pinfunction "40_40") (pintype "passive"))
    )
    (net (code "3229") (name "unconnected-(SV98-Pad1)") (class "Default")
      (node (ref "SV98") (pin "1") (pinfunction "1_1") (pintype "passive"))
    )
    (net (code "3230") (name "unconnected-(SV98-Pad2)") (class "Default")
      (node (ref "SV98") (pin "2") (pinfunction "2_2") (pintype "passive"))
    )
    (net (code "3231") (name "unconnected-(SV98-Pad3)") (class "Default")
      (node (ref "SV98") (pin "3") (pinfunction "3_3") (pintype "passive"))
    )
    (net (code "3232") (name "unconnected-(SV98-Pad4)") (class "Default")
      (node (ref "SV98") (pin "4") (pinfunction "4_4") (pintype "passive"))
    )
    (net (code "3233") (name "unconnected-(SV98-Pad5)") (class "Default")
      (node (ref "SV98") (pin "5") (pinfunction "5_5") (pintype "passive"))
    )
    (net (code "3234") (name "unconnected-(SV98-Pad6)") (class "Default")
      (node (ref "SV98") (pin "6") (pinfunction "6_6") (pintype "passive"))
    )
    (net (code "3235") (name "unconnected-(SV98-Pad7)") (class "Default")
      (node (ref "SV98") (pin "7") (pinfunction "7_7") (pintype "passive"))
    )
    (net (code "3236") (name "unconnected-(SV98-Pad8)") (class "Default")
      (node (ref "SV98") (pin "8") (pinfunction "8_8") (pintype "passive"))
    )
    (net (code "3237") (name "unconnected-(SV98-Pad9)") (class "Default")
      (node (ref "SV98") (pin "9") (pinfunction "9_9") (pintype "passive"))
    )
    (net (code "3238") (name "unconnected-(SV98-Pad10)") (class "Default")
      (node (ref "SV98") (pin "10") (pinfunction "10_10") (pintype "passive"))
    )
    (net (code "3239") (name "unconnected-(SV98-Pad11)") (class "Default")
      (node (ref "SV98") (pin "11") (pinfunction "11_11") (pintype "passive"))
    )
    (net (code "3240") (name "unconnected-(SV98-Pad12)") (class "Default")
      (node (ref "SV98") (pin "12") (pinfunction "12_12") (pintype "passive"))
    )
    (net (code "3241") (name "unconnected-(SV98-Pad13)") (class "Default")
      (node (ref "SV98") (pin "13") (pinfunction "13_13") (pintype "passive"))
    )
    (net (code "3242") (name "unconnected-(SV98-Pad14)") (class "Default")
      (node (ref "SV98") (pin "14") (pinfunction "14_14") (pintype "passive"))
    )
    (net (code "3243") (name "unconnected-(SV98-Pad15)") (class "Default")
      (node (ref "SV98") (pin "15") (pinfunction "15_15") (pintype "passive"))
    )
    (net (code "3244") (name "unconnected-(SV98-Pad16)") (class "Default")
      (node (ref "SV98") (pin "16") (pinfunction "16_16") (pintype "passive"))
    )
    (net (code "3245") (name "unconnected-(SV98-Pad17)") (class "Default")
      (node (ref "SV98") (pin "17") (pinfunction "17_17") (pintype "passive"))
    )
    (net (code "3246") (name "unconnected-(SV98-Pad18)") (class "Default")
      (node (ref "SV98") (pin "18") (pinfunction "18_18") (pintype "passive"))
    )
    (net (code "3247") (name "unconnected-(SV98-Pad19)") (class "Default")
      (node (ref "SV98") (pin "19") (pinfunction "19_19") (pintype "passive"))
    )
    (net (code "3248") (name "unconnected-(SV98-Pad20)") (class "Default")
      (node (ref "SV98") (pin "20") (pinfunction "20_20") (pintype "passive"))
    )
    (net (code "3249") (name "unconnected-(SV98-Pad21)") (class "Default")
      (node (ref "SV98") (pin "21") (pinfunction "21_21") (pintype "passive"))
    )
    (net (code "3250") (name "unconnected-(SV98-Pad22)") (class "Default")
      (node (ref "SV98") (pin "22") (pinfunction "22_22") (pintype "passive"))
    )
    (net (code "3251") (name "unconnected-(SV98-Pad23)") (class "Default")
      (node (ref "SV98") (pin "23") (pinfunction "23_23") (pintype "passive"))
    )
    (net (code "3252") (name "unconnected-(SV98-Pad24)") (class "Default")
      (node (ref "SV98") (pin "24") (pinfunction "24_24") (pintype "passive"))
    )
    (net (code "3253") (name "unconnected-(SV98-Pad25)") (class "Default")
      (node (ref "SV98") (pin "25") (pinfunction "25_25") (pintype "passive"))
    )
    (net (code "3254") (name "unconnected-(SV98-Pad26)") (class "Default")
      (node (ref "SV98") (pin "26") (pinfunction "26_26") (pintype "passive"))
    )
    (net (code "3255") (name "unconnected-(SV98-Pad27)") (class "Default")
      (node (ref "SV98") (pin "27") (pinfunction "27_27") (pintype "passive"))
    )
    (net (code "3256") (name "unconnected-(SV98-Pad28)") (class "Default")
      (node (ref "SV98") (pin "28") (pinfunction "28_28") (pintype "passive"))
    )
    (net (code "3257") (name "unconnected-(SV98-Pad29)") (class "Default")
      (node (ref "SV98") (pin "29") (pinfunction "29_29") (pintype "passive"))
    )
    (net (code "3258") (name "unconnected-(SV98-Pad30)") (class "Default")
      (node (ref "SV98") (pin "30") (pinfunction "30_30") (pintype "passive"))
    )
    (net (code "3259") (name "unconnected-(SV98-Pad31)") (class "Default")
      (node (ref "SV98") (pin "31") (pinfunction "31_31") (pintype "passive"))
    )
    (net (code "3260") (name "unconnected-(SV98-Pad32)") (class "Default")
      (node (ref "SV98") (pin "32") (pinfunction "32_32") (pintype "passive"))
    )
    (net (code "3261") (name "unconnected-(SV98-Pad33)") (class "Default")
      (node (ref "SV98") (pin "33") (pinfunction "33_33") (pintype "passive"))
    )
    (net (code "3262") (name "unconnected-(SV98-Pad34)") (class "Default")
      (node (ref "SV98") (pin "34") (pinfunction "34_34") (pintype "passive"))
    )
    (net (code "3263") (name "unconnected-(SV98-Pad35)") (class "Default")
      (node (ref "SV98") (pin "35") (pinfunction "35_35") (pintype "passive"))
    )
    (net (code "3264") (name "unconnected-(SV98-Pad36)") (class "Default")
      (node (ref "SV98") (pin "36") (pinfunction "36_36") (pintype "passive"))
    )
    (net (code "3265") (name "unconnected-(SV99-Pad1)") (class "Default")
      (node (ref "SV99") (pin "1") (pinfunction "1_1") (pintype "passive"))
    )
    (net (code "3266") (name "unconnected-(SV99-Pad2)") (class "Default")
      (node (ref "SV99") (pin "2") (pinfunction "2_2") (pintype "passive"))
    )
    (net (code "3267") (name "unconnected-(SV99-Pad3)") (class "Default")
      (node (ref "SV99") (pin "3") (pinfunction "3_3") (pintype "passive"))
    )
    (net (code "3268") (name "unconnected-(SV99-Pad4)") (class "Default")
      (node (ref "SV99") (pin "4") (pinfunction "4_4") (pintype "passive"))
    )
    (net (code "3269") (name "unconnected-(SV99-Pad5)") (class "Default")
      (node (ref "SV99") (pin "5") (pinfunction "5_5") (pintype "passive"))
    )
    (net (code "3270") (name "unconnected-(SV99-Pad6)") (class "Default")
      (node (ref "SV99") (pin "6") (pinfunction "6_6") (pintype "passive"))
    )
    (net (code "3271") (name "unconnected-(SV99-Pad7)") (class "Default")
      (node (ref "SV99") (pin "7") (pinfunction "7_7") (pintype "passive"))
    )
    (net (code "3272") (name "unconnected-(SV99-Pad8)") (class "Default")
      (node (ref "SV99") (pin "8") (pinfunction "8_8") (pintype "passive"))
    )
    (net (code "3273") (name "unconnected-(SV99-Pad9)") (class "Default")
      (node (ref "SV99") (pin "9") (pinfunction "9_9") (pintype "passive"))
    )
    (net (code "3274") (name "unconnected-(SV99-Pad10)") (class "Default")
      (node (ref "SV99") (pin "10") (pinfunction "10_10") (pintype "passive"))
    )
    (net (code "3275") (name "unconnected-(SV99-Pad11)") (class "Default")
      (node (ref "SV99") (pin "11") (pinfunction "11_11") (pintype "passive"))
    )
    (net (code "3276") (name "unconnected-(SV99-Pad12)") (class "Default")
      (node (ref "SV99") (pin "12") (pinfunction "12_12") (pintype "passive"))
    )
    (net (code "3277") (name "unconnected-(SV99-Pad13)") (class "Default")
      (node (ref "SV99") (pin "13") (pinfunction "13_13") (pintype "passive"))
    )
    (net (code "3278") (name "unconnected-(SV99-Pad14)") (class "Default")
      (node (ref "SV99") (pin "14") (pinfunction "14_14") (pintype "passive"))
    )
    (net (code "3279") (name "unconnected-(SV99-Pad15)") (class "Default")
      (node (ref "SV99") (pin "15") (pinfunction "15_15") (pintype "passive"))
    )
    (net (code "3280") (name "unconnected-(SV99-Pad16)") (class "Default")
      (node (ref "SV99") (pin "16") (pinfunction "16_16") (pintype "passive"))
    )
    (net (code "3281") (name "unconnected-(SV99-Pad17)") (class "Default")
      (node (ref "SV99") (pin "17") (pinfunction "17_17") (pintype "passive"))
    )
    (net (code "3282") (name "unconnected-(SV99-Pad18)") (class "Default")
      (node (ref "SV99") (pin "18") (pinfunction "18_18") (pintype "passive"))
    )
    (net (code "3283") (name "unconnected-(SV99-Pad19)") (class "Default")
      (node (ref "SV99") (pin "19") (pinfunction "19_19") (pintype "passive"))
    )
    (net (code "3284") (name "unconnected-(SV99-Pad20)") (class "Default")
      (node (ref "SV99") (pin "20") (pinfunction "20_20") (pintype "passive"))
    )
    (net (code "3285") (name "unconnected-(SV99-Pad21)") (class "Default")
      (node (ref "SV99") (pin "21") (pinfunction "21_21") (pintype "passive"))
    )
    (net (code "3286") (name "unconnected-(SV99-Pad22)") (class "Default")
      (node (ref "SV99") (pin "22") (pinfunction "22_22") (pintype "passive"))
    )
    (net (code "3287") (name "unconnected-(SV99-Pad23)") (class "Default")
      (node (ref "SV99") (pin "23") (pinfunction "23_23") (pintype "passive"))
    )
    (net (code "3288") (name "unconnected-(SV99-Pad24)") (class "Default")
      (node (ref "SV99") (pin "24") (pinfunction "24_24") (pintype "passive"))
    )
    (net (code "3289") (name "unconnected-(SV99-Pad25)") (class "Default")
      (node (ref "SV99") (pin "25") (pinfunction "25_25") (pintype "passive"))
    )
    (net (code "3290") (name "unconnected-(SV99-Pad26)") (class "Default")
      (node (ref "SV99") (pin "26") (pinfunction "26_26") (pintype "passive"))
    )
    (net (code "3291") (name "unconnected-(SV99-Pad27)") (class "Default")
      (node (ref "SV99") (pin "27") (pinfunction "27_27") (pintype "passive"))
    )
    (net (code "3292") (name "unconnected-(SV99-Pad28)") (class "Default")
      (node (ref "SV99") (pin "28") (pinfunction "28_28") (pintype "passive"))
    )
    (net (code "3293") (name "unconnected-(SV99-Pad29)") (class "Default")
      (node (ref "SV99") (pin "29") (pinfunction "29_29") (pintype "passive"))
    )
    (net (code "3294") (name "unconnected-(SV99-Pad30)") (class "Default")
      (node (ref "SV99") (pin "30") (pinfunction "30_30") (pintype "passive"))
    )
    (net (code "3295") (name "unconnected-(SV99-Pad31)") (class "Default")
      (node (ref "SV99") (pin "31") (pinfunction "31_31") (pintype "passive"))
    )
    (net (code "3296") (name "unconnected-(SV99-Pad32)") (class "Default")
      (node (ref "SV99") (pin "32") (pinfunction "32_32") (pintype "passive"))
    )
    (net (code "3297") (name "unconnected-(SV99-Pad33)") (class "Default")
      (node (ref "SV99") (pin "33") (pinfunction "33_33") (pintype "passive"))
    )
    (net (code "3298") (name "unconnected-(SV99-Pad34)") (class "Default")
      (node (ref "SV99") (pin "34") (pinfunction "34_34") (pintype "passive"))
    )
    (net (code "3299") (name "unconnected-(SV99-Pad35)") (class "Default")
      (node (ref "SV99") (pin "35") (pinfunction "35_35") (pintype "passive"))
    )
    (net (code "3300") (name "unconnected-(SV99-Pad36)") (class "Default")
      (node (ref "SV99") (pin "36") (pinfunction "36_36") (pintype "passive"))
    )
    (net (code "3301") (name "unconnected-(SV100-Pad1)") (class "Default")
      (node (ref "SV100") (pin "1") (pinfunction "1_1") (pintype "passive"))
    )
    (net (code "3302") (name "unconnected-(SV100-Pad2)") (class "Default")
      (node (ref "SV100") (pin "2") (pinfunction "2_2") (pintype "passive"))
    )
    (net (code "3303") (name "unconnected-(SV100-Pad3)") (class "Default")
      (node (ref "SV100") (pin "3") (pinfunction "3_3") (pintype "passive"))
    )
    (net (code "3304") (name "unconnected-(SV100-Pad4)") (class "Default")
      (node (ref "SV100") (pin "4") (pinfunction "4_4") (pintype "passive"))
    )
    (net (code "3305") (name "unconnected-(SV100-Pad5)") (class "Default")
      (node (ref "SV100") (pin "5") (pinfunction "5_5") (pintype "passive"))
    )
    (net (code "3306") (name "unconnected-(SV100-Pad6)") (class "Default")
      (node (ref "SV100") (pin "6") (pinfunction "6_6") (pintype "passive"))
    )
    (net (code "3307") (name "unconnected-(SV100-Pad7)") (class "Default")
      (node (ref "SV100") (pin "7") (pinfunction "7_7") (pintype "passive"))
    )
    (net (code "3308") (name "unconnected-(SV100-Pad8)") (class "Default")
      (node (ref "SV100") (pin "8") (pinfunction "8_8") (pintype "passive"))
    )
    (net (code "3309") (name "unconnected-(SV100-Pad9)") (class "Default")
      (node (ref "SV100") (pin "9") (pinfunction "9_9") (pintype "passive"))
    )
    (net (code "3310") (name "unconnected-(SV100-Pad10)") (class "Default")
      (node (ref "SV100") (pin "10") (pinfunction "10_10") (pintype "passive"))
    )
    (net (code "3311") (name "unconnected-(SV100-Pad11)") (class "Default")
      (node (ref "SV100") (pin "11") (pinfunction "11_11") (pintype "passive"))
    )
    (net (code "3312") (name "unconnected-(SV100-Pad12)") (class "Default")
      (node (ref "SV100") (pin "12") (pinfunction "12_12") (pintype "passive"))
    )
    (net (code "3313") (name "unconnected-(SV100-Pad13)") (class "Default")
      (node (ref "SV100") (pin "13") (pinfunction "13_13") (pintype "passive"))
    )
    (net (code "3314") (name "unconnected-(SV100-Pad14)") (class "Default")
      (node (ref "SV100") (pin "14") (pinfunction "14_14") (pintype "passive"))
    )
    (net (code "3315") (name "unconnected-(SV100-Pad15)") (class "Default")
      (node (ref "SV100") (pin "15") (pinfunction "15_15") (pintype "passive"))
    )
    (net (code "3316") (name "unconnected-(SV100-Pad16)") (class "Default")
      (node (ref "SV100") (pin "16") (pinfunction "16_16") (pintype "passive"))
    )
    (net (code "3317") (name "unconnected-(SV100-Pad17)") (class "Default")
      (node (ref "SV100") (pin "17") (pinfunction "17_17") (pintype "passive"))
    )
    (net (code "3318") (name "unconnected-(SV100-Pad18)") (class "Default")
      (node (ref "SV100") (pin "18") (pinfunction "18_18") (pintype "passive"))
    )
    (net (code "3319") (name "unconnected-(SV100-Pad19)") (class "Default")
      (node (ref "SV100") (pin "19") (pinfunction "19_19") (pintype "passive"))
    )
    (net (code "3320") (name "unconnected-(SV100-Pad20)") (class "Default")
      (node (ref "SV100") (pin "20") (pinfunction "20_20") (pintype "passive"))
    )
    (net (code "3321") (name "unconnected-(SV100-Pad21)") (class "Default")
      (node (ref "SV100") (pin "21") (pinfunction "21_21") (pintype "passive"))
    )
    (net (code "3322") (name "unconnected-(SV100-Pad22)") (class "Default")
      (node (ref "SV100") (pin "22") (pinfunction "22_22") (pintype "passive"))
    )
    (net (code "3323") (name "unconnected-(SV100-Pad23)") (class "Default")
      (node (ref "SV100") (pin "23") (pinfunction "23_23") (pintype "passive"))
    )
    (net (code "3324") (name "unconnected-(SV100-Pad24)") (class "Default")
      (node (ref "SV100") (pin "24") (pinfunction "24_24") (pintype "passive"))
    )
    (net (code "3325") (name "unconnected-(SV100-Pad25)") (class "Default")
      (node (ref "SV100") (pin "25") (pinfunction "25_25") (pintype "passive"))
    )
    (net (code "3326") (name "unconnected-(SV100-Pad26)") (class "Default")
      (node (ref "SV100") (pin "26") (pinfunction "26_26") (pintype "passive"))
    )
    (net (code "3327") (name "unconnected-(SV100-Pad27)") (class "Default")
      (node (ref "SV100") (pin "27") (pinfunction "27_27") (pintype "passive"))
    )
    (net (code "3328") (name "unconnected-(SV100-Pad28)") (class "Default")
      (node (ref "SV100") (pin "28") (pinfunction "28_28") (pintype "passive"))
    )
    (net (code "3329") (name "unconnected-(SV100-Pad29)") (class "Default")
      (node (ref "SV100") (pin "29") (pinfunction "29_29") (pintype "passive"))
    )
    (net (code "3330") (name "unconnected-(SV100-Pad30)") (class "Default")
      (node (ref "SV100") (pin "30") (pinfunction "30_30") (pintype "passive"))
    )
    (net (code "3331") (name "unconnected-(SV100-Pad31)") (class "Default")
      (node (ref "SV100") (pin "31") (pinfunction "31_31") (pintype "passive"))
    )
    (net (code "3332") (name "unconnected-(SV100-Pad32)") (class "Default")
      (node (ref "SV100") (pin "32") (pinfunction "32_32") (pintype "passive"))
    )
    (net (code "3333") (name "unconnected-(SV100-Pad33)") (class "Default")
      (node (ref "SV100") (pin "33") (pinfunction "33_33") (pintype "passive"))
    )
    (net (code "3334") (name "unconnected-(SV100-Pad34)") (class "Default")
      (node (ref "SV100") (pin "34") (pinfunction "34_34") (pintype "passive"))
    )
    (net (code "3335") (name "unconnected-(SV100-Pad35)") (class "Default")
      (node (ref "SV100") (pin "35") (pinfunction "35_35") (pintype "passive"))
    )
    (net (code "3336") (name "unconnected-(SV100-Pad36)") (class "Default")
      (node (ref "SV100") (pin "36") (pinfunction "36_36") (pintype "passive"))
    )
    (net (code "3337") (name "unconnected-(SV101-Pad1)") (class "Default")
      (node (ref "SV101") (pin "1") (pinfunction "1_1") (pintype "passive"))
    )
    (net (code "3338") (name "unconnected-(SV101-Pad2)") (class "Default")
      (node (ref "SV101") (pin "2") (pinfunction "2_2") (pintype "passive"))
    )
    (net (code "3339") (name "unconnected-(SV101-Pad3)") (class "Default")
      (node (ref "SV101") (pin "3") (pinfunction "3_3") (pintype "passive"))
    )
    (net (code "3340") (name "unconnected-(SV101-Pad4)") (class "Default")
      (node (ref "SV101") (pin "4") (pinfunction "4_4") (pintype "passive"))
    )
    (net (code "3341") (name "unconnected-(SV101-Pad5)") (class "Default")
      (node (ref "SV101") (pin "5") (pinfunction "5_5") (pintype "passive"))
    )
    (net (code "3342") (name "unconnected-(SV101-Pad6)") (class "Default")
      (node (ref "SV101") (pin "6") (pinfunction "6_6") (pintype "passive"))
    )
    (net (code "3343") (name "unconnected-(SV101-Pad7)") (class "Default")
      (node (ref "SV101") (pin "7") (pinfunction "7_7") (pintype "passive"))
    )
    (net (code "3344") (name "unconnected-(SV101-Pad8)") (class "Default")
      (node (ref "SV101") (pin "8") (pinfunction "8_8") (pintype "passive"))
    )
    (net (code "3345") (name "unconnected-(SV101-Pad9)") (class "Default")
      (node (ref "SV101") (pin "9") (pinfunction "9_9") (pintype "passive"))
    )
    (net (code "3346") (name "unconnected-(SV101-Pad10)") (class "Default")
      (node (ref "SV101") (pin "10") (pinfunction "10_10") (pintype "passive"))
    )
    (net (code "3347") (name "unconnected-(SV101-Pad11)") (class "Default")
      (node (ref "SV101") (pin "11") (pinfunction "11_11") (pintype "passive"))
    )
    (net (code "3348") (name "unconnected-(SV101-Pad12)") (class "Default")
      (node (ref "SV101") (pin "12") (pinfunction "12_12") (pintype "passive"))
    )
    (net (code "3349") (name "unconnected-(SV101-Pad13)") (class "Default")
      (node (ref "SV101") (pin "13") (pinfunction "13_13") (pintype "passive"))
    )
    (net (code "3350") (name "unconnected-(SV101-Pad14)") (class "Default")
      (node (ref "SV101") (pin "14") (pinfunction "14_14") (pintype "passive"))
    )
    (net (code "3351") (name "unconnected-(SV101-Pad15)") (class "Default")
      (node (ref "SV101") (pin "15") (pinfunction "15_15") (pintype "passive"))
    )
    (net (code "3352") (name "unconnected-(SV101-Pad16)") (class "Default")
      (node (ref "SV101") (pin "16") (pinfunction "16_16") (pintype "passive"))
    )
    (net (code "3353") (name "unconnected-(SV101-Pad17)") (class "Default")
      (node (ref "SV101") (pin "17") (pinfunction "17_17") (pintype "passive"))
    )
    (net (code "3354") (name "unconnected-(SV101-Pad18)") (class "Default")
      (node (ref "SV101") (pin "18") (pinfunction "18_18") (pintype "passive"))
    )
    (net (code "3355") (name "unconnected-(SV101-Pad19)") (class "Default")
      (node (ref "SV101") (pin "19") (pinfunction "19_19") (pintype "passive"))
    )
    (net (code "3356") (name "unconnected-(SV101-Pad20)") (class "Default")
      (node (ref "SV101") (pin "20") (pinfunction "20_20") (pintype "passive"))
    )
    (net (code "3357") (name "unconnected-(SV101-Pad21)") (class "Default")
      (node (ref "SV101") (pin "21") (pinfunction "21_21") (pintype "passive"))
    )
    (net (code "3358") (name "unconnected-(SV101-Pad22)") (class "Default")
      (node (ref "SV101") (pin "22") (pinfunction "22_22") (pintype "passive"))
    )
    (net (code "3359") (name "unconnected-(SV101-Pad23)") (class "Default")
      (node (ref "SV101") (pin "23") (pinfunction "23_23") (pintype "passive"))
    )
    (net (code "3360") (name "unconnected-(SV101-Pad24)") (class "Default")
      (node (ref "SV101") (pin "24") (pinfunction "24_24") (pintype "passive"))
    )
    (net (code "3361") (name "unconnected-(SV101-Pad25)") (class "Default")
      (node (ref "SV101") (pin "25") (pinfunction "25_25") (pintype "passive"))
    )
    (net (code "3362") (name "unconnected-(SV101-Pad26)") (class "Default")
      (node (ref "SV101") (pin "26") (pinfunction "26_26") (pintype "passive"))
    )
    (net (code "3363") (name "unconnected-(SV101-Pad27)") (class "Default")
      (node (ref "SV101") (pin "27") (pinfunction "27_27") (pintype "passive"))
    )
    (net (code "3364") (name "unconnected-(SV101-Pad28)") (class "Default")
      (node (ref "SV101") (pin "28") (pinfunction "28_28") (pintype "passive"))
    )
    (net (code "3365") (name "unconnected-(SV101-Pad29)") (class "Default")
      (node (ref "SV101") (pin "29") (pinfunction "29_29") (pintype "passive"))
    )
    (net (code "3366") (name "unconnected-(SV101-Pad30)") (class "Default")
      (node (ref "SV101") (pin "30") (pinfunction "30_30") (pintype "passive"))
    )
    (net (code "3367") (name "unconnected-(SV101-Pad31)") (class "Default")
      (node (ref "SV101") (pin "31") (pinfunction "31_31") (pintype "passive"))
    )
    (net (code "3368") (name "unconnected-(SV101-Pad32)") (class "Default")
      (node (ref "SV101") (pin "32") (pinfunction "32_32") (pintype "passive"))
    )
    (net (code "3369") (name "unconnected-(SV101-Pad33)") (class "Default")
      (node (ref "SV101") (pin "33") (pinfunction "33_33") (pintype "passive"))
    )
    (net (code "3370") (name "unconnected-(SV101-Pad34)") (class "Default")
      (node (ref "SV101") (pin "34") (pinfunction "34_34") (pintype "passive"))
    )
    (net (code "3371") (name "unconnected-(SV101-Pad35)") (class "Default")
      (node (ref "SV101") (pin "35") (pinfunction "35_35") (pintype "passive"))
    )
    (net (code "3372") (name "unconnected-(SV101-Pad36)") (class "Default")
      (node (ref "SV101") (pin "36") (pinfunction "36_36") (pintype "passive"))
    )
    (net (code "3373") (name "unconnected-(SV102-Pad1)") (class "Default")
      (node (ref "SV102") (pin "1") (pinfunction "1_1") (pintype "passive"))
    )
    (net (code "3374") (name "unconnected-(SV102-Pad2)") (class "Default")
      (node (ref "SV102") (pin "2") (pinfunction "2_2") (pintype "passive"))
    )
    (net (code "3375") (name "unconnected-(SV102-Pad3)") (class "Default")
      (node (ref "SV102") (pin "3") (pinfunction "3_3") (pintype "passive"))
    )
    (net (code "3376") (name "unconnected-(SV102-Pad4)") (class "Default")
      (node (ref "SV102") (pin "4") (pinfunction "4_4") (pintype "passive"))
    )
    (net (code "3377") (name "unconnected-(SV102-Pad5)") (class "Default")
      (node (ref "SV102") (pin "5") (pinfunction "5_5") (pintype "passive"))
    )
    (net (code "3378") (name "unconnected-(SV102-Pad6)") (class "Default")
      (node (ref "SV102") (pin "6") (pinfunction "6_6") (pintype "passive"))
    )
    (net (code "3379") (name "unconnected-(SV102-Pad7)") (class "Default")
      (node (ref "SV102") (pin "7") (pinfunction "7_7") (pintype "passive"))
    )
    (net (code "3380") (name "unconnected-(SV102-Pad8)") (class "Default")
      (node (ref "SV102") (pin "8") (pinfunction "8_8") (pintype "passive"))
    )
    (net (code "3381") (name "unconnected-(SV102-Pad9)") (class "Default")
      (node (ref "SV102") (pin "9") (pinfunction "9_9") (pintype "passive"))
    )
    (net (code "3382") (name "unconnected-(SV102-Pad10)") (class "Default")
      (node (ref "SV102") (pin "10") (pinfunction "10_10") (pintype "passive"))
    )
    (net (code "3383") (name "unconnected-(SV102-Pad11)") (class "Default")
      (node (ref "SV102") (pin "11") (pinfunction "11_11") (pintype "passive"))
    )
    (net (code "3384") (name "unconnected-(SV102-Pad12)") (class "Default")
      (node (ref "SV102") (pin "12") (pinfunction "12_12") (pintype "passive"))
    )
    (net (code "3385") (name "unconnected-(SV102-Pad13)") (class "Default")
      (node (ref "SV102") (pin "13") (pinfunction "13_13") (pintype "passive"))
    )
    (net (code "3386") (name "unconnected-(SV102-Pad14)") (class "Default")
      (node (ref "SV102") (pin "14") (pinfunction "14_14") (pintype "passive"))
    )
    (net (code "3387") (name "unconnected-(SV102-Pad15)") (class "Default")
      (node (ref "SV102") (pin "15") (pinfunction "15_15") (pintype "passive"))
    )
    (net (code "3388") (name "unconnected-(SV102-Pad16)") (class "Default")
      (node (ref "SV102") (pin "16") (pinfunction "16_16") (pintype "passive"))
    )
    (net (code "3389") (name "unconnected-(SV102-Pad17)") (class "Default")
      (node (ref "SV102") (pin "17") (pinfunction "17_17") (pintype "passive"))
    )
    (net (code "3390") (name "unconnected-(SV102-Pad18)") (class "Default")
      (node (ref "SV102") (pin "18") (pinfunction "18_18") (pintype "passive"))
    )
    (net (code "3391") (name "unconnected-(SV102-Pad19)") (class "Default")
      (node (ref "SV102") (pin "19") (pinfunction "19_19") (pintype "passive"))
    )
    (net (code "3392") (name "unconnected-(SV102-Pad20)") (class "Default")
      (node (ref "SV102") (pin "20") (pinfunction "20_20") (pintype "passive"))
    )
    (net (code "3393") (name "unconnected-(SV102-Pad21)") (class "Default")
      (node (ref "SV102") (pin "21") (pinfunction "21_21") (pintype "passive"))
    )
    (net (code "3394") (name "unconnected-(SV102-Pad22)") (class "Default")
      (node (ref "SV102") (pin "22") (pinfunction "22_22") (pintype "passive"))
    )
    (net (code "3395") (name "unconnected-(SV102-Pad23)") (class "Default")
      (node (ref "SV102") (pin "23") (pinfunction "23_23") (pintype "passive"))
    )
    (net (code "3396") (name "unconnected-(SV102-Pad24)") (class "Default")
      (node (ref "SV102") (pin "24") (pinfunction "24_24") (pintype "passive"))
    )
    (net (code "3397") (name "unconnected-(SV102-Pad25)") (class "Default")
      (node (ref "SV102") (pin "25") (pinfunction "25_25") (pintype "passive"))
    )
    (net (code "3398") (name "unconnected-(SV102-Pad26)") (class "Default")
      (node (ref "SV102") (pin "26") (pinfunction "26_26") (pintype "passive"))
    )
    (net (code "3399") (name "unconnected-(SV102-Pad27)") (class "Default")
      (node (ref "SV102") (pin "27") (pinfunction "27_27") (pintype "passive"))
    )
    (net (code "3400") (name "unconnected-(SV102-Pad28)") (class "Default")
      (node (ref "SV102") (pin "28") (pinfunction "28_28") (pintype "passive"))
    )
    (net (code "3401") (name "unconnected-(SV102-Pad29)") (class "Default")
      (node (ref "SV102") (pin "29") (pinfunction "29_29") (pintype "passive"))
    )
    (net (code "3402") (name "unconnected-(SV102-Pad30)") (class "Default")
      (node (ref "SV102") (pin "30") (pinfunction "30_30") (pintype "passive"))
    )
    (net (code "3403") (name "unconnected-(SV102-Pad31)") (class "Default")
      (node (ref "SV102") (pin "31") (pinfunction "31_31") (pintype "passive"))
    )
    (net (code "3404") (name "unconnected-(SV102-Pad32)") (class "Default")
      (node (ref "SV102") (pin "32") (pinfunction "32_32") (pintype "passive"))
    )
    (net (code "3405") (name "unconnected-(SV102-Pad33)") (class "Default")
      (node (ref "SV102") (pin "33") (pinfunction "33_33") (pintype "passive"))
    )
    (net (code "3406") (name "unconnected-(SV102-Pad34)") (class "Default")
      (node (ref "SV102") (pin "34") (pinfunction "34_34") (pintype "passive"))
    )
    (net (code "3407") (name "unconnected-(SV102-Pad35)") (class "Default")
      (node (ref "SV102") (pin "35") (pinfunction "35_35") (pintype "passive"))
    )
    (net (code "3408") (name "unconnected-(SV102-Pad36)") (class "Default")
      (node (ref "SV102") (pin "36") (pinfunction "36_36") (pintype "passive"))
    )
    (net (code "3409") (name "unconnected-(SV102-Pad37)") (class "Default")
      (node (ref "SV102") (pin "37") (pinfunction "37_37") (pintype "passive"))
    )
    (net (code "3410") (name "unconnected-(SV102-Pad38)") (class "Default")
      (node (ref "SV102") (pin "38") (pinfunction "38_38") (pintype "passive"))
    )
    (net (code "3411") (name "unconnected-(SV102-Pad39)") (class "Default")
      (node (ref "SV102") (pin "39") (pinfunction "39_39") (pintype "passive"))
    )
    (net (code "3412") (name "unconnected-(SV102-Pad40)") (class "Default")
      (node (ref "SV102") (pin "40") (pinfunction "40_40") (pintype "passive"))
    )
    (net (code "3413") (name "unconnected-(SV103-Pad1)") (class "Default")
      (node (ref "SV103") (pin "1") (pinfunction "1_1") (pintype "passive"))
    )
    (net (code "3414") (name "unconnected-(SV103-Pad2)") (class "Default")
      (node (ref "SV103") (pin "2") (pinfunction "2_2") (pintype "passive"))
    )
    (net (code "3415") (name "unconnected-(SV103-Pad3)") (class "Default")
      (node (ref "SV103") (pin "3") (pinfunction "3_3") (pintype "passive"))
    )
    (net (code "3416") (name "unconnected-(SV103-Pad4)") (class "Default")
      (node (ref "SV103") (pin "4") (pinfunction "4_4") (pintype "passive"))
    )
    (net (code "3417") (name "unconnected-(SV103-Pad5)") (class "Default")
      (node (ref "SV103") (pin "5") (pinfunction "5_5") (pintype "passive"))
    )
    (net (code "3418") (name "unconnected-(SV103-Pad6)") (class "Default")
      (node (ref "SV103") (pin "6") (pinfunction "6_6") (pintype "passive"))
    )
    (net (code "3419") (name "unconnected-(SV103-Pad7)") (class "Default")
      (node (ref "SV103") (pin "7") (pinfunction "7_7") (pintype "passive"))
    )
    (net (code "3420") (name "unconnected-(SV103-Pad8)") (class "Default")
      (node (ref "SV103") (pin "8") (pinfunction "8_8") (pintype "passive"))
    )
    (net (code "3421") (name "unconnected-(SV103-Pad9)") (class "Default")
      (node (ref "SV103") (pin "9") (pinfunction "9_9") (pintype "passive"))
    )
    (net (code "3422") (name "unconnected-(SV103-Pad10)") (class "Default")
      (node (ref "SV103") (pin "10") (pinfunction "10_10") (pintype "passive"))
    )
    (net (code "3423") (name "unconnected-(SV103-Pad11)") (class "Default")
      (node (ref "SV103") (pin "11") (pinfunction "11_11") (pintype "passive"))
    )
    (net (code "3424") (name "unconnected-(SV103-Pad12)") (class "Default")
      (node (ref "SV103") (pin "12") (pinfunction "12_12") (pintype "passive"))
    )
    (net (code "3425") (name "unconnected-(SV103-Pad13)") (class "Default")
      (node (ref "SV103") (pin "13") (pinfunction "13_13") (pintype "passive"))
    )
    (net (code "3426") (name "unconnected-(SV103-Pad14)") (class "Default")
      (node (ref "SV103") (pin "14") (pinfunction "14_14") (pintype "passive"))
    )
    (net (code "3427") (name "unconnected-(SV103-Pad15)") (class "Default")
      (node (ref "SV103") (pin "15") (pinfunction "15_15") (pintype "passive"))
    )
    (net (code "3428") (name "unconnected-(SV103-Pad16)") (class "Default")
      (node (ref "SV103") (pin "16") (pinfunction "16_16") (pintype "passive"))
    )
    (net (code "3429") (name "unconnected-(SV103-Pad17)") (class "Default")
      (node (ref "SV103") (pin "17") (pinfunction "17_17") (pintype "passive"))
    )
    (net (code "3430") (name "unconnected-(SV103-Pad18)") (class "Default")
      (node (ref "SV103") (pin "18") (pinfunction "18_18") (pintype "passive"))
    )
    (net (code "3431") (name "unconnected-(SV103-Pad19)") (class "Default")
      (node (ref "SV103") (pin "19") (pinfunction "19_19") (pintype "passive"))
    )
    (net (code "3432") (name "unconnected-(SV103-Pad20)") (class "Default")
      (node (ref "SV103") (pin "20") (pinfunction "20_20") (pintype "passive"))
    )
    (net (code "3433") (name "unconnected-(SV103-Pad21)") (class "Default")
      (node (ref "SV103") (pin "21") (pinfunction "21_21") (pintype "passive"))
    )
    (net (code "3434") (name "unconnected-(SV103-Pad22)") (class "Default")
      (node (ref "SV103") (pin "22") (pinfunction "22_22") (pintype "passive"))
    )
    (net (code "3435") (name "unconnected-(SV103-Pad23)") (class "Default")
      (node (ref "SV103") (pin "23") (pinfunction "23_23") (pintype "passive"))
    )
    (net (code "3436") (name "unconnected-(SV103-Pad24)") (class "Default")
      (node (ref "SV103") (pin "24") (pinfunction "24_24") (pintype "passive"))
    )
    (net (code "3437") (name "unconnected-(SV103-Pad25)") (class "Default")
      (node (ref "SV103") (pin "25") (pinfunction "25_25") (pintype "passive"))
    )
    (net (code "3438") (name "unconnected-(SV103-Pad26)") (class "Default")
      (node (ref "SV103") (pin "26") (pinfunction "26_26") (pintype "passive"))
    )
    (net (code "3439") (name "unconnected-(SV103-Pad27)") (class "Default")
      (node (ref "SV103") (pin "27") (pinfunction "27_27") (pintype "passive"))
    )
    (net (code "3440") (name "unconnected-(SV103-Pad28)") (class "Default")
      (node (ref "SV103") (pin "28") (pinfunction "28_28") (pintype "passive"))
    )
    (net (code "3441") (name "unconnected-(SV103-Pad29)") (class "Default")
      (node (ref "SV103") (pin "29") (pinfunction "29_29") (pintype "passive"))
    )
    (net (code "3442") (name "unconnected-(SV103-Pad30)") (class "Default")
      (node (ref "SV103") (pin "30") (pinfunction "30_30") (pintype "passive"))
    )
    (net (code "3443") (name "unconnected-(SV103-Pad31)") (class "Default")
      (node (ref "SV103") (pin "31") (pinfunction "31_31") (pintype "passive"))
    )
    (net (code "3444") (name "unconnected-(SV103-Pad32)") (class "Default")
      (node (ref "SV103") (pin "32") (pinfunction "32_32") (pintype "passive"))
    )
    (net (code "3445") (name "unconnected-(SV103-Pad33)") (class "Default")
      (node (ref "SV103") (pin "33") (pinfunction "33_33") (pintype "passive"))
    )
    (net (code "3446") (name "unconnected-(SV103-Pad34)") (class "Default")
      (node (ref "SV103") (pin "34") (pinfunction "34_34") (pintype "passive"))
    )
    (net (code "3447") (name "unconnected-(SV103-Pad35)") (class "Default")
      (node (ref "SV103") (pin "35") (pinfunction "35_35") (pintype "passive"))
    )
    (net (code "3448") (name "unconnected-(SV103-Pad36)") (class "Default")
      (node (ref "SV103") (pin "36") (pinfunction "36_36") (pintype "passive"))
    )
    (net (code "3449") (name "unconnected-(SV103-Pad37)") (class "Default")
      (node (ref "SV103") (pin "37") (pinfunction "37_37") (pintype "passive"))
    )
    (net (code "3450") (name "unconnected-(SV103-Pad38)") (class "Default")
      (node (ref "SV103") (pin "38") (pinfunction "38_38") (pintype "passive"))
    )
    (net (code "3451") (name "unconnected-(SV103-Pad39)") (class "Default")
      (node (ref "SV103") (pin "39") (pinfunction "39_39") (pintype "passive"))
    )
    (net (code "3452") (name "unconnected-(SV103-Pad40)") (class "Default")
      (node (ref "SV103") (pin "40") (pinfunction "40_40") (pintype "passive"))
    )
    (net (code "3453") (name "unconnected-(SV104-Pad1)") (class "Default")
      (node (ref "SV104") (pin "1") (pinfunction "1_1") (pintype "passive"))
    )
    (net (code "3454") (name "unconnected-(SV104-Pad2)") (class "Default")
      (node (ref "SV104") (pin "2") (pinfunction "2_2") (pintype "passive"))
    )
    (net (code "3455") (name "unconnected-(SV104-Pad3)") (class "Default")
      (node (ref "SV104") (pin "3") (pinfunction "3_3") (pintype "passive"))
    )
    (net (code "3456") (name "unconnected-(SV104-Pad4)") (class "Default")
      (node (ref "SV104") (pin "4") (pinfunction "4_4") (pintype "passive"))
    )
    (net (code "3457") (name "unconnected-(SV104-Pad5)") (class "Default")
      (node (ref "SV104") (pin "5") (pinfunction "5_5") (pintype "passive"))
    )
    (net (code "3458") (name "unconnected-(SV104-Pad6)") (class "Default")
      (node (ref "SV104") (pin "6") (pinfunction "6_6") (pintype "passive"))
    )
    (net (code "3459") (name "unconnected-(SV104-Pad7)") (class "Default")
      (node (ref "SV104") (pin "7") (pinfunction "7_7") (pintype "passive"))
    )
    (net (code "3460") (name "unconnected-(SV104-Pad8)") (class "Default")
      (node (ref "SV104") (pin "8") (pinfunction "8_8") (pintype "passive"))
    )
    (net (code "3461") (name "unconnected-(SV104-Pad9)") (class "Default")
      (node (ref "SV104") (pin "9") (pinfunction "9_9") (pintype "passive"))
    )
    (net (code "3462") (name "unconnected-(SV104-Pad10)") (class "Default")
      (node (ref "SV104") (pin "10") (pinfunction "10_10") (pintype "passive"))
    )
    (net (code "3463") (name "unconnected-(SV104-Pad11)") (class "Default")
      (node (ref "SV104") (pin "11") (pinfunction "11_11") (pintype "passive"))
    )
    (net (code "3464") (name "unconnected-(SV104-Pad12)") (class "Default")
      (node (ref "SV104") (pin "12") (pinfunction "12_12") (pintype "passive"))
    )
    (net (code "3465") (name "unconnected-(SV104-Pad13)") (class "Default")
      (node (ref "SV104") (pin "13") (pinfunction "13_13") (pintype "passive"))
    )
    (net (code "3466") (name "unconnected-(SV104-Pad14)") (class "Default")
      (node (ref "SV104") (pin "14") (pinfunction "14_14") (pintype "passive"))
    )
    (net (code "3467") (name "unconnected-(SV104-Pad15)") (class "Default")
      (node (ref "SV104") (pin "15") (pinfunction "15_15") (pintype "passive"))
    )
    (net (code "3468") (name "unconnected-(SV104-Pad16)") (class "Default")
      (node (ref "SV104") (pin "16") (pinfunction "16_16") (pintype "passive"))
    )
    (net (code "3469") (name "unconnected-(SV104-Pad17)") (class "Default")
      (node (ref "SV104") (pin "17") (pinfunction "17_17") (pintype "passive"))
    )
    (net (code "3470") (name "unconnected-(SV104-Pad18)") (class "Default")
      (node (ref "SV104") (pin "18") (pinfunction "18_18") (pintype "passive"))
    )
    (net (code "3471") (name "unconnected-(SV104-Pad19)") (class "Default")
      (node (ref "SV104") (pin "19") (pinfunction "19_19") (pintype "passive"))
    )
    (net (code "3472") (name "unconnected-(SV104-Pad20)") (class "Default")
      (node (ref "SV104") (pin "20") (pinfunction "20_20") (pintype "passive"))
    )
    (net (code "3473") (name "unconnected-(SV104-Pad21)") (class "Default")
      (node (ref "SV104") (pin "21") (pinfunction "21_21") (pintype "passive"))
    )
    (net (code "3474") (name "unconnected-(SV104-Pad22)") (class "Default")
      (node (ref "SV104") (pin "22") (pinfunction "22_22") (pintype "passive"))
    )
    (net (code "3475") (name "unconnected-(SV104-Pad23)") (class "Default")
      (node (ref "SV104") (pin "23") (pinfunction "23_23") (pintype "passive"))
    )
    (net (code "3476") (name "unconnected-(SV104-Pad24)") (class "Default")
      (node (ref "SV104") (pin "24") (pinfunction "24_24") (pintype "passive"))
    )
    (net (code "3477") (name "unconnected-(SV104-Pad25)") (class "Default")
      (node (ref "SV104") (pin "25") (pinfunction "25_25") (pintype "passive"))
    )
    (net (code "3478") (name "unconnected-(SV104-Pad26)") (class "Default")
      (node (ref "SV104") (pin "26") (pinfunction "26_26") (pintype "passive"))
    )
    (net (code "3479") (name "unconnected-(SV104-Pad27)") (class "Default")
      (node (ref "SV104") (pin "27") (pinfunction "27_27") (pintype "passive"))
    )
    (net (code "3480") (name "unconnected-(SV104-Pad28)") (class "Default")
      (node (ref "SV104") (pin "28") (pinfunction "28_28") (pintype "passive"))
    )
    (net (code "3481") (name "unconnected-(SV104-Pad29)") (class "Default")
      (node (ref "SV104") (pin "29") (pinfunction "29_29") (pintype "passive"))
    )
    (net (code "3482") (name "unconnected-(SV104-Pad30)") (class "Default")
      (node (ref "SV104") (pin "30") (pinfunction "30_30") (pintype "passive"))
    )
    (net (code "3483") (name "unconnected-(SV104-Pad31)") (class "Default")
      (node (ref "SV104") (pin "31") (pinfunction "31_31") (pintype "passive"))
    )
    (net (code "3484") (name "unconnected-(SV104-Pad32)") (class "Default")
      (node (ref "SV104") (pin "32") (pinfunction "32_32") (pintype "passive"))
    )
    (net (code "3485") (name "unconnected-(SV104-Pad33)") (class "Default")
      (node (ref "SV104") (pin "33") (pinfunction "33_33") (pintype "passive"))
    )
    (net (code "3486") (name "unconnected-(SV104-Pad34)") (class "Default")
      (node (ref "SV104") (pin "34") (pinfunction "34_34") (pintype "passive"))
    )
    (net (code "3487") (name "unconnected-(SV104-Pad35)") (class "Default")
      (node (ref "SV104") (pin "35") (pinfunction "35_35") (pintype "passive"))
    )
    (net (code "3488") (name "unconnected-(SV104-Pad36)") (class "Default")
      (node (ref "SV104") (pin "36") (pinfunction "36_36") (pintype "passive"))
    )
    (net (code "3489") (name "unconnected-(SV104-Pad37)") (class "Default")
      (node (ref "SV104") (pin "37") (pinfunction "37_37") (pintype "passive"))
    )
    (net (code "3490") (name "unconnected-(SV104-Pad38)") (class "Default")
      (node (ref "SV104") (pin "38") (pinfunction "38_38") (pintype "passive"))
    )
    (net (code "3491") (name "unconnected-(SV104-Pad39)") (class "Default")
      (node (ref "SV104") (pin "39") (pinfunction "39_39") (pintype "passive"))
    )
    (net (code "3492") (name "unconnected-(SV104-Pad40)") (class "Default")
      (node (ref "SV104") (pin "40") (pinfunction "40_40") (pintype "passive"))
    )
    (net (code "3493") (name "unconnected-(SV105-Pad1)") (class "Default")
      (node (ref "SV105") (pin "1") (pinfunction "1_1") (pintype "passive"))
    )
    (net (code "3494") (name "unconnected-(SV105-Pad2)") (class "Default")
      (node (ref "SV105") (pin "2") (pinfunction "2_2") (pintype "passive"))
    )
    (net (code "3495") (name "unconnected-(SV105-Pad3)") (class "Default")
      (node (ref "SV105") (pin "3") (pinfunction "3_3") (pintype "passive"))
    )
    (net (code "3496") (name "unconnected-(SV105-Pad4)") (class "Default")
      (node (ref "SV105") (pin "4") (pinfunction "4_4") (pintype "passive"))
    )
    (net (code "3497") (name "unconnected-(SV105-Pad5)") (class "Default")
      (node (ref "SV105") (pin "5") (pinfunction "5_5") (pintype "passive"))
    )
    (net (code "3498") (name "unconnected-(SV105-Pad6)") (class "Default")
      (node (ref "SV105") (pin "6") (pinfunction "6_6") (pintype "passive"))
    )
    (net (code "3499") (name "unconnected-(SV105-Pad7)") (class "Default")
      (node (ref "SV105") (pin "7") (pinfunction "7_7") (pintype "passive"))
    )
    (net (code "3500") (name "unconnected-(SV105-Pad8)") (class "Default")
      (node (ref "SV105") (pin "8") (pinfunction "8_8") (pintype "passive"))
    )
    (net (code "3501") (name "unconnected-(SV105-Pad9)") (class "Default")
      (node (ref "SV105") (pin "9") (pinfunction "9_9") (pintype "passive"))
    )
    (net (code "3502") (name "unconnected-(SV105-Pad10)") (class "Default")
      (node (ref "SV105") (pin "10") (pinfunction "10_10") (pintype "passive"))
    )
    (net (code "3503") (name "unconnected-(SV105-Pad11)") (class "Default")
      (node (ref "SV105") (pin "11") (pinfunction "11_11") (pintype "passive"))
    )
    (net (code "3504") (name "unconnected-(SV105-Pad12)") (class "Default")
      (node (ref "SV105") (pin "12") (pinfunction "12_12") (pintype "passive"))
    )
    (net (code "3505") (name "unconnected-(SV105-Pad13)") (class "Default")
      (node (ref "SV105") (pin "13") (pinfunction "13_13") (pintype "passive"))
    )
    (net (code "3506") (name "unconnected-(SV105-Pad14)") (class "Default")
      (node (ref "SV105") (pin "14") (pinfunction "14_14") (pintype "passive"))
    )
    (net (code "3507") (name "unconnected-(SV105-Pad15)") (class "Default")
      (node (ref "SV105") (pin "15") (pinfunction "15_15") (pintype "passive"))
    )
    (net (code "3508") (name "unconnected-(SV105-Pad16)") (class "Default")
      (node (ref "SV105") (pin "16") (pinfunction "16_16") (pintype "passive"))
    )
    (net (code "3509") (name "unconnected-(SV105-Pad17)") (class "Default")
      (node (ref "SV105") (pin "17") (pinfunction "17_17") (pintype "passive"))
    )
    (net (code "3510") (name "unconnected-(SV105-Pad18)") (class "Default")
      (node (ref "SV105") (pin "18") (pinfunction "18_18") (pintype "passive"))
    )
    (net (code "3511") (name "unconnected-(SV105-Pad19)") (class "Default")
      (node (ref "SV105") (pin "19") (pinfunction "19_19") (pintype "passive"))
    )
    (net (code "3512") (name "unconnected-(SV105-Pad20)") (class "Default")
      (node (ref "SV105") (pin "20") (pinfunction "20_20") (pintype "passive"))
    )
    (net (code "3513") (name "unconnected-(SV105-Pad21)") (class "Default")
      (node (ref "SV105") (pin "21") (pinfunction "21_21") (pintype "passive"))
    )
    (net (code "3514") (name "unconnected-(SV105-Pad22)") (class "Default")
      (node (ref "SV105") (pin "22") (pinfunction "22_22") (pintype "passive"))
    )
    (net (code "3515") (name "unconnected-(SV105-Pad23)") (class "Default")
      (node (ref "SV105") (pin "23") (pinfunction "23_23") (pintype "passive"))
    )
    (net (code "3516") (name "unconnected-(SV105-Pad24)") (class "Default")
      (node (ref "SV105") (pin "24") (pinfunction "24_24") (pintype "passive"))
    )
    (net (code "3517") (name "unconnected-(SV105-Pad25)") (class "Default")
      (node (ref "SV105") (pin "25") (pinfunction "25_25") (pintype "passive"))
    )
    (net (code "3518") (name "unconnected-(SV105-Pad26)") (class "Default")
      (node (ref "SV105") (pin "26") (pinfunction "26_26") (pintype "passive"))
    )
    (net (code "3519") (name "unconnected-(SV105-Pad27)") (class "Default")
      (node (ref "SV105") (pin "27") (pinfunction "27_27") (pintype "passive"))
    )
    (net (code "3520") (name "unconnected-(SV105-Pad28)") (class "Default")
      (node (ref "SV105") (pin "28") (pinfunction "28_28") (pintype "passive"))
    )
    (net (code "3521") (name "unconnected-(SV105-Pad29)") (class "Default")
      (node (ref "SV105") (pin "29") (pinfunction "29_29") (pintype "passive"))
    )
    (net (code "3522") (name "unconnected-(SV105-Pad30)") (class "Default")
      (node (ref "SV105") (pin "30") (pinfunction "30_30") (pintype "passive"))
    )
    (net (code "3523") (name "unconnected-(SV105-Pad31)") (class "Default")
      (node (ref "SV105") (pin "31") (pinfunction "31_31") (pintype "passive"))
    )
    (net (code "3524") (name "unconnected-(SV105-Pad32)") (class "Default")
      (node (ref "SV105") (pin "32") (pinfunction "32_32") (pintype "passive"))
    )
    (net (code "3525") (name "unconnected-(SV105-Pad33)") (class "Default")
      (node (ref "SV105") (pin "33") (pinfunction "33_33") (pintype "passive"))
    )
    (net (code "3526") (name "unconnected-(SV105-Pad34)") (class "Default")
      (node (ref "SV105") (pin "34") (pinfunction "34_34") (pintype "passive"))
    )
    (net (code "3527") (name "unconnected-(SV105-Pad35)") (class "Default")
      (node (ref "SV105") (pin "35") (pinfunction "35_35") (pintype "passive"))
    )
    (net (code "3528") (name "unconnected-(SV105-Pad36)") (class "Default")
      (node (ref "SV105") (pin "36") (pinfunction "36_36") (pintype "passive"))
    )
    (net (code "3529") (name "unconnected-(SV105-Pad37)") (class "Default")
      (node (ref "SV105") (pin "37") (pinfunction "37_37") (pintype "passive"))
    )
    (net (code "3530") (name "unconnected-(SV105-Pad38)") (class "Default")
      (node (ref "SV105") (pin "38") (pinfunction "38_38") (pintype "passive"))
    )
    (net (code "3531") (name "unconnected-(SV105-Pad39)") (class "Default")
      (node (ref "SV105") (pin "39") (pinfunction "39_39") (pintype "passive"))
    )
    (net (code "3532") (name "unconnected-(SV105-Pad40)") (class "Default")
      (node (ref "SV105") (pin "40") (pinfunction "40_40") (pintype "passive"))
    )
    (net (code "3533") (name "unconnected-(SV106-Pad1)") (class "Default")
      (node (ref "SV106") (pin "1") (pinfunction "1_1") (pintype "passive"))
    )
    (net (code "3534") (name "unconnected-(SV106-Pad2)") (class "Default")
      (node (ref "SV106") (pin "2") (pinfunction "2_2") (pintype "passive"))
    )
    (net (code "3535") (name "unconnected-(SV106-Pad3)") (class "Default")
      (node (ref "SV106") (pin "3") (pinfunction "3_3") (pintype "passive"))
    )
    (net (code "3536") (name "unconnected-(SV106-Pad4)") (class "Default")
      (node (ref "SV106") (pin "4") (pinfunction "4_4") (pintype "passive"))
    )
    (net (code "3537") (name "unconnected-(SV106-Pad5)") (class "Default")
      (node (ref "SV106") (pin "5") (pinfunction "5_5") (pintype "passive"))
    )
    (net (code "3538") (name "unconnected-(SV106-Pad6)") (class "Default")
      (node (ref "SV106") (pin "6") (pinfunction "6_6") (pintype "passive"))
    )
    (net (code "3539") (name "unconnected-(SV106-Pad7)") (class "Default")
      (node (ref "SV106") (pin "7") (pinfunction "7_7") (pintype "passive"))
    )
    (net (code "3540") (name "unconnected-(SV106-Pad8)") (class "Default")
      (node (ref "SV106") (pin "8") (pinfunction "8_8") (pintype "passive"))
    )
    (net (code "3541") (name "unconnected-(SV106-Pad9)") (class "Default")
      (node (ref "SV106") (pin "9") (pinfunction "9_9") (pintype "passive"))
    )
    (net (code "3542") (name "unconnected-(SV106-Pad10)") (class "Default")
      (node (ref "SV106") (pin "10") (pinfunction "10_10") (pintype "passive"))
    )
    (net (code "3543") (name "unconnected-(SV106-Pad11)") (class "Default")
      (node (ref "SV106") (pin "11") (pinfunction "11_11") (pintype "passive"))
    )
    (net (code "3544") (name "unconnected-(SV106-Pad12)") (class "Default")
      (node (ref "SV106") (pin "12") (pinfunction "12_12") (pintype "passive"))
    )
    (net (code "3545") (name "unconnected-(SV106-Pad13)") (class "Default")
      (node (ref "SV106") (pin "13") (pinfunction "13_13") (pintype "passive"))
    )
    (net (code "3546") (name "unconnected-(SV106-Pad14)") (class "Default")
      (node (ref "SV106") (pin "14") (pinfunction "14_14") (pintype "passive"))
    )
    (net (code "3547") (name "unconnected-(SV106-Pad15)") (class "Default")
      (node (ref "SV106") (pin "15") (pinfunction "15_15") (pintype "passive"))
    )
    (net (code "3548") (name "unconnected-(SV106-Pad16)") (class "Default")
      (node (ref "SV106") (pin "16") (pinfunction "16_16") (pintype "passive"))
    )
    (net (code "3549") (name "unconnected-(SV106-Pad17)") (class "Default")
      (node (ref "SV106") (pin "17") (pinfunction "17_17") (pintype "passive"))
    )
    (net (code "3550") (name "unconnected-(SV106-Pad18)") (class "Default")
      (node (ref "SV106") (pin "18") (pinfunction "18_18") (pintype "passive"))
    )
    (net (code "3551") (name "unconnected-(SV106-Pad19)") (class "Default")
      (node (ref "SV106") (pin "19") (pinfunction "19_19") (pintype "passive"))
    )
    (net (code "3552") (name "unconnected-(SV106-Pad20)") (class "Default")
      (node (ref "SV106") (pin "20") (pinfunction "20_20") (pintype "passive"))
    )
    (net (code "3553") (name "unconnected-(SV106-Pad21)") (class "Default")
      (node (ref "SV106") (pin "21") (pinfunction "21_21") (pintype "passive"))
    )
    (net (code "3554") (name "unconnected-(SV106-Pad22)") (class "Default")
      (node (ref "SV106") (pin "22") (pinfunction "22_22") (pintype "passive"))
    )
    (net (code "3555") (name "unconnected-(SV106-Pad23)") (class "Default")
      (node (ref "SV106") (pin "23") (pinfunction "23_23") (pintype "passive"))
    )
    (net (code "3556") (name "unconnected-(SV106-Pad24)") (class "Default")
      (node (ref "SV106") (pin "24") (pinfunction "24_24") (pintype "passive"))
    )
    (net (code "3557") (name "unconnected-(SV106-Pad25)") (class "Default")
      (node (ref "SV106") (pin "25") (pinfunction "25_25") (pintype "passive"))
    )
    (net (code "3558") (name "unconnected-(SV106-Pad26)") (class "Default")
      (node (ref "SV106") (pin "26") (pinfunction "26_26") (pintype "passive"))
    )
    (net (code "3559") (name "unconnected-(SV106-Pad27)") (class "Default")
      (node (ref "SV106") (pin "27") (pinfunction "27_27") (pintype "passive"))
    )
    (net (code "3560") (name "unconnected-(SV106-Pad28)") (class "Default")
      (node (ref "SV106") (pin "28") (pinfunction "28_28") (pintype "passive"))
    )
    (net (code "3561") (name "unconnected-(SV106-Pad29)") (class "Default")
      (node (ref "SV106") (pin "29") (pinfunction "29_29") (pintype "passive"))
    )
    (net (code "3562") (name "unconnected-(SV106-Pad30)") (class "Default")
      (node (ref "SV106") (pin "30") (pinfunction "30_30") (pintype "passive"))
    )
    (net (code "3563") (name "unconnected-(SV106-Pad31)") (class "Default")
      (node (ref "SV106") (pin "31") (pinfunction "31_31") (pintype "passive"))
    )
    (net (code "3564") (name "unconnected-(SV106-Pad32)") (class "Default")
      (node (ref "SV106") (pin "32") (pinfunction "32_32") (pintype "passive"))
    )
    (net (code "3565") (name "unconnected-(SV106-Pad33)") (class "Default")
      (node (ref "SV106") (pin "33") (pinfunction "33_33") (pintype "passive"))
    )
    (net (code "3566") (name "unconnected-(SV106-Pad34)") (class "Default")
      (node (ref "SV106") (pin "34") (pinfunction "34_34") (pintype "passive"))
    )
    (net (code "3567") (name "unconnected-(SV106-Pad35)") (class "Default")
      (node (ref "SV106") (pin "35") (pinfunction "35_35") (pintype "passive"))
    )
    (net (code "3568") (name "unconnected-(SV106-Pad36)") (class "Default")
      (node (ref "SV106") (pin "36") (pinfunction "36_36") (pintype "passive"))
    )
    (net (code "3569") (name "unconnected-(SV107-Pad1)") (class "Default")
      (node (ref "SV107") (pin "1") (pinfunction "1_1") (pintype "passive"))
    )
    (net (code "3570") (name "unconnected-(SV107-Pad2)") (class "Default")
      (node (ref "SV107") (pin "2") (pinfunction "2_2") (pintype "passive"))
    )
    (net (code "3571") (name "unconnected-(SV107-Pad3)") (class "Default")
      (node (ref "SV107") (pin "3") (pinfunction "3_3") (pintype "passive"))
    )
    (net (code "3572") (name "unconnected-(SV107-Pad4)") (class "Default")
      (node (ref "SV107") (pin "4") (pinfunction "4_4") (pintype "passive"))
    )
    (net (code "3573") (name "unconnected-(SV107-Pad5)") (class "Default")
      (node (ref "SV107") (pin "5") (pinfunction "5_5") (pintype "passive"))
    )
    (net (code "3574") (name "unconnected-(SV107-Pad6)") (class "Default")
      (node (ref "SV107") (pin "6") (pinfunction "6_6") (pintype "passive"))
    )
    (net (code "3575") (name "unconnected-(SV107-Pad7)") (class "Default")
      (node (ref "SV107") (pin "7") (pinfunction "7_7") (pintype "passive"))
    )
    (net (code "3576") (name "unconnected-(SV107-Pad8)") (class "Default")
      (node (ref "SV107") (pin "8") (pinfunction "8_8") (pintype "passive"))
    )
    (net (code "3577") (name "unconnected-(SV107-Pad9)") (class "Default")
      (node (ref "SV107") (pin "9") (pinfunction "9_9") (pintype "passive"))
    )
    (net (code "3578") (name "unconnected-(SV107-Pad10)") (class "Default")
      (node (ref "SV107") (pin "10") (pinfunction "10_10") (pintype "passive"))
    )
    (net (code "3579") (name "unconnected-(SV107-Pad11)") (class "Default")
      (node (ref "SV107") (pin "11") (pinfunction "11_11") (pintype "passive"))
    )
    (net (code "3580") (name "unconnected-(SV107-Pad12)") (class "Default")
      (node (ref "SV107") (pin "12") (pinfunction "12_12") (pintype "passive"))
    )
    (net (code "3581") (name "unconnected-(SV107-Pad13)") (class "Default")
      (node (ref "SV107") (pin "13") (pinfunction "13_13") (pintype "passive"))
    )
    (net (code "3582") (name "unconnected-(SV107-Pad14)") (class "Default")
      (node (ref "SV107") (pin "14") (pinfunction "14_14") (pintype "passive"))
    )
    (net (code "3583") (name "unconnected-(SV107-Pad15)") (class "Default")
      (node (ref "SV107") (pin "15") (pinfunction "15_15") (pintype "passive"))
    )
    (net (code "3584") (name "unconnected-(SV107-Pad16)") (class "Default")
      (node (ref "SV107") (pin "16") (pinfunction "16_16") (pintype "passive"))
    )
    (net (code "3585") (name "unconnected-(SV107-Pad17)") (class "Default")
      (node (ref "SV107") (pin "17") (pinfunction "17_17") (pintype "passive"))
    )
    (net (code "3586") (name "unconnected-(SV107-Pad18)") (class "Default")
      (node (ref "SV107") (pin "18") (pinfunction "18_18") (pintype "passive"))
    )
    (net (code "3587") (name "unconnected-(SV107-Pad19)") (class "Default")
      (node (ref "SV107") (pin "19") (pinfunction "19_19") (pintype "passive"))
    )
    (net (code "3588") (name "unconnected-(SV107-Pad20)") (class "Default")
      (node (ref "SV107") (pin "20") (pinfunction "20_20") (pintype "passive"))
    )
    (net (code "3589") (name "unconnected-(SV107-Pad21)") (class "Default")
      (node (ref "SV107") (pin "21") (pinfunction "21_21") (pintype "passive"))
    )
    (net (code "3590") (name "unconnected-(SV107-Pad22)") (class "Default")
      (node (ref "SV107") (pin "22") (pinfunction "22_22") (pintype "passive"))
    )
    (net (code "3591") (name "unconnected-(SV107-Pad23)") (class "Default")
      (node (ref "SV107") (pin "23") (pinfunction "23_23") (pintype "passive"))
    )
    (net (code "3592") (name "unconnected-(SV107-Pad24)") (class "Default")
      (node (ref "SV107") (pin "24") (pinfunction "24_24") (pintype "passive"))
    )
    (net (code "3593") (name "unconnected-(SV107-Pad25)") (class "Default")
      (node (ref "SV107") (pin "25") (pinfunction "25_25") (pintype "passive"))
    )
    (net (code "3594") (name "unconnected-(SV107-Pad26)") (class "Default")
      (node (ref "SV107") (pin "26") (pinfunction "26_26") (pintype "passive"))
    )
    (net (code "3595") (name "unconnected-(SV107-Pad27)") (class "Default")
      (node (ref "SV107") (pin "27") (pinfunction "27_27") (pintype "passive"))
    )
    (net (code "3596") (name "unconnected-(SV107-Pad28)") (class "Default")
      (node (ref "SV107") (pin "28") (pinfunction "28_28") (pintype "passive"))
    )
    (net (code "3597") (name "unconnected-(SV107-Pad29)") (class "Default")
      (node (ref "SV107") (pin "29") (pinfunction "29_29") (pintype "passive"))
    )
    (net (code "3598") (name "unconnected-(SV107-Pad30)") (class "Default")
      (node (ref "SV107") (pin "30") (pinfunction "30_30") (pintype "passive"))
    )
    (net (code "3599") (name "unconnected-(SV107-Pad31)") (class "Default")
      (node (ref "SV107") (pin "31") (pinfunction "31_31") (pintype "passive"))
    )
    (net (code "3600") (name "unconnected-(SV107-Pad32)") (class "Default")
      (node (ref "SV107") (pin "32") (pinfunction "32_32") (pintype "passive"))
    )
    (net (code "3601") (name "unconnected-(SV107-Pad33)") (class "Default")
      (node (ref "SV107") (pin "33") (pinfunction "33_33") (pintype "passive"))
    )
    (net (code "3602") (name "unconnected-(SV107-Pad34)") (class "Default")
      (node (ref "SV107") (pin "34") (pinfunction "34_34") (pintype "passive"))
    )
    (net (code "3603") (name "unconnected-(SV107-Pad35)") (class "Default")
      (node (ref "SV107") (pin "35") (pinfunction "35_35") (pintype "passive"))
    )
    (net (code "3604") (name "unconnected-(SV107-Pad36)") (class "Default")
      (node (ref "SV107") (pin "36") (pinfunction "36_36") (pintype "passive"))
    )
    (net (code "3605") (name "unconnected-(SV108-Pad1)") (class "Default")
      (node (ref "SV108") (pin "1") (pinfunction "1_1") (pintype "passive"))
    )
    (net (code "3606") (name "unconnected-(SV108-Pad2)") (class "Default")
      (node (ref "SV108") (pin "2") (pinfunction "2_2") (pintype "passive"))
    )
    (net (code "3607") (name "unconnected-(SV108-Pad3)") (class "Default")
      (node (ref "SV108") (pin "3") (pinfunction "3_3") (pintype "passive"))
    )
    (net (code "3608") (name "unconnected-(SV108-Pad4)") (class "Default")
      (node (ref "SV108") (pin "4") (pinfunction "4_4") (pintype "passive"))
    )
    (net (code "3609") (name "unconnected-(SV108-Pad5)") (class "Default")
      (node (ref "SV108") (pin "5") (pinfunction "5_5") (pintype "passive"))
    )
    (net (code "3610") (name "unconnected-(SV108-Pad6)") (class "Default")
      (node (ref "SV108") (pin "6") (pinfunction "6_6") (pintype "passive"))
    )
    (net (code "3611") (name "unconnected-(SV108-Pad7)") (class "Default")
      (node (ref "SV108") (pin "7") (pinfunction "7_7") (pintype "passive"))
    )
    (net (code "3612") (name "unconnected-(SV108-Pad8)") (class "Default")
      (node (ref "SV108") (pin "8") (pinfunction "8_8") (pintype "passive"))
    )
    (net (code "3613") (name "unconnected-(SV108-Pad9)") (class "Default")
      (node (ref "SV108") (pin "9") (pinfunction "9_9") (pintype "passive"))
    )
    (net (code "3614") (name "unconnected-(SV108-Pad10)") (class "Default")
      (node (ref "SV108") (pin "10") (pinfunction "10_10") (pintype "passive"))
    )
    (net (code "3615") (name "unconnected-(SV108-Pad11)") (class "Default")
      (node (ref "SV108") (pin "11") (pinfunction "11_11") (pintype "passive"))
    )
    (net (code "3616") (name "unconnected-(SV108-Pad12)") (class "Default")
      (node (ref "SV108") (pin "12") (pinfunction "12_12") (pintype "passive"))
    )
    (net (code "3617") (name "unconnected-(SV108-Pad13)") (class "Default")
      (node (ref "SV108") (pin "13") (pinfunction "13_13") (pintype "passive"))
    )
    (net (code "3618") (name "unconnected-(SV108-Pad14)") (class "Default")
      (node (ref "SV108") (pin "14") (pinfunction "14_14") (pintype "passive"))
    )
    (net (code "3619") (name "unconnected-(SV108-Pad15)") (class "Default")
      (node (ref "SV108") (pin "15") (pinfunction "15_15") (pintype "passive"))
    )
    (net (code "3620") (name "unconnected-(SV108-Pad16)") (class "Default")
      (node (ref "SV108") (pin "16") (pinfunction "16_16") (pintype "passive"))
    )
    (net (code "3621") (name "unconnected-(SV108-Pad17)") (class "Default")
      (node (ref "SV108") (pin "17") (pinfunction "17_17") (pintype "passive"))
    )
    (net (code "3622") (name "unconnected-(SV108-Pad18)") (class "Default")
      (node (ref "SV108") (pin "18") (pinfunction "18_18") (pintype "passive"))
    )
    (net (code "3623") (name "unconnected-(SV108-Pad19)") (class "Default")
      (node (ref "SV108") (pin "19") (pinfunction "19_19") (pintype "passive"))
    )
    (net (code "3624") (name "unconnected-(SV108-Pad20)") (class "Default")
      (node (ref "SV108") (pin "20") (pinfunction "20_20") (pintype "passive"))
    )
    (net (code "3625") (name "unconnected-(SV108-Pad21)") (class "Default")
      (node (ref "SV108") (pin "21") (pinfunction "21_21") (pintype "passive"))
    )
    (net (code "3626") (name "unconnected-(SV108-Pad22)") (class "Default")
      (node (ref "SV108") (pin "22") (pinfunction "22_22") (pintype "passive"))
    )
    (net (code "3627") (name "unconnected-(SV108-Pad23)") (class "Default")
      (node (ref "SV108") (pin "23") (pinfunction "23_23") (pintype "passive"))
    )
    (net (code "3628") (name "unconnected-(SV108-Pad24)") (class "Default")
      (node (ref "SV108") (pin "24") (pinfunction "24_24") (pintype "passive"))
    )
    (net (code "3629") (name "unconnected-(SV108-Pad25)") (class "Default")
      (node (ref "SV108") (pin "25") (pinfunction "25_25") (pintype "passive"))
    )
    (net (code "3630") (name "unconnected-(SV108-Pad26)") (class "Default")
      (node (ref "SV108") (pin "26") (pinfunction "26_26") (pintype "passive"))
    )
    (net (code "3631") (name "unconnected-(SV108-Pad27)") (class "Default")
      (node (ref "SV108") (pin "27") (pinfunction "27_27") (pintype "passive"))
    )
    (net (code "3632") (name "unconnected-(SV108-Pad28)") (class "Default")
      (node (ref "SV108") (pin "28") (pinfunction "28_28") (pintype "passive"))
    )
    (net (code "3633") (name "unconnected-(SV108-Pad29)") (class "Default")
      (node (ref "SV108") (pin "29") (pinfunction "29_29") (pintype "passive"))
    )
    (net (code "3634") (name "unconnected-(SV108-Pad30)") (class "Default")
      (node (ref "SV108") (pin "30") (pinfunction "30_30") (pintype "passive"))
    )
    (net (code "3635") (name "unconnected-(SV108-Pad31)") (class "Default")
      (node (ref "SV108") (pin "31") (pinfunction "31_31") (pintype "passive"))
    )
    (net (code "3636") (name "unconnected-(SV108-Pad32)") (class "Default")
      (node (ref "SV108") (pin "32") (pinfunction "32_32") (pintype "passive"))
    )
    (net (code "3637") (name "unconnected-(SV108-Pad33)") (class "Default")
      (node (ref "SV108") (pin "33") (pinfunction "33_33") (pintype "passive"))
    )
    (net (code "3638") (name "unconnected-(SV108-Pad34)") (class "Default")
      (node (ref "SV108") (pin "34") (pinfunction "34_34") (pintype "passive"))
    )
    (net (code "3639") (name "unconnected-(SV108-Pad35)") (class "Default")
      (node (ref "SV108") (pin "35") (pinfunction "35_35") (pintype "passive"))
    )
    (net (code "3640") (name "unconnected-(SV108-Pad36)") (class "Default")
      (node (ref "SV108") (pin "36") (pinfunction "36_36") (pintype "passive"))
    )
    (net (code "3641") (name "unconnected-(SV109-Pad1)") (class "Default")
      (node (ref "SV109") (pin "1") (pinfunction "1_1") (pintype "passive"))
    )
    (net (code "3642") (name "unconnected-(SV109-Pad2)") (class "Default")
      (node (ref "SV109") (pin "2") (pinfunction "2_2") (pintype "passive"))
    )
    (net (code "3643") (name "unconnected-(SV109-Pad3)") (class "Default")
      (node (ref "SV109") (pin "3") (pinfunction "3_3") (pintype "passive"))
    )
    (net (code "3644") (name "unconnected-(SV109-Pad4)") (class "Default")
      (node (ref "SV109") (pin "4") (pinfunction "4_4") (pintype "passive"))
    )
    (net (code "3645") (name "unconnected-(SV109-Pad5)") (class "Default")
      (node (ref "SV109") (pin "5") (pinfunction "5_5") (pintype "passive"))
    )
    (net (code "3646") (name "unconnected-(SV109-Pad6)") (class "Default")
      (node (ref "SV109") (pin "6") (pinfunction "6_6") (pintype "passive"))
    )
    (net (code "3647") (name "unconnected-(SV109-Pad7)") (class "Default")
      (node (ref "SV109") (pin "7") (pinfunction "7_7") (pintype "passive"))
    )
    (net (code "3648") (name "unconnected-(SV109-Pad8)") (class "Default")
      (node (ref "SV109") (pin "8") (pinfunction "8_8") (pintype "passive"))
    )
    (net (code "3649") (name "unconnected-(SV109-Pad9)") (class "Default")
      (node (ref "SV109") (pin "9") (pinfunction "9_9") (pintype "passive"))
    )
    (net (code "3650") (name "unconnected-(SV109-Pad10)") (class "Default")
      (node (ref "SV109") (pin "10") (pinfunction "10_10") (pintype "passive"))
    )
    (net (code "3651") (name "unconnected-(SV109-Pad11)") (class "Default")
      (node (ref "SV109") (pin "11") (pinfunction "11_11") (pintype "passive"))
    )
    (net (code "3652") (name "unconnected-(SV109-Pad12)") (class "Default")
      (node (ref "SV109") (pin "12") (pinfunction "12_12") (pintype "passive"))
    )
    (net (code "3653") (name "unconnected-(SV109-Pad13)") (class "Default")
      (node (ref "SV109") (pin "13") (pinfunction "13_13") (pintype "passive"))
    )
    (net (code "3654") (name "unconnected-(SV109-Pad14)") (class "Default")
      (node (ref "SV109") (pin "14") (pinfunction "14_14") (pintype "passive"))
    )
    (net (code "3655") (name "unconnected-(SV109-Pad15)") (class "Default")
      (node (ref "SV109") (pin "15") (pinfunction "15_15") (pintype "passive"))
    )
    (net (code "3656") (name "unconnected-(SV109-Pad16)") (class "Default")
      (node (ref "SV109") (pin "16") (pinfunction "16_16") (pintype "passive"))
    )
    (net (code "3657") (name "unconnected-(SV109-Pad17)") (class "Default")
      (node (ref "SV109") (pin "17") (pinfunction "17_17") (pintype "passive"))
    )
    (net (code "3658") (name "unconnected-(SV109-Pad18)") (class "Default")
      (node (ref "SV109") (pin "18") (pinfunction "18_18") (pintype "passive"))
    )
    (net (code "3659") (name "unconnected-(SV109-Pad19)") (class "Default")
      (node (ref "SV109") (pin "19") (pinfunction "19_19") (pintype "passive"))
    )
    (net (code "3660") (name "unconnected-(SV109-Pad20)") (class "Default")
      (node (ref "SV109") (pin "20") (pinfunction "20_20") (pintype "passive"))
    )
    (net (code "3661") (name "unconnected-(SV109-Pad21)") (class "Default")
      (node (ref "SV109") (pin "21") (pinfunction "21_21") (pintype "passive"))
    )
    (net (code "3662") (name "unconnected-(SV109-Pad22)") (class "Default")
      (node (ref "SV109") (pin "22") (pinfunction "22_22") (pintype "passive"))
    )
    (net (code "3663") (name "unconnected-(SV109-Pad23)") (class "Default")
      (node (ref "SV109") (pin "23") (pinfunction "23_23") (pintype "passive"))
    )
    (net (code "3664") (name "unconnected-(SV109-Pad24)") (class "Default")
      (node (ref "SV109") (pin "24") (pinfunction "24_24") (pintype "passive"))
    )
    (net (code "3665") (name "unconnected-(SV109-Pad25)") (class "Default")
      (node (ref "SV109") (pin "25") (pinfunction "25_25") (pintype "passive"))
    )
    (net (code "3666") (name "unconnected-(SV109-Pad26)") (class "Default")
      (node (ref "SV109") (pin "26") (pinfunction "26_26") (pintype "passive"))
    )
    (net (code "3667") (name "unconnected-(SV109-Pad27)") (class "Default")
      (node (ref "SV109") (pin "27") (pinfunction "27_27") (pintype "passive"))
    )
    (net (code "3668") (name "unconnected-(SV109-Pad28)") (class "Default")
      (node (ref "SV109") (pin "28") (pinfunction "28_28") (pintype "passive"))
    )
    (net (code "3669") (name "unconnected-(SV109-Pad29)") (class "Default")
      (node (ref "SV109") (pin "29") (pinfunction "29_29") (pintype "passive"))
    )
    (net (code "3670") (name "unconnected-(SV109-Pad30)") (class "Default")
      (node (ref "SV109") (pin "30") (pinfunction "30_30") (pintype "passive"))
    )
    (net (code "3671") (name "unconnected-(SV109-Pad31)") (class "Default")
      (node (ref "SV109") (pin "31") (pinfunction "31_31") (pintype "passive"))
    )
    (net (code "3672") (name "unconnected-(SV109-Pad32)") (class "Default")
      (node (ref "SV109") (pin "32") (pinfunction "32_32") (pintype "passive"))
    )
    (net (code "3673") (name "unconnected-(SV109-Pad33)") (class "Default")
      (node (ref "SV109") (pin "33") (pinfunction "33_33") (pintype "passive"))
    )
    (net (code "3674") (name "unconnected-(SV109-Pad34)") (class "Default")
      (node (ref "SV109") (pin "34") (pinfunction "34_34") (pintype "passive"))
    )
    (net (code "3675") (name "unconnected-(SV109-Pad35)") (class "Default")
      (node (ref "SV109") (pin "35") (pinfunction "35_35") (pintype "passive"))
    )
    (net (code "3676") (name "unconnected-(SV109-Pad36)") (class "Default")
      (node (ref "SV109") (pin "36") (pinfunction "36_36") (pintype "passive"))
    )
    (net (code "3677") (name "unconnected-(SV110-Pad1)") (class "Default")
      (node (ref "SV110") (pin "1") (pinfunction "1_1") (pintype "passive"))
    )
    (net (code "3678") (name "unconnected-(SV110-Pad2)") (class "Default")
      (node (ref "SV110") (pin "2") (pinfunction "2_2") (pintype "passive"))
    )
    (net (code "3679") (name "unconnected-(SV110-Pad3)") (class "Default")
      (node (ref "SV110") (pin "3") (pinfunction "3_3") (pintype "passive"))
    )
    (net (code "3680") (name "unconnected-(SV110-Pad4)") (class "Default")
      (node (ref "SV110") (pin "4") (pinfunction "4_4") (pintype "passive"))
    )
    (net (code "3681") (name "unconnected-(SV110-Pad5)") (class "Default")
      (node (ref "SV110") (pin "5") (pinfunction "5_5") (pintype "passive"))
    )
    (net (code "3682") (name "unconnected-(SV110-Pad6)") (class "Default")
      (node (ref "SV110") (pin "6") (pinfunction "6_6") (pintype "passive"))
    )
    (net (code "3683") (name "unconnected-(SV110-Pad7)") (class "Default")
      (node (ref "SV110") (pin "7") (pinfunction "7_7") (pintype "passive"))
    )
    (net (code "3684") (name "unconnected-(SV110-Pad8)") (class "Default")
      (node (ref "SV110") (pin "8") (pinfunction "8_8") (pintype "passive"))
    )
    (net (code "3685") (name "unconnected-(SV110-Pad9)") (class "Default")
      (node (ref "SV110") (pin "9") (pinfunction "9_9") (pintype "passive"))
    )
    (net (code "3686") (name "unconnected-(SV110-Pad10)") (class "Default")
      (node (ref "SV110") (pin "10") (pinfunction "10_10") (pintype "passive"))
    )
    (net (code "3687") (name "unconnected-(SV110-Pad11)") (class "Default")
      (node (ref "SV110") (pin "11") (pinfunction "11_11") (pintype "passive"))
    )
    (net (code "3688") (name "unconnected-(SV110-Pad12)") (class "Default")
      (node (ref "SV110") (pin "12") (pinfunction "12_12") (pintype "passive"))
    )
    (net (code "3689") (name "unconnected-(SV110-Pad13)") (class "Default")
      (node (ref "SV110") (pin "13") (pinfunction "13_13") (pintype "passive"))
    )
    (net (code "3690") (name "unconnected-(SV110-Pad14)") (class "Default")
      (node (ref "SV110") (pin "14") (pinfunction "14_14") (pintype "passive"))
    )
    (net (code "3691") (name "unconnected-(SV110-Pad15)") (class "Default")
      (node (ref "SV110") (pin "15") (pinfunction "15_15") (pintype "passive"))
    )
    (net (code "3692") (name "unconnected-(SV110-Pad16)") (class "Default")
      (node (ref "SV110") (pin "16") (pinfunction "16_16") (pintype "passive"))
    )
    (net (code "3693") (name "unconnected-(SV110-Pad17)") (class "Default")
      (node (ref "SV110") (pin "17") (pinfunction "17_17") (pintype "passive"))
    )
    (net (code "3694") (name "unconnected-(SV110-Pad18)") (class "Default")
      (node (ref "SV110") (pin "18") (pinfunction "18_18") (pintype "passive"))
    )
    (net (code "3695") (name "unconnected-(SV110-Pad19)") (class "Default")
      (node (ref "SV110") (pin "19") (pinfunction "19_19") (pintype "passive"))
    )
    (net (code "3696") (name "unconnected-(SV110-Pad20)") (class "Default")
      (node (ref "SV110") (pin "20") (pinfunction "20_20") (pintype "passive"))
    )
    (net (code "3697") (name "unconnected-(SV110-Pad21)") (class "Default")
      (node (ref "SV110") (pin "21") (pinfunction "21_21") (pintype "passive"))
    )
    (net (code "3698") (name "unconnected-(SV110-Pad22)") (class "Default")
      (node (ref "SV110") (pin "22") (pinfunction "22_22") (pintype "passive"))
    )
    (net (code "3699") (name "unconnected-(SV110-Pad23)") (class "Default")
      (node (ref "SV110") (pin "23") (pinfunction "23_23") (pintype "passive"))
    )
    (net (code "3700") (name "unconnected-(SV110-Pad24)") (class "Default")
      (node (ref "SV110") (pin "24") (pinfunction "24_24") (pintype "passive"))
    )
    (net (code "3701") (name "unconnected-(SV110-Pad25)") (class "Default")
      (node (ref "SV110") (pin "25") (pinfunction "25_25") (pintype "passive"))
    )
    (net (code "3702") (name "unconnected-(SV110-Pad26)") (class "Default")
      (node (ref "SV110") (pin "26") (pinfunction "26_26") (pintype "passive"))
    )
    (net (code "3703") (name "unconnected-(SV110-Pad27)") (class "Default")
      (node (ref "SV110") (pin "27") (pinfunction "27_27") (pintype "passive"))
    )
    (net (code "3704") (name "unconnected-(SV110-Pad28)") (class "Default")
      (node (ref "SV110") (pin "28") (pinfunction "28_28") (pintype "passive"))
    )
    (net (code "3705") (name "unconnected-(SV110-Pad29)") (class "Default")
      (node (ref "SV110") (pin "29") (pinfunction "29_29") (pintype "passive"))
    )
    (net (code "3706") (name "unconnected-(SV110-Pad30)") (class "Default")
      (node (ref "SV110") (pin "30") (pinfunction "30_30") (pintype "passive"))
    )
    (net (code "3707") (name "unconnected-(SV110-Pad31)") (class "Default")
      (node (ref "SV110") (pin "31") (pinfunction "31_31") (pintype "passive"))
    )
    (net (code "3708") (name "unconnected-(SV110-Pad32)") (class "Default")
      (node (ref "SV110") (pin "32") (pinfunction "32_32") (pintype "passive"))
    )
    (net (code "3709") (name "unconnected-(SV110-Pad33)") (class "Default")
      (node (ref "SV110") (pin "33") (pinfunction "33_33") (pintype "passive"))
    )
    (net (code "3710") (name "unconnected-(SV110-Pad34)") (class "Default")
      (node (ref "SV110") (pin "34") (pinfunction "34_34") (pintype "passive"))
    )
    (net (code "3711") (name "unconnected-(SV110-Pad35)") (class "Default")
      (node (ref "SV110") (pin "35") (pinfunction "35_35") (pintype "passive"))
    )
    (net (code "3712") (name "unconnected-(SV110-Pad36)") (class "Default")
      (node (ref "SV110") (pin "36") (pinfunction "36_36") (pintype "passive"))
    )
    (net (code "3713") (name "unconnected-(SV110-Pad37)") (class "Default")
      (node (ref "SV110") (pin "37") (pinfunction "37_37") (pintype "passive"))
    )
    (net (code "3714") (name "unconnected-(SV110-Pad38)") (class "Default")
      (node (ref "SV110") (pin "38") (pinfunction "38_38") (pintype "passive"))
    )
    (net (code "3715") (name "unconnected-(SV110-Pad39)") (class "Default")
      (node (ref "SV110") (pin "39") (pinfunction "39_39") (pintype "passive"))
    )
    (net (code "3716") (name "unconnected-(SV110-Pad40)") (class "Default")
      (node (ref "SV110") (pin "40") (pinfunction "40_40") (pintype "passive"))
    )
    (net (code "3717") (name "unconnected-(SV111-Pad1)") (class "Default")
      (node (ref "SV111") (pin "1") (pinfunction "1_1") (pintype "passive"))
    )
    (net (code "3718") (name "unconnected-(SV111-Pad2)") (class "Default")
      (node (ref "SV111") (pin "2") (pinfunction "2_2") (pintype "passive"))
    )
    (net (code "3719") (name "unconnected-(SV111-Pad3)") (class "Default")
      (node (ref "SV111") (pin "3") (pinfunction "3_3") (pintype "passive"))
    )
    (net (code "3720") (name "unconnected-(SV111-Pad4)") (class "Default")
      (node (ref "SV111") (pin "4") (pinfunction "4_4") (pintype "passive"))
    )
    (net (code "3721") (name "unconnected-(SV111-Pad5)") (class "Default")
      (node (ref "SV111") (pin "5") (pinfunction "5_5") (pintype "passive"))
    )
    (net (code "3722") (name "unconnected-(SV111-Pad6)") (class "Default")
      (node (ref "SV111") (pin "6") (pinfunction "6_6") (pintype "passive"))
    )
    (net (code "3723") (name "unconnected-(SV111-Pad7)") (class "Default")
      (node (ref "SV111") (pin "7") (pinfunction "7_7") (pintype "passive"))
    )
    (net (code "3724") (name "unconnected-(SV111-Pad8)") (class "Default")
      (node (ref "SV111") (pin "8") (pinfunction "8_8") (pintype "passive"))
    )
    (net (code "3725") (name "unconnected-(SV111-Pad9)") (class "Default")
      (node (ref "SV111") (pin "9") (pinfunction "9_9") (pintype "passive"))
    )
    (net (code "3726") (name "unconnected-(SV111-Pad10)") (class "Default")
      (node (ref "SV111") (pin "10") (pinfunction "10_10") (pintype "passive"))
    )
    (net (code "3727") (name "unconnected-(SV111-Pad11)") (class "Default")
      (node (ref "SV111") (pin "11") (pinfunction "11_11") (pintype "passive"))
    )
    (net (code "3728") (name "unconnected-(SV111-Pad12)") (class "Default")
      (node (ref "SV111") (pin "12") (pinfunction "12_12") (pintype "passive"))
    )
    (net (code "3729") (name "unconnected-(SV111-Pad13)") (class "Default")
      (node (ref "SV111") (pin "13") (pinfunction "13_13") (pintype "passive"))
    )
    (net (code "3730") (name "unconnected-(SV111-Pad14)") (class "Default")
      (node (ref "SV111") (pin "14") (pinfunction "14_14") (pintype "passive"))
    )
    (net (code "3731") (name "unconnected-(SV111-Pad15)") (class "Default")
      (node (ref "SV111") (pin "15") (pinfunction "15_15") (pintype "passive"))
    )
    (net (code "3732") (name "unconnected-(SV111-Pad16)") (class "Default")
      (node (ref "SV111") (pin "16") (pinfunction "16_16") (pintype "passive"))
    )
    (net (code "3733") (name "unconnected-(SV111-Pad17)") (class "Default")
      (node (ref "SV111") (pin "17") (pinfunction "17_17") (pintype "passive"))
    )
    (net (code "3734") (name "unconnected-(SV111-Pad18)") (class "Default")
      (node (ref "SV111") (pin "18") (pinfunction "18_18") (pintype "passive"))
    )
    (net (code "3735") (name "unconnected-(SV111-Pad19)") (class "Default")
      (node (ref "SV111") (pin "19") (pinfunction "19_19") (pintype "passive"))
    )
    (net (code "3736") (name "unconnected-(SV111-Pad20)") (class "Default")
      (node (ref "SV111") (pin "20") (pinfunction "20_20") (pintype "passive"))
    )
    (net (code "3737") (name "unconnected-(SV111-Pad21)") (class "Default")
      (node (ref "SV111") (pin "21") (pinfunction "21_21") (pintype "passive"))
    )
    (net (code "3738") (name "unconnected-(SV111-Pad22)") (class "Default")
      (node (ref "SV111") (pin "22") (pinfunction "22_22") (pintype "passive"))
    )
    (net (code "3739") (name "unconnected-(SV111-Pad23)") (class "Default")
      (node (ref "SV111") (pin "23") (pinfunction "23_23") (pintype "passive"))
    )
    (net (code "3740") (name "unconnected-(SV111-Pad24)") (class "Default")
      (node (ref "SV111") (pin "24") (pinfunction "24_24") (pintype "passive"))
    )
    (net (code "3741") (name "unconnected-(SV111-Pad25)") (class "Default")
      (node (ref "SV111") (pin "25") (pinfunction "25_25") (pintype "passive"))
    )
    (net (code "3742") (name "unconnected-(SV111-Pad26)") (class "Default")
      (node (ref "SV111") (pin "26") (pinfunction "26_26") (pintype "passive"))
    )
    (net (code "3743") (name "unconnected-(SV111-Pad27)") (class "Default")
      (node (ref "SV111") (pin "27") (pinfunction "27_27") (pintype "passive"))
    )
    (net (code "3744") (name "unconnected-(SV111-Pad28)") (class "Default")
      (node (ref "SV111") (pin "28") (pinfunction "28_28") (pintype "passive"))
    )
    (net (code "3745") (name "unconnected-(SV111-Pad29)") (class "Default")
      (node (ref "SV111") (pin "29") (pinfunction "29_29") (pintype "passive"))
    )
    (net (code "3746") (name "unconnected-(SV111-Pad30)") (class "Default")
      (node (ref "SV111") (pin "30") (pinfunction "30_30") (pintype "passive"))
    )
    (net (code "3747") (name "unconnected-(SV111-Pad31)") (class "Default")
      (node (ref "SV111") (pin "31") (pinfunction "31_31") (pintype "passive"))
    )
    (net (code "3748") (name "unconnected-(SV111-Pad32)") (class "Default")
      (node (ref "SV111") (pin "32") (pinfunction "32_32") (pintype "passive"))
    )
    (net (code "3749") (name "unconnected-(SV111-Pad33)") (class "Default")
      (node (ref "SV111") (pin "33") (pinfunction "33_33") (pintype "passive"))
    )
    (net (code "3750") (name "unconnected-(SV111-Pad34)") (class "Default")
      (node (ref "SV111") (pin "34") (pinfunction "34_34") (pintype "passive"))
    )
    (net (code "3751") (name "unconnected-(SV111-Pad35)") (class "Default")
      (node (ref "SV111") (pin "35") (pinfunction "35_35") (pintype "passive"))
    )
    (net (code "3752") (name "unconnected-(SV111-Pad36)") (class "Default")
      (node (ref "SV111") (pin "36") (pinfunction "36_36") (pintype "passive"))
    )
    (net (code "3753") (name "unconnected-(SV111-Pad37)") (class "Default")
      (node (ref "SV111") (pin "37") (pinfunction "37_37") (pintype "passive"))
    )
    (net (code "3754") (name "unconnected-(SV111-Pad38)") (class "Default")
      (node (ref "SV111") (pin "38") (pinfunction "38_38") (pintype "passive"))
    )
    (net (code "3755") (name "unconnected-(SV111-Pad39)") (class "Default")
      (node (ref "SV111") (pin "39") (pinfunction "39_39") (pintype "passive"))
    )
    (net (code "3756") (name "unconnected-(SV111-Pad40)") (class "Default")
      (node (ref "SV111") (pin "40") (pinfunction "40_40") (pintype "passive"))
    )
    (net (code "3757") (name "unconnected-(SV112-Pad1)") (class "Default")
      (node (ref "SV112") (pin "1") (pinfunction "1_1") (pintype "passive"))
    )
    (net (code "3758") (name "unconnected-(SV112-Pad2)") (class "Default")
      (node (ref "SV112") (pin "2") (pinfunction "2_2") (pintype "passive"))
    )
    (net (code "3759") (name "unconnected-(SV112-Pad3)") (class "Default")
      (node (ref "SV112") (pin "3") (pinfunction "3_3") (pintype "passive"))
    )
    (net (code "3760") (name "unconnected-(SV112-Pad4)") (class "Default")
      (node (ref "SV112") (pin "4") (pinfunction "4_4") (pintype "passive"))
    )
    (net (code "3761") (name "unconnected-(SV112-Pad5)") (class "Default")
      (node (ref "SV112") (pin "5") (pinfunction "5_5") (pintype "passive"))
    )
    (net (code "3762") (name "unconnected-(SV112-Pad6)") (class "Default")
      (node (ref "SV112") (pin "6") (pinfunction "6_6") (pintype "passive"))
    )
    (net (code "3763") (name "unconnected-(SV112-Pad7)") (class "Default")
      (node (ref "SV112") (pin "7") (pinfunction "7_7") (pintype "passive"))
    )
    (net (code "3764") (name "unconnected-(SV112-Pad8)") (class "Default")
      (node (ref "SV112") (pin "8") (pinfunction "8_8") (pintype "passive"))
    )
    (net (code "3765") (name "unconnected-(SV112-Pad9)") (class "Default")
      (node (ref "SV112") (pin "9") (pinfunction "9_9") (pintype "passive"))
    )
    (net (code "3766") (name "unconnected-(SV112-Pad10)") (class "Default")
      (node (ref "SV112") (pin "10") (pinfunction "10_10") (pintype "passive"))
    )
    (net (code "3767") (name "unconnected-(SV112-Pad11)") (class "Default")
      (node (ref "SV112") (pin "11") (pinfunction "11_11") (pintype "passive"))
    )
    (net (code "3768") (name "unconnected-(SV112-Pad12)") (class "Default")
      (node (ref "SV112") (pin "12") (pinfunction "12_12") (pintype "passive"))
    )
    (net (code "3769") (name "unconnected-(SV112-Pad13)") (class "Default")
      (node (ref "SV112") (pin "13") (pinfunction "13_13") (pintype "passive"))
    )
    (net (code "3770") (name "unconnected-(SV112-Pad14)") (class "Default")
      (node (ref "SV112") (pin "14") (pinfunction "14_14") (pintype "passive"))
    )
    (net (code "3771") (name "unconnected-(SV112-Pad15)") (class "Default")
      (node (ref "SV112") (pin "15") (pinfunction "15_15") (pintype "passive"))
    )
    (net (code "3772") (name "unconnected-(SV112-Pad16)") (class "Default")
      (node (ref "SV112") (pin "16") (pinfunction "16_16") (pintype "passive"))
    )
    (net (code "3773") (name "unconnected-(SV112-Pad17)") (class "Default")
      (node (ref "SV112") (pin "17") (pinfunction "17_17") (pintype "passive"))
    )
    (net (code "3774") (name "unconnected-(SV112-Pad18)") (class "Default")
      (node (ref "SV112") (pin "18") (pinfunction "18_18") (pintype "passive"))
    )
    (net (code "3775") (name "unconnected-(SV112-Pad19)") (class "Default")
      (node (ref "SV112") (pin "19") (pinfunction "19_19") (pintype "passive"))
    )
    (net (code "3776") (name "unconnected-(SV112-Pad20)") (class "Default")
      (node (ref "SV112") (pin "20") (pinfunction "20_20") (pintype "passive"))
    )
    (net (code "3777") (name "unconnected-(SV112-Pad21)") (class "Default")
      (node (ref "SV112") (pin "21") (pinfunction "21_21") (pintype "passive"))
    )
    (net (code "3778") (name "unconnected-(SV112-Pad22)") (class "Default")
      (node (ref "SV112") (pin "22") (pinfunction "22_22") (pintype "passive"))
    )
    (net (code "3779") (name "unconnected-(SV112-Pad23)") (class "Default")
      (node (ref "SV112") (pin "23") (pinfunction "23_23") (pintype "passive"))
    )
    (net (code "3780") (name "unconnected-(SV112-Pad24)") (class "Default")
      (node (ref "SV112") (pin "24") (pinfunction "24_24") (pintype "passive"))
    )
    (net (code "3781") (name "unconnected-(SV112-Pad25)") (class "Default")
      (node (ref "SV112") (pin "25") (pinfunction "25_25") (pintype "passive"))
    )
    (net (code "3782") (name "unconnected-(SV112-Pad26)") (class "Default")
      (node (ref "SV112") (pin "26") (pinfunction "26_26") (pintype "passive"))
    )
    (net (code "3783") (name "unconnected-(SV112-Pad27)") (class "Default")
      (node (ref "SV112") (pin "27") (pinfunction "27_27") (pintype "passive"))
    )
    (net (code "3784") (name "unconnected-(SV112-Pad28)") (class "Default")
      (node (ref "SV112") (pin "28") (pinfunction "28_28") (pintype "passive"))
    )
    (net (code "3785") (name "unconnected-(SV112-Pad29)") (class "Default")
      (node (ref "SV112") (pin "29") (pinfunction "29_29") (pintype "passive"))
    )
    (net (code "3786") (name "unconnected-(SV112-Pad30)") (class "Default")
      (node (ref "SV112") (pin "30") (pinfunction "30_30") (pintype "passive"))
    )
    (net (code "3787") (name "unconnected-(SV112-Pad31)") (class "Default")
      (node (ref "SV112") (pin "31") (pinfunction "31_31") (pintype "passive"))
    )
    (net (code "3788") (name "unconnected-(SV112-Pad32)") (class "Default")
      (node (ref "SV112") (pin "32") (pinfunction "32_32") (pintype "passive"))
    )
    (net (code "3789") (name "unconnected-(SV112-Pad33)") (class "Default")
      (node (ref "SV112") (pin "33") (pinfunction "33_33") (pintype "passive"))
    )
    (net (code "3790") (name "unconnected-(SV112-Pad34)") (class "Default")
      (node (ref "SV112") (pin "34") (pinfunction "34_34") (pintype "passive"))
    )
    (net (code "3791") (name "unconnected-(SV112-Pad35)") (class "Default")
      (node (ref "SV112") (pin "35") (pinfunction "35_35") (pintype "passive"))
    )
    (net (code "3792") (name "unconnected-(SV112-Pad36)") (class "Default")
      (node (ref "SV112") (pin "36") (pinfunction "36_36") (pintype "passive"))
    )
    (net (code "3793") (name "unconnected-(SV112-Pad37)") (class "Default")
      (node (ref "SV112") (pin "37") (pinfunction "37_37") (pintype "passive"))
    )
    (net (code "3794") (name "unconnected-(SV112-Pad38)") (class "Default")
      (node (ref "SV112") (pin "38") (pinfunction "38_38") (pintype "passive"))
    )
    (net (code "3795") (name "unconnected-(SV112-Pad39)") (class "Default")
      (node (ref "SV112") (pin "39") (pinfunction "39_39") (pintype "passive"))
    )
    (net (code "3796") (name "unconnected-(SV112-Pad40)") (class "Default")
      (node (ref "SV112") (pin "40") (pinfunction "40_40") (pintype "passive"))
    )
    (net (code "3797") (name "unconnected-(SV113-Pad1)") (class "Default")
      (node (ref "SV113") (pin "1") (pinfunction "1_1") (pintype "passive"))
    )
    (net (code "3798") (name "unconnected-(SV113-Pad2)") (class "Default")
      (node (ref "SV113") (pin "2") (pinfunction "2_2") (pintype "passive"))
    )
    (net (code "3799") (name "unconnected-(SV113-Pad3)") (class "Default")
      (node (ref "SV113") (pin "3") (pinfunction "3_3") (pintype "passive"))
    )
    (net (code "3800") (name "unconnected-(SV113-Pad4)") (class "Default")
      (node (ref "SV113") (pin "4") (pinfunction "4_4") (pintype "passive"))
    )
    (net (code "3801") (name "unconnected-(SV113-Pad5)") (class "Default")
      (node (ref "SV113") (pin "5") (pinfunction "5_5") (pintype "passive"))
    )
    (net (code "3802") (name "unconnected-(SV113-Pad6)") (class "Default")
      (node (ref "SV113") (pin "6") (pinfunction "6_6") (pintype "passive"))
    )
    (net (code "3803") (name "unconnected-(SV113-Pad7)") (class "Default")
      (node (ref "SV113") (pin "7") (pinfunction "7_7") (pintype "passive"))
    )
    (net (code "3804") (name "unconnected-(SV113-Pad8)") (class "Default")
      (node (ref "SV113") (pin "8") (pinfunction "8_8") (pintype "passive"))
    )
    (net (code "3805") (name "unconnected-(SV113-Pad9)") (class "Default")
      (node (ref "SV113") (pin "9") (pinfunction "9_9") (pintype "passive"))
    )
    (net (code "3806") (name "unconnected-(SV113-Pad10)") (class "Default")
      (node (ref "SV113") (pin "10") (pinfunction "10_10") (pintype "passive"))
    )
    (net (code "3807") (name "unconnected-(SV113-Pad11)") (class "Default")
      (node (ref "SV113") (pin "11") (pinfunction "11_11") (pintype "passive"))
    )
    (net (code "3808") (name "unconnected-(SV113-Pad12)") (class "Default")
      (node (ref "SV113") (pin "12") (pinfunction "12_12") (pintype "passive"))
    )
    (net (code "3809") (name "unconnected-(SV113-Pad13)") (class "Default")
      (node (ref "SV113") (pin "13") (pinfunction "13_13") (pintype "passive"))
    )
    (net (code "3810") (name "unconnected-(SV113-Pad14)") (class "Default")
      (node (ref "SV113") (pin "14") (pinfunction "14_14") (pintype "passive"))
    )
    (net (code "3811") (name "unconnected-(SV113-Pad15)") (class "Default")
      (node (ref "SV113") (pin "15") (pinfunction "15_15") (pintype "passive"))
    )
    (net (code "3812") (name "unconnected-(SV113-Pad16)") (class "Default")
      (node (ref "SV113") (pin "16") (pinfunction "16_16") (pintype "passive"))
    )
    (net (code "3813") (name "unconnected-(SV113-Pad17)") (class "Default")
      (node (ref "SV113") (pin "17") (pinfunction "17_17") (pintype "passive"))
    )
    (net (code "3814") (name "unconnected-(SV113-Pad18)") (class "Default")
      (node (ref "SV113") (pin "18") (pinfunction "18_18") (pintype "passive"))
    )
    (net (code "3815") (name "unconnected-(SV113-Pad19)") (class "Default")
      (node (ref "SV113") (pin "19") (pinfunction "19_19") (pintype "passive"))
    )
    (net (code "3816") (name "unconnected-(SV113-Pad20)") (class "Default")
      (node (ref "SV113") (pin "20") (pinfunction "20_20") (pintype "passive"))
    )
    (net (code "3817") (name "unconnected-(SV113-Pad21)") (class "Default")
      (node (ref "SV113") (pin "21") (pinfunction "21_21") (pintype "passive"))
    )
    (net (code "3818") (name "unconnected-(SV113-Pad22)") (class "Default")
      (node (ref "SV113") (pin "22") (pinfunction "22_22") (pintype "passive"))
    )
    (net (code "3819") (name "unconnected-(SV113-Pad23)") (class "Default")
      (node (ref "SV113") (pin "23") (pinfunction "23_23") (pintype "passive"))
    )
    (net (code "3820") (name "unconnected-(SV113-Pad24)") (class "Default")
      (node (ref "SV113") (pin "24") (pinfunction "24_24") (pintype "passive"))
    )
    (net (code "3821") (name "unconnected-(SV113-Pad25)") (class "Default")
      (node (ref "SV113") (pin "25") (pinfunction "25_25") (pintype "passive"))
    )
    (net (code "3822") (name "unconnected-(SV113-Pad26)") (class "Default")
      (node (ref "SV113") (pin "26") (pinfunction "26_26") (pintype "passive"))
    )
    (net (code "3823") (name "unconnected-(SV113-Pad27)") (class "Default")
      (node (ref "SV113") (pin "27") (pinfunction "27_27") (pintype "passive"))
    )
    (net (code "3824") (name "unconnected-(SV113-Pad28)") (class "Default")
      (node (ref "SV113") (pin "28") (pinfunction "28_28") (pintype "passive"))
    )
    (net (code "3825") (name "unconnected-(SV113-Pad29)") (class "Default")
      (node (ref "SV113") (pin "29") (pinfunction "29_29") (pintype "passive"))
    )
    (net (code "3826") (name "unconnected-(SV113-Pad30)") (class "Default")
      (node (ref "SV113") (pin "30") (pinfunction "30_30") (pintype "passive"))
    )
    (net (code "3827") (name "unconnected-(SV113-Pad31)") (class "Default")
      (node (ref "SV113") (pin "31") (pinfunction "31_31") (pintype "passive"))
    )
    (net (code "3828") (name "unconnected-(SV113-Pad32)") (class "Default")
      (node (ref "SV113") (pin "32") (pinfunction "32_32") (pintype "passive"))
    )
    (net (code "3829") (name "unconnected-(SV113-Pad33)") (class "Default")
      (node (ref "SV113") (pin "33") (pinfunction "33_33") (pintype "passive"))
    )
    (net (code "3830") (name "unconnected-(SV113-Pad34)") (class "Default")
      (node (ref "SV113") (pin "34") (pinfunction "34_34") (pintype "passive"))
    )
    (net (code "3831") (name "unconnected-(SV113-Pad35)") (class "Default")
      (node (ref "SV113") (pin "35") (pinfunction "35_35") (pintype "passive"))
    )
    (net (code "3832") (name "unconnected-(SV113-Pad36)") (class "Default")
      (node (ref "SV113") (pin "36") (pinfunction "36_36") (pintype "passive"))
    )
    (net (code "3833") (name "unconnected-(SV113-Pad37)") (class "Default")
      (node (ref "SV113") (pin "37") (pinfunction "37_37") (pintype "passive"))
    )
    (net (code "3834") (name "unconnected-(SV113-Pad38)") (class "Default")
      (node (ref "SV113") (pin "38") (pinfunction "38_38") (pintype "passive"))
    )
    (net (code "3835") (name "unconnected-(SV113-Pad39)") (class "Default")
      (node (ref "SV113") (pin "39") (pinfunction "39_39") (pintype "passive"))
    )
    (net (code "3836") (name "unconnected-(SV113-Pad40)") (class "Default")
      (node (ref "SV113") (pin "40") (pinfunction "40_40") (pintype "passive"))
    )
    (net (code "3837") (name "unconnected-(SV114-Pad1)") (class "Default")
      (node (ref "SV114") (pin "1") (pinfunction "1_1") (pintype "passive"))
    )
    (net (code "3838") (name "unconnected-(SV114-Pad2)") (class "Default")
      (node (ref "SV114") (pin "2") (pinfunction "2_2") (pintype "passive"))
    )
    (net (code "3839") (name "unconnected-(SV114-Pad3)") (class "Default")
      (node (ref "SV114") (pin "3") (pinfunction "3_3") (pintype "passive"))
    )
    (net (code "3840") (name "unconnected-(SV114-Pad4)") (class "Default")
      (node (ref "SV114") (pin "4") (pinfunction "4_4") (pintype "passive"))
    )
    (net (code "3841") (name "unconnected-(SV114-Pad5)") (class "Default")
      (node (ref "SV114") (pin "5") (pinfunction "5_5") (pintype "passive"))
    )
    (net (code "3842") (name "unconnected-(SV114-Pad6)") (class "Default")
      (node (ref "SV114") (pin "6") (pinfunction "6_6") (pintype "passive"))
    )
    (net (code "3843") (name "unconnected-(SV114-Pad7)") (class "Default")
      (node (ref "SV114") (pin "7") (pinfunction "7_7") (pintype "passive"))
    )
    (net (code "3844") (name "unconnected-(SV114-Pad8)") (class "Default")
      (node (ref "SV114") (pin "8") (pinfunction "8_8") (pintype "passive"))
    )
    (net (code "3845") (name "unconnected-(SV114-Pad9)") (class "Default")
      (node (ref "SV114") (pin "9") (pinfunction "9_9") (pintype "passive"))
    )
    (net (code "3846") (name "unconnected-(SV114-Pad10)") (class "Default")
      (node (ref "SV114") (pin "10") (pinfunction "10_10") (pintype "passive"))
    )
    (net (code "3847") (name "unconnected-(SV114-Pad11)") (class "Default")
      (node (ref "SV114") (pin "11") (pinfunction "11_11") (pintype "passive"))
    )
    (net (code "3848") (name "unconnected-(SV114-Pad12)") (class "Default")
      (node (ref "SV114") (pin "12") (pinfunction "12_12") (pintype "passive"))
    )
    (net (code "3849") (name "unconnected-(SV114-Pad13)") (class "Default")
      (node (ref "SV114") (pin "13") (pinfunction "13_13") (pintype "passive"))
    )
    (net (code "3850") (name "unconnected-(SV114-Pad14)") (class "Default")
      (node (ref "SV114") (pin "14") (pinfunction "14_14") (pintype "passive"))
    )
    (net (code "3851") (name "unconnected-(SV114-Pad15)") (class "Default")
      (node (ref "SV114") (pin "15") (pinfunction "15_15") (pintype "passive"))
    )
    (net (code "3852") (name "unconnected-(SV114-Pad16)") (class "Default")
      (node (ref "SV114") (pin "16") (pinfunction "16_16") (pintype "passive"))
    )
    (net (code "3853") (name "unconnected-(SV114-Pad17)") (class "Default")
      (node (ref "SV114") (pin "17") (pinfunction "17_17") (pintype "passive"))
    )
    (net (code "3854") (name "unconnected-(SV114-Pad18)") (class "Default")
      (node (ref "SV114") (pin "18") (pinfunction "18_18") (pintype "passive"))
    )
    (net (code "3855") (name "unconnected-(SV114-Pad19)") (class "Default")
      (node (ref "SV114") (pin "19") (pinfunction "19_19") (pintype "passive"))
    )
    (net (code "3856") (name "unconnected-(SV114-Pad20)") (class "Default")
      (node (ref "SV114") (pin "20") (pinfunction "20_20") (pintype "passive"))
    )
    (net (code "3857") (name "unconnected-(SV114-Pad21)") (class "Default")
      (node (ref "SV114") (pin "21") (pinfunction "21_21") (pintype "passive"))
    )
    (net (code "3858") (name "unconnected-(SV114-Pad22)") (class "Default")
      (node (ref "SV114") (pin "22") (pinfunction "22_22") (pintype "passive"))
    )
    (net (code "3859") (name "unconnected-(SV114-Pad23)") (class "Default")
      (node (ref "SV114") (pin "23") (pinfunction "23_23") (pintype "passive"))
    )
    (net (code "3860") (name "unconnected-(SV114-Pad24)") (class "Default")
      (node (ref "SV114") (pin "24") (pinfunction "24_24") (pintype "passive"))
    )
    (net (code "3861") (name "unconnected-(SV114-Pad25)") (class "Default")
      (node (ref "SV114") (pin "25") (pinfunction "25_25") (pintype "passive"))
    )
    (net (code "3862") (name "unconnected-(SV114-Pad26)") (class "Default")
      (node (ref "SV114") (pin "26") (pinfunction "26_26") (pintype "passive"))
    )
    (net (code "3863") (name "unconnected-(SV114-Pad27)") (class "Default")
      (node (ref "SV114") (pin "27") (pinfunction "27_27") (pintype "passive"))
    )
    (net (code "3864") (name "unconnected-(SV114-Pad28)") (class "Default")
      (node (ref "SV114") (pin "28") (pinfunction "28_28") (pintype "passive"))
    )
    (net (code "3865") (name "unconnected-(SV114-Pad29)") (class "Default")
      (node (ref "SV114") (pin "29") (pinfunction "29_29") (pintype "passive"))
    )
    (net (code "3866") (name "unconnected-(SV114-Pad30)") (class "Default")
      (node (ref "SV114") (pin "30") (pinfunction "30_30") (pintype "passive"))
    )
    (net (code "3867") (name "unconnected-(SV114-Pad31)") (class "Default")
      (node (ref "SV114") (pin "31") (pinfunction "31_31") (pintype "passive"))
    )
    (net (code "3868") (name "unconnected-(SV114-Pad32)") (class "Default")
      (node (ref "SV114") (pin "32") (pinfunction "32_32") (pintype "passive"))
    )
    (net (code "3869") (name "unconnected-(SV114-Pad33)") (class "Default")
      (node (ref "SV114") (pin "33") (pinfunction "33_33") (pintype "passive"))
    )
    (net (code "3870") (name "unconnected-(SV114-Pad34)") (class "Default")
      (node (ref "SV114") (pin "34") (pinfunction "34_34") (pintype "passive"))
    )
    (net (code "3871") (name "unconnected-(SV114-Pad35)") (class "Default")
      (node (ref "SV114") (pin "35") (pinfunction "35_35") (pintype "passive"))
    )
    (net (code "3872") (name "unconnected-(SV114-Pad36)") (class "Default")
      (node (ref "SV114") (pin "36") (pinfunction "36_36") (pintype "passive"))
    )
    (net (code "3873") (name "unconnected-(SV115-Pad1)") (class "Default")
      (node (ref "SV115") (pin "1") (pinfunction "1_1") (pintype "passive"))
    )
    (net (code "3874") (name "unconnected-(SV115-Pad2)") (class "Default")
      (node (ref "SV115") (pin "2") (pinfunction "2_2") (pintype "passive"))
    )
    (net (code "3875") (name "unconnected-(SV115-Pad3)") (class "Default")
      (node (ref "SV115") (pin "3") (pinfunction "3_3") (pintype "passive"))
    )
    (net (code "3876") (name "unconnected-(SV115-Pad4)") (class "Default")
      (node (ref "SV115") (pin "4") (pinfunction "4_4") (pintype "passive"))
    )
    (net (code "3877") (name "unconnected-(SV115-Pad5)") (class "Default")
      (node (ref "SV115") (pin "5") (pinfunction "5_5") (pintype "passive"))
    )
    (net (code "3878") (name "unconnected-(SV115-Pad6)") (class "Default")
      (node (ref "SV115") (pin "6") (pinfunction "6_6") (pintype "passive"))
    )
    (net (code "3879") (name "unconnected-(SV115-Pad7)") (class "Default")
      (node (ref "SV115") (pin "7") (pinfunction "7_7") (pintype "passive"))
    )
    (net (code "3880") (name "unconnected-(SV115-Pad8)") (class "Default")
      (node (ref "SV115") (pin "8") (pinfunction "8_8") (pintype "passive"))
    )
    (net (code "3881") (name "unconnected-(SV115-Pad9)") (class "Default")
      (node (ref "SV115") (pin "9") (pinfunction "9_9") (pintype "passive"))
    )
    (net (code "3882") (name "unconnected-(SV115-Pad10)") (class "Default")
      (node (ref "SV115") (pin "10") (pinfunction "10_10") (pintype "passive"))
    )
    (net (code "3883") (name "unconnected-(SV115-Pad11)") (class "Default")
      (node (ref "SV115") (pin "11") (pinfunction "11_11") (pintype "passive"))
    )
    (net (code "3884") (name "unconnected-(SV115-Pad12)") (class "Default")
      (node (ref "SV115") (pin "12") (pinfunction "12_12") (pintype "passive"))
    )
    (net (code "3885") (name "unconnected-(SV115-Pad13)") (class "Default")
      (node (ref "SV115") (pin "13") (pinfunction "13_13") (pintype "passive"))
    )
    (net (code "3886") (name "unconnected-(SV115-Pad14)") (class "Default")
      (node (ref "SV115") (pin "14") (pinfunction "14_14") (pintype "passive"))
    )
    (net (code "3887") (name "unconnected-(SV115-Pad15)") (class "Default")
      (node (ref "SV115") (pin "15") (pinfunction "15_15") (pintype "passive"))
    )
    (net (code "3888") (name "unconnected-(SV115-Pad16)") (class "Default")
      (node (ref "SV115") (pin "16") (pinfunction "16_16") (pintype "passive"))
    )
    (net (code "3889") (name "unconnected-(SV115-Pad17)") (class "Default")
      (node (ref "SV115") (pin "17") (pinfunction "17_17") (pintype "passive"))
    )
    (net (code "3890") (name "unconnected-(SV115-Pad18)") (class "Default")
      (node (ref "SV115") (pin "18") (pinfunction "18_18") (pintype "passive"))
    )
    (net (code "3891") (name "unconnected-(SV115-Pad19)") (class "Default")
      (node (ref "SV115") (pin "19") (pinfunction "19_19") (pintype "passive"))
    )
    (net (code "3892") (name "unconnected-(SV115-Pad20)") (class "Default")
      (node (ref "SV115") (pin "20") (pinfunction "20_20") (pintype "passive"))
    )
    (net (code "3893") (name "unconnected-(SV115-Pad21)") (class "Default")
      (node (ref "SV115") (pin "21") (pinfunction "21_21") (pintype "passive"))
    )
    (net (code "3894") (name "unconnected-(SV115-Pad22)") (class "Default")
      (node (ref "SV115") (pin "22") (pinfunction "22_22") (pintype "passive"))
    )
    (net (code "3895") (name "unconnected-(SV115-Pad23)") (class "Default")
      (node (ref "SV115") (pin "23") (pinfunction "23_23") (pintype "passive"))
    )
    (net (code "3896") (name "unconnected-(SV115-Pad24)") (class "Default")
      (node (ref "SV115") (pin "24") (pinfunction "24_24") (pintype "passive"))
    )
    (net (code "3897") (name "unconnected-(SV115-Pad25)") (class "Default")
      (node (ref "SV115") (pin "25") (pinfunction "25_25") (pintype "passive"))
    )
    (net (code "3898") (name "unconnected-(SV115-Pad26)") (class "Default")
      (node (ref "SV115") (pin "26") (pinfunction "26_26") (pintype "passive"))
    )
    (net (code "3899") (name "unconnected-(SV115-Pad27)") (class "Default")
      (node (ref "SV115") (pin "27") (pinfunction "27_27") (pintype "passive"))
    )
    (net (code "3900") (name "unconnected-(SV115-Pad28)") (class "Default")
      (node (ref "SV115") (pin "28") (pinfunction "28_28") (pintype "passive"))
    )
    (net (code "3901") (name "unconnected-(SV115-Pad29)") (class "Default")
      (node (ref "SV115") (pin "29") (pinfunction "29_29") (pintype "passive"))
    )
    (net (code "3902") (name "unconnected-(SV115-Pad30)") (class "Default")
      (node (ref "SV115") (pin "30") (pinfunction "30_30") (pintype "passive"))
    )
    (net (code "3903") (name "unconnected-(SV115-Pad31)") (class "Default")
      (node (ref "SV115") (pin "31") (pinfunction "31_31") (pintype "passive"))
    )
    (net (code "3904") (name "unconnected-(SV115-Pad32)") (class "Default")
      (node (ref "SV115") (pin "32") (pinfunction "32_32") (pintype "passive"))
    )
    (net (code "3905") (name "unconnected-(SV115-Pad33)") (class "Default")
      (node (ref "SV115") (pin "33") (pinfunction "33_33") (pintype "passive"))
    )
    (net (code "3906") (name "unconnected-(SV115-Pad34)") (class "Default")
      (node (ref "SV115") (pin "34") (pinfunction "34_34") (pintype "passive"))
    )
    (net (code "3907") (name "unconnected-(SV115-Pad35)") (class "Default")
      (node (ref "SV115") (pin "35") (pinfunction "35_35") (pintype "passive"))
    )
    (net (code "3908") (name "unconnected-(SV115-Pad36)") (class "Default")
      (node (ref "SV115") (pin "36") (pinfunction "36_36") (pintype "passive"))
    )
    (net (code "3909") (name "unconnected-(SV116-Pad1)") (class "Default")
      (node (ref "SV116") (pin "1") (pinfunction "1_1") (pintype "passive"))
    )
    (net (code "3910") (name "unconnected-(SV116-Pad2)") (class "Default")
      (node (ref "SV116") (pin "2") (pinfunction "2_2") (pintype "passive"))
    )
    (net (code "3911") (name "unconnected-(SV116-Pad3)") (class "Default")
      (node (ref "SV116") (pin "3") (pinfunction "3_3") (pintype "passive"))
    )
    (net (code "3912") (name "unconnected-(SV116-Pad4)") (class "Default")
      (node (ref "SV116") (pin "4") (pinfunction "4_4") (pintype "passive"))
    )
    (net (code "3913") (name "unconnected-(SV116-Pad5)") (class "Default")
      (node (ref "SV116") (pin "5") (pinfunction "5_5") (pintype "passive"))
    )
    (net (code "3914") (name "unconnected-(SV116-Pad6)") (class "Default")
      (node (ref "SV116") (pin "6") (pinfunction "6_6") (pintype "passive"))
    )
    (net (code "3915") (name "unconnected-(SV117-Pad1)") (class "Default")
      (node (ref "SV117") (pin "1") (pinfunction "1_1") (pintype "passive"))
    )
    (net (code "3916") (name "unconnected-(SV117-Pad2)") (class "Default")
      (node (ref "SV117") (pin "2") (pinfunction "2_2") (pintype "passive"))
    )
    (net (code "3917") (name "unconnected-(SV117-Pad3)") (class "Default")
      (node (ref "SV117") (pin "3") (pinfunction "3_3") (pintype "passive"))
    )
    (net (code "3918") (name "unconnected-(SV117-Pad4)") (class "Default")
      (node (ref "SV117") (pin "4") (pinfunction "4_4") (pintype "passive"))
    )
    (net (code "3919") (name "unconnected-(SV117-Pad5)") (class "Default")
      (node (ref "SV117") (pin "5") (pinfunction "5_5") (pintype "passive"))
    )
    (net (code "3920") (name "unconnected-(SV117-Pad6)") (class "Default")
      (node (ref "SV117") (pin "6") (pinfunction "6_6") (pintype "passive"))
    )
    (net (code "3921") (name "unconnected-(SV118-Pad1)") (class "Default")
      (node (ref "SV118") (pin "1") (pinfunction "1_1") (pintype "passive"))
    )
    (net (code "3922") (name "unconnected-(SV118-Pad2)") (class "Default")
      (node (ref "SV118") (pin "2") (pinfunction "2_2") (pintype "passive"))
    )
    (net (code "3923") (name "unconnected-(SV118-Pad3)") (class "Default")
      (node (ref "SV118") (pin "3") (pinfunction "3_3") (pintype "passive"))
    )
    (net (code "3924") (name "unconnected-(SV118-Pad4)") (class "Default")
      (node (ref "SV118") (pin "4") (pinfunction "4_4") (pintype "passive"))
    )
    (net (code "3925") (name "unconnected-(SV118-Pad5)") (class "Default")
      (node (ref "SV118") (pin "5") (pinfunction "5_5") (pintype "passive"))
    )
    (net (code "3926") (name "unconnected-(SV118-Pad6)") (class "Default")
      (node (ref "SV118") (pin "6") (pinfunction "6_6") (pintype "passive"))
    )
    (net (code "3927") (name "unconnected-(SV119-Pad1)") (class "Default")
      (node (ref "SV119") (pin "1") (pinfunction "1_1") (pintype "passive"))
    )
    (net (code "3928") (name "unconnected-(SV119-Pad2)") (class "Default")
      (node (ref "SV119") (pin "2") (pinfunction "2_2") (pintype "passive"))
    )
    (net (code "3929") (name "unconnected-(SV119-Pad3)") (class "Default")
      (node (ref "SV119") (pin "3") (pinfunction "3_3") (pintype "passive"))
    )
    (net (code "3930") (name "unconnected-(SV119-Pad4)") (class "Default")
      (node (ref "SV119") (pin "4") (pinfunction "4_4") (pintype "passive"))
    )
    (net (code "3931") (name "unconnected-(SV119-Pad5)") (class "Default")
      (node (ref "SV119") (pin "5") (pinfunction "5_5") (pintype "passive"))
    )
    (net (code "3932") (name "unconnected-(SV119-Pad6)") (class "Default")
      (node (ref "SV119") (pin "6") (pinfunction "6_6") (pintype "passive"))
    )
    (net (code "3933") (name "unconnected-(SV120-Pad1)") (class "Default")
      (node (ref "SV120") (pin "1") (pinfunction "1_1") (pintype "passive"))
    )
    (net (code "3934") (name "unconnected-(SV120-Pad2)") (class "Default")
      (node (ref "SV120") (pin "2") (pinfunction "2_2") (pintype "passive"))
    )
    (net (code "3935") (name "unconnected-(SV120-Pad3)") (class "Default")
      (node (ref "SV120") (pin "3") (pinfunction "3_3") (pintype "passive"))
    )
    (net (code "3936") (name "unconnected-(SV120-Pad4)") (class "Default")
      (node (ref "SV120") (pin "4") (pinfunction "4_4") (pintype "passive"))
    )
    (net (code "3937") (name "unconnected-(SV120-Pad5)") (class "Default")
      (node (ref "SV120") (pin "5") (pinfunction "5_5") (pintype "passive"))
    )
    (net (code "3938") (name "unconnected-(SV120-Pad6)") (class "Default")
      (node (ref "SV120") (pin "6") (pinfunction "6_6") (pintype "passive"))
    )
    (net (code "3939") (name "unconnected-(SV121-Pad1)") (class "Default")
      (node (ref "SV121") (pin "1") (pinfunction "1_1") (pintype "passive"))
    )
    (net (code "3940") (name "unconnected-(SV121-Pad2)") (class "Default")
      (node (ref "SV121") (pin "2") (pinfunction "2_2") (pintype "passive"))
    )
    (net (code "3941") (name "unconnected-(SV121-Pad3)") (class "Default")
      (node (ref "SV121") (pin "3") (pinfunction "3_3") (pintype "passive"))
    )
    (net (code "3942") (name "unconnected-(SV121-Pad4)") (class "Default")
      (node (ref "SV121") (pin "4") (pinfunction "4_4") (pintype "passive"))
    )
    (net (code "3943") (name "unconnected-(SV121-Pad5)") (class "Default")
      (node (ref "SV121") (pin "5") (pinfunction "5_5") (pintype "passive"))
    )
    (net (code "3944") (name "unconnected-(SV121-Pad6)") (class "Default")
      (node (ref "SV121") (pin "6") (pinfunction "6_6") (pintype "passive"))
    )
    (net (code "3945") (name "unconnected-(SV122-Pad1)") (class "Default")
      (node (ref "SV122") (pin "1") (pinfunction "1_1") (pintype "passive"))
    )
    (net (code "3946") (name "unconnected-(SV122-Pad2)") (class "Default")
      (node (ref "SV122") (pin "2") (pinfunction "2_2") (pintype "passive"))
    )
    (net (code "3947") (name "unconnected-(SV122-Pad3)") (class "Default")
      (node (ref "SV122") (pin "3") (pinfunction "3_3") (pintype "passive"))
    )
    (net (code "3948") (name "unconnected-(SV122-Pad4)") (class "Default")
      (node (ref "SV122") (pin "4") (pinfunction "4_4") (pintype "passive"))
    )
    (net (code "3949") (name "unconnected-(SV122-Pad5)") (class "Default")
      (node (ref "SV122") (pin "5") (pinfunction "5_5") (pintype "passive"))
    )
    (net (code "3950") (name "unconnected-(SV122-Pad6)") (class "Default")
      (node (ref "SV122") (pin "6") (pinfunction "6_6") (pintype "passive"))
    )
    (net (code "3951") (name "unconnected-(SV123-Pad1)") (class "Default")
      (node (ref "SV123") (pin "1") (pinfunction "1_1") (pintype "passive"))
    )
    (net (code "3952") (name "unconnected-(SV123-Pad2)") (class "Default")
      (node (ref "SV123") (pin "2") (pinfunction "2_2") (pintype "passive"))
    )
    (net (code "3953") (name "unconnected-(SV123-Pad3)") (class "Default")
      (node (ref "SV123") (pin "3") (pinfunction "3_3") (pintype "passive"))
    )
    (net (code "3954") (name "unconnected-(SV123-Pad4)") (class "Default")
      (node (ref "SV123") (pin "4") (pinfunction "4_4") (pintype "passive"))
    )
    (net (code "3955") (name "unconnected-(SV123-Pad5)") (class "Default")
      (node (ref "SV123") (pin "5") (pinfunction "5_5") (pintype "passive"))
    )
    (net (code "3956") (name "unconnected-(SV123-Pad6)") (class "Default")
      (node (ref "SV123") (pin "6") (pinfunction "6_6") (pintype "passive"))
    )
    (net (code "3957") (name "unconnected-(SV124-Pad1)") (class "Default")
      (node (ref "SV124") (pin "1") (pinfunction "1_1") (pintype "passive"))
    )
    (net (code "3958") (name "unconnected-(SV124-Pad2)") (class "Default")
      (node (ref "SV124") (pin "2") (pinfunction "2_2") (pintype "passive"))
    )
    (net (code "3959") (name "unconnected-(SV124-Pad3)") (class "Default")
      (node (ref "SV124") (pin "3") (pinfunction "3_3") (pintype "passive"))
    )
    (net (code "3960") (name "unconnected-(SV124-Pad4)") (class "Default")
      (node (ref "SV124") (pin "4") (pinfunction "4_4") (pintype "passive"))
    )
    (net (code "3961") (name "unconnected-(SV124-Pad5)") (class "Default")
      (node (ref "SV124") (pin "5") (pinfunction "5_5") (pintype "passive"))
    )
    (net (code "3962") (name "unconnected-(SV124-Pad6)") (class "Default")
      (node (ref "SV124") (pin "6") (pinfunction "6_6") (pintype "passive"))
    )
    (net (code "3963") (name "unconnected-(SV125-Pad1)") (class "Default")
      (node (ref "SV125") (pin "1") (pinfunction "1_1") (pintype "passive"))
    )
    (net (code "3964") (name "unconnected-(SV125-Pad2)") (class "Default")
      (node (ref "SV125") (pin "2") (pinfunction "2_2") (pintype "passive"))
    )
    (net (code "3965") (name "unconnected-(SV125-Pad3)") (class "Default")
      (node (ref "SV125") (pin "3") (pinfunction "3_3") (pintype "passive"))
    )
    (net (code "3966") (name "unconnected-(SV125-Pad4)") (class "Default")
      (node (ref "SV125") (pin "4") (pinfunction "4_4") (pintype "passive"))
    )
    (net (code "3967") (name "unconnected-(SV125-Pad5)") (class "Default")
      (node (ref "SV125") (pin "5") (pinfunction "5_5") (pintype "passive"))
    )
    (net (code "3968") (name "unconnected-(SV125-Pad6)") (class "Default")
      (node (ref "SV125") (pin "6") (pinfunction "6_6") (pintype "passive"))
    )
    (net (code "3969") (name "unconnected-(SV126-Pad1)") (class "Default")
      (node (ref "SV126") (pin "1") (pinfunction "1_1") (pintype "passive"))
    )
    (net (code "3970") (name "unconnected-(SV126-Pad2)") (class "Default")
      (node (ref "SV126") (pin "2") (pinfunction "2_2") (pintype "passive"))
    )
    (net (code "3971") (name "unconnected-(SV126-Pad3)") (class "Default")
      (node (ref "SV126") (pin "3") (pinfunction "3_3") (pintype "passive"))
    )
    (net (code "3972") (name "unconnected-(SV126-Pad4)") (class "Default")
      (node (ref "SV126") (pin "4") (pinfunction "4_4") (pintype "passive"))
    )
    (net (code "3973") (name "unconnected-(SV126-Pad5)") (class "Default")
      (node (ref "SV126") (pin "5") (pinfunction "5_5") (pintype "passive"))
    )
    (net (code "3974") (name "unconnected-(SV126-Pad6)") (class "Default")
      (node (ref "SV126") (pin "6") (pinfunction "6_6") (pintype "passive"))
    )
    (net (code "3975") (name "unconnected-(SV127-Pad1)") (class "Default")
      (node (ref "SV127") (pin "1") (pinfunction "1_1") (pintype "passive"))
    )
    (net (code "3976") (name "unconnected-(SV127-Pad2)") (class "Default")
      (node (ref "SV127") (pin "2") (pinfunction "2_2") (pintype "passive"))
    )
    (net (code "3977") (name "unconnected-(SV127-Pad3)") (class "Default")
      (node (ref "SV127") (pin "3") (pinfunction "3_3") (pintype "passive"))
    )
    (net (code "3978") (name "unconnected-(SV127-Pad4)") (class "Default")
      (node (ref "SV127") (pin "4") (pinfunction "4_4") (pintype "passive"))
    )
    (net (code "3979") (name "unconnected-(SV127-Pad5)") (class "Default")
      (node (ref "SV127") (pin "5") (pinfunction "5_5") (pintype "passive"))
    )
    (net (code "3980") (name "unconnected-(SV127-Pad6)") (class "Default")
      (node (ref "SV127") (pin "6") (pinfunction "6_6") (pintype "passive"))
    )
    (net (code "3981") (name "unconnected-(SV128-Pad1)") (class "Default")
      (node (ref "SV128") (pin "1") (pinfunction "1_1") (pintype "passive"))
    )
    (net (code "3982") (name "unconnected-(SV128-Pad2)") (class "Default")
      (node (ref "SV128") (pin "2") (pinfunction "2_2") (pintype "passive"))
    )
    (net (code "3983") (name "unconnected-(SV128-Pad3)") (class "Default")
      (node (ref "SV128") (pin "3") (pinfunction "3_3") (pintype "passive"))
    )
    (net (code "3984") (name "unconnected-(SV128-Pad4)") (class "Default")
      (node (ref "SV128") (pin "4") (pinfunction "4_4") (pintype "passive"))
    )
    (net (code "3985") (name "unconnected-(SV128-Pad5)") (class "Default")
      (node (ref "SV128") (pin "5") (pinfunction "5_5") (pintype "passive"))
    )
    (net (code "3986") (name "unconnected-(SV128-Pad6)") (class "Default")
      (node (ref "SV128") (pin "6") (pinfunction "6_6") (pintype "passive"))
    )
    (net (code "3987") (name "unconnected-(SV129-Pad1)") (class "Default")
      (node (ref "SV129") (pin "1") (pinfunction "1_1") (pintype "passive"))
    )
    (net (code "3988") (name "unconnected-(SV129-Pad2)") (class "Default")
      (node (ref "SV129") (pin "2") (pinfunction "2_2") (pintype "passive"))
    )
    (net (code "3989") (name "unconnected-(SV129-Pad3)") (class "Default")
      (node (ref "SV129") (pin "3") (pinfunction "3_3") (pintype "passive"))
    )
    (net (code "3990") (name "unconnected-(SV129-Pad4)") (class "Default")
      (node (ref "SV129") (pin "4") (pinfunction "4_4") (pintype "passive"))
    )
    (net (code "3991") (name "unconnected-(SV129-Pad5)") (class "Default")
      (node (ref "SV129") (pin "5") (pinfunction "5_5") (pintype "passive"))
    )
    (net (code "3992") (name "unconnected-(SV129-Pad6)") (class "Default")
      (node (ref "SV129") (pin "6") (pinfunction "6_6") (pintype "passive"))
    )
    (net (code "3993") (name "unconnected-(SV130-Pad1)") (class "Default")
      (node (ref "SV130") (pin "1") (pinfunction "1_1") (pintype "passive"))
    )
    (net (code "3994") (name "unconnected-(SV130-Pad2)") (class "Default")
      (node (ref "SV130") (pin "2") (pinfunction "2_2") (pintype "passive"))
    )
    (net (code "3995") (name "unconnected-(SV130-Pad3)") (class "Default")
      (node (ref "SV130") (pin "3") (pinfunction "3_3") (pintype "passive"))
    )
    (net (code "3996") (name "unconnected-(SV130-Pad4)") (class "Default")
      (node (ref "SV130") (pin "4") (pinfunction "4_4") (pintype "passive"))
    )
    (net (code "3997") (name "unconnected-(SV130-Pad5)") (class "Default")
      (node (ref "SV130") (pin "5") (pinfunction "5_5") (pintype "passive"))
    )
    (net (code "3998") (name "unconnected-(SV130-Pad6)") (class "Default")
      (node (ref "SV130") (pin "6") (pinfunction "6_6") (pintype "passive"))
    )
    (net (code "3999") (name "unconnected-(SV131-Pad1)") (class "Default")
      (node (ref "SV131") (pin "1") (pinfunction "1_1") (pintype "passive"))
    )
    (net (code "4000") (name "unconnected-(SV131-Pad2)") (class "Default")
      (node (ref "SV131") (pin "2") (pinfunction "2_2") (pintype "passive"))
    )
    (net (code "4001") (name "unconnected-(SV131-Pad3)") (class "Default")
      (node (ref "SV131") (pin "3") (pinfunction "3_3") (pintype "passive"))
    )
    (net (code "4002") (name "unconnected-(SV131-Pad4)") (class "Default")
      (node (ref "SV131") (pin "4") (pinfunction "4_4") (pintype "passive"))
    )
    (net (code "4003") (name "unconnected-(SV131-Pad5)") (class "Default")
      (node (ref "SV131") (pin "5") (pinfunction "5_5") (pintype "passive"))
    )
    (net (code "4004") (name "unconnected-(SV131-Pad6)") (class "Default")
      (node (ref "SV131") (pin "6") (pinfunction "6_6") (pintype "passive"))
    )
    (net (code "4005") (name "unconnected-(SV132-Pad1)") (class "Default")
      (node (ref "SV132") (pin "1") (pinfunction "1_1") (pintype "passive"))
    )
    (net (code "4006") (name "unconnected-(SV132-Pad2)") (class "Default")
      (node (ref "SV132") (pin "2") (pinfunction "2_2") (pintype "passive"))
    )
    (net (code "4007") (name "unconnected-(SV132-Pad3)") (class "Default")
      (node (ref "SV132") (pin "3") (pinfunction "3_3") (pintype "passive"))
    )
    (net (code "4008") (name "unconnected-(SV132-Pad4)") (class "Default")
      (node (ref "SV132") (pin "4") (pinfunction "4_4") (pintype "passive"))
    )
    (net (code "4009") (name "unconnected-(SV132-Pad5)") (class "Default")
      (node (ref "SV132") (pin "5") (pinfunction "5_5") (pintype "passive"))
    )
    (net (code "4010") (name "unconnected-(SV132-Pad6)") (class "Default")
      (node (ref "SV132") (pin "6") (pinfunction "6_6") (pintype "passive"))
    )
    (net (code "4011") (name "unconnected-(SV133-Pad1)") (class "Default")
      (node (ref "SV133") (pin "1") (pinfunction "1_1") (pintype "passive"))
    )
    (net (code "4012") (name "unconnected-(SV133-Pad2)") (class "Default")
      (node (ref "SV133") (pin "2") (pinfunction "2_2") (pintype "passive"))
    )
    (net (code "4013") (name "unconnected-(SV133-Pad3)") (class "Default")
      (node (ref "SV133") (pin "3") (pinfunction "3_3") (pintype "passive"))
    )
    (net (code "4014") (name "unconnected-(SV133-Pad4)") (class "Default")
      (node (ref "SV133") (pin "4") (pinfunction "4_4") (pintype "passive"))
    )
    (net (code "4015") (name "unconnected-(SV133-Pad5)") (class "Default")
      (node (ref "SV133") (pin "5") (pinfunction "5_5") (pintype "passive"))
    )
    (net (code "4016") (name "unconnected-(SV133-Pad6)") (class "Default")
      (node (ref "SV133") (pin "6") (pinfunction "6_6") (pintype "passive"))
    )
    (net (code "4017") (name "unconnected-(SV134-Pad1)") (class "Default")
      (node (ref "SV134") (pin "1") (pinfunction "1_1") (pintype "passive"))
    )
    (net (code "4018") (name "unconnected-(SV134-Pad2)") (class "Default")
      (node (ref "SV134") (pin "2") (pinfunction "2_2") (pintype "passive"))
    )
    (net (code "4019") (name "unconnected-(SV134-Pad3)") (class "Default")
      (node (ref "SV134") (pin "3") (pinfunction "3_3") (pintype "passive"))
    )
    (net (code "4020") (name "unconnected-(SV134-Pad4)") (class "Default")
      (node (ref "SV134") (pin "4") (pinfunction "4_4") (pintype "passive"))
    )
    (net (code "4021") (name "unconnected-(SV134-Pad5)") (class "Default")
      (node (ref "SV134") (pin "5") (pinfunction "5_5") (pintype "passive"))
    )
    (net (code "4022") (name "unconnected-(SV134-Pad6)") (class "Default")
      (node (ref "SV134") (pin "6") (pinfunction "6_6") (pintype "passive"))
    )
    (net (code "4023") (name "unconnected-(SV135-Pad1)") (class "Default")
      (node (ref "SV135") (pin "1") (pinfunction "1_1") (pintype "passive"))
    )
    (net (code "4024") (name "unconnected-(SV135-Pad2)") (class "Default")
      (node (ref "SV135") (pin "2") (pinfunction "2_2") (pintype "passive"))
    )
    (net (code "4025") (name "unconnected-(SV135-Pad3)") (class "Default")
      (node (ref "SV135") (pin "3") (pinfunction "3_3") (pintype "passive"))
    )
    (net (code "4026") (name "unconnected-(SV135-Pad4)") (class "Default")
      (node (ref "SV135") (pin "4") (pinfunction "4_4") (pintype "passive"))
    )
    (net (code "4027") (name "unconnected-(SV135-Pad5)") (class "Default")
      (node (ref "SV135") (pin "5") (pinfunction "5_5") (pintype "passive"))
    )
    (net (code "4028") (name "unconnected-(SV135-Pad6)") (class "Default")
      (node (ref "SV135") (pin "6") (pinfunction "6_6") (pintype "passive"))
    )
    (net (code "4029") (name "unconnected-(SV135-Pad7)") (class "Default")
      (node (ref "SV135") (pin "7") (pinfunction "7_7") (pintype "passive"))
    )
    (net (code "4030") (name "unconnected-(SV135-Pad8)") (class "Default")
      (node (ref "SV135") (pin "8") (pinfunction "8_8") (pintype "passive"))
    )
    (net (code "4031") (name "unconnected-(SV135-Pad9)") (class "Default")
      (node (ref "SV135") (pin "9") (pinfunction "9_9") (pintype "passive"))
    )
    (net (code "4032") (name "unconnected-(SV135-Pad10)") (class "Default")
      (node (ref "SV135") (pin "10") (pinfunction "10_10") (pintype "passive"))
    )
    (net (code "4033") (name "unconnected-(SV135-Pad11)") (class "Default")
      (node (ref "SV135") (pin "11") (pinfunction "11_11") (pintype "passive"))
    )
    (net (code "4034") (name "unconnected-(SV135-Pad12)") (class "Default")
      (node (ref "SV135") (pin "12") (pinfunction "12_12") (pintype "passive"))
    )
    (net (code "4035") (name "unconnected-(SV135-Pad13)") (class "Default")
      (node (ref "SV135") (pin "13") (pinfunction "13_13") (pintype "passive"))
    )
    (net (code "4036") (name "unconnected-(SV135-Pad14)") (class "Default")
      (node (ref "SV135") (pin "14") (pinfunction "14_14") (pintype "passive"))
    )
    (net (code "4037") (name "unconnected-(SV135-Pad15)") (class "Default")
      (node (ref "SV135") (pin "15") (pinfunction "15_15") (pintype "passive"))
    )
    (net (code "4038") (name "unconnected-(SV135-Pad16)") (class "Default")
      (node (ref "SV135") (pin "16") (pinfunction "16_16") (pintype "passive"))
    )
    (net (code "4039") (name "unconnected-(SV135-Pad17)") (class "Default")
      (node (ref "SV135") (pin "17") (pinfunction "17_17") (pintype "passive"))
    )
    (net (code "4040") (name "unconnected-(SV135-Pad18)") (class "Default")
      (node (ref "SV135") (pin "18") (pinfunction "18_18") (pintype "passive"))
    )
    (net (code "4041") (name "unconnected-(SV135-Pad19)") (class "Default")
      (node (ref "SV135") (pin "19") (pinfunction "19_19") (pintype "passive"))
    )
    (net (code "4042") (name "unconnected-(SV135-Pad20)") (class "Default")
      (node (ref "SV135") (pin "20") (pinfunction "20_20") (pintype "passive"))
    )
    (net (code "4043") (name "unconnected-(SV135-Pad21)") (class "Default")
      (node (ref "SV135") (pin "21") (pinfunction "21_21") (pintype "passive"))
    )
    (net (code "4044") (name "unconnected-(SV135-Pad22)") (class "Default")
      (node (ref "SV135") (pin "22") (pinfunction "22_22") (pintype "passive"))
    )
    (net (code "4045") (name "unconnected-(SV135-Pad23)") (class "Default")
      (node (ref "SV135") (pin "23") (pinfunction "23_23") (pintype "passive"))
    )
    (net (code "4046") (name "unconnected-(SV135-Pad24)") (class "Default")
      (node (ref "SV135") (pin "24") (pinfunction "24_24") (pintype "passive"))
    )
    (net (code "4047") (name "unconnected-(SV136-Pad1)") (class "Default")
      (node (ref "SV136") (pin "1") (pinfunction "1_1") (pintype "passive"))
    )
    (net (code "4048") (name "unconnected-(SV136-Pad2)") (class "Default")
      (node (ref "SV136") (pin "2") (pinfunction "2_2") (pintype "passive"))
    )
    (net (code "4049") (name "unconnected-(SV136-Pad3)") (class "Default")
      (node (ref "SV136") (pin "3") (pinfunction "3_3") (pintype "passive"))
    )
    (net (code "4050") (name "unconnected-(SV136-Pad4)") (class "Default")
      (node (ref "SV136") (pin "4") (pinfunction "4_4") (pintype "passive"))
    )
    (net (code "4051") (name "unconnected-(SV136-Pad5)") (class "Default")
      (node (ref "SV136") (pin "5") (pinfunction "5_5") (pintype "passive"))
    )
    (net (code "4052") (name "unconnected-(SV136-Pad6)") (class "Default")
      (node (ref "SV136") (pin "6") (pinfunction "6_6") (pintype "passive"))
    )
    (net (code "4053") (name "unconnected-(SV136-Pad7)") (class "Default")
      (node (ref "SV136") (pin "7") (pinfunction "7_7") (pintype "passive"))
    )
    (net (code "4054") (name "unconnected-(SV136-Pad8)") (class "Default")
      (node (ref "SV136") (pin "8") (pinfunction "8_8") (pintype "passive"))
    )
    (net (code "4055") (name "unconnected-(SV136-Pad9)") (class "Default")
      (node (ref "SV136") (pin "9") (pinfunction "9_9") (pintype "passive"))
    )
    (net (code "4056") (name "unconnected-(SV136-Pad10)") (class "Default")
      (node (ref "SV136") (pin "10") (pinfunction "10_10") (pintype "passive"))
    )
    (net (code "4057") (name "unconnected-(SV136-Pad11)") (class "Default")
      (node (ref "SV136") (pin "11") (pinfunction "11_11") (pintype "passive"))
    )
    (net (code "4058") (name "unconnected-(SV136-Pad12)") (class "Default")
      (node (ref "SV136") (pin "12") (pinfunction "12_12") (pintype "passive"))
    )
    (net (code "4059") (name "unconnected-(SV136-Pad13)") (class "Default")
      (node (ref "SV136") (pin "13") (pinfunction "13_13") (pintype "passive"))
    )
    (net (code "4060") (name "unconnected-(SV136-Pad14)") (class "Default")
      (node (ref "SV136") (pin "14") (pinfunction "14_14") (pintype "passive"))
    )
    (net (code "4061") (name "unconnected-(SV136-Pad15)") (class "Default")
      (node (ref "SV136") (pin "15") (pinfunction "15_15") (pintype "passive"))
    )
    (net (code "4062") (name "unconnected-(SV136-Pad16)") (class "Default")
      (node (ref "SV136") (pin "16") (pinfunction "16_16") (pintype "passive"))
    )
    (net (code "4063") (name "unconnected-(SV136-Pad17)") (class "Default")
      (node (ref "SV136") (pin "17") (pinfunction "17_17") (pintype "passive"))
    )
    (net (code "4064") (name "unconnected-(SV136-Pad18)") (class "Default")
      (node (ref "SV136") (pin "18") (pinfunction "18_18") (pintype "passive"))
    )
    (net (code "4065") (name "unconnected-(SV136-Pad19)") (class "Default")
      (node (ref "SV136") (pin "19") (pinfunction "19_19") (pintype "passive"))
    )
    (net (code "4066") (name "unconnected-(SV136-Pad20)") (class "Default")
      (node (ref "SV136") (pin "20") (pinfunction "20_20") (pintype "passive"))
    )
    (net (code "4067") (name "unconnected-(SV136-Pad21)") (class "Default")
      (node (ref "SV136") (pin "21") (pinfunction "21_21") (pintype "passive"))
    )
    (net (code "4068") (name "unconnected-(SV136-Pad22)") (class "Default")
      (node (ref "SV136") (pin "22") (pinfunction "22_22") (pintype "passive"))
    )
    (net (code "4069") (name "unconnected-(SV136-Pad23)") (class "Default")
      (node (ref "SV136") (pin "23") (pinfunction "23_23") (pintype "passive"))
    )
    (net (code "4070") (name "unconnected-(SV136-Pad24)") (class "Default")
      (node (ref "SV136") (pin "24") (pinfunction "24_24") (pintype "passive"))
    )
    (net (code "4071") (name "unconnected-(SV137-Pad1)") (class "Default")
      (node (ref "SV137") (pin "1") (pinfunction "1_1") (pintype "passive"))
    )
    (net (code "4072") (name "unconnected-(SV137-Pad2)") (class "Default")
      (node (ref "SV137") (pin "2") (pinfunction "2_2") (pintype "passive"))
    )
    (net (code "4073") (name "unconnected-(SV137-Pad3)") (class "Default")
      (node (ref "SV137") (pin "3") (pinfunction "3_3") (pintype "passive"))
    )
    (net (code "4074") (name "unconnected-(SV137-Pad4)") (class "Default")
      (node (ref "SV137") (pin "4") (pinfunction "4_4") (pintype "passive"))
    )
    (net (code "4075") (name "unconnected-(SV137-Pad5)") (class "Default")
      (node (ref "SV137") (pin "5") (pinfunction "5_5") (pintype "passive"))
    )
    (net (code "4076") (name "unconnected-(SV137-Pad6)") (class "Default")
      (node (ref "SV137") (pin "6") (pinfunction "6_6") (pintype "passive"))
    )
    (net (code "4077") (name "unconnected-(SV137-Pad7)") (class "Default")
      (node (ref "SV137") (pin "7") (pinfunction "7_7") (pintype "passive"))
    )
    (net (code "4078") (name "unconnected-(SV137-Pad8)") (class "Default")
      (node (ref "SV137") (pin "8") (pinfunction "8_8") (pintype "passive"))
    )
    (net (code "4079") (name "unconnected-(SV137-Pad9)") (class "Default")
      (node (ref "SV137") (pin "9") (pinfunction "9_9") (pintype "passive"))
    )
    (net (code "4080") (name "unconnected-(SV137-Pad10)") (class "Default")
      (node (ref "SV137") (pin "10") (pinfunction "10_10") (pintype "passive"))
    )
    (net (code "4081") (name "unconnected-(SV137-Pad11)") (class "Default")
      (node (ref "SV137") (pin "11") (pinfunction "11_11") (pintype "passive"))
    )
    (net (code "4082") (name "unconnected-(SV137-Pad12)") (class "Default")
      (node (ref "SV137") (pin "12") (pinfunction "12_12") (pintype "passive"))
    )
    (net (code "4083") (name "unconnected-(SV137-Pad13)") (class "Default")
      (node (ref "SV137") (pin "13") (pinfunction "13_13") (pintype "passive"))
    )
    (net (code "4084") (name "unconnected-(SV137-Pad14)") (class "Default")
      (node (ref "SV137") (pin "14") (pinfunction "14_14") (pintype "passive"))
    )
    (net (code "4085") (name "unconnected-(SV137-Pad15)") (class "Default")
      (node (ref "SV137") (pin "15") (pinfunction "15_15") (pintype "passive"))
    )
    (net (code "4086") (name "unconnected-(SV137-Pad16)") (class "Default")
      (node (ref "SV137") (pin "16") (pinfunction "16_16") (pintype "passive"))
    )
    (net (code "4087") (name "unconnected-(SV137-Pad17)") (class "Default")
      (node (ref "SV137") (pin "17") (pinfunction "17_17") (pintype "passive"))
    )
    (net (code "4088") (name "unconnected-(SV137-Pad18)") (class "Default")
      (node (ref "SV137") (pin "18") (pinfunction "18_18") (pintype "passive"))
    )
    (net (code "4089") (name "unconnected-(SV137-Pad19)") (class "Default")
      (node (ref "SV137") (pin "19") (pinfunction "19_19") (pintype "passive"))
    )
    (net (code "4090") (name "unconnected-(SV137-Pad20)") (class "Default")
      (node (ref "SV137") (pin "20") (pinfunction "20_20") (pintype "passive"))
    )
    (net (code "4091") (name "unconnected-(SV137-Pad21)") (class "Default")
      (node (ref "SV137") (pin "21") (pinfunction "21_21") (pintype "passive"))
    )
    (net (code "4092") (name "unconnected-(SV137-Pad22)") (class "Default")
      (node (ref "SV137") (pin "22") (pinfunction "22_22") (pintype "passive"))
    )
    (net (code "4093") (name "unconnected-(SV137-Pad23)") (class "Default")
      (node (ref "SV137") (pin "23") (pinfunction "23_23") (pintype "passive"))
    )
    (net (code "4094") (name "unconnected-(SV137-Pad24)") (class "Default")
      (node (ref "SV137") (pin "24") (pinfunction "24_24") (pintype "passive"))
    )
    (net (code "4095") (name "unconnected-(SV137-Pad25)") (class "Default")
      (node (ref "SV137") (pin "25") (pinfunction "25_25") (pintype "passive"))
    )
    (net (code "4096") (name "unconnected-(SV137-Pad26)") (class "Default")
      (node (ref "SV137") (pin "26") (pinfunction "26_26") (pintype "passive"))
    )
    (net (code "4097") (name "unconnected-(SV137-Pad27)") (class "Default")
      (node (ref "SV137") (pin "27") (pinfunction "27_27") (pintype "passive"))
    )
    (net (code "4098") (name "unconnected-(SV137-Pad28)") (class "Default")
      (node (ref "SV137") (pin "28") (pinfunction "28_28") (pintype "passive"))
    )
    (net (code "4099") (name "unconnected-(SV137-Pad29)") (class "Default")
      (node (ref "SV137") (pin "29") (pinfunction "29_29") (pintype "passive"))
    )
    (net (code "4100") (name "unconnected-(SV137-Pad30)") (class "Default")
      (node (ref "SV137") (pin "30") (pinfunction "30_30") (pintype "passive"))
    )
    (net (code "4101") (name "unconnected-(SV137-Pad31)") (class "Default")
      (node (ref "SV137") (pin "31") (pinfunction "31_31") (pintype "passive"))
    )
    (net (code "4102") (name "unconnected-(SV137-Pad32)") (class "Default")
      (node (ref "SV137") (pin "32") (pinfunction "32_32") (pintype "passive"))
    )
    (net (code "4103") (name "unconnected-(SV137-Pad33)") (class "Default")
      (node (ref "SV137") (pin "33") (pinfunction "33_33") (pintype "passive"))
    )
    (net (code "4104") (name "unconnected-(SV137-Pad34)") (class "Default")
      (node (ref "SV137") (pin "34") (pinfunction "34_34") (pintype "passive"))
    )
    (net (code "4105") (name "unconnected-(SV137-Pad35)") (class "Default")
      (node (ref "SV137") (pin "35") (pinfunction "35_35") (pintype "passive"))
    )
    (net (code "4106") (name "unconnected-(SV137-Pad36)") (class "Default")
      (node (ref "SV137") (pin "36") (pinfunction "36_36") (pintype "passive"))
    )
    (net (code "4107") (name "unconnected-(SV137-Pad37)") (class "Default")
      (node (ref "SV137") (pin "37") (pinfunction "37_37") (pintype "passive"))
    )
    (net (code "4108") (name "unconnected-(SV137-Pad38)") (class "Default")
      (node (ref "SV137") (pin "38") (pinfunction "38_38") (pintype "passive"))
    )
    (net (code "4109") (name "unconnected-(SV137-Pad39)") (class "Default")
      (node (ref "SV137") (pin "39") (pinfunction "39_39") (pintype "passive"))
    )
    (net (code "4110") (name "unconnected-(SV137-Pad40)") (class "Default")
      (node (ref "SV137") (pin "40") (pinfunction "40_40") (pintype "passive"))
    )
    (net (code "4111") (name "unconnected-(SV138-Pad1)") (class "Default")
      (node (ref "SV138") (pin "1") (pinfunction "1_1") (pintype "passive"))
    )
    (net (code "4112") (name "unconnected-(SV138-Pad2)") (class "Default")
      (node (ref "SV138") (pin "2") (pinfunction "2_2") (pintype "passive"))
    )
    (net (code "4113") (name "unconnected-(SV138-Pad3)") (class "Default")
      (node (ref "SV138") (pin "3") (pinfunction "3_3") (pintype "passive"))
    )
    (net (code "4114") (name "unconnected-(SV138-Pad4)") (class "Default")
      (node (ref "SV138") (pin "4") (pinfunction "4_4") (pintype "passive"))
    )
    (net (code "4115") (name "unconnected-(SV138-Pad5)") (class "Default")
      (node (ref "SV138") (pin "5") (pinfunction "5_5") (pintype "passive"))
    )
    (net (code "4116") (name "unconnected-(SV138-Pad6)") (class "Default")
      (node (ref "SV138") (pin "6") (pinfunction "6_6") (pintype "passive"))
    )
    (net (code "4117") (name "unconnected-(SV138-Pad7)") (class "Default")
      (node (ref "SV138") (pin "7") (pinfunction "7_7") (pintype "passive"))
    )
    (net (code "4118") (name "unconnected-(SV138-Pad8)") (class "Default")
      (node (ref "SV138") (pin "8") (pinfunction "8_8") (pintype "passive"))
    )
    (net (code "4119") (name "unconnected-(SV138-Pad9)") (class "Default")
      (node (ref "SV138") (pin "9") (pinfunction "9_9") (pintype "passive"))
    )
    (net (code "4120") (name "unconnected-(SV138-Pad10)") (class "Default")
      (node (ref "SV138") (pin "10") (pinfunction "10_10") (pintype "passive"))
    )
    (net (code "4121") (name "unconnected-(SV138-Pad11)") (class "Default")
      (node (ref "SV138") (pin "11") (pinfunction "11_11") (pintype "passive"))
    )
    (net (code "4122") (name "unconnected-(SV138-Pad12)") (class "Default")
      (node (ref "SV138") (pin "12") (pinfunction "12_12") (pintype "passive"))
    )
    (net (code "4123") (name "unconnected-(SV138-Pad13)") (class "Default")
      (node (ref "SV138") (pin "13") (pinfunction "13_13") (pintype "passive"))
    )
    (net (code "4124") (name "unconnected-(SV138-Pad14)") (class "Default")
      (node (ref "SV138") (pin "14") (pinfunction "14_14") (pintype "passive"))
    )
    (net (code "4125") (name "unconnected-(SV138-Pad15)") (class "Default")
      (node (ref "SV138") (pin "15") (pinfunction "15_15") (pintype "passive"))
    )
    (net (code "4126") (name "unconnected-(SV138-Pad16)") (class "Default")
      (node (ref "SV138") (pin "16") (pinfunction "16_16") (pintype "passive"))
    )
    (net (code "4127") (name "unconnected-(SV138-Pad17)") (class "Default")
      (node (ref "SV138") (pin "17") (pinfunction "17_17") (pintype "passive"))
    )
    (net (code "4128") (name "unconnected-(SV138-Pad18)") (class "Default")
      (node (ref "SV138") (pin "18") (pinfunction "18_18") (pintype "passive"))
    )
    (net (code "4129") (name "unconnected-(SV138-Pad19)") (class "Default")
      (node (ref "SV138") (pin "19") (pinfunction "19_19") (pintype "passive"))
    )
    (net (code "4130") (name "unconnected-(SV138-Pad20)") (class "Default")
      (node (ref "SV138") (pin "20") (pinfunction "20_20") (pintype "passive"))
    )
    (net (code "4131") (name "unconnected-(SV138-Pad21)") (class "Default")
      (node (ref "SV138") (pin "21") (pinfunction "21_21") (pintype "passive"))
    )
    (net (code "4132") (name "unconnected-(SV138-Pad22)") (class "Default")
      (node (ref "SV138") (pin "22") (pinfunction "22_22") (pintype "passive"))
    )
    (net (code "4133") (name "unconnected-(SV138-Pad23)") (class "Default")
      (node (ref "SV138") (pin "23") (pinfunction "23_23") (pintype "passive"))
    )
    (net (code "4134") (name "unconnected-(SV138-Pad24)") (class "Default")
      (node (ref "SV138") (pin "24") (pinfunction "24_24") (pintype "passive"))
    )
    (net (code "4135") (name "unconnected-(SV138-Pad25)") (class "Default")
      (node (ref "SV138") (pin "25") (pinfunction "25_25") (pintype "passive"))
    )
    (net (code "4136") (name "unconnected-(SV138-Pad26)") (class "Default")
      (node (ref "SV138") (pin "26") (pinfunction "26_26") (pintype "passive"))
    )
    (net (code "4137") (name "unconnected-(SV138-Pad27)") (class "Default")
      (node (ref "SV138") (pin "27") (pinfunction "27_27") (pintype "passive"))
    )
    (net (code "4138") (name "unconnected-(SV138-Pad28)") (class "Default")
      (node (ref "SV138") (pin "28") (pinfunction "28_28") (pintype "passive"))
    )
    (net (code "4139") (name "unconnected-(SV138-Pad29)") (class "Default")
      (node (ref "SV138") (pin "29") (pinfunction "29_29") (pintype "passive"))
    )
    (net (code "4140") (name "unconnected-(SV138-Pad30)") (class "Default")
      (node (ref "SV138") (pin "30") (pinfunction "30_30") (pintype "passive"))
    )
    (net (code "4141") (name "unconnected-(SV138-Pad31)") (class "Default")
      (node (ref "SV138") (pin "31") (pinfunction "31_31") (pintype "passive"))
    )
    (net (code "4142") (name "unconnected-(SV138-Pad32)") (class "Default")
      (node (ref "SV138") (pin "32") (pinfunction "32_32") (pintype "passive"))
    )
    (net (code "4143") (name "unconnected-(SV138-Pad33)") (class "Default")
      (node (ref "SV138") (pin "33") (pinfunction "33_33") (pintype "passive"))
    )
    (net (code "4144") (name "unconnected-(SV138-Pad34)") (class "Default")
      (node (ref "SV138") (pin "34") (pinfunction "34_34") (pintype "passive"))
    )
    (net (code "4145") (name "unconnected-(SV138-Pad35)") (class "Default")
      (node (ref "SV138") (pin "35") (pinfunction "35_35") (pintype "passive"))
    )
    (net (code "4146") (name "unconnected-(SV138-Pad36)") (class "Default")
      (node (ref "SV138") (pin "36") (pinfunction "36_36") (pintype "passive"))
    )
    (net (code "4147") (name "unconnected-(SV138-Pad37)") (class "Default")
      (node (ref "SV138") (pin "37") (pinfunction "37_37") (pintype "passive"))
    )
    (net (code "4148") (name "unconnected-(SV138-Pad38)") (class "Default")
      (node (ref "SV138") (pin "38") (pinfunction "38_38") (pintype "passive"))
    )
    (net (code "4149") (name "unconnected-(SV138-Pad39)") (class "Default")
      (node (ref "SV138") (pin "39") (pinfunction "39_39") (pintype "passive"))
    )
    (net (code "4150") (name "unconnected-(SV138-Pad40)") (class "Default")
      (node (ref "SV138") (pin "40") (pinfunction "40_40") (pintype "passive"))
    )
    (net (code "4151") (name "unconnected-(SV139-Pad1)") (class "Default")
      (node (ref "SV139") (pin "1") (pinfunction "1_1") (pintype "passive"))
    )
    (net (code "4152") (name "unconnected-(SV139-Pad2)") (class "Default")
      (node (ref "SV139") (pin "2") (pinfunction "2_2") (pintype "passive"))
    )
    (net (code "4153") (name "unconnected-(SV139-Pad3)") (class "Default")
      (node (ref "SV139") (pin "3") (pinfunction "3_3") (pintype "passive"))
    )
    (net (code "4154") (name "unconnected-(SV139-Pad4)") (class "Default")
      (node (ref "SV139") (pin "4") (pinfunction "4_4") (pintype "passive"))
    )
    (net (code "4155") (name "unconnected-(SV139-Pad5)") (class "Default")
      (node (ref "SV139") (pin "5") (pinfunction "5_5") (pintype "passive"))
    )
    (net (code "4156") (name "unconnected-(SV139-Pad6)") (class "Default")
      (node (ref "SV139") (pin "6") (pinfunction "6_6") (pintype "passive"))
    )
    (net (code "4157") (name "unconnected-(SV139-Pad7)") (class "Default")
      (node (ref "SV139") (pin "7") (pinfunction "7_7") (pintype "passive"))
    )
    (net (code "4158") (name "unconnected-(SV139-Pad8)") (class "Default")
      (node (ref "SV139") (pin "8") (pinfunction "8_8") (pintype "passive"))
    )
    (net (code "4159") (name "unconnected-(SV139-Pad9)") (class "Default")
      (node (ref "SV139") (pin "9") (pinfunction "9_9") (pintype "passive"))
    )
    (net (code "4160") (name "unconnected-(SV139-Pad10)") (class "Default")
      (node (ref "SV139") (pin "10") (pinfunction "10_10") (pintype "passive"))
    )
    (net (code "4161") (name "unconnected-(SV139-Pad11)") (class "Default")
      (node (ref "SV139") (pin "11") (pinfunction "11_11") (pintype "passive"))
    )
    (net (code "4162") (name "unconnected-(SV139-Pad12)") (class "Default")
      (node (ref "SV139") (pin "12") (pinfunction "12_12") (pintype "passive"))
    )
    (net (code "4163") (name "unconnected-(SV139-Pad13)") (class "Default")
      (node (ref "SV139") (pin "13") (pinfunction "13_13") (pintype "passive"))
    )
    (net (code "4164") (name "unconnected-(SV139-Pad14)") (class "Default")
      (node (ref "SV139") (pin "14") (pinfunction "14_14") (pintype "passive"))
    )
    (net (code "4165") (name "unconnected-(SV139-Pad15)") (class "Default")
      (node (ref "SV139") (pin "15") (pinfunction "15_15") (pintype "passive"))
    )
    (net (code "4166") (name "unconnected-(SV139-Pad16)") (class "Default")
      (node (ref "SV139") (pin "16") (pinfunction "16_16") (pintype "passive"))
    )
    (net (code "4167") (name "unconnected-(SV139-Pad17)") (class "Default")
      (node (ref "SV139") (pin "17") (pinfunction "17_17") (pintype "passive"))
    )
    (net (code "4168") (name "unconnected-(SV139-Pad18)") (class "Default")
      (node (ref "SV139") (pin "18") (pinfunction "18_18") (pintype "passive"))
    )
    (net (code "4169") (name "unconnected-(SV139-Pad19)") (class "Default")
      (node (ref "SV139") (pin "19") (pinfunction "19_19") (pintype "passive"))
    )
    (net (code "4170") (name "unconnected-(SV139-Pad20)") (class "Default")
      (node (ref "SV139") (pin "20") (pinfunction "20_20") (pintype "passive"))
    )
    (net (code "4171") (name "unconnected-(SV139-Pad21)") (class "Default")
      (node (ref "SV139") (pin "21") (pinfunction "21_21") (pintype "passive"))
    )
    (net (code "4172") (name "unconnected-(SV139-Pad22)") (class "Default")
      (node (ref "SV139") (pin "22") (pinfunction "22_22") (pintype "passive"))
    )
    (net (code "4173") (name "unconnected-(SV139-Pad23)") (class "Default")
      (node (ref "SV139") (pin "23") (pinfunction "23_23") (pintype "passive"))
    )
    (net (code "4174") (name "unconnected-(SV139-Pad24)") (class "Default")
      (node (ref "SV139") (pin "24") (pinfunction "24_24") (pintype "passive"))
    )
    (net (code "4175") (name "unconnected-(SV139-Pad25)") (class "Default")
      (node (ref "SV139") (pin "25") (pinfunction "25_25") (pintype "passive"))
    )
    (net (code "4176") (name "unconnected-(SV139-Pad26)") (class "Default")
      (node (ref "SV139") (pin "26") (pinfunction "26_26") (pintype "passive"))
    )
    (net (code "4177") (name "unconnected-(SV139-Pad27)") (class "Default")
      (node (ref "SV139") (pin "27") (pinfunction "27_27") (pintype "passive"))
    )
    (net (code "4178") (name "unconnected-(SV139-Pad28)") (class "Default")
      (node (ref "SV139") (pin "28") (pinfunction "28_28") (pintype "passive"))
    )
    (net (code "4179") (name "unconnected-(SV139-Pad29)") (class "Default")
      (node (ref "SV139") (pin "29") (pinfunction "29_29") (pintype "passive"))
    )
    (net (code "4180") (name "unconnected-(SV139-Pad30)") (class "Default")
      (node (ref "SV139") (pin "30") (pinfunction "30_30") (pintype "passive"))
    )
    (net (code "4181") (name "unconnected-(SV139-Pad31)") (class "Default")
      (node (ref "SV139") (pin "31") (pinfunction "31_31") (pintype "passive"))
    )
    (net (code "4182") (name "unconnected-(SV139-Pad32)") (class "Default")
      (node (ref "SV139") (pin "32") (pinfunction "32_32") (pintype "passive"))
    )
    (net (code "4183") (name "unconnected-(SV139-Pad33)") (class "Default")
      (node (ref "SV139") (pin "33") (pinfunction "33_33") (pintype "passive"))
    )
    (net (code "4184") (name "unconnected-(SV139-Pad34)") (class "Default")
      (node (ref "SV139") (pin "34") (pinfunction "34_34") (pintype "passive"))
    )
    (net (code "4185") (name "unconnected-(SV139-Pad35)") (class "Default")
      (node (ref "SV139") (pin "35") (pinfunction "35_35") (pintype "passive"))
    )
    (net (code "4186") (name "unconnected-(SV139-Pad36)") (class "Default")
      (node (ref "SV139") (pin "36") (pinfunction "36_36") (pintype "passive"))
    )
    (net (code "4187") (name "unconnected-(SV139-Pad37)") (class "Default")
      (node (ref "SV139") (pin "37") (pinfunction "37_37") (pintype "passive"))
    )
    (net (code "4188") (name "unconnected-(SV139-Pad38)") (class "Default")
      (node (ref "SV139") (pin "38") (pinfunction "38_38") (pintype "passive"))
    )
    (net (code "4189") (name "unconnected-(SV139-Pad39)") (class "Default")
      (node (ref "SV139") (pin "39") (pinfunction "39_39") (pintype "passive"))
    )
    (net (code "4190") (name "unconnected-(SV139-Pad40)") (class "Default")
      (node (ref "SV139") (pin "40") (pinfunction "40_40") (pintype "passive"))
    )
    (net (code "4191") (name "unconnected-(SV140-Pad1)") (class "Default")
      (node (ref "SV140") (pin "1") (pinfunction "1_1") (pintype "passive"))
    )
    (net (code "4192") (name "unconnected-(SV140-Pad2)") (class "Default")
      (node (ref "SV140") (pin "2") (pinfunction "2_2") (pintype "passive"))
    )
    (net (code "4193") (name "unconnected-(SV140-Pad3)") (class "Default")
      (node (ref "SV140") (pin "3") (pinfunction "3_3") (pintype "passive"))
    )
    (net (code "4194") (name "unconnected-(SV140-Pad4)") (class "Default")
      (node (ref "SV140") (pin "4") (pinfunction "4_4") (pintype "passive"))
    )
    (net (code "4195") (name "unconnected-(SV140-Pad5)") (class "Default")
      (node (ref "SV140") (pin "5") (pinfunction "5_5") (pintype "passive"))
    )
    (net (code "4196") (name "unconnected-(SV140-Pad6)") (class "Default")
      (node (ref "SV140") (pin "6") (pinfunction "6_6") (pintype "passive"))
    )
    (net (code "4197") (name "unconnected-(SV140-Pad7)") (class "Default")
      (node (ref "SV140") (pin "7") (pinfunction "7_7") (pintype "passive"))
    )
    (net (code "4198") (name "unconnected-(SV140-Pad8)") (class "Default")
      (node (ref "SV140") (pin "8") (pinfunction "8_8") (pintype "passive"))
    )
    (net (code "4199") (name "unconnected-(SV140-Pad9)") (class "Default")
      (node (ref "SV140") (pin "9") (pinfunction "9_9") (pintype "passive"))
    )
    (net (code "4200") (name "unconnected-(SV140-Pad10)") (class "Default")
      (node (ref "SV140") (pin "10") (pinfunction "10_10") (pintype "passive"))
    )
    (net (code "4201") (name "unconnected-(SV140-Pad11)") (class "Default")
      (node (ref "SV140") (pin "11") (pinfunction "11_11") (pintype "passive"))
    )
    (net (code "4202") (name "unconnected-(SV140-Pad12)") (class "Default")
      (node (ref "SV140") (pin "12") (pinfunction "12_12") (pintype "passive"))
    )
    (net (code "4203") (name "unconnected-(SV140-Pad13)") (class "Default")
      (node (ref "SV140") (pin "13") (pinfunction "13_13") (pintype "passive"))
    )
    (net (code "4204") (name "unconnected-(SV140-Pad14)") (class "Default")
      (node (ref "SV140") (pin "14") (pinfunction "14_14") (pintype "passive"))
    )
    (net (code "4205") (name "unconnected-(SV140-Pad15)") (class "Default")
      (node (ref "SV140") (pin "15") (pinfunction "15_15") (pintype "passive"))
    )
    (net (code "4206") (name "unconnected-(SV140-Pad16)") (class "Default")
      (node (ref "SV140") (pin "16") (pinfunction "16_16") (pintype "passive"))
    )
    (net (code "4207") (name "unconnected-(SV140-Pad17)") (class "Default")
      (node (ref "SV140") (pin "17") (pinfunction "17_17") (pintype "passive"))
    )
    (net (code "4208") (name "unconnected-(SV140-Pad18)") (class "Default")
      (node (ref "SV140") (pin "18") (pinfunction "18_18") (pintype "passive"))
    )
    (net (code "4209") (name "unconnected-(SV140-Pad19)") (class "Default")
      (node (ref "SV140") (pin "19") (pinfunction "19_19") (pintype "passive"))
    )
    (net (code "4210") (name "unconnected-(SV140-Pad20)") (class "Default")
      (node (ref "SV140") (pin "20") (pinfunction "20_20") (pintype "passive"))
    )
    (net (code "4211") (name "unconnected-(SV140-Pad21)") (class "Default")
      (node (ref "SV140") (pin "21") (pinfunction "21_21") (pintype "passive"))
    )
    (net (code "4212") (name "unconnected-(SV140-Pad22)") (class "Default")
      (node (ref "SV140") (pin "22") (pinfunction "22_22") (pintype "passive"))
    )
    (net (code "4213") (name "unconnected-(SV140-Pad23)") (class "Default")
      (node (ref "SV140") (pin "23") (pinfunction "23_23") (pintype "passive"))
    )
    (net (code "4214") (name "unconnected-(SV140-Pad24)") (class "Default")
      (node (ref "SV140") (pin "24") (pinfunction "24_24") (pintype "passive"))
    )
    (net (code "4215") (name "unconnected-(SV140-Pad25)") (class "Default")
      (node (ref "SV140") (pin "25") (pinfunction "25_25") (pintype "passive"))
    )
    (net (code "4216") (name "unconnected-(SV140-Pad26)") (class "Default")
      (node (ref "SV140") (pin "26") (pinfunction "26_26") (pintype "passive"))
    )
    (net (code "4217") (name "unconnected-(SV140-Pad27)") (class "Default")
      (node (ref "SV140") (pin "27") (pinfunction "27_27") (pintype "passive"))
    )
    (net (code "4218") (name "unconnected-(SV140-Pad28)") (class "Default")
      (node (ref "SV140") (pin "28") (pinfunction "28_28") (pintype "passive"))
    )
    (net (code "4219") (name "unconnected-(SV140-Pad29)") (class "Default")
      (node (ref "SV140") (pin "29") (pinfunction "29_29") (pintype "passive"))
    )
    (net (code "4220") (name "unconnected-(SV140-Pad30)") (class "Default")
      (node (ref "SV140") (pin "30") (pinfunction "30_30") (pintype "passive"))
    )
    (net (code "4221") (name "unconnected-(SV140-Pad31)") (class "Default")
      (node (ref "SV140") (pin "31") (pinfunction "31_31") (pintype "passive"))
    )
    (net (code "4222") (name "unconnected-(SV140-Pad32)") (class "Default")
      (node (ref "SV140") (pin "32") (pinfunction "32_32") (pintype "passive"))
    )
    (net (code "4223") (name "unconnected-(SV140-Pad33)") (class "Default")
      (node (ref "SV140") (pin "33") (pinfunction "33_33") (pintype "passive"))
    )
    (net (code "4224") (name "unconnected-(SV140-Pad34)") (class "Default")
      (node (ref "SV140") (pin "34") (pinfunction "34_34") (pintype "passive"))
    )
    (net (code "4225") (name "unconnected-(SV140-Pad35)") (class "Default")
      (node (ref "SV140") (pin "35") (pinfunction "35_35") (pintype "passive"))
    )
    (net (code "4226") (name "unconnected-(SV140-Pad36)") (class "Default")
      (node (ref "SV140") (pin "36") (pinfunction "36_36") (pintype "passive"))
    )
    (net (code "4227") (name "unconnected-(SV140-Pad37)") (class "Default")
      (node (ref "SV140") (pin "37") (pinfunction "37_37") (pintype "passive"))
    )
    (net (code "4228") (name "unconnected-(SV140-Pad38)") (class "Default")
      (node (ref "SV140") (pin "38") (pinfunction "38_38") (pintype "passive"))
    )
    (net (code "4229") (name "unconnected-(SV140-Pad39)") (class "Default")
      (node (ref "SV140") (pin "39") (pinfunction "39_39") (pintype "passive"))
    )
    (net (code "4230") (name "unconnected-(SV140-Pad40)") (class "Default")
      (node (ref "SV140") (pin "40") (pinfunction "40_40") (pintype "passive"))
    )
    (net (code "4231") (name "unconnected-(SV141-Pad1)") (class "Default")
      (node (ref "SV141") (pin "1") (pinfunction "1_1") (pintype "passive"))
    )
    (net (code "4232") (name "unconnected-(SV141-Pad2)") (class "Default")
      (node (ref "SV141") (pin "2") (pinfunction "2_2") (pintype "passive"))
    )
    (net (code "4233") (name "unconnected-(SV141-Pad3)") (class "Default")
      (node (ref "SV141") (pin "3") (pinfunction "3_3") (pintype "passive"))
    )
    (net (code "4234") (name "unconnected-(SV141-Pad4)") (class "Default")
      (node (ref "SV141") (pin "4") (pinfunction "4_4") (pintype "passive"))
    )
    (net (code "4235") (name "unconnected-(SV141-Pad5)") (class "Default")
      (node (ref "SV141") (pin "5") (pinfunction "5_5") (pintype "passive"))
    )
    (net (code "4236") (name "unconnected-(SV141-Pad6)") (class "Default")
      (node (ref "SV141") (pin "6") (pinfunction "6_6") (pintype "passive"))
    )
    (net (code "4237") (name "unconnected-(SV141-Pad7)") (class "Default")
      (node (ref "SV141") (pin "7") (pinfunction "7_7") (pintype "passive"))
    )
    (net (code "4238") (name "unconnected-(SV141-Pad8)") (class "Default")
      (node (ref "SV141") (pin "8") (pinfunction "8_8") (pintype "passive"))
    )
    (net (code "4239") (name "unconnected-(SV141-Pad9)") (class "Default")
      (node (ref "SV141") (pin "9") (pinfunction "9_9") (pintype "passive"))
    )
    (net (code "4240") (name "unconnected-(SV141-Pad10)") (class "Default")
      (node (ref "SV141") (pin "10") (pinfunction "10_10") (pintype "passive"))
    )
    (net (code "4241") (name "unconnected-(SV141-Pad11)") (class "Default")
      (node (ref "SV141") (pin "11") (pinfunction "11_11") (pintype "passive"))
    )
    (net (code "4242") (name "unconnected-(SV141-Pad12)") (class "Default")
      (node (ref "SV141") (pin "12") (pinfunction "12_12") (pintype "passive"))
    )
    (net (code "4243") (name "unconnected-(SV141-Pad13)") (class "Default")
      (node (ref "SV141") (pin "13") (pinfunction "13_13") (pintype "passive"))
    )
    (net (code "4244") (name "unconnected-(SV141-Pad14)") (class "Default")
      (node (ref "SV141") (pin "14") (pinfunction "14_14") (pintype "passive"))
    )
    (net (code "4245") (name "unconnected-(SV141-Pad15)") (class "Default")
      (node (ref "SV141") (pin "15") (pinfunction "15_15") (pintype "passive"))
    )
    (net (code "4246") (name "unconnected-(SV141-Pad16)") (class "Default")
      (node (ref "SV141") (pin "16") (pinfunction "16_16") (pintype "passive"))
    )
    (net (code "4247") (name "unconnected-(SV141-Pad17)") (class "Default")
      (node (ref "SV141") (pin "17") (pinfunction "17_17") (pintype "passive"))
    )
    (net (code "4248") (name "unconnected-(SV141-Pad18)") (class "Default")
      (node (ref "SV141") (pin "18") (pinfunction "18_18") (pintype "passive"))
    )
    (net (code "4249") (name "unconnected-(SV141-Pad19)") (class "Default")
      (node (ref "SV141") (pin "19") (pinfunction "19_19") (pintype "passive"))
    )
    (net (code "4250") (name "unconnected-(SV141-Pad20)") (class "Default")
      (node (ref "SV141") (pin "20") (pinfunction "20_20") (pintype "passive"))
    )
    (net (code "4251") (name "unconnected-(SV141-Pad21)") (class "Default")
      (node (ref "SV141") (pin "21") (pinfunction "21_21") (pintype "passive"))
    )
    (net (code "4252") (name "unconnected-(SV141-Pad22)") (class "Default")
      (node (ref "SV141") (pin "22") (pinfunction "22_22") (pintype "passive"))
    )
    (net (code "4253") (name "unconnected-(SV141-Pad23)") (class "Default")
      (node (ref "SV141") (pin "23") (pinfunction "23_23") (pintype "passive"))
    )
    (net (code "4254") (name "unconnected-(SV141-Pad24)") (class "Default")
      (node (ref "SV141") (pin "24") (pinfunction "24_24") (pintype "passive"))
    )
    (net (code "4255") (name "unconnected-(SV142-Pad1)") (class "Default")
      (node (ref "SV142") (pin "1") (pinfunction "1_1") (pintype "passive"))
    )
    (net (code "4256") (name "unconnected-(SV142-Pad2)") (class "Default")
      (node (ref "SV142") (pin "2") (pinfunction "2_2") (pintype "passive"))
    )
    (net (code "4257") (name "unconnected-(SV142-Pad3)") (class "Default")
      (node (ref "SV142") (pin "3") (pinfunction "3_3") (pintype "passive"))
    )
    (net (code "4258") (name "unconnected-(SV142-Pad4)") (class "Default")
      (node (ref "SV142") (pin "4") (pinfunction "4_4") (pintype "passive"))
    )
    (net (code "4259") (name "unconnected-(SV142-Pad5)") (class "Default")
      (node (ref "SV142") (pin "5") (pinfunction "5_5") (pintype "passive"))
    )
    (net (code "4260") (name "unconnected-(SV142-Pad6)") (class "Default")
      (node (ref "SV142") (pin "6") (pinfunction "6_6") (pintype "passive"))
    )
    (net (code "4261") (name "unconnected-(SV142-Pad7)") (class "Default")
      (node (ref "SV142") (pin "7") (pinfunction "7_7") (pintype "passive"))
    )
    (net (code "4262") (name "unconnected-(SV142-Pad8)") (class "Default")
      (node (ref "SV142") (pin "8") (pinfunction "8_8") (pintype "passive"))
    )
    (net (code "4263") (name "unconnected-(SV142-Pad9)") (class "Default")
      (node (ref "SV142") (pin "9") (pinfunction "9_9") (pintype "passive"))
    )
    (net (code "4264") (name "unconnected-(SV142-Pad10)") (class "Default")
      (node (ref "SV142") (pin "10") (pinfunction "10_10") (pintype "passive"))
    )
    (net (code "4265") (name "unconnected-(SV142-Pad11)") (class "Default")
      (node (ref "SV142") (pin "11") (pinfunction "11_11") (pintype "passive"))
    )
    (net (code "4266") (name "unconnected-(SV142-Pad12)") (class "Default")
      (node (ref "SV142") (pin "12") (pinfunction "12_12") (pintype "passive"))
    )
    (net (code "4267") (name "unconnected-(SV142-Pad13)") (class "Default")
      (node (ref "SV142") (pin "13") (pinfunction "13_13") (pintype "passive"))
    )
    (net (code "4268") (name "unconnected-(SV142-Pad14)") (class "Default")
      (node (ref "SV142") (pin "14") (pinfunction "14_14") (pintype "passive"))
    )
    (net (code "4269") (name "unconnected-(SV142-Pad15)") (class "Default")
      (node (ref "SV142") (pin "15") (pinfunction "15_15") (pintype "passive"))
    )
    (net (code "4270") (name "unconnected-(SV142-Pad16)") (class "Default")
      (node (ref "SV142") (pin "16") (pinfunction "16_16") (pintype "passive"))
    )
    (net (code "4271") (name "unconnected-(SV142-Pad17)") (class "Default")
      (node (ref "SV142") (pin "17") (pinfunction "17_17") (pintype "passive"))
    )
    (net (code "4272") (name "unconnected-(SV142-Pad18)") (class "Default")
      (node (ref "SV142") (pin "18") (pinfunction "18_18") (pintype "passive"))
    )
    (net (code "4273") (name "unconnected-(SV142-Pad19)") (class "Default")
      (node (ref "SV142") (pin "19") (pinfunction "19_19") (pintype "passive"))
    )
    (net (code "4274") (name "unconnected-(SV142-Pad20)") (class "Default")
      (node (ref "SV142") (pin "20") (pinfunction "20_20") (pintype "passive"))
    )
    (net (code "4275") (name "unconnected-(SV142-Pad21)") (class "Default")
      (node (ref "SV142") (pin "21") (pinfunction "21_21") (pintype "passive"))
    )
    (net (code "4276") (name "unconnected-(SV142-Pad22)") (class "Default")
      (node (ref "SV142") (pin "22") (pinfunction "22_22") (pintype "passive"))
    )
    (net (code "4277") (name "unconnected-(SV142-Pad23)") (class "Default")
      (node (ref "SV142") (pin "23") (pinfunction "23_23") (pintype "passive"))
    )
    (net (code "4278") (name "unconnected-(SV142-Pad24)") (class "Default")
      (node (ref "SV142") (pin "24") (pinfunction "24_24") (pintype "passive"))
    )
    (net (code "4279") (name "unconnected-(SV143-Pad1)") (class "Default")
      (node (ref "SV143") (pin "1") (pinfunction "1_1") (pintype "passive"))
    )
    (net (code "4280") (name "unconnected-(SV143-Pad2)") (class "Default")
      (node (ref "SV143") (pin "2") (pinfunction "2_2") (pintype "passive"))
    )
    (net (code "4281") (name "unconnected-(SV143-Pad3)") (class "Default")
      (node (ref "SV143") (pin "3") (pinfunction "3_3") (pintype "passive"))
    )
    (net (code "4282") (name "unconnected-(SV143-Pad4)") (class "Default")
      (node (ref "SV143") (pin "4") (pinfunction "4_4") (pintype "passive"))
    )
    (net (code "4283") (name "unconnected-(SV143-Pad5)") (class "Default")
      (node (ref "SV143") (pin "5") (pinfunction "5_5") (pintype "passive"))
    )
    (net (code "4284") (name "unconnected-(SV143-Pad6)") (class "Default")
      (node (ref "SV143") (pin "6") (pinfunction "6_6") (pintype "passive"))
    )
    (net (code "4285") (name "unconnected-(SV143-Pad7)") (class "Default")
      (node (ref "SV143") (pin "7") (pinfunction "7_7") (pintype "passive"))
    )
    (net (code "4286") (name "unconnected-(SV143-Pad8)") (class "Default")
      (node (ref "SV143") (pin "8") (pinfunction "8_8") (pintype "passive"))
    )
    (net (code "4287") (name "unconnected-(SV143-Pad9)") (class "Default")
      (node (ref "SV143") (pin "9") (pinfunction "9_9") (pintype "passive"))
    )
    (net (code "4288") (name "unconnected-(SV143-Pad10)") (class "Default")
      (node (ref "SV143") (pin "10") (pinfunction "10_10") (pintype "passive"))
    )
    (net (code "4289") (name "unconnected-(SV143-Pad11)") (class "Default")
      (node (ref "SV143") (pin "11") (pinfunction "11_11") (pintype "passive"))
    )
    (net (code "4290") (name "unconnected-(SV143-Pad12)") (class "Default")
      (node (ref "SV143") (pin "12") (pinfunction "12_12") (pintype "passive"))
    )
    (net (code "4291") (name "unconnected-(SV143-Pad13)") (class "Default")
      (node (ref "SV143") (pin "13") (pinfunction "13_13") (pintype "passive"))
    )
    (net (code "4292") (name "unconnected-(SV143-Pad14)") (class "Default")
      (node (ref "SV143") (pin "14") (pinfunction "14_14") (pintype "passive"))
    )
    (net (code "4293") (name "unconnected-(SV143-Pad15)") (class "Default")
      (node (ref "SV143") (pin "15") (pinfunction "15_15") (pintype "passive"))
    )
    (net (code "4294") (name "unconnected-(SV143-Pad16)") (class "Default")
      (node (ref "SV143") (pin "16") (pinfunction "16_16") (pintype "passive"))
    )
    (net (code "4295") (name "unconnected-(SV143-Pad17)") (class "Default")
      (node (ref "SV143") (pin "17") (pinfunction "17_17") (pintype "passive"))
    )
    (net (code "4296") (name "unconnected-(SV143-Pad18)") (class "Default")
      (node (ref "SV143") (pin "18") (pinfunction "18_18") (pintype "passive"))
    )
    (net (code "4297") (name "unconnected-(SV143-Pad19)") (class "Default")
      (node (ref "SV143") (pin "19") (pinfunction "19_19") (pintype "passive"))
    )
    (net (code "4298") (name "unconnected-(SV143-Pad20)") (class "Default")
      (node (ref "SV143") (pin "20") (pinfunction "20_20") (pintype "passive"))
    )
    (net (code "4299") (name "unconnected-(SV143-Pad21)") (class "Default")
      (node (ref "SV143") (pin "21") (pinfunction "21_21") (pintype "passive"))
    )
    (net (code "4300") (name "unconnected-(SV143-Pad22)") (class "Default")
      (node (ref "SV143") (pin "22") (pinfunction "22_22") (pintype "passive"))
    )
    (net (code "4301") (name "unconnected-(SV143-Pad23)") (class "Default")
      (node (ref "SV143") (pin "23") (pinfunction "23_23") (pintype "passive"))
    )
    (net (code "4302") (name "unconnected-(SV143-Pad24)") (class "Default")
      (node (ref "SV143") (pin "24") (pinfunction "24_24") (pintype "passive"))
    )
    (net (code "4303") (name "unconnected-(SV143-Pad25)") (class "Default")
      (node (ref "SV143") (pin "25") (pinfunction "25_25") (pintype "passive"))
    )
    (net (code "4304") (name "unconnected-(SV143-Pad26)") (class "Default")
      (node (ref "SV143") (pin "26") (pinfunction "26_26") (pintype "passive"))
    )
    (net (code "4305") (name "unconnected-(SV143-Pad27)") (class "Default")
      (node (ref "SV143") (pin "27") (pinfunction "27_27") (pintype "passive"))
    )
    (net (code "4306") (name "unconnected-(SV143-Pad28)") (class "Default")
      (node (ref "SV143") (pin "28") (pinfunction "28_28") (pintype "passive"))
    )
    (net (code "4307") (name "unconnected-(SV143-Pad29)") (class "Default")
      (node (ref "SV143") (pin "29") (pinfunction "29_29") (pintype "passive"))
    )
    (net (code "4308") (name "unconnected-(SV143-Pad30)") (class "Default")
      (node (ref "SV143") (pin "30") (pinfunction "30_30") (pintype "passive"))
    )
    (net (code "4309") (name "unconnected-(SV143-Pad31)") (class "Default")
      (node (ref "SV143") (pin "31") (pinfunction "31_31") (pintype "passive"))
    )
    (net (code "4310") (name "unconnected-(SV143-Pad32)") (class "Default")
      (node (ref "SV143") (pin "32") (pinfunction "32_32") (pintype "passive"))
    )
    (net (code "4311") (name "unconnected-(SV143-Pad33)") (class "Default")
      (node (ref "SV143") (pin "33") (pinfunction "33_33") (pintype "passive"))
    )
    (net (code "4312") (name "unconnected-(SV143-Pad34)") (class "Default")
      (node (ref "SV143") (pin "34") (pinfunction "34_34") (pintype "passive"))
    )
    (net (code "4313") (name "unconnected-(SV143-Pad35)") (class "Default")
      (node (ref "SV143") (pin "35") (pinfunction "35_35") (pintype "passive"))
    )
    (net (code "4314") (name "unconnected-(SV143-Pad36)") (class "Default")
      (node (ref "SV143") (pin "36") (pinfunction "36_36") (pintype "passive"))
    )
    (net (code "4315") (name "unconnected-(SV143-Pad37)") (class "Default")
      (node (ref "SV143") (pin "37") (pinfunction "37_37") (pintype "passive"))
    )
    (net (code "4316") (name "unconnected-(SV143-Pad38)") (class "Default")
      (node (ref "SV143") (pin "38") (pinfunction "38_38") (pintype "passive"))
    )
    (net (code "4317") (name "unconnected-(SV143-Pad39)") (class "Default")
      (node (ref "SV143") (pin "39") (pinfunction "39_39") (pintype "passive"))
    )
    (net (code "4318") (name "unconnected-(SV143-Pad40)") (class "Default")
      (node (ref "SV143") (pin "40") (pinfunction "40_40") (pintype "passive"))
    )
    (net (code "4319") (name "unconnected-(SV144-Pad1)") (class "Default")
      (node (ref "SV144") (pin "1") (pinfunction "1_1") (pintype "passive"))
    )
    (net (code "4320") (name "unconnected-(SV144-Pad2)") (class "Default")
      (node (ref "SV144") (pin "2") (pinfunction "2_2") (pintype "passive"))
    )
    (net (code "4321") (name "unconnected-(SV144-Pad3)") (class "Default")
      (node (ref "SV144") (pin "3") (pinfunction "3_3") (pintype "passive"))
    )
    (net (code "4322") (name "unconnected-(SV144-Pad4)") (class "Default")
      (node (ref "SV144") (pin "4") (pinfunction "4_4") (pintype "passive"))
    )
    (net (code "4323") (name "unconnected-(SV144-Pad5)") (class "Default")
      (node (ref "SV144") (pin "5") (pinfunction "5_5") (pintype "passive"))
    )
    (net (code "4324") (name "unconnected-(SV144-Pad6)") (class "Default")
      (node (ref "SV144") (pin "6") (pinfunction "6_6") (pintype "passive"))
    )
    (net (code "4325") (name "unconnected-(SV144-Pad7)") (class "Default")
      (node (ref "SV144") (pin "7") (pinfunction "7_7") (pintype "passive"))
    )
    (net (code "4326") (name "unconnected-(SV144-Pad8)") (class "Default")
      (node (ref "SV144") (pin "8") (pinfunction "8_8") (pintype "passive"))
    )
    (net (code "4327") (name "unconnected-(SV144-Pad9)") (class "Default")
      (node (ref "SV144") (pin "9") (pinfunction "9_9") (pintype "passive"))
    )
    (net (code "4328") (name "unconnected-(SV144-Pad10)") (class "Default")
      (node (ref "SV144") (pin "10") (pinfunction "10_10") (pintype "passive"))
    )
    (net (code "4329") (name "unconnected-(SV144-Pad11)") (class "Default")
      (node (ref "SV144") (pin "11") (pinfunction "11_11") (pintype "passive"))
    )
    (net (code "4330") (name "unconnected-(SV144-Pad12)") (class "Default")
      (node (ref "SV144") (pin "12") (pinfunction "12_12") (pintype "passive"))
    )
    (net (code "4331") (name "unconnected-(SV144-Pad13)") (class "Default")
      (node (ref "SV144") (pin "13") (pinfunction "13_13") (pintype "passive"))
    )
    (net (code "4332") (name "unconnected-(SV144-Pad14)") (class "Default")
      (node (ref "SV144") (pin "14") (pinfunction "14_14") (pintype "passive"))
    )
    (net (code "4333") (name "unconnected-(SV144-Pad15)") (class "Default")
      (node (ref "SV144") (pin "15") (pinfunction "15_15") (pintype "passive"))
    )
    (net (code "4334") (name "unconnected-(SV144-Pad16)") (class "Default")
      (node (ref "SV144") (pin "16") (pinfunction "16_16") (pintype "passive"))
    )
    (net (code "4335") (name "unconnected-(SV144-Pad17)") (class "Default")
      (node (ref "SV144") (pin "17") (pinfunction "17_17") (pintype "passive"))
    )
    (net (code "4336") (name "unconnected-(SV144-Pad18)") (class "Default")
      (node (ref "SV144") (pin "18") (pinfunction "18_18") (pintype "passive"))
    )
    (net (code "4337") (name "unconnected-(SV144-Pad19)") (class "Default")
      (node (ref "SV144") (pin "19") (pinfunction "19_19") (pintype "passive"))
    )
    (net (code "4338") (name "unconnected-(SV144-Pad20)") (class "Default")
      (node (ref "SV144") (pin "20") (pinfunction "20_20") (pintype "passive"))
    )
    (net (code "4339") (name "unconnected-(SV144-Pad21)") (class "Default")
      (node (ref "SV144") (pin "21") (pinfunction "21_21") (pintype "passive"))
    )
    (net (code "4340") (name "unconnected-(SV144-Pad22)") (class "Default")
      (node (ref "SV144") (pin "22") (pinfunction "22_22") (pintype "passive"))
    )
    (net (code "4341") (name "unconnected-(SV144-Pad23)") (class "Default")
      (node (ref "SV144") (pin "23") (pinfunction "23_23") (pintype "passive"))
    )
    (net (code "4342") (name "unconnected-(SV144-Pad24)") (class "Default")
      (node (ref "SV144") (pin "24") (pinfunction "24_24") (pintype "passive"))
    )
    (net (code "4343") (name "unconnected-(SV144-Pad25)") (class "Default")
      (node (ref "SV144") (pin "25") (pinfunction "25_25") (pintype "passive"))
    )
    (net (code "4344") (name "unconnected-(SV144-Pad26)") (class "Default")
      (node (ref "SV144") (pin "26") (pinfunction "26_26") (pintype "passive"))
    )
    (net (code "4345") (name "unconnected-(SV144-Pad27)") (class "Default")
      (node (ref "SV144") (pin "27") (pinfunction "27_27") (pintype "passive"))
    )
    (net (code "4346") (name "unconnected-(SV144-Pad28)") (class "Default")
      (node (ref "SV144") (pin "28") (pinfunction "28_28") (pintype "passive"))
    )
    (net (code "4347") (name "unconnected-(SV144-Pad29)") (class "Default")
      (node (ref "SV144") (pin "29") (pinfunction "29_29") (pintype "passive"))
    )
    (net (code "4348") (name "unconnected-(SV144-Pad30)") (class "Default")
      (node (ref "SV144") (pin "30") (pinfunction "30_30") (pintype "passive"))
    )
    (net (code "4349") (name "unconnected-(SV144-Pad31)") (class "Default")
      (node (ref "SV144") (pin "31") (pinfunction "31_31") (pintype "passive"))
    )
    (net (code "4350") (name "unconnected-(SV144-Pad32)") (class "Default")
      (node (ref "SV144") (pin "32") (pinfunction "32_32") (pintype "passive"))
    )
    (net (code "4351") (name "unconnected-(SV144-Pad33)") (class "Default")
      (node (ref "SV144") (pin "33") (pinfunction "33_33") (pintype "passive"))
    )
    (net (code "4352") (name "unconnected-(SV144-Pad34)") (class "Default")
      (node (ref "SV144") (pin "34") (pinfunction "34_34") (pintype "passive"))
    )
    (net (code "4353") (name "unconnected-(SV144-Pad35)") (class "Default")
      (node (ref "SV144") (pin "35") (pinfunction "35_35") (pintype "passive"))
    )
    (net (code "4354") (name "unconnected-(SV144-Pad36)") (class "Default")
      (node (ref "SV144") (pin "36") (pinfunction "36_36") (pintype "passive"))
    )
    (net (code "4355") (name "unconnected-(SV144-Pad37)") (class "Default")
      (node (ref "SV144") (pin "37") (pinfunction "37_37") (pintype "passive"))
    )
    (net (code "4356") (name "unconnected-(SV144-Pad38)") (class "Default")
      (node (ref "SV144") (pin "38") (pinfunction "38_38") (pintype "passive"))
    )
    (net (code "4357") (name "unconnected-(SV144-Pad39)") (class "Default")
      (node (ref "SV144") (pin "39") (pinfunction "39_39") (pintype "passive"))
    )
    (net (code "4358") (name "unconnected-(SV144-Pad40)") (class "Default")
      (node (ref "SV144") (pin "40") (pinfunction "40_40") (pintype "passive"))
    )
    (net (code "4359") (name "unconnected-(SV145-Pad1)") (class "Default")
      (node (ref "SV145") (pin "1") (pinfunction "1_1") (pintype "passive"))
    )
    (net (code "4360") (name "unconnected-(SV145-Pad2)") (class "Default")
      (node (ref "SV145") (pin "2") (pinfunction "2_2") (pintype "passive"))
    )
    (net (code "4361") (name "unconnected-(SV145-Pad3)") (class "Default")
      (node (ref "SV145") (pin "3") (pinfunction "3_3") (pintype "passive"))
    )
    (net (code "4362") (name "unconnected-(SV145-Pad4)") (class "Default")
      (node (ref "SV145") (pin "4") (pinfunction "4_4") (pintype "passive"))
    )
    (net (code "4363") (name "unconnected-(SV145-Pad5)") (class "Default")
      (node (ref "SV145") (pin "5") (pinfunction "5_5") (pintype "passive"))
    )
    (net (code "4364") (name "unconnected-(SV145-Pad6)") (class "Default")
      (node (ref "SV145") (pin "6") (pinfunction "6_6") (pintype "passive"))
    )
    (net (code "4365") (name "unconnected-(SV145-Pad7)") (class "Default")
      (node (ref "SV145") (pin "7") (pinfunction "7_7") (pintype "passive"))
    )
    (net (code "4366") (name "unconnected-(SV145-Pad8)") (class "Default")
      (node (ref "SV145") (pin "8") (pinfunction "8_8") (pintype "passive"))
    )
    (net (code "4367") (name "unconnected-(SV145-Pad9)") (class "Default")
      (node (ref "SV145") (pin "9") (pinfunction "9_9") (pintype "passive"))
    )
    (net (code "4368") (name "unconnected-(SV145-Pad10)") (class "Default")
      (node (ref "SV145") (pin "10") (pinfunction "10_10") (pintype "passive"))
    )
    (net (code "4369") (name "unconnected-(SV145-Pad11)") (class "Default")
      (node (ref "SV145") (pin "11") (pinfunction "11_11") (pintype "passive"))
    )
    (net (code "4370") (name "unconnected-(SV145-Pad12)") (class "Default")
      (node (ref "SV145") (pin "12") (pinfunction "12_12") (pintype "passive"))
    )
    (net (code "4371") (name "unconnected-(SV145-Pad13)") (class "Default")
      (node (ref "SV145") (pin "13") (pinfunction "13_13") (pintype "passive"))
    )
    (net (code "4372") (name "unconnected-(SV145-Pad14)") (class "Default")
      (node (ref "SV145") (pin "14") (pinfunction "14_14") (pintype "passive"))
    )
    (net (code "4373") (name "unconnected-(SV145-Pad15)") (class "Default")
      (node (ref "SV145") (pin "15") (pinfunction "15_15") (pintype "passive"))
    )
    (net (code "4374") (name "unconnected-(SV145-Pad16)") (class "Default")
      (node (ref "SV145") (pin "16") (pinfunction "16_16") (pintype "passive"))
    )
    (net (code "4375") (name "unconnected-(SV145-Pad17)") (class "Default")
      (node (ref "SV145") (pin "17") (pinfunction "17_17") (pintype "passive"))
    )
    (net (code "4376") (name "unconnected-(SV145-Pad18)") (class "Default")
      (node (ref "SV145") (pin "18") (pinfunction "18_18") (pintype "passive"))
    )
    (net (code "4377") (name "unconnected-(SV145-Pad19)") (class "Default")
      (node (ref "SV145") (pin "19") (pinfunction "19_19") (pintype "passive"))
    )
    (net (code "4378") (name "unconnected-(SV145-Pad20)") (class "Default")
      (node (ref "SV145") (pin "20") (pinfunction "20_20") (pintype "passive"))
    )
    (net (code "4379") (name "unconnected-(SV145-Pad21)") (class "Default")
      (node (ref "SV145") (pin "21") (pinfunction "21_21") (pintype "passive"))
    )
    (net (code "4380") (name "unconnected-(SV145-Pad22)") (class "Default")
      (node (ref "SV145") (pin "22") (pinfunction "22_22") (pintype "passive"))
    )
    (net (code "4381") (name "unconnected-(SV145-Pad23)") (class "Default")
      (node (ref "SV145") (pin "23") (pinfunction "23_23") (pintype "passive"))
    )
    (net (code "4382") (name "unconnected-(SV145-Pad24)") (class "Default")
      (node (ref "SV145") (pin "24") (pinfunction "24_24") (pintype "passive"))
    )
    (net (code "4383") (name "unconnected-(SV145-Pad25)") (class "Default")
      (node (ref "SV145") (pin "25") (pinfunction "25_25") (pintype "passive"))
    )
    (net (code "4384") (name "unconnected-(SV145-Pad26)") (class "Default")
      (node (ref "SV145") (pin "26") (pinfunction "26_26") (pintype "passive"))
    )
    (net (code "4385") (name "unconnected-(SV145-Pad27)") (class "Default")
      (node (ref "SV145") (pin "27") (pinfunction "27_27") (pintype "passive"))
    )
    (net (code "4386") (name "unconnected-(SV145-Pad28)") (class "Default")
      (node (ref "SV145") (pin "28") (pinfunction "28_28") (pintype "passive"))
    )
    (net (code "4387") (name "unconnected-(SV145-Pad29)") (class "Default")
      (node (ref "SV145") (pin "29") (pinfunction "29_29") (pintype "passive"))
    )
    (net (code "4388") (name "unconnected-(SV145-Pad30)") (class "Default")
      (node (ref "SV145") (pin "30") (pinfunction "30_30") (pintype "passive"))
    )
    (net (code "4389") (name "unconnected-(SV145-Pad31)") (class "Default")
      (node (ref "SV145") (pin "31") (pinfunction "31_31") (pintype "passive"))
    )
    (net (code "4390") (name "unconnected-(SV145-Pad32)") (class "Default")
      (node (ref "SV145") (pin "32") (pinfunction "32_32") (pintype "passive"))
    )
    (net (code "4391") (name "unconnected-(SV145-Pad33)") (class "Default")
      (node (ref "SV145") (pin "33") (pinfunction "33_33") (pintype "passive"))
    )
    (net (code "4392") (name "unconnected-(SV145-Pad34)") (class "Default")
      (node (ref "SV145") (pin "34") (pinfunction "34_34") (pintype "passive"))
    )
    (net (code "4393") (name "unconnected-(SV145-Pad35)") (class "Default")
      (node (ref "SV145") (pin "35") (pinfunction "35_35") (pintype "passive"))
    )
    (net (code "4394") (name "unconnected-(SV145-Pad36)") (class "Default")
      (node (ref "SV145") (pin "36") (pinfunction "36_36") (pintype "passive"))
    )
    (net (code "4395") (name "unconnected-(SV145-Pad37)") (class "Default")
      (node (ref "SV145") (pin "37") (pinfunction "37_37") (pintype "passive"))
    )
    (net (code "4396") (name "unconnected-(SV145-Pad38)") (class "Default")
      (node (ref "SV145") (pin "38") (pinfunction "38_38") (pintype "passive"))
    )
    (net (code "4397") (name "unconnected-(SV145-Pad39)") (class "Default")
      (node (ref "SV145") (pin "39") (pinfunction "39_39") (pintype "passive"))
    )
    (net (code "4398") (name "unconnected-(SV145-Pad40)") (class "Default")
      (node (ref "SV145") (pin "40") (pinfunction "40_40") (pintype "passive"))
    )
    (net (code "4399") (name "unconnected-(SV146-Pad1)") (class "Default")
      (node (ref "SV146") (pin "1") (pinfunction "1_1") (pintype "passive"))
    )
    (net (code "4400") (name "unconnected-(SV146-Pad2)") (class "Default")
      (node (ref "SV146") (pin "2") (pinfunction "2_2") (pintype "passive"))
    )
    (net (code "4401") (name "unconnected-(SV146-Pad3)") (class "Default")
      (node (ref "SV146") (pin "3") (pinfunction "3_3") (pintype "passive"))
    )
    (net (code "4402") (name "unconnected-(SV146-Pad4)") (class "Default")
      (node (ref "SV146") (pin "4") (pinfunction "4_4") (pintype "passive"))
    )
    (net (code "4403") (name "unconnected-(SV146-Pad5)") (class "Default")
      (node (ref "SV146") (pin "5") (pinfunction "5_5") (pintype "passive"))
    )
    (net (code "4404") (name "unconnected-(SV146-Pad6)") (class "Default")
      (node (ref "SV146") (pin "6") (pinfunction "6_6") (pintype "passive"))
    )
    (net (code "4405") (name "unconnected-(SV146-Pad7)") (class "Default")
      (node (ref "SV146") (pin "7") (pinfunction "7_7") (pintype "passive"))
    )
    (net (code "4406") (name "unconnected-(SV146-Pad8)") (class "Default")
      (node (ref "SV146") (pin "8") (pinfunction "8_8") (pintype "passive"))
    )
    (net (code "4407") (name "unconnected-(SV146-Pad9)") (class "Default")
      (node (ref "SV146") (pin "9") (pinfunction "9_9") (pintype "passive"))
    )
    (net (code "4408") (name "unconnected-(SV146-Pad10)") (class "Default")
      (node (ref "SV146") (pin "10") (pinfunction "10_10") (pintype "passive"))
    )
    (net (code "4409") (name "unconnected-(SV146-Pad11)") (class "Default")
      (node (ref "SV146") (pin "11") (pinfunction "11_11") (pintype "passive"))
    )
    (net (code "4410") (name "unconnected-(SV146-Pad12)") (class "Default")
      (node (ref "SV146") (pin "12") (pinfunction "12_12") (pintype "passive"))
    )
    (net (code "4411") (name "unconnected-(SV146-Pad13)") (class "Default")
      (node (ref "SV146") (pin "13") (pinfunction "13_13") (pintype "passive"))
    )
    (net (code "4412") (name "unconnected-(SV146-Pad14)") (class "Default")
      (node (ref "SV146") (pin "14") (pinfunction "14_14") (pintype "passive"))
    )
    (net (code "4413") (name "unconnected-(SV146-Pad15)") (class "Default")
      (node (ref "SV146") (pin "15") (pinfunction "15_15") (pintype "passive"))
    )
    (net (code "4414") (name "unconnected-(SV146-Pad16)") (class "Default")
      (node (ref "SV146") (pin "16") (pinfunction "16_16") (pintype "passive"))
    )
    (net (code "4415") (name "unconnected-(SV146-Pad17)") (class "Default")
      (node (ref "SV146") (pin "17") (pinfunction "17_17") (pintype "passive"))
    )
    (net (code "4416") (name "unconnected-(SV146-Pad18)") (class "Default")
      (node (ref "SV146") (pin "18") (pinfunction "18_18") (pintype "passive"))
    )
    (net (code "4417") (name "unconnected-(SV146-Pad19)") (class "Default")
      (node (ref "SV146") (pin "19") (pinfunction "19_19") (pintype "passive"))
    )
    (net (code "4418") (name "unconnected-(SV146-Pad20)") (class "Default")
      (node (ref "SV146") (pin "20") (pinfunction "20_20") (pintype "passive"))
    )
    (net (code "4419") (name "unconnected-(SV146-Pad21)") (class "Default")
      (node (ref "SV146") (pin "21") (pinfunction "21_21") (pintype "passive"))
    )
    (net (code "4420") (name "unconnected-(SV146-Pad22)") (class "Default")
      (node (ref "SV146") (pin "22") (pinfunction "22_22") (pintype "passive"))
    )
    (net (code "4421") (name "unconnected-(SV146-Pad23)") (class "Default")
      (node (ref "SV146") (pin "23") (pinfunction "23_23") (pintype "passive"))
    )
    (net (code "4422") (name "unconnected-(SV146-Pad24)") (class "Default")
      (node (ref "SV146") (pin "24") (pinfunction "24_24") (pintype "passive"))
    )
    (net (code "4423") (name "unconnected-(SV146-Pad25)") (class "Default")
      (node (ref "SV146") (pin "25") (pinfunction "25_25") (pintype "passive"))
    )
    (net (code "4424") (name "unconnected-(SV146-Pad26)") (class "Default")
      (node (ref "SV146") (pin "26") (pinfunction "26_26") (pintype "passive"))
    )
    (net (code "4425") (name "unconnected-(SV146-Pad27)") (class "Default")
      (node (ref "SV146") (pin "27") (pinfunction "27_27") (pintype "passive"))
    )
    (net (code "4426") (name "unconnected-(SV146-Pad28)") (class "Default")
      (node (ref "SV146") (pin "28") (pinfunction "28_28") (pintype "passive"))
    )
    (net (code "4427") (name "unconnected-(SV146-Pad29)") (class "Default")
      (node (ref "SV146") (pin "29") (pinfunction "29_29") (pintype "passive"))
    )
    (net (code "4428") (name "unconnected-(SV146-Pad30)") (class "Default")
      (node (ref "SV146") (pin "30") (pinfunction "30_30") (pintype "passive"))
    )
    (net (code "4429") (name "unconnected-(SV146-Pad31)") (class "Default")
      (node (ref "SV146") (pin "31") (pinfunction "31_31") (pintype "passive"))
    )
    (net (code "4430") (name "unconnected-(SV146-Pad32)") (class "Default")
      (node (ref "SV146") (pin "32") (pinfunction "32_32") (pintype "passive"))
    )
    (net (code "4431") (name "unconnected-(SV146-Pad33)") (class "Default")
      (node (ref "SV146") (pin "33") (pinfunction "33_33") (pintype "passive"))
    )
    (net (code "4432") (name "unconnected-(SV146-Pad34)") (class "Default")
      (node (ref "SV146") (pin "34") (pinfunction "34_34") (pintype "passive"))
    )
    (net (code "4433") (name "unconnected-(SV146-Pad35)") (class "Default")
      (node (ref "SV146") (pin "35") (pinfunction "35_35") (pintype "passive"))
    )
    (net (code "4434") (name "unconnected-(SV146-Pad36)") (class "Default")
      (node (ref "SV146") (pin "36") (pinfunction "36_36") (pintype "passive"))
    )
    (net (code "4435") (name "unconnected-(SV146-Pad37)") (class "Default")
      (node (ref "SV146") (pin "37") (pinfunction "37_37") (pintype "passive"))
    )
    (net (code "4436") (name "unconnected-(SV146-Pad38)") (class "Default")
      (node (ref "SV146") (pin "38") (pinfunction "38_38") (pintype "passive"))
    )
    (net (code "4437") (name "unconnected-(SV146-Pad39)") (class "Default")
      (node (ref "SV146") (pin "39") (pinfunction "39_39") (pintype "passive"))
    )
    (net (code "4438") (name "unconnected-(SV146-Pad40)") (class "Default")
      (node (ref "SV146") (pin "40") (pinfunction "40_40") (pintype "passive"))
    )
    (net (code "4439") (name "unconnected-(SV147-Pad1)") (class "Default")
      (node (ref "SV147") (pin "1") (pinfunction "1_1") (pintype "passive"))
    )
    (net (code "4440") (name "unconnected-(SV147-Pad2)") (class "Default")
      (node (ref "SV147") (pin "2") (pinfunction "2_2") (pintype "passive"))
    )
    (net (code "4441") (name "unconnected-(SV147-Pad3)") (class "Default")
      (node (ref "SV147") (pin "3") (pinfunction "3_3") (pintype "passive"))
    )
    (net (code "4442") (name "unconnected-(SV147-Pad4)") (class "Default")
      (node (ref "SV147") (pin "4") (pinfunction "4_4") (pintype "passive"))
    )
    (net (code "4443") (name "unconnected-(SV147-Pad5)") (class "Default")
      (node (ref "SV147") (pin "5") (pinfunction "5_5") (pintype "passive"))
    )
    (net (code "4444") (name "unconnected-(SV147-Pad6)") (class "Default")
      (node (ref "SV147") (pin "6") (pinfunction "6_6") (pintype "passive"))
    )
    (net (code "4445") (name "unconnected-(SV147-Pad7)") (class "Default")
      (node (ref "SV147") (pin "7") (pinfunction "7_7") (pintype "passive"))
    )
    (net (code "4446") (name "unconnected-(SV147-Pad8)") (class "Default")
      (node (ref "SV147") (pin "8") (pinfunction "8_8") (pintype "passive"))
    )
    (net (code "4447") (name "unconnected-(SV147-Pad9)") (class "Default")
      (node (ref "SV147") (pin "9") (pinfunction "9_9") (pintype "passive"))
    )
    (net (code "4448") (name "unconnected-(SV147-Pad10)") (class "Default")
      (node (ref "SV147") (pin "10") (pinfunction "10_10") (pintype "passive"))
    )
    (net (code "4449") (name "unconnected-(SV147-Pad11)") (class "Default")
      (node (ref "SV147") (pin "11") (pinfunction "11_11") (pintype "passive"))
    )
    (net (code "4450") (name "unconnected-(SV147-Pad12)") (class "Default")
      (node (ref "SV147") (pin "12") (pinfunction "12_12") (pintype "passive"))
    )
    (net (code "4451") (name "unconnected-(SV147-Pad13)") (class "Default")
      (node (ref "SV147") (pin "13") (pinfunction "13_13") (pintype "passive"))
    )
    (net (code "4452") (name "unconnected-(SV147-Pad14)") (class "Default")
      (node (ref "SV147") (pin "14") (pinfunction "14_14") (pintype "passive"))
    )
    (net (code "4453") (name "unconnected-(SV147-Pad15)") (class "Default")
      (node (ref "SV147") (pin "15") (pinfunction "15_15") (pintype "passive"))
    )
    (net (code "4454") (name "unconnected-(SV147-Pad16)") (class "Default")
      (node (ref "SV147") (pin "16") (pinfunction "16_16") (pintype "passive"))
    )
    (net (code "4455") (name "unconnected-(SV147-Pad17)") (class "Default")
      (node (ref "SV147") (pin "17") (pinfunction "17_17") (pintype "passive"))
    )
    (net (code "4456") (name "unconnected-(SV147-Pad18)") (class "Default")
      (node (ref "SV147") (pin "18") (pinfunction "18_18") (pintype "passive"))
    )
    (net (code "4457") (name "unconnected-(SV147-Pad19)") (class "Default")
      (node (ref "SV147") (pin "19") (pinfunction "19_19") (pintype "passive"))
    )
    (net (code "4458") (name "unconnected-(SV147-Pad20)") (class "Default")
      (node (ref "SV147") (pin "20") (pinfunction "20_20") (pintype "passive"))
    )
    (net (code "4459") (name "unconnected-(SV147-Pad21)") (class "Default")
      (node (ref "SV147") (pin "21") (pinfunction "21_21") (pintype "passive"))
    )
    (net (code "4460") (name "unconnected-(SV147-Pad22)") (class "Default")
      (node (ref "SV147") (pin "22") (pinfunction "22_22") (pintype "passive"))
    )
    (net (code "4461") (name "unconnected-(SV147-Pad23)") (class "Default")
      (node (ref "SV147") (pin "23") (pinfunction "23_23") (pintype "passive"))
    )
    (net (code "4462") (name "unconnected-(SV147-Pad24)") (class "Default")
      (node (ref "SV147") (pin "24") (pinfunction "24_24") (pintype "passive"))
    )
    (net (code "4463") (name "unconnected-(SV148-Pad1)") (class "Default")
      (node (ref "SV148") (pin "1") (pinfunction "1_1") (pintype "passive"))
    )
    (net (code "4464") (name "unconnected-(SV148-Pad2)") (class "Default")
      (node (ref "SV148") (pin "2") (pinfunction "2_2") (pintype "passive"))
    )
    (net (code "4465") (name "unconnected-(SV148-Pad3)") (class "Default")
      (node (ref "SV148") (pin "3") (pinfunction "3_3") (pintype "passive"))
    )
    (net (code "4466") (name "unconnected-(SV148-Pad4)") (class "Default")
      (node (ref "SV148") (pin "4") (pinfunction "4_4") (pintype "passive"))
    )
    (net (code "4467") (name "unconnected-(SV148-Pad5)") (class "Default")
      (node (ref "SV148") (pin "5") (pinfunction "5_5") (pintype "passive"))
    )
    (net (code "4468") (name "unconnected-(SV148-Pad6)") (class "Default")
      (node (ref "SV148") (pin "6") (pinfunction "6_6") (pintype "passive"))
    )
    (net (code "4469") (name "unconnected-(SV148-Pad7)") (class "Default")
      (node (ref "SV148") (pin "7") (pinfunction "7_7") (pintype "passive"))
    )
    (net (code "4470") (name "unconnected-(SV148-Pad8)") (class "Default")
      (node (ref "SV148") (pin "8") (pinfunction "8_8") (pintype "passive"))
    )
    (net (code "4471") (name "unconnected-(SV148-Pad9)") (class "Default")
      (node (ref "SV148") (pin "9") (pinfunction "9_9") (pintype "passive"))
    )
    (net (code "4472") (name "unconnected-(SV148-Pad10)") (class "Default")
      (node (ref "SV148") (pin "10") (pinfunction "10_10") (pintype "passive"))
    )
    (net (code "4473") (name "unconnected-(SV148-Pad11)") (class "Default")
      (node (ref "SV148") (pin "11") (pinfunction "11_11") (pintype "passive"))
    )
    (net (code "4474") (name "unconnected-(SV148-Pad12)") (class "Default")
      (node (ref "SV148") (pin "12") (pinfunction "12_12") (pintype "passive"))
    )
    (net (code "4475") (name "unconnected-(SV148-Pad13)") (class "Default")
      (node (ref "SV148") (pin "13") (pinfunction "13_13") (pintype "passive"))
    )
    (net (code "4476") (name "unconnected-(SV148-Pad14)") (class "Default")
      (node (ref "SV148") (pin "14") (pinfunction "14_14") (pintype "passive"))
    )
    (net (code "4477") (name "unconnected-(SV148-Pad15)") (class "Default")
      (node (ref "SV148") (pin "15") (pinfunction "15_15") (pintype "passive"))
    )
    (net (code "4478") (name "unconnected-(SV148-Pad16)") (class "Default")
      (node (ref "SV148") (pin "16") (pinfunction "16_16") (pintype "passive"))
    )
    (net (code "4479") (name "unconnected-(SV148-Pad17)") (class "Default")
      (node (ref "SV148") (pin "17") (pinfunction "17_17") (pintype "passive"))
    )
    (net (code "4480") (name "unconnected-(SV148-Pad18)") (class "Default")
      (node (ref "SV148") (pin "18") (pinfunction "18_18") (pintype "passive"))
    )
    (net (code "4481") (name "unconnected-(SV148-Pad19)") (class "Default")
      (node (ref "SV148") (pin "19") (pinfunction "19_19") (pintype "passive"))
    )
    (net (code "4482") (name "unconnected-(SV148-Pad20)") (class "Default")
      (node (ref "SV148") (pin "20") (pinfunction "20_20") (pintype "passive"))
    )
    (net (code "4483") (name "unconnected-(SV148-Pad21)") (class "Default")
      (node (ref "SV148") (pin "21") (pinfunction "21_21") (pintype "passive"))
    )
    (net (code "4484") (name "unconnected-(SV148-Pad22)") (class "Default")
      (node (ref "SV148") (pin "22") (pinfunction "22_22") (pintype "passive"))
    )
    (net (code "4485") (name "unconnected-(SV148-Pad23)") (class "Default")
      (node (ref "SV148") (pin "23") (pinfunction "23_23") (pintype "passive"))
    )
    (net (code "4486") (name "unconnected-(SV148-Pad24)") (class "Default")
      (node (ref "SV148") (pin "24") (pinfunction "24_24") (pintype "passive"))
    )
    (net (code "4487") (name "unconnected-(SV149-Pad1)") (class "Default")
      (node (ref "SV149") (pin "1") (pinfunction "1_1") (pintype "passive"))
    )
    (net (code "4488") (name "unconnected-(SV149-Pad2)") (class "Default")
      (node (ref "SV149") (pin "2") (pinfunction "2_2") (pintype "passive"))
    )
    (net (code "4489") (name "unconnected-(SV149-Pad3)") (class "Default")
      (node (ref "SV149") (pin "3") (pinfunction "3_3") (pintype "passive"))
    )
    (net (code "4490") (name "unconnected-(SV149-Pad4)") (class "Default")
      (node (ref "SV149") (pin "4") (pinfunction "4_4") (pintype "passive"))
    )
    (net (code "4491") (name "unconnected-(SV149-Pad5)") (class "Default")
      (node (ref "SV149") (pin "5") (pinfunction "5_5") (pintype "passive"))
    )
    (net (code "4492") (name "unconnected-(SV149-Pad6)") (class "Default")
      (node (ref "SV149") (pin "6") (pinfunction "6_6") (pintype "passive"))
    )
    (net (code "4493") (name "unconnected-(SV149-Pad7)") (class "Default")
      (node (ref "SV149") (pin "7") (pinfunction "7_7") (pintype "passive"))
    )
    (net (code "4494") (name "unconnected-(SV149-Pad8)") (class "Default")
      (node (ref "SV149") (pin "8") (pinfunction "8_8") (pintype "passive"))
    )
    (net (code "4495") (name "unconnected-(SV149-Pad9)") (class "Default")
      (node (ref "SV149") (pin "9") (pinfunction "9_9") (pintype "passive"))
    )
    (net (code "4496") (name "unconnected-(SV149-Pad10)") (class "Default")
      (node (ref "SV149") (pin "10") (pinfunction "10_10") (pintype "passive"))
    )
    (net (code "4497") (name "unconnected-(SV149-Pad11)") (class "Default")
      (node (ref "SV149") (pin "11") (pinfunction "11_11") (pintype "passive"))
    )
    (net (code "4498") (name "unconnected-(SV149-Pad12)") (class "Default")
      (node (ref "SV149") (pin "12") (pinfunction "12_12") (pintype "passive"))
    )
    (net (code "4499") (name "unconnected-(SV149-Pad13)") (class "Default")
      (node (ref "SV149") (pin "13") (pinfunction "13_13") (pintype "passive"))
    )
    (net (code "4500") (name "unconnected-(SV149-Pad14)") (class "Default")
      (node (ref "SV149") (pin "14") (pinfunction "14_14") (pintype "passive"))
    )
    (net (code "4501") (name "unconnected-(SV149-Pad15)") (class "Default")
      (node (ref "SV149") (pin "15") (pinfunction "15_15") (pintype "passive"))
    )
    (net (code "4502") (name "unconnected-(SV149-Pad16)") (class "Default")
      (node (ref "SV149") (pin "16") (pinfunction "16_16") (pintype "passive"))
    )
    (net (code "4503") (name "unconnected-(SV149-Pad17)") (class "Default")
      (node (ref "SV149") (pin "17") (pinfunction "17_17") (pintype "passive"))
    )
    (net (code "4504") (name "unconnected-(SV149-Pad18)") (class "Default")
      (node (ref "SV149") (pin "18") (pinfunction "18_18") (pintype "passive"))
    )
    (net (code "4505") (name "unconnected-(SV149-Pad19)") (class "Default")
      (node (ref "SV149") (pin "19") (pinfunction "19_19") (pintype "passive"))
    )
    (net (code "4506") (name "unconnected-(SV149-Pad20)") (class "Default")
      (node (ref "SV149") (pin "20") (pinfunction "20_20") (pintype "passive"))
    )
    (net (code "4507") (name "unconnected-(SV149-Pad21)") (class "Default")
      (node (ref "SV149") (pin "21") (pinfunction "21_21") (pintype "passive"))
    )
    (net (code "4508") (name "unconnected-(SV149-Pad22)") (class "Default")
      (node (ref "SV149") (pin "22") (pinfunction "22_22") (pintype "passive"))
    )
    (net (code "4509") (name "unconnected-(SV149-Pad23)") (class "Default")
      (node (ref "SV149") (pin "23") (pinfunction "23_23") (pintype "passive"))
    )
    (net (code "4510") (name "unconnected-(SV149-Pad24)") (class "Default")
      (node (ref "SV149") (pin "24") (pinfunction "24_24") (pintype "passive"))
    )
    (net (code "4511") (name "unconnected-(SV150-Pad1)") (class "Default")
      (node (ref "SV150") (pin "1") (pinfunction "1_1") (pintype "passive"))
    )
    (net (code "4512") (name "unconnected-(SV150-Pad2)") (class "Default")
      (node (ref "SV150") (pin "2") (pinfunction "2_2") (pintype "passive"))
    )
    (net (code "4513") (name "unconnected-(SV150-Pad3)") (class "Default")
      (node (ref "SV150") (pin "3") (pinfunction "3_3") (pintype "passive"))
    )
    (net (code "4514") (name "unconnected-(SV150-Pad4)") (class "Default")
      (node (ref "SV150") (pin "4") (pinfunction "4_4") (pintype "passive"))
    )
    (net (code "4515") (name "unconnected-(SV150-Pad5)") (class "Default")
      (node (ref "SV150") (pin "5") (pinfunction "5_5") (pintype "passive"))
    )
    (net (code "4516") (name "unconnected-(SV150-Pad6)") (class "Default")
      (node (ref "SV150") (pin "6") (pinfunction "6_6") (pintype "passive"))
    )
    (net (code "4517") (name "unconnected-(SV150-Pad7)") (class "Default")
      (node (ref "SV150") (pin "7") (pinfunction "7_7") (pintype "passive"))
    )
    (net (code "4518") (name "unconnected-(SV150-Pad8)") (class "Default")
      (node (ref "SV150") (pin "8") (pinfunction "8_8") (pintype "passive"))
    )
    (net (code "4519") (name "unconnected-(SV150-Pad9)") (class "Default")
      (node (ref "SV150") (pin "9") (pinfunction "9_9") (pintype "passive"))
    )
    (net (code "4520") (name "unconnected-(SV150-Pad10)") (class "Default")
      (node (ref "SV150") (pin "10") (pinfunction "10_10") (pintype "passive"))
    )
    (net (code "4521") (name "unconnected-(SV150-Pad11)") (class "Default")
      (node (ref "SV150") (pin "11") (pinfunction "11_11") (pintype "passive"))
    )
    (net (code "4522") (name "unconnected-(SV150-Pad12)") (class "Default")
      (node (ref "SV150") (pin "12") (pinfunction "12_12") (pintype "passive"))
    )
    (net (code "4523") (name "unconnected-(SV150-Pad13)") (class "Default")
      (node (ref "SV150") (pin "13") (pinfunction "13_13") (pintype "passive"))
    )
    (net (code "4524") (name "unconnected-(SV150-Pad14)") (class "Default")
      (node (ref "SV150") (pin "14") (pinfunction "14_14") (pintype "passive"))
    )
    (net (code "4525") (name "unconnected-(SV150-Pad15)") (class "Default")
      (node (ref "SV150") (pin "15") (pinfunction "15_15") (pintype "passive"))
    )
    (net (code "4526") (name "unconnected-(SV150-Pad16)") (class "Default")
      (node (ref "SV150") (pin "16") (pinfunction "16_16") (pintype "passive"))
    )
    (net (code "4527") (name "unconnected-(SV150-Pad17)") (class "Default")
      (node (ref "SV150") (pin "17") (pinfunction "17_17") (pintype "passive"))
    )
    (net (code "4528") (name "unconnected-(SV150-Pad18)") (class "Default")
      (node (ref "SV150") (pin "18") (pinfunction "18_18") (pintype "passive"))
    )
    (net (code "4529") (name "unconnected-(SV150-Pad19)") (class "Default")
      (node (ref "SV150") (pin "19") (pinfunction "19_19") (pintype "passive"))
    )
    (net (code "4530") (name "unconnected-(SV150-Pad20)") (class "Default")
      (node (ref "SV150") (pin "20") (pinfunction "20_20") (pintype "passive"))
    )
    (net (code "4531") (name "unconnected-(SV150-Pad21)") (class "Default")
      (node (ref "SV150") (pin "21") (pinfunction "21_21") (pintype "passive"))
    )
    (net (code "4532") (name "unconnected-(SV150-Pad22)") (class "Default")
      (node (ref "SV150") (pin "22") (pinfunction "22_22") (pintype "passive"))
    )
    (net (code "4533") (name "unconnected-(SV150-Pad23)") (class "Default")
      (node (ref "SV150") (pin "23") (pinfunction "23_23") (pintype "passive"))
    )
    (net (code "4534") (name "unconnected-(SV150-Pad24)") (class "Default")
      (node (ref "SV150") (pin "24") (pinfunction "24_24") (pintype "passive"))
    )
    (net (code "4535") (name "unconnected-(SV151-Pad1)") (class "Default")
      (node (ref "SV151") (pin "1") (pinfunction "1_1") (pintype "passive"))
    )
    (net (code "4536") (name "unconnected-(SV151-Pad2)") (class "Default")
      (node (ref "SV151") (pin "2") (pinfunction "2_2") (pintype "passive"))
    )
    (net (code "4537") (name "unconnected-(SV151-Pad3)") (class "Default")
      (node (ref "SV151") (pin "3") (pinfunction "3_3") (pintype "passive"))
    )
    (net (code "4538") (name "unconnected-(SV151-Pad4)") (class "Default")
      (node (ref "SV151") (pin "4") (pinfunction "4_4") (pintype "passive"))
    )
    (net (code "4539") (name "unconnected-(SV151-Pad5)") (class "Default")
      (node (ref "SV151") (pin "5") (pinfunction "5_5") (pintype "passive"))
    )
    (net (code "4540") (name "unconnected-(SV151-Pad6)") (class "Default")
      (node (ref "SV151") (pin "6") (pinfunction "6_6") (pintype "passive"))
    )
    (net (code "4541") (name "unconnected-(SV151-Pad7)") (class "Default")
      (node (ref "SV151") (pin "7") (pinfunction "7_7") (pintype "passive"))
    )
    (net (code "4542") (name "unconnected-(SV151-Pad8)") (class "Default")
      (node (ref "SV151") (pin "8") (pinfunction "8_8") (pintype "passive"))
    )
    (net (code "4543") (name "unconnected-(SV151-Pad9)") (class "Default")
      (node (ref "SV151") (pin "9") (pinfunction "9_9") (pintype "passive"))
    )
    (net (code "4544") (name "unconnected-(SV151-Pad10)") (class "Default")
      (node (ref "SV151") (pin "10") (pinfunction "10_10") (pintype "passive"))
    )
    (net (code "4545") (name "unconnected-(SV151-Pad11)") (class "Default")
      (node (ref "SV151") (pin "11") (pinfunction "11_11") (pintype "passive"))
    )
    (net (code "4546") (name "unconnected-(SV151-Pad12)") (class "Default")
      (node (ref "SV151") (pin "12") (pinfunction "12_12") (pintype "passive"))
    )
    (net (code "4547") (name "unconnected-(SV151-Pad13)") (class "Default")
      (node (ref "SV151") (pin "13") (pinfunction "13_13") (pintype "passive"))
    )
    (net (code "4548") (name "unconnected-(SV151-Pad14)") (class "Default")
      (node (ref "SV151") (pin "14") (pinfunction "14_14") (pintype "passive"))
    )
    (net (code "4549") (name "unconnected-(SV151-Pad15)") (class "Default")
      (node (ref "SV151") (pin "15") (pinfunction "15_15") (pintype "passive"))
    )
    (net (code "4550") (name "unconnected-(SV151-Pad16)") (class "Default")
      (node (ref "SV151") (pin "16") (pinfunction "16_16") (pintype "passive"))
    )
    (net (code "4551") (name "unconnected-(SV151-Pad17)") (class "Default")
      (node (ref "SV151") (pin "17") (pinfunction "17_17") (pintype "passive"))
    )
    (net (code "4552") (name "unconnected-(SV151-Pad18)") (class "Default")
      (node (ref "SV151") (pin "18") (pinfunction "18_18") (pintype "passive"))
    )
    (net (code "4553") (name "unconnected-(SV151-Pad19)") (class "Default")
      (node (ref "SV151") (pin "19") (pinfunction "19_19") (pintype "passive"))
    )
    (net (code "4554") (name "unconnected-(SV151-Pad20)") (class "Default")
      (node (ref "SV151") (pin "20") (pinfunction "20_20") (pintype "passive"))
    )
    (net (code "4555") (name "unconnected-(SV151-Pad21)") (class "Default")
      (node (ref "SV151") (pin "21") (pinfunction "21_21") (pintype "passive"))
    )
    (net (code "4556") (name "unconnected-(SV151-Pad22)") (class "Default")
      (node (ref "SV151") (pin "22") (pinfunction "22_22") (pintype "passive"))
    )
    (net (code "4557") (name "unconnected-(SV151-Pad23)") (class "Default")
      (node (ref "SV151") (pin "23") (pinfunction "23_23") (pintype "passive"))
    )
    (net (code "4558") (name "unconnected-(SV151-Pad24)") (class "Default")
      (node (ref "SV151") (pin "24") (pinfunction "24_24") (pintype "passive"))
    )
    (net (code "4559") (name "unconnected-(SV151-Pad25)") (class "Default")
      (node (ref "SV151") (pin "25") (pinfunction "25_25") (pintype "passive"))
    )
    (net (code "4560") (name "unconnected-(SV151-Pad26)") (class "Default")
      (node (ref "SV151") (pin "26") (pinfunction "26_26") (pintype "passive"))
    )
    (net (code "4561") (name "unconnected-(SV151-Pad27)") (class "Default")
      (node (ref "SV151") (pin "27") (pinfunction "27_27") (pintype "passive"))
    )
    (net (code "4562") (name "unconnected-(SV151-Pad28)") (class "Default")
      (node (ref "SV151") (pin "28") (pinfunction "28_28") (pintype "passive"))
    )
    (net (code "4563") (name "unconnected-(SV151-Pad29)") (class "Default")
      (node (ref "SV151") (pin "29") (pinfunction "29_29") (pintype "passive"))
    )
    (net (code "4564") (name "unconnected-(SV151-Pad30)") (class "Default")
      (node (ref "SV151") (pin "30") (pinfunction "30_30") (pintype "passive"))
    )
    (net (code "4565") (name "unconnected-(SV151-Pad31)") (class "Default")
      (node (ref "SV151") (pin "31") (pinfunction "31_31") (pintype "passive"))
    )
    (net (code "4566") (name "unconnected-(SV151-Pad32)") (class "Default")
      (node (ref "SV151") (pin "32") (pinfunction "32_32") (pintype "passive"))
    )
    (net (code "4567") (name "unconnected-(SV151-Pad33)") (class "Default")
      (node (ref "SV151") (pin "33") (pinfunction "33_33") (pintype "passive"))
    )
    (net (code "4568") (name "unconnected-(SV151-Pad34)") (class "Default")
      (node (ref "SV151") (pin "34") (pinfunction "34_34") (pintype "passive"))
    )
    (net (code "4569") (name "unconnected-(SV151-Pad35)") (class "Default")
      (node (ref "SV151") (pin "35") (pinfunction "35_35") (pintype "passive"))
    )
    (net (code "4570") (name "unconnected-(SV151-Pad36)") (class "Default")
      (node (ref "SV151") (pin "36") (pinfunction "36_36") (pintype "passive"))
    )
    (net (code "4571") (name "unconnected-(SV151-Pad37)") (class "Default")
      (node (ref "SV151") (pin "37") (pinfunction "37_37") (pintype "passive"))
    )
    (net (code "4572") (name "unconnected-(SV151-Pad38)") (class "Default")
      (node (ref "SV151") (pin "38") (pinfunction "38_38") (pintype "passive"))
    )
    (net (code "4573") (name "unconnected-(SV151-Pad39)") (class "Default")
      (node (ref "SV151") (pin "39") (pinfunction "39_39") (pintype "passive"))
    )
    (net (code "4574") (name "unconnected-(SV151-Pad40)") (class "Default")
      (node (ref "SV151") (pin "40") (pinfunction "40_40") (pintype "passive"))
    )
    (net (code "4575") (name "unconnected-(SV152-Pad1)") (class "Default")
      (node (ref "SV152") (pin "1") (pinfunction "1_1") (pintype "passive"))
    )
    (net (code "4576") (name "unconnected-(SV152-Pad2)") (class "Default")
      (node (ref "SV152") (pin "2") (pinfunction "2_2") (pintype "passive"))
    )
    (net (code "4577") (name "unconnected-(SV152-Pad3)") (class "Default")
      (node (ref "SV152") (pin "3") (pinfunction "3_3") (pintype "passive"))
    )
    (net (code "4578") (name "unconnected-(SV152-Pad4)") (class "Default")
      (node (ref "SV152") (pin "4") (pinfunction "4_4") (pintype "passive"))
    )
    (net (code "4579") (name "unconnected-(SV152-Pad5)") (class "Default")
      (node (ref "SV152") (pin "5") (pinfunction "5_5") (pintype "passive"))
    )
    (net (code "4580") (name "unconnected-(SV152-Pad6)") (class "Default")
      (node (ref "SV152") (pin "6") (pinfunction "6_6") (pintype "passive"))
    )
    (net (code "4581") (name "unconnected-(SV152-Pad7)") (class "Default")
      (node (ref "SV152") (pin "7") (pinfunction "7_7") (pintype "passive"))
    )
    (net (code "4582") (name "unconnected-(SV152-Pad8)") (class "Default")
      (node (ref "SV152") (pin "8") (pinfunction "8_8") (pintype "passive"))
    )
    (net (code "4583") (name "unconnected-(SV152-Pad9)") (class "Default")
      (node (ref "SV152") (pin "9") (pinfunction "9_9") (pintype "passive"))
    )
    (net (code "4584") (name "unconnected-(SV152-Pad10)") (class "Default")
      (node (ref "SV152") (pin "10") (pinfunction "10_10") (pintype "passive"))
    )
    (net (code "4585") (name "unconnected-(SV152-Pad11)") (class "Default")
      (node (ref "SV152") (pin "11") (pinfunction "11_11") (pintype "passive"))
    )
    (net (code "4586") (name "unconnected-(SV152-Pad12)") (class "Default")
      (node (ref "SV152") (pin "12") (pinfunction "12_12") (pintype "passive"))
    )
    (net (code "4587") (name "unconnected-(SV152-Pad13)") (class "Default")
      (node (ref "SV152") (pin "13") (pinfunction "13_13") (pintype "passive"))
    )
    (net (code "4588") (name "unconnected-(SV152-Pad14)") (class "Default")
      (node (ref "SV152") (pin "14") (pinfunction "14_14") (pintype "passive"))
    )
    (net (code "4589") (name "unconnected-(SV152-Pad15)") (class "Default")
      (node (ref "SV152") (pin "15") (pinfunction "15_15") (pintype "passive"))
    )
    (net (code "4590") (name "unconnected-(SV152-Pad16)") (class "Default")
      (node (ref "SV152") (pin "16") (pinfunction "16_16") (pintype "passive"))
    )
    (net (code "4591") (name "unconnected-(SV152-Pad17)") (class "Default")
      (node (ref "SV152") (pin "17") (pinfunction "17_17") (pintype "passive"))
    )
    (net (code "4592") (name "unconnected-(SV152-Pad18)") (class "Default")
      (node (ref "SV152") (pin "18") (pinfunction "18_18") (pintype "passive"))
    )
    (net (code "4593") (name "unconnected-(SV152-Pad19)") (class "Default")
      (node (ref "SV152") (pin "19") (pinfunction "19_19") (pintype "passive"))
    )
    (net (code "4594") (name "unconnected-(SV152-Pad20)") (class "Default")
      (node (ref "SV152") (pin "20") (pinfunction "20_20") (pintype "passive"))
    )
    (net (code "4595") (name "unconnected-(SV152-Pad21)") (class "Default")
      (node (ref "SV152") (pin "21") (pinfunction "21_21") (pintype "passive"))
    )
    (net (code "4596") (name "unconnected-(SV152-Pad22)") (class "Default")
      (node (ref "SV152") (pin "22") (pinfunction "22_22") (pintype "passive"))
    )
    (net (code "4597") (name "unconnected-(SV152-Pad23)") (class "Default")
      (node (ref "SV152") (pin "23") (pinfunction "23_23") (pintype "passive"))
    )
    (net (code "4598") (name "unconnected-(SV152-Pad24)") (class "Default")
      (node (ref "SV152") (pin "24") (pinfunction "24_24") (pintype "passive"))
    )
    (net (code "4599") (name "unconnected-(SV152-Pad25)") (class "Default")
      (node (ref "SV152") (pin "25") (pinfunction "25_25") (pintype "passive"))
    )
    (net (code "4600") (name "unconnected-(SV152-Pad26)") (class "Default")
      (node (ref "SV152") (pin "26") (pinfunction "26_26") (pintype "passive"))
    )
    (net (code "4601") (name "unconnected-(SV152-Pad27)") (class "Default")
      (node (ref "SV152") (pin "27") (pinfunction "27_27") (pintype "passive"))
    )
    (net (code "4602") (name "unconnected-(SV152-Pad28)") (class "Default")
      (node (ref "SV152") (pin "28") (pinfunction "28_28") (pintype "passive"))
    )
    (net (code "4603") (name "unconnected-(SV152-Pad29)") (class "Default")
      (node (ref "SV152") (pin "29") (pinfunction "29_29") (pintype "passive"))
    )
    (net (code "4604") (name "unconnected-(SV152-Pad30)") (class "Default")
      (node (ref "SV152") (pin "30") (pinfunction "30_30") (pintype "passive"))
    )
    (net (code "4605") (name "unconnected-(SV152-Pad31)") (class "Default")
      (node (ref "SV152") (pin "31") (pinfunction "31_31") (pintype "passive"))
    )
    (net (code "4606") (name "unconnected-(SV152-Pad32)") (class "Default")
      (node (ref "SV152") (pin "32") (pinfunction "32_32") (pintype "passive"))
    )
    (net (code "4607") (name "unconnected-(SV152-Pad33)") (class "Default")
      (node (ref "SV152") (pin "33") (pinfunction "33_33") (pintype "passive"))
    )
    (net (code "4608") (name "unconnected-(SV152-Pad34)") (class "Default")
      (node (ref "SV152") (pin "34") (pinfunction "34_34") (pintype "passive"))
    )
    (net (code "4609") (name "unconnected-(SV152-Pad35)") (class "Default")
      (node (ref "SV152") (pin "35") (pinfunction "35_35") (pintype "passive"))
    )
    (net (code "4610") (name "unconnected-(SV152-Pad36)") (class "Default")
      (node (ref "SV152") (pin "36") (pinfunction "36_36") (pintype "passive"))
    )
    (net (code "4611") (name "unconnected-(SV152-Pad37)") (class "Default")
      (node (ref "SV152") (pin "37") (pinfunction "37_37") (pintype "passive"))
    )
    (net (code "4612") (name "unconnected-(SV152-Pad38)") (class "Default")
      (node (ref "SV152") (pin "38") (pinfunction "38_38") (pintype "passive"))
    )
    (net (code "4613") (name "unconnected-(SV152-Pad39)") (class "Default")
      (node (ref "SV152") (pin "39") (pinfunction "39_39") (pintype "passive"))
    )
    (net (code "4614") (name "unconnected-(SV152-Pad40)") (class "Default")
      (node (ref "SV152") (pin "40") (pinfunction "40_40") (pintype "passive"))
    )
    (net (code "4615") (name "unconnected-(SV153-Pad1)") (class "Default")
      (node (ref "SV153") (pin "1") (pinfunction "1_1") (pintype "passive"))
    )
    (net (code "4616") (name "unconnected-(SV153-Pad2)") (class "Default")
      (node (ref "SV153") (pin "2") (pinfunction "2_2") (pintype "passive"))
    )
    (net (code "4617") (name "unconnected-(SV153-Pad3)") (class "Default")
      (node (ref "SV153") (pin "3") (pinfunction "3_3") (pintype "passive"))
    )
    (net (code "4618") (name "unconnected-(SV153-Pad4)") (class "Default")
      (node (ref "SV153") (pin "4") (pinfunction "4_4") (pintype "passive"))
    )
    (net (code "4619") (name "unconnected-(SV153-Pad5)") (class "Default")
      (node (ref "SV153") (pin "5") (pinfunction "5_5") (pintype "passive"))
    )
    (net (code "4620") (name "unconnected-(SV153-Pad6)") (class "Default")
      (node (ref "SV153") (pin "6") (pinfunction "6_6") (pintype "passive"))
    )
    (net (code "4621") (name "unconnected-(SV153-Pad7)") (class "Default")
      (node (ref "SV153") (pin "7") (pinfunction "7_7") (pintype "passive"))
    )
    (net (code "4622") (name "unconnected-(SV153-Pad8)") (class "Default")
      (node (ref "SV153") (pin "8") (pinfunction "8_8") (pintype "passive"))
    )
    (net (code "4623") (name "unconnected-(SV153-Pad9)") (class "Default")
      (node (ref "SV153") (pin "9") (pinfunction "9_9") (pintype "passive"))
    )
    (net (code "4624") (name "unconnected-(SV153-Pad10)") (class "Default")
      (node (ref "SV153") (pin "10") (pinfunction "10_10") (pintype "passive"))
    )
    (net (code "4625") (name "unconnected-(SV153-Pad11)") (class "Default")
      (node (ref "SV153") (pin "11") (pinfunction "11_11") (pintype "passive"))
    )
    (net (code "4626") (name "unconnected-(SV153-Pad12)") (class "Default")
      (node (ref "SV153") (pin "12") (pinfunction "12_12") (pintype "passive"))
    )
    (net (code "4627") (name "unconnected-(SV153-Pad13)") (class "Default")
      (node (ref "SV153") (pin "13") (pinfunction "13_13") (pintype "passive"))
    )
    (net (code "4628") (name "unconnected-(SV153-Pad14)") (class "Default")
      (node (ref "SV153") (pin "14") (pinfunction "14_14") (pintype "passive"))
    )
    (net (code "4629") (name "unconnected-(SV153-Pad15)") (class "Default")
      (node (ref "SV153") (pin "15") (pinfunction "15_15") (pintype "passive"))
    )
    (net (code "4630") (name "unconnected-(SV153-Pad16)") (class "Default")
      (node (ref "SV153") (pin "16") (pinfunction "16_16") (pintype "passive"))
    )
    (net (code "4631") (name "unconnected-(SV153-Pad17)") (class "Default")
      (node (ref "SV153") (pin "17") (pinfunction "17_17") (pintype "passive"))
    )
    (net (code "4632") (name "unconnected-(SV153-Pad18)") (class "Default")
      (node (ref "SV153") (pin "18") (pinfunction "18_18") (pintype "passive"))
    )
    (net (code "4633") (name "unconnected-(SV153-Pad19)") (class "Default")
      (node (ref "SV153") (pin "19") (pinfunction "19_19") (pintype "passive"))
    )
    (net (code "4634") (name "unconnected-(SV153-Pad20)") (class "Default")
      (node (ref "SV153") (pin "20") (pinfunction "20_20") (pintype "passive"))
    )
    (net (code "4635") (name "unconnected-(SV153-Pad21)") (class "Default")
      (node (ref "SV153") (pin "21") (pinfunction "21_21") (pintype "passive"))
    )
    (net (code "4636") (name "unconnected-(SV153-Pad22)") (class "Default")
      (node (ref "SV153") (pin "22") (pinfunction "22_22") (pintype "passive"))
    )
    (net (code "4637") (name "unconnected-(SV153-Pad23)") (class "Default")
      (node (ref "SV153") (pin "23") (pinfunction "23_23") (pintype "passive"))
    )
    (net (code "4638") (name "unconnected-(SV153-Pad24)") (class "Default")
      (node (ref "SV153") (pin "24") (pinfunction "24_24") (pintype "passive"))
    )
    (net (code "4639") (name "unconnected-(SV153-Pad25)") (class "Default")
      (node (ref "SV153") (pin "25") (pinfunction "25_25") (pintype "passive"))
    )
    (net (code "4640") (name "unconnected-(SV153-Pad26)") (class "Default")
      (node (ref "SV153") (pin "26") (pinfunction "26_26") (pintype "passive"))
    )
    (net (code "4641") (name "unconnected-(SV153-Pad27)") (class "Default")
      (node (ref "SV153") (pin "27") (pinfunction "27_27") (pintype "passive"))
    )
    (net (code "4642") (name "unconnected-(SV153-Pad28)") (class "Default")
      (node (ref "SV153") (pin "28") (pinfunction "28_28") (pintype "passive"))
    )
    (net (code "4643") (name "unconnected-(SV153-Pad29)") (class "Default")
      (node (ref "SV153") (pin "29") (pinfunction "29_29") (pintype "passive"))
    )
    (net (code "4644") (name "unconnected-(SV153-Pad30)") (class "Default")
      (node (ref "SV153") (pin "30") (pinfunction "30_30") (pintype "passive"))
    )
    (net (code "4645") (name "unconnected-(SV153-Pad31)") (class "Default")
      (node (ref "SV153") (pin "31") (pinfunction "31_31") (pintype "passive"))
    )
    (net (code "4646") (name "unconnected-(SV153-Pad32)") (class "Default")
      (node (ref "SV153") (pin "32") (pinfunction "32_32") (pintype "passive"))
    )
    (net (code "4647") (name "unconnected-(SV153-Pad33)") (class "Default")
      (node (ref "SV153") (pin "33") (pinfunction "33_33") (pintype "passive"))
    )
    (net (code "4648") (name "unconnected-(SV153-Pad34)") (class "Default")
      (node (ref "SV153") (pin "34") (pinfunction "34_34") (pintype "passive"))
    )
    (net (code "4649") (name "unconnected-(SV153-Pad35)") (class "Default")
      (node (ref "SV153") (pin "35") (pinfunction "35_35") (pintype "passive"))
    )
    (net (code "4650") (name "unconnected-(SV153-Pad36)") (class "Default")
      (node (ref "SV153") (pin "36") (pinfunction "36_36") (pintype "passive"))
    )
    (net (code "4651") (name "unconnected-(SV153-Pad37)") (class "Default")
      (node (ref "SV153") (pin "37") (pinfunction "37_37") (pintype "passive"))
    )
    (net (code "4652") (name "unconnected-(SV153-Pad38)") (class "Default")
      (node (ref "SV153") (pin "38") (pinfunction "38_38") (pintype "passive"))
    )
    (net (code "4653") (name "unconnected-(SV153-Pad39)") (class "Default")
      (node (ref "SV153") (pin "39") (pinfunction "39_39") (pintype "passive"))
    )
    (net (code "4654") (name "unconnected-(SV153-Pad40)") (class "Default")
      (node (ref "SV153") (pin "40") (pinfunction "40_40") (pintype "passive"))
    )
    (net (code "4655") (name "unconnected-(SV154-Pad1)") (class "Default")
      (node (ref "SV154") (pin "1") (pinfunction "1_1") (pintype "passive"))
    )
    (net (code "4656") (name "unconnected-(SV154-Pad2)") (class "Default")
      (node (ref "SV154") (pin "2") (pinfunction "2_2") (pintype "passive"))
    )
    (net (code "4657") (name "unconnected-(SV154-Pad3)") (class "Default")
      (node (ref "SV154") (pin "3") (pinfunction "3_3") (pintype "passive"))
    )
    (net (code "4658") (name "unconnected-(SV154-Pad4)") (class "Default")
      (node (ref "SV154") (pin "4") (pinfunction "4_4") (pintype "passive"))
    )
    (net (code "4659") (name "unconnected-(SV154-Pad5)") (class "Default")
      (node (ref "SV154") (pin "5") (pinfunction "5_5") (pintype "passive"))
    )
    (net (code "4660") (name "unconnected-(SV154-Pad6)") (class "Default")
      (node (ref "SV154") (pin "6") (pinfunction "6_6") (pintype "passive"))
    )
    (net (code "4661") (name "unconnected-(SV154-Pad7)") (class "Default")
      (node (ref "SV154") (pin "7") (pinfunction "7_7") (pintype "passive"))
    )
    (net (code "4662") (name "unconnected-(SV154-Pad8)") (class "Default")
      (node (ref "SV154") (pin "8") (pinfunction "8_8") (pintype "passive"))
    )
    (net (code "4663") (name "unconnected-(SV154-Pad9)") (class "Default")
      (node (ref "SV154") (pin "9") (pinfunction "9_9") (pintype "passive"))
    )
    (net (code "4664") (name "unconnected-(SV154-Pad10)") (class "Default")
      (node (ref "SV154") (pin "10") (pinfunction "10_10") (pintype "passive"))
    )
    (net (code "4665") (name "unconnected-(SV154-Pad11)") (class "Default")
      (node (ref "SV154") (pin "11") (pinfunction "11_11") (pintype "passive"))
    )
    (net (code "4666") (name "unconnected-(SV154-Pad12)") (class "Default")
      (node (ref "SV154") (pin "12") (pinfunction "12_12") (pintype "passive"))
    )
    (net (code "4667") (name "unconnected-(SV154-Pad13)") (class "Default")
      (node (ref "SV154") (pin "13") (pinfunction "13_13") (pintype "passive"))
    )
    (net (code "4668") (name "unconnected-(SV154-Pad14)") (class "Default")
      (node (ref "SV154") (pin "14") (pinfunction "14_14") (pintype "passive"))
    )
    (net (code "4669") (name "unconnected-(SV154-Pad15)") (class "Default")
      (node (ref "SV154") (pin "15") (pinfunction "15_15") (pintype "passive"))
    )
    (net (code "4670") (name "unconnected-(SV154-Pad16)") (class "Default")
      (node (ref "SV154") (pin "16") (pinfunction "16_16") (pintype "passive"))
    )
    (net (code "4671") (name "unconnected-(SV154-Pad17)") (class "Default")
      (node (ref "SV154") (pin "17") (pinfunction "17_17") (pintype "passive"))
    )
    (net (code "4672") (name "unconnected-(SV154-Pad18)") (class "Default")
      (node (ref "SV154") (pin "18") (pinfunction "18_18") (pintype "passive"))
    )
    (net (code "4673") (name "unconnected-(SV154-Pad19)") (class "Default")
      (node (ref "SV154") (pin "19") (pinfunction "19_19") (pintype "passive"))
    )
    (net (code "4674") (name "unconnected-(SV154-Pad20)") (class "Default")
      (node (ref "SV154") (pin "20") (pinfunction "20_20") (pintype "passive"))
    )
    (net (code "4675") (name "unconnected-(SV154-Pad21)") (class "Default")
      (node (ref "SV154") (pin "21") (pinfunction "21_21") (pintype "passive"))
    )
    (net (code "4676") (name "unconnected-(SV154-Pad22)") (class "Default")
      (node (ref "SV154") (pin "22") (pinfunction "22_22") (pintype "passive"))
    )
    (net (code "4677") (name "unconnected-(SV154-Pad23)") (class "Default")
      (node (ref "SV154") (pin "23") (pinfunction "23_23") (pintype "passive"))
    )
    (net (code "4678") (name "unconnected-(SV154-Pad24)") (class "Default")
      (node (ref "SV154") (pin "24") (pinfunction "24_24") (pintype "passive"))
    )
    (net (code "4679") (name "unconnected-(SV154-Pad25)") (class "Default")
      (node (ref "SV154") (pin "25") (pinfunction "25_25") (pintype "passive"))
    )
    (net (code "4680") (name "unconnected-(SV154-Pad26)") (class "Default")
      (node (ref "SV154") (pin "26") (pinfunction "26_26") (pintype "passive"))
    )
    (net (code "4681") (name "unconnected-(SV154-Pad27)") (class "Default")
      (node (ref "SV154") (pin "27") (pinfunction "27_27") (pintype "passive"))
    )
    (net (code "4682") (name "unconnected-(SV154-Pad28)") (class "Default")
      (node (ref "SV154") (pin "28") (pinfunction "28_28") (pintype "passive"))
    )
    (net (code "4683") (name "unconnected-(SV154-Pad29)") (class "Default")
      (node (ref "SV154") (pin "29") (pinfunction "29_29") (pintype "passive"))
    )
    (net (code "4684") (name "unconnected-(SV154-Pad30)") (class "Default")
      (node (ref "SV154") (pin "30") (pinfunction "30_30") (pintype "passive"))
    )
    (net (code "4685") (name "unconnected-(SV154-Pad31)") (class "Default")
      (node (ref "SV154") (pin "31") (pinfunction "31_31") (pintype "passive"))
    )
    (net (code "4686") (name "unconnected-(SV154-Pad32)") (class "Default")
      (node (ref "SV154") (pin "32") (pinfunction "32_32") (pintype "passive"))
    )
    (net (code "4687") (name "unconnected-(SV154-Pad33)") (class "Default")
      (node (ref "SV154") (pin "33") (pinfunction "33_33") (pintype "passive"))
    )
    (net (code "4688") (name "unconnected-(SV154-Pad34)") (class "Default")
      (node (ref "SV154") (pin "34") (pinfunction "34_34") (pintype "passive"))
    )
    (net (code "4689") (name "unconnected-(SV154-Pad35)") (class "Default")
      (node (ref "SV154") (pin "35") (pinfunction "35_35") (pintype "passive"))
    )
    (net (code "4690") (name "unconnected-(SV154-Pad36)") (class "Default")
      (node (ref "SV154") (pin "36") (pinfunction "36_36") (pintype "passive"))
    )
    (net (code "4691") (name "unconnected-(SV154-Pad37)") (class "Default")
      (node (ref "SV154") (pin "37") (pinfunction "37_37") (pintype "passive"))
    )
    (net (code "4692") (name "unconnected-(SV154-Pad38)") (class "Default")
      (node (ref "SV154") (pin "38") (pinfunction "38_38") (pintype "passive"))
    )
    (net (code "4693") (name "unconnected-(SV154-Pad39)") (class "Default")
      (node (ref "SV154") (pin "39") (pinfunction "39_39") (pintype "passive"))
    )
    (net (code "4694") (name "unconnected-(SV154-Pad40)") (class "Default")
      (node (ref "SV154") (pin "40") (pinfunction "40_40") (pintype "passive"))
    )
    (net (code "4695") (name "unconnected-(SV155-Pad1)") (class "Default")
      (node (ref "SV155") (pin "1") (pinfunction "1_1") (pintype "passive"))
    )
    (net (code "4696") (name "unconnected-(SV155-Pad2)") (class "Default")
      (node (ref "SV155") (pin "2") (pinfunction "2_2") (pintype "passive"))
    )
    (net (code "4697") (name "unconnected-(SV155-Pad3)") (class "Default")
      (node (ref "SV155") (pin "3") (pinfunction "3_3") (pintype "passive"))
    )
    (net (code "4698") (name "unconnected-(SV155-Pad4)") (class "Default")
      (node (ref "SV155") (pin "4") (pinfunction "4_4") (pintype "passive"))
    )
    (net (code "4699") (name "unconnected-(SV155-Pad5)") (class "Default")
      (node (ref "SV155") (pin "5") (pinfunction "5_5") (pintype "passive"))
    )
    (net (code "4700") (name "unconnected-(SV155-Pad6)") (class "Default")
      (node (ref "SV155") (pin "6") (pinfunction "6_6") (pintype "passive"))
    )
    (net (code "4701") (name "unconnected-(SV155-Pad7)") (class "Default")
      (node (ref "SV155") (pin "7") (pinfunction "7_7") (pintype "passive"))
    )
    (net (code "4702") (name "unconnected-(SV155-Pad8)") (class "Default")
      (node (ref "SV155") (pin "8") (pinfunction "8_8") (pintype "passive"))
    )
    (net (code "4703") (name "unconnected-(SV155-Pad9)") (class "Default")
      (node (ref "SV155") (pin "9") (pinfunction "9_9") (pintype "passive"))
    )
    (net (code "4704") (name "unconnected-(SV155-Pad10)") (class "Default")
      (node (ref "SV155") (pin "10") (pinfunction "10_10") (pintype "passive"))
    )
    (net (code "4705") (name "unconnected-(SV155-Pad11)") (class "Default")
      (node (ref "SV155") (pin "11") (pinfunction "11_11") (pintype "passive"))
    )
    (net (code "4706") (name "unconnected-(SV155-Pad12)") (class "Default")
      (node (ref "SV155") (pin "12") (pinfunction "12_12") (pintype "passive"))
    )
    (net (code "4707") (name "unconnected-(SV155-Pad13)") (class "Default")
      (node (ref "SV155") (pin "13") (pinfunction "13_13") (pintype "passive"))
    )
    (net (code "4708") (name "unconnected-(SV155-Pad14)") (class "Default")
      (node (ref "SV155") (pin "14") (pinfunction "14_14") (pintype "passive"))
    )
    (net (code "4709") (name "unconnected-(SV155-Pad15)") (class "Default")
      (node (ref "SV155") (pin "15") (pinfunction "15_15") (pintype "passive"))
    )
    (net (code "4710") (name "unconnected-(SV155-Pad16)") (class "Default")
      (node (ref "SV155") (pin "16") (pinfunction "16_16") (pintype "passive"))
    )
    (net (code "4711") (name "unconnected-(SV155-Pad17)") (class "Default")
      (node (ref "SV155") (pin "17") (pinfunction "17_17") (pintype "passive"))
    )
    (net (code "4712") (name "unconnected-(SV155-Pad18)") (class "Default")
      (node (ref "SV155") (pin "18") (pinfunction "18_18") (pintype "passive"))
    )
    (net (code "4713") (name "unconnected-(SV155-Pad19)") (class "Default")
      (node (ref "SV155") (pin "19") (pinfunction "19_19") (pintype "passive"))
    )
    (net (code "4714") (name "unconnected-(SV155-Pad20)") (class "Default")
      (node (ref "SV155") (pin "20") (pinfunction "20_20") (pintype "passive"))
    )
    (net (code "4715") (name "unconnected-(SV155-Pad21)") (class "Default")
      (node (ref "SV155") (pin "21") (pinfunction "21_21") (pintype "passive"))
    )
    (net (code "4716") (name "unconnected-(SV155-Pad22)") (class "Default")
      (node (ref "SV155") (pin "22") (pinfunction "22_22") (pintype "passive"))
    )
    (net (code "4717") (name "unconnected-(SV155-Pad23)") (class "Default")
      (node (ref "SV155") (pin "23") (pinfunction "23_23") (pintype "passive"))
    )
    (net (code "4718") (name "unconnected-(SV155-Pad24)") (class "Default")
      (node (ref "SV155") (pin "24") (pinfunction "24_24") (pintype "passive"))
    )
    (net (code "4719") (name "unconnected-(SV156-Pad1)") (class "Default")
      (node (ref "SV156") (pin "1") (pinfunction "1_1") (pintype "passive"))
    )
    (net (code "4720") (name "unconnected-(SV156-Pad2)") (class "Default")
      (node (ref "SV156") (pin "2") (pinfunction "2_2") (pintype "passive"))
    )
    (net (code "4721") (name "unconnected-(SV156-Pad3)") (class "Default")
      (node (ref "SV156") (pin "3") (pinfunction "3_3") (pintype "passive"))
    )
    (net (code "4722") (name "unconnected-(SV156-Pad4)") (class "Default")
      (node (ref "SV156") (pin "4") (pinfunction "4_4") (pintype "passive"))
    )
    (net (code "4723") (name "unconnected-(SV156-Pad5)") (class "Default")
      (node (ref "SV156") (pin "5") (pinfunction "5_5") (pintype "passive"))
    )
    (net (code "4724") (name "unconnected-(SV156-Pad6)") (class "Default")
      (node (ref "SV156") (pin "6") (pinfunction "6_6") (pintype "passive"))
    )
    (net (code "4725") (name "unconnected-(SV156-Pad7)") (class "Default")
      (node (ref "SV156") (pin "7") (pinfunction "7_7") (pintype "passive"))
    )
    (net (code "4726") (name "unconnected-(SV156-Pad8)") (class "Default")
      (node (ref "SV156") (pin "8") (pinfunction "8_8") (pintype "passive"))
    )
    (net (code "4727") (name "unconnected-(SV156-Pad9)") (class "Default")
      (node (ref "SV156") (pin "9") (pinfunction "9_9") (pintype "passive"))
    )
    (net (code "4728") (name "unconnected-(SV156-Pad10)") (class "Default")
      (node (ref "SV156") (pin "10") (pinfunction "10_10") (pintype "passive"))
    )
    (net (code "4729") (name "unconnected-(SV156-Pad11)") (class "Default")
      (node (ref "SV156") (pin "11") (pinfunction "11_11") (pintype "passive"))
    )
    (net (code "4730") (name "unconnected-(SV156-Pad12)") (class "Default")
      (node (ref "SV156") (pin "12") (pinfunction "12_12") (pintype "passive"))
    )
    (net (code "4731") (name "unconnected-(SV156-Pad13)") (class "Default")
      (node (ref "SV156") (pin "13") (pinfunction "13_13") (pintype "passive"))
    )
    (net (code "4732") (name "unconnected-(SV156-Pad14)") (class "Default")
      (node (ref "SV156") (pin "14") (pinfunction "14_14") (pintype "passive"))
    )
    (net (code "4733") (name "unconnected-(SV156-Pad15)") (class "Default")
      (node (ref "SV156") (pin "15") (pinfunction "15_15") (pintype "passive"))
    )
    (net (code "4734") (name "unconnected-(SV156-Pad16)") (class "Default")
      (node (ref "SV156") (pin "16") (pinfunction "16_16") (pintype "passive"))
    )
    (net (code "4735") (name "unconnected-(SV156-Pad17)") (class "Default")
      (node (ref "SV156") (pin "17") (pinfunction "17_17") (pintype "passive"))
    )
    (net (code "4736") (name "unconnected-(SV156-Pad18)") (class "Default")
      (node (ref "SV156") (pin "18") (pinfunction "18_18") (pintype "passive"))
    )
    (net (code "4737") (name "unconnected-(SV156-Pad19)") (class "Default")
      (node (ref "SV156") (pin "19") (pinfunction "19_19") (pintype "passive"))
    )
    (net (code "4738") (name "unconnected-(SV156-Pad20)") (class "Default")
      (node (ref "SV156") (pin "20") (pinfunction "20_20") (pintype "passive"))
    )
    (net (code "4739") (name "unconnected-(SV156-Pad21)") (class "Default")
      (node (ref "SV156") (pin "21") (pinfunction "21_21") (pintype "passive"))
    )
    (net (code "4740") (name "unconnected-(SV156-Pad22)") (class "Default")
      (node (ref "SV156") (pin "22") (pinfunction "22_22") (pintype "passive"))
    )
    (net (code "4741") (name "unconnected-(SV156-Pad23)") (class "Default")
      (node (ref "SV156") (pin "23") (pinfunction "23_23") (pintype "passive"))
    )
    (net (code "4742") (name "unconnected-(SV156-Pad24)") (class "Default")
      (node (ref "SV156") (pin "24") (pinfunction "24_24") (pintype "passive"))
    )
    (net (code "4743") (name "unconnected-(SV157-Pad1)") (class "Default")
      (node (ref "SV157") (pin "1") (pinfunction "1_1") (pintype "passive"))
    )
    (net (code "4744") (name "unconnected-(SV157-Pad2)") (class "Default")
      (node (ref "SV157") (pin "2") (pinfunction "2_2") (pintype "passive"))
    )
    (net (code "4745") (name "unconnected-(SV157-Pad3)") (class "Default")
      (node (ref "SV157") (pin "3") (pinfunction "3_3") (pintype "passive"))
    )
    (net (code "4746") (name "unconnected-(SV157-Pad4)") (class "Default")
      (node (ref "SV157") (pin "4") (pinfunction "4_4") (pintype "passive"))
    )
    (net (code "4747") (name "unconnected-(SV157-Pad5)") (class "Default")
      (node (ref "SV157") (pin "5") (pinfunction "5_5") (pintype "passive"))
    )
    (net (code "4748") (name "unconnected-(SV157-Pad6)") (class "Default")
      (node (ref "SV157") (pin "6") (pinfunction "6_6") (pintype "passive"))
    )
    (net (code "4749") (name "unconnected-(SV157-Pad7)") (class "Default")
      (node (ref "SV157") (pin "7") (pinfunction "7_7") (pintype "passive"))
    )
    (net (code "4750") (name "unconnected-(SV157-Pad8)") (class "Default")
      (node (ref "SV157") (pin "8") (pinfunction "8_8") (pintype "passive"))
    )
    (net (code "4751") (name "unconnected-(SV157-Pad9)") (class "Default")
      (node (ref "SV157") (pin "9") (pinfunction "9_9") (pintype "passive"))
    )
    (net (code "4752") (name "unconnected-(SV157-Pad10)") (class "Default")
      (node (ref "SV157") (pin "10") (pinfunction "10_10") (pintype "passive"))
    )
    (net (code "4753") (name "unconnected-(SV157-Pad11)") (class "Default")
      (node (ref "SV157") (pin "11") (pinfunction "11_11") (pintype "passive"))
    )
    (net (code "4754") (name "unconnected-(SV157-Pad12)") (class "Default")
      (node (ref "SV157") (pin "12") (pinfunction "12_12") (pintype "passive"))
    )
    (net (code "4755") (name "unconnected-(SV157-Pad13)") (class "Default")
      (node (ref "SV157") (pin "13") (pinfunction "13_13") (pintype "passive"))
    )
    (net (code "4756") (name "unconnected-(SV157-Pad14)") (class "Default")
      (node (ref "SV157") (pin "14") (pinfunction "14_14") (pintype "passive"))
    )
    (net (code "4757") (name "unconnected-(SV157-Pad15)") (class "Default")
      (node (ref "SV157") (pin "15") (pinfunction "15_15") (pintype "passive"))
    )
    (net (code "4758") (name "unconnected-(SV157-Pad16)") (class "Default")
      (node (ref "SV157") (pin "16") (pinfunction "16_16") (pintype "passive"))
    )
    (net (code "4759") (name "unconnected-(SV157-Pad17)") (class "Default")
      (node (ref "SV157") (pin "17") (pinfunction "17_17") (pintype "passive"))
    )
    (net (code "4760") (name "unconnected-(SV157-Pad18)") (class "Default")
      (node (ref "SV157") (pin "18") (pinfunction "18_18") (pintype "passive"))
    )
    (net (code "4761") (name "unconnected-(SV157-Pad19)") (class "Default")
      (node (ref "SV157") (pin "19") (pinfunction "19_19") (pintype "passive"))
    )
    (net (code "4762") (name "unconnected-(SV157-Pad20)") (class "Default")
      (node (ref "SV157") (pin "20") (pinfunction "20_20") (pintype "passive"))
    )
    (net (code "4763") (name "unconnected-(SV157-Pad21)") (class "Default")
      (node (ref "SV157") (pin "21") (pinfunction "21_21") (pintype "passive"))
    )
    (net (code "4764") (name "unconnected-(SV157-Pad22)") (class "Default")
      (node (ref "SV157") (pin "22") (pinfunction "22_22") (pintype "passive"))
    )
    (net (code "4765") (name "unconnected-(SV157-Pad23)") (class "Default")
      (node (ref "SV157") (pin "23") (pinfunction "23_23") (pintype "passive"))
    )
    (net (code "4766") (name "unconnected-(SV157-Pad24)") (class "Default")
      (node (ref "SV157") (pin "24") (pinfunction "24_24") (pintype "passive"))
    )
    (net (code "4767") (name "unconnected-(SV158-Pad1)") (class "Default")
      (node (ref "SV158") (pin "1") (pinfunction "1_1") (pintype "passive"))
    )
    (net (code "4768") (name "unconnected-(SV158-Pad2)") (class "Default")
      (node (ref "SV158") (pin "2") (pinfunction "2_2") (pintype "passive"))
    )
    (net (code "4769") (name "unconnected-(SV158-Pad3)") (class "Default")
      (node (ref "SV158") (pin "3") (pinfunction "3_3") (pintype "passive"))
    )
    (net (code "4770") (name "unconnected-(SV158-Pad4)") (class "Default")
      (node (ref "SV158") (pin "4") (pinfunction "4_4") (pintype "passive"))
    )
    (net (code "4771") (name "unconnected-(SV158-Pad5)") (class "Default")
      (node (ref "SV158") (pin "5") (pinfunction "5_5") (pintype "passive"))
    )
    (net (code "4772") (name "unconnected-(SV158-Pad6)") (class "Default")
      (node (ref "SV158") (pin "6") (pinfunction "6_6") (pintype "passive"))
    )
    (net (code "4773") (name "unconnected-(SV158-Pad7)") (class "Default")
      (node (ref "SV158") (pin "7") (pinfunction "7_7") (pintype "passive"))
    )
    (net (code "4774") (name "unconnected-(SV158-Pad8)") (class "Default")
      (node (ref "SV158") (pin "8") (pinfunction "8_8") (pintype "passive"))
    )
    (net (code "4775") (name "unconnected-(SV158-Pad9)") (class "Default")
      (node (ref "SV158") (pin "9") (pinfunction "9_9") (pintype "passive"))
    )
    (net (code "4776") (name "unconnected-(SV158-Pad10)") (class "Default")
      (node (ref "SV158") (pin "10") (pinfunction "10_10") (pintype "passive"))
    )
    (net (code "4777") (name "unconnected-(SV158-Pad11)") (class "Default")
      (node (ref "SV158") (pin "11") (pinfunction "11_11") (pintype "passive"))
    )
    (net (code "4778") (name "unconnected-(SV158-Pad12)") (class "Default")
      (node (ref "SV158") (pin "12") (pinfunction "12_12") (pintype "passive"))
    )
    (net (code "4779") (name "unconnected-(SV158-Pad13)") (class "Default")
      (node (ref "SV158") (pin "13") (pinfunction "13_13") (pintype "passive"))
    )
    (net (code "4780") (name "unconnected-(SV158-Pad14)") (class "Default")
      (node (ref "SV158") (pin "14") (pinfunction "14_14") (pintype "passive"))
    )
    (net (code "4781") (name "unconnected-(SV158-Pad15)") (class "Default")
      (node (ref "SV158") (pin "15") (pinfunction "15_15") (pintype "passive"))
    )
    (net (code "4782") (name "unconnected-(SV158-Pad16)") (class "Default")
      (node (ref "SV158") (pin "16") (pinfunction "16_16") (pintype "passive"))
    )
    (net (code "4783") (name "unconnected-(SV158-Pad17)") (class "Default")
      (node (ref "SV158") (pin "17") (pinfunction "17_17") (pintype "passive"))
    )
    (net (code "4784") (name "unconnected-(SV158-Pad18)") (class "Default")
      (node (ref "SV158") (pin "18") (pinfunction "18_18") (pintype "passive"))
    )
    (net (code "4785") (name "unconnected-(SV158-Pad19)") (class "Default")
      (node (ref "SV158") (pin "19") (pinfunction "19_19") (pintype "passive"))
    )
    (net (code "4786") (name "unconnected-(SV158-Pad20)") (class "Default")
      (node (ref "SV158") (pin "20") (pinfunction "20_20") (pintype "passive"))
    )
    (net (code "4787") (name "unconnected-(SV158-Pad21)") (class "Default")
      (node (ref "SV158") (pin "21") (pinfunction "21_21") (pintype "passive"))
    )
    (net (code "4788") (name "unconnected-(SV158-Pad22)") (class "Default")
      (node (ref "SV158") (pin "22") (pinfunction "22_22") (pintype "passive"))
    )
    (net (code "4789") (name "unconnected-(SV158-Pad23)") (class "Default")
      (node (ref "SV158") (pin "23") (pinfunction "23_23") (pintype "passive"))
    )
    (net (code "4790") (name "unconnected-(SV158-Pad24)") (class "Default")
      (node (ref "SV158") (pin "24") (pinfunction "24_24") (pintype "passive"))
    )
    (net (code "4791") (name "unconnected-(SV159-Pad1)") (class "Default")
      (node (ref "SV159") (pin "1") (pinfunction "1_1") (pintype "passive"))
    )
    (net (code "4792") (name "unconnected-(SV159-Pad2)") (class "Default")
      (node (ref "SV159") (pin "2") (pinfunction "2_2") (pintype "passive"))
    )
    (net (code "4793") (name "unconnected-(SV159-Pad3)") (class "Default")
      (node (ref "SV159") (pin "3") (pinfunction "3_3") (pintype "passive"))
    )
    (net (code "4794") (name "unconnected-(SV159-Pad4)") (class "Default")
      (node (ref "SV159") (pin "4") (pinfunction "4_4") (pintype "passive"))
    )
    (net (code "4795") (name "unconnected-(SV159-Pad5)") (class "Default")
      (node (ref "SV159") (pin "5") (pinfunction "5_5") (pintype "passive"))
    )
    (net (code "4796") (name "unconnected-(SV159-Pad6)") (class "Default")
      (node (ref "SV159") (pin "6") (pinfunction "6_6") (pintype "passive"))
    )
    (net (code "4797") (name "unconnected-(SV159-Pad7)") (class "Default")
      (node (ref "SV159") (pin "7") (pinfunction "7_7") (pintype "passive"))
    )
    (net (code "4798") (name "unconnected-(SV159-Pad8)") (class "Default")
      (node (ref "SV159") (pin "8") (pinfunction "8_8") (pintype "passive"))
    )
    (net (code "4799") (name "unconnected-(SV159-Pad9)") (class "Default")
      (node (ref "SV159") (pin "9") (pinfunction "9_9") (pintype "passive"))
    )
    (net (code "4800") (name "unconnected-(SV159-Pad10)") (class "Default")
      (node (ref "SV159") (pin "10") (pinfunction "10_10") (pintype "passive"))
    )
    (net (code "4801") (name "unconnected-(SV159-Pad11)") (class "Default")
      (node (ref "SV159") (pin "11") (pinfunction "11_11") (pintype "passive"))
    )
    (net (code "4802") (name "unconnected-(SV159-Pad12)") (class "Default")
      (node (ref "SV159") (pin "12") (pinfunction "12_12") (pintype "passive"))
    )
    (net (code "4803") (name "unconnected-(SV159-Pad13)") (class "Default")
      (node (ref "SV159") (pin "13") (pinfunction "13_13") (pintype "passive"))
    )
    (net (code "4804") (name "unconnected-(SV159-Pad14)") (class "Default")
      (node (ref "SV159") (pin "14") (pinfunction "14_14") (pintype "passive"))
    )
    (net (code "4805") (name "unconnected-(SV159-Pad15)") (class "Default")
      (node (ref "SV159") (pin "15") (pinfunction "15_15") (pintype "passive"))
    )
    (net (code "4806") (name "unconnected-(SV159-Pad16)") (class "Default")
      (node (ref "SV159") (pin "16") (pinfunction "16_16") (pintype "passive"))
    )
    (net (code "4807") (name "unconnected-(SV159-Pad17)") (class "Default")
      (node (ref "SV159") (pin "17") (pinfunction "17_17") (pintype "passive"))
    )
    (net (code "4808") (name "unconnected-(SV159-Pad18)") (class "Default")
      (node (ref "SV159") (pin "18") (pinfunction "18_18") (pintype "passive"))
    )
    (net (code "4809") (name "unconnected-(SV159-Pad19)") (class "Default")
      (node (ref "SV159") (pin "19") (pinfunction "19_19") (pintype "passive"))
    )
    (net (code "4810") (name "unconnected-(SV159-Pad20)") (class "Default")
      (node (ref "SV159") (pin "20") (pinfunction "20_20") (pintype "passive"))
    )
    (net (code "4811") (name "unconnected-(SV159-Pad21)") (class "Default")
      (node (ref "SV159") (pin "21") (pinfunction "21_21") (pintype "passive"))
    )
    (net (code "4812") (name "unconnected-(SV159-Pad22)") (class "Default")
      (node (ref "SV159") (pin "22") (pinfunction "22_22") (pintype "passive"))
    )
    (net (code "4813") (name "unconnected-(SV159-Pad23)") (class "Default")
      (node (ref "SV159") (pin "23") (pinfunction "23_23") (pintype "passive"))
    )
    (net (code "4814") (name "unconnected-(SV159-Pad24)") (class "Default")
      (node (ref "SV159") (pin "24") (pinfunction "24_24") (pintype "passive"))
    )
    (net (code "4815") (name "unconnected-(SV159-Pad25)") (class "Default")
      (node (ref "SV159") (pin "25") (pinfunction "25_25") (pintype "passive"))
    )
    (net (code "4816") (name "unconnected-(SV159-Pad26)") (class "Default")
      (node (ref "SV159") (pin "26") (pinfunction "26_26") (pintype "passive"))
    )
    (net (code "4817") (name "unconnected-(SV159-Pad27)") (class "Default")
      (node (ref "SV159") (pin "27") (pinfunction "27_27") (pintype "passive"))
    )
    (net (code "4818") (name "unconnected-(SV159-Pad28)") (class "Default")
      (node (ref "SV159") (pin "28") (pinfunction "28_28") (pintype "passive"))
    )
    (net (code "4819") (name "unconnected-(SV159-Pad29)") (class "Default")
      (node (ref "SV159") (pin "29") (pinfunction "29_29") (pintype "passive"))
    )
    (net (code "4820") (name "unconnected-(SV159-Pad30)") (class "Default")
      (node (ref "SV159") (pin "30") (pinfunction "30_30") (pintype "passive"))
    )
    (net (code "4821") (name "unconnected-(SV159-Pad31)") (class "Default")
      (node (ref "SV159") (pin "31") (pinfunction "31_31") (pintype "passive"))
    )
    (net (code "4822") (name "unconnected-(SV159-Pad32)") (class "Default")
      (node (ref "SV159") (pin "32") (pinfunction "32_32") (pintype "passive"))
    )
    (net (code "4823") (name "unconnected-(SV159-Pad33)") (class "Default")
      (node (ref "SV159") (pin "33") (pinfunction "33_33") (pintype "passive"))
    )
    (net (code "4824") (name "unconnected-(SV159-Pad34)") (class "Default")
      (node (ref "SV159") (pin "34") (pinfunction "34_34") (pintype "passive"))
    )
    (net (code "4825") (name "unconnected-(SV159-Pad35)") (class "Default")
      (node (ref "SV159") (pin "35") (pinfunction "35_35") (pintype "passive"))
    )
    (net (code "4826") (name "unconnected-(SV159-Pad36)") (class "Default")
      (node (ref "SV159") (pin "36") (pinfunction "36_36") (pintype "passive"))
    )
    (net (code "4827") (name "unconnected-(SV159-Pad37)") (class "Default")
      (node (ref "SV159") (pin "37") (pinfunction "37_37") (pintype "passive"))
    )
    (net (code "4828") (name "unconnected-(SV159-Pad38)") (class "Default")
      (node (ref "SV159") (pin "38") (pinfunction "38_38") (pintype "passive"))
    )
    (net (code "4829") (name "unconnected-(SV159-Pad39)") (class "Default")
      (node (ref "SV159") (pin "39") (pinfunction "39_39") (pintype "passive"))
    )
    (net (code "4830") (name "unconnected-(SV159-Pad40)") (class "Default")
      (node (ref "SV159") (pin "40") (pinfunction "40_40") (pintype "passive"))
    )
    (net (code "4831") (name "unconnected-(SV160-Pad1)") (class "Default")
      (node (ref "SV160") (pin "1") (pinfunction "1_1") (pintype "passive"))
    )
    (net (code "4832") (name "unconnected-(SV160-Pad2)") (class "Default")
      (node (ref "SV160") (pin "2") (pinfunction "2_2") (pintype "passive"))
    )
    (net (code "4833") (name "unconnected-(SV160-Pad3)") (class "Default")
      (node (ref "SV160") (pin "3") (pinfunction "3_3") (pintype "passive"))
    )
    (net (code "4834") (name "unconnected-(SV160-Pad4)") (class "Default")
      (node (ref "SV160") (pin "4") (pinfunction "4_4") (pintype "passive"))
    )
    (net (code "4835") (name "unconnected-(SV160-Pad5)") (class "Default")
      (node (ref "SV160") (pin "5") (pinfunction "5_5") (pintype "passive"))
    )
    (net (code "4836") (name "unconnected-(SV160-Pad6)") (class "Default")
      (node (ref "SV160") (pin "6") (pinfunction "6_6") (pintype "passive"))
    )
    (net (code "4837") (name "unconnected-(SV160-Pad7)") (class "Default")
      (node (ref "SV160") (pin "7") (pinfunction "7_7") (pintype "passive"))
    )
    (net (code "4838") (name "unconnected-(SV160-Pad8)") (class "Default")
      (node (ref "SV160") (pin "8") (pinfunction "8_8") (pintype "passive"))
    )
    (net (code "4839") (name "unconnected-(SV160-Pad9)") (class "Default")
      (node (ref "SV160") (pin "9") (pinfunction "9_9") (pintype "passive"))
    )
    (net (code "4840") (name "unconnected-(SV160-Pad10)") (class "Default")
      (node (ref "SV160") (pin "10") (pinfunction "10_10") (pintype "passive"))
    )
    (net (code "4841") (name "unconnected-(SV160-Pad11)") (class "Default")
      (node (ref "SV160") (pin "11") (pinfunction "11_11") (pintype "passive"))
    )
    (net (code "4842") (name "unconnected-(SV160-Pad12)") (class "Default")
      (node (ref "SV160") (pin "12") (pinfunction "12_12") (pintype "passive"))
    )
    (net (code "4843") (name "unconnected-(SV160-Pad13)") (class "Default")
      (node (ref "SV160") (pin "13") (pinfunction "13_13") (pintype "passive"))
    )
    (net (code "4844") (name "unconnected-(SV160-Pad14)") (class "Default")
      (node (ref "SV160") (pin "14") (pinfunction "14_14") (pintype "passive"))
    )
    (net (code "4845") (name "unconnected-(SV160-Pad15)") (class "Default")
      (node (ref "SV160") (pin "15") (pinfunction "15_15") (pintype "passive"))
    )
    (net (code "4846") (name "unconnected-(SV160-Pad16)") (class "Default")
      (node (ref "SV160") (pin "16") (pinfunction "16_16") (pintype "passive"))
    )
    (net (code "4847") (name "unconnected-(SV160-Pad17)") (class "Default")
      (node (ref "SV160") (pin "17") (pinfunction "17_17") (pintype "passive"))
    )
    (net (code "4848") (name "unconnected-(SV160-Pad18)") (class "Default")
      (node (ref "SV160") (pin "18") (pinfunction "18_18") (pintype "passive"))
    )
    (net (code "4849") (name "unconnected-(SV160-Pad19)") (class "Default")
      (node (ref "SV160") (pin "19") (pinfunction "19_19") (pintype "passive"))
    )
    (net (code "4850") (name "unconnected-(SV160-Pad20)") (class "Default")
      (node (ref "SV160") (pin "20") (pinfunction "20_20") (pintype "passive"))
    )
    (net (code "4851") (name "unconnected-(SV160-Pad21)") (class "Default")
      (node (ref "SV160") (pin "21") (pinfunction "21_21") (pintype "passive"))
    )
    (net (code "4852") (name "unconnected-(SV160-Pad22)") (class "Default")
      (node (ref "SV160") (pin "22") (pinfunction "22_22") (pintype "passive"))
    )
    (net (code "4853") (name "unconnected-(SV160-Pad23)") (class "Default")
      (node (ref "SV160") (pin "23") (pinfunction "23_23") (pintype "passive"))
    )
    (net (code "4854") (name "unconnected-(SV160-Pad24)") (class "Default")
      (node (ref "SV160") (pin "24") (pinfunction "24_24") (pintype "passive"))
    )
    (net (code "4855") (name "unconnected-(SV160-Pad25)") (class "Default")
      (node (ref "SV160") (pin "25") (pinfunction "25_25") (pintype "passive"))
    )
    (net (code "4856") (name "unconnected-(SV160-Pad26)") (class "Default")
      (node (ref "SV160") (pin "26") (pinfunction "26_26") (pintype "passive"))
    )
    (net (code "4857") (name "unconnected-(SV160-Pad27)") (class "Default")
      (node (ref "SV160") (pin "27") (pinfunction "27_27") (pintype "passive"))
    )
    (net (code "4858") (name "unconnected-(SV160-Pad28)") (class "Default")
      (node (ref "SV160") (pin "28") (pinfunction "28_28") (pintype "passive"))
    )
    (net (code "4859") (name "unconnected-(SV160-Pad29)") (class "Default")
      (node (ref "SV160") (pin "29") (pinfunction "29_29") (pintype "passive"))
    )
    (net (code "4860") (name "unconnected-(SV160-Pad30)") (class "Default")
      (node (ref "SV160") (pin "30") (pinfunction "30_30") (pintype "passive"))
    )
    (net (code "4861") (name "unconnected-(SV160-Pad31)") (class "Default")
      (node (ref "SV160") (pin "31") (pinfunction "31_31") (pintype "passive"))
    )
    (net (code "4862") (name "unconnected-(SV160-Pad32)") (class "Default")
      (node (ref "SV160") (pin "32") (pinfunction "32_32") (pintype "passive"))
    )
    (net (code "4863") (name "unconnected-(SV160-Pad33)") (class "Default")
      (node (ref "SV160") (pin "33") (pinfunction "33_33") (pintype "passive"))
    )
    (net (code "4864") (name "unconnected-(SV160-Pad34)") (class "Default")
      (node (ref "SV160") (pin "34") (pinfunction "34_34") (pintype "passive"))
    )
    (net (code "4865") (name "unconnected-(SV160-Pad35)") (class "Default")
      (node (ref "SV160") (pin "35") (pinfunction "35_35") (pintype "passive"))
    )
    (net (code "4866") (name "unconnected-(SV160-Pad36)") (class "Default")
      (node (ref "SV160") (pin "36") (pinfunction "36_36") (pintype "passive"))
    )
    (net (code "4867") (name "unconnected-(SV160-Pad37)") (class "Default")
      (node (ref "SV160") (pin "37") (pinfunction "37_37") (pintype "passive"))
    )
    (net (code "4868") (name "unconnected-(SV160-Pad38)") (class "Default")
      (node (ref "SV160") (pin "38") (pinfunction "38_38") (pintype "passive"))
    )
    (net (code "4869") (name "unconnected-(SV160-Pad39)") (class "Default")
      (node (ref "SV160") (pin "39") (pinfunction "39_39") (pintype "passive"))
    )
    (net (code "4870") (name "unconnected-(SV160-Pad40)") (class "Default")
      (node (ref "SV160") (pin "40") (pinfunction "40_40") (pintype "passive"))
    )
    (net (code "4871") (name "unconnected-(SV161-Pad1)") (class "Default")
      (node (ref "SV161") (pin "1") (pinfunction "1_1") (pintype "passive"))
    )
    (net (code "4872") (name "unconnected-(SV161-Pad2)") (class "Default")
      (node (ref "SV161") (pin "2") (pinfunction "2_2") (pintype "passive"))
    )
    (net (code "4873") (name "unconnected-(SV161-Pad3)") (class "Default")
      (node (ref "SV161") (pin "3") (pinfunction "3_3") (pintype "passive"))
    )
    (net (code "4874") (name "unconnected-(SV161-Pad4)") (class "Default")
      (node (ref "SV161") (pin "4") (pinfunction "4_4") (pintype "passive"))
    )
    (net (code "4875") (name "unconnected-(SV161-Pad5)") (class "Default")
      (node (ref "SV161") (pin "5") (pinfunction "5_5") (pintype "passive"))
    )
    (net (code "4876") (name "unconnected-(SV161-Pad6)") (class "Default")
      (node (ref "SV161") (pin "6") (pinfunction "6_6") (pintype "passive"))
    )
    (net (code "4877") (name "unconnected-(SV161-Pad7)") (class "Default")
      (node (ref "SV161") (pin "7") (pinfunction "7_7") (pintype "passive"))
    )
    (net (code "4878") (name "unconnected-(SV161-Pad8)") (class "Default")
      (node (ref "SV161") (pin "8") (pinfunction "8_8") (pintype "passive"))
    )
    (net (code "4879") (name "unconnected-(SV161-Pad9)") (class "Default")
      (node (ref "SV161") (pin "9") (pinfunction "9_9") (pintype "passive"))
    )
    (net (code "4880") (name "unconnected-(SV161-Pad10)") (class "Default")
      (node (ref "SV161") (pin "10") (pinfunction "10_10") (pintype "passive"))
    )
    (net (code "4881") (name "unconnected-(SV161-Pad11)") (class "Default")
      (node (ref "SV161") (pin "11") (pinfunction "11_11") (pintype "passive"))
    )
    (net (code "4882") (name "unconnected-(SV161-Pad12)") (class "Default")
      (node (ref "SV161") (pin "12") (pinfunction "12_12") (pintype "passive"))
    )
    (net (code "4883") (name "unconnected-(SV161-Pad13)") (class "Default")
      (node (ref "SV161") (pin "13") (pinfunction "13_13") (pintype "passive"))
    )
    (net (code "4884") (name "unconnected-(SV161-Pad14)") (class "Default")
      (node (ref "SV161") (pin "14") (pinfunction "14_14") (pintype "passive"))
    )
    (net (code "4885") (name "unconnected-(SV161-Pad15)") (class "Default")
      (node (ref "SV161") (pin "15") (pinfunction "15_15") (pintype "passive"))
    )
    (net (code "4886") (name "unconnected-(SV161-Pad16)") (class "Default")
      (node (ref "SV161") (pin "16") (pinfunction "16_16") (pintype "passive"))
    )
    (net (code "4887") (name "unconnected-(SV161-Pad17)") (class "Default")
      (node (ref "SV161") (pin "17") (pinfunction "17_17") (pintype "passive"))
    )
    (net (code "4888") (name "unconnected-(SV161-Pad18)") (class "Default")
      (node (ref "SV161") (pin "18") (pinfunction "18_18") (pintype "passive"))
    )
    (net (code "4889") (name "unconnected-(SV161-Pad19)") (class "Default")
      (node (ref "SV161") (pin "19") (pinfunction "19_19") (pintype "passive"))
    )
    (net (code "4890") (name "unconnected-(SV161-Pad20)") (class "Default")
      (node (ref "SV161") (pin "20") (pinfunction "20_20") (pintype "passive"))
    )
    (net (code "4891") (name "unconnected-(SV161-Pad21)") (class "Default")
      (node (ref "SV161") (pin "21") (pinfunction "21_21") (pintype "passive"))
    )
    (net (code "4892") (name "unconnected-(SV161-Pad22)") (class "Default")
      (node (ref "SV161") (pin "22") (pinfunction "22_22") (pintype "passive"))
    )
    (net (code "4893") (name "unconnected-(SV161-Pad23)") (class "Default")
      (node (ref "SV161") (pin "23") (pinfunction "23_23") (pintype "passive"))
    )
    (net (code "4894") (name "unconnected-(SV161-Pad24)") (class "Default")
      (node (ref "SV161") (pin "24") (pinfunction "24_24") (pintype "passive"))
    )
    (net (code "4895") (name "unconnected-(SV161-Pad25)") (class "Default")
      (node (ref "SV161") (pin "25") (pinfunction "25_25") (pintype "passive"))
    )
    (net (code "4896") (name "unconnected-(SV161-Pad26)") (class "Default")
      (node (ref "SV161") (pin "26") (pinfunction "26_26") (pintype "passive"))
    )
    (net (code "4897") (name "unconnected-(SV161-Pad27)") (class "Default")
      (node (ref "SV161") (pin "27") (pinfunction "27_27") (pintype "passive"))
    )
    (net (code "4898") (name "unconnected-(SV161-Pad28)") (class "Default")
      (node (ref "SV161") (pin "28") (pinfunction "28_28") (pintype "passive"))
    )
    (net (code "4899") (name "unconnected-(SV161-Pad29)") (class "Default")
      (node (ref "SV161") (pin "29") (pinfunction "29_29") (pintype "passive"))
    )
    (net (code "4900") (name "unconnected-(SV161-Pad30)") (class "Default")
      (node (ref "SV161") (pin "30") (pinfunction "30_30") (pintype "passive"))
    )
    (net (code "4901") (name "unconnected-(SV161-Pad31)") (class "Default")
      (node (ref "SV161") (pin "31") (pinfunction "31_31") (pintype "passive"))
    )
    (net (code "4902") (name "unconnected-(SV161-Pad32)") (class "Default")
      (node (ref "SV161") (pin "32") (pinfunction "32_32") (pintype "passive"))
    )
    (net (code "4903") (name "unconnected-(SV161-Pad33)") (class "Default")
      (node (ref "SV161") (pin "33") (pinfunction "33_33") (pintype "passive"))
    )
    (net (code "4904") (name "unconnected-(SV161-Pad34)") (class "Default")
      (node (ref "SV161") (pin "34") (pinfunction "34_34") (pintype "passive"))
    )
    (net (code "4905") (name "unconnected-(SV161-Pad35)") (class "Default")
      (node (ref "SV161") (pin "35") (pinfunction "35_35") (pintype "passive"))
    )
    (net (code "4906") (name "unconnected-(SV161-Pad36)") (class "Default")
      (node (ref "SV161") (pin "36") (pinfunction "36_36") (pintype "passive"))
    )
    (net (code "4907") (name "unconnected-(SV161-Pad37)") (class "Default")
      (node (ref "SV161") (pin "37") (pinfunction "37_37") (pintype "passive"))
    )
    (net (code "4908") (name "unconnected-(SV161-Pad38)") (class "Default")
      (node (ref "SV161") (pin "38") (pinfunction "38_38") (pintype "passive"))
    )
    (net (code "4909") (name "unconnected-(SV161-Pad39)") (class "Default")
      (node (ref "SV161") (pin "39") (pinfunction "39_39") (pintype "passive"))
    )
    (net (code "4910") (name "unconnected-(SV161-Pad40)") (class "Default")
      (node (ref "SV161") (pin "40") (pinfunction "40_40") (pintype "passive"))
    )
    (net (code "4911") (name "unconnected-(SV162-Pad1)") (class "Default")
      (node (ref "SV162") (pin "1") (pinfunction "1_1") (pintype "passive"))
    )
    (net (code "4912") (name "unconnected-(SV162-Pad2)") (class "Default")
      (node (ref "SV162") (pin "2") (pinfunction "2_2") (pintype "passive"))
    )
    (net (code "4913") (name "unconnected-(SV162-Pad3)") (class "Default")
      (node (ref "SV162") (pin "3") (pinfunction "3_3") (pintype "passive"))
    )
    (net (code "4914") (name "unconnected-(SV162-Pad4)") (class "Default")
      (node (ref "SV162") (pin "4") (pinfunction "4_4") (pintype "passive"))
    )
    (net (code "4915") (name "unconnected-(SV162-Pad5)") (class "Default")
      (node (ref "SV162") (pin "5") (pinfunction "5_5") (pintype "passive"))
    )
    (net (code "4916") (name "unconnected-(SV162-Pad6)") (class "Default")
      (node (ref "SV162") (pin "6") (pinfunction "6_6") (pintype "passive"))
    )
    (net (code "4917") (name "unconnected-(SV162-Pad7)") (class "Default")
      (node (ref "SV162") (pin "7") (pinfunction "7_7") (pintype "passive"))
    )
    (net (code "4918") (name "unconnected-(SV162-Pad8)") (class "Default")
      (node (ref "SV162") (pin "8") (pinfunction "8_8") (pintype "passive"))
    )
    (net (code "4919") (name "unconnected-(SV162-Pad9)") (class "Default")
      (node (ref "SV162") (pin "9") (pinfunction "9_9") (pintype "passive"))
    )
    (net (code "4920") (name "unconnected-(SV162-Pad10)") (class "Default")
      (node (ref "SV162") (pin "10") (pinfunction "10_10") (pintype "passive"))
    )
    (net (code "4921") (name "unconnected-(SV162-Pad11)") (class "Default")
      (node (ref "SV162") (pin "11") (pinfunction "11_11") (pintype "passive"))
    )
    (net (code "4922") (name "unconnected-(SV162-Pad12)") (class "Default")
      (node (ref "SV162") (pin "12") (pinfunction "12_12") (pintype "passive"))
    )
    (net (code "4923") (name "unconnected-(SV162-Pad13)") (class "Default")
      (node (ref "SV162") (pin "13") (pinfunction "13_13") (pintype "passive"))
    )
    (net (code "4924") (name "unconnected-(SV162-Pad14)") (class "Default")
      (node (ref "SV162") (pin "14") (pinfunction "14_14") (pintype "passive"))
    )
    (net (code "4925") (name "unconnected-(SV162-Pad15)") (class "Default")
      (node (ref "SV162") (pin "15") (pinfunction "15_15") (pintype "passive"))
    )
    (net (code "4926") (name "unconnected-(SV162-Pad16)") (class "Default")
      (node (ref "SV162") (pin "16") (pinfunction "16_16") (pintype "passive"))
    )
    (net (code "4927") (name "unconnected-(SV162-Pad17)") (class "Default")
      (node (ref "SV162") (pin "17") (pinfunction "17_17") (pintype "passive"))
    )
    (net (code "4928") (name "unconnected-(SV162-Pad18)") (class "Default")
      (node (ref "SV162") (pin "18") (pinfunction "18_18") (pintype "passive"))
    )
    (net (code "4929") (name "unconnected-(SV162-Pad19)") (class "Default")
      (node (ref "SV162") (pin "19") (pinfunction "19_19") (pintype "passive"))
    )
    (net (code "4930") (name "unconnected-(SV162-Pad20)") (class "Default")
      (node (ref "SV162") (pin "20") (pinfunction "20_20") (pintype "passive"))
    )
    (net (code "4931") (name "unconnected-(SV162-Pad21)") (class "Default")
      (node (ref "SV162") (pin "21") (pinfunction "21_21") (pintype "passive"))
    )
    (net (code "4932") (name "unconnected-(SV162-Pad22)") (class "Default")
      (node (ref "SV162") (pin "22") (pinfunction "22_22") (pintype "passive"))
    )
    (net (code "4933") (name "unconnected-(SV162-Pad23)") (class "Default")
      (node (ref "SV162") (pin "23") (pinfunction "23_23") (pintype "passive"))
    )
    (net (code "4934") (name "unconnected-(SV162-Pad24)") (class "Default")
      (node (ref "SV162") (pin "24") (pinfunction "24_24") (pintype "passive"))
    )
    (net (code "4935") (name "unconnected-(SV162-Pad25)") (class "Default")
      (node (ref "SV162") (pin "25") (pinfunction "25_25") (pintype "passive"))
    )
    (net (code "4936") (name "unconnected-(SV162-Pad26)") (class "Default")
      (node (ref "SV162") (pin "26") (pinfunction "26_26") (pintype "passive"))
    )
    (net (code "4937") (name "unconnected-(SV162-Pad27)") (class "Default")
      (node (ref "SV162") (pin "27") (pinfunction "27_27") (pintype "passive"))
    )
    (net (code "4938") (name "unconnected-(SV162-Pad28)") (class "Default")
      (node (ref "SV162") (pin "28") (pinfunction "28_28") (pintype "passive"))
    )
    (net (code "4939") (name "unconnected-(SV162-Pad29)") (class "Default")
      (node (ref "SV162") (pin "29") (pinfunction "29_29") (pintype "passive"))
    )
    (net (code "4940") (name "unconnected-(SV162-Pad30)") (class "Default")
      (node (ref "SV162") (pin "30") (pinfunction "30_30") (pintype "passive"))
    )
    (net (code "4941") (name "unconnected-(SV162-Pad31)") (class "Default")
      (node (ref "SV162") (pin "31") (pinfunction "31_31") (pintype "passive"))
    )
    (net (code "4942") (name "unconnected-(SV162-Pad32)") (class "Default")
      (node (ref "SV162") (pin "32") (pinfunction "32_32") (pintype "passive"))
    )
    (net (code "4943") (name "unconnected-(SV162-Pad33)") (class "Default")
      (node (ref "SV162") (pin "33") (pinfunction "33_33") (pintype "passive"))
    )
    (net (code "4944") (name "unconnected-(SV162-Pad34)") (class "Default")
      (node (ref "SV162") (pin "34") (pinfunction "34_34") (pintype "passive"))
    )
    (net (code "4945") (name "unconnected-(SV162-Pad35)") (class "Default")
      (node (ref "SV162") (pin "35") (pinfunction "35_35") (pintype "passive"))
    )
    (net (code "4946") (name "unconnected-(SV162-Pad36)") (class "Default")
      (node (ref "SV162") (pin "36") (pinfunction "36_36") (pintype "passive"))
    )
    (net (code "4947") (name "unconnected-(SV162-Pad37)") (class "Default")
      (node (ref "SV162") (pin "37") (pinfunction "37_37") (pintype "passive"))
    )
    (net (code "4948") (name "unconnected-(SV162-Pad38)") (class "Default")
      (node (ref "SV162") (pin "38") (pinfunction "38_38") (pintype "passive"))
    )
    (net (code "4949") (name "unconnected-(SV162-Pad39)") (class "Default")
      (node (ref "SV162") (pin "39") (pinfunction "39_39") (pintype "passive"))
    )
    (net (code "4950") (name "unconnected-(SV162-Pad40)") (class "Default")
      (node (ref "SV162") (pin "40") (pinfunction "40_40") (pintype "passive"))
    )
    (net (code "4951") (name "unconnected-(SV163-Pad1)") (class "Default")
      (node (ref "SV163") (pin "1") (pinfunction "1_1") (pintype "passive"))
    )
    (net (code "4952") (name "unconnected-(SV163-Pad2)") (class "Default")
      (node (ref "SV163") (pin "2") (pinfunction "2_2") (pintype "passive"))
    )
    (net (code "4953") (name "unconnected-(SV163-Pad3)") (class "Default")
      (node (ref "SV163") (pin "3") (pinfunction "3_3") (pintype "passive"))
    )
    (net (code "4954") (name "unconnected-(SV163-Pad4)") (class "Default")
      (node (ref "SV163") (pin "4") (pinfunction "4_4") (pintype "passive"))
    )
    (net (code "4955") (name "unconnected-(SV163-Pad5)") (class "Default")
      (node (ref "SV163") (pin "5") (pinfunction "5_5") (pintype "passive"))
    )
    (net (code "4956") (name "unconnected-(SV163-Pad6)") (class "Default")
      (node (ref "SV163") (pin "6") (pinfunction "6_6") (pintype "passive"))
    )
    (net (code "4957") (name "unconnected-(SV163-Pad7)") (class "Default")
      (node (ref "SV163") (pin "7") (pinfunction "7_7") (pintype "passive"))
    )
    (net (code "4958") (name "unconnected-(SV163-Pad8)") (class "Default")
      (node (ref "SV163") (pin "8") (pinfunction "8_8") (pintype "passive"))
    )
    (net (code "4959") (name "unconnected-(SV163-Pad9)") (class "Default")
      (node (ref "SV163") (pin "9") (pinfunction "9_9") (pintype "passive"))
    )
    (net (code "4960") (name "unconnected-(SV163-Pad10)") (class "Default")
      (node (ref "SV163") (pin "10") (pinfunction "10_10") (pintype "passive"))
    )
    (net (code "4961") (name "unconnected-(SV163-Pad11)") (class "Default")
      (node (ref "SV163") (pin "11") (pinfunction "11_11") (pintype "passive"))
    )
    (net (code "4962") (name "unconnected-(SV163-Pad12)") (class "Default")
      (node (ref "SV163") (pin "12") (pinfunction "12_12") (pintype "passive"))
    )
    (net (code "4963") (name "unconnected-(SV163-Pad13)") (class "Default")
      (node (ref "SV163") (pin "13") (pinfunction "13_13") (pintype "passive"))
    )
    (net (code "4964") (name "unconnected-(SV163-Pad14)") (class "Default")
      (node (ref "SV163") (pin "14") (pinfunction "14_14") (pintype "passive"))
    )
    (net (code "4965") (name "unconnected-(SV163-Pad15)") (class "Default")
      (node (ref "SV163") (pin "15") (pinfunction "15_15") (pintype "passive"))
    )
    (net (code "4966") (name "unconnected-(SV163-Pad16)") (class "Default")
      (node (ref "SV163") (pin "16") (pinfunction "16_16") (pintype "passive"))
    )
    (net (code "4967") (name "unconnected-(SV163-Pad17)") (class "Default")
      (node (ref "SV163") (pin "17") (pinfunction "17_17") (pintype "passive"))
    )
    (net (code "4968") (name "unconnected-(SV163-Pad18)") (class "Default")
      (node (ref "SV163") (pin "18") (pinfunction "18_18") (pintype "passive"))
    )
    (net (code "4969") (name "unconnected-(SV163-Pad19)") (class "Default")
      (node (ref "SV163") (pin "19") (pinfunction "19_19") (pintype "passive"))
    )
    (net (code "4970") (name "unconnected-(SV163-Pad20)") (class "Default")
      (node (ref "SV163") (pin "20") (pinfunction "20_20") (pintype "passive"))
    )
    (net (code "4971") (name "unconnected-(SV163-Pad21)") (class "Default")
      (node (ref "SV163") (pin "21") (pinfunction "21_21") (pintype "passive"))
    )
    (net (code "4972") (name "unconnected-(SV163-Pad22)") (class "Default")
      (node (ref "SV163") (pin "22") (pinfunction "22_22") (pintype "passive"))
    )
    (net (code "4973") (name "unconnected-(SV163-Pad23)") (class "Default")
      (node (ref "SV163") (pin "23") (pinfunction "23_23") (pintype "passive"))
    )
    (net (code "4974") (name "unconnected-(SV163-Pad24)") (class "Default")
      (node (ref "SV163") (pin "24") (pinfunction "24_24") (pintype "passive"))
    )
    (net (code "4975") (name "unconnected-(SV164-Pad1)") (class "Default")
      (node (ref "SV164") (pin "1") (pinfunction "1_1") (pintype "passive"))
    )
    (net (code "4976") (name "unconnected-(SV164-Pad2)") (class "Default")
      (node (ref "SV164") (pin "2") (pinfunction "2_2") (pintype "passive"))
    )
    (net (code "4977") (name "unconnected-(SV164-Pad3)") (class "Default")
      (node (ref "SV164") (pin "3") (pinfunction "3_3") (pintype "passive"))
    )
    (net (code "4978") (name "unconnected-(SV164-Pad4)") (class "Default")
      (node (ref "SV164") (pin "4") (pinfunction "4_4") (pintype "passive"))
    )
    (net (code "4979") (name "unconnected-(SV164-Pad5)") (class "Default")
      (node (ref "SV164") (pin "5") (pinfunction "5_5") (pintype "passive"))
    )
    (net (code "4980") (name "unconnected-(SV164-Pad6)") (class "Default")
      (node (ref "SV164") (pin "6") (pinfunction "6_6") (pintype "passive"))
    )
    (net (code "4981") (name "unconnected-(SV164-Pad7)") (class "Default")
      (node (ref "SV164") (pin "7") (pinfunction "7_7") (pintype "passive"))
    )
    (net (code "4982") (name "unconnected-(SV164-Pad8)") (class "Default")
      (node (ref "SV164") (pin "8") (pinfunction "8_8") (pintype "passive"))
    )
    (net (code "4983") (name "unconnected-(SV164-Pad9)") (class "Default")
      (node (ref "SV164") (pin "9") (pinfunction "9_9") (pintype "passive"))
    )
    (net (code "4984") (name "unconnected-(SV164-Pad10)") (class "Default")
      (node (ref "SV164") (pin "10") (pinfunction "10_10") (pintype "passive"))
    )
    (net (code "4985") (name "unconnected-(SV164-Pad11)") (class "Default")
      (node (ref "SV164") (pin "11") (pinfunction "11_11") (pintype "passive"))
    )
    (net (code "4986") (name "unconnected-(SV164-Pad12)") (class "Default")
      (node (ref "SV164") (pin "12") (pinfunction "12_12") (pintype "passive"))
    )
    (net (code "4987") (name "unconnected-(SV164-Pad13)") (class "Default")
      (node (ref "SV164") (pin "13") (pinfunction "13_13") (pintype "passive"))
    )
    (net (code "4988") (name "unconnected-(SV164-Pad14)") (class "Default")
      (node (ref "SV164") (pin "14") (pinfunction "14_14") (pintype "passive"))
    )
    (net (code "4989") (name "unconnected-(SV164-Pad15)") (class "Default")
      (node (ref "SV164") (pin "15") (pinfunction "15_15") (pintype "passive"))
    )
    (net (code "4990") (name "unconnected-(SV164-Pad16)") (class "Default")
      (node (ref "SV164") (pin "16") (pinfunction "16_16") (pintype "passive"))
    )
    (net (code "4991") (name "unconnected-(SV164-Pad17)") (class "Default")
      (node (ref "SV164") (pin "17") (pinfunction "17_17") (pintype "passive"))
    )
    (net (code "4992") (name "unconnected-(SV164-Pad18)") (class "Default")
      (node (ref "SV164") (pin "18") (pinfunction "18_18") (pintype "passive"))
    )
    (net (code "4993") (name "unconnected-(SV164-Pad19)") (class "Default")
      (node (ref "SV164") (pin "19") (pinfunction "19_19") (pintype "passive"))
    )
    (net (code "4994") (name "unconnected-(SV164-Pad20)") (class "Default")
      (node (ref "SV164") (pin "20") (pinfunction "20_20") (pintype "passive"))
    )
    (net (code "4995") (name "unconnected-(SV164-Pad21)") (class "Default")
      (node (ref "SV164") (pin "21") (pinfunction "21_21") (pintype "passive"))
    )
    (net (code "4996") (name "unconnected-(SV164-Pad22)") (class "Default")
      (node (ref "SV164") (pin "22") (pinfunction "22_22") (pintype "passive"))
    )
    (net (code "4997") (name "unconnected-(SV164-Pad23)") (class "Default")
      (node (ref "SV164") (pin "23") (pinfunction "23_23") (pintype "passive"))
    )
    (net (code "4998") (name "unconnected-(SV164-Pad24)") (class "Default")
      (node (ref "SV164") (pin "24") (pinfunction "24_24") (pintype "passive"))
    )
    (net (code "4999") (name "unconnected-(SV165-Pad1)") (class "Default")
      (node (ref "SV165") (pin "1") (pinfunction "1_1") (pintype "passive"))
    )
    (net (code "5000") (name "unconnected-(SV165-Pad2)") (class "Default")
      (node (ref "SV165") (pin "2") (pinfunction "2_2") (pintype "passive"))
    )
    (net (code "5001") (name "unconnected-(SV165-Pad3)") (class "Default")
      (node (ref "SV165") (pin "3") (pinfunction "3_3") (pintype "passive"))
    )
    (net (code "5002") (name "unconnected-(SV165-Pad4)") (class "Default")
      (node (ref "SV165") (pin "4") (pinfunction "4_4") (pintype "passive"))
    )
    (net (code "5003") (name "unconnected-(SV165-Pad5)") (class "Default")
      (node (ref "SV165") (pin "5") (pinfunction "5_5") (pintype "passive"))
    )
    (net (code "5004") (name "unconnected-(SV165-Pad6)") (class "Default")
      (node (ref "SV165") (pin "6") (pinfunction "6_6") (pintype "passive"))
    )
    (net (code "5005") (name "unconnected-(SV165-Pad7)") (class "Default")
      (node (ref "SV165") (pin "7") (pinfunction "7_7") (pintype "passive"))
    )
    (net (code "5006") (name "unconnected-(SV165-Pad8)") (class "Default")
      (node (ref "SV165") (pin "8") (pinfunction "8_8") (pintype "passive"))
    )
    (net (code "5007") (name "unconnected-(SV165-Pad9)") (class "Default")
      (node (ref "SV165") (pin "9") (pinfunction "9_9") (pintype "passive"))
    )
    (net (code "5008") (name "unconnected-(SV165-Pad10)") (class "Default")
      (node (ref "SV165") (pin "10") (pinfunction "10_10") (pintype "passive"))
    )
    (net (code "5009") (name "unconnected-(SV165-Pad11)") (class "Default")
      (node (ref "SV165") (pin "11") (pinfunction "11_11") (pintype "passive"))
    )
    (net (code "5010") (name "unconnected-(SV165-Pad12)") (class "Default")
      (node (ref "SV165") (pin "12") (pinfunction "12_12") (pintype "passive"))
    )
    (net (code "5011") (name "unconnected-(SV165-Pad13)") (class "Default")
      (node (ref "SV165") (pin "13") (pinfunction "13_13") (pintype "passive"))
    )
    (net (code "5012") (name "unconnected-(SV165-Pad14)") (class "Default")
      (node (ref "SV165") (pin "14") (pinfunction "14_14") (pintype "passive"))
    )
    (net (code "5013") (name "unconnected-(SV165-Pad15)") (class "Default")
      (node (ref "SV165") (pin "15") (pinfunction "15_15") (pintype "passive"))
    )
    (net (code "5014") (name "unconnected-(SV165-Pad16)") (class "Default")
      (node (ref "SV165") (pin "16") (pinfunction "16_16") (pintype "passive"))
    )
    (net (code "5015") (name "unconnected-(SV165-Pad17)") (class "Default")
      (node (ref "SV165") (pin "17") (pinfunction "17_17") (pintype "passive"))
    )
    (net (code "5016") (name "unconnected-(SV165-Pad18)") (class "Default")
      (node (ref "SV165") (pin "18") (pinfunction "18_18") (pintype "passive"))
    )
    (net (code "5017") (name "unconnected-(SV165-Pad19)") (class "Default")
      (node (ref "SV165") (pin "19") (pinfunction "19_19") (pintype "passive"))
    )
    (net (code "5018") (name "unconnected-(SV165-Pad20)") (class "Default")
      (node (ref "SV165") (pin "20") (pinfunction "20_20") (pintype "passive"))
    )
    (net (code "5019") (name "unconnected-(SV165-Pad21)") (class "Default")
      (node (ref "SV165") (pin "21") (pinfunction "21_21") (pintype "passive"))
    )
    (net (code "5020") (name "unconnected-(SV165-Pad22)") (class "Default")
      (node (ref "SV165") (pin "22") (pinfunction "22_22") (pintype "passive"))
    )
    (net (code "5021") (name "unconnected-(SV165-Pad23)") (class "Default")
      (node (ref "SV165") (pin "23") (pinfunction "23_23") (pintype "passive"))
    )
    (net (code "5022") (name "unconnected-(SV165-Pad24)") (class "Default")
      (node (ref "SV165") (pin "24") (pinfunction "24_24") (pintype "passive"))
    )
    (net (code "5023") (name "unconnected-(SV166-Pad1)") (class "Default")
      (node (ref "SV166") (pin "1") (pinfunction "1_1") (pintype "passive"))
    )
    (net (code "5024") (name "unconnected-(SV166-Pad2)") (class "Default")
      (node (ref "SV166") (pin "2") (pinfunction "2_2") (pintype "passive"))
    )
    (net (code "5025") (name "unconnected-(SV166-Pad3)") (class "Default")
      (node (ref "SV166") (pin "3") (pinfunction "3_3") (pintype "passive"))
    )
    (net (code "5026") (name "unconnected-(SV166-Pad4)") (class "Default")
      (node (ref "SV166") (pin "4") (pinfunction "4_4") (pintype "passive"))
    )
    (net (code "5027") (name "unconnected-(SV166-Pad5)") (class "Default")
      (node (ref "SV166") (pin "5") (pinfunction "5_5") (pintype "passive"))
    )
    (net (code "5028") (name "unconnected-(SV166-Pad6)") (class "Default")
      (node (ref "SV166") (pin "6") (pinfunction "6_6") (pintype "passive"))
    )
    (net (code "5029") (name "unconnected-(SV166-Pad7)") (class "Default")
      (node (ref "SV166") (pin "7") (pinfunction "7_7") (pintype "passive"))
    )
    (net (code "5030") (name "unconnected-(SV166-Pad8)") (class "Default")
      (node (ref "SV166") (pin "8") (pinfunction "8_8") (pintype "passive"))
    )
    (net (code "5031") (name "unconnected-(SV166-Pad9)") (class "Default")
      (node (ref "SV166") (pin "9") (pinfunction "9_9") (pintype "passive"))
    )
    (net (code "5032") (name "unconnected-(SV166-Pad10)") (class "Default")
      (node (ref "SV166") (pin "10") (pinfunction "10_10") (pintype "passive"))
    )
    (net (code "5033") (name "unconnected-(SV166-Pad11)") (class "Default")
      (node (ref "SV166") (pin "11") (pinfunction "11_11") (pintype "passive"))
    )
    (net (code "5034") (name "unconnected-(SV166-Pad12)") (class "Default")
      (node (ref "SV166") (pin "12") (pinfunction "12_12") (pintype "passive"))
    )
    (net (code "5035") (name "unconnected-(SV166-Pad13)") (class "Default")
      (node (ref "SV166") (pin "13") (pinfunction "13_13") (pintype "passive"))
    )
    (net (code "5036") (name "unconnected-(SV166-Pad14)") (class "Default")
      (node (ref "SV166") (pin "14") (pinfunction "14_14") (pintype "passive"))
    )
    (net (code "5037") (name "unconnected-(SV166-Pad15)") (class "Default")
      (node (ref "SV166") (pin "15") (pinfunction "15_15") (pintype "passive"))
    )
    (net (code "5038") (name "unconnected-(SV166-Pad16)") (class "Default")
      (node (ref "SV166") (pin "16") (pinfunction "16_16") (pintype "passive"))
    )
    (net (code "5039") (name "unconnected-(SV166-Pad17)") (class "Default")
      (node (ref "SV166") (pin "17") (pinfunction "17_17") (pintype "passive"))
    )
    (net (code "5040") (name "unconnected-(SV166-Pad18)") (class "Default")
      (node (ref "SV166") (pin "18") (pinfunction "18_18") (pintype "passive"))
    )
    (net (code "5041") (name "unconnected-(SV166-Pad19)") (class "Default")
      (node (ref "SV166") (pin "19") (pinfunction "19_19") (pintype "passive"))
    )
    (net (code "5042") (name "unconnected-(SV166-Pad20)") (class "Default")
      (node (ref "SV166") (pin "20") (pinfunction "20_20") (pintype "passive"))
    )
    (net (code "5043") (name "unconnected-(SV166-Pad21)") (class "Default")
      (node (ref "SV166") (pin "21") (pinfunction "21_21") (pintype "passive"))
    )
    (net (code "5044") (name "unconnected-(SV166-Pad22)") (class "Default")
      (node (ref "SV166") (pin "22") (pinfunction "22_22") (pintype "passive"))
    )
    (net (code "5045") (name "unconnected-(SV166-Pad23)") (class "Default")
      (node (ref "SV166") (pin "23") (pinfunction "23_23") (pintype "passive"))
    )
    (net (code "5046") (name "unconnected-(SV166-Pad24)") (class "Default")
      (node (ref "SV166") (pin "24") (pinfunction "24_24") (pintype "passive"))
    )
    (net (code "5047") (name "unconnected-(SV167-Pad1)") (class "Default")
      (node (ref "SV167") (pin "1") (pinfunction "1_1") (pintype "passive"))
    )
    (net (code "5048") (name "unconnected-(SV167-Pad2)") (class "Default")
      (node (ref "SV167") (pin "2") (pinfunction "2_2") (pintype "passive"))
    )
    (net (code "5049") (name "unconnected-(SV167-Pad3)") (class "Default")
      (node (ref "SV167") (pin "3") (pinfunction "3_3") (pintype "passive"))
    )
    (net (code "5050") (name "unconnected-(SV167-Pad4)") (class "Default")
      (node (ref "SV167") (pin "4") (pinfunction "4_4") (pintype "passive"))
    )
    (net (code "5051") (name "unconnected-(SV167-Pad5)") (class "Default")
      (node (ref "SV167") (pin "5") (pinfunction "5_5") (pintype "passive"))
    )
    (net (code "5052") (name "unconnected-(SV167-Pad6)") (class "Default")
      (node (ref "SV167") (pin "6") (pinfunction "6_6") (pintype "passive"))
    )
    (net (code "5053") (name "unconnected-(SV167-Pad7)") (class "Default")
      (node (ref "SV167") (pin "7") (pinfunction "7_7") (pintype "passive"))
    )
    (net (code "5054") (name "unconnected-(SV167-Pad8)") (class "Default")
      (node (ref "SV167") (pin "8") (pinfunction "8_8") (pintype "passive"))
    )
    (net (code "5055") (name "unconnected-(SV167-Pad9)") (class "Default")
      (node (ref "SV167") (pin "9") (pinfunction "9_9") (pintype "passive"))
    )
    (net (code "5056") (name "unconnected-(SV167-Pad10)") (class "Default")
      (node (ref "SV167") (pin "10") (pinfunction "10_10") (pintype "passive"))
    )
    (net (code "5057") (name "unconnected-(SV167-Pad11)") (class "Default")
      (node (ref "SV167") (pin "11") (pinfunction "11_11") (pintype "passive"))
    )
    (net (code "5058") (name "unconnected-(SV167-Pad12)") (class "Default")
      (node (ref "SV167") (pin "12") (pinfunction "12_12") (pintype "passive"))
    )
    (net (code "5059") (name "unconnected-(SV167-Pad13)") (class "Default")
      (node (ref "SV167") (pin "13") (pinfunction "13_13") (pintype "passive"))
    )
    (net (code "5060") (name "unconnected-(SV167-Pad14)") (class "Default")
      (node (ref "SV167") (pin "14") (pinfunction "14_14") (pintype "passive"))
    )
    (net (code "5061") (name "unconnected-(SV167-Pad15)") (class "Default")
      (node (ref "SV167") (pin "15") (pinfunction "15_15") (pintype "passive"))
    )
    (net (code "5062") (name "unconnected-(SV167-Pad16)") (class "Default")
      (node (ref "SV167") (pin "16") (pinfunction "16_16") (pintype "passive"))
    )
    (net (code "5063") (name "unconnected-(SV167-Pad17)") (class "Default")
      (node (ref "SV167") (pin "17") (pinfunction "17_17") (pintype "passive"))
    )
    (net (code "5064") (name "unconnected-(SV167-Pad18)") (class "Default")
      (node (ref "SV167") (pin "18") (pinfunction "18_18") (pintype "passive"))
    )
    (net (code "5065") (name "unconnected-(SV167-Pad19)") (class "Default")
      (node (ref "SV167") (pin "19") (pinfunction "19_19") (pintype "passive"))
    )
    (net (code "5066") (name "unconnected-(SV167-Pad20)") (class "Default")
      (node (ref "SV167") (pin "20") (pinfunction "20_20") (pintype "passive"))
    )
    (net (code "5067") (name "unconnected-(SV167-Pad21)") (class "Default")
      (node (ref "SV167") (pin "21") (pinfunction "21_21") (pintype "passive"))
    )
    (net (code "5068") (name "unconnected-(SV167-Pad22)") (class "Default")
      (node (ref "SV167") (pin "22") (pinfunction "22_22") (pintype "passive"))
    )
    (net (code "5069") (name "unconnected-(SV167-Pad23)") (class "Default")
      (node (ref "SV167") (pin "23") (pinfunction "23_23") (pintype "passive"))
    )
    (net (code "5070") (name "unconnected-(SV167-Pad24)") (class "Default")
      (node (ref "SV167") (pin "24") (pinfunction "24_24") (pintype "passive"))
    )
    (net (code "5071") (name "unconnected-(SV167-Pad25)") (class "Default")
      (node (ref "SV167") (pin "25") (pinfunction "25_25") (pintype "passive"))
    )
    (net (code "5072") (name "unconnected-(SV167-Pad26)") (class "Default")
      (node (ref "SV167") (pin "26") (pinfunction "26_26") (pintype "passive"))
    )
    (net (code "5073") (name "unconnected-(SV167-Pad27)") (class "Default")
      (node (ref "SV167") (pin "27") (pinfunction "27_27") (pintype "passive"))
    )
    (net (code "5074") (name "unconnected-(SV167-Pad28)") (class "Default")
      (node (ref "SV167") (pin "28") (pinfunction "28_28") (pintype "passive"))
    )
    (net (code "5075") (name "unconnected-(SV167-Pad29)") (class "Default")
      (node (ref "SV167") (pin "29") (pinfunction "29_29") (pintype "passive"))
    )
    (net (code "5076") (name "unconnected-(SV167-Pad30)") (class "Default")
      (node (ref "SV167") (pin "30") (pinfunction "30_30") (pintype "passive"))
    )
    (net (code "5077") (name "unconnected-(SV167-Pad31)") (class "Default")
      (node (ref "SV167") (pin "31") (pinfunction "31_31") (pintype "passive"))
    )
    (net (code "5078") (name "unconnected-(SV167-Pad32)") (class "Default")
      (node (ref "SV167") (pin "32") (pinfunction "32_32") (pintype "passive"))
    )
    (net (code "5079") (name "unconnected-(SV167-Pad33)") (class "Default")
      (node (ref "SV167") (pin "33") (pinfunction "33_33") (pintype "passive"))
    )
    (net (code "5080") (name "unconnected-(SV167-Pad34)") (class "Default")
      (node (ref "SV167") (pin "34") (pinfunction "34_34") (pintype "passive"))
    )
    (net (code "5081") (name "unconnected-(SV167-Pad35)") (class "Default")
      (node (ref "SV167") (pin "35") (pinfunction "35_35") (pintype "passive"))
    )
    (net (code "5082") (name "unconnected-(SV167-Pad36)") (class "Default")
      (node (ref "SV167") (pin "36") (pinfunction "36_36") (pintype "passive"))
    )
    (net (code "5083") (name "unconnected-(SV167-Pad37)") (class "Default")
      (node (ref "SV167") (pin "37") (pinfunction "37_37") (pintype "passive"))
    )
    (net (code "5084") (name "unconnected-(SV167-Pad38)") (class "Default")
      (node (ref "SV167") (pin "38") (pinfunction "38_38") (pintype "passive"))
    )
    (net (code "5085") (name "unconnected-(SV167-Pad39)") (class "Default")
      (node (ref "SV167") (pin "39") (pinfunction "39_39") (pintype "passive"))
    )
    (net (code "5086") (name "unconnected-(SV167-Pad40)") (class "Default")
      (node (ref "SV167") (pin "40") (pinfunction "40_40") (pintype "passive"))
    )
    (net (code "5087") (name "unconnected-(SV168-Pad1)") (class "Default")
      (node (ref "SV168") (pin "1") (pinfunction "1_1") (pintype "passive"))
    )
    (net (code "5088") (name "unconnected-(SV168-Pad2)") (class "Default")
      (node (ref "SV168") (pin "2") (pinfunction "2_2") (pintype "passive"))
    )
    (net (code "5089") (name "unconnected-(SV168-Pad3)") (class "Default")
      (node (ref "SV168") (pin "3") (pinfunction "3_3") (pintype "passive"))
    )
    (net (code "5090") (name "unconnected-(SV168-Pad4)") (class "Default")
      (node (ref "SV168") (pin "4") (pinfunction "4_4") (pintype "passive"))
    )
    (net (code "5091") (name "unconnected-(SV168-Pad5)") (class "Default")
      (node (ref "SV168") (pin "5") (pinfunction "5_5") (pintype "passive"))
    )
    (net (code "5092") (name "unconnected-(SV168-Pad6)") (class "Default")
      (node (ref "SV168") (pin "6") (pinfunction "6_6") (pintype "passive"))
    )
    (net (code "5093") (name "unconnected-(SV168-Pad7)") (class "Default")
      (node (ref "SV168") (pin "7") (pinfunction "7_7") (pintype "passive"))
    )
    (net (code "5094") (name "unconnected-(SV168-Pad8)") (class "Default")
      (node (ref "SV168") (pin "8") (pinfunction "8_8") (pintype "passive"))
    )
    (net (code "5095") (name "unconnected-(SV168-Pad9)") (class "Default")
      (node (ref "SV168") (pin "9") (pinfunction "9_9") (pintype "passive"))
    )
    (net (code "5096") (name "unconnected-(SV168-Pad10)") (class "Default")
      (node (ref "SV168") (pin "10") (pinfunction "10_10") (pintype "passive"))
    )
    (net (code "5097") (name "unconnected-(SV168-Pad11)") (class "Default")
      (node (ref "SV168") (pin "11") (pinfunction "11_11") (pintype "passive"))
    )
    (net (code "5098") (name "unconnected-(SV168-Pad12)") (class "Default")
      (node (ref "SV168") (pin "12") (pinfunction "12_12") (pintype "passive"))
    )
    (net (code "5099") (name "unconnected-(SV168-Pad13)") (class "Default")
      (node (ref "SV168") (pin "13") (pinfunction "13_13") (pintype "passive"))
    )
    (net (code "5100") (name "unconnected-(SV168-Pad14)") (class "Default")
      (node (ref "SV168") (pin "14") (pinfunction "14_14") (pintype "passive"))
    )
    (net (code "5101") (name "unconnected-(SV168-Pad15)") (class "Default")
      (node (ref "SV168") (pin "15") (pinfunction "15_15") (pintype "passive"))
    )
    (net (code "5102") (name "unconnected-(SV168-Pad16)") (class "Default")
      (node (ref "SV168") (pin "16") (pinfunction "16_16") (pintype "passive"))
    )
    (net (code "5103") (name "unconnected-(SV168-Pad17)") (class "Default")
      (node (ref "SV168") (pin "17") (pinfunction "17_17") (pintype "passive"))
    )
    (net (code "5104") (name "unconnected-(SV168-Pad18)") (class "Default")
      (node (ref "SV168") (pin "18") (pinfunction "18_18") (pintype "passive"))
    )
    (net (code "5105") (name "unconnected-(SV168-Pad19)") (class "Default")
      (node (ref "SV168") (pin "19") (pinfunction "19_19") (pintype "passive"))
    )
    (net (code "5106") (name "unconnected-(SV168-Pad20)") (class "Default")
      (node (ref "SV168") (pin "20") (pinfunction "20_20") (pintype "passive"))
    )
    (net (code "5107") (name "unconnected-(SV168-Pad21)") (class "Default")
      (node (ref "SV168") (pin "21") (pinfunction "21_21") (pintype "passive"))
    )
    (net (code "5108") (name "unconnected-(SV168-Pad22)") (class "Default")
      (node (ref "SV168") (pin "22") (pinfunction "22_22") (pintype "passive"))
    )
    (net (code "5109") (name "unconnected-(SV168-Pad23)") (class "Default")
      (node (ref "SV168") (pin "23") (pinfunction "23_23") (pintype "passive"))
    )
    (net (code "5110") (name "unconnected-(SV168-Pad24)") (class "Default")
      (node (ref "SV168") (pin "24") (pinfunction "24_24") (pintype "passive"))
    )
    (net (code "5111") (name "unconnected-(SV168-Pad25)") (class "Default")
      (node (ref "SV168") (pin "25") (pinfunction "25_25") (pintype "passive"))
    )
    (net (code "5112") (name "unconnected-(SV168-Pad26)") (class "Default")
      (node (ref "SV168") (pin "26") (pinfunction "26_26") (pintype "passive"))
    )
    (net (code "5113") (name "unconnected-(SV168-Pad27)") (class "Default")
      (node (ref "SV168") (pin "27") (pinfunction "27_27") (pintype "passive"))
    )
    (net (code "5114") (name "unconnected-(SV168-Pad28)") (class "Default")
      (node (ref "SV168") (pin "28") (pinfunction "28_28") (pintype "passive"))
    )
    (net (code "5115") (name "unconnected-(SV168-Pad29)") (class "Default")
      (node (ref "SV168") (pin "29") (pinfunction "29_29") (pintype "passive"))
    )
    (net (code "5116") (name "unconnected-(SV168-Pad30)") (class "Default")
      (node (ref "SV168") (pin "30") (pinfunction "30_30") (pintype "passive"))
    )
    (net (code "5117") (name "unconnected-(SV168-Pad31)") (class "Default")
      (node (ref "SV168") (pin "31") (pinfunction "31_31") (pintype "passive"))
    )
    (net (code "5118") (name "unconnected-(SV168-Pad32)") (class "Default")
      (node (ref "SV168") (pin "32") (pinfunction "32_32") (pintype "passive"))
    )
    (net (code "5119") (name "unconnected-(SV168-Pad33)") (class "Default")
      (node (ref "SV168") (pin "33") (pinfunction "33_33") (pintype "passive"))
    )
    (net (code "5120") (name "unconnected-(SV168-Pad34)") (class "Default")
      (node (ref "SV168") (pin "34") (pinfunction "34_34") (pintype "passive"))
    )
    (net (code "5121") (name "unconnected-(SV168-Pad35)") (class "Default")
      (node (ref "SV168") (pin "35") (pinfunction "35_35") (pintype "passive"))
    )
    (net (code "5122") (name "unconnected-(SV168-Pad36)") (class "Default")
      (node (ref "SV168") (pin "36") (pinfunction "36_36") (pintype "passive"))
    )
    (net (code "5123") (name "unconnected-(SV168-Pad37)") (class "Default")
      (node (ref "SV168") (pin "37") (pinfunction "37_37") (pintype "passive"))
    )
    (net (code "5124") (name "unconnected-(SV168-Pad38)") (class "Default")
      (node (ref "SV168") (pin "38") (pinfunction "38_38") (pintype "passive"))
    )
    (net (code "5125") (name "unconnected-(SV168-Pad39)") (class "Default")
      (node (ref "SV168") (pin "39") (pinfunction "39_39") (pintype "passive"))
    )
    (net (code "5126") (name "unconnected-(SV168-Pad40)") (class "Default")
      (node (ref "SV168") (pin "40") (pinfunction "40_40") (pintype "passive"))
    )
    (net (code "5127") (name "unconnected-(SV169-Pad1)") (class "Default")
      (node (ref "SV169") (pin "1") (pinfunction "1_1") (pintype "passive"))
    )
    (net (code "5128") (name "unconnected-(SV169-Pad2)") (class "Default")
      (node (ref "SV169") (pin "2") (pinfunction "2_2") (pintype "passive"))
    )
    (net (code "5129") (name "unconnected-(SV169-Pad3)") (class "Default")
      (node (ref "SV169") (pin "3") (pinfunction "3_3") (pintype "passive"))
    )
    (net (code "5130") (name "unconnected-(SV169-Pad4)") (class "Default")
      (node (ref "SV169") (pin "4") (pinfunction "4_4") (pintype "passive"))
    )
    (net (code "5131") (name "unconnected-(SV169-Pad5)") (class "Default")
      (node (ref "SV169") (pin "5") (pinfunction "5_5") (pintype "passive"))
    )
    (net (code "5132") (name "unconnected-(SV169-Pad6)") (class "Default")
      (node (ref "SV169") (pin "6") (pinfunction "6_6") (pintype "passive"))
    )
    (net (code "5133") (name "unconnected-(SV169-Pad7)") (class "Default")
      (node (ref "SV169") (pin "7") (pinfunction "7_7") (pintype "passive"))
    )
    (net (code "5134") (name "unconnected-(SV169-Pad8)") (class "Default")
      (node (ref "SV169") (pin "8") (pinfunction "8_8") (pintype "passive"))
    )
    (net (code "5135") (name "unconnected-(SV169-Pad9)") (class "Default")
      (node (ref "SV169") (pin "9") (pinfunction "9_9") (pintype "passive"))
    )
    (net (code "5136") (name "unconnected-(SV169-Pad10)") (class "Default")
      (node (ref "SV169") (pin "10") (pinfunction "10_10") (pintype "passive"))
    )
    (net (code "5137") (name "unconnected-(SV169-Pad11)") (class "Default")
      (node (ref "SV169") (pin "11") (pinfunction "11_11") (pintype "passive"))
    )
    (net (code "5138") (name "unconnected-(SV169-Pad12)") (class "Default")
      (node (ref "SV169") (pin "12") (pinfunction "12_12") (pintype "passive"))
    )
    (net (code "5139") (name "unconnected-(SV169-Pad13)") (class "Default")
      (node (ref "SV169") (pin "13") (pinfunction "13_13") (pintype "passive"))
    )
    (net (code "5140") (name "unconnected-(SV169-Pad14)") (class "Default")
      (node (ref "SV169") (pin "14") (pinfunction "14_14") (pintype "passive"))
    )
    (net (code "5141") (name "unconnected-(SV169-Pad15)") (class "Default")
      (node (ref "SV169") (pin "15") (pinfunction "15_15") (pintype "passive"))
    )
    (net (code "5142") (name "unconnected-(SV169-Pad16)") (class "Default")
      (node (ref "SV169") (pin "16") (pinfunction "16_16") (pintype "passive"))
    )
    (net (code "5143") (name "unconnected-(SV169-Pad17)") (class "Default")
      (node (ref "SV169") (pin "17") (pinfunction "17_17") (pintype "passive"))
    )
    (net (code "5144") (name "unconnected-(SV169-Pad18)") (class "Default")
      (node (ref "SV169") (pin "18") (pinfunction "18_18") (pintype "passive"))
    )
    (net (code "5145") (name "unconnected-(SV169-Pad19)") (class "Default")
      (node (ref "SV169") (pin "19") (pinfunction "19_19") (pintype "passive"))
    )
    (net (code "5146") (name "unconnected-(SV169-Pad20)") (class "Default")
      (node (ref "SV169") (pin "20") (pinfunction "20_20") (pintype "passive"))
    )
    (net (code "5147") (name "unconnected-(SV169-Pad21)") (class "Default")
      (node (ref "SV169") (pin "21") (pinfunction "21_21") (pintype "passive"))
    )
    (net (code "5148") (name "unconnected-(SV169-Pad22)") (class "Default")
      (node (ref "SV169") (pin "22") (pinfunction "22_22") (pintype "passive"))
    )
    (net (code "5149") (name "unconnected-(SV169-Pad23)") (class "Default")
      (node (ref "SV169") (pin "23") (pinfunction "23_23") (pintype "passive"))
    )
    (net (code "5150") (name "unconnected-(SV169-Pad24)") (class "Default")
      (node (ref "SV169") (pin "24") (pinfunction "24_24") (pintype "passive"))
    )
    (net (code "5151") (name "unconnected-(SV169-Pad25)") (class "Default")
      (node (ref "SV169") (pin "25") (pinfunction "25_25") (pintype "passive"))
    )
    (net (code "5152") (name "unconnected-(SV169-Pad26)") (class "Default")
      (node (ref "SV169") (pin "26") (pinfunction "26_26") (pintype "passive"))
    )
    (net (code "5153") (name "unconnected-(SV169-Pad27)") (class "Default")
      (node (ref "SV169") (pin "27") (pinfunction "27_27") (pintype "passive"))
    )
    (net (code "5154") (name "unconnected-(SV169-Pad28)") (class "Default")
      (node (ref "SV169") (pin "28") (pinfunction "28_28") (pintype "passive"))
    )
    (net (code "5155") (name "unconnected-(SV169-Pad29)") (class "Default")
      (node (ref "SV169") (pin "29") (pinfunction "29_29") (pintype "passive"))
    )
    (net (code "5156") (name "unconnected-(SV169-Pad30)") (class "Default")
      (node (ref "SV169") (pin "30") (pinfunction "30_30") (pintype "passive"))
    )
    (net (code "5157") (name "unconnected-(SV169-Pad31)") (class "Default")
      (node (ref "SV169") (pin "31") (pinfunction "31_31") (pintype "passive"))
    )
    (net (code "5158") (name "unconnected-(SV169-Pad32)") (class "Default")
      (node (ref "SV169") (pin "32") (pinfunction "32_32") (pintype "passive"))
    )
    (net (code "5159") (name "unconnected-(SV169-Pad33)") (class "Default")
      (node (ref "SV169") (pin "33") (pinfunction "33_33") (pintype "passive"))
    )
    (net (code "5160") (name "unconnected-(SV169-Pad34)") (class "Default")
      (node (ref "SV169") (pin "34") (pinfunction "34_34") (pintype "passive"))
    )
    (net (code "5161") (name "unconnected-(SV169-Pad35)") (class "Default")
      (node (ref "SV169") (pin "35") (pinfunction "35_35") (pintype "passive"))
    )
    (net (code "5162") (name "unconnected-(SV169-Pad36)") (class "Default")
      (node (ref "SV169") (pin "36") (pinfunction "36_36") (pintype "passive"))
    )
    (net (code "5163") (name "unconnected-(SV169-Pad37)") (class "Default")
      (node (ref "SV169") (pin "37") (pinfunction "37_37") (pintype "passive"))
    )
    (net (code "5164") (name "unconnected-(SV169-Pad38)") (class "Default")
      (node (ref "SV169") (pin "38") (pinfunction "38_38") (pintype "passive"))
    )
    (net (code "5165") (name "unconnected-(SV169-Pad39)") (class "Default")
      (node (ref "SV169") (pin "39") (pinfunction "39_39") (pintype "passive"))
    )
    (net (code "5166") (name "unconnected-(SV169-Pad40)") (class "Default")
      (node (ref "SV169") (pin "40") (pinfunction "40_40") (pintype "passive"))
    )
    (net (code "5167") (name "unconnected-(SV170-Pad1)") (class "Default")
      (node (ref "SV170") (pin "1") (pinfunction "1_1") (pintype "passive"))
    )
    (net (code "5168") (name "unconnected-(SV170-Pad2)") (class "Default")
      (node (ref "SV170") (pin "2") (pinfunction "2_2") (pintype "passive"))
    )
    (net (code "5169") (name "unconnected-(SV170-Pad3)") (class "Default")
      (node (ref "SV170") (pin "3") (pinfunction "3_3") (pintype "passive"))
    )
    (net (code "5170") (name "unconnected-(SV170-Pad4)") (class "Default")
      (node (ref "SV170") (pin "4") (pinfunction "4_4") (pintype "passive"))
    )
    (net (code "5171") (name "unconnected-(SV170-Pad5)") (class "Default")
      (node (ref "SV170") (pin "5") (pinfunction "5_5") (pintype "passive"))
    )
    (net (code "5172") (name "unconnected-(SV170-Pad6)") (class "Default")
      (node (ref "SV170") (pin "6") (pinfunction "6_6") (pintype "passive"))
    )
    (net (code "5173") (name "unconnected-(SV170-Pad7)") (class "Default")
      (node (ref "SV170") (pin "7") (pinfunction "7_7") (pintype "passive"))
    )
    (net (code "5174") (name "unconnected-(SV170-Pad8)") (class "Default")
      (node (ref "SV170") (pin "8") (pinfunction "8_8") (pintype "passive"))
    )
    (net (code "5175") (name "unconnected-(SV170-Pad9)") (class "Default")
      (node (ref "SV170") (pin "9") (pinfunction "9_9") (pintype "passive"))
    )
    (net (code "5176") (name "unconnected-(SV170-Pad10)") (class "Default")
      (node (ref "SV170") (pin "10") (pinfunction "10_10") (pintype "passive"))
    )
    (net (code "5177") (name "unconnected-(SV170-Pad11)") (class "Default")
      (node (ref "SV170") (pin "11") (pinfunction "11_11") (pintype "passive"))
    )
    (net (code "5178") (name "unconnected-(SV170-Pad12)") (class "Default")
      (node (ref "SV170") (pin "12") (pinfunction "12_12") (pintype "passive"))
    )
    (net (code "5179") (name "unconnected-(SV170-Pad13)") (class "Default")
      (node (ref "SV170") (pin "13") (pinfunction "13_13") (pintype "passive"))
    )
    (net (code "5180") (name "unconnected-(SV170-Pad14)") (class "Default")
      (node (ref "SV170") (pin "14") (pinfunction "14_14") (pintype "passive"))
    )
    (net (code "5181") (name "unconnected-(SV170-Pad15)") (class "Default")
      (node (ref "SV170") (pin "15") (pinfunction "15_15") (pintype "passive"))
    )
    (net (code "5182") (name "unconnected-(SV170-Pad16)") (class "Default")
      (node (ref "SV170") (pin "16") (pinfunction "16_16") (pintype "passive"))
    )
    (net (code "5183") (name "unconnected-(SV170-Pad17)") (class "Default")
      (node (ref "SV170") (pin "17") (pinfunction "17_17") (pintype "passive"))
    )
    (net (code "5184") (name "unconnected-(SV170-Pad18)") (class "Default")
      (node (ref "SV170") (pin "18") (pinfunction "18_18") (pintype "passive"))
    )
    (net (code "5185") (name "unconnected-(SV170-Pad19)") (class "Default")
      (node (ref "SV170") (pin "19") (pinfunction "19_19") (pintype "passive"))
    )
    (net (code "5186") (name "unconnected-(SV170-Pad20)") (class "Default")
      (node (ref "SV170") (pin "20") (pinfunction "20_20") (pintype "passive"))
    )
    (net (code "5187") (name "unconnected-(SV170-Pad21)") (class "Default")
      (node (ref "SV170") (pin "21") (pinfunction "21_21") (pintype "passive"))
    )
    (net (code "5188") (name "unconnected-(SV170-Pad22)") (class "Default")
      (node (ref "SV170") (pin "22") (pinfunction "22_22") (pintype "passive"))
    )
    (net (code "5189") (name "unconnected-(SV170-Pad23)") (class "Default")
      (node (ref "SV170") (pin "23") (pinfunction "23_23") (pintype "passive"))
    )
    (net (code "5190") (name "unconnected-(SV170-Pad24)") (class "Default")
      (node (ref "SV170") (pin "24") (pinfunction "24_24") (pintype "passive"))
    )
    (net (code "5191") (name "unconnected-(SV170-Pad25)") (class "Default")
      (node (ref "SV170") (pin "25") (pinfunction "25_25") (pintype "passive"))
    )
    (net (code "5192") (name "unconnected-(SV170-Pad26)") (class "Default")
      (node (ref "SV170") (pin "26") (pinfunction "26_26") (pintype "passive"))
    )
    (net (code "5193") (name "unconnected-(SV170-Pad27)") (class "Default")
      (node (ref "SV170") (pin "27") (pinfunction "27_27") (pintype "passive"))
    )
    (net (code "5194") (name "unconnected-(SV170-Pad28)") (class "Default")
      (node (ref "SV170") (pin "28") (pinfunction "28_28") (pintype "passive"))
    )
    (net (code "5195") (name "unconnected-(SV170-Pad29)") (class "Default")
      (node (ref "SV170") (pin "29") (pinfunction "29_29") (pintype "passive"))
    )
    (net (code "5196") (name "unconnected-(SV170-Pad30)") (class "Default")
      (node (ref "SV170") (pin "30") (pinfunction "30_30") (pintype "passive"))
    )
    (net (code "5197") (name "unconnected-(SV170-Pad31)") (class "Default")
      (node (ref "SV170") (pin "31") (pinfunction "31_31") (pintype "passive"))
    )
    (net (code "5198") (name "unconnected-(SV170-Pad32)") (class "Default")
      (node (ref "SV170") (pin "32") (pinfunction "32_32") (pintype "passive"))
    )
    (net (code "5199") (name "unconnected-(SV170-Pad33)") (class "Default")
      (node (ref "SV170") (pin "33") (pinfunction "33_33") (pintype "passive"))
    )
    (net (code "5200") (name "unconnected-(SV170-Pad34)") (class "Default")
      (node (ref "SV170") (pin "34") (pinfunction "34_34") (pintype "passive"))
    )
    (net (code "5201") (name "unconnected-(SV170-Pad35)") (class "Default")
      (node (ref "SV170") (pin "35") (pinfunction "35_35") (pintype "passive"))
    )
    (net (code "5202") (name "unconnected-(SV170-Pad36)") (class "Default")
      (node (ref "SV170") (pin "36") (pinfunction "36_36") (pintype "passive"))
    )
    (net (code "5203") (name "unconnected-(SV170-Pad37)") (class "Default")
      (node (ref "SV170") (pin "37") (pinfunction "37_37") (pintype "passive"))
    )
    (net (code "5204") (name "unconnected-(SV170-Pad38)") (class "Default")
      (node (ref "SV170") (pin "38") (pinfunction "38_38") (pintype "passive"))
    )
    (net (code "5205") (name "unconnected-(SV170-Pad39)") (class "Default")
      (node (ref "SV170") (pin "39") (pinfunction "39_39") (pintype "passive"))
    )
    (net (code "5206") (name "unconnected-(SV170-Pad40)") (class "Default")
      (node (ref "SV170") (pin "40") (pinfunction "40_40") (pintype "passive"))
    )
    (net (code "5207") (name "unconnected-(SV171-Pad1)") (class "Default")
      (node (ref "SV171") (pin "1") (pinfunction "1_1") (pintype "passive"))
    )
    (net (code "5208") (name "unconnected-(SV171-Pad2)") (class "Default")
      (node (ref "SV171") (pin "2") (pinfunction "2_2") (pintype "passive"))
    )
    (net (code "5209") (name "unconnected-(SV171-Pad3)") (class "Default")
      (node (ref "SV171") (pin "3") (pinfunction "3_3") (pintype "passive"))
    )
    (net (code "5210") (name "unconnected-(SV171-Pad4)") (class "Default")
      (node (ref "SV171") (pin "4") (pinfunction "4_4") (pintype "passive"))
    )
    (net (code "5211") (name "unconnected-(SV171-Pad5)") (class "Default")
      (node (ref "SV171") (pin "5") (pinfunction "5_5") (pintype "passive"))
    )
    (net (code "5212") (name "unconnected-(SV171-Pad6)") (class "Default")
      (node (ref "SV171") (pin "6") (pinfunction "6_6") (pintype "passive"))
    )
    (net (code "5213") (name "unconnected-(SV171-Pad7)") (class "Default")
      (node (ref "SV171") (pin "7") (pinfunction "7_7") (pintype "passive"))
    )
    (net (code "5214") (name "unconnected-(SV171-Pad8)") (class "Default")
      (node (ref "SV171") (pin "8") (pinfunction "8_8") (pintype "passive"))
    )
    (net (code "5215") (name "unconnected-(SV171-Pad9)") (class "Default")
      (node (ref "SV171") (pin "9") (pinfunction "9_9") (pintype "passive"))
    )
    (net (code "5216") (name "unconnected-(SV171-Pad10)") (class "Default")
      (node (ref "SV171") (pin "10") (pinfunction "10_10") (pintype "passive"))
    )
    (net (code "5217") (name "unconnected-(SV171-Pad11)") (class "Default")
      (node (ref "SV171") (pin "11") (pinfunction "11_11") (pintype "passive"))
    )
    (net (code "5218") (name "unconnected-(SV171-Pad12)") (class "Default")
      (node (ref "SV171") (pin "12") (pinfunction "12_12") (pintype "passive"))
    )
    (net (code "5219") (name "unconnected-(SV171-Pad13)") (class "Default")
      (node (ref "SV171") (pin "13") (pinfunction "13_13") (pintype "passive"))
    )
    (net (code "5220") (name "unconnected-(SV171-Pad14)") (class "Default")
      (node (ref "SV171") (pin "14") (pinfunction "14_14") (pintype "passive"))
    )
    (net (code "5221") (name "unconnected-(SV171-Pad15)") (class "Default")
      (node (ref "SV171") (pin "15") (pinfunction "15_15") (pintype "passive"))
    )
    (net (code "5222") (name "unconnected-(SV171-Pad16)") (class "Default")
      (node (ref "SV171") (pin "16") (pinfunction "16_16") (pintype "passive"))
    )
    (net (code "5223") (name "unconnected-(SV171-Pad17)") (class "Default")
      (node (ref "SV171") (pin "17") (pinfunction "17_17") (pintype "passive"))
    )
    (net (code "5224") (name "unconnected-(SV171-Pad18)") (class "Default")
      (node (ref "SV171") (pin "18") (pinfunction "18_18") (pintype "passive"))
    )
    (net (code "5225") (name "unconnected-(SV171-Pad19)") (class "Default")
      (node (ref "SV171") (pin "19") (pinfunction "19_19") (pintype "passive"))
    )
    (net (code "5226") (name "unconnected-(SV171-Pad20)") (class "Default")
      (node (ref "SV171") (pin "20") (pinfunction "20_20") (pintype "passive"))
    )
    (net (code "5227") (name "unconnected-(SV171-Pad21)") (class "Default")
      (node (ref "SV171") (pin "21") (pinfunction "21_21") (pintype "passive"))
    )
    (net (code "5228") (name "unconnected-(SV171-Pad22)") (class "Default")
      (node (ref "SV171") (pin "22") (pinfunction "22_22") (pintype "passive"))
    )
    (net (code "5229") (name "unconnected-(SV171-Pad23)") (class "Default")
      (node (ref "SV171") (pin "23") (pinfunction "23_23") (pintype "passive"))
    )
    (net (code "5230") (name "unconnected-(SV171-Pad24)") (class "Default")
      (node (ref "SV171") (pin "24") (pinfunction "24_24") (pintype "passive"))
    )
    (net (code "5231") (name "unconnected-(SV172-Pad1)") (class "Default")
      (node (ref "SV172") (pin "1") (pinfunction "1_1") (pintype "passive"))
    )
    (net (code "5232") (name "unconnected-(SV172-Pad2)") (class "Default")
      (node (ref "SV172") (pin "2") (pinfunction "2_2") (pintype "passive"))
    )
    (net (code "5233") (name "unconnected-(SV172-Pad3)") (class "Default")
      (node (ref "SV172") (pin "3") (pinfunction "3_3") (pintype "passive"))
    )
    (net (code "5234") (name "unconnected-(SV172-Pad4)") (class "Default")
      (node (ref "SV172") (pin "4") (pinfunction "4_4") (pintype "passive"))
    )
    (net (code "5235") (name "unconnected-(SV172-Pad5)") (class "Default")
      (node (ref "SV172") (pin "5") (pinfunction "5_5") (pintype "passive"))
    )
    (net (code "5236") (name "unconnected-(SV172-Pad6)") (class "Default")
      (node (ref "SV172") (pin "6") (pinfunction "6_6") (pintype "passive"))
    )
    (net (code "5237") (name "unconnected-(SV172-Pad7)") (class "Default")
      (node (ref "SV172") (pin "7") (pinfunction "7_7") (pintype "passive"))
    )
    (net (code "5238") (name "unconnected-(SV172-Pad8)") (class "Default")
      (node (ref "SV172") (pin "8") (pinfunction "8_8") (pintype "passive"))
    )
    (net (code "5239") (name "unconnected-(SV172-Pad9)") (class "Default")
      (node (ref "SV172") (pin "9") (pinfunction "9_9") (pintype "passive"))
    )
    (net (code "5240") (name "unconnected-(SV172-Pad10)") (class "Default")
      (node (ref "SV172") (pin "10") (pinfunction "10_10") (pintype "passive"))
    )
    (net (code "5241") (name "unconnected-(SV172-Pad11)") (class "Default")
      (node (ref "SV172") (pin "11") (pinfunction "11_11") (pintype "passive"))
    )
    (net (code "5242") (name "unconnected-(SV172-Pad12)") (class "Default")
      (node (ref "SV172") (pin "12") (pinfunction "12_12") (pintype "passive"))
    )
    (net (code "5243") (name "unconnected-(SV172-Pad13)") (class "Default")
      (node (ref "SV172") (pin "13") (pinfunction "13_13") (pintype "passive"))
    )
    (net (code "5244") (name "unconnected-(SV172-Pad14)") (class "Default")
      (node (ref "SV172") (pin "14") (pinfunction "14_14") (pintype "passive"))
    )
    (net (code "5245") (name "unconnected-(SV172-Pad15)") (class "Default")
      (node (ref "SV172") (pin "15") (pinfunction "15_15") (pintype "passive"))
    )
    (net (code "5246") (name "unconnected-(SV172-Pad16)") (class "Default")
      (node (ref "SV172") (pin "16") (pinfunction "16_16") (pintype "passive"))
    )
    (net (code "5247") (name "unconnected-(SV172-Pad17)") (class "Default")
      (node (ref "SV172") (pin "17") (pinfunction "17_17") (pintype "passive"))
    )
    (net (code "5248") (name "unconnected-(SV172-Pad18)") (class "Default")
      (node (ref "SV172") (pin "18") (pinfunction "18_18") (pintype "passive"))
    )
    (net (code "5249") (name "unconnected-(SV172-Pad19)") (class "Default")
      (node (ref "SV172") (pin "19") (pinfunction "19_19") (pintype "passive"))
    )
    (net (code "5250") (name "unconnected-(SV172-Pad20)") (class "Default")
      (node (ref "SV172") (pin "20") (pinfunction "20_20") (pintype "passive"))
    )
    (net (code "5251") (name "unconnected-(SV172-Pad21)") (class "Default")
      (node (ref "SV172") (pin "21") (pinfunction "21_21") (pintype "passive"))
    )
    (net (code "5252") (name "unconnected-(SV172-Pad22)") (class "Default")
      (node (ref "SV172") (pin "22") (pinfunction "22_22") (pintype "passive"))
    )
    (net (code "5253") (name "unconnected-(SV172-Pad23)") (class "Default")
      (node (ref "SV172") (pin "23") (pinfunction "23_23") (pintype "passive"))
    )
    (net (code "5254") (name "unconnected-(SV172-Pad24)") (class "Default")
      (node (ref "SV172") (pin "24") (pinfunction "24_24") (pintype "passive"))
    )
    (net (code "5255") (name "unconnected-(SV173-Pad1)") (class "Default")
      (node (ref "SV173") (pin "1") (pinfunction "1_1") (pintype "passive"))
    )
    (net (code "5256") (name "unconnected-(SV173-Pad2)") (class "Default")
      (node (ref "SV173") (pin "2") (pinfunction "2_2") (pintype "passive"))
    )
    (net (code "5257") (name "unconnected-(SV173-Pad3)") (class "Default")
      (node (ref "SV173") (pin "3") (pinfunction "3_3") (pintype "passive"))
    )
    (net (code "5258") (name "unconnected-(SV173-Pad4)") (class "Default")
      (node (ref "SV173") (pin "4") (pinfunction "4_4") (pintype "passive"))
    )
    (net (code "5259") (name "unconnected-(SV173-Pad5)") (class "Default")
      (node (ref "SV173") (pin "5") (pinfunction "5_5") (pintype "passive"))
    )
    (net (code "5260") (name "unconnected-(SV173-Pad6)") (class "Default")
      (node (ref "SV173") (pin "6") (pinfunction "6_6") (pintype "passive"))
    )
    (net (code "5261") (name "unconnected-(SV173-Pad7)") (class "Default")
      (node (ref "SV173") (pin "7") (pinfunction "7_7") (pintype "passive"))
    )
    (net (code "5262") (name "unconnected-(SV173-Pad8)") (class "Default")
      (node (ref "SV173") (pin "8") (pinfunction "8_8") (pintype "passive"))
    )
    (net (code "5263") (name "unconnected-(SV173-Pad9)") (class "Default")
      (node (ref "SV173") (pin "9") (pinfunction "9_9") (pintype "passive"))
    )
    (net (code "5264") (name "unconnected-(SV173-Pad10)") (class "Default")
      (node (ref "SV173") (pin "10") (pinfunction "10_10") (pintype "passive"))
    )
    (net (code "5265") (name "unconnected-(SV173-Pad11)") (class "Default")
      (node (ref "SV173") (pin "11") (pinfunction "11_11") (pintype "passive"))
    )
    (net (code "5266") (name "unconnected-(SV173-Pad12)") (class "Default")
      (node (ref "SV173") (pin "12") (pinfunction "12_12") (pintype "passive"))
    )
    (net (code "5267") (name "unconnected-(SV173-Pad13)") (class "Default")
      (node (ref "SV173") (pin "13") (pinfunction "13_13") (pintype "passive"))
    )
    (net (code "5268") (name "unconnected-(SV173-Pad14)") (class "Default")
      (node (ref "SV173") (pin "14") (pinfunction "14_14") (pintype "passive"))
    )
    (net (code "5269") (name "unconnected-(SV173-Pad15)") (class "Default")
      (node (ref "SV173") (pin "15") (pinfunction "15_15") (pintype "passive"))
    )
    (net (code "5270") (name "unconnected-(SV173-Pad16)") (class "Default")
      (node (ref "SV173") (pin "16") (pinfunction "16_16") (pintype "passive"))
    )
    (net (code "5271") (name "unconnected-(SV173-Pad17)") (class "Default")
      (node (ref "SV173") (pin "17") (pinfunction "17_17") (pintype "passive"))
    )
    (net (code "5272") (name "unconnected-(SV173-Pad18)") (class "Default")
      (node (ref "SV173") (pin "18") (pinfunction "18_18") (pintype "passive"))
    )
    (net (code "5273") (name "unconnected-(SV173-Pad19)") (class "Default")
      (node (ref "SV173") (pin "19") (pinfunction "19_19") (pintype "passive"))
    )
    (net (code "5274") (name "unconnected-(SV173-Pad20)") (class "Default")
      (node (ref "SV173") (pin "20") (pinfunction "20_20") (pintype "passive"))
    )
    (net (code "5275") (name "unconnected-(SV173-Pad21)") (class "Default")
      (node (ref "SV173") (pin "21") (pinfunction "21_21") (pintype "passive"))
    )
    (net (code "5276") (name "unconnected-(SV173-Pad22)") (class "Default")
      (node (ref "SV173") (pin "22") (pinfunction "22_22") (pintype "passive"))
    )
    (net (code "5277") (name "unconnected-(SV173-Pad23)") (class "Default")
      (node (ref "SV173") (pin "23") (pinfunction "23_23") (pintype "passive"))
    )
    (net (code "5278") (name "unconnected-(SV173-Pad24)") (class "Default")
      (node (ref "SV173") (pin "24") (pinfunction "24_24") (pintype "passive"))
    )
    (net (code "5279") (name "unconnected-(SV174-Pad1)") (class "Default")
      (node (ref "SV174") (pin "1") (pinfunction "1_1") (pintype "passive"))
    )
    (net (code "5280") (name "unconnected-(SV174-Pad2)") (class "Default")
      (node (ref "SV174") (pin "2") (pinfunction "2_2") (pintype "passive"))
    )
    (net (code "5281") (name "unconnected-(SV174-Pad3)") (class "Default")
      (node (ref "SV174") (pin "3") (pinfunction "3_3") (pintype "passive"))
    )
    (net (code "5282") (name "unconnected-(SV174-Pad4)") (class "Default")
      (node (ref "SV174") (pin "4") (pinfunction "4_4") (pintype "passive"))
    )
    (net (code "5283") (name "unconnected-(SV174-Pad5)") (class "Default")
      (node (ref "SV174") (pin "5") (pinfunction "5_5") (pintype "passive"))
    )
    (net (code "5284") (name "unconnected-(SV174-Pad6)") (class "Default")
      (node (ref "SV174") (pin "6") (pinfunction "6_6") (pintype "passive"))
    )
    (net (code "5285") (name "unconnected-(SV174-Pad7)") (class "Default")
      (node (ref "SV174") (pin "7") (pinfunction "7_7") (pintype "passive"))
    )
    (net (code "5286") (name "unconnected-(SV174-Pad8)") (class "Default")
      (node (ref "SV174") (pin "8") (pinfunction "8_8") (pintype "passive"))
    )
    (net (code "5287") (name "unconnected-(SV174-Pad9)") (class "Default")
      (node (ref "SV174") (pin "9") (pinfunction "9_9") (pintype "passive"))
    )
    (net (code "5288") (name "unconnected-(SV174-Pad10)") (class "Default")
      (node (ref "SV174") (pin "10") (pinfunction "10_10") (pintype "passive"))
    )
    (net (code "5289") (name "unconnected-(SV174-Pad11)") (class "Default")
      (node (ref "SV174") (pin "11") (pinfunction "11_11") (pintype "passive"))
    )
    (net (code "5290") (name "unconnected-(SV174-Pad12)") (class "Default")
      (node (ref "SV174") (pin "12") (pinfunction "12_12") (pintype "passive"))
    )
    (net (code "5291") (name "unconnected-(SV174-Pad13)") (class "Default")
      (node (ref "SV174") (pin "13") (pinfunction "13_13") (pintype "passive"))
    )
    (net (code "5292") (name "unconnected-(SV174-Pad14)") (class "Default")
      (node (ref "SV174") (pin "14") (pinfunction "14_14") (pintype "passive"))
    )
    (net (code "5293") (name "unconnected-(SV174-Pad15)") (class "Default")
      (node (ref "SV174") (pin "15") (pinfunction "15_15") (pintype "passive"))
    )
    (net (code "5294") (name "unconnected-(SV174-Pad16)") (class "Default")
      (node (ref "SV174") (pin "16") (pinfunction "16_16") (pintype "passive"))
    )
    (net (code "5295") (name "unconnected-(SV174-Pad17)") (class "Default")
      (node (ref "SV174") (pin "17") (pinfunction "17_17") (pintype "passive"))
    )
    (net (code "5296") (name "unconnected-(SV174-Pad18)") (class "Default")
      (node (ref "SV174") (pin "18") (pinfunction "18_18") (pintype "passive"))
    )
    (net (code "5297") (name "unconnected-(SV174-Pad19)") (class "Default")
      (node (ref "SV174") (pin "19") (pinfunction "19_19") (pintype "passive"))
    )
    (net (code "5298") (name "unconnected-(SV174-Pad20)") (class "Default")
      (node (ref "SV174") (pin "20") (pinfunction "20_20") (pintype "passive"))
    )
    (net (code "5299") (name "unconnected-(SV174-Pad21)") (class "Default")
      (node (ref "SV174") (pin "21") (pinfunction "21_21") (pintype "passive"))
    )
    (net (code "5300") (name "unconnected-(SV174-Pad22)") (class "Default")
      (node (ref "SV174") (pin "22") (pinfunction "22_22") (pintype "passive"))
    )
    (net (code "5301") (name "unconnected-(SV174-Pad23)") (class "Default")
      (node (ref "SV174") (pin "23") (pinfunction "23_23") (pintype "passive"))
    )
    (net (code "5302") (name "unconnected-(SV174-Pad24)") (class "Default")
      (node (ref "SV174") (pin "24") (pinfunction "24_24") (pintype "passive"))
    )
    (net (code "5303") (name "unconnected-(SV175-Pad1)") (class "Default")
      (node (ref "SV175") (pin "1") (pinfunction "1_1") (pintype "passive"))
    )
    (net (code "5304") (name "unconnected-(SV175-Pad2)") (class "Default")
      (node (ref "SV175") (pin "2") (pinfunction "2_2") (pintype "passive"))
    )
    (net (code "5305") (name "unconnected-(SV175-Pad3)") (class "Default")
      (node (ref "SV175") (pin "3") (pinfunction "3_3") (pintype "passive"))
    )
    (net (code "5306") (name "unconnected-(SV175-Pad4)") (class "Default")
      (node (ref "SV175") (pin "4") (pinfunction "4_4") (pintype "passive"))
    )
    (net (code "5307") (name "unconnected-(SV175-Pad5)") (class "Default")
      (node (ref "SV175") (pin "5") (pinfunction "5_5") (pintype "passive"))
    )
    (net (code "5308") (name "unconnected-(SV175-Pad6)") (class "Default")
      (node (ref "SV175") (pin "6") (pinfunction "6_6") (pintype "passive"))
    )
    (net (code "5309") (name "unconnected-(SV175-Pad7)") (class "Default")
      (node (ref "SV175") (pin "7") (pinfunction "7_7") (pintype "passive"))
    )
    (net (code "5310") (name "unconnected-(SV175-Pad8)") (class "Default")
      (node (ref "SV175") (pin "8") (pinfunction "8_8") (pintype "passive"))
    )
    (net (code "5311") (name "unconnected-(SV175-Pad9)") (class "Default")
      (node (ref "SV175") (pin "9") (pinfunction "9_9") (pintype "passive"))
    )
    (net (code "5312") (name "unconnected-(SV175-Pad10)") (class "Default")
      (node (ref "SV175") (pin "10") (pinfunction "10_10") (pintype "passive"))
    )
    (net (code "5313") (name "unconnected-(SV175-Pad11)") (class "Default")
      (node (ref "SV175") (pin "11") (pinfunction "11_11") (pintype "passive"))
    )
    (net (code "5314") (name "unconnected-(SV175-Pad12)") (class "Default")
      (node (ref "SV175") (pin "12") (pinfunction "12_12") (pintype "passive"))
    )
    (net (code "5315") (name "unconnected-(SV175-Pad13)") (class "Default")
      (node (ref "SV175") (pin "13") (pinfunction "13_13") (pintype "passive"))
    )
    (net (code "5316") (name "unconnected-(SV175-Pad14)") (class "Default")
      (node (ref "SV175") (pin "14") (pinfunction "14_14") (pintype "passive"))
    )
    (net (code "5317") (name "unconnected-(SV175-Pad15)") (class "Default")
      (node (ref "SV175") (pin "15") (pinfunction "15_15") (pintype "passive"))
    )
    (net (code "5318") (name "unconnected-(SV175-Pad16)") (class "Default")
      (node (ref "SV175") (pin "16") (pinfunction "16_16") (pintype "passive"))
    )
    (net (code "5319") (name "unconnected-(SV175-Pad17)") (class "Default")
      (node (ref "SV175") (pin "17") (pinfunction "17_17") (pintype "passive"))
    )
    (net (code "5320") (name "unconnected-(SV175-Pad18)") (class "Default")
      (node (ref "SV175") (pin "18") (pinfunction "18_18") (pintype "passive"))
    )
    (net (code "5321") (name "unconnected-(SV175-Pad19)") (class "Default")
      (node (ref "SV175") (pin "19") (pinfunction "19_19") (pintype "passive"))
    )
    (net (code "5322") (name "unconnected-(SV175-Pad20)") (class "Default")
      (node (ref "SV175") (pin "20") (pinfunction "20_20") (pintype "passive"))
    )
    (net (code "5323") (name "unconnected-(SV175-Pad21)") (class "Default")
      (node (ref "SV175") (pin "21") (pinfunction "21_21") (pintype "passive"))
    )
    (net (code "5324") (name "unconnected-(SV175-Pad22)") (class "Default")
      (node (ref "SV175") (pin "22") (pinfunction "22_22") (pintype "passive"))
    )
    (net (code "5325") (name "unconnected-(SV175-Pad23)") (class "Default")
      (node (ref "SV175") (pin "23") (pinfunction "23_23") (pintype "passive"))
    )
    (net (code "5326") (name "unconnected-(SV175-Pad24)") (class "Default")
      (node (ref "SV175") (pin "24") (pinfunction "24_24") (pintype "passive"))
    )
    (net (code "5327") (name "unconnected-(SV175-Pad25)") (class "Default")
      (node (ref "SV175") (pin "25") (pinfunction "25_25") (pintype "passive"))
    )
    (net (code "5328") (name "unconnected-(SV175-Pad26)") (class "Default")
      (node (ref "SV175") (pin "26") (pinfunction "26_26") (pintype "passive"))
    )
    (net (code "5329") (name "unconnected-(SV175-Pad27)") (class "Default")
      (node (ref "SV175") (pin "27") (pinfunction "27_27") (pintype "passive"))
    )
    (net (code "5330") (name "unconnected-(SV175-Pad28)") (class "Default")
      (node (ref "SV175") (pin "28") (pinfunction "28_28") (pintype "passive"))
    )
    (net (code "5331") (name "unconnected-(SV175-Pad29)") (class "Default")
      (node (ref "SV175") (pin "29") (pinfunction "29_29") (pintype "passive"))
    )
    (net (code "5332") (name "unconnected-(SV175-Pad30)") (class "Default")
      (node (ref "SV175") (pin "30") (pinfunction "30_30") (pintype "passive"))
    )
    (net (code "5333") (name "unconnected-(SV175-Pad31)") (class "Default")
      (node (ref "SV175") (pin "31") (pinfunction "31_31") (pintype "passive"))
    )
    (net (code "5334") (name "unconnected-(SV175-Pad32)") (class "Default")
      (node (ref "SV175") (pin "32") (pinfunction "32_32") (pintype "passive"))
    )
    (net (code "5335") (name "unconnected-(SV175-Pad33)") (class "Default")
      (node (ref "SV175") (pin "33") (pinfunction "33_33") (pintype "passive"))
    )
    (net (code "5336") (name "unconnected-(SV175-Pad34)") (class "Default")
      (node (ref "SV175") (pin "34") (pinfunction "34_34") (pintype "passive"))
    )
    (net (code "5337") (name "unconnected-(SV175-Pad35)") (class "Default")
      (node (ref "SV175") (pin "35") (pinfunction "35_35") (pintype "passive"))
    )
    (net (code "5338") (name "unconnected-(SV175-Pad36)") (class "Default")
      (node (ref "SV175") (pin "36") (pinfunction "36_36") (pintype "passive"))
    )
    (net (code "5339") (name "unconnected-(SV175-Pad37)") (class "Default")
      (node (ref "SV175") (pin "37") (pinfunction "37_37") (pintype "passive"))
    )
    (net (code "5340") (name "unconnected-(SV175-Pad38)") (class "Default")
      (node (ref "SV175") (pin "38") (pinfunction "38_38") (pintype "passive"))
    )
    (net (code "5341") (name "unconnected-(SV175-Pad39)") (class "Default")
      (node (ref "SV175") (pin "39") (pinfunction "39_39") (pintype "passive"))
    )
    (net (code "5342") (name "unconnected-(SV175-Pad40)") (class "Default")
      (node (ref "SV175") (pin "40") (pinfunction "40_40") (pintype "passive"))
    )
    (net (code "5343") (name "unconnected-(SV176-Pad1)") (class "Default")
      (node (ref "SV176") (pin "1") (pinfunction "1_1") (pintype "passive"))
    )
    (net (code "5344") (name "unconnected-(SV176-Pad2)") (class "Default")
      (node (ref "SV176") (pin "2") (pinfunction "2_2") (pintype "passive"))
    )
    (net (code "5345") (name "unconnected-(SV176-Pad3)") (class "Default")
      (node (ref "SV176") (pin "3") (pinfunction "3_3") (pintype "passive"))
    )
    (net (code "5346") (name "unconnected-(SV176-Pad4)") (class "Default")
      (node (ref "SV176") (pin "4") (pinfunction "4_4") (pintype "passive"))
    )
    (net (code "5347") (name "unconnected-(SV176-Pad5)") (class "Default")
      (node (ref "SV176") (pin "5") (pinfunction "5_5") (pintype "passive"))
    )
    (net (code "5348") (name "unconnected-(SV176-Pad6)") (class "Default")
      (node (ref "SV176") (pin "6") (pinfunction "6_6") (pintype "passive"))
    )
    (net (code "5349") (name "unconnected-(SV176-Pad7)") (class "Default")
      (node (ref "SV176") (pin "7") (pinfunction "7_7") (pintype "passive"))
    )
    (net (code "5350") (name "unconnected-(SV176-Pad8)") (class "Default")
      (node (ref "SV176") (pin "8") (pinfunction "8_8") (pintype "passive"))
    )
    (net (code "5351") (name "unconnected-(SV176-Pad9)") (class "Default")
      (node (ref "SV176") (pin "9") (pinfunction "9_9") (pintype "passive"))
    )
    (net (code "5352") (name "unconnected-(SV176-Pad10)") (class "Default")
      (node (ref "SV176") (pin "10") (pinfunction "10_10") (pintype "passive"))
    )
    (net (code "5353") (name "unconnected-(SV176-Pad11)") (class "Default")
      (node (ref "SV176") (pin "11") (pinfunction "11_11") (pintype "passive"))
    )
    (net (code "5354") (name "unconnected-(SV176-Pad12)") (class "Default")
      (node (ref "SV176") (pin "12") (pinfunction "12_12") (pintype "passive"))
    )
    (net (code "5355") (name "unconnected-(SV176-Pad13)") (class "Default")
      (node (ref "SV176") (pin "13") (pinfunction "13_13") (pintype "passive"))
    )
    (net (code "5356") (name "unconnected-(SV176-Pad14)") (class "Default")
      (node (ref "SV176") (pin "14") (pinfunction "14_14") (pintype "passive"))
    )
    (net (code "5357") (name "unconnected-(SV176-Pad15)") (class "Default")
      (node (ref "SV176") (pin "15") (pinfunction "15_15") (pintype "passive"))
    )
    (net (code "5358") (name "unconnected-(SV176-Pad16)") (class "Default")
      (node (ref "SV176") (pin "16") (pinfunction "16_16") (pintype "passive"))
    )
    (net (code "5359") (name "unconnected-(SV176-Pad17)") (class "Default")
      (node (ref "SV176") (pin "17") (pinfunction "17_17") (pintype "passive"))
    )
    (net (code "5360") (name "unconnected-(SV176-Pad18)") (class "Default")
      (node (ref "SV176") (pin "18") (pinfunction "18_18") (pintype "passive"))
    )
    (net (code "5361") (name "unconnected-(SV176-Pad19)") (class "Default")
      (node (ref "SV176") (pin "19") (pinfunction "19_19") (pintype "passive"))
    )
    (net (code "5362") (name "unconnected-(SV176-Pad20)") (class "Default")
      (node (ref "SV176") (pin "20") (pinfunction "20_20") (pintype "passive"))
    )
    (net (code "5363") (name "unconnected-(SV176-Pad21)") (class "Default")
      (node (ref "SV176") (pin "21") (pinfunction "21_21") (pintype "passive"))
    )
    (net (code "5364") (name "unconnected-(SV176-Pad22)") (class "Default")
      (node (ref "SV176") (pin "22") (pinfunction "22_22") (pintype "passive"))
    )
    (net (code "5365") (name "unconnected-(SV176-Pad23)") (class "Default")
      (node (ref "SV176") (pin "23") (pinfunction "23_23") (pintype "passive"))
    )
    (net (code "5366") (name "unconnected-(SV176-Pad24)") (class "Default")
      (node (ref "SV176") (pin "24") (pinfunction "24_24") (pintype "passive"))
    )
    (net (code "5367") (name "unconnected-(SV176-Pad25)") (class "Default")
      (node (ref "SV176") (pin "25") (pinfunction "25_25") (pintype "passive"))
    )
    (net (code "5368") (name "unconnected-(SV176-Pad26)") (class "Default")
      (node (ref "SV176") (pin "26") (pinfunction "26_26") (pintype "passive"))
    )
    (net (code "5369") (name "unconnected-(SV176-Pad27)") (class "Default")
      (node (ref "SV176") (pin "27") (pinfunction "27_27") (pintype "passive"))
    )
    (net (code "5370") (name "unconnected-(SV176-Pad28)") (class "Default")
      (node (ref "SV176") (pin "28") (pinfunction "28_28") (pintype "passive"))
    )
    (net (code "5371") (name "unconnected-(SV176-Pad29)") (class "Default")
      (node (ref "SV176") (pin "29") (pinfunction "29_29") (pintype "passive"))
    )
    (net (code "5372") (name "unconnected-(SV176-Pad30)") (class "Default")
      (node (ref "SV176") (pin "30") (pinfunction "30_30") (pintype "passive"))
    )
    (net (code "5373") (name "unconnected-(SV176-Pad31)") (class "Default")
      (node (ref "SV176") (pin "31") (pinfunction "31_31") (pintype "passive"))
    )
    (net (code "5374") (name "unconnected-(SV176-Pad32)") (class "Default")
      (node (ref "SV176") (pin "32") (pinfunction "32_32") (pintype "passive"))
    )
    (net (code "5375") (name "unconnected-(SV176-Pad33)") (class "Default")
      (node (ref "SV176") (pin "33") (pinfunction "33_33") (pintype "passive"))
    )
    (net (code "5376") (name "unconnected-(SV176-Pad34)") (class "Default")
      (node (ref "SV176") (pin "34") (pinfunction "34_34") (pintype "passive"))
    )
    (net (code "5377") (name "unconnected-(SV176-Pad35)") (class "Default")
      (node (ref "SV176") (pin "35") (pinfunction "35_35") (pintype "passive"))
    )
    (net (code "5378") (name "unconnected-(SV176-Pad36)") (class "Default")
      (node (ref "SV176") (pin "36") (pinfunction "36_36") (pintype "passive"))
    )
    (net (code "5379") (name "unconnected-(SV176-Pad37)") (class "Default")
      (node (ref "SV176") (pin "37") (pinfunction "37_37") (pintype "passive"))
    )
    (net (code "5380") (name "unconnected-(SV176-Pad38)") (class "Default")
      (node (ref "SV176") (pin "38") (pinfunction "38_38") (pintype "passive"))
    )
    (net (code "5381") (name "unconnected-(SV176-Pad39)") (class "Default")
      (node (ref "SV176") (pin "39") (pinfunction "39_39") (pintype "passive"))
    )
    (net (code "5382") (name "unconnected-(SV176-Pad40)") (class "Default")
      (node (ref "SV176") (pin "40") (pinfunction "40_40") (pintype "passive"))
    )
    (net (code "5383") (name "unconnected-(SV177-Pad1)") (class "Default")
      (node (ref "SV177") (pin "1") (pinfunction "1_1") (pintype "passive"))
    )
    (net (code "5384") (name "unconnected-(SV177-Pad2)") (class "Default")
      (node (ref "SV177") (pin "2") (pinfunction "2_2") (pintype "passive"))
    )
    (net (code "5385") (name "unconnected-(SV177-Pad3)") (class "Default")
      (node (ref "SV177") (pin "3") (pinfunction "3_3") (pintype "passive"))
    )
    (net (code "5386") (name "unconnected-(SV177-Pad4)") (class "Default")
      (node (ref "SV177") (pin "4") (pinfunction "4_4") (pintype "passive"))
    )
    (net (code "5387") (name "unconnected-(SV177-Pad5)") (class "Default")
      (node (ref "SV177") (pin "5") (pinfunction "5_5") (pintype "passive"))
    )
    (net (code "5388") (name "unconnected-(SV177-Pad6)") (class "Default")
      (node (ref "SV177") (pin "6") (pinfunction "6_6") (pintype "passive"))
    )
    (net (code "5389") (name "unconnected-(SV177-Pad7)") (class "Default")
      (node (ref "SV177") (pin "7") (pinfunction "7_7") (pintype "passive"))
    )
    (net (code "5390") (name "unconnected-(SV177-Pad8)") (class "Default")
      (node (ref "SV177") (pin "8") (pinfunction "8_8") (pintype "passive"))
    )
    (net (code "5391") (name "unconnected-(SV177-Pad9)") (class "Default")
      (node (ref "SV177") (pin "9") (pinfunction "9_9") (pintype "passive"))
    )
    (net (code "5392") (name "unconnected-(SV177-Pad10)") (class "Default")
      (node (ref "SV177") (pin "10") (pinfunction "10_10") (pintype "passive"))
    )
    (net (code "5393") (name "unconnected-(SV177-Pad11)") (class "Default")
      (node (ref "SV177") (pin "11") (pinfunction "11_11") (pintype "passive"))
    )
    (net (code "5394") (name "unconnected-(SV177-Pad12)") (class "Default")
      (node (ref "SV177") (pin "12") (pinfunction "12_12") (pintype "passive"))
    )
    (net (code "5395") (name "unconnected-(SV177-Pad13)") (class "Default")
      (node (ref "SV177") (pin "13") (pinfunction "13_13") (pintype "passive"))
    )
    (net (code "5396") (name "unconnected-(SV177-Pad14)") (class "Default")
      (node (ref "SV177") (pin "14") (pinfunction "14_14") (pintype "passive"))
    )
    (net (code "5397") (name "unconnected-(SV177-Pad15)") (class "Default")
      (node (ref "SV177") (pin "15") (pinfunction "15_15") (pintype "passive"))
    )
    (net (code "5398") (name "unconnected-(SV177-Pad16)") (class "Default")
      (node (ref "SV177") (pin "16") (pinfunction "16_16") (pintype "passive"))
    )
    (net (code "5399") (name "unconnected-(SV177-Pad17)") (class "Default")
      (node (ref "SV177") (pin "17") (pinfunction "17_17") (pintype "passive"))
    )
    (net (code "5400") (name "unconnected-(SV177-Pad18)") (class "Default")
      (node (ref "SV177") (pin "18") (pinfunction "18_18") (pintype "passive"))
    )
    (net (code "5401") (name "unconnected-(SV177-Pad19)") (class "Default")
      (node (ref "SV177") (pin "19") (pinfunction "19_19") (pintype "passive"))
    )
    (net (code "5402") (name "unconnected-(SV177-Pad20)") (class "Default")
      (node (ref "SV177") (pin "20") (pinfunction "20_20") (pintype "passive"))
    )
    (net (code "5403") (name "unconnected-(SV177-Pad21)") (class "Default")
      (node (ref "SV177") (pin "21") (pinfunction "21_21") (pintype "passive"))
    )
    (net (code "5404") (name "unconnected-(SV177-Pad22)") (class "Default")
      (node (ref "SV177") (pin "22") (pinfunction "22_22") (pintype "passive"))
    )
    (net (code "5405") (name "unconnected-(SV177-Pad23)") (class "Default")
      (node (ref "SV177") (pin "23") (pinfunction "23_23") (pintype "passive"))
    )
    (net (code "5406") (name "unconnected-(SV177-Pad24)") (class "Default")
      (node (ref "SV177") (pin "24") (pinfunction "24_24") (pintype "passive"))
    )
    (net (code "5407") (name "unconnected-(SV177-Pad25)") (class "Default")
      (node (ref "SV177") (pin "25") (pinfunction "25_25") (pintype "passive"))
    )
    (net (code "5408") (name "unconnected-(SV177-Pad26)") (class "Default")
      (node (ref "SV177") (pin "26") (pinfunction "26_26") (pintype "passive"))
    )
    (net (code "5409") (name "unconnected-(SV177-Pad27)") (class "Default")
      (node (ref "SV177") (pin "27") (pinfunction "27_27") (pintype "passive"))
    )
    (net (code "5410") (name "unconnected-(SV177-Pad28)") (class "Default")
      (node (ref "SV177") (pin "28") (pinfunction "28_28") (pintype "passive"))
    )
    (net (code "5411") (name "unconnected-(SV177-Pad29)") (class "Default")
      (node (ref "SV177") (pin "29") (pinfunction "29_29") (pintype "passive"))
    )
    (net (code "5412") (name "unconnected-(SV177-Pad30)") (class "Default")
      (node (ref "SV177") (pin "30") (pinfunction "30_30") (pintype "passive"))
    )
    (net (code "5413") (name "unconnected-(SV177-Pad31)") (class "Default")
      (node (ref "SV177") (pin "31") (pinfunction "31_31") (pintype "passive"))
    )
    (net (code "5414") (name "unconnected-(SV177-Pad32)") (class "Default")
      (node (ref "SV177") (pin "32") (pinfunction "32_32") (pintype "passive"))
    )
    (net (code "5415") (name "unconnected-(SV177-Pad33)") (class "Default")
      (node (ref "SV177") (pin "33") (pinfunction "33_33") (pintype "passive"))
    )
    (net (code "5416") (name "unconnected-(SV177-Pad34)") (class "Default")
      (node (ref "SV177") (pin "34") (pinfunction "34_34") (pintype "passive"))
    )
    (net (code "5417") (name "unconnected-(SV177-Pad35)") (class "Default")
      (node (ref "SV177") (pin "35") (pinfunction "35_35") (pintype "passive"))
    )
    (net (code "5418") (name "unconnected-(SV177-Pad36)") (class "Default")
      (node (ref "SV177") (pin "36") (pinfunction "36_36") (pintype "passive"))
    )
    (net (code "5419") (name "unconnected-(SV177-Pad37)") (class "Default")
      (node (ref "SV177") (pin "37") (pinfunction "37_37") (pintype "passive"))
    )
    (net (code "5420") (name "unconnected-(SV177-Pad38)") (class "Default")
      (node (ref "SV177") (pin "38") (pinfunction "38_38") (pintype "passive"))
    )
    (net (code "5421") (name "unconnected-(SV177-Pad39)") (class "Default")
      (node (ref "SV177") (pin "39") (pinfunction "39_39") (pintype "passive"))
    )
    (net (code "5422") (name "unconnected-(SV177-Pad40)") (class "Default")
      (node (ref "SV177") (pin "40") (pinfunction "40_40") (pintype "passive"))
    )
    (net (code "5423") (name "unconnected-(SV178-Pad1)") (class "Default")
      (node (ref "SV178") (pin "1") (pinfunction "1_1") (pintype "passive"))
    )
    (net (code "5424") (name "unconnected-(SV178-Pad2)") (class "Default")
      (node (ref "SV178") (pin "2") (pinfunction "2_2") (pintype "passive"))
    )
    (net (code "5425") (name "unconnected-(SV178-Pad3)") (class "Default")
      (node (ref "SV178") (pin "3") (pinfunction "3_3") (pintype "passive"))
    )
    (net (code "5426") (name "unconnected-(SV178-Pad4)") (class "Default")
      (node (ref "SV178") (pin "4") (pinfunction "4_4") (pintype "passive"))
    )
    (net (code "5427") (name "unconnected-(SV178-Pad5)") (class "Default")
      (node (ref "SV178") (pin "5") (pinfunction "5_5") (pintype "passive"))
    )
    (net (code "5428") (name "unconnected-(SV178-Pad6)") (class "Default")
      (node (ref "SV178") (pin "6") (pinfunction "6_6") (pintype "passive"))
    )
    (net (code "5429") (name "unconnected-(SV178-Pad7)") (class "Default")
      (node (ref "SV178") (pin "7") (pinfunction "7_7") (pintype "passive"))
    )
    (net (code "5430") (name "unconnected-(SV178-Pad8)") (class "Default")
      (node (ref "SV178") (pin "8") (pinfunction "8_8") (pintype "passive"))
    )
    (net (code "5431") (name "unconnected-(SV178-Pad9)") (class "Default")
      (node (ref "SV178") (pin "9") (pinfunction "9_9") (pintype "passive"))
    )
    (net (code "5432") (name "unconnected-(SV178-Pad10)") (class "Default")
      (node (ref "SV178") (pin "10") (pinfunction "10_10") (pintype "passive"))
    )
    (net (code "5433") (name "unconnected-(SV178-Pad11)") (class "Default")
      (node (ref "SV178") (pin "11") (pinfunction "11_11") (pintype "passive"))
    )
    (net (code "5434") (name "unconnected-(SV178-Pad12)") (class "Default")
      (node (ref "SV178") (pin "12") (pinfunction "12_12") (pintype "passive"))
    )
    (net (code "5435") (name "unconnected-(SV178-Pad13)") (class "Default")
      (node (ref "SV178") (pin "13") (pinfunction "13_13") (pintype "passive"))
    )
    (net (code "5436") (name "unconnected-(SV178-Pad14)") (class "Default")
      (node (ref "SV178") (pin "14") (pinfunction "14_14") (pintype "passive"))
    )
    (net (code "5437") (name "unconnected-(SV178-Pad15)") (class "Default")
      (node (ref "SV178") (pin "15") (pinfunction "15_15") (pintype "passive"))
    )
    (net (code "5438") (name "unconnected-(SV178-Pad16)") (class "Default")
      (node (ref "SV178") (pin "16") (pinfunction "16_16") (pintype "passive"))
    )
    (net (code "5439") (name "unconnected-(SV178-Pad17)") (class "Default")
      (node (ref "SV178") (pin "17") (pinfunction "17_17") (pintype "passive"))
    )
    (net (code "5440") (name "unconnected-(SV178-Pad18)") (class "Default")
      (node (ref "SV178") (pin "18") (pinfunction "18_18") (pintype "passive"))
    )
    (net (code "5441") (name "unconnected-(SV178-Pad19)") (class "Default")
      (node (ref "SV178") (pin "19") (pinfunction "19_19") (pintype "passive"))
    )
    (net (code "5442") (name "unconnected-(SV178-Pad20)") (class "Default")
      (node (ref "SV178") (pin "20") (pinfunction "20_20") (pintype "passive"))
    )
    (net (code "5443") (name "unconnected-(SV178-Pad21)") (class "Default")
      (node (ref "SV178") (pin "21") (pinfunction "21_21") (pintype "passive"))
    )
    (net (code "5444") (name "unconnected-(SV178-Pad22)") (class "Default")
      (node (ref "SV178") (pin "22") (pinfunction "22_22") (pintype "passive"))
    )
    (net (code "5445") (name "unconnected-(SV178-Pad23)") (class "Default")
      (node (ref "SV178") (pin "23") (pinfunction "23_23") (pintype "passive"))
    )
    (net (code "5446") (name "unconnected-(SV178-Pad24)") (class "Default")
      (node (ref "SV178") (pin "24") (pinfunction "24_24") (pintype "passive"))
    )
    (net (code "5447") (name "unconnected-(SV178-Pad25)") (class "Default")
      (node (ref "SV178") (pin "25") (pinfunction "25_25") (pintype "passive"))
    )
    (net (code "5448") (name "unconnected-(SV178-Pad26)") (class "Default")
      (node (ref "SV178") (pin "26") (pinfunction "26_26") (pintype "passive"))
    )
    (net (code "5449") (name "unconnected-(SV178-Pad27)") (class "Default")
      (node (ref "SV178") (pin "27") (pinfunction "27_27") (pintype "passive"))
    )
    (net (code "5450") (name "unconnected-(SV178-Pad28)") (class "Default")
      (node (ref "SV178") (pin "28") (pinfunction "28_28") (pintype "passive"))
    )
    (net (code "5451") (name "unconnected-(SV178-Pad29)") (class "Default")
      (node (ref "SV178") (pin "29") (pinfunction "29_29") (pintype "passive"))
    )
    (net (code "5452") (name "unconnected-(SV178-Pad30)") (class "Default")
      (node (ref "SV178") (pin "30") (pinfunction "30_30") (pintype "passive"))
    )
    (net (code "5453") (name "unconnected-(SV178-Pad31)") (class "Default")
      (node (ref "SV178") (pin "31") (pinfunction "31_31") (pintype "passive"))
    )
    (net (code "5454") (name "unconnected-(SV178-Pad32)") (class "Default")
      (node (ref "SV178") (pin "32") (pinfunction "32_32") (pintype "passive"))
    )
    (net (code "5455") (name "unconnected-(SV178-Pad33)") (class "Default")
      (node (ref "SV178") (pin "33") (pinfunction "33_33") (pintype "passive"))
    )
    (net (code "5456") (name "unconnected-(SV178-Pad34)") (class "Default")
      (node (ref "SV178") (pin "34") (pinfunction "34_34") (pintype "passive"))
    )
    (net (code "5457") (name "unconnected-(SV178-Pad35)") (class "Default")
      (node (ref "SV178") (pin "35") (pinfunction "35_35") (pintype "passive"))
    )
    (net (code "5458") (name "unconnected-(SV178-Pad36)") (class "Default")
      (node (ref "SV178") (pin "36") (pinfunction "36_36") (pintype "passive"))
    )
    (net (code "5459") (name "unconnected-(SV178-Pad37)") (class "Default")
      (node (ref "SV178") (pin "37") (pinfunction "37_37") (pintype "passive"))
    )
    (net (code "5460") (name "unconnected-(SV178-Pad38)") (class "Default")
      (node (ref "SV178") (pin "38") (pinfunction "38_38") (pintype "passive"))
    )
    (net (code "5461") (name "unconnected-(SV178-Pad39)") (class "Default")
      (node (ref "SV178") (pin "39") (pinfunction "39_39") (pintype "passive"))
    )
    (net (code "5462") (name "unconnected-(SV178-Pad40)") (class "Default")
      (node (ref "SV178") (pin "40") (pinfunction "40_40") (pintype "passive"))
    )
    (net (code "5463") (name "unconnected-(SV179-Pad1)") (class "Default")
      (node (ref "SV179") (pin "1") (pinfunction "1_1") (pintype "passive"))
    )
    (net (code "5464") (name "unconnected-(SV179-Pad2)") (class "Default")
      (node (ref "SV179") (pin "2") (pinfunction "2_2") (pintype "passive"))
    )
    (net (code "5465") (name "unconnected-(SV179-Pad3)") (class "Default")
      (node (ref "SV179") (pin "3") (pinfunction "3_3") (pintype "passive"))
    )
    (net (code "5466") (name "unconnected-(SV179-Pad4)") (class "Default")
      (node (ref "SV179") (pin "4") (pinfunction "4_4") (pintype "passive"))
    )
    (net (code "5467") (name "unconnected-(SV179-Pad5)") (class "Default")
      (node (ref "SV179") (pin "5") (pinfunction "5_5") (pintype "passive"))
    )
    (net (code "5468") (name "unconnected-(SV179-Pad6)") (class "Default")
      (node (ref "SV179") (pin "6") (pinfunction "6_6") (pintype "passive"))
    )
    (net (code "5469") (name "unconnected-(SV179-Pad7)") (class "Default")
      (node (ref "SV179") (pin "7") (pinfunction "7_7") (pintype "passive"))
    )
    (net (code "5470") (name "unconnected-(SV179-Pad8)") (class "Default")
      (node (ref "SV179") (pin "8") (pinfunction "8_8") (pintype "passive"))
    )
    (net (code "5471") (name "unconnected-(SV179-Pad9)") (class "Default")
      (node (ref "SV179") (pin "9") (pinfunction "9_9") (pintype "passive"))
    )
    (net (code "5472") (name "unconnected-(SV179-Pad10)") (class "Default")
      (node (ref "SV179") (pin "10") (pinfunction "10_10") (pintype "passive"))
    )
    (net (code "5473") (name "unconnected-(SV179-Pad11)") (class "Default")
      (node (ref "SV179") (pin "11") (pinfunction "11_11") (pintype "passive"))
    )
    (net (code "5474") (name "unconnected-(SV179-Pad12)") (class "Default")
      (node (ref "SV179") (pin "12") (pinfunction "12_12") (pintype "passive"))
    )
    (net (code "5475") (name "unconnected-(SV179-Pad13)") (class "Default")
      (node (ref "SV179") (pin "13") (pinfunction "13_13") (pintype "passive"))
    )
    (net (code "5476") (name "unconnected-(SV179-Pad14)") (class "Default")
      (node (ref "SV179") (pin "14") (pinfunction "14_14") (pintype "passive"))
    )
    (net (code "5477") (name "unconnected-(SV179-Pad15)") (class "Default")
      (node (ref "SV179") (pin "15") (pinfunction "15_15") (pintype "passive"))
    )
    (net (code "5478") (name "unconnected-(SV179-Pad16)") (class "Default")
      (node (ref "SV179") (pin "16") (pinfunction "16_16") (pintype "passive"))
    )
    (net (code "5479") (name "unconnected-(SV179-Pad17)") (class "Default")
      (node (ref "SV179") (pin "17") (pinfunction "17_17") (pintype "passive"))
    )
    (net (code "5480") (name "unconnected-(SV179-Pad18)") (class "Default")
      (node (ref "SV179") (pin "18") (pinfunction "18_18") (pintype "passive"))
    )
    (net (code "5481") (name "unconnected-(SV179-Pad19)") (class "Default")
      (node (ref "SV179") (pin "19") (pinfunction "19_19") (pintype "passive"))
    )
    (net (code "5482") (name "unconnected-(SV179-Pad20)") (class "Default")
      (node (ref "SV179") (pin "20") (pinfunction "20_20") (pintype "passive"))
    )
    (net (code "5483") (name "unconnected-(SV179-Pad21)") (class "Default")
      (node (ref "SV179") (pin "21") (pinfunction "21_21") (pintype "passive"))
    )
    (net (code "5484") (name "unconnected-(SV179-Pad22)") (class "Default")
      (node (ref "SV179") (pin "22") (pinfunction "22_22") (pintype "passive"))
    )
    (net (code "5485") (name "unconnected-(SV179-Pad23)") (class "Default")
      (node (ref "SV179") (pin "23") (pinfunction "23_23") (pintype "passive"))
    )
    (net (code "5486") (name "unconnected-(SV179-Pad24)") (class "Default")
      (node (ref "SV179") (pin "24") (pinfunction "24_24") (pintype "passive"))
    )
    (net (code "5487") (name "unconnected-(SV180-Pad1)") (class "Default")
      (node (ref "SV180") (pin "1") (pinfunction "1_1") (pintype "passive"))
    )
    (net (code "5488") (name "unconnected-(SV180-Pad2)") (class "Default")
      (node (ref "SV180") (pin "2") (pinfunction "2_2") (pintype "passive"))
    )
    (net (code "5489") (name "unconnected-(SV180-Pad3)") (class "Default")
      (node (ref "SV180") (pin "3") (pinfunction "3_3") (pintype "passive"))
    )
    (net (code "5490") (name "unconnected-(SV180-Pad4)") (class "Default")
      (node (ref "SV180") (pin "4") (pinfunction "4_4") (pintype "passive"))
    )
    (net (code "5491") (name "unconnected-(SV180-Pad5)") (class "Default")
      (node (ref "SV180") (pin "5") (pinfunction "5_5") (pintype "passive"))
    )
    (net (code "5492") (name "unconnected-(SV180-Pad6)") (class "Default")
      (node (ref "SV180") (pin "6") (pinfunction "6_6") (pintype "passive"))
    )
    (net (code "5493") (name "unconnected-(SV180-Pad7)") (class "Default")
      (node (ref "SV180") (pin "7") (pinfunction "7_7") (pintype "passive"))
    )
    (net (code "5494") (name "unconnected-(SV180-Pad8)") (class "Default")
      (node (ref "SV180") (pin "8") (pinfunction "8_8") (pintype "passive"))
    )
    (net (code "5495") (name "unconnected-(SV180-Pad9)") (class "Default")
      (node (ref "SV180") (pin "9") (pinfunction "9_9") (pintype "passive"))
    )
    (net (code "5496") (name "unconnected-(SV180-Pad10)") (class "Default")
      (node (ref "SV180") (pin "10") (pinfunction "10_10") (pintype "passive"))
    )
    (net (code "5497") (name "unconnected-(SV180-Pad11)") (class "Default")
      (node (ref "SV180") (pin "11") (pinfunction "11_11") (pintype "passive"))
    )
    (net (code "5498") (name "unconnected-(SV180-Pad12)") (class "Default")
      (node (ref "SV180") (pin "12") (pinfunction "12_12") (pintype "passive"))
    )
    (net (code "5499") (name "unconnected-(SV180-Pad13)") (class "Default")
      (node (ref "SV180") (pin "13") (pinfunction "13_13") (pintype "passive"))
    )
    (net (code "5500") (name "unconnected-(SV180-Pad14)") (class "Default")
      (node (ref "SV180") (pin "14") (pinfunction "14_14") (pintype "passive"))
    )
    (net (code "5501") (name "unconnected-(SV180-Pad15)") (class "Default")
      (node (ref "SV180") (pin "15") (pinfunction "15_15") (pintype "passive"))
    )
    (net (code "5502") (name "unconnected-(SV180-Pad16)") (class "Default")
      (node (ref "SV180") (pin "16") (pinfunction "16_16") (pintype "passive"))
    )
    (net (code "5503") (name "unconnected-(SV180-Pad17)") (class "Default")
      (node (ref "SV180") (pin "17") (pinfunction "17_17") (pintype "passive"))
    )
    (net (code "5504") (name "unconnected-(SV180-Pad18)") (class "Default")
      (node (ref "SV180") (pin "18") (pinfunction "18_18") (pintype "passive"))
    )
    (net (code "5505") (name "unconnected-(SV180-Pad19)") (class "Default")
      (node (ref "SV180") (pin "19") (pinfunction "19_19") (pintype "passive"))
    )
    (net (code "5506") (name "unconnected-(SV180-Pad20)") (class "Default")
      (node (ref "SV180") (pin "20") (pinfunction "20_20") (pintype "passive"))
    )
    (net (code "5507") (name "unconnected-(SV180-Pad21)") (class "Default")
      (node (ref "SV180") (pin "21") (pinfunction "21_21") (pintype "passive"))
    )
    (net (code "5508") (name "unconnected-(SV180-Pad22)") (class "Default")
      (node (ref "SV180") (pin "22") (pinfunction "22_22") (pintype "passive"))
    )
    (net (code "5509") (name "unconnected-(SV180-Pad23)") (class "Default")
      (node (ref "SV180") (pin "23") (pinfunction "23_23") (pintype "passive"))
    )
    (net (code "5510") (name "unconnected-(SV180-Pad24)") (class "Default")
      (node (ref "SV180") (pin "24") (pinfunction "24_24") (pintype "passive"))
    )
    (net (code "5511") (name "unconnected-(SV181-Pad1)") (class "Default")
      (node (ref "SV181") (pin "1") (pinfunction "1_1") (pintype "passive"))
    )
    (net (code "5512") (name "unconnected-(SV181-Pad2)") (class "Default")
      (node (ref "SV181") (pin "2") (pinfunction "2_2") (pintype "passive"))
    )
    (net (code "5513") (name "unconnected-(SV181-Pad3)") (class "Default")
      (node (ref "SV181") (pin "3") (pinfunction "3_3") (pintype "passive"))
    )
    (net (code "5514") (name "unconnected-(SV181-Pad4)") (class "Default")
      (node (ref "SV181") (pin "4") (pinfunction "4_4") (pintype "passive"))
    )
    (net (code "5515") (name "unconnected-(SV181-Pad5)") (class "Default")
      (node (ref "SV181") (pin "5") (pinfunction "5_5") (pintype "passive"))
    )
    (net (code "5516") (name "unconnected-(SV181-Pad6)") (class "Default")
      (node (ref "SV181") (pin "6") (pinfunction "6_6") (pintype "passive"))
    )
    (net (code "5517") (name "unconnected-(SV181-Pad7)") (class "Default")
      (node (ref "SV181") (pin "7") (pinfunction "7_7") (pintype "passive"))
    )
    (net (code "5518") (name "unconnected-(SV181-Pad8)") (class "Default")
      (node (ref "SV181") (pin "8") (pinfunction "8_8") (pintype "passive"))
    )
    (net (code "5519") (name "unconnected-(SV181-Pad9)") (class "Default")
      (node (ref "SV181") (pin "9") (pinfunction "9_9") (pintype "passive"))
    )
    (net (code "5520") (name "unconnected-(SV181-Pad10)") (class "Default")
      (node (ref "SV181") (pin "10") (pinfunction "10_10") (pintype "passive"))
    )
    (net (code "5521") (name "unconnected-(SV181-Pad11)") (class "Default")
      (node (ref "SV181") (pin "11") (pinfunction "11_11") (pintype "passive"))
    )
    (net (code "5522") (name "unconnected-(SV181-Pad12)") (class "Default")
      (node (ref "SV181") (pin "12") (pinfunction "12_12") (pintype "passive"))
    )
    (net (code "5523") (name "unconnected-(SV181-Pad13)") (class "Default")
      (node (ref "SV181") (pin "13") (pinfunction "13_13") (pintype "passive"))
    )
    (net (code "5524") (name "unconnected-(SV181-Pad14)") (class "Default")
      (node (ref "SV181") (pin "14") (pinfunction "14_14") (pintype "passive"))
    )
    (net (code "5525") (name "unconnected-(SV181-Pad15)") (class "Default")
      (node (ref "SV181") (pin "15") (pinfunction "15_15") (pintype "passive"))
    )
    (net (code "5526") (name "unconnected-(SV181-Pad16)") (class "Default")
      (node (ref "SV181") (pin "16") (pinfunction "16_16") (pintype "passive"))
    )
    (net (code "5527") (name "unconnected-(SV181-Pad17)") (class "Default")
      (node (ref "SV181") (pin "17") (pinfunction "17_17") (pintype "passive"))
    )
    (net (code "5528") (name "unconnected-(SV181-Pad18)") (class "Default")
      (node (ref "SV181") (pin "18") (pinfunction "18_18") (pintype "passive"))
    )
    (net (code "5529") (name "unconnected-(SV181-Pad19)") (class "Default")
      (node (ref "SV181") (pin "19") (pinfunction "19_19") (pintype "passive"))
    )
    (net (code "5530") (name "unconnected-(SV181-Pad20)") (class "Default")
      (node (ref "SV181") (pin "20") (pinfunction "20_20") (pintype "passive"))
    )
    (net (code "5531") (name "unconnected-(SV181-Pad21)") (class "Default")
      (node (ref "SV181") (pin "21") (pinfunction "21_21") (pintype "passive"))
    )
    (net (code "5532") (name "unconnected-(SV181-Pad22)") (class "Default")
      (node (ref "SV181") (pin "22") (pinfunction "22_22") (pintype "passive"))
    )
    (net (code "5533") (name "unconnected-(SV181-Pad23)") (class "Default")
      (node (ref "SV181") (pin "23") (pinfunction "23_23") (pintype "passive"))
    )
    (net (code "5534") (name "unconnected-(SV181-Pad24)") (class "Default")
      (node (ref "SV181") (pin "24") (pinfunction "24_24") (pintype "passive"))
    )
    (net (code "5535") (name "unconnected-(SV182-Pad1)") (class "Default")
      (node (ref "SV182") (pin "1") (pinfunction "1_1") (pintype "passive"))
    )
    (net (code "5536") (name "unconnected-(SV182-Pad2)") (class "Default")
      (node (ref "SV182") (pin "2") (pinfunction "2_2") (pintype "passive"))
    )
    (net (code "5537") (name "unconnected-(SV182-Pad3)") (class "Default")
      (node (ref "SV182") (pin "3") (pinfunction "3_3") (pintype "passive"))
    )
    (net (code "5538") (name "unconnected-(SV182-Pad4)") (class "Default")
      (node (ref "SV182") (pin "4") (pinfunction "4_4") (pintype "passive"))
    )
    (net (code "5539") (name "unconnected-(SV182-Pad5)") (class "Default")
      (node (ref "SV182") (pin "5") (pinfunction "5_5") (pintype "passive"))
    )
    (net (code "5540") (name "unconnected-(SV182-Pad6)") (class "Default")
      (node (ref "SV182") (pin "6") (pinfunction "6_6") (pintype "passive"))
    )
    (net (code "5541") (name "unconnected-(SV182-Pad7)") (class "Default")
      (node (ref "SV182") (pin "7") (pinfunction "7_7") (pintype "passive"))
    )
    (net (code "5542") (name "unconnected-(SV182-Pad8)") (class "Default")
      (node (ref "SV182") (pin "8") (pinfunction "8_8") (pintype "passive"))
    )
    (net (code "5543") (name "unconnected-(SV182-Pad9)") (class "Default")
      (node (ref "SV182") (pin "9") (pinfunction "9_9") (pintype "passive"))
    )
    (net (code "5544") (name "unconnected-(SV182-Pad10)") (class "Default")
      (node (ref "SV182") (pin "10") (pinfunction "10_10") (pintype "passive"))
    )
    (net (code "5545") (name "unconnected-(SV182-Pad11)") (class "Default")
      (node (ref "SV182") (pin "11") (pinfunction "11_11") (pintype "passive"))
    )
    (net (code "5546") (name "unconnected-(SV182-Pad12)") (class "Default")
      (node (ref "SV182") (pin "12") (pinfunction "12_12") (pintype "passive"))
    )
    (net (code "5547") (name "unconnected-(SV182-Pad13)") (class "Default")
      (node (ref "SV182") (pin "13") (pinfunction "13_13") (pintype "passive"))
    )
    (net (code "5548") (name "unconnected-(SV182-Pad14)") (class "Default")
      (node (ref "SV182") (pin "14") (pinfunction "14_14") (pintype "passive"))
    )
    (net (code "5549") (name "unconnected-(SV182-Pad15)") (class "Default")
      (node (ref "SV182") (pin "15") (pinfunction "15_15") (pintype "passive"))
    )
    (net (code "5550") (name "unconnected-(SV182-Pad16)") (class "Default")
      (node (ref "SV182") (pin "16") (pinfunction "16_16") (pintype "passive"))
    )
    (net (code "5551") (name "unconnected-(SV182-Pad17)") (class "Default")
      (node (ref "SV182") (pin "17") (pinfunction "17_17") (pintype "passive"))
    )
    (net (code "5552") (name "unconnected-(SV182-Pad18)") (class "Default")
      (node (ref "SV182") (pin "18") (pinfunction "18_18") (pintype "passive"))
    )
    (net (code "5553") (name "unconnected-(SV182-Pad19)") (class "Default")
      (node (ref "SV182") (pin "19") (pinfunction "19_19") (pintype "passive"))
    )
    (net (code "5554") (name "unconnected-(SV182-Pad20)") (class "Default")
      (node (ref "SV182") (pin "20") (pinfunction "20_20") (pintype "passive"))
    )
    (net (code "5555") (name "unconnected-(SV182-Pad21)") (class "Default")
      (node (ref "SV182") (pin "21") (pinfunction "21_21") (pintype "passive"))
    )
    (net (code "5556") (name "unconnected-(SV182-Pad22)") (class "Default")
      (node (ref "SV182") (pin "22") (pinfunction "22_22") (pintype "passive"))
    )
    (net (code "5557") (name "unconnected-(SV182-Pad23)") (class "Default")
      (node (ref "SV182") (pin "23") (pinfunction "23_23") (pintype "passive"))
    )
    (net (code "5558") (name "unconnected-(SV182-Pad24)") (class "Default")
      (node (ref "SV182") (pin "24") (pinfunction "24_24") (pintype "passive"))
    )
    (net (code "5559") (name "unconnected-(SV183-Pad1)") (class "Default")
      (node (ref "SV183") (pin "1") (pinfunction "1_1") (pintype "passive"))
    )
    (net (code "5560") (name "unconnected-(SV183-Pad2)") (class "Default")
      (node (ref "SV183") (pin "2") (pinfunction "2_2") (pintype "passive"))
    )
    (net (code "5561") (name "unconnected-(SV183-Pad3)") (class "Default")
      (node (ref "SV183") (pin "3") (pinfunction "3_3") (pintype "passive"))
    )
    (net (code "5562") (name "unconnected-(SV183-Pad4)") (class "Default")
      (node (ref "SV183") (pin "4") (pinfunction "4_4") (pintype "passive"))
    )
    (net (code "5563") (name "unconnected-(SV183-Pad5)") (class "Default")
      (node (ref "SV183") (pin "5") (pinfunction "5_5") (pintype "passive"))
    )
    (net (code "5564") (name "unconnected-(SV183-Pad6)") (class "Default")
      (node (ref "SV183") (pin "6") (pinfunction "6_6") (pintype "passive"))
    )
    (net (code "5565") (name "unconnected-(SV184-Pad1)") (class "Default")
      (node (ref "SV184") (pin "1") (pinfunction "1_1") (pintype "passive"))
    )
    (net (code "5566") (name "unconnected-(SV184-Pad2)") (class "Default")
      (node (ref "SV184") (pin "2") (pinfunction "2_2") (pintype "passive"))
    )
    (net (code "5567") (name "unconnected-(SV184-Pad3)") (class "Default")
      (node (ref "SV184") (pin "3") (pinfunction "3_3") (pintype "passive"))
    )
    (net (code "5568") (name "unconnected-(SV184-Pad4)") (class "Default")
      (node (ref "SV184") (pin "4") (pinfunction "4_4") (pintype "passive"))
    )
    (net (code "5569") (name "unconnected-(SV184-Pad5)") (class "Default")
      (node (ref "SV184") (pin "5") (pinfunction "5_5") (pintype "passive"))
    )
    (net (code "5570") (name "unconnected-(SV184-Pad6)") (class "Default")
      (node (ref "SV184") (pin "6") (pinfunction "6_6") (pintype "passive"))
    )
    (net (code "5571") (name "unconnected-(SV185-Pad1)") (class "Default")
      (node (ref "SV185") (pin "1") (pinfunction "1_1") (pintype "passive"))
    )
    (net (code "5572") (name "unconnected-(SV185-Pad2)") (class "Default")
      (node (ref "SV185") (pin "2") (pinfunction "2_2") (pintype "passive"))
    )
    (net (code "5573") (name "unconnected-(SV185-Pad3)") (class "Default")
      (node (ref "SV185") (pin "3") (pinfunction "3_3") (pintype "passive"))
    )
    (net (code "5574") (name "unconnected-(SV185-Pad4)") (class "Default")
      (node (ref "SV185") (pin "4") (pinfunction "4_4") (pintype "passive"))
    )
    (net (code "5575") (name "unconnected-(SV185-Pad5)") (class "Default")
      (node (ref "SV185") (pin "5") (pinfunction "5_5") (pintype "passive"))
    )
    (net (code "5576") (name "unconnected-(SV185-Pad6)") (class "Default")
      (node (ref "SV185") (pin "6") (pinfunction "6_6") (pintype "passive"))
    )
    (net (code "5577") (name "unconnected-(SV186-Pad1)") (class "Default")
      (node (ref "SV186") (pin "1") (pinfunction "1_1") (pintype "passive"))
    )
    (net (code "5578") (name "unconnected-(SV186-Pad2)") (class "Default")
      (node (ref "SV186") (pin "2") (pinfunction "2_2") (pintype "passive"))
    )
    (net (code "5579") (name "unconnected-(SV186-Pad3)") (class "Default")
      (node (ref "SV186") (pin "3") (pinfunction "3_3") (pintype "passive"))
    )
    (net (code "5580") (name "unconnected-(SV186-Pad4)") (class "Default")
      (node (ref "SV186") (pin "4") (pinfunction "4_4") (pintype "passive"))
    )
    (net (code "5581") (name "unconnected-(SV186-Pad5)") (class "Default")
      (node (ref "SV186") (pin "5") (pinfunction "5_5") (pintype "passive"))
    )
    (net (code "5582") (name "unconnected-(SV186-Pad6)") (class "Default")
      (node (ref "SV186") (pin "6") (pinfunction "6_6") (pintype "passive"))
    )
    (net (code "5583") (name "unconnected-(SV187-Pad1)") (class "Default")
      (node (ref "SV187") (pin "1") (pinfunction "1_1") (pintype "passive"))
    )
    (net (code "5584") (name "unconnected-(SV187-Pad2)") (class "Default")
      (node (ref "SV187") (pin "2") (pinfunction "2_2") (pintype "passive"))
    )
    (net (code "5585") (name "unconnected-(SV187-Pad3)") (class "Default")
      (node (ref "SV187") (pin "3") (pinfunction "3_3") (pintype "passive"))
    )
    (net (code "5586") (name "unconnected-(SV187-Pad4)") (class "Default")
      (node (ref "SV187") (pin "4") (pinfunction "4_4") (pintype "passive"))
    )
    (net (code "5587") (name "unconnected-(SV187-Pad5)") (class "Default")
      (node (ref "SV187") (pin "5") (pinfunction "5_5") (pintype "passive"))
    )
    (net (code "5588") (name "unconnected-(SV187-Pad6)") (class "Default")
      (node (ref "SV187") (pin "6") (pinfunction "6_6") (pintype "passive"))
    )
    (net (code "5589") (name "unconnected-(SV188-Pad1)") (class "Default")
      (node (ref "SV188") (pin "1") (pinfunction "1_1") (pintype "passive"))
    )
    (net (code "5590") (name "unconnected-(SV188-Pad2)") (class "Default")
      (node (ref "SV188") (pin "2") (pinfunction "2_2") (pintype "passive"))
    )
    (net (code "5591") (name "unconnected-(SV188-Pad3)") (class "Default")
      (node (ref "SV188") (pin "3") (pinfunction "3_3") (pintype "passive"))
    )
    (net (code "5592") (name "unconnected-(SV188-Pad4)") (class "Default")
      (node (ref "SV188") (pin "4") (pinfunction "4_4") (pintype "passive"))
    )
    (net (code "5593") (name "unconnected-(SV188-Pad5)") (class "Default")
      (node (ref "SV188") (pin "5") (pinfunction "5_5") (pintype "passive"))
    )
    (net (code "5594") (name "unconnected-(SV188-Pad6)") (class "Default")
      (node (ref "SV188") (pin "6") (pinfunction "6_6") (pintype "passive"))
    )
    (net (code "5595") (name "unconnected-(SV189-Pad1)") (class "Default")
      (node (ref "SV189") (pin "1") (pinfunction "1_1") (pintype "passive"))
    )
    (net (code "5596") (name "unconnected-(SV189-Pad2)") (class "Default")
      (node (ref "SV189") (pin "2") (pinfunction "2_2") (pintype "passive"))
    )
    (net (code "5597") (name "unconnected-(SV189-Pad3)") (class "Default")
      (node (ref "SV189") (pin "3") (pinfunction "3_3") (pintype "passive"))
    )
    (net (code "5598") (name "unconnected-(SV189-Pad4)") (class "Default")
      (node (ref "SV189") (pin "4") (pinfunction "4_4") (pintype "passive"))
    )
    (net (code "5599") (name "unconnected-(SV189-Pad5)") (class "Default")
      (node (ref "SV189") (pin "5") (pinfunction "5_5") (pintype "passive"))
    )
    (net (code "5600") (name "unconnected-(SV189-Pad6)") (class "Default")
      (node (ref "SV189") (pin "6") (pinfunction "6_6") (pintype "passive"))
    )
    (net (code "5601") (name "unconnected-(SV190-Pad1)") (class "Default")
      (node (ref "SV190") (pin "1") (pinfunction "1_1") (pintype "passive"))
    )
    (net (code "5602") (name "unconnected-(SV190-Pad2)") (class "Default")
      (node (ref "SV190") (pin "2") (pinfunction "2_2") (pintype "passive"))
    )
    (net (code "5603") (name "unconnected-(SV190-Pad3)") (class "Default")
      (node (ref "SV190") (pin "3") (pinfunction "3_3") (pintype "passive"))
    )
    (net (code "5604") (name "unconnected-(SV190-Pad4)") (class "Default")
      (node (ref "SV190") (pin "4") (pinfunction "4_4") (pintype "passive"))
    )
    (net (code "5605") (name "unconnected-(SV190-Pad5)") (class "Default")
      (node (ref "SV190") (pin "5") (pinfunction "5_5") (pintype "passive"))
    )
    (net (code "5606") (name "unconnected-(SV190-Pad6)") (class "Default")
      (node (ref "SV190") (pin "6") (pinfunction "6_6") (pintype "passive"))
    )
    (net (code "5607") (name "unconnected-(SV191-Pad1)") (class "Default")
      (node (ref "SV191") (pin "1") (pinfunction "1_1") (pintype "passive"))
    )
    (net (code "5608") (name "unconnected-(SV191-Pad2)") (class "Default")
      (node (ref "SV191") (pin "2") (pinfunction "2_2") (pintype "passive"))
    )
    (net (code "5609") (name "unconnected-(SV191-Pad3)") (class "Default")
      (node (ref "SV191") (pin "3") (pinfunction "3_3") (pintype "passive"))
    )
    (net (code "5610") (name "unconnected-(SV191-Pad4)") (class "Default")
      (node (ref "SV191") (pin "4") (pinfunction "4_4") (pintype "passive"))
    )
    (net (code "5611") (name "unconnected-(SV191-Pad5)") (class "Default")
      (node (ref "SV191") (pin "5") (pinfunction "5_5") (pintype "passive"))
    )
    (net (code "5612") (name "unconnected-(SV191-Pad6)") (class "Default")
      (node (ref "SV191") (pin "6") (pinfunction "6_6") (pintype "passive"))
    )
    (net (code "5613") (name "unconnected-(SV192-Pad1)") (class "Default")
      (node (ref "SV192") (pin "1") (pinfunction "1_1") (pintype "passive"))
    )
    (net (code "5614") (name "unconnected-(SV192-Pad2)") (class "Default")
      (node (ref "SV192") (pin "2") (pinfunction "2_2") (pintype "passive"))
    )
    (net (code "5615") (name "unconnected-(SV192-Pad3)") (class "Default")
      (node (ref "SV192") (pin "3") (pinfunction "3_3") (pintype "passive"))
    )
    (net (code "5616") (name "unconnected-(SV192-Pad4)") (class "Default")
      (node (ref "SV192") (pin "4") (pinfunction "4_4") (pintype "passive"))
    )
    (net (code "5617") (name "unconnected-(SV192-Pad5)") (class "Default")
      (node (ref "SV192") (pin "5") (pinfunction "5_5") (pintype "passive"))
    )
    (net (code "5618") (name "unconnected-(SV192-Pad6)") (class "Default")
      (node (ref "SV192") (pin "6") (pinfunction "6_6") (pintype "passive"))
    )
    (net (code "5619") (name "unconnected-(SV193-Pad1)") (class "Default")
      (node (ref "SV193") (pin "1") (pinfunction "1_1") (pintype "passive"))
    )
    (net (code "5620") (name "unconnected-(SV193-Pad2)") (class "Default")
      (node (ref "SV193") (pin "2") (pinfunction "2_2") (pintype "passive"))
    )
    (net (code "5621") (name "unconnected-(SV193-Pad3)") (class "Default")
      (node (ref "SV193") (pin "3") (pinfunction "3_3") (pintype "passive"))
    )
    (net (code "5622") (name "unconnected-(SV193-Pad4)") (class "Default")
      (node (ref "SV193") (pin "4") (pinfunction "4_4") (pintype "passive"))
    )
    (net (code "5623") (name "unconnected-(SV193-Pad5)") (class "Default")
      (node (ref "SV193") (pin "5") (pinfunction "5_5") (pintype "passive"))
    )
    (net (code "5624") (name "unconnected-(SV193-Pad6)") (class "Default")
      (node (ref "SV193") (pin "6") (pinfunction "6_6") (pintype "passive"))
    )
    (net (code "5625") (name "unconnected-(SV194-Pad1)") (class "Default")
      (node (ref "SV194") (pin "1") (pinfunction "1_1") (pintype "passive"))
    )
    (net (code "5626") (name "unconnected-(SV194-Pad2)") (class "Default")
      (node (ref "SV194") (pin "2") (pinfunction "2_2") (pintype "passive"))
    )
    (net (code "5627") (name "unconnected-(SV194-Pad3)") (class "Default")
      (node (ref "SV194") (pin "3") (pinfunction "3_3") (pintype "passive"))
    )
    (net (code "5628") (name "unconnected-(SV194-Pad4)") (class "Default")
      (node (ref "SV194") (pin "4") (pinfunction "4_4") (pintype "passive"))
    )
    (net (code "5629") (name "unconnected-(SV194-Pad5)") (class "Default")
      (node (ref "SV194") (pin "5") (pinfunction "5_5") (pintype "passive"))
    )
    (net (code "5630") (name "unconnected-(SV194-Pad6)") (class "Default")
      (node (ref "SV194") (pin "6") (pinfunction "6_6") (pintype "passive"))
    )
    (net (code "5631") (name "unconnected-(SV195-Pad1)") (class "Default")
      (node (ref "SV195") (pin "1") (pinfunction "1_1") (pintype "passive"))
    )
    (net (code "5632") (name "unconnected-(SV195-Pad2)") (class "Default")
      (node (ref "SV195") (pin "2") (pinfunction "2_2") (pintype "passive"))
    )
    (net (code "5633") (name "unconnected-(SV195-Pad3)") (class "Default")
      (node (ref "SV195") (pin "3") (pinfunction "3_3") (pintype "passive"))
    )
    (net (code "5634") (name "unconnected-(SV195-Pad4)") (class "Default")
      (node (ref "SV195") (pin "4") (pinfunction "4_4") (pintype "passive"))
    )
    (net (code "5635") (name "unconnected-(SV195-Pad5)") (class "Default")
      (node (ref "SV195") (pin "5") (pinfunction "5_5") (pintype "passive"))
    )
    (net (code "5636") (name "unconnected-(SV195-Pad6)") (class "Default")
      (node (ref "SV195") (pin "6") (pinfunction "6_6") (pintype "passive"))
    )
    (net (code "5637") (name "unconnected-(SV196-Pad1)") (class "Default")
      (node (ref "SV196") (pin "1") (pinfunction "1_1") (pintype "passive"))
    )
    (net (code "5638") (name "unconnected-(SV196-Pad2)") (class "Default")
      (node (ref "SV196") (pin "2") (pinfunction "2_2") (pintype "passive"))
    )
    (net (code "5639") (name "unconnected-(SV196-Pad3)") (class "Default")
      (node (ref "SV196") (pin "3") (pinfunction "3_3") (pintype "passive"))
    )
    (net (code "5640") (name "unconnected-(SV196-Pad4)") (class "Default")
      (node (ref "SV196") (pin "4") (pinfunction "4_4") (pintype "passive"))
    )
    (net (code "5641") (name "unconnected-(SV196-Pad5)") (class "Default")
      (node (ref "SV196") (pin "5") (pinfunction "5_5") (pintype "passive"))
    )
    (net (code "5642") (name "unconnected-(SV196-Pad6)") (class "Default")
      (node (ref "SV196") (pin "6") (pinfunction "6_6") (pintype "passive"))
    )
    (net (code "5643") (name "unconnected-(SV197-Pad1)") (class "Default")
      (node (ref "SV197") (pin "1") (pinfunction "1_1") (pintype "passive"))
    )
    (net (code "5644") (name "unconnected-(SV197-Pad2)") (class "Default")
      (node (ref "SV197") (pin "2") (pinfunction "2_2") (pintype "passive"))
    )
    (net (code "5645") (name "unconnected-(SV197-Pad3)") (class "Default")
      (node (ref "SV197") (pin "3") (pinfunction "3_3") (pintype "passive"))
    )
    (net (code "5646") (name "unconnected-(SV197-Pad4)") (class "Default")
      (node (ref "SV197") (pin "4") (pinfunction "4_4") (pintype "passive"))
    )
    (net (code "5647") (name "unconnected-(SV197-Pad5)") (class "Default")
      (node (ref "SV197") (pin "5") (pinfunction "5_5") (pintype "passive"))
    )
    (net (code "5648") (name "unconnected-(SV197-Pad6)") (class "Default")
      (node (ref "SV197") (pin "6") (pinfunction "6_6") (pintype "passive"))
    )
    (net (code "5649") (name "unconnected-(SV198-Pad1)") (class "Default")
      (node (ref "SV198") (pin "1") (pinfunction "1_1") (pintype "passive"))
    )
    (net (code "5650") (name "unconnected-(SV198-Pad2)") (class "Default")
      (node (ref "SV198") (pin "2") (pinfunction "2_2") (pintype "passive"))
    )
    (net (code "5651") (name "unconnected-(SV198-Pad3)") (class "Default")
      (node (ref "SV198") (pin "3") (pinfunction "3_3") (pintype "passive"))
    )
    (net (code "5652") (name "unconnected-(SV198-Pad4)") (class "Default")
      (node (ref "SV198") (pin "4") (pinfunction "4_4") (pintype "passive"))
    )
    (net (code "5653") (name "unconnected-(SV198-Pad5)") (class "Default")
      (node (ref "SV198") (pin "5") (pinfunction "5_5") (pintype "passive"))
    )
    (net (code "5654") (name "unconnected-(SV198-Pad6)") (class "Default")
      (node (ref "SV198") (pin "6") (pinfunction "6_6") (pintype "passive"))
    )
    (net (code "5655") (name "unconnected-(SV199-Pad1)") (class "Default")
      (node (ref "SV199") (pin "1") (pinfunction "1_1") (pintype "passive"))
    )
    (net (code "5656") (name "unconnected-(SV199-Pad2)") (class "Default")
      (node (ref "SV199") (pin "2") (pinfunction "2_2") (pintype "passive"))
    )
    (net (code "5657") (name "unconnected-(SV199-Pad3)") (class "Default")
      (node (ref "SV199") (pin "3") (pinfunction "3_3") (pintype "passive"))
    )
    (net (code "5658") (name "unconnected-(SV199-Pad4)") (class "Default")
      (node (ref "SV199") (pin "4") (pinfunction "4_4") (pintype "passive"))
    )
    (net (code "5659") (name "unconnected-(SV199-Pad5)") (class "Default")
      (node (ref "SV199") (pin "5") (pinfunction "5_5") (pintype "passive"))
    )
    (net (code "5660") (name "unconnected-(SV199-Pad6)") (class "Default")
      (node (ref "SV199") (pin "6") (pinfunction "6_6") (pintype "passive"))
    )
    (net (code "5661") (name "unconnected-(SV199-Pad7)") (class "Default")
      (node (ref "SV199") (pin "7") (pinfunction "7_7") (pintype "passive"))
    )
    (net (code "5662") (name "unconnected-(SV199-Pad8)") (class "Default")
      (node (ref "SV199") (pin "8") (pinfunction "8_8") (pintype "passive"))
    )
    (net (code "5663") (name "unconnected-(SV199-Pad9)") (class "Default")
      (node (ref "SV199") (pin "9") (pinfunction "9_9") (pintype "passive"))
    )
    (net (code "5664") (name "unconnected-(SV199-Pad10)") (class "Default")
      (node (ref "SV199") (pin "10") (pinfunction "10_10") (pintype "passive"))
    )
    (net (code "5665") (name "unconnected-(SV199-Pad11)") (class "Default")
      (node (ref "SV199") (pin "11") (pinfunction "11_11") (pintype "passive"))
    )
    (net (code "5666") (name "unconnected-(SV199-Pad12)") (class "Default")
      (node (ref "SV199") (pin "12") (pinfunction "12_12") (pintype "passive"))
    )
    (net (code "5667") (name "unconnected-(SV199-Pad13)") (class "Default")
      (node (ref "SV199") (pin "13") (pinfunction "13_13") (pintype "passive"))
    )
    (net (code "5668") (name "unconnected-(SV199-Pad14)") (class "Default")
      (node (ref "SV199") (pin "14") (pinfunction "14_14") (pintype "passive"))
    )
    (net (code "5669") (name "unconnected-(SV199-Pad15)") (class "Default")
      (node (ref "SV199") (pin "15") (pinfunction "15_15") (pintype "passive"))
    )
    (net (code "5670") (name "unconnected-(SV199-Pad16)") (class "Default")
      (node (ref "SV199") (pin "16") (pinfunction "16_16") (pintype "passive"))
    )
    (net (code "5671") (name "unconnected-(SV199-Pad17)") (class "Default")
      (node (ref "SV199") (pin "17") (pinfunction "17_17") (pintype "passive"))
    )
    (net (code "5672") (name "unconnected-(SV199-Pad18)") (class "Default")
      (node (ref "SV199") (pin "18") (pinfunction "18_18") (pintype "passive"))
    )
    (net (code "5673") (name "unconnected-(SV199-Pad19)") (class "Default")
      (node (ref "SV199") (pin "19") (pinfunction "19_19") (pintype "passive"))
    )
    (net (code "5674") (name "unconnected-(SV199-Pad20)") (class "Default")
      (node (ref "SV199") (pin "20") (pinfunction "20_20") (pintype "passive"))
    )
    (net (code "5675") (name "unconnected-(SV199-Pad21)") (class "Default")
      (node (ref "SV199") (pin "21") (pinfunction "21_21") (pintype "passive"))
    )
    (net (code "5676") (name "unconnected-(SV199-Pad22)") (class "Default")
      (node (ref "SV199") (pin "22") (pinfunction "22_22") (pintype "passive"))
    )
    (net (code "5677") (name "unconnected-(SV199-Pad23)") (class "Default")
      (node (ref "SV199") (pin "23") (pinfunction "23_23") (pintype "passive"))
    )
    (net (code "5678") (name "unconnected-(SV199-Pad24)") (class "Default")
      (node (ref "SV199") (pin "24") (pinfunction "24_24") (pintype "passive"))
    )
    (net (code "5679") (name "unconnected-(SV199-Pad25)") (class "Default")
      (node (ref "SV199") (pin "25") (pinfunction "25_25") (pintype "passive"))
    )
    (net (code "5680") (name "unconnected-(SV199-Pad26)") (class "Default")
      (node (ref "SV199") (pin "26") (pinfunction "26_26") (pintype "passive"))
    )
    (net (code "5681") (name "unconnected-(SV199-Pad27)") (class "Default")
      (node (ref "SV199") (pin "27") (pinfunction "27_27") (pintype "passive"))
    )
    (net (code "5682") (name "unconnected-(SV199-Pad28)") (class "Default")
      (node (ref "SV199") (pin "28") (pinfunction "28_28") (pintype "passive"))
    )
    (net (code "5683") (name "unconnected-(SV199-Pad29)") (class "Default")
      (node (ref "SV199") (pin "29") (pinfunction "29_29") (pintype "passive"))
    )
    (net (code "5684") (name "unconnected-(SV199-Pad30)") (class "Default")
      (node (ref "SV199") (pin "30") (pinfunction "30_30") (pintype "passive"))
    )
    (net (code "5685") (name "unconnected-(SV199-Pad31)") (class "Default")
      (node (ref "SV199") (pin "31") (pinfunction "31_31") (pintype "passive"))
    )
    (net (code "5686") (name "unconnected-(SV199-Pad32)") (class "Default")
      (node (ref "SV199") (pin "32") (pinfunction "32_32") (pintype "passive"))
    )
    (net (code "5687") (name "unconnected-(SV199-Pad33)") (class "Default")
      (node (ref "SV199") (pin "33") (pinfunction "33_33") (pintype "passive"))
    )
    (net (code "5688") (name "unconnected-(SV199-Pad34)") (class "Default")
      (node (ref "SV199") (pin "34") (pinfunction "34_34") (pintype "passive"))
    )
    (net (code "5689") (name "unconnected-(SV199-Pad35)") (class "Default")
      (node (ref "SV199") (pin "35") (pinfunction "35_35") (pintype "passive"))
    )
    (net (code "5690") (name "unconnected-(SV199-Pad36)") (class "Default")
      (node (ref "SV199") (pin "36") (pinfunction "36_36") (pintype "passive"))
    )
    (net (code "5691") (name "unconnected-(SV199-Pad37)") (class "Default")
      (node (ref "SV199") (pin "37") (pinfunction "37_37") (pintype "passive"))
    )
    (net (code "5692") (name "unconnected-(SV199-Pad38)") (class "Default")
      (node (ref "SV199") (pin "38") (pinfunction "38_38") (pintype "passive"))
    )
    (net (code "5693") (name "unconnected-(SV199-Pad39)") (class "Default")
      (node (ref "SV199") (pin "39") (pinfunction "39_39") (pintype "passive"))
    )
    (net (code "5694") (name "unconnected-(SV199-Pad40)") (class "Default")
      (node (ref "SV199") (pin "40") (pinfunction "40_40") (pintype "passive"))
    )
    (net (code "5695") (name "unconnected-(SV200-Pad1)") (class "Default")
      (node (ref "SV200") (pin "1") (pinfunction "1_1") (pintype "passive"))
    )
    (net (code "5696") (name "unconnected-(SV200-Pad2)") (class "Default")
      (node (ref "SV200") (pin "2") (pinfunction "2_2") (pintype "passive"))
    )
    (net (code "5697") (name "unconnected-(SV200-Pad3)") (class "Default")
      (node (ref "SV200") (pin "3") (pinfunction "3_3") (pintype "passive"))
    )
    (net (code "5698") (name "unconnected-(SV200-Pad4)") (class "Default")
      (node (ref "SV200") (pin "4") (pinfunction "4_4") (pintype "passive"))
    )
    (net (code "5699") (name "unconnected-(SV200-Pad5)") (class "Default")
      (node (ref "SV200") (pin "5") (pinfunction "5_5") (pintype "passive"))
    )
    (net (code "5700") (name "unconnected-(SV200-Pad6)") (class "Default")
      (node (ref "SV200") (pin "6") (pinfunction "6_6") (pintype "passive"))
    )
    (net (code "5701") (name "unconnected-(SV200-Pad7)") (class "Default")
      (node (ref "SV200") (pin "7") (pinfunction "7_7") (pintype "passive"))
    )
    (net (code "5702") (name "unconnected-(SV200-Pad8)") (class "Default")
      (node (ref "SV200") (pin "8") (pinfunction "8_8") (pintype "passive"))
    )
    (net (code "5703") (name "unconnected-(SV200-Pad9)") (class "Default")
      (node (ref "SV200") (pin "9") (pinfunction "9_9") (pintype "passive"))
    )
    (net (code "5704") (name "unconnected-(SV200-Pad10)") (class "Default")
      (node (ref "SV200") (pin "10") (pinfunction "10_10") (pintype "passive"))
    )
    (net (code "5705") (name "unconnected-(SV200-Pad11)") (class "Default")
      (node (ref "SV200") (pin "11") (pinfunction "11_11") (pintype "passive"))
    )
    (net (code "5706") (name "unconnected-(SV200-Pad12)") (class "Default")
      (node (ref "SV200") (pin "12") (pinfunction "12_12") (pintype "passive"))
    )
    (net (code "5707") (name "unconnected-(SV200-Pad13)") (class "Default")
      (node (ref "SV200") (pin "13") (pinfunction "13_13") (pintype "passive"))
    )
    (net (code "5708") (name "unconnected-(SV200-Pad14)") (class "Default")
      (node (ref "SV200") (pin "14") (pinfunction "14_14") (pintype "passive"))
    )
    (net (code "5709") (name "unconnected-(SV200-Pad15)") (class "Default")
      (node (ref "SV200") (pin "15") (pinfunction "15_15") (pintype "passive"))
    )
    (net (code "5710") (name "unconnected-(SV200-Pad16)") (class "Default")
      (node (ref "SV200") (pin "16") (pinfunction "16_16") (pintype "passive"))
    )
    (net (code "5711") (name "unconnected-(SV200-Pad17)") (class "Default")
      (node (ref "SV200") (pin "17") (pinfunction "17_17") (pintype "passive"))
    )
    (net (code "5712") (name "unconnected-(SV200-Pad18)") (class "Default")
      (node (ref "SV200") (pin "18") (pinfunction "18_18") (pintype "passive"))
    )
    (net (code "5713") (name "unconnected-(SV200-Pad19)") (class "Default")
      (node (ref "SV200") (pin "19") (pinfunction "19_19") (pintype "passive"))
    )
    (net (code "5714") (name "unconnected-(SV200-Pad20)") (class "Default")
      (node (ref "SV200") (pin "20") (pinfunction "20_20") (pintype "passive"))
    )
    (net (code "5715") (name "unconnected-(SV200-Pad21)") (class "Default")
      (node (ref "SV200") (pin "21") (pinfunction "21_21") (pintype "passive"))
    )
    (net (code "5716") (name "unconnected-(SV200-Pad22)") (class "Default")
      (node (ref "SV200") (pin "22") (pinfunction "22_22") (pintype "passive"))
    )
    (net (code "5717") (name "unconnected-(SV200-Pad23)") (class "Default")
      (node (ref "SV200") (pin "23") (pinfunction "23_23") (pintype "passive"))
    )
    (net (code "5718") (name "unconnected-(SV200-Pad24)") (class "Default")
      (node (ref "SV200") (pin "24") (pinfunction "24_24") (pintype "passive"))
    )
    (net (code "5719") (name "unconnected-(SV200-Pad25)") (class "Default")
      (node (ref "SV200") (pin "25") (pinfunction "25_25") (pintype "passive"))
    )
    (net (code "5720") (name "unconnected-(SV200-Pad26)") (class "Default")
      (node (ref "SV200") (pin "26") (pinfunction "26_26") (pintype "passive"))
    )
    (net (code "5721") (name "unconnected-(SV200-Pad27)") (class "Default")
      (node (ref "SV200") (pin "27") (pinfunction "27_27") (pintype "passive"))
    )
    (net (code "5722") (name "unconnected-(SV200-Pad28)") (class "Default")
      (node (ref "SV200") (pin "28") (pinfunction "28_28") (pintype "passive"))
    )
    (net (code "5723") (name "unconnected-(SV200-Pad29)") (class "Default")
      (node (ref "SV200") (pin "29") (pinfunction "29_29") (pintype "passive"))
    )
    (net (code "5724") (name "unconnected-(SV200-Pad30)") (class "Default")
      (node (ref "SV200") (pin "30") (pinfunction "30_30") (pintype "passive"))
    )
    (net (code "5725") (name "unconnected-(SV200-Pad31)") (class "Default")
      (node (ref "SV200") (pin "31") (pinfunction "31_31") (pintype "passive"))
    )
    (net (code "5726") (name "unconnected-(SV200-Pad32)") (class "Default")
      (node (ref "SV200") (pin "32") (pinfunction "32_32") (pintype "passive"))
    )
    (net (code "5727") (name "unconnected-(SV200-Pad33)") (class "Default")
      (node (ref "SV200") (pin "33") (pinfunction "33_33") (pintype "passive"))
    )
    (net (code "5728") (name "unconnected-(SV200-Pad34)") (class "Default")
      (node (ref "SV200") (pin "34") (pinfunction "34_34") (pintype "passive"))
    )
    (net (code "5729") (name "unconnected-(SV200-Pad35)") (class "Default")
      (node (ref "SV200") (pin "35") (pinfunction "35_35") (pintype "passive"))
    )
    (net (code "5730") (name "unconnected-(SV200-Pad36)") (class "Default")
      (node (ref "SV200") (pin "36") (pinfunction "36_36") (pintype "passive"))
    )
    (net (code "5731") (name "unconnected-(SV200-Pad37)") (class "Default")
      (node (ref "SV200") (pin "37") (pinfunction "37_37") (pintype "passive"))
    )
    (net (code "5732") (name "unconnected-(SV200-Pad38)") (class "Default")
      (node (ref "SV200") (pin "38") (pinfunction "38_38") (pintype "passive"))
    )
    (net (code "5733") (name "unconnected-(SV200-Pad39)") (class "Default")
      (node (ref "SV200") (pin "39") (pinfunction "39_39") (pintype "passive"))
    )
    (net (code "5734") (name "unconnected-(SV200-Pad40)") (class "Default")
      (node (ref "SV200") (pin "40") (pinfunction "40_40") (pintype "passive"))
    )
    (net (code "5735") (name "unconnected-(SV201-Pad1)") (class "Default")
      (node (ref "SV201") (pin "1") (pinfunction "1_1") (pintype "passive"))
    )
    (net (code "5736") (name "unconnected-(SV201-Pad2)") (class "Default")
      (node (ref "SV201") (pin "2") (pinfunction "2_2") (pintype "passive"))
    )
    (net (code "5737") (name "unconnected-(SV201-Pad3)") (class "Default")
      (node (ref "SV201") (pin "3") (pinfunction "3_3") (pintype "passive"))
    )
    (net (code "5738") (name "unconnected-(SV201-Pad4)") (class "Default")
      (node (ref "SV201") (pin "4") (pinfunction "4_4") (pintype "passive"))
    )
    (net (code "5739") (name "unconnected-(SV201-Pad5)") (class "Default")
      (node (ref "SV201") (pin "5") (pinfunction "5_5") (pintype "passive"))
    )
    (net (code "5740") (name "unconnected-(SV201-Pad6)") (class "Default")
      (node (ref "SV201") (pin "6") (pinfunction "6_6") (pintype "passive"))
    )
    (net (code "5741") (name "unconnected-(SV201-Pad7)") (class "Default")
      (node (ref "SV201") (pin "7") (pinfunction "7_7") (pintype "passive"))
    )
    (net (code "5742") (name "unconnected-(SV201-Pad8)") (class "Default")
      (node (ref "SV201") (pin "8") (pinfunction "8_8") (pintype "passive"))
    )
    (net (code "5743") (name "unconnected-(SV201-Pad9)") (class "Default")
      (node (ref "SV201") (pin "9") (pinfunction "9_9") (pintype "passive"))
    )
    (net (code "5744") (name "unconnected-(SV201-Pad10)") (class "Default")
      (node (ref "SV201") (pin "10") (pinfunction "10_10") (pintype "passive"))
    )
    (net (code "5745") (name "unconnected-(SV201-Pad11)") (class "Default")
      (node (ref "SV201") (pin "11") (pinfunction "11_11") (pintype "passive"))
    )
    (net (code "5746") (name "unconnected-(SV201-Pad12)") (class "Default")
      (node (ref "SV201") (pin "12") (pinfunction "12_12") (pintype "passive"))
    )
    (net (code "5747") (name "unconnected-(SV201-Pad13)") (class "Default")
      (node (ref "SV201") (pin "13") (pinfunction "13_13") (pintype "passive"))
    )
    (net (code "5748") (name "unconnected-(SV201-Pad14)") (class "Default")
      (node (ref "SV201") (pin "14") (pinfunction "14_14") (pintype "passive"))
    )
    (net (code "5749") (name "unconnected-(SV201-Pad15)") (class "Default")
      (node (ref "SV201") (pin "15") (pinfunction "15_15") (pintype "passive"))
    )
    (net (code "5750") (name "unconnected-(SV201-Pad16)") (class "Default")
      (node (ref "SV201") (pin "16") (pinfunction "16_16") (pintype "passive"))
    )
    (net (code "5751") (name "unconnected-(SV201-Pad17)") (class "Default")
      (node (ref "SV201") (pin "17") (pinfunction "17_17") (pintype "passive"))
    )
    (net (code "5752") (name "unconnected-(SV201-Pad18)") (class "Default")
      (node (ref "SV201") (pin "18") (pinfunction "18_18") (pintype "passive"))
    )
    (net (code "5753") (name "unconnected-(SV201-Pad19)") (class "Default")
      (node (ref "SV201") (pin "19") (pinfunction "19_19") (pintype "passive"))
    )
    (net (code "5754") (name "unconnected-(SV201-Pad20)") (class "Default")
      (node (ref "SV201") (pin "20") (pinfunction "20_20") (pintype "passive"))
    )
    (net (code "5755") (name "unconnected-(SV201-Pad21)") (class "Default")
      (node (ref "SV201") (pin "21") (pinfunction "21_21") (pintype "passive"))
    )
    (net (code "5756") (name "unconnected-(SV201-Pad22)") (class "Default")
      (node (ref "SV201") (pin "22") (pinfunction "22_22") (pintype "passive"))
    )
    (net (code "5757") (name "unconnected-(SV201-Pad23)") (class "Default")
      (node (ref "SV201") (pin "23") (pinfunction "23_23") (pintype "passive"))
    )
    (net (code "5758") (name "unconnected-(SV201-Pad24)") (class "Default")
      (node (ref "SV201") (pin "24") (pinfunction "24_24") (pintype "passive"))
    )
    (net (code "5759") (name "unconnected-(SV201-Pad25)") (class "Default")
      (node (ref "SV201") (pin "25") (pinfunction "25_25") (pintype "passive"))
    )
    (net (code "5760") (name "unconnected-(SV201-Pad26)") (class "Default")
      (node (ref "SV201") (pin "26") (pinfunction "26_26") (pintype "passive"))
    )
    (net (code "5761") (name "unconnected-(SV201-Pad27)") (class "Default")
      (node (ref "SV201") (pin "27") (pinfunction "27_27") (pintype "passive"))
    )
    (net (code "5762") (name "unconnected-(SV201-Pad28)") (class "Default")
      (node (ref "SV201") (pin "28") (pinfunction "28_28") (pintype "passive"))
    )
    (net (code "5763") (name "unconnected-(SV201-Pad29)") (class "Default")
      (node (ref "SV201") (pin "29") (pinfunction "29_29") (pintype "passive"))
    )
    (net (code "5764") (name "unconnected-(SV201-Pad30)") (class "Default")
      (node (ref "SV201") (pin "30") (pinfunction "30_30") (pintype "passive"))
    )
    (net (code "5765") (name "unconnected-(SV201-Pad31)") (class "Default")
      (node (ref "SV201") (pin "31") (pinfunction "31_31") (pintype "passive"))
    )
    (net (code "5766") (name "unconnected-(SV201-Pad32)") (class "Default")
      (node (ref "SV201") (pin "32") (pinfunction "32_32") (pintype "passive"))
    )
    (net (code "5767") (name "unconnected-(SV201-Pad33)") (class "Default")
      (node (ref "SV201") (pin "33") (pinfunction "33_33") (pintype "passive"))
    )
    (net (code "5768") (name "unconnected-(SV201-Pad34)") (class "Default")
      (node (ref "SV201") (pin "34") (pinfunction "34_34") (pintype "passive"))
    )
    (net (code "5769") (name "unconnected-(SV201-Pad35)") (class "Default")
      (node (ref "SV201") (pin "35") (pinfunction "35_35") (pintype "passive"))
    )
    (net (code "5770") (name "unconnected-(SV201-Pad36)") (class "Default")
      (node (ref "SV201") (pin "36") (pinfunction "36_36") (pintype "passive"))
    )
    (net (code "5771") (name "unconnected-(SV201-Pad37)") (class "Default")
      (node (ref "SV201") (pin "37") (pinfunction "37_37") (pintype "passive"))
    )
    (net (code "5772") (name "unconnected-(SV201-Pad38)") (class "Default")
      (node (ref "SV201") (pin "38") (pinfunction "38_38") (pintype "passive"))
    )
    (net (code "5773") (name "unconnected-(SV201-Pad39)") (class "Default")
      (node (ref "SV201") (pin "39") (pinfunction "39_39") (pintype "passive"))
    )
    (net (code "5774") (name "unconnected-(SV201-Pad40)") (class "Default")
      (node (ref "SV201") (pin "40") (pinfunction "40_40") (pintype "passive"))
    )
    (net (code "5775") (name "unconnected-(SV202-Pad1)") (class "Default")
      (node (ref "SV202") (pin "1") (pinfunction "1_1") (pintype "passive"))
    )
    (net (code "5776") (name "unconnected-(SV202-Pad2)") (class "Default")
      (node (ref "SV202") (pin "2") (pinfunction "2_2") (pintype "passive"))
    )
    (net (code "5777") (name "unconnected-(SV202-Pad3)") (class "Default")
      (node (ref "SV202") (pin "3") (pinfunction "3_3") (pintype "passive"))
    )
    (net (code "5778") (name "unconnected-(SV202-Pad4)") (class "Default")
      (node (ref "SV202") (pin "4") (pinfunction "4_4") (pintype "passive"))
    )
    (net (code "5779") (name "unconnected-(SV202-Pad5)") (class "Default")
      (node (ref "SV202") (pin "5") (pinfunction "5_5") (pintype "passive"))
    )
    (net (code "5780") (name "unconnected-(SV202-Pad6)") (class "Default")
      (node (ref "SV202") (pin "6") (pinfunction "6_6") (pintype "passive"))
    )
    (net (code "5781") (name "unconnected-(SV202-Pad7)") (class "Default")
      (node (ref "SV202") (pin "7") (pinfunction "7_7") (pintype "passive"))
    )
    (net (code "5782") (name "unconnected-(SV202-Pad8)") (class "Default")
      (node (ref "SV202") (pin "8") (pinfunction "8_8") (pintype "passive"))
    )
    (net (code "5783") (name "unconnected-(SV202-Pad9)") (class "Default")
      (node (ref "SV202") (pin "9") (pinfunction "9_9") (pintype "passive"))
    )
    (net (code "5784") (name "unconnected-(SV202-Pad10)") (class "Default")
      (node (ref "SV202") (pin "10") (pinfunction "10_10") (pintype "passive"))
    )
    (net (code "5785") (name "unconnected-(SV202-Pad11)") (class "Default")
      (node (ref "SV202") (pin "11") (pinfunction "11_11") (pintype "passive"))
    )
    (net (code "5786") (name "unconnected-(SV202-Pad12)") (class "Default")
      (node (ref "SV202") (pin "12") (pinfunction "12_12") (pintype "passive"))
    )
    (net (code "5787") (name "unconnected-(SV202-Pad13)") (class "Default")
      (node (ref "SV202") (pin "13") (pinfunction "13_13") (pintype "passive"))
    )
    (net (code "5788") (name "unconnected-(SV202-Pad14)") (class "Default")
      (node (ref "SV202") (pin "14") (pinfunction "14_14") (pintype "passive"))
    )
    (net (code "5789") (name "unconnected-(SV202-Pad15)") (class "Default")
      (node (ref "SV202") (pin "15") (pinfunction "15_15") (pintype "passive"))
    )
    (net (code "5790") (name "unconnected-(SV202-Pad16)") (class "Default")
      (node (ref "SV202") (pin "16") (pinfunction "16_16") (pintype "passive"))
    )
    (net (code "5791") (name "unconnected-(SV202-Pad17)") (class "Default")
      (node (ref "SV202") (pin "17") (pinfunction "17_17") (pintype "passive"))
    )
    (net (code "5792") (name "unconnected-(SV202-Pad18)") (class "Default")
      (node (ref "SV202") (pin "18") (pinfunction "18_18") (pintype "passive"))
    )
    (net (code "5793") (name "unconnected-(SV202-Pad19)") (class "Default")
      (node (ref "SV202") (pin "19") (pinfunction "19_19") (pintype "passive"))
    )
    (net (code "5794") (name "unconnected-(SV202-Pad20)") (class "Default")
      (node (ref "SV202") (pin "20") (pinfunction "20_20") (pintype "passive"))
    )
    (net (code "5795") (name "unconnected-(SV202-Pad21)") (class "Default")
      (node (ref "SV202") (pin "21") (pinfunction "21_21") (pintype "passive"))
    )
    (net (code "5796") (name "unconnected-(SV202-Pad22)") (class "Default")
      (node (ref "SV202") (pin "22") (pinfunction "22_22") (pintype "passive"))
    )
    (net (code "5797") (name "unconnected-(SV202-Pad23)") (class "Default")
      (node (ref "SV202") (pin "23") (pinfunction "23_23") (pintype "passive"))
    )
    (net (code "5798") (name "unconnected-(SV202-Pad24)") (class "Default")
      (node (ref "SV202") (pin "24") (pinfunction "24_24") (pintype "passive"))
    )
    (net (code "5799") (name "unconnected-(SV202-Pad25)") (class "Default")
      (node (ref "SV202") (pin "25") (pinfunction "25_25") (pintype "passive"))
    )
    (net (code "5800") (name "unconnected-(SV202-Pad26)") (class "Default")
      (node (ref "SV202") (pin "26") (pinfunction "26_26") (pintype "passive"))
    )
    (net (code "5801") (name "unconnected-(SV202-Pad27)") (class "Default")
      (node (ref "SV202") (pin "27") (pinfunction "27_27") (pintype "passive"))
    )
    (net (code "5802") (name "unconnected-(SV202-Pad28)") (class "Default")
      (node (ref "SV202") (pin "28") (pinfunction "28_28") (pintype "passive"))
    )
    (net (code "5803") (name "unconnected-(SV202-Pad29)") (class "Default")
      (node (ref "SV202") (pin "29") (pinfunction "29_29") (pintype "passive"))
    )
    (net (code "5804") (name "unconnected-(SV202-Pad30)") (class "Default")
      (node (ref "SV202") (pin "30") (pinfunction "30_30") (pintype "passive"))
    )
    (net (code "5805") (name "unconnected-(SV202-Pad31)") (class "Default")
      (node (ref "SV202") (pin "31") (pinfunction "31_31") (pintype "passive"))
    )
    (net (code "5806") (name "unconnected-(SV202-Pad32)") (class "Default")
      (node (ref "SV202") (pin "32") (pinfunction "32_32") (pintype "passive"))
    )
    (net (code "5807") (name "unconnected-(SV202-Pad33)") (class "Default")
      (node (ref "SV202") (pin "33") (pinfunction "33_33") (pintype "passive"))
    )
    (net (code "5808") (name "unconnected-(SV202-Pad34)") (class "Default")
      (node (ref "SV202") (pin "34") (pinfunction "34_34") (pintype "passive"))
    )
    (net (code "5809") (name "unconnected-(SV202-Pad35)") (class "Default")
      (node (ref "SV202") (pin "35") (pinfunction "35_35") (pintype "passive"))
    )
    (net (code "5810") (name "unconnected-(SV202-Pad36)") (class "Default")
      (node (ref "SV202") (pin "36") (pinfunction "36_36") (pintype "passive"))
    )
    (net (code "5811") (name "unconnected-(SV202-Pad37)") (class "Default")
      (node (ref "SV202") (pin "37") (pinfunction "37_37") (pintype "passive"))
    )
    (net (code "5812") (name "unconnected-(SV202-Pad38)") (class "Default")
      (node (ref "SV202") (pin "38") (pinfunction "38_38") (pintype "passive"))
    )
    (net (code "5813") (name "unconnected-(SV202-Pad39)") (class "Default")
      (node (ref "SV202") (pin "39") (pinfunction "39_39") (pintype "passive"))
    )
    (net (code "5814") (name "unconnected-(SV202-Pad40)") (class "Default")
      (node (ref "SV202") (pin "40") (pinfunction "40_40") (pintype "passive"))
    )
    (net (code "5815") (name "unconnected-(SV203-Pad1)") (class "Default")
      (node (ref "SV203") (pin "1") (pinfunction "1_1") (pintype "passive"))
    )
    (net (code "5816") (name "unconnected-(SV203-Pad2)") (class "Default")
      (node (ref "SV203") (pin "2") (pinfunction "2_2") (pintype "passive"))
    )
    (net (code "5817") (name "unconnected-(SV203-Pad3)") (class "Default")
      (node (ref "SV203") (pin "3") (pinfunction "3_3") (pintype "passive"))
    )
    (net (code "5818") (name "unconnected-(SV203-Pad4)") (class "Default")
      (node (ref "SV203") (pin "4") (pinfunction "4_4") (pintype "passive"))
    )
    (net (code "5819") (name "unconnected-(SV203-Pad5)") (class "Default")
      (node (ref "SV203") (pin "5") (pinfunction "5_5") (pintype "passive"))
    )
    (net (code "5820") (name "unconnected-(SV203-Pad6)") (class "Default")
      (node (ref "SV203") (pin "6") (pinfunction "6_6") (pintype "passive"))
    )
    (net (code "5821") (name "unconnected-(SV203-Pad7)") (class "Default")
      (node (ref "SV203") (pin "7") (pinfunction "7_7") (pintype "passive"))
    )
    (net (code "5822") (name "unconnected-(SV203-Pad8)") (class "Default")
      (node (ref "SV203") (pin "8") (pinfunction "8_8") (pintype "passive"))
    )
    (net (code "5823") (name "unconnected-(SV203-Pad9)") (class "Default")
      (node (ref "SV203") (pin "9") (pinfunction "9_9") (pintype "passive"))
    )
    (net (code "5824") (name "unconnected-(SV203-Pad10)") (class "Default")
      (node (ref "SV203") (pin "10") (pinfunction "10_10") (pintype "passive"))
    )
    (net (code "5825") (name "unconnected-(SV203-Pad11)") (class "Default")
      (node (ref "SV203") (pin "11") (pinfunction "11_11") (pintype "passive"))
    )
    (net (code "5826") (name "unconnected-(SV203-Pad12)") (class "Default")
      (node (ref "SV203") (pin "12") (pinfunction "12_12") (pintype "passive"))
    )
    (net (code "5827") (name "unconnected-(SV203-Pad13)") (class "Default")
      (node (ref "SV203") (pin "13") (pinfunction "13_13") (pintype "passive"))
    )
    (net (code "5828") (name "unconnected-(SV203-Pad14)") (class "Default")
      (node (ref "SV203") (pin "14") (pinfunction "14_14") (pintype "passive"))
    )
    (net (code "5829") (name "unconnected-(SV203-Pad15)") (class "Default")
      (node (ref "SV203") (pin "15") (pinfunction "15_15") (pintype "passive"))
    )
    (net (code "5830") (name "unconnected-(SV203-Pad16)") (class "Default")
      (node (ref "SV203") (pin "16") (pinfunction "16_16") (pintype "passive"))
    )
    (net (code "5831") (name "unconnected-(SV203-Pad17)") (class "Default")
      (node (ref "SV203") (pin "17") (pinfunction "17_17") (pintype "passive"))
    )
    (net (code "5832") (name "unconnected-(SV203-Pad18)") (class "Default")
      (node (ref "SV203") (pin "18") (pinfunction "18_18") (pintype "passive"))
    )
    (net (code "5833") (name "unconnected-(SV203-Pad19)") (class "Default")
      (node (ref "SV203") (pin "19") (pinfunction "19_19") (pintype "passive"))
    )
    (net (code "5834") (name "unconnected-(SV203-Pad20)") (class "Default")
      (node (ref "SV203") (pin "20") (pinfunction "20_20") (pintype "passive"))
    )
    (net (code "5835") (name "unconnected-(SV203-Pad21)") (class "Default")
      (node (ref "SV203") (pin "21") (pinfunction "21_21") (pintype "passive"))
    )
    (net (code "5836") (name "unconnected-(SV203-Pad22)") (class "Default")
      (node (ref "SV203") (pin "22") (pinfunction "22_22") (pintype "passive"))
    )
    (net (code "5837") (name "unconnected-(SV203-Pad23)") (class "Default")
      (node (ref "SV203") (pin "23") (pinfunction "23_23") (pintype "passive"))
    )
    (net (code "5838") (name "unconnected-(SV203-Pad24)") (class "Default")
      (node (ref "SV203") (pin "24") (pinfunction "24_24") (pintype "passive"))
    )
    (net (code "5839") (name "unconnected-(SV204-Pad1)") (class "Default")
      (node (ref "SV204") (pin "1") (pinfunction "1_1") (pintype "passive"))
    )
    (net (code "5840") (name "unconnected-(SV204-Pad2)") (class "Default")
      (node (ref "SV204") (pin "2") (pinfunction "2_2") (pintype "passive"))
    )
    (net (code "5841") (name "unconnected-(SV204-Pad3)") (class "Default")
      (node (ref "SV204") (pin "3") (pinfunction "3_3") (pintype "passive"))
    )
    (net (code "5842") (name "unconnected-(SV204-Pad4)") (class "Default")
      (node (ref "SV204") (pin "4") (pinfunction "4_4") (pintype "passive"))
    )
    (net (code "5843") (name "unconnected-(SV204-Pad5)") (class "Default")
      (node (ref "SV204") (pin "5") (pinfunction "5_5") (pintype "passive"))
    )
    (net (code "5844") (name "unconnected-(SV204-Pad6)") (class "Default")
      (node (ref "SV204") (pin "6") (pinfunction "6_6") (pintype "passive"))
    )
    (net (code "5845") (name "unconnected-(SV204-Pad7)") (class "Default")
      (node (ref "SV204") (pin "7") (pinfunction "7_7") (pintype "passive"))
    )
    (net (code "5846") (name "unconnected-(SV204-Pad8)") (class "Default")
      (node (ref "SV204") (pin "8") (pinfunction "8_8") (pintype "passive"))
    )
    (net (code "5847") (name "unconnected-(SV204-Pad9)") (class "Default")
      (node (ref "SV204") (pin "9") (pinfunction "9_9") (pintype "passive"))
    )
    (net (code "5848") (name "unconnected-(SV204-Pad10)") (class "Default")
      (node (ref "SV204") (pin "10") (pinfunction "10_10") (pintype "passive"))
    )
    (net (code "5849") (name "unconnected-(SV204-Pad11)") (class "Default")
      (node (ref "SV204") (pin "11") (pinfunction "11_11") (pintype "passive"))
    )
    (net (code "5850") (name "unconnected-(SV204-Pad12)") (class "Default")
      (node (ref "SV204") (pin "12") (pinfunction "12_12") (pintype "passive"))
    )
    (net (code "5851") (name "unconnected-(SV204-Pad13)") (class "Default")
      (node (ref "SV204") (pin "13") (pinfunction "13_13") (pintype "passive"))
    )
    (net (code "5852") (name "unconnected-(SV204-Pad14)") (class "Default")
      (node (ref "SV204") (pin "14") (pinfunction "14_14") (pintype "passive"))
    )
    (net (code "5853") (name "unconnected-(SV204-Pad15)") (class "Default")
      (node (ref "SV204") (pin "15") (pinfunction "15_15") (pintype "passive"))
    )
    (net (code "5854") (name "unconnected-(SV204-Pad16)") (class "Default")
      (node (ref "SV204") (pin "16") (pinfunction "16_16") (pintype "passive"))
    )
    (net (code "5855") (name "unconnected-(SV204-Pad17)") (class "Default")
      (node (ref "SV204") (pin "17") (pinfunction "17_17") (pintype "passive"))
    )
    (net (code "5856") (name "unconnected-(SV204-Pad18)") (class "Default")
      (node (ref "SV204") (pin "18") (pinfunction "18_18") (pintype "passive"))
    )
    (net (code "5857") (name "unconnected-(SV204-Pad19)") (class "Default")
      (node (ref "SV204") (pin "19") (pinfunction "19_19") (pintype "passive"))
    )
    (net (code "5858") (name "unconnected-(SV204-Pad20)") (class "Default")
      (node (ref "SV204") (pin "20") (pinfunction "20_20") (pintype "passive"))
    )
    (net (code "5859") (name "unconnected-(SV204-Pad21)") (class "Default")
      (node (ref "SV204") (pin "21") (pinfunction "21_21") (pintype "passive"))
    )
    (net (code "5860") (name "unconnected-(SV204-Pad22)") (class "Default")
      (node (ref "SV204") (pin "22") (pinfunction "22_22") (pintype "passive"))
    )
    (net (code "5861") (name "unconnected-(SV204-Pad23)") (class "Default")
      (node (ref "SV204") (pin "23") (pinfunction "23_23") (pintype "passive"))
    )
    (net (code "5862") (name "unconnected-(SV204-Pad24)") (class "Default")
      (node (ref "SV204") (pin "24") (pinfunction "24_24") (pintype "passive"))
    )
    (net (code "5863") (name "unconnected-(SV205-Pad1)") (class "Default")
      (node (ref "SV205") (pin "1") (pinfunction "1_1") (pintype "passive"))
    )
    (net (code "5864") (name "unconnected-(SV205-Pad2)") (class "Default")
      (node (ref "SV205") (pin "2") (pinfunction "2_2") (pintype "passive"))
    )
    (net (code "5865") (name "unconnected-(SV205-Pad3)") (class "Default")
      (node (ref "SV205") (pin "3") (pinfunction "3_3") (pintype "passive"))
    )
    (net (code "5866") (name "unconnected-(SV205-Pad4)") (class "Default")
      (node (ref "SV205") (pin "4") (pinfunction "4_4") (pintype "passive"))
    )
    (net (code "5867") (name "unconnected-(SV205-Pad5)") (class "Default")
      (node (ref "SV205") (pin "5") (pinfunction "5_5") (pintype "passive"))
    )
    (net (code "5868") (name "unconnected-(SV205-Pad6)") (class "Default")
      (node (ref "SV205") (pin "6") (pinfunction "6_6") (pintype "passive"))
    )
    (net (code "5869") (name "unconnected-(SV205-Pad7)") (class "Default")
      (node (ref "SV205") (pin "7") (pinfunction "7_7") (pintype "passive"))
    )
    (net (code "5870") (name "unconnected-(SV205-Pad8)") (class "Default")
      (node (ref "SV205") (pin "8") (pinfunction "8_8") (pintype "passive"))
    )
    (net (code "5871") (name "unconnected-(SV205-Pad9)") (class "Default")
      (node (ref "SV205") (pin "9") (pinfunction "9_9") (pintype "passive"))
    )
    (net (code "5872") (name "unconnected-(SV205-Pad10)") (class "Default")
      (node (ref "SV205") (pin "10") (pinfunction "10_10") (pintype "passive"))
    )
    (net (code "5873") (name "unconnected-(SV205-Pad11)") (class "Default")
      (node (ref "SV205") (pin "11") (pinfunction "11_11") (pintype "passive"))
    )
    (net (code "5874") (name "unconnected-(SV205-Pad12)") (class "Default")
      (node (ref "SV205") (pin "12") (pinfunction "12_12") (pintype "passive"))
    )
    (net (code "5875") (name "unconnected-(SV205-Pad13)") (class "Default")
      (node (ref "SV205") (pin "13") (pinfunction "13_13") (pintype "passive"))
    )
    (net (code "5876") (name "unconnected-(SV205-Pad14)") (class "Default")
      (node (ref "SV205") (pin "14") (pinfunction "14_14") (pintype "passive"))
    )
    (net (code "5877") (name "unconnected-(SV205-Pad15)") (class "Default")
      (node (ref "SV205") (pin "15") (pinfunction "15_15") (pintype "passive"))
    )
    (net (code "5878") (name "unconnected-(SV205-Pad16)") (class "Default")
      (node (ref "SV205") (pin "16") (pinfunction "16_16") (pintype "passive"))
    )
    (net (code "5879") (name "unconnected-(SV205-Pad17)") (class "Default")
      (node (ref "SV205") (pin "17") (pinfunction "17_17") (pintype "passive"))
    )
    (net (code "5880") (name "unconnected-(SV205-Pad18)") (class "Default")
      (node (ref "SV205") (pin "18") (pinfunction "18_18") (pintype "passive"))
    )
    (net (code "5881") (name "unconnected-(SV205-Pad19)") (class "Default")
      (node (ref "SV205") (pin "19") (pinfunction "19_19") (pintype "passive"))
    )
    (net (code "5882") (name "unconnected-(SV205-Pad20)") (class "Default")
      (node (ref "SV205") (pin "20") (pinfunction "20_20") (pintype "passive"))
    )
    (net (code "5883") (name "unconnected-(SV205-Pad21)") (class "Default")
      (node (ref "SV205") (pin "21") (pinfunction "21_21") (pintype "passive"))
    )
    (net (code "5884") (name "unconnected-(SV205-Pad22)") (class "Default")
      (node (ref "SV205") (pin "22") (pinfunction "22_22") (pintype "passive"))
    )
    (net (code "5885") (name "unconnected-(SV205-Pad23)") (class "Default")
      (node (ref "SV205") (pin "23") (pinfunction "23_23") (pintype "passive"))
    )
    (net (code "5886") (name "unconnected-(SV205-Pad24)") (class "Default")
      (node (ref "SV205") (pin "24") (pinfunction "24_24") (pintype "passive"))
    )
    (net (code "5887") (name "unconnected-(SV206-Pad1)") (class "Default")
      (node (ref "SV206") (pin "1") (pinfunction "1_1") (pintype "passive"))
    )
    (net (code "5888") (name "unconnected-(SV206-Pad2)") (class "Default")
      (node (ref "SV206") (pin "2") (pinfunction "2_2") (pintype "passive"))
    )
    (net (code "5889") (name "unconnected-(SV206-Pad3)") (class "Default")
      (node (ref "SV206") (pin "3") (pinfunction "3_3") (pintype "passive"))
    )
    (net (code "5890") (name "unconnected-(SV206-Pad4)") (class "Default")
      (node (ref "SV206") (pin "4") (pinfunction "4_4") (pintype "passive"))
    )
    (net (code "5891") (name "unconnected-(SV206-Pad5)") (class "Default")
      (node (ref "SV206") (pin "5") (pinfunction "5_5") (pintype "passive"))
    )
    (net (code "5892") (name "unconnected-(SV206-Pad6)") (class "Default")
      (node (ref "SV206") (pin "6") (pinfunction "6_6") (pintype "passive"))
    )
    (net (code "5893") (name "unconnected-(SV206-Pad7)") (class "Default")
      (node (ref "SV206") (pin "7") (pinfunction "7_7") (pintype "passive"))
    )
    (net (code "5894") (name "unconnected-(SV206-Pad8)") (class "Default")
      (node (ref "SV206") (pin "8") (pinfunction "8_8") (pintype "passive"))
    )
    (net (code "5895") (name "unconnected-(SV206-Pad9)") (class "Default")
      (node (ref "SV206") (pin "9") (pinfunction "9_9") (pintype "passive"))
    )
    (net (code "5896") (name "unconnected-(SV206-Pad10)") (class "Default")
      (node (ref "SV206") (pin "10") (pinfunction "10_10") (pintype "passive"))
    )
    (net (code "5897") (name "unconnected-(SV206-Pad11)") (class "Default")
      (node (ref "SV206") (pin "11") (pinfunction "11_11") (pintype "passive"))
    )
    (net (code "5898") (name "unconnected-(SV206-Pad12)") (class "Default")
      (node (ref "SV206") (pin "12") (pinfunction "12_12") (pintype "passive"))
    )
    (net (code "5899") (name "unconnected-(SV206-Pad13)") (class "Default")
      (node (ref "SV206") (pin "13") (pinfunction "13_13") (pintype "passive"))
    )
    (net (code "5900") (name "unconnected-(SV206-Pad14)") (class "Default")
      (node (ref "SV206") (pin "14") (pinfunction "14_14") (pintype "passive"))
    )
    (net (code "5901") (name "unconnected-(SV206-Pad15)") (class "Default")
      (node (ref "SV206") (pin "15") (pinfunction "15_15") (pintype "passive"))
    )
    (net (code "5902") (name "unconnected-(SV206-Pad16)") (class "Default")
      (node (ref "SV206") (pin "16") (pinfunction "16_16") (pintype "passive"))
    )
    (net (code "5903") (name "unconnected-(SV206-Pad17)") (class "Default")
      (node (ref "SV206") (pin "17") (pinfunction "17_17") (pintype "passive"))
    )
    (net (code "5904") (name "unconnected-(SV206-Pad18)") (class "Default")
      (node (ref "SV206") (pin "18") (pinfunction "18_18") (pintype "passive"))
    )
    (net (code "5905") (name "unconnected-(SV206-Pad19)") (class "Default")
      (node (ref "SV206") (pin "19") (pinfunction "19_19") (pintype "passive"))
    )
    (net (code "5906") (name "unconnected-(SV206-Pad20)") (class "Default")
      (node (ref "SV206") (pin "20") (pinfunction "20_20") (pintype "passive"))
    )
    (net (code "5907") (name "unconnected-(SV206-Pad21)") (class "Default")
      (node (ref "SV206") (pin "21") (pinfunction "21_21") (pintype "passive"))
    )
    (net (code "5908") (name "unconnected-(SV206-Pad22)") (class "Default")
      (node (ref "SV206") (pin "22") (pinfunction "22_22") (pintype "passive"))
    )
    (net (code "5909") (name "unconnected-(SV206-Pad23)") (class "Default")
      (node (ref "SV206") (pin "23") (pinfunction "23_23") (pintype "passive"))
    )
    (net (code "5910") (name "unconnected-(SV206-Pad24)") (class "Default")
      (node (ref "SV206") (pin "24") (pinfunction "24_24") (pintype "passive"))
    )
    (net (code "5911") (name "unconnected-(SV207-Pad1)") (class "Default")
      (node (ref "SV207") (pin "1") (pinfunction "1_1") (pintype "passive"))
    )
    (net (code "5912") (name "unconnected-(SV207-Pad2)") (class "Default")
      (node (ref "SV207") (pin "2") (pinfunction "2_2") (pintype "passive"))
    )
    (net (code "5913") (name "unconnected-(SV207-Pad3)") (class "Default")
      (node (ref "SV207") (pin "3") (pinfunction "3_3") (pintype "passive"))
    )
    (net (code "5914") (name "unconnected-(SV207-Pad4)") (class "Default")
      (node (ref "SV207") (pin "4") (pinfunction "4_4") (pintype "passive"))
    )
    (net (code "5915") (name "unconnected-(SV207-Pad5)") (class "Default")
      (node (ref "SV207") (pin "5") (pinfunction "5_5") (pintype "passive"))
    )
    (net (code "5916") (name "unconnected-(SV207-Pad6)") (class "Default")
      (node (ref "SV207") (pin "6") (pinfunction "6_6") (pintype "passive"))
    )
    (net (code "5917") (name "unconnected-(SV207-Pad7)") (class "Default")
      (node (ref "SV207") (pin "7") (pinfunction "7_7") (pintype "passive"))
    )
    (net (code "5918") (name "unconnected-(SV207-Pad8)") (class "Default")
      (node (ref "SV207") (pin "8") (pinfunction "8_8") (pintype "passive"))
    )
    (net (code "5919") (name "unconnected-(SV207-Pad9)") (class "Default")
      (node (ref "SV207") (pin "9") (pinfunction "9_9") (pintype "passive"))
    )
    (net (code "5920") (name "unconnected-(SV207-Pad10)") (class "Default")
      (node (ref "SV207") (pin "10") (pinfunction "10_10") (pintype "passive"))
    )
    (net (code "5921") (name "unconnected-(SV207-Pad11)") (class "Default")
      (node (ref "SV207") (pin "11") (pinfunction "11_11") (pintype "passive"))
    )
    (net (code "5922") (name "unconnected-(SV207-Pad12)") (class "Default")
      (node (ref "SV207") (pin "12") (pinfunction "12_12") (pintype "passive"))
    )
    (net (code "5923") (name "unconnected-(SV207-Pad13)") (class "Default")
      (node (ref "SV207") (pin "13") (pinfunction "13_13") (pintype "passive"))
    )
    (net (code "5924") (name "unconnected-(SV207-Pad14)") (class "Default")
      (node (ref "SV207") (pin "14") (pinfunction "14_14") (pintype "passive"))
    )
    (net (code "5925") (name "unconnected-(SV207-Pad15)") (class "Default")
      (node (ref "SV207") (pin "15") (pinfunction "15_15") (pintype "passive"))
    )
    (net (code "5926") (name "unconnected-(SV207-Pad16)") (class "Default")
      (node (ref "SV207") (pin "16") (pinfunction "16_16") (pintype "passive"))
    )
    (net (code "5927") (name "unconnected-(SV207-Pad17)") (class "Default")
      (node (ref "SV207") (pin "17") (pinfunction "17_17") (pintype "passive"))
    )
    (net (code "5928") (name "unconnected-(SV207-Pad18)") (class "Default")
      (node (ref "SV207") (pin "18") (pinfunction "18_18") (pintype "passive"))
    )
    (net (code "5929") (name "unconnected-(SV207-Pad19)") (class "Default")
      (node (ref "SV207") (pin "19") (pinfunction "19_19") (pintype "passive"))
    )
    (net (code "5930") (name "unconnected-(SV207-Pad20)") (class "Default")
      (node (ref "SV207") (pin "20") (pinfunction "20_20") (pintype "passive"))
    )
    (net (code "5931") (name "unconnected-(SV207-Pad21)") (class "Default")
      (node (ref "SV207") (pin "21") (pinfunction "21_21") (pintype "passive"))
    )
    (net (code "5932") (name "unconnected-(SV207-Pad22)") (class "Default")
      (node (ref "SV207") (pin "22") (pinfunction "22_22") (pintype "passive"))
    )
    (net (code "5933") (name "unconnected-(SV207-Pad23)") (class "Default")
      (node (ref "SV207") (pin "23") (pinfunction "23_23") (pintype "passive"))
    )
    (net (code "5934") (name "unconnected-(SV207-Pad24)") (class "Default")
      (node (ref "SV207") (pin "24") (pinfunction "24_24") (pintype "passive"))
    )
    (net (code "5935") (name "unconnected-(SV207-Pad25)") (class "Default")
      (node (ref "SV207") (pin "25") (pinfunction "25_25") (pintype "passive"))
    )
    (net (code "5936") (name "unconnected-(SV207-Pad26)") (class "Default")
      (node (ref "SV207") (pin "26") (pinfunction "26_26") (pintype "passive"))
    )
    (net (code "5937") (name "unconnected-(SV207-Pad27)") (class "Default")
      (node (ref "SV207") (pin "27") (pinfunction "27_27") (pintype "passive"))
    )
    (net (code "5938") (name "unconnected-(SV207-Pad28)") (class "Default")
      (node (ref "SV207") (pin "28") (pinfunction "28_28") (pintype "passive"))
    )
    (net (code "5939") (name "unconnected-(SV207-Pad29)") (class "Default")
      (node (ref "SV207") (pin "29") (pinfunction "29_29") (pintype "passive"))
    )
    (net (code "5940") (name "unconnected-(SV207-Pad30)") (class "Default")
      (node (ref "SV207") (pin "30") (pinfunction "30_30") (pintype "passive"))
    )
    (net (code "5941") (name "unconnected-(SV207-Pad31)") (class "Default")
      (node (ref "SV207") (pin "31") (pinfunction "31_31") (pintype "passive"))
    )
    (net (code "5942") (name "unconnected-(SV207-Pad32)") (class "Default")
      (node (ref "SV207") (pin "32") (pinfunction "32_32") (pintype "passive"))
    )
    (net (code "5943") (name "unconnected-(SV207-Pad33)") (class "Default")
      (node (ref "SV207") (pin "33") (pinfunction "33_33") (pintype "passive"))
    )
    (net (code "5944") (name "unconnected-(SV207-Pad34)") (class "Default")
      (node (ref "SV207") (pin "34") (pinfunction "34_34") (pintype "passive"))
    )
    (net (code "5945") (name "unconnected-(SV207-Pad35)") (class "Default")
      (node (ref "SV207") (pin "35") (pinfunction "35_35") (pintype "passive"))
    )
    (net (code "5946") (name "unconnected-(SV207-Pad36)") (class "Default")
      (node (ref "SV207") (pin "36") (pinfunction "36_36") (pintype "passive"))
    )
    (net (code "5947") (name "unconnected-(SV207-Pad37)") (class "Default")
      (node (ref "SV207") (pin "37") (pinfunction "37_37") (pintype "passive"))
    )
    (net (code "5948") (name "unconnected-(SV207-Pad38)") (class "Default")
      (node (ref "SV207") (pin "38") (pinfunction "38_38") (pintype "passive"))
    )
    (net (code "5949") (name "unconnected-(SV207-Pad39)") (class "Default")
      (node (ref "SV207") (pin "39") (pinfunction "39_39") (pintype "passive"))
    )
    (net (code "5950") (name "unconnected-(SV207-Pad40)") (class "Default")
      (node (ref "SV207") (pin "40") (pinfunction "40_40") (pintype "passive"))
    )
    (net (code "5951") (name "unconnected-(SV208-Pad1)") (class "Default")
      (node (ref "SV208") (pin "1") (pinfunction "1_1") (pintype "passive"))
    )
    (net (code "5952") (name "unconnected-(SV208-Pad2)") (class "Default")
      (node (ref "SV208") (pin "2") (pinfunction "2_2") (pintype "passive"))
    )
    (net (code "5953") (name "unconnected-(SV208-Pad3)") (class "Default")
      (node (ref "SV208") (pin "3") (pinfunction "3_3") (pintype "passive"))
    )
    (net (code "5954") (name "unconnected-(SV208-Pad4)") (class "Default")
      (node (ref "SV208") (pin "4") (pinfunction "4_4") (pintype "passive"))
    )
    (net (code "5955") (name "unconnected-(SV208-Pad5)") (class "Default")
      (node (ref "SV208") (pin "5") (pinfunction "5_5") (pintype "passive"))
    )
    (net (code "5956") (name "unconnected-(SV208-Pad6)") (class "Default")
      (node (ref "SV208") (pin "6") (pinfunction "6_6") (pintype "passive"))
    )
    (net (code "5957") (name "unconnected-(SV208-Pad7)") (class "Default")
      (node (ref "SV208") (pin "7") (pinfunction "7_7") (pintype "passive"))
    )
    (net (code "5958") (name "unconnected-(SV208-Pad8)") (class "Default")
      (node (ref "SV208") (pin "8") (pinfunction "8_8") (pintype "passive"))
    )
    (net (code "5959") (name "unconnected-(SV208-Pad9)") (class "Default")
      (node (ref "SV208") (pin "9") (pinfunction "9_9") (pintype "passive"))
    )
    (net (code "5960") (name "unconnected-(SV208-Pad10)") (class "Default")
      (node (ref "SV208") (pin "10") (pinfunction "10_10") (pintype "passive"))
    )
    (net (code "5961") (name "unconnected-(SV208-Pad11)") (class "Default")
      (node (ref "SV208") (pin "11") (pinfunction "11_11") (pintype "passive"))
    )
    (net (code "5962") (name "unconnected-(SV208-Pad12)") (class "Default")
      (node (ref "SV208") (pin "12") (pinfunction "12_12") (pintype "passive"))
    )
    (net (code "5963") (name "unconnected-(SV208-Pad13)") (class "Default")
      (node (ref "SV208") (pin "13") (pinfunction "13_13") (pintype "passive"))
    )
    (net (code "5964") (name "unconnected-(SV208-Pad14)") (class "Default")
      (node (ref "SV208") (pin "14") (pinfunction "14_14") (pintype "passive"))
    )
    (net (code "5965") (name "unconnected-(SV208-Pad15)") (class "Default")
      (node (ref "SV208") (pin "15") (pinfunction "15_15") (pintype "passive"))
    )
    (net (code "5966") (name "unconnected-(SV208-Pad16)") (class "Default")
      (node (ref "SV208") (pin "16") (pinfunction "16_16") (pintype "passive"))
    )
    (net (code "5967") (name "unconnected-(SV208-Pad17)") (class "Default")
      (node (ref "SV208") (pin "17") (pinfunction "17_17") (pintype "passive"))
    )
    (net (code "5968") (name "unconnected-(SV208-Pad18)") (class "Default")
      (node (ref "SV208") (pin "18") (pinfunction "18_18") (pintype "passive"))
    )
    (net (code "5969") (name "unconnected-(SV208-Pad19)") (class "Default")
      (node (ref "SV208") (pin "19") (pinfunction "19_19") (pintype "passive"))
    )
    (net (code "5970") (name "unconnected-(SV208-Pad20)") (class "Default")
      (node (ref "SV208") (pin "20") (pinfunction "20_20") (pintype "passive"))
    )
    (net (code "5971") (name "unconnected-(SV208-Pad21)") (class "Default")
      (node (ref "SV208") (pin "21") (pinfunction "21_21") (pintype "passive"))
    )
    (net (code "5972") (name "unconnected-(SV208-Pad22)") (class "Default")
      (node (ref "SV208") (pin "22") (pinfunction "22_22") (pintype "passive"))
    )
    (net (code "5973") (name "unconnected-(SV208-Pad23)") (class "Default")
      (node (ref "SV208") (pin "23") (pinfunction "23_23") (pintype "passive"))
    )
    (net (code "5974") (name "unconnected-(SV208-Pad24)") (class "Default")
      (node (ref "SV208") (pin "24") (pinfunction "24_24") (pintype "passive"))
    )
    (net (code "5975") (name "unconnected-(SV208-Pad25)") (class "Default")
      (node (ref "SV208") (pin "25") (pinfunction "25_25") (pintype "passive"))
    )
    (net (code "5976") (name "unconnected-(SV208-Pad26)") (class "Default")
      (node (ref "SV208") (pin "26") (pinfunction "26_26") (pintype "passive"))
    )
    (net (code "5977") (name "unconnected-(SV208-Pad27)") (class "Default")
      (node (ref "SV208") (pin "27") (pinfunction "27_27") (pintype "passive"))
    )
    (net (code "5978") (name "unconnected-(SV208-Pad28)") (class "Default")
      (node (ref "SV208") (pin "28") (pinfunction "28_28") (pintype "passive"))
    )
    (net (code "5979") (name "unconnected-(SV208-Pad29)") (class "Default")
      (node (ref "SV208") (pin "29") (pinfunction "29_29") (pintype "passive"))
    )
    (net (code "5980") (name "unconnected-(SV208-Pad30)") (class "Default")
      (node (ref "SV208") (pin "30") (pinfunction "30_30") (pintype "passive"))
    )
    (net (code "5981") (name "unconnected-(SV208-Pad31)") (class "Default")
      (node (ref "SV208") (pin "31") (pinfunction "31_31") (pintype "passive"))
    )
    (net (code "5982") (name "unconnected-(SV208-Pad32)") (class "Default")
      (node (ref "SV208") (pin "32") (pinfunction "32_32") (pintype "passive"))
    )
    (net (code "5983") (name "unconnected-(SV208-Pad33)") (class "Default")
      (node (ref "SV208") (pin "33") (pinfunction "33_33") (pintype "passive"))
    )
    (net (code "5984") (name "unconnected-(SV208-Pad34)") (class "Default")
      (node (ref "SV208") (pin "34") (pinfunction "34_34") (pintype "passive"))
    )
    (net (code "5985") (name "unconnected-(SV208-Pad35)") (class "Default")
      (node (ref "SV208") (pin "35") (pinfunction "35_35") (pintype "passive"))
    )
    (net (code "5986") (name "unconnected-(SV208-Pad36)") (class "Default")
      (node (ref "SV208") (pin "36") (pinfunction "36_36") (pintype "passive"))
    )
    (net (code "5987") (name "unconnected-(SV208-Pad37)") (class "Default")
      (node (ref "SV208") (pin "37") (pinfunction "37_37") (pintype "passive"))
    )
    (net (code "5988") (name "unconnected-(SV208-Pad38)") (class "Default")
      (node (ref "SV208") (pin "38") (pinfunction "38_38") (pintype "passive"))
    )
    (net (code "5989") (name "unconnected-(SV208-Pad39)") (class "Default")
      (node (ref "SV208") (pin "39") (pinfunction "39_39") (pintype "passive"))
    )
    (net (code "5990") (name "unconnected-(SV208-Pad40)") (class "Default")
      (node (ref "SV208") (pin "40") (pinfunction "40_40") (pintype "passive"))
    )
    (net (code "5991") (name "unconnected-(SV209-Pad1)") (class "Default")
      (node (ref "SV209") (pin "1") (pinfunction "1_1") (pintype "passive"))
    )
    (net (code "5992") (name "unconnected-(SV209-Pad2)") (class "Default")
      (node (ref "SV209") (pin "2") (pinfunction "2_2") (pintype "passive"))
    )
    (net (code "5993") (name "unconnected-(SV209-Pad3)") (class "Default")
      (node (ref "SV209") (pin "3") (pinfunction "3_3") (pintype "passive"))
    )
    (net (code "5994") (name "unconnected-(SV209-Pad4)") (class "Default")
      (node (ref "SV209") (pin "4") (pinfunction "4_4") (pintype "passive"))
    )
    (net (code "5995") (name "unconnected-(SV209-Pad5)") (class "Default")
      (node (ref "SV209") (pin "5") (pinfunction "5_5") (pintype "passive"))
    )
    (net (code "5996") (name "unconnected-(SV209-Pad6)") (class "Default")
      (node (ref "SV209") (pin "6") (pinfunction "6_6") (pintype "passive"))
    )
    (net (code "5997") (name "unconnected-(SV209-Pad7)") (class "Default")
      (node (ref "SV209") (pin "7") (pinfunction "7_7") (pintype "passive"))
    )
    (net (code "5998") (name "unconnected-(SV209-Pad8)") (class "Default")
      (node (ref "SV209") (pin "8") (pinfunction "8_8") (pintype "passive"))
    )
    (net (code "5999") (name "unconnected-(SV209-Pad9)") (class "Default")
      (node (ref "SV209") (pin "9") (pinfunction "9_9") (pintype "passive"))
    )
    (net (code "6000") (name "unconnected-(SV209-Pad10)") (class "Default")
      (node (ref "SV209") (pin "10") (pinfunction "10_10") (pintype "passive"))
    )
    (net (code "6001") (name "unconnected-(SV209-Pad11)") (class "Default")
      (node (ref "SV209") (pin "11") (pinfunction "11_11") (pintype "passive"))
    )
    (net (code "6002") (name "unconnected-(SV209-Pad12)") (class "Default")
      (node (ref "SV209") (pin "12") (pinfunction "12_12") (pintype "passive"))
    )
    (net (code "6003") (name "unconnected-(SV209-Pad13)") (class "Default")
      (node (ref "SV209") (pin "13") (pinfunction "13_13") (pintype "passive"))
    )
    (net (code "6004") (name "unconnected-(SV209-Pad14)") (class "Default")
      (node (ref "SV209") (pin "14") (pinfunction "14_14") (pintype "passive"))
    )
    (net (code "6005") (name "unconnected-(SV209-Pad15)") (class "Default")
      (node (ref "SV209") (pin "15") (pinfunction "15_15") (pintype "passive"))
    )
    (net (code "6006") (name "unconnected-(SV209-Pad16)") (class "Default")
      (node (ref "SV209") (pin "16") (pinfunction "16_16") (pintype "passive"))
    )
    (net (code "6007") (name "unconnected-(SV209-Pad17)") (class "Default")
      (node (ref "SV209") (pin "17") (pinfunction "17_17") (pintype "passive"))
    )
    (net (code "6008") (name "unconnected-(SV209-Pad18)") (class "Default")
      (node (ref "SV209") (pin "18") (pinfunction "18_18") (pintype "passive"))
    )
    (net (code "6009") (name "unconnected-(SV209-Pad19)") (class "Default")
      (node (ref "SV209") (pin "19") (pinfunction "19_19") (pintype "passive"))
    )
    (net (code "6010") (name "unconnected-(SV209-Pad20)") (class "Default")
      (node (ref "SV209") (pin "20") (pinfunction "20_20") (pintype "passive"))
    )
    (net (code "6011") (name "unconnected-(SV209-Pad21)") (class "Default")
      (node (ref "SV209") (pin "21") (pinfunction "21_21") (pintype "passive"))
    )
    (net (code "6012") (name "unconnected-(SV209-Pad22)") (class "Default")
      (node (ref "SV209") (pin "22") (pinfunction "22_22") (pintype "passive"))
    )
    (net (code "6013") (name "unconnected-(SV209-Pad23)") (class "Default")
      (node (ref "SV209") (pin "23") (pinfunction "23_23") (pintype "passive"))
    )
    (net (code "6014") (name "unconnected-(SV209-Pad24)") (class "Default")
      (node (ref "SV209") (pin "24") (pinfunction "24_24") (pintype "passive"))
    )
    (net (code "6015") (name "unconnected-(SV209-Pad25)") (class "Default")
      (node (ref "SV209") (pin "25") (pinfunction "25_25") (pintype "passive"))
    )
    (net (code "6016") (name "unconnected-(SV209-Pad26)") (class "Default")
      (node (ref "SV209") (pin "26") (pinfunction "26_26") (pintype "passive"))
    )
    (net (code "6017") (name "unconnected-(SV209-Pad27)") (class "Default")
      (node (ref "SV209") (pin "27") (pinfunction "27_27") (pintype "passive"))
    )
    (net (code "6018") (name "unconnected-(SV209-Pad28)") (class "Default")
      (node (ref "SV209") (pin "28") (pinfunction "28_28") (pintype "passive"))
    )
    (net (code "6019") (name "unconnected-(SV209-Pad29)") (class "Default")
      (node (ref "SV209") (pin "29") (pinfunction "29_29") (pintype "passive"))
    )
    (net (code "6020") (name "unconnected-(SV209-Pad30)") (class "Default")
      (node (ref "SV209") (pin "30") (pinfunction "30_30") (pintype "passive"))
    )
    (net (code "6021") (name "unconnected-(SV209-Pad31)") (class "Default")
      (node (ref "SV209") (pin "31") (pinfunction "31_31") (pintype "passive"))
    )
    (net (code "6022") (name "unconnected-(SV209-Pad32)") (class "Default")
      (node (ref "SV209") (pin "32") (pinfunction "32_32") (pintype "passive"))
    )
    (net (code "6023") (name "unconnected-(SV209-Pad33)") (class "Default")
      (node (ref "SV209") (pin "33") (pinfunction "33_33") (pintype "passive"))
    )
    (net (code "6024") (name "unconnected-(SV209-Pad34)") (class "Default")
      (node (ref "SV209") (pin "34") (pinfunction "34_34") (pintype "passive"))
    )
    (net (code "6025") (name "unconnected-(SV209-Pad35)") (class "Default")
      (node (ref "SV209") (pin "35") (pinfunction "35_35") (pintype "passive"))
    )
    (net (code "6026") (name "unconnected-(SV209-Pad36)") (class "Default")
      (node (ref "SV209") (pin "36") (pinfunction "36_36") (pintype "passive"))
    )
    (net (code "6027") (name "unconnected-(SV209-Pad37)") (class "Default")
      (node (ref "SV209") (pin "37") (pinfunction "37_37") (pintype "passive"))
    )
    (net (code "6028") (name "unconnected-(SV209-Pad38)") (class "Default")
      (node (ref "SV209") (pin "38") (pinfunction "38_38") (pintype "passive"))
    )
    (net (code "6029") (name "unconnected-(SV209-Pad39)") (class "Default")
      (node (ref "SV209") (pin "39") (pinfunction "39_39") (pintype "passive"))
    )
    (net (code "6030") (name "unconnected-(SV209-Pad40)") (class "Default")
      (node (ref "SV209") (pin "40") (pinfunction "40_40") (pintype "passive"))
    )
    (net (code "6031") (name "unconnected-(SV210-Pad1)") (class "Default")
      (node (ref "SV210") (pin "1") (pinfunction "1_1") (pintype "passive"))
    )
    (net (code "6032") (name "unconnected-(SV210-Pad2)") (class "Default")
      (node (ref "SV210") (pin "2") (pinfunction "2_2") (pintype "passive"))
    )
    (net (code "6033") (name "unconnected-(SV210-Pad3)") (class "Default")
      (node (ref "SV210") (pin "3") (pinfunction "3_3") (pintype "passive"))
    )
    (net (code "6034") (name "unconnected-(SV210-Pad4)") (class "Default")
      (node (ref "SV210") (pin "4") (pinfunction "4_4") (pintype "passive"))
    )
    (net (code "6035") (name "unconnected-(SV210-Pad5)") (class "Default")
      (node (ref "SV210") (pin "5") (pinfunction "5_5") (pintype "passive"))
    )
    (net (code "6036") (name "unconnected-(SV210-Pad6)") (class "Default")
      (node (ref "SV210") (pin "6") (pinfunction "6_6") (pintype "passive"))
    )
    (net (code "6037") (name "unconnected-(SV210-Pad7)") (class "Default")
      (node (ref "SV210") (pin "7") (pinfunction "7_7") (pintype "passive"))
    )
    (net (code "6038") (name "unconnected-(SV210-Pad8)") (class "Default")
      (node (ref "SV210") (pin "8") (pinfunction "8_8") (pintype "passive"))
    )
    (net (code "6039") (name "unconnected-(SV210-Pad9)") (class "Default")
      (node (ref "SV210") (pin "9") (pinfunction "9_9") (pintype "passive"))
    )
    (net (code "6040") (name "unconnected-(SV210-Pad10)") (class "Default")
      (node (ref "SV210") (pin "10") (pinfunction "10_10") (pintype "passive"))
    )
    (net (code "6041") (name "unconnected-(SV210-Pad11)") (class "Default")
      (node (ref "SV210") (pin "11") (pinfunction "11_11") (pintype "passive"))
    )
    (net (code "6042") (name "unconnected-(SV210-Pad12)") (class "Default")
      (node (ref "SV210") (pin "12") (pinfunction "12_12") (pintype "passive"))
    )
    (net (code "6043") (name "unconnected-(SV210-Pad13)") (class "Default")
      (node (ref "SV210") (pin "13") (pinfunction "13_13") (pintype "passive"))
    )
    (net (code "6044") (name "unconnected-(SV210-Pad14)") (class "Default")
      (node (ref "SV210") (pin "14") (pinfunction "14_14") (pintype "passive"))
    )
    (net (code "6045") (name "unconnected-(SV210-Pad15)") (class "Default")
      (node (ref "SV210") (pin "15") (pinfunction "15_15") (pintype "passive"))
    )
    (net (code "6046") (name "unconnected-(SV210-Pad16)") (class "Default")
      (node (ref "SV210") (pin "16") (pinfunction "16_16") (pintype "passive"))
    )
    (net (code "6047") (name "unconnected-(SV210-Pad17)") (class "Default")
      (node (ref "SV210") (pin "17") (pinfunction "17_17") (pintype "passive"))
    )
    (net (code "6048") (name "unconnected-(SV210-Pad18)") (class "Default")
      (node (ref "SV210") (pin "18") (pinfunction "18_18") (pintype "passive"))
    )
    (net (code "6049") (name "unconnected-(SV210-Pad19)") (class "Default")
      (node (ref "SV210") (pin "19") (pinfunction "19_19") (pintype "passive"))
    )
    (net (code "6050") (name "unconnected-(SV210-Pad20)") (class "Default")
      (node (ref "SV210") (pin "20") (pinfunction "20_20") (pintype "passive"))
    )
    (net (code "6051") (name "unconnected-(SV210-Pad21)") (class "Default")
      (node (ref "SV210") (pin "21") (pinfunction "21_21") (pintype "passive"))
    )
    (net (code "6052") (name "unconnected-(SV210-Pad22)") (class "Default")
      (node (ref "SV210") (pin "22") (pinfunction "22_22") (pintype "passive"))
    )
    (net (code "6053") (name "unconnected-(SV210-Pad23)") (class "Default")
      (node (ref "SV210") (pin "23") (pinfunction "23_23") (pintype "passive"))
    )
    (net (code "6054") (name "unconnected-(SV210-Pad24)") (class "Default")
      (node (ref "SV210") (pin "24") (pinfunction "24_24") (pintype "passive"))
    )
    (net (code "6055") (name "unconnected-(SV210-Pad25)") (class "Default")
      (node (ref "SV210") (pin "25") (pinfunction "25_25") (pintype "passive"))
    )
    (net (code "6056") (name "unconnected-(SV210-Pad26)") (class "Default")
      (node (ref "SV210") (pin "26") (pinfunction "26_26") (pintype "passive"))
    )
    (net (code "6057") (name "unconnected-(SV210-Pad27)") (class "Default")
      (node (ref "SV210") (pin "27") (pinfunction "27_27") (pintype "passive"))
    )
    (net (code "6058") (name "unconnected-(SV210-Pad28)") (class "Default")
      (node (ref "SV210") (pin "28") (pinfunction "28_28") (pintype "passive"))
    )
    (net (code "6059") (name "unconnected-(SV210-Pad29)") (class "Default")
      (node (ref "SV210") (pin "29") (pinfunction "29_29") (pintype "passive"))
    )
    (net (code "6060") (name "unconnected-(SV210-Pad30)") (class "Default")
      (node (ref "SV210") (pin "30") (pinfunction "30_30") (pintype "passive"))
    )
    (net (code "6061") (name "unconnected-(SV210-Pad31)") (class "Default")
      (node (ref "SV210") (pin "31") (pinfunction "31_31") (pintype "passive"))
    )
    (net (code "6062") (name "unconnected-(SV210-Pad32)") (class "Default")
      (node (ref "SV210") (pin "32") (pinfunction "32_32") (pintype "passive"))
    )
    (net (code "6063") (name "unconnected-(SV210-Pad33)") (class "Default")
      (node (ref "SV210") (pin "33") (pinfunction "33_33") (pintype "passive"))
    )
    (net (code "6064") (name "unconnected-(SV210-Pad34)") (class "Default")
      (node (ref "SV210") (pin "34") (pinfunction "34_34") (pintype "passive"))
    )
    (net (code "6065") (name "unconnected-(SV210-Pad35)") (class "Default")
      (node (ref "SV210") (pin "35") (pinfunction "35_35") (pintype "passive"))
    )
    (net (code "6066") (name "unconnected-(SV210-Pad36)") (class "Default")
      (node (ref "SV210") (pin "36") (pinfunction "36_36") (pintype "passive"))
    )
    (net (code "6067") (name "unconnected-(SV210-Pad37)") (class "Default")
      (node (ref "SV210") (pin "37") (pinfunction "37_37") (pintype "passive"))
    )
    (net (code "6068") (name "unconnected-(SV210-Pad38)") (class "Default")
      (node (ref "SV210") (pin "38") (pinfunction "38_38") (pintype "passive"))
    )
    (net (code "6069") (name "unconnected-(SV210-Pad39)") (class "Default")
      (node (ref "SV210") (pin "39") (pinfunction "39_39") (pintype "passive"))
    )
    (net (code "6070") (name "unconnected-(SV210-Pad40)") (class "Default")
      (node (ref "SV210") (pin "40") (pinfunction "40_40") (pintype "passive"))
    )
    (net (code "6071") (name "unconnected-(SV211-Pad1)") (class "Default")
      (node (ref "SV211") (pin "1") (pinfunction "1_1") (pintype "passive"))
    )
    (net (code "6072") (name "unconnected-(SV211-Pad2)") (class "Default")
      (node (ref "SV211") (pin "2") (pinfunction "2_2") (pintype "passive"))
    )
    (net (code "6073") (name "unconnected-(SV211-Pad3)") (class "Default")
      (node (ref "SV211") (pin "3") (pinfunction "3_3") (pintype "passive"))
    )
    (net (code "6074") (name "unconnected-(SV211-Pad4)") (class "Default")
      (node (ref "SV211") (pin "4") (pinfunction "4_4") (pintype "passive"))
    )
    (net (code "6075") (name "unconnected-(SV211-Pad5)") (class "Default")
      (node (ref "SV211") (pin "5") (pinfunction "5_5") (pintype "passive"))
    )
    (net (code "6076") (name "unconnected-(SV211-Pad6)") (class "Default")
      (node (ref "SV211") (pin "6") (pinfunction "6_6") (pintype "passive"))
    )
    (net (code "6077") (name "unconnected-(SV211-Pad7)") (class "Default")
      (node (ref "SV211") (pin "7") (pinfunction "7_7") (pintype "passive"))
    )
    (net (code "6078") (name "unconnected-(SV211-Pad8)") (class "Default")
      (node (ref "SV211") (pin "8") (pinfunction "8_8") (pintype "passive"))
    )
    (net (code "6079") (name "unconnected-(SV211-Pad9)") (class "Default")
      (node (ref "SV211") (pin "9") (pinfunction "9_9") (pintype "passive"))
    )
    (net (code "6080") (name "unconnected-(SV211-Pad10)") (class "Default")
      (node (ref "SV211") (pin "10") (pinfunction "10_10") (pintype "passive"))
    )
    (net (code "6081") (name "unconnected-(SV211-Pad11)") (class "Default")
      (node (ref "SV211") (pin "11") (pinfunction "11_11") (pintype "passive"))
    )
    (net (code "6082") (name "unconnected-(SV211-Pad12)") (class "Default")
      (node (ref "SV211") (pin "12") (pinfunction "12_12") (pintype "passive"))
    )
    (net (code "6083") (name "unconnected-(SV211-Pad13)") (class "Default")
      (node (ref "SV211") (pin "13") (pinfunction "13_13") (pintype "passive"))
    )
    (net (code "6084") (name "unconnected-(SV211-Pad14)") (class "Default")
      (node (ref "SV211") (pin "14") (pinfunction "14_14") (pintype "passive"))
    )
    (net (code "6085") (name "unconnected-(SV211-Pad15)") (class "Default")
      (node (ref "SV211") (pin "15") (pinfunction "15_15") (pintype "passive"))
    )
    (net (code "6086") (name "unconnected-(SV211-Pad16)") (class "Default")
      (node (ref "SV211") (pin "16") (pinfunction "16_16") (pintype "passive"))
    )
    (net (code "6087") (name "unconnected-(SV211-Pad17)") (class "Default")
      (node (ref "SV211") (pin "17") (pinfunction "17_17") (pintype "passive"))
    )
    (net (code "6088") (name "unconnected-(SV211-Pad18)") (class "Default")
      (node (ref "SV211") (pin "18") (pinfunction "18_18") (pintype "passive"))
    )
    (net (code "6089") (name "unconnected-(SV211-Pad19)") (class "Default")
      (node (ref "SV211") (pin "19") (pinfunction "19_19") (pintype "passive"))
    )
    (net (code "6090") (name "unconnected-(SV211-Pad20)") (class "Default")
      (node (ref "SV211") (pin "20") (pinfunction "20_20") (pintype "passive"))
    )
    (net (code "6091") (name "unconnected-(SV211-Pad21)") (class "Default")
      (node (ref "SV211") (pin "21") (pinfunction "21_21") (pintype "passive"))
    )
    (net (code "6092") (name "unconnected-(SV211-Pad22)") (class "Default")
      (node (ref "SV211") (pin "22") (pinfunction "22_22") (pintype "passive"))
    )
    (net (code "6093") (name "unconnected-(SV211-Pad23)") (class "Default")
      (node (ref "SV211") (pin "23") (pinfunction "23_23") (pintype "passive"))
    )
    (net (code "6094") (name "unconnected-(SV211-Pad24)") (class "Default")
      (node (ref "SV211") (pin "24") (pinfunction "24_24") (pintype "passive"))
    )
    (net (code "6095") (name "unconnected-(SV212-Pad1)") (class "Default")
      (node (ref "SV212") (pin "1") (pinfunction "1_1") (pintype "passive"))
    )
    (net (code "6096") (name "unconnected-(SV212-Pad2)") (class "Default")
      (node (ref "SV212") (pin "2") (pinfunction "2_2") (pintype "passive"))
    )
    (net (code "6097") (name "unconnected-(SV212-Pad3)") (class "Default")
      (node (ref "SV212") (pin "3") (pinfunction "3_3") (pintype "passive"))
    )
    (net (code "6098") (name "unconnected-(SV212-Pad4)") (class "Default")
      (node (ref "SV212") (pin "4") (pinfunction "4_4") (pintype "passive"))
    )
    (net (code "6099") (name "unconnected-(SV212-Pad5)") (class "Default")
      (node (ref "SV212") (pin "5") (pinfunction "5_5") (pintype "passive"))
    )
    (net (code "6100") (name "unconnected-(SV212-Pad6)") (class "Default")
      (node (ref "SV212") (pin "6") (pinfunction "6_6") (pintype "passive"))
    )
    (net (code "6101") (name "unconnected-(SV212-Pad7)") (class "Default")
      (node (ref "SV212") (pin "7") (pinfunction "7_7") (pintype "passive"))
    )
    (net (code "6102") (name "unconnected-(SV212-Pad8)") (class "Default")
      (node (ref "SV212") (pin "8") (pinfunction "8_8") (pintype "passive"))
    )
    (net (code "6103") (name "unconnected-(SV212-Pad9)") (class "Default")
      (node (ref "SV212") (pin "9") (pinfunction "9_9") (pintype "passive"))
    )
    (net (code "6104") (name "unconnected-(SV212-Pad10)") (class "Default")
      (node (ref "SV212") (pin "10") (pinfunction "10_10") (pintype "passive"))
    )
    (net (code "6105") (name "unconnected-(SV212-Pad11)") (class "Default")
      (node (ref "SV212") (pin "11") (pinfunction "11_11") (pintype "passive"))
    )
    (net (code "6106") (name "unconnected-(SV212-Pad12)") (class "Default")
      (node (ref "SV212") (pin "12") (pinfunction "12_12") (pintype "passive"))
    )
    (net (code "6107") (name "unconnected-(SV212-Pad13)") (class "Default")
      (node (ref "SV212") (pin "13") (pinfunction "13_13") (pintype "passive"))
    )
    (net (code "6108") (name "unconnected-(SV212-Pad14)") (class "Default")
      (node (ref "SV212") (pin "14") (pinfunction "14_14") (pintype "passive"))
    )
    (net (code "6109") (name "unconnected-(SV212-Pad15)") (class "Default")
      (node (ref "SV212") (pin "15") (pinfunction "15_15") (pintype "passive"))
    )
    (net (code "6110") (name "unconnected-(SV212-Pad16)") (class "Default")
      (node (ref "SV212") (pin "16") (pinfunction "16_16") (pintype "passive"))
    )
    (net (code "6111") (name "unconnected-(SV212-Pad17)") (class "Default")
      (node (ref "SV212") (pin "17") (pinfunction "17_17") (pintype "passive"))
    )
    (net (code "6112") (name "unconnected-(SV212-Pad18)") (class "Default")
      (node (ref "SV212") (pin "18") (pinfunction "18_18") (pintype "passive"))
    )
    (net (code "6113") (name "unconnected-(SV212-Pad19)") (class "Default")
      (node (ref "SV212") (pin "19") (pinfunction "19_19") (pintype "passive"))
    )
    (net (code "6114") (name "unconnected-(SV212-Pad20)") (class "Default")
      (node (ref "SV212") (pin "20") (pinfunction "20_20") (pintype "passive"))
    )
    (net (code "6115") (name "unconnected-(SV212-Pad21)") (class "Default")
      (node (ref "SV212") (pin "21") (pinfunction "21_21") (pintype "passive"))
    )
    (net (code "6116") (name "unconnected-(SV212-Pad22)") (class "Default")
      (node (ref "SV212") (pin "22") (pinfunction "22_22") (pintype "passive"))
    )
    (net (code "6117") (name "unconnected-(SV212-Pad23)") (class "Default")
      (node (ref "SV212") (pin "23") (pinfunction "23_23") (pintype "passive"))
    )
    (net (code "6118") (name "unconnected-(SV212-Pad24)") (class "Default")
      (node (ref "SV212") (pin "24") (pinfunction "24_24") (pintype "passive"))
    )
    (net (code "6119") (name "unconnected-(SV213-Pad1)") (class "Default")
      (node (ref "SV213") (pin "1") (pinfunction "1_1") (pintype "passive"))
    )
    (net (code "6120") (name "unconnected-(SV213-Pad2)") (class "Default")
      (node (ref "SV213") (pin "2") (pinfunction "2_2") (pintype "passive"))
    )
    (net (code "6121") (name "unconnected-(SV213-Pad3)") (class "Default")
      (node (ref "SV213") (pin "3") (pinfunction "3_3") (pintype "passive"))
    )
    (net (code "6122") (name "unconnected-(SV213-Pad4)") (class "Default")
      (node (ref "SV213") (pin "4") (pinfunction "4_4") (pintype "passive"))
    )
    (net (code "6123") (name "unconnected-(SV213-Pad5)") (class "Default")
      (node (ref "SV213") (pin "5") (pinfunction "5_5") (pintype "passive"))
    )
    (net (code "6124") (name "unconnected-(SV213-Pad6)") (class "Default")
      (node (ref "SV213") (pin "6") (pinfunction "6_6") (pintype "passive"))
    )
    (net (code "6125") (name "unconnected-(SV213-Pad7)") (class "Default")
      (node (ref "SV213") (pin "7") (pinfunction "7_7") (pintype "passive"))
    )
    (net (code "6126") (name "unconnected-(SV213-Pad8)") (class "Default")
      (node (ref "SV213") (pin "8") (pinfunction "8_8") (pintype "passive"))
    )
    (net (code "6127") (name "unconnected-(SV213-Pad9)") (class "Default")
      (node (ref "SV213") (pin "9") (pinfunction "9_9") (pintype "passive"))
    )
    (net (code "6128") (name "unconnected-(SV213-Pad10)") (class "Default")
      (node (ref "SV213") (pin "10") (pinfunction "10_10") (pintype "passive"))
    )
    (net (code "6129") (name "unconnected-(SV213-Pad11)") (class "Default")
      (node (ref "SV213") (pin "11") (pinfunction "11_11") (pintype "passive"))
    )
    (net (code "6130") (name "unconnected-(SV213-Pad12)") (class "Default")
      (node (ref "SV213") (pin "12") (pinfunction "12_12") (pintype "passive"))
    )
    (net (code "6131") (name "unconnected-(SV213-Pad13)") (class "Default")
      (node (ref "SV213") (pin "13") (pinfunction "13_13") (pintype "passive"))
    )
    (net (code "6132") (name "unconnected-(SV213-Pad14)") (class "Default")
      (node (ref "SV213") (pin "14") (pinfunction "14_14") (pintype "passive"))
    )
    (net (code "6133") (name "unconnected-(SV213-Pad15)") (class "Default")
      (node (ref "SV213") (pin "15") (pinfunction "15_15") (pintype "passive"))
    )
    (net (code "6134") (name "unconnected-(SV213-Pad16)") (class "Default")
      (node (ref "SV213") (pin "16") (pinfunction "16_16") (pintype "passive"))
    )
    (net (code "6135") (name "unconnected-(SV213-Pad17)") (class "Default")
      (node (ref "SV213") (pin "17") (pinfunction "17_17") (pintype "passive"))
    )
    (net (code "6136") (name "unconnected-(SV213-Pad18)") (class "Default")
      (node (ref "SV213") (pin "18") (pinfunction "18_18") (pintype "passive"))
    )
    (net (code "6137") (name "unconnected-(SV213-Pad19)") (class "Default")
      (node (ref "SV213") (pin "19") (pinfunction "19_19") (pintype "passive"))
    )
    (net (code "6138") (name "unconnected-(SV213-Pad20)") (class "Default")
      (node (ref "SV213") (pin "20") (pinfunction "20_20") (pintype "passive"))
    )
    (net (code "6139") (name "unconnected-(SV213-Pad21)") (class "Default")
      (node (ref "SV213") (pin "21") (pinfunction "21_21") (pintype "passive"))
    )
    (net (code "6140") (name "unconnected-(SV213-Pad22)") (class "Default")
      (node (ref "SV213") (pin "22") (pinfunction "22_22") (pintype "passive"))
    )
    (net (code "6141") (name "unconnected-(SV213-Pad23)") (class "Default")
      (node (ref "SV213") (pin "23") (pinfunction "23_23") (pintype "passive"))
    )
    (net (code "6142") (name "unconnected-(SV213-Pad24)") (class "Default")
      (node (ref "SV213") (pin "24") (pinfunction "24_24") (pintype "passive"))
    )
    (net (code "6143") (name "unconnected-(SV214-Pad1)") (class "Default")
      (node (ref "SV214") (pin "1") (pinfunction "1_1") (pintype "passive"))
    )
    (net (code "6144") (name "unconnected-(SV214-Pad2)") (class "Default")
      (node (ref "SV214") (pin "2") (pinfunction "2_2") (pintype "passive"))
    )
    (net (code "6145") (name "unconnected-(SV214-Pad3)") (class "Default")
      (node (ref "SV214") (pin "3") (pinfunction "3_3") (pintype "passive"))
    )
    (net (code "6146") (name "unconnected-(SV214-Pad4)") (class "Default")
      (node (ref "SV214") (pin "4") (pinfunction "4_4") (pintype "passive"))
    )
    (net (code "6147") (name "unconnected-(SV214-Pad5)") (class "Default")
      (node (ref "SV214") (pin "5") (pinfunction "5_5") (pintype "passive"))
    )
    (net (code "6148") (name "unconnected-(SV214-Pad6)") (class "Default")
      (node (ref "SV214") (pin "6") (pinfunction "6_6") (pintype "passive"))
    )
    (net (code "6149") (name "unconnected-(SV214-Pad7)") (class "Default")
      (node (ref "SV214") (pin "7") (pinfunction "7_7") (pintype "passive"))
    )
    (net (code "6150") (name "unconnected-(SV214-Pad8)") (class "Default")
      (node (ref "SV214") (pin "8") (pinfunction "8_8") (pintype "passive"))
    )
    (net (code "6151") (name "unconnected-(SV214-Pad9)") (class "Default")
      (node (ref "SV214") (pin "9") (pinfunction "9_9") (pintype "passive"))
    )
    (net (code "6152") (name "unconnected-(SV214-Pad10)") (class "Default")
      (node (ref "SV214") (pin "10") (pinfunction "10_10") (pintype "passive"))
    )
    (net (code "6153") (name "unconnected-(SV214-Pad11)") (class "Default")
      (node (ref "SV214") (pin "11") (pinfunction "11_11") (pintype "passive"))
    )
    (net (code "6154") (name "unconnected-(SV214-Pad12)") (class "Default")
      (node (ref "SV214") (pin "12") (pinfunction "12_12") (pintype "passive"))
    )
    (net (code "6155") (name "unconnected-(SV214-Pad13)") (class "Default")
      (node (ref "SV214") (pin "13") (pinfunction "13_13") (pintype "passive"))
    )
    (net (code "6156") (name "unconnected-(SV214-Pad14)") (class "Default")
      (node (ref "SV214") (pin "14") (pinfunction "14_14") (pintype "passive"))
    )
    (net (code "6157") (name "unconnected-(SV214-Pad15)") (class "Default")
      (node (ref "SV214") (pin "15") (pinfunction "15_15") (pintype "passive"))
    )
    (net (code "6158") (name "unconnected-(SV214-Pad16)") (class "Default")
      (node (ref "SV214") (pin "16") (pinfunction "16_16") (pintype "passive"))
    )
    (net (code "6159") (name "unconnected-(SV214-Pad17)") (class "Default")
      (node (ref "SV214") (pin "17") (pinfunction "17_17") (pintype "passive"))
    )
    (net (code "6160") (name "unconnected-(SV214-Pad18)") (class "Default")
      (node (ref "SV214") (pin "18") (pinfunction "18_18") (pintype "passive"))
    )
    (net (code "6161") (name "unconnected-(SV214-Pad19)") (class "Default")
      (node (ref "SV214") (pin "19") (pinfunction "19_19") (pintype "passive"))
    )
    (net (code "6162") (name "unconnected-(SV214-Pad20)") (class "Default")
      (node (ref "SV214") (pin "20") (pinfunction "20_20") (pintype "passive"))
    )
    (net (code "6163") (name "unconnected-(SV214-Pad21)") (class "Default")
      (node (ref "SV214") (pin "21") (pinfunction "21_21") (pintype "passive"))
    )
    (net (code "6164") (name "unconnected-(SV214-Pad22)") (class "Default")
      (node (ref "SV214") (pin "22") (pinfunction "22_22") (pintype "passive"))
    )
    (net (code "6165") (name "unconnected-(SV214-Pad23)") (class "Default")
      (node (ref "SV214") (pin "23") (pinfunction "23_23") (pintype "passive"))
    )
    (net (code "6166") (name "unconnected-(SV214-Pad24)") (class "Default")
      (node (ref "SV214") (pin "24") (pinfunction "24_24") (pintype "passive"))
    )
    (net (code "6167") (name "unconnected-(SV215-Pad1)") (class "Default")
      (node (ref "SV215") (pin "1") (pinfunction "1_1") (pintype "passive"))
    )
    (net (code "6168") (name "unconnected-(SV215-Pad2)") (class "Default")
      (node (ref "SV215") (pin "2") (pinfunction "2_2") (pintype "passive"))
    )
    (net (code "6169") (name "unconnected-(SV215-Pad3)") (class "Default")
      (node (ref "SV215") (pin "3") (pinfunction "3_3") (pintype "passive"))
    )
    (net (code "6170") (name "unconnected-(SV215-Pad4)") (class "Default")
      (node (ref "SV215") (pin "4") (pinfunction "4_4") (pintype "passive"))
    )
    (net (code "6171") (name "unconnected-(SV215-Pad5)") (class "Default")
      (node (ref "SV215") (pin "5") (pinfunction "5_5") (pintype "passive"))
    )
    (net (code "6172") (name "unconnected-(SV215-Pad6)") (class "Default")
      (node (ref "SV215") (pin "6") (pinfunction "6_6") (pintype "passive"))
    )
    (net (code "6173") (name "unconnected-(SV215-Pad7)") (class "Default")
      (node (ref "SV215") (pin "7") (pinfunction "7_7") (pintype "passive"))
    )
    (net (code "6174") (name "unconnected-(SV215-Pad8)") (class "Default")
      (node (ref "SV215") (pin "8") (pinfunction "8_8") (pintype "passive"))
    )
    (net (code "6175") (name "unconnected-(SV215-Pad9)") (class "Default")
      (node (ref "SV215") (pin "9") (pinfunction "9_9") (pintype "passive"))
    )
    (net (code "6176") (name "unconnected-(SV215-Pad10)") (class "Default")
      (node (ref "SV215") (pin "10") (pinfunction "10_10") (pintype "passive"))
    )
    (net (code "6177") (name "unconnected-(SV215-Pad11)") (class "Default")
      (node (ref "SV215") (pin "11") (pinfunction "11_11") (pintype "passive"))
    )
    (net (code "6178") (name "unconnected-(SV215-Pad12)") (class "Default")
      (node (ref "SV215") (pin "12") (pinfunction "12_12") (pintype "passive"))
    )
    (net (code "6179") (name "unconnected-(SV215-Pad13)") (class "Default")
      (node (ref "SV215") (pin "13") (pinfunction "13_13") (pintype "passive"))
    )
    (net (code "6180") (name "unconnected-(SV215-Pad14)") (class "Default")
      (node (ref "SV215") (pin "14") (pinfunction "14_14") (pintype "passive"))
    )
    (net (code "6181") (name "unconnected-(SV215-Pad15)") (class "Default")
      (node (ref "SV215") (pin "15") (pinfunction "15_15") (pintype "passive"))
    )
    (net (code "6182") (name "unconnected-(SV215-Pad16)") (class "Default")
      (node (ref "SV215") (pin "16") (pinfunction "16_16") (pintype "passive"))
    )
    (net (code "6183") (name "unconnected-(SV215-Pad17)") (class "Default")
      (node (ref "SV215") (pin "17") (pinfunction "17_17") (pintype "passive"))
    )
    (net (code "6184") (name "unconnected-(SV215-Pad18)") (class "Default")
      (node (ref "SV215") (pin "18") (pinfunction "18_18") (pintype "passive"))
    )
    (net (code "6185") (name "unconnected-(SV215-Pad19)") (class "Default")
      (node (ref "SV215") (pin "19") (pinfunction "19_19") (pintype "passive"))
    )
    (net (code "6186") (name "unconnected-(SV215-Pad20)") (class "Default")
      (node (ref "SV215") (pin "20") (pinfunction "20_20") (pintype "passive"))
    )
    (net (code "6187") (name "unconnected-(SV215-Pad21)") (class "Default")
      (node (ref "SV215") (pin "21") (pinfunction "21_21") (pintype "passive"))
    )
    (net (code "6188") (name "unconnected-(SV215-Pad22)") (class "Default")
      (node (ref "SV215") (pin "22") (pinfunction "22_22") (pintype "passive"))
    )
    (net (code "6189") (name "unconnected-(SV215-Pad23)") (class "Default")
      (node (ref "SV215") (pin "23") (pinfunction "23_23") (pintype "passive"))
    )
    (net (code "6190") (name "unconnected-(SV215-Pad24)") (class "Default")
      (node (ref "SV215") (pin "24") (pinfunction "24_24") (pintype "passive"))
    )
    (net (code "6191") (name "unconnected-(SV215-Pad25)") (class "Default")
      (node (ref "SV215") (pin "25") (pinfunction "25_25") (pintype "passive"))
    )
    (net (code "6192") (name "unconnected-(SV215-Pad26)") (class "Default")
      (node (ref "SV215") (pin "26") (pinfunction "26_26") (pintype "passive"))
    )
    (net (code "6193") (name "unconnected-(SV215-Pad27)") (class "Default")
      (node (ref "SV215") (pin "27") (pinfunction "27_27") (pintype "passive"))
    )
    (net (code "6194") (name "unconnected-(SV215-Pad28)") (class "Default")
      (node (ref "SV215") (pin "28") (pinfunction "28_28") (pintype "passive"))
    )
    (net (code "6195") (name "unconnected-(SV215-Pad29)") (class "Default")
      (node (ref "SV215") (pin "29") (pinfunction "29_29") (pintype "passive"))
    )
    (net (code "6196") (name "unconnected-(SV215-Pad30)") (class "Default")
      (node (ref "SV215") (pin "30") (pinfunction "30_30") (pintype "passive"))
    )
    (net (code "6197") (name "unconnected-(SV215-Pad31)") (class "Default")
      (node (ref "SV215") (pin "31") (pinfunction "31_31") (pintype "passive"))
    )
    (net (code "6198") (name "unconnected-(SV215-Pad32)") (class "Default")
      (node (ref "SV215") (pin "32") (pinfunction "32_32") (pintype "passive"))
    )
    (net (code "6199") (name "unconnected-(SV215-Pad33)") (class "Default")
      (node (ref "SV215") (pin "33") (pinfunction "33_33") (pintype "passive"))
    )
    (net (code "6200") (name "unconnected-(SV215-Pad34)") (class "Default")
      (node (ref "SV215") (pin "34") (pinfunction "34_34") (pintype "passive"))
    )
    (net (code "6201") (name "unconnected-(SV215-Pad35)") (class "Default")
      (node (ref "SV215") (pin "35") (pinfunction "35_35") (pintype "passive"))
    )
    (net (code "6202") (name "unconnected-(SV215-Pad36)") (class "Default")
      (node (ref "SV215") (pin "36") (pinfunction "36_36") (pintype "passive"))
    )
    (net (code "6203") (name "unconnected-(SV215-Pad37)") (class "Default")
      (node (ref "SV215") (pin "37") (pinfunction "37_37") (pintype "passive"))
    )
    (net (code "6204") (name "unconnected-(SV215-Pad38)") (class "Default")
      (node (ref "SV215") (pin "38") (pinfunction "38_38") (pintype "passive"))
    )
    (net (code "6205") (name "unconnected-(SV215-Pad39)") (class "Default")
      (node (ref "SV215") (pin "39") (pinfunction "39_39") (pintype "passive"))
    )
    (net (code "6206") (name "unconnected-(SV215-Pad40)") (class "Default")
      (node (ref "SV215") (pin "40") (pinfunction "40_40") (pintype "passive"))
    )
    (net (code "6207") (name "unconnected-(SV216-Pad1)") (class "Default")
      (node (ref "SV216") (pin "1") (pinfunction "1_1") (pintype "passive"))
    )
    (net (code "6208") (name "unconnected-(SV216-Pad2)") (class "Default")
      (node (ref "SV216") (pin "2") (pinfunction "2_2") (pintype "passive"))
    )
    (net (code "6209") (name "unconnected-(SV216-Pad3)") (class "Default")
      (node (ref "SV216") (pin "3") (pinfunction "3_3") (pintype "passive"))
    )
    (net (code "6210") (name "unconnected-(SV216-Pad4)") (class "Default")
      (node (ref "SV216") (pin "4") (pinfunction "4_4") (pintype "passive"))
    )
    (net (code "6211") (name "unconnected-(SV216-Pad5)") (class "Default")
      (node (ref "SV216") (pin "5") (pinfunction "5_5") (pintype "passive"))
    )
    (net (code "6212") (name "unconnected-(SV216-Pad6)") (class "Default")
      (node (ref "SV216") (pin "6") (pinfunction "6_6") (pintype "passive"))
    )
    (net (code "6213") (name "unconnected-(SV216-Pad7)") (class "Default")
      (node (ref "SV216") (pin "7") (pinfunction "7_7") (pintype "passive"))
    )
    (net (code "6214") (name "unconnected-(SV216-Pad8)") (class "Default")
      (node (ref "SV216") (pin "8") (pinfunction "8_8") (pintype "passive"))
    )
    (net (code "6215") (name "unconnected-(SV216-Pad9)") (class "Default")
      (node (ref "SV216") (pin "9") (pinfunction "9_9") (pintype "passive"))
    )
    (net (code "6216") (name "unconnected-(SV216-Pad10)") (class "Default")
      (node (ref "SV216") (pin "10") (pinfunction "10_10") (pintype "passive"))
    )
    (net (code "6217") (name "unconnected-(SV216-Pad11)") (class "Default")
      (node (ref "SV216") (pin "11") (pinfunction "11_11") (pintype "passive"))
    )
    (net (code "6218") (name "unconnected-(SV216-Pad12)") (class "Default")
      (node (ref "SV216") (pin "12") (pinfunction "12_12") (pintype "passive"))
    )
    (net (code "6219") (name "unconnected-(SV216-Pad13)") (class "Default")
      (node (ref "SV216") (pin "13") (pinfunction "13_13") (pintype "passive"))
    )
    (net (code "6220") (name "unconnected-(SV216-Pad14)") (class "Default")
      (node (ref "SV216") (pin "14") (pinfunction "14_14") (pintype "passive"))
    )
    (net (code "6221") (name "unconnected-(SV216-Pad15)") (class "Default")
      (node (ref "SV216") (pin "15") (pinfunction "15_15") (pintype "passive"))
    )
    (net (code "6222") (name "unconnected-(SV216-Pad16)") (class "Default")
      (node (ref "SV216") (pin "16") (pinfunction "16_16") (pintype "passive"))
    )
    (net (code "6223") (name "unconnected-(SV216-Pad17)") (class "Default")
      (node (ref "SV216") (pin "17") (pinfunction "17_17") (pintype "passive"))
    )
    (net (code "6224") (name "unconnected-(SV216-Pad18)") (class "Default")
      (node (ref "SV216") (pin "18") (pinfunction "18_18") (pintype "passive"))
    )
    (net (code "6225") (name "unconnected-(SV216-Pad19)") (class "Default")
      (node (ref "SV216") (pin "19") (pinfunction "19_19") (pintype "passive"))
    )
    (net (code "6226") (name "unconnected-(SV216-Pad20)") (class "Default")
      (node (ref "SV216") (pin "20") (pinfunction "20_20") (pintype "passive"))
    )
    (net (code "6227") (name "unconnected-(SV216-Pad21)") (class "Default")
      (node (ref "SV216") (pin "21") (pinfunction "21_21") (pintype "passive"))
    )
    (net (code "6228") (name "unconnected-(SV216-Pad22)") (class "Default")
      (node (ref "SV216") (pin "22") (pinfunction "22_22") (pintype "passive"))
    )
    (net (code "6229") (name "unconnected-(SV216-Pad23)") (class "Default")
      (node (ref "SV216") (pin "23") (pinfunction "23_23") (pintype "passive"))
    )
    (net (code "6230") (name "unconnected-(SV216-Pad24)") (class "Default")
      (node (ref "SV216") (pin "24") (pinfunction "24_24") (pintype "passive"))
    )
    (net (code "6231") (name "unconnected-(SV216-Pad25)") (class "Default")
      (node (ref "SV216") (pin "25") (pinfunction "25_25") (pintype "passive"))
    )
    (net (code "6232") (name "unconnected-(SV216-Pad26)") (class "Default")
      (node (ref "SV216") (pin "26") (pinfunction "26_26") (pintype "passive"))
    )
    (net (code "6233") (name "unconnected-(SV216-Pad27)") (class "Default")
      (node (ref "SV216") (pin "27") (pinfunction "27_27") (pintype "passive"))
    )
    (net (code "6234") (name "unconnected-(SV216-Pad28)") (class "Default")
      (node (ref "SV216") (pin "28") (pinfunction "28_28") (pintype "passive"))
    )
    (net (code "6235") (name "unconnected-(SV216-Pad29)") (class "Default")
      (node (ref "SV216") (pin "29") (pinfunction "29_29") (pintype "passive"))
    )
    (net (code "6236") (name "unconnected-(SV216-Pad30)") (class "Default")
      (node (ref "SV216") (pin "30") (pinfunction "30_30") (pintype "passive"))
    )
    (net (code "6237") (name "unconnected-(SV216-Pad31)") (class "Default")
      (node (ref "SV216") (pin "31") (pinfunction "31_31") (pintype "passive"))
    )
    (net (code "6238") (name "unconnected-(SV216-Pad32)") (class "Default")
      (node (ref "SV216") (pin "32") (pinfunction "32_32") (pintype "passive"))
    )
    (net (code "6239") (name "unconnected-(SV216-Pad33)") (class "Default")
      (node (ref "SV216") (pin "33") (pinfunction "33_33") (pintype "passive"))
    )
    (net (code "6240") (name "unconnected-(SV216-Pad34)") (class "Default")
      (node (ref "SV216") (pin "34") (pinfunction "34_34") (pintype "passive"))
    )
    (net (code "6241") (name "unconnected-(SV216-Pad35)") (class "Default")
      (node (ref "SV216") (pin "35") (pinfunction "35_35") (pintype "passive"))
    )
    (net (code "6242") (name "unconnected-(SV216-Pad36)") (class "Default")
      (node (ref "SV216") (pin "36") (pinfunction "36_36") (pintype "passive"))
    )
    (net (code "6243") (name "unconnected-(SV216-Pad37)") (class "Default")
      (node (ref "SV216") (pin "37") (pinfunction "37_37") (pintype "passive"))
    )
    (net (code "6244") (name "unconnected-(SV216-Pad38)") (class "Default")
      (node (ref "SV216") (pin "38") (pinfunction "38_38") (pintype "passive"))
    )
    (net (code "6245") (name "unconnected-(SV216-Pad39)") (class "Default")
      (node (ref "SV216") (pin "39") (pinfunction "39_39") (pintype "passive"))
    )
    (net (code "6246") (name "unconnected-(SV216-Pad40)") (class "Default")
      (node (ref "SV216") (pin "40") (pinfunction "40_40") (pintype "passive"))
    )
    (net (code "6247") (name "unconnected-(SV217-Pad1)") (class "Default")
      (node (ref "SV217") (pin "1") (pinfunction "1_1") (pintype "passive"))
    )
    (net (code "6248") (name "unconnected-(SV217-Pad2)") (class "Default")
      (node (ref "SV217") (pin "2") (pinfunction "2_2") (pintype "passive"))
    )
    (net (code "6249") (name "unconnected-(SV217-Pad3)") (class "Default")
      (node (ref "SV217") (pin "3") (pinfunction "3_3") (pintype "passive"))
    )
    (net (code "6250") (name "unconnected-(SV217-Pad4)") (class "Default")
      (node (ref "SV217") (pin "4") (pinfunction "4_4") (pintype "passive"))
    )
    (net (code "6251") (name "unconnected-(SV217-Pad5)") (class "Default")
      (node (ref "SV217") (pin "5") (pinfunction "5_5") (pintype "passive"))
    )
    (net (code "6252") (name "unconnected-(SV217-Pad6)") (class "Default")
      (node (ref "SV217") (pin "6") (pinfunction "6_6") (pintype "passive"))
    )
    (net (code "6253") (name "unconnected-(SV217-Pad7)") (class "Default")
      (node (ref "SV217") (pin "7") (pinfunction "7_7") (pintype "passive"))
    )
    (net (code "6254") (name "unconnected-(SV217-Pad8)") (class "Default")
      (node (ref "SV217") (pin "8") (pinfunction "8_8") (pintype "passive"))
    )
    (net (code "6255") (name "unconnected-(SV217-Pad9)") (class "Default")
      (node (ref "SV217") (pin "9") (pinfunction "9_9") (pintype "passive"))
    )
    (net (code "6256") (name "unconnected-(SV217-Pad10)") (class "Default")
      (node (ref "SV217") (pin "10") (pinfunction "10_10") (pintype "passive"))
    )
    (net (code "6257") (name "unconnected-(SV217-Pad11)") (class "Default")
      (node (ref "SV217") (pin "11") (pinfunction "11_11") (pintype "passive"))
    )
    (net (code "6258") (name "unconnected-(SV217-Pad12)") (class "Default")
      (node (ref "SV217") (pin "12") (pinfunction "12_12") (pintype "passive"))
    )
    (net (code "6259") (name "unconnected-(SV217-Pad13)") (class "Default")
      (node (ref "SV217") (pin "13") (pinfunction "13_13") (pintype "passive"))
    )
    (net (code "6260") (name "unconnected-(SV217-Pad14)") (class "Default")
      (node (ref "SV217") (pin "14") (pinfunction "14_14") (pintype "passive"))
    )
    (net (code "6261") (name "unconnected-(SV217-Pad15)") (class "Default")
      (node (ref "SV217") (pin "15") (pinfunction "15_15") (pintype "passive"))
    )
    (net (code "6262") (name "unconnected-(SV217-Pad16)") (class "Default")
      (node (ref "SV217") (pin "16") (pinfunction "16_16") (pintype "passive"))
    )
    (net (code "6263") (name "unconnected-(SV217-Pad17)") (class "Default")
      (node (ref "SV217") (pin "17") (pinfunction "17_17") (pintype "passive"))
    )
    (net (code "6264") (name "unconnected-(SV217-Pad18)") (class "Default")
      (node (ref "SV217") (pin "18") (pinfunction "18_18") (pintype "passive"))
    )
    (net (code "6265") (name "unconnected-(SV217-Pad19)") (class "Default")
      (node (ref "SV217") (pin "19") (pinfunction "19_19") (pintype "passive"))
    )
    (net (code "6266") (name "unconnected-(SV217-Pad20)") (class "Default")
      (node (ref "SV217") (pin "20") (pinfunction "20_20") (pintype "passive"))
    )
    (net (code "6267") (name "unconnected-(SV217-Pad21)") (class "Default")
      (node (ref "SV217") (pin "21") (pinfunction "21_21") (pintype "passive"))
    )
    (net (code "6268") (name "unconnected-(SV217-Pad22)") (class "Default")
      (node (ref "SV217") (pin "22") (pinfunction "22_22") (pintype "passive"))
    )
    (net (code "6269") (name "unconnected-(SV217-Pad23)") (class "Default")
      (node (ref "SV217") (pin "23") (pinfunction "23_23") (pintype "passive"))
    )
    (net (code "6270") (name "unconnected-(SV217-Pad24)") (class "Default")
      (node (ref "SV217") (pin "24") (pinfunction "24_24") (pintype "passive"))
    )
    (net (code "6271") (name "unconnected-(SV217-Pad25)") (class "Default")
      (node (ref "SV217") (pin "25") (pinfunction "25_25") (pintype "passive"))
    )
    (net (code "6272") (name "unconnected-(SV217-Pad26)") (class "Default")
      (node (ref "SV217") (pin "26") (pinfunction "26_26") (pintype "passive"))
    )
    (net (code "6273") (name "unconnected-(SV217-Pad27)") (class "Default")
      (node (ref "SV217") (pin "27") (pinfunction "27_27") (pintype "passive"))
    )
    (net (code "6274") (name "unconnected-(SV217-Pad28)") (class "Default")
      (node (ref "SV217") (pin "28") (pinfunction "28_28") (pintype "passive"))
    )
    (net (code "6275") (name "unconnected-(SV217-Pad29)") (class "Default")
      (node (ref "SV217") (pin "29") (pinfunction "29_29") (pintype "passive"))
    )
    (net (code "6276") (name "unconnected-(SV217-Pad30)") (class "Default")
      (node (ref "SV217") (pin "30") (pinfunction "30_30") (pintype "passive"))
    )
    (net (code "6277") (name "unconnected-(SV217-Pad31)") (class "Default")
      (node (ref "SV217") (pin "31") (pinfunction "31_31") (pintype "passive"))
    )
    (net (code "6278") (name "unconnected-(SV217-Pad32)") (class "Default")
      (node (ref "SV217") (pin "32") (pinfunction "32_32") (pintype "passive"))
    )
    (net (code "6279") (name "unconnected-(SV217-Pad33)") (class "Default")
      (node (ref "SV217") (pin "33") (pinfunction "33_33") (pintype "passive"))
    )
    (net (code "6280") (name "unconnected-(SV217-Pad34)") (class "Default")
      (node (ref "SV217") (pin "34") (pinfunction "34_34") (pintype "passive"))
    )
    (net (code "6281") (name "unconnected-(SV217-Pad35)") (class "Default")
      (node (ref "SV217") (pin "35") (pinfunction "35_35") (pintype "passive"))
    )
    (net (code "6282") (name "unconnected-(SV217-Pad36)") (class "Default")
      (node (ref "SV217") (pin "36") (pinfunction "36_36") (pintype "passive"))
    )
    (net (code "6283") (name "unconnected-(SV217-Pad37)") (class "Default")
      (node (ref "SV217") (pin "37") (pinfunction "37_37") (pintype "passive"))
    )
    (net (code "6284") (name "unconnected-(SV217-Pad38)") (class "Default")
      (node (ref "SV217") (pin "38") (pinfunction "38_38") (pintype "passive"))
    )
    (net (code "6285") (name "unconnected-(SV217-Pad39)") (class "Default")
      (node (ref "SV217") (pin "39") (pinfunction "39_39") (pintype "passive"))
    )
    (net (code "6286") (name "unconnected-(SV217-Pad40)") (class "Default")
      (node (ref "SV217") (pin "40") (pinfunction "40_40") (pintype "passive"))
    )
    (net (code "6287") (name "unconnected-(SV218-Pad1)") (class "Default")
      (node (ref "SV218") (pin "1") (pinfunction "1_1") (pintype "passive"))
    )
    (net (code "6288") (name "unconnected-(SV218-Pad2)") (class "Default")
      (node (ref "SV218") (pin "2") (pinfunction "2_2") (pintype "passive"))
    )
    (net (code "6289") (name "unconnected-(SV218-Pad3)") (class "Default")
      (node (ref "SV218") (pin "3") (pinfunction "3_3") (pintype "passive"))
    )
    (net (code "6290") (name "unconnected-(SV218-Pad4)") (class "Default")
      (node (ref "SV218") (pin "4") (pinfunction "4_4") (pintype "passive"))
    )
    (net (code "6291") (name "unconnected-(SV218-Pad5)") (class "Default")
      (node (ref "SV218") (pin "5") (pinfunction "5_5") (pintype "passive"))
    )
    (net (code "6292") (name "unconnected-(SV218-Pad6)") (class "Default")
      (node (ref "SV218") (pin "6") (pinfunction "6_6") (pintype "passive"))
    )
    (net (code "6293") (name "unconnected-(SV218-Pad7)") (class "Default")
      (node (ref "SV218") (pin "7") (pinfunction "7_7") (pintype "passive"))
    )
    (net (code "6294") (name "unconnected-(SV218-Pad8)") (class "Default")
      (node (ref "SV218") (pin "8") (pinfunction "8_8") (pintype "passive"))
    )
    (net (code "6295") (name "unconnected-(SV218-Pad9)") (class "Default")
      (node (ref "SV218") (pin "9") (pinfunction "9_9") (pintype "passive"))
    )
    (net (code "6296") (name "unconnected-(SV218-Pad10)") (class "Default")
      (node (ref "SV218") (pin "10") (pinfunction "10_10") (pintype "passive"))
    )
    (net (code "6297") (name "unconnected-(SV218-Pad11)") (class "Default")
      (node (ref "SV218") (pin "11") (pinfunction "11_11") (pintype "passive"))
    )
    (net (code "6298") (name "unconnected-(SV218-Pad12)") (class "Default")
      (node (ref "SV218") (pin "12") (pinfunction "12_12") (pintype "passive"))
    )
    (net (code "6299") (name "unconnected-(SV218-Pad13)") (class "Default")
      (node (ref "SV218") (pin "13") (pinfunction "13_13") (pintype "passive"))
    )
    (net (code "6300") (name "unconnected-(SV218-Pad14)") (class "Default")
      (node (ref "SV218") (pin "14") (pinfunction "14_14") (pintype "passive"))
    )
    (net (code "6301") (name "unconnected-(SV218-Pad15)") (class "Default")
      (node (ref "SV218") (pin "15") (pinfunction "15_15") (pintype "passive"))
    )
    (net (code "6302") (name "unconnected-(SV218-Pad16)") (class "Default")
      (node (ref "SV218") (pin "16") (pinfunction "16_16") (pintype "passive"))
    )
    (net (code "6303") (name "unconnected-(SV218-Pad17)") (class "Default")
      (node (ref "SV218") (pin "17") (pinfunction "17_17") (pintype "passive"))
    )
    (net (code "6304") (name "unconnected-(SV218-Pad18)") (class "Default")
      (node (ref "SV218") (pin "18") (pinfunction "18_18") (pintype "passive"))
    )
    (net (code "6305") (name "unconnected-(SV218-Pad19)") (class "Default")
      (node (ref "SV218") (pin "19") (pinfunction "19_19") (pintype "passive"))
    )
    (net (code "6306") (name "unconnected-(SV218-Pad20)") (class "Default")
      (node (ref "SV218") (pin "20") (pinfunction "20_20") (pintype "passive"))
    )
    (net (code "6307") (name "unconnected-(SV218-Pad21)") (class "Default")
      (node (ref "SV218") (pin "21") (pinfunction "21_21") (pintype "passive"))
    )
    (net (code "6308") (name "unconnected-(SV218-Pad22)") (class "Default")
      (node (ref "SV218") (pin "22") (pinfunction "22_22") (pintype "passive"))
    )
    (net (code "6309") (name "unconnected-(SV218-Pad23)") (class "Default")
      (node (ref "SV218") (pin "23") (pinfunction "23_23") (pintype "passive"))
    )
    (net (code "6310") (name "unconnected-(SV218-Pad24)") (class "Default")
      (node (ref "SV218") (pin "24") (pinfunction "24_24") (pintype "passive"))
    )
    (net (code "6311") (name "unconnected-(SV218-Pad25)") (class "Default")
      (node (ref "SV218") (pin "25") (pinfunction "25_25") (pintype "passive"))
    )
    (net (code "6312") (name "unconnected-(SV218-Pad26)") (class "Default")
      (node (ref "SV218") (pin "26") (pinfunction "26_26") (pintype "passive"))
    )
    (net (code "6313") (name "unconnected-(SV218-Pad27)") (class "Default")
      (node (ref "SV218") (pin "27") (pinfunction "27_27") (pintype "passive"))
    )
    (net (code "6314") (name "unconnected-(SV218-Pad28)") (class "Default")
      (node (ref "SV218") (pin "28") (pinfunction "28_28") (pintype "passive"))
    )
    (net (code "6315") (name "unconnected-(SV218-Pad29)") (class "Default")
      (node (ref "SV218") (pin "29") (pinfunction "29_29") (pintype "passive"))
    )
    (net (code "6316") (name "unconnected-(SV218-Pad30)") (class "Default")
      (node (ref "SV218") (pin "30") (pinfunction "30_30") (pintype "passive"))
    )
    (net (code "6317") (name "unconnected-(SV218-Pad31)") (class "Default")
      (node (ref "SV218") (pin "31") (pinfunction "31_31") (pintype "passive"))
    )
    (net (code "6318") (name "unconnected-(SV218-Pad32)") (class "Default")
      (node (ref "SV218") (pin "32") (pinfunction "32_32") (pintype "passive"))
    )
    (net (code "6319") (name "unconnected-(SV218-Pad33)") (class "Default")
      (node (ref "SV218") (pin "33") (pinfunction "33_33") (pintype "passive"))
    )
    (net (code "6320") (name "unconnected-(SV218-Pad34)") (class "Default")
      (node (ref "SV218") (pin "34") (pinfunction "34_34") (pintype "passive"))
    )
    (net (code "6321") (name "unconnected-(SV218-Pad35)") (class "Default")
      (node (ref "SV218") (pin "35") (pinfunction "35_35") (pintype "passive"))
    )
    (net (code "6322") (name "unconnected-(SV218-Pad36)") (class "Default")
      (node (ref "SV218") (pin "36") (pinfunction "36_36") (pintype "passive"))
    )
    (net (code "6323") (name "unconnected-(SV218-Pad37)") (class "Default")
      (node (ref "SV218") (pin "37") (pinfunction "37_37") (pintype "passive"))
    )
    (net (code "6324") (name "unconnected-(SV218-Pad38)") (class "Default")
      (node (ref "SV218") (pin "38") (pinfunction "38_38") (pintype "passive"))
    )
    (net (code "6325") (name "unconnected-(SV218-Pad39)") (class "Default")
      (node (ref "SV218") (pin "39") (pinfunction "39_39") (pintype "passive"))
    )
    (net (code "6326") (name "unconnected-(SV218-Pad40)") (class "Default")
      (node (ref "SV218") (pin "40") (pinfunction "40_40") (pintype "passive"))
    )
    (net (code "6327") (name "unconnected-(SV219-Pad1)") (class "Default")
      (node (ref "SV219") (pin "1") (pinfunction "1_1") (pintype "passive"))
    )
    (net (code "6328") (name "unconnected-(SV219-Pad2)") (class "Default")
      (node (ref "SV219") (pin "2") (pinfunction "2_2") (pintype "passive"))
    )
    (net (code "6329") (name "unconnected-(SV219-Pad3)") (class "Default")
      (node (ref "SV219") (pin "3") (pinfunction "3_3") (pintype "passive"))
    )
    (net (code "6330") (name "unconnected-(SV219-Pad4)") (class "Default")
      (node (ref "SV219") (pin "4") (pinfunction "4_4") (pintype "passive"))
    )
    (net (code "6331") (name "unconnected-(SV219-Pad5)") (class "Default")
      (node (ref "SV219") (pin "5") (pinfunction "5_5") (pintype "passive"))
    )
    (net (code "6332") (name "unconnected-(SV219-Pad6)") (class "Default")
      (node (ref "SV219") (pin "6") (pinfunction "6_6") (pintype "passive"))
    )
    (net (code "6333") (name "unconnected-(SV219-Pad7)") (class "Default")
      (node (ref "SV219") (pin "7") (pinfunction "7_7") (pintype "passive"))
    )
    (net (code "6334") (name "unconnected-(SV219-Pad8)") (class "Default")
      (node (ref "SV219") (pin "8") (pinfunction "8_8") (pintype "passive"))
    )
    (net (code "6335") (name "unconnected-(SV219-Pad9)") (class "Default")
      (node (ref "SV219") (pin "9") (pinfunction "9_9") (pintype "passive"))
    )
    (net (code "6336") (name "unconnected-(SV219-Pad10)") (class "Default")
      (node (ref "SV219") (pin "10") (pinfunction "10_10") (pintype "passive"))
    )
    (net (code "6337") (name "unconnected-(SV219-Pad11)") (class "Default")
      (node (ref "SV219") (pin "11") (pinfunction "11_11") (pintype "passive"))
    )
    (net (code "6338") (name "unconnected-(SV219-Pad12)") (class "Default")
      (node (ref "SV219") (pin "12") (pinfunction "12_12") (pintype "passive"))
    )
    (net (code "6339") (name "unconnected-(SV219-Pad13)") (class "Default")
      (node (ref "SV219") (pin "13") (pinfunction "13_13") (pintype "passive"))
    )
    (net (code "6340") (name "unconnected-(SV219-Pad14)") (class "Default")
      (node (ref "SV219") (pin "14") (pinfunction "14_14") (pintype "passive"))
    )
    (net (code "6341") (name "unconnected-(SV219-Pad15)") (class "Default")
      (node (ref "SV219") (pin "15") (pinfunction "15_15") (pintype "passive"))
    )
    (net (code "6342") (name "unconnected-(SV219-Pad16)") (class "Default")
      (node (ref "SV219") (pin "16") (pinfunction "16_16") (pintype "passive"))
    )
    (net (code "6343") (name "unconnected-(SV219-Pad17)") (class "Default")
      (node (ref "SV219") (pin "17") (pinfunction "17_17") (pintype "passive"))
    )
    (net (code "6344") (name "unconnected-(SV219-Pad18)") (class "Default")
      (node (ref "SV219") (pin "18") (pinfunction "18_18") (pintype "passive"))
    )
    (net (code "6345") (name "unconnected-(SV219-Pad19)") (class "Default")
      (node (ref "SV219") (pin "19") (pinfunction "19_19") (pintype "passive"))
    )
    (net (code "6346") (name "unconnected-(SV219-Pad20)") (class "Default")
      (node (ref "SV219") (pin "20") (pinfunction "20_20") (pintype "passive"))
    )
    (net (code "6347") (name "unconnected-(SV219-Pad21)") (class "Default")
      (node (ref "SV219") (pin "21") (pinfunction "21_21") (pintype "passive"))
    )
    (net (code "6348") (name "unconnected-(SV219-Pad22)") (class "Default")
      (node (ref "SV219") (pin "22") (pinfunction "22_22") (pintype "passive"))
    )
    (net (code "6349") (name "unconnected-(SV219-Pad23)") (class "Default")
      (node (ref "SV219") (pin "23") (pinfunction "23_23") (pintype "passive"))
    )
    (net (code "6350") (name "unconnected-(SV219-Pad24)") (class "Default")
      (node (ref "SV219") (pin "24") (pinfunction "24_24") (pintype "passive"))
    )
    (net (code "6351") (name "unconnected-(SV220-Pad1)") (class "Default")
      (node (ref "SV220") (pin "1") (pinfunction "1_1") (pintype "passive"))
    )
    (net (code "6352") (name "unconnected-(SV220-Pad2)") (class "Default")
      (node (ref "SV220") (pin "2") (pinfunction "2_2") (pintype "passive"))
    )
    (net (code "6353") (name "unconnected-(SV220-Pad3)") (class "Default")
      (node (ref "SV220") (pin "3") (pinfunction "3_3") (pintype "passive"))
    )
    (net (code "6354") (name "unconnected-(SV220-Pad4)") (class "Default")
      (node (ref "SV220") (pin "4") (pinfunction "4_4") (pintype "passive"))
    )
    (net (code "6355") (name "unconnected-(SV220-Pad5)") (class "Default")
      (node (ref "SV220") (pin "5") (pinfunction "5_5") (pintype "passive"))
    )
    (net (code "6356") (name "unconnected-(SV220-Pad6)") (class "Default")
      (node (ref "SV220") (pin "6") (pinfunction "6_6") (pintype "passive"))
    )
    (net (code "6357") (name "unconnected-(SV220-Pad7)") (class "Default")
      (node (ref "SV220") (pin "7") (pinfunction "7_7") (pintype "passive"))
    )
    (net (code "6358") (name "unconnected-(SV220-Pad8)") (class "Default")
      (node (ref "SV220") (pin "8") (pinfunction "8_8") (pintype "passive"))
    )
    (net (code "6359") (name "unconnected-(SV220-Pad9)") (class "Default")
      (node (ref "SV220") (pin "9") (pinfunction "9_9") (pintype "passive"))
    )
    (net (code "6360") (name "unconnected-(SV220-Pad10)") (class "Default")
      (node (ref "SV220") (pin "10") (pinfunction "10_10") (pintype "passive"))
    )
    (net (code "6361") (name "unconnected-(SV220-Pad11)") (class "Default")
      (node (ref "SV220") (pin "11") (pinfunction "11_11") (pintype "passive"))
    )
    (net (code "6362") (name "unconnected-(SV220-Pad12)") (class "Default")
      (node (ref "SV220") (pin "12") (pinfunction "12_12") (pintype "passive"))
    )
    (net (code "6363") (name "unconnected-(SV220-Pad13)") (class "Default")
      (node (ref "SV220") (pin "13") (pinfunction "13_13") (pintype "passive"))
    )
    (net (code "6364") (name "unconnected-(SV220-Pad14)") (class "Default")
      (node (ref "SV220") (pin "14") (pinfunction "14_14") (pintype "passive"))
    )
    (net (code "6365") (name "unconnected-(SV220-Pad15)") (class "Default")
      (node (ref "SV220") (pin "15") (pinfunction "15_15") (pintype "passive"))
    )
    (net (code "6366") (name "unconnected-(SV220-Pad16)") (class "Default")
      (node (ref "SV220") (pin "16") (pinfunction "16_16") (pintype "passive"))
    )
    (net (code "6367") (name "unconnected-(SV220-Pad17)") (class "Default")
      (node (ref "SV220") (pin "17") (pinfunction "17_17") (pintype "passive"))
    )
    (net (code "6368") (name "unconnected-(SV220-Pad18)") (class "Default")
      (node (ref "SV220") (pin "18") (pinfunction "18_18") (pintype "passive"))
    )
    (net (code "6369") (name "unconnected-(SV220-Pad19)") (class "Default")
      (node (ref "SV220") (pin "19") (pinfunction "19_19") (pintype "passive"))
    )
    (net (code "6370") (name "unconnected-(SV220-Pad20)") (class "Default")
      (node (ref "SV220") (pin "20") (pinfunction "20_20") (pintype "passive"))
    )
    (net (code "6371") (name "unconnected-(SV220-Pad21)") (class "Default")
      (node (ref "SV220") (pin "21") (pinfunction "21_21") (pintype "passive"))
    )
    (net (code "6372") (name "unconnected-(SV220-Pad22)") (class "Default")
      (node (ref "SV220") (pin "22") (pinfunction "22_22") (pintype "passive"))
    )
    (net (code "6373") (name "unconnected-(SV220-Pad23)") (class "Default")
      (node (ref "SV220") (pin "23") (pinfunction "23_23") (pintype "passive"))
    )
    (net (code "6374") (name "unconnected-(SV220-Pad24)") (class "Default")
      (node (ref "SV220") (pin "24") (pinfunction "24_24") (pintype "passive"))
    )
    (net (code "6375") (name "unconnected-(SV221-Pad1)") (class "Default")
      (node (ref "SV221") (pin "1") (pinfunction "1_1") (pintype "passive"))
    )
    (net (code "6376") (name "unconnected-(SV221-Pad2)") (class "Default")
      (node (ref "SV221") (pin "2") (pinfunction "2_2") (pintype "passive"))
    )
    (net (code "6377") (name "unconnected-(SV221-Pad3)") (class "Default")
      (node (ref "SV221") (pin "3") (pinfunction "3_3") (pintype "passive"))
    )
    (net (code "6378") (name "unconnected-(SV221-Pad4)") (class "Default")
      (node (ref "SV221") (pin "4") (pinfunction "4_4") (pintype "passive"))
    )
    (net (code "6379") (name "unconnected-(SV221-Pad5)") (class "Default")
      (node (ref "SV221") (pin "5") (pinfunction "5_5") (pintype "passive"))
    )
    (net (code "6380") (name "unconnected-(SV221-Pad6)") (class "Default")
      (node (ref "SV221") (pin "6") (pinfunction "6_6") (pintype "passive"))
    )
    (net (code "6381") (name "unconnected-(SV221-Pad7)") (class "Default")
      (node (ref "SV221") (pin "7") (pinfunction "7_7") (pintype "passive"))
    )
    (net (code "6382") (name "unconnected-(SV221-Pad8)") (class "Default")
      (node (ref "SV221") (pin "8") (pinfunction "8_8") (pintype "passive"))
    )
    (net (code "6383") (name "unconnected-(SV221-Pad9)") (class "Default")
      (node (ref "SV221") (pin "9") (pinfunction "9_9") (pintype "passive"))
    )
    (net (code "6384") (name "unconnected-(SV221-Pad10)") (class "Default")
      (node (ref "SV221") (pin "10") (pinfunction "10_10") (pintype "passive"))
    )
    (net (code "6385") (name "unconnected-(SV221-Pad11)") (class "Default")
      (node (ref "SV221") (pin "11") (pinfunction "11_11") (pintype "passive"))
    )
    (net (code "6386") (name "unconnected-(SV221-Pad12)") (class "Default")
      (node (ref "SV221") (pin "12") (pinfunction "12_12") (pintype "passive"))
    )
    (net (code "6387") (name "unconnected-(SV221-Pad13)") (class "Default")
      (node (ref "SV221") (pin "13") (pinfunction "13_13") (pintype "passive"))
    )
    (net (code "6388") (name "unconnected-(SV221-Pad14)") (class "Default")
      (node (ref "SV221") (pin "14") (pinfunction "14_14") (pintype "passive"))
    )
    (net (code "6389") (name "unconnected-(SV221-Pad15)") (class "Default")
      (node (ref "SV221") (pin "15") (pinfunction "15_15") (pintype "passive"))
    )
    (net (code "6390") (name "unconnected-(SV221-Pad16)") (class "Default")
      (node (ref "SV221") (pin "16") (pinfunction "16_16") (pintype "passive"))
    )
    (net (code "6391") (name "unconnected-(SV221-Pad17)") (class "Default")
      (node (ref "SV221") (pin "17") (pinfunction "17_17") (pintype "passive"))
    )
    (net (code "6392") (name "unconnected-(SV221-Pad18)") (class "Default")
      (node (ref "SV221") (pin "18") (pinfunction "18_18") (pintype "passive"))
    )
    (net (code "6393") (name "unconnected-(SV221-Pad19)") (class "Default")
      (node (ref "SV221") (pin "19") (pinfunction "19_19") (pintype "passive"))
    )
    (net (code "6394") (name "unconnected-(SV221-Pad20)") (class "Default")
      (node (ref "SV221") (pin "20") (pinfunction "20_20") (pintype "passive"))
    )
    (net (code "6395") (name "unconnected-(SV221-Pad21)") (class "Default")
      (node (ref "SV221") (pin "21") (pinfunction "21_21") (pintype "passive"))
    )
    (net (code "6396") (name "unconnected-(SV221-Pad22)") (class "Default")
      (node (ref "SV221") (pin "22") (pinfunction "22_22") (pintype "passive"))
    )
    (net (code "6397") (name "unconnected-(SV221-Pad23)") (class "Default")
      (node (ref "SV221") (pin "23") (pinfunction "23_23") (pintype "passive"))
    )
    (net (code "6398") (name "unconnected-(SV221-Pad24)") (class "Default")
      (node (ref "SV221") (pin "24") (pinfunction "24_24") (pintype "passive"))
    )
    (net (code "6399") (name "unconnected-(SV222-Pad1)") (class "Default")
      (node (ref "SV222") (pin "1") (pinfunction "1_1") (pintype "passive"))
    )
    (net (code "6400") (name "unconnected-(SV222-Pad2)") (class "Default")
      (node (ref "SV222") (pin "2") (pinfunction "2_2") (pintype "passive"))
    )
    (net (code "6401") (name "unconnected-(SV222-Pad3)") (class "Default")
      (node (ref "SV222") (pin "3") (pinfunction "3_3") (pintype "passive"))
    )
    (net (code "6402") (name "unconnected-(SV222-Pad4)") (class "Default")
      (node (ref "SV222") (pin "4") (pinfunction "4_4") (pintype "passive"))
    )
    (net (code "6403") (name "unconnected-(SV222-Pad5)") (class "Default")
      (node (ref "SV222") (pin "5") (pinfunction "5_5") (pintype "passive"))
    )
    (net (code "6404") (name "unconnected-(SV222-Pad6)") (class "Default")
      (node (ref "SV222") (pin "6") (pinfunction "6_6") (pintype "passive"))
    )
    (net (code "6405") (name "unconnected-(SV222-Pad7)") (class "Default")
      (node (ref "SV222") (pin "7") (pinfunction "7_7") (pintype "passive"))
    )
    (net (code "6406") (name "unconnected-(SV222-Pad8)") (class "Default")
      (node (ref "SV222") (pin "8") (pinfunction "8_8") (pintype "passive"))
    )
    (net (code "6407") (name "unconnected-(SV222-Pad9)") (class "Default")
      (node (ref "SV222") (pin "9") (pinfunction "9_9") (pintype "passive"))
    )
    (net (code "6408") (name "unconnected-(SV222-Pad10)") (class "Default")
      (node (ref "SV222") (pin "10") (pinfunction "10_10") (pintype "passive"))
    )
    (net (code "6409") (name "unconnected-(SV222-Pad11)") (class "Default")
      (node (ref "SV222") (pin "11") (pinfunction "11_11") (pintype "passive"))
    )
    (net (code "6410") (name "unconnected-(SV222-Pad12)") (class "Default")
      (node (ref "SV222") (pin "12") (pinfunction "12_12") (pintype "passive"))
    )
    (net (code "6411") (name "unconnected-(SV222-Pad13)") (class "Default")
      (node (ref "SV222") (pin "13") (pinfunction "13_13") (pintype "passive"))
    )
    (net (code "6412") (name "unconnected-(SV222-Pad14)") (class "Default")
      (node (ref "SV222") (pin "14") (pinfunction "14_14") (pintype "passive"))
    )
    (net (code "6413") (name "unconnected-(SV222-Pad15)") (class "Default")
      (node (ref "SV222") (pin "15") (pinfunction "15_15") (pintype "passive"))
    )
    (net (code "6414") (name "unconnected-(SV222-Pad16)") (class "Default")
      (node (ref "SV222") (pin "16") (pinfunction "16_16") (pintype "passive"))
    )
    (net (code "6415") (name "unconnected-(SV222-Pad17)") (class "Default")
      (node (ref "SV222") (pin "17") (pinfunction "17_17") (pintype "passive"))
    )
    (net (code "6416") (name "unconnected-(SV222-Pad18)") (class "Default")
      (node (ref "SV222") (pin "18") (pinfunction "18_18") (pintype "passive"))
    )
    (net (code "6417") (name "unconnected-(SV222-Pad19)") (class "Default")
      (node (ref "SV222") (pin "19") (pinfunction "19_19") (pintype "passive"))
    )
    (net (code "6418") (name "unconnected-(SV222-Pad20)") (class "Default")
      (node (ref "SV222") (pin "20") (pinfunction "20_20") (pintype "passive"))
    )
    (net (code "6419") (name "unconnected-(SV222-Pad21)") (class "Default")
      (node (ref "SV222") (pin "21") (pinfunction "21_21") (pintype "passive"))
    )
    (net (code "6420") (name "unconnected-(SV222-Pad22)") (class "Default")
      (node (ref "SV222") (pin "22") (pinfunction "22_22") (pintype "passive"))
    )
    (net (code "6421") (name "unconnected-(SV222-Pad23)") (class "Default")
      (node (ref "SV222") (pin "23") (pinfunction "23_23") (pintype "passive"))
    )
    (net (code "6422") (name "unconnected-(SV222-Pad24)") (class "Default")
      (node (ref "SV222") (pin "24") (pinfunction "24_24") (pintype "passive"))
    )
    (net (code "6423") (name "unconnected-(SV223-Pad1)") (class "Default")
      (node (ref "SV223") (pin "1") (pinfunction "1_1") (pintype "passive"))
    )
    (net (code "6424") (name "unconnected-(SV223-Pad2)") (class "Default")
      (node (ref "SV223") (pin "2") (pinfunction "2_2") (pintype "passive"))
    )
    (net (code "6425") (name "unconnected-(SV223-Pad3)") (class "Default")
      (node (ref "SV223") (pin "3") (pinfunction "3_3") (pintype "passive"))
    )
    (net (code "6426") (name "unconnected-(SV223-Pad4)") (class "Default")
      (node (ref "SV223") (pin "4") (pinfunction "4_4") (pintype "passive"))
    )
    (net (code "6427") (name "unconnected-(SV223-Pad5)") (class "Default")
      (node (ref "SV223") (pin "5") (pinfunction "5_5") (pintype "passive"))
    )
    (net (code "6428") (name "unconnected-(SV223-Pad6)") (class "Default")
      (node (ref "SV223") (pin "6") (pinfunction "6_6") (pintype "passive"))
    )
    (net (code "6429") (name "unconnected-(SV223-Pad7)") (class "Default")
      (node (ref "SV223") (pin "7") (pinfunction "7_7") (pintype "passive"))
    )
    (net (code "6430") (name "unconnected-(SV223-Pad8)") (class "Default")
      (node (ref "SV223") (pin "8") (pinfunction "8_8") (pintype "passive"))
    )
    (net (code "6431") (name "unconnected-(SV223-Pad9)") (class "Default")
      (node (ref "SV223") (pin "9") (pinfunction "9_9") (pintype "passive"))
    )
    (net (code "6432") (name "unconnected-(SV223-Pad10)") (class "Default")
      (node (ref "SV223") (pin "10") (pinfunction "10_10") (pintype "passive"))
    )
    (net (code "6433") (name "unconnected-(SV223-Pad11)") (class "Default")
      (node (ref "SV223") (pin "11") (pinfunction "11_11") (pintype "passive"))
    )
    (net (code "6434") (name "unconnected-(SV223-Pad12)") (class "Default")
      (node (ref "SV223") (pin "12") (pinfunction "12_12") (pintype "passive"))
    )
    (net (code "6435") (name "unconnected-(SV223-Pad13)") (class "Default")
      (node (ref "SV223") (pin "13") (pinfunction "13_13") (pintype "passive"))
    )
    (net (code "6436") (name "unconnected-(SV223-Pad14)") (class "Default")
      (node (ref "SV223") (pin "14") (pinfunction "14_14") (pintype "passive"))
    )
    (net (code "6437") (name "unconnected-(SV223-Pad15)") (class "Default")
      (node (ref "SV223") (pin "15") (pinfunction "15_15") (pintype "passive"))
    )
    (net (code "6438") (name "unconnected-(SV223-Pad16)") (class "Default")
      (node (ref "SV223") (pin "16") (pinfunction "16_16") (pintype "passive"))
    )
    (net (code "6439") (name "unconnected-(SV223-Pad17)") (class "Default")
      (node (ref "SV223") (pin "17") (pinfunction "17_17") (pintype "passive"))
    )
    (net (code "6440") (name "unconnected-(SV223-Pad18)") (class "Default")
      (node (ref "SV223") (pin "18") (pinfunction "18_18") (pintype "passive"))
    )
    (net (code "6441") (name "unconnected-(SV223-Pad19)") (class "Default")
      (node (ref "SV223") (pin "19") (pinfunction "19_19") (pintype "passive"))
    )
    (net (code "6442") (name "unconnected-(SV223-Pad20)") (class "Default")
      (node (ref "SV223") (pin "20") (pinfunction "20_20") (pintype "passive"))
    )
    (net (code "6443") (name "unconnected-(SV223-Pad21)") (class "Default")
      (node (ref "SV223") (pin "21") (pinfunction "21_21") (pintype "passive"))
    )
    (net (code "6444") (name "unconnected-(SV223-Pad22)") (class "Default")
      (node (ref "SV223") (pin "22") (pinfunction "22_22") (pintype "passive"))
    )
    (net (code "6445") (name "unconnected-(SV223-Pad23)") (class "Default")
      (node (ref "SV223") (pin "23") (pinfunction "23_23") (pintype "passive"))
    )
    (net (code "6446") (name "unconnected-(SV223-Pad24)") (class "Default")
      (node (ref "SV223") (pin "24") (pinfunction "24_24") (pintype "passive"))
    )
    (net (code "6447") (name "unconnected-(SV223-Pad25)") (class "Default")
      (node (ref "SV223") (pin "25") (pinfunction "25_25") (pintype "passive"))
    )
    (net (code "6448") (name "unconnected-(SV223-Pad26)") (class "Default")
      (node (ref "SV223") (pin "26") (pinfunction "26_26") (pintype "passive"))
    )
    (net (code "6449") (name "unconnected-(SV223-Pad27)") (class "Default")
      (node (ref "SV223") (pin "27") (pinfunction "27_27") (pintype "passive"))
    )
    (net (code "6450") (name "unconnected-(SV223-Pad28)") (class "Default")
      (node (ref "SV223") (pin "28") (pinfunction "28_28") (pintype "passive"))
    )
    (net (code "6451") (name "unconnected-(SV223-Pad29)") (class "Default")
      (node (ref "SV223") (pin "29") (pinfunction "29_29") (pintype "passive"))
    )
    (net (code "6452") (name "unconnected-(SV223-Pad30)") (class "Default")
      (node (ref "SV223") (pin "30") (pinfunction "30_30") (pintype "passive"))
    )
    (net (code "6453") (name "unconnected-(SV223-Pad31)") (class "Default")
      (node (ref "SV223") (pin "31") (pinfunction "31_31") (pintype "passive"))
    )
    (net (code "6454") (name "unconnected-(SV223-Pad32)") (class "Default")
      (node (ref "SV223") (pin "32") (pinfunction "32_32") (pintype "passive"))
    )
    (net (code "6455") (name "unconnected-(SV223-Pad33)") (class "Default")
      (node (ref "SV223") (pin "33") (pinfunction "33_33") (pintype "passive"))
    )
    (net (code "6456") (name "unconnected-(SV223-Pad34)") (class "Default")
      (node (ref "SV223") (pin "34") (pinfunction "34_34") (pintype "passive"))
    )
    (net (code "6457") (name "unconnected-(SV223-Pad35)") (class "Default")
      (node (ref "SV223") (pin "35") (pinfunction "35_35") (pintype "passive"))
    )
    (net (code "6458") (name "unconnected-(SV223-Pad36)") (class "Default")
      (node (ref "SV223") (pin "36") (pinfunction "36_36") (pintype "passive"))
    )
    (net (code "6459") (name "unconnected-(SV223-Pad37)") (class "Default")
      (node (ref "SV223") (pin "37") (pinfunction "37_37") (pintype "passive"))
    )
    (net (code "6460") (name "unconnected-(SV223-Pad38)") (class "Default")
      (node (ref "SV223") (pin "38") (pinfunction "38_38") (pintype "passive"))
    )
    (net (code "6461") (name "unconnected-(SV223-Pad39)") (class "Default")
      (node (ref "SV223") (pin "39") (pinfunction "39_39") (pintype "passive"))
    )
    (net (code "6462") (name "unconnected-(SV223-Pad40)") (class "Default")
      (node (ref "SV223") (pin "40") (pinfunction "40_40") (pintype "passive"))
    )
    (net (code "6463") (name "unconnected-(SV224-Pad1)") (class "Default")
      (node (ref "SV224") (pin "1") (pinfunction "1_1") (pintype "passive"))
    )
    (net (code "6464") (name "unconnected-(SV224-Pad2)") (class "Default")
      (node (ref "SV224") (pin "2") (pinfunction "2_2") (pintype "passive"))
    )
    (net (code "6465") (name "unconnected-(SV224-Pad3)") (class "Default")
      (node (ref "SV224") (pin "3") (pinfunction "3_3") (pintype "passive"))
    )
    (net (code "6466") (name "unconnected-(SV224-Pad4)") (class "Default")
      (node (ref "SV224") (pin "4") (pinfunction "4_4") (pintype "passive"))
    )
    (net (code "6467") (name "unconnected-(SV224-Pad5)") (class "Default")
      (node (ref "SV224") (pin "5") (pinfunction "5_5") (pintype "passive"))
    )
    (net (code "6468") (name "unconnected-(SV224-Pad6)") (class "Default")
      (node (ref "SV224") (pin "6") (pinfunction "6_6") (pintype "passive"))
    )
    (net (code "6469") (name "unconnected-(SV224-Pad7)") (class "Default")
      (node (ref "SV224") (pin "7") (pinfunction "7_7") (pintype "passive"))
    )
    (net (code "6470") (name "unconnected-(SV224-Pad8)") (class "Default")
      (node (ref "SV224") (pin "8") (pinfunction "8_8") (pintype "passive"))
    )
    (net (code "6471") (name "unconnected-(SV224-Pad9)") (class "Default")
      (node (ref "SV224") (pin "9") (pinfunction "9_9") (pintype "passive"))
    )
    (net (code "6472") (name "unconnected-(SV224-Pad10)") (class "Default")
      (node (ref "SV224") (pin "10") (pinfunction "10_10") (pintype "passive"))
    )
    (net (code "6473") (name "unconnected-(SV224-Pad11)") (class "Default")
      (node (ref "SV224") (pin "11") (pinfunction "11_11") (pintype "passive"))
    )
    (net (code "6474") (name "unconnected-(SV224-Pad12)") (class "Default")
      (node (ref "SV224") (pin "12") (pinfunction "12_12") (pintype "passive"))
    )
    (net (code "6475") (name "unconnected-(SV224-Pad13)") (class "Default")
      (node (ref "SV224") (pin "13") (pinfunction "13_13") (pintype "passive"))
    )
    (net (code "6476") (name "unconnected-(SV224-Pad14)") (class "Default")
      (node (ref "SV224") (pin "14") (pinfunction "14_14") (pintype "passive"))
    )
    (net (code "6477") (name "unconnected-(SV224-Pad15)") (class "Default")
      (node (ref "SV224") (pin "15") (pinfunction "15_15") (pintype "passive"))
    )
    (net (code "6478") (name "unconnected-(SV224-Pad16)") (class "Default")
      (node (ref "SV224") (pin "16") (pinfunction "16_16") (pintype "passive"))
    )
    (net (code "6479") (name "unconnected-(SV224-Pad17)") (class "Default")
      (node (ref "SV224") (pin "17") (pinfunction "17_17") (pintype "passive"))
    )
    (net (code "6480") (name "unconnected-(SV224-Pad18)") (class "Default")
      (node (ref "SV224") (pin "18") (pinfunction "18_18") (pintype "passive"))
    )
    (net (code "6481") (name "unconnected-(SV224-Pad19)") (class "Default")
      (node (ref "SV224") (pin "19") (pinfunction "19_19") (pintype "passive"))
    )
    (net (code "6482") (name "unconnected-(SV224-Pad20)") (class "Default")
      (node (ref "SV224") (pin "20") (pinfunction "20_20") (pintype "passive"))
    )
    (net (code "6483") (name "unconnected-(SV224-Pad21)") (class "Default")
      (node (ref "SV224") (pin "21") (pinfunction "21_21") (pintype "passive"))
    )
    (net (code "6484") (name "unconnected-(SV224-Pad22)") (class "Default")
      (node (ref "SV224") (pin "22") (pinfunction "22_22") (pintype "passive"))
    )
    (net (code "6485") (name "unconnected-(SV224-Pad23)") (class "Default")
      (node (ref "SV224") (pin "23") (pinfunction "23_23") (pintype "passive"))
    )
    (net (code "6486") (name "unconnected-(SV224-Pad24)") (class "Default")
      (node (ref "SV224") (pin "24") (pinfunction "24_24") (pintype "passive"))
    )
    (net (code "6487") (name "unconnected-(SV224-Pad25)") (class "Default")
      (node (ref "SV224") (pin "25") (pinfunction "25_25") (pintype "passive"))
    )
    (net (code "6488") (name "unconnected-(SV224-Pad26)") (class "Default")
      (node (ref "SV224") (pin "26") (pinfunction "26_26") (pintype "passive"))
    )
    (net (code "6489") (name "unconnected-(SV224-Pad27)") (class "Default")
      (node (ref "SV224") (pin "27") (pinfunction "27_27") (pintype "passive"))
    )
    (net (code "6490") (name "unconnected-(SV224-Pad28)") (class "Default")
      (node (ref "SV224") (pin "28") (pinfunction "28_28") (pintype "passive"))
    )
    (net (code "6491") (name "unconnected-(SV224-Pad29)") (class "Default")
      (node (ref "SV224") (pin "29") (pinfunction "29_29") (pintype "passive"))
    )
    (net (code "6492") (name "unconnected-(SV224-Pad30)") (class "Default")
      (node (ref "SV224") (pin "30") (pinfunction "30_30") (pintype "passive"))
    )
    (net (code "6493") (name "unconnected-(SV224-Pad31)") (class "Default")
      (node (ref "SV224") (pin "31") (pinfunction "31_31") (pintype "passive"))
    )
    (net (code "6494") (name "unconnected-(SV224-Pad32)") (class "Default")
      (node (ref "SV224") (pin "32") (pinfunction "32_32") (pintype "passive"))
    )
    (net (code "6495") (name "unconnected-(SV224-Pad33)") (class "Default")
      (node (ref "SV224") (pin "33") (pinfunction "33_33") (pintype "passive"))
    )
    (net (code "6496") (name "unconnected-(SV224-Pad34)") (class "Default")
      (node (ref "SV224") (pin "34") (pinfunction "34_34") (pintype "passive"))
    )
    (net (code "6497") (name "unconnected-(SV224-Pad35)") (class "Default")
      (node (ref "SV224") (pin "35") (pinfunction "35_35") (pintype "passive"))
    )
    (net (code "6498") (name "unconnected-(SV224-Pad36)") (class "Default")
      (node (ref "SV224") (pin "36") (pinfunction "36_36") (pintype "passive"))
    )
    (net (code "6499") (name "unconnected-(SV224-Pad37)") (class "Default")
      (node (ref "SV224") (pin "37") (pinfunction "37_37") (pintype "passive"))
    )
    (net (code "6500") (name "unconnected-(SV224-Pad38)") (class "Default")
      (node (ref "SV224") (pin "38") (pinfunction "38_38") (pintype "passive"))
    )
    (net (code "6501") (name "unconnected-(SV224-Pad39)") (class "Default")
      (node (ref "SV224") (pin "39") (pinfunction "39_39") (pintype "passive"))
    )
    (net (code "6502") (name "unconnected-(SV224-Pad40)") (class "Default")
      (node (ref "SV224") (pin "40") (pinfunction "40_40") (pintype "passive"))
    )
    (net (code "6503") (name "unconnected-(SV225-Pad1)") (class "Default")
      (node (ref "SV225") (pin "1") (pinfunction "1_1") (pintype "passive"))
    )
    (net (code "6504") (name "unconnected-(SV225-Pad2)") (class "Default")
      (node (ref "SV225") (pin "2") (pinfunction "2_2") (pintype "passive"))
    )
    (net (code "6505") (name "unconnected-(SV225-Pad3)") (class "Default")
      (node (ref "SV225") (pin "3") (pinfunction "3_3") (pintype "passive"))
    )
    (net (code "6506") (name "unconnected-(SV225-Pad4)") (class "Default")
      (node (ref "SV225") (pin "4") (pinfunction "4_4") (pintype "passive"))
    )
    (net (code "6507") (name "unconnected-(SV225-Pad5)") (class "Default")
      (node (ref "SV225") (pin "5") (pinfunction "5_5") (pintype "passive"))
    )
    (net (code "6508") (name "unconnected-(SV225-Pad6)") (class "Default")
      (node (ref "SV225") (pin "6") (pinfunction "6_6") (pintype "passive"))
    )
    (net (code "6509") (name "unconnected-(SV225-Pad7)") (class "Default")
      (node (ref "SV225") (pin "7") (pinfunction "7_7") (pintype "passive"))
    )
    (net (code "6510") (name "unconnected-(SV225-Pad8)") (class "Default")
      (node (ref "SV225") (pin "8") (pinfunction "8_8") (pintype "passive"))
    )
    (net (code "6511") (name "unconnected-(SV225-Pad9)") (class "Default")
      (node (ref "SV225") (pin "9") (pinfunction "9_9") (pintype "passive"))
    )
    (net (code "6512") (name "unconnected-(SV225-Pad10)") (class "Default")
      (node (ref "SV225") (pin "10") (pinfunction "10_10") (pintype "passive"))
    )
    (net (code "6513") (name "unconnected-(SV225-Pad11)") (class "Default")
      (node (ref "SV225") (pin "11") (pinfunction "11_11") (pintype "passive"))
    )
    (net (code "6514") (name "unconnected-(SV225-Pad12)") (class "Default")
      (node (ref "SV225") (pin "12") (pinfunction "12_12") (pintype "passive"))
    )
    (net (code "6515") (name "unconnected-(SV225-Pad13)") (class "Default")
      (node (ref "SV225") (pin "13") (pinfunction "13_13") (pintype "passive"))
    )
    (net (code "6516") (name "unconnected-(SV225-Pad14)") (class "Default")
      (node (ref "SV225") (pin "14") (pinfunction "14_14") (pintype "passive"))
    )
    (net (code "6517") (name "unconnected-(SV225-Pad15)") (class "Default")
      (node (ref "SV225") (pin "15") (pinfunction "15_15") (pintype "passive"))
    )
    (net (code "6518") (name "unconnected-(SV225-Pad16)") (class "Default")
      (node (ref "SV225") (pin "16") (pinfunction "16_16") (pintype "passive"))
    )
    (net (code "6519") (name "unconnected-(SV225-Pad17)") (class "Default")
      (node (ref "SV225") (pin "17") (pinfunction "17_17") (pintype "passive"))
    )
    (net (code "6520") (name "unconnected-(SV225-Pad18)") (class "Default")
      (node (ref "SV225") (pin "18") (pinfunction "18_18") (pintype "passive"))
    )
    (net (code "6521") (name "unconnected-(SV225-Pad19)") (class "Default")
      (node (ref "SV225") (pin "19") (pinfunction "19_19") (pintype "passive"))
    )
    (net (code "6522") (name "unconnected-(SV225-Pad20)") (class "Default")
      (node (ref "SV225") (pin "20") (pinfunction "20_20") (pintype "passive"))
    )
    (net (code "6523") (name "unconnected-(SV225-Pad21)") (class "Default")
      (node (ref "SV225") (pin "21") (pinfunction "21_21") (pintype "passive"))
    )
    (net (code "6524") (name "unconnected-(SV225-Pad22)") (class "Default")
      (node (ref "SV225") (pin "22") (pinfunction "22_22") (pintype "passive"))
    )
    (net (code "6525") (name "unconnected-(SV225-Pad23)") (class "Default")
      (node (ref "SV225") (pin "23") (pinfunction "23_23") (pintype "passive"))
    )
    (net (code "6526") (name "unconnected-(SV225-Pad24)") (class "Default")
      (node (ref "SV225") (pin "24") (pinfunction "24_24") (pintype "passive"))
    )
    (net (code "6527") (name "unconnected-(SV225-Pad25)") (class "Default")
      (node (ref "SV225") (pin "25") (pinfunction "25_25") (pintype "passive"))
    )
    (net (code "6528") (name "unconnected-(SV225-Pad26)") (class "Default")
      (node (ref "SV225") (pin "26") (pinfunction "26_26") (pintype "passive"))
    )
    (net (code "6529") (name "unconnected-(SV225-Pad27)") (class "Default")
      (node (ref "SV225") (pin "27") (pinfunction "27_27") (pintype "passive"))
    )
    (net (code "6530") (name "unconnected-(SV225-Pad28)") (class "Default")
      (node (ref "SV225") (pin "28") (pinfunction "28_28") (pintype "passive"))
    )
    (net (code "6531") (name "unconnected-(SV225-Pad29)") (class "Default")
      (node (ref "SV225") (pin "29") (pinfunction "29_29") (pintype "passive"))
    )
    (net (code "6532") (name "unconnected-(SV225-Pad30)") (class "Default")
      (node (ref "SV225") (pin "30") (pinfunction "30_30") (pintype "passive"))
    )
    (net (code "6533") (name "unconnected-(SV225-Pad31)") (class "Default")
      (node (ref "SV225") (pin "31") (pinfunction "31_31") (pintype "passive"))
    )
    (net (code "6534") (name "unconnected-(SV225-Pad32)") (class "Default")
      (node (ref "SV225") (pin "32") (pinfunction "32_32") (pintype "passive"))
    )
    (net (code "6535") (name "unconnected-(SV225-Pad33)") (class "Default")
      (node (ref "SV225") (pin "33") (pinfunction "33_33") (pintype "passive"))
    )
    (net (code "6536") (name "unconnected-(SV225-Pad34)") (class "Default")
      (node (ref "SV225") (pin "34") (pinfunction "34_34") (pintype "passive"))
    )
    (net (code "6537") (name "unconnected-(SV225-Pad35)") (class "Default")
      (node (ref "SV225") (pin "35") (pinfunction "35_35") (pintype "passive"))
    )
    (net (code "6538") (name "unconnected-(SV225-Pad36)") (class "Default")
      (node (ref "SV225") (pin "36") (pinfunction "36_36") (pintype "passive"))
    )
    (net (code "6539") (name "unconnected-(SV225-Pad37)") (class "Default")
      (node (ref "SV225") (pin "37") (pinfunction "37_37") (pintype "passive"))
    )
    (net (code "6540") (name "unconnected-(SV225-Pad38)") (class "Default")
      (node (ref "SV225") (pin "38") (pinfunction "38_38") (pintype "passive"))
    )
    (net (code "6541") (name "unconnected-(SV225-Pad39)") (class "Default")
      (node (ref "SV225") (pin "39") (pinfunction "39_39") (pintype "passive"))
    )
    (net (code "6542") (name "unconnected-(SV225-Pad40)") (class "Default")
      (node (ref "SV225") (pin "40") (pinfunction "40_40") (pintype "passive"))
    )
    (net (code "6543") (name "unconnected-(SV226-Pad1)") (class "Default")
      (node (ref "SV226") (pin "1") (pinfunction "1_1") (pintype "passive"))
    )
    (net (code "6544") (name "unconnected-(SV226-Pad2)") (class "Default")
      (node (ref "SV226") (pin "2") (pinfunction "2_2") (pintype "passive"))
    )
    (net (code "6545") (name "unconnected-(SV226-Pad3)") (class "Default")
      (node (ref "SV226") (pin "3") (pinfunction "3_3") (pintype "passive"))
    )
    (net (code "6546") (name "unconnected-(SV226-Pad4)") (class "Default")
      (node (ref "SV226") (pin "4") (pinfunction "4_4") (pintype "passive"))
    )
    (net (code "6547") (name "unconnected-(SV226-Pad5)") (class "Default")
      (node (ref "SV226") (pin "5") (pinfunction "5_5") (pintype "passive"))
    )
    (net (code "6548") (name "unconnected-(SV226-Pad6)") (class "Default")
      (node (ref "SV226") (pin "6") (pinfunction "6_6") (pintype "passive"))
    )
    (net (code "6549") (name "unconnected-(SV226-Pad7)") (class "Default")
      (node (ref "SV226") (pin "7") (pinfunction "7_7") (pintype "passive"))
    )
    (net (code "6550") (name "unconnected-(SV226-Pad8)") (class "Default")
      (node (ref "SV226") (pin "8") (pinfunction "8_8") (pintype "passive"))
    )
    (net (code "6551") (name "unconnected-(SV226-Pad9)") (class "Default")
      (node (ref "SV226") (pin "9") (pinfunction "9_9") (pintype "passive"))
    )
    (net (code "6552") (name "unconnected-(SV226-Pad10)") (class "Default")
      (node (ref "SV226") (pin "10") (pinfunction "10_10") (pintype "passive"))
    )
    (net (code "6553") (name "unconnected-(SV226-Pad11)") (class "Default")
      (node (ref "SV226") (pin "11") (pinfunction "11_11") (pintype "passive"))
    )
    (net (code "6554") (name "unconnected-(SV226-Pad12)") (class "Default")
      (node (ref "SV226") (pin "12") (pinfunction "12_12") (pintype "passive"))
    )
    (net (code "6555") (name "unconnected-(SV226-Pad13)") (class "Default")
      (node (ref "SV226") (pin "13") (pinfunction "13_13") (pintype "passive"))
    )
    (net (code "6556") (name "unconnected-(SV226-Pad14)") (class "Default")
      (node (ref "SV226") (pin "14") (pinfunction "14_14") (pintype "passive"))
    )
    (net (code "6557") (name "unconnected-(SV226-Pad15)") (class "Default")
      (node (ref "SV226") (pin "15") (pinfunction "15_15") (pintype "passive"))
    )
    (net (code "6558") (name "unconnected-(SV226-Pad16)") (class "Default")
      (node (ref "SV226") (pin "16") (pinfunction "16_16") (pintype "passive"))
    )
    (net (code "6559") (name "unconnected-(SV226-Pad17)") (class "Default")
      (node (ref "SV226") (pin "17") (pinfunction "17_17") (pintype "passive"))
    )
    (net (code "6560") (name "unconnected-(SV226-Pad18)") (class "Default")
      (node (ref "SV226") (pin "18") (pinfunction "18_18") (pintype "passive"))
    )
    (net (code "6561") (name "unconnected-(SV226-Pad19)") (class "Default")
      (node (ref "SV226") (pin "19") (pinfunction "19_19") (pintype "passive"))
    )
    (net (code "6562") (name "unconnected-(SV226-Pad20)") (class "Default")
      (node (ref "SV226") (pin "20") (pinfunction "20_20") (pintype "passive"))
    )
    (net (code "6563") (name "unconnected-(SV226-Pad21)") (class "Default")
      (node (ref "SV226") (pin "21") (pinfunction "21_21") (pintype "passive"))
    )
    (net (code "6564") (name "unconnected-(SV226-Pad22)") (class "Default")
      (node (ref "SV226") (pin "22") (pinfunction "22_22") (pintype "passive"))
    )
    (net (code "6565") (name "unconnected-(SV226-Pad23)") (class "Default")
      (node (ref "SV226") (pin "23") (pinfunction "23_23") (pintype "passive"))
    )
    (net (code "6566") (name "unconnected-(SV226-Pad24)") (class "Default")
      (node (ref "SV226") (pin "24") (pinfunction "24_24") (pintype "passive"))
    )
    (net (code "6567") (name "unconnected-(SV226-Pad25)") (class "Default")
      (node (ref "SV226") (pin "25") (pinfunction "25_25") (pintype "passive"))
    )
    (net (code "6568") (name "unconnected-(SV226-Pad26)") (class "Default")
      (node (ref "SV226") (pin "26") (pinfunction "26_26") (pintype "passive"))
    )
    (net (code "6569") (name "unconnected-(SV226-Pad27)") (class "Default")
      (node (ref "SV226") (pin "27") (pinfunction "27_27") (pintype "passive"))
    )
    (net (code "6570") (name "unconnected-(SV226-Pad28)") (class "Default")
      (node (ref "SV226") (pin "28") (pinfunction "28_28") (pintype "passive"))
    )
    (net (code "6571") (name "unconnected-(SV226-Pad29)") (class "Default")
      (node (ref "SV226") (pin "29") (pinfunction "29_29") (pintype "passive"))
    )
    (net (code "6572") (name "unconnected-(SV226-Pad30)") (class "Default")
      (node (ref "SV226") (pin "30") (pinfunction "30_30") (pintype "passive"))
    )
    (net (code "6573") (name "unconnected-(SV226-Pad31)") (class "Default")
      (node (ref "SV226") (pin "31") (pinfunction "31_31") (pintype "passive"))
    )
    (net (code "6574") (name "unconnected-(SV226-Pad32)") (class "Default")
      (node (ref "SV226") (pin "32") (pinfunction "32_32") (pintype "passive"))
    )
    (net (code "6575") (name "unconnected-(SV226-Pad33)") (class "Default")
      (node (ref "SV226") (pin "33") (pinfunction "33_33") (pintype "passive"))
    )
    (net (code "6576") (name "unconnected-(SV226-Pad34)") (class "Default")
      (node (ref "SV226") (pin "34") (pinfunction "34_34") (pintype "passive"))
    )
    (net (code "6577") (name "unconnected-(SV226-Pad35)") (class "Default")
      (node (ref "SV226") (pin "35") (pinfunction "35_35") (pintype "passive"))
    )
    (net (code "6578") (name "unconnected-(SV226-Pad36)") (class "Default")
      (node (ref "SV226") (pin "36") (pinfunction "36_36") (pintype "passive"))
    )
    (net (code "6579") (name "unconnected-(SV226-Pad37)") (class "Default")
      (node (ref "SV226") (pin "37") (pinfunction "37_37") (pintype "passive"))
    )
    (net (code "6580") (name "unconnected-(SV226-Pad38)") (class "Default")
      (node (ref "SV226") (pin "38") (pinfunction "38_38") (pintype "passive"))
    )
    (net (code "6581") (name "unconnected-(SV226-Pad39)") (class "Default")
      (node (ref "SV226") (pin "39") (pinfunction "39_39") (pintype "passive"))
    )
    (net (code "6582") (name "unconnected-(SV226-Pad40)") (class "Default")
      (node (ref "SV226") (pin "40") (pinfunction "40_40") (pintype "passive"))
    )
    (net (code "6583") (name "unconnected-(SV227-Pad1)") (class "Default")
      (node (ref "SV227") (pin "1") (pinfunction "1_1") (pintype "passive"))
    )
    (net (code "6584") (name "unconnected-(SV227-Pad2)") (class "Default")
      (node (ref "SV227") (pin "2") (pinfunction "2_2") (pintype "passive"))
    )
    (net (code "6585") (name "unconnected-(SV227-Pad3)") (class "Default")
      (node (ref "SV227") (pin "3") (pinfunction "3_3") (pintype "passive"))
    )
    (net (code "6586") (name "unconnected-(SV227-Pad4)") (class "Default")
      (node (ref "SV227") (pin "4") (pinfunction "4_4") (pintype "passive"))
    )
    (net (code "6587") (name "unconnected-(SV227-Pad5)") (class "Default")
      (node (ref "SV227") (pin "5") (pinfunction "5_5") (pintype "passive"))
    )
    (net (code "6588") (name "unconnected-(SV227-Pad6)") (class "Default")
      (node (ref "SV227") (pin "6") (pinfunction "6_6") (pintype "passive"))
    )
    (net (code "6589") (name "unconnected-(SV227-Pad7)") (class "Default")
      (node (ref "SV227") (pin "7") (pinfunction "7_7") (pintype "passive"))
    )
    (net (code "6590") (name "unconnected-(SV227-Pad8)") (class "Default")
      (node (ref "SV227") (pin "8") (pinfunction "8_8") (pintype "passive"))
    )
    (net (code "6591") (name "unconnected-(SV227-Pad9)") (class "Default")
      (node (ref "SV227") (pin "9") (pinfunction "9_9") (pintype "passive"))
    )
    (net (code "6592") (name "unconnected-(SV227-Pad10)") (class "Default")
      (node (ref "SV227") (pin "10") (pinfunction "10_10") (pintype "passive"))
    )
    (net (code "6593") (name "unconnected-(SV227-Pad11)") (class "Default")
      (node (ref "SV227") (pin "11") (pinfunction "11_11") (pintype "passive"))
    )
    (net (code "6594") (name "unconnected-(SV227-Pad12)") (class "Default")
      (node (ref "SV227") (pin "12") (pinfunction "12_12") (pintype "passive"))
    )
    (net (code "6595") (name "unconnected-(SV227-Pad13)") (class "Default")
      (node (ref "SV227") (pin "13") (pinfunction "13_13") (pintype "passive"))
    )
    (net (code "6596") (name "unconnected-(SV227-Pad14)") (class "Default")
      (node (ref "SV227") (pin "14") (pinfunction "14_14") (pintype "passive"))
    )
    (net (code "6597") (name "unconnected-(SV227-Pad15)") (class "Default")
      (node (ref "SV227") (pin "15") (pinfunction "15_15") (pintype "passive"))
    )
    (net (code "6598") (name "unconnected-(SV227-Pad16)") (class "Default")
      (node (ref "SV227") (pin "16") (pinfunction "16_16") (pintype "passive"))
    )
    (net (code "6599") (name "unconnected-(SV227-Pad17)") (class "Default")
      (node (ref "SV227") (pin "17") (pinfunction "17_17") (pintype "passive"))
    )
    (net (code "6600") (name "unconnected-(SV227-Pad18)") (class "Default")
      (node (ref "SV227") (pin "18") (pinfunction "18_18") (pintype "passive"))
    )
    (net (code "6601") (name "unconnected-(SV227-Pad19)") (class "Default")
      (node (ref "SV227") (pin "19") (pinfunction "19_19") (pintype "passive"))
    )
    (net (code "6602") (name "unconnected-(SV227-Pad20)") (class "Default")
      (node (ref "SV227") (pin "20") (pinfunction "20_20") (pintype "passive"))
    )
    (net (code "6603") (name "unconnected-(SV227-Pad21)") (class "Default")
      (node (ref "SV227") (pin "21") (pinfunction "21_21") (pintype "passive"))
    )
    (net (code "6604") (name "unconnected-(SV227-Pad22)") (class "Default")
      (node (ref "SV227") (pin "22") (pinfunction "22_22") (pintype "passive"))
    )
    (net (code "6605") (name "unconnected-(SV227-Pad23)") (class "Default")
      (node (ref "SV227") (pin "23") (pinfunction "23_23") (pintype "passive"))
    )
    (net (code "6606") (name "unconnected-(SV227-Pad24)") (class "Default")
      (node (ref "SV227") (pin "24") (pinfunction "24_24") (pintype "passive"))
    )
    (net (code "6607") (name "unconnected-(SV228-Pad1)") (class "Default")
      (node (ref "SV228") (pin "1") (pinfunction "1_1") (pintype "passive"))
    )
    (net (code "6608") (name "unconnected-(SV228-Pad2)") (class "Default")
      (node (ref "SV228") (pin "2") (pinfunction "2_2") (pintype "passive"))
    )
    (net (code "6609") (name "unconnected-(SV228-Pad3)") (class "Default")
      (node (ref "SV228") (pin "3") (pinfunction "3_3") (pintype "passive"))
    )
    (net (code "6610") (name "unconnected-(SV228-Pad4)") (class "Default")
      (node (ref "SV228") (pin "4") (pinfunction "4_4") (pintype "passive"))
    )
    (net (code "6611") (name "unconnected-(SV228-Pad5)") (class "Default")
      (node (ref "SV228") (pin "5") (pinfunction "5_5") (pintype "passive"))
    )
    (net (code "6612") (name "unconnected-(SV228-Pad6)") (class "Default")
      (node (ref "SV228") (pin "6") (pinfunction "6_6") (pintype "passive"))
    )
    (net (code "6613") (name "unconnected-(SV228-Pad7)") (class "Default")
      (node (ref "SV228") (pin "7") (pinfunction "7_7") (pintype "passive"))
    )
    (net (code "6614") (name "unconnected-(SV228-Pad8)") (class "Default")
      (node (ref "SV228") (pin "8") (pinfunction "8_8") (pintype "passive"))
    )
    (net (code "6615") (name "unconnected-(SV228-Pad9)") (class "Default")
      (node (ref "SV228") (pin "9") (pinfunction "9_9") (pintype "passive"))
    )
    (net (code "6616") (name "unconnected-(SV228-Pad10)") (class "Default")
      (node (ref "SV228") (pin "10") (pinfunction "10_10") (pintype "passive"))
    )
    (net (code "6617") (name "unconnected-(SV228-Pad11)") (class "Default")
      (node (ref "SV228") (pin "11") (pinfunction "11_11") (pintype "passive"))
    )
    (net (code "6618") (name "unconnected-(SV228-Pad12)") (class "Default")
      (node (ref "SV228") (pin "12") (pinfunction "12_12") (pintype "passive"))
    )
    (net (code "6619") (name "unconnected-(SV228-Pad13)") (class "Default")
      (node (ref "SV228") (pin "13") (pinfunction "13_13") (pintype "passive"))
    )
    (net (code "6620") (name "unconnected-(SV228-Pad14)") (class "Default")
      (node (ref "SV228") (pin "14") (pinfunction "14_14") (pintype "passive"))
    )
    (net (code "6621") (name "unconnected-(SV228-Pad15)") (class "Default")
      (node (ref "SV228") (pin "15") (pinfunction "15_15") (pintype "passive"))
    )
    (net (code "6622") (name "unconnected-(SV228-Pad16)") (class "Default")
      (node (ref "SV228") (pin "16") (pinfunction "16_16") (pintype "passive"))
    )
    (net (code "6623") (name "unconnected-(SV228-Pad17)") (class "Default")
      (node (ref "SV228") (pin "17") (pinfunction "17_17") (pintype "passive"))
    )
    (net (code "6624") (name "unconnected-(SV228-Pad18)") (class "Default")
      (node (ref "SV228") (pin "18") (pinfunction "18_18") (pintype "passive"))
    )
    (net (code "6625") (name "unconnected-(SV228-Pad19)") (class "Default")
      (node (ref "SV228") (pin "19") (pinfunction "19_19") (pintype "passive"))
    )
    (net (code "6626") (name "unconnected-(SV228-Pad20)") (class "Default")
      (node (ref "SV228") (pin "20") (pinfunction "20_20") (pintype "passive"))
    )
    (net (code "6627") (name "unconnected-(SV228-Pad21)") (class "Default")
      (node (ref "SV228") (pin "21") (pinfunction "21_21") (pintype "passive"))
    )
    (net (code "6628") (name "unconnected-(SV228-Pad22)") (class "Default")
      (node (ref "SV228") (pin "22") (pinfunction "22_22") (pintype "passive"))
    )
    (net (code "6629") (name "unconnected-(SV228-Pad23)") (class "Default")
      (node (ref "SV228") (pin "23") (pinfunction "23_23") (pintype "passive"))
    )
    (net (code "6630") (name "unconnected-(SV228-Pad24)") (class "Default")
      (node (ref "SV228") (pin "24") (pinfunction "24_24") (pintype "passive"))
    )
    (net (code "6631") (name "unconnected-(SV229-Pad1)") (class "Default")
      (node (ref "SV229") (pin "1") (pinfunction "1_1") (pintype "passive"))
    )
    (net (code "6632") (name "unconnected-(SV229-Pad2)") (class "Default")
      (node (ref "SV229") (pin "2") (pinfunction "2_2") (pintype "passive"))
    )
    (net (code "6633") (name "unconnected-(SV229-Pad3)") (class "Default")
      (node (ref "SV229") (pin "3") (pinfunction "3_3") (pintype "passive"))
    )
    (net (code "6634") (name "unconnected-(SV229-Pad4)") (class "Default")
      (node (ref "SV229") (pin "4") (pinfunction "4_4") (pintype "passive"))
    )
    (net (code "6635") (name "unconnected-(SV229-Pad5)") (class "Default")
      (node (ref "SV229") (pin "5") (pinfunction "5_5") (pintype "passive"))
    )
    (net (code "6636") (name "unconnected-(SV229-Pad6)") (class "Default")
      (node (ref "SV229") (pin "6") (pinfunction "6_6") (pintype "passive"))
    )
    (net (code "6637") (name "unconnected-(SV229-Pad7)") (class "Default")
      (node (ref "SV229") (pin "7") (pinfunction "7_7") (pintype "passive"))
    )
    (net (code "6638") (name "unconnected-(SV229-Pad8)") (class "Default")
      (node (ref "SV229") (pin "8") (pinfunction "8_8") (pintype "passive"))
    )
    (net (code "6639") (name "unconnected-(SV229-Pad9)") (class "Default")
      (node (ref "SV229") (pin "9") (pinfunction "9_9") (pintype "passive"))
    )
    (net (code "6640") (name "unconnected-(SV229-Pad10)") (class "Default")
      (node (ref "SV229") (pin "10") (pinfunction "10_10") (pintype "passive"))
    )
    (net (code "6641") (name "unconnected-(SV229-Pad11)") (class "Default")
      (node (ref "SV229") (pin "11") (pinfunction "11_11") (pintype "passive"))
    )
    (net (code "6642") (name "unconnected-(SV229-Pad12)") (class "Default")
      (node (ref "SV229") (pin "12") (pinfunction "12_12") (pintype "passive"))
    )
    (net (code "6643") (name "unconnected-(SV229-Pad13)") (class "Default")
      (node (ref "SV229") (pin "13") (pinfunction "13_13") (pintype "passive"))
    )
    (net (code "6644") (name "unconnected-(SV229-Pad14)") (class "Default")
      (node (ref "SV229") (pin "14") (pinfunction "14_14") (pintype "passive"))
    )
    (net (code "6645") (name "unconnected-(SV229-Pad15)") (class "Default")
      (node (ref "SV229") (pin "15") (pinfunction "15_15") (pintype "passive"))
    )
    (net (code "6646") (name "unconnected-(SV229-Pad16)") (class "Default")
      (node (ref "SV229") (pin "16") (pinfunction "16_16") (pintype "passive"))
    )
    (net (code "6647") (name "unconnected-(SV229-Pad17)") (class "Default")
      (node (ref "SV229") (pin "17") (pinfunction "17_17") (pintype "passive"))
    )
    (net (code "6648") (name "unconnected-(SV229-Pad18)") (class "Default")
      (node (ref "SV229") (pin "18") (pinfunction "18_18") (pintype "passive"))
    )
    (net (code "6649") (name "unconnected-(SV229-Pad19)") (class "Default")
      (node (ref "SV229") (pin "19") (pinfunction "19_19") (pintype "passive"))
    )
    (net (code "6650") (name "unconnected-(SV229-Pad20)") (class "Default")
      (node (ref "SV229") (pin "20") (pinfunction "20_20") (pintype "passive"))
    )
    (net (code "6651") (name "unconnected-(SV229-Pad21)") (class "Default")
      (node (ref "SV229") (pin "21") (pinfunction "21_21") (pintype "passive"))
    )
    (net (code "6652") (name "unconnected-(SV229-Pad22)") (class "Default")
      (node (ref "SV229") (pin "22") (pinfunction "22_22") (pintype "passive"))
    )
    (net (code "6653") (name "unconnected-(SV229-Pad23)") (class "Default")
      (node (ref "SV229") (pin "23") (pinfunction "23_23") (pintype "passive"))
    )
    (net (code "6654") (name "unconnected-(SV229-Pad24)") (class "Default")
      (node (ref "SV229") (pin "24") (pinfunction "24_24") (pintype "passive"))
    )
    (net (code "6655") (name "unconnected-(SV230-Pad1)") (class "Default")
      (node (ref "SV230") (pin "1") (pinfunction "1_1") (pintype "passive"))
    )
    (net (code "6656") (name "unconnected-(SV230-Pad2)") (class "Default")
      (node (ref "SV230") (pin "2") (pinfunction "2_2") (pintype "passive"))
    )
    (net (code "6657") (name "unconnected-(SV230-Pad3)") (class "Default")
      (node (ref "SV230") (pin "3") (pinfunction "3_3") (pintype "passive"))
    )
    (net (code "6658") (name "unconnected-(SV230-Pad4)") (class "Default")
      (node (ref "SV230") (pin "4") (pinfunction "4_4") (pintype "passive"))
    )
    (net (code "6659") (name "unconnected-(SV230-Pad5)") (class "Default")
      (node (ref "SV230") (pin "5") (pinfunction "5_5") (pintype "passive"))
    )
    (net (code "6660") (name "unconnected-(SV230-Pad6)") (class "Default")
      (node (ref "SV230") (pin "6") (pinfunction "6_6") (pintype "passive"))
    )
    (net (code "6661") (name "unconnected-(SV230-Pad7)") (class "Default")
      (node (ref "SV230") (pin "7") (pinfunction "7_7") (pintype "passive"))
    )
    (net (code "6662") (name "unconnected-(SV230-Pad8)") (class "Default")
      (node (ref "SV230") (pin "8") (pinfunction "8_8") (pintype "passive"))
    )
    (net (code "6663") (name "unconnected-(SV230-Pad9)") (class "Default")
      (node (ref "SV230") (pin "9") (pinfunction "9_9") (pintype "passive"))
    )
    (net (code "6664") (name "unconnected-(SV230-Pad10)") (class "Default")
      (node (ref "SV230") (pin "10") (pinfunction "10_10") (pintype "passive"))
    )
    (net (code "6665") (name "unconnected-(SV230-Pad11)") (class "Default")
      (node (ref "SV230") (pin "11") (pinfunction "11_11") (pintype "passive"))
    )
    (net (code "6666") (name "unconnected-(SV230-Pad12)") (class "Default")
      (node (ref "SV230") (pin "12") (pinfunction "12_12") (pintype "passive"))
    )
    (net (code "6667") (name "unconnected-(SV230-Pad13)") (class "Default")
      (node (ref "SV230") (pin "13") (pinfunction "13_13") (pintype "passive"))
    )
    (net (code "6668") (name "unconnected-(SV230-Pad14)") (class "Default")
      (node (ref "SV230") (pin "14") (pinfunction "14_14") (pintype "passive"))
    )
    (net (code "6669") (name "unconnected-(SV230-Pad15)") (class "Default")
      (node (ref "SV230") (pin "15") (pinfunction "15_15") (pintype "passive"))
    )
    (net (code "6670") (name "unconnected-(SV230-Pad16)") (class "Default")
      (node (ref "SV230") (pin "16") (pinfunction "16_16") (pintype "passive"))
    )
    (net (code "6671") (name "unconnected-(SV230-Pad17)") (class "Default")
      (node (ref "SV230") (pin "17") (pinfunction "17_17") (pintype "passive"))
    )
    (net (code "6672") (name "unconnected-(SV230-Pad18)") (class "Default")
      (node (ref "SV230") (pin "18") (pinfunction "18_18") (pintype "passive"))
    )
    (net (code "6673") (name "unconnected-(SV230-Pad19)") (class "Default")
      (node (ref "SV230") (pin "19") (pinfunction "19_19") (pintype "passive"))
    )
    (net (code "6674") (name "unconnected-(SV230-Pad20)") (class "Default")
      (node (ref "SV230") (pin "20") (pinfunction "20_20") (pintype "passive"))
    )
    (net (code "6675") (name "unconnected-(SV230-Pad21)") (class "Default")
      (node (ref "SV230") (pin "21") (pinfunction "21_21") (pintype "passive"))
    )
    (net (code "6676") (name "unconnected-(SV230-Pad22)") (class "Default")
      (node (ref "SV230") (pin "22") (pinfunction "22_22") (pintype "passive"))
    )
    (net (code "6677") (name "unconnected-(SV230-Pad23)") (class "Default")
      (node (ref "SV230") (pin "23") (pinfunction "23_23") (pintype "passive"))
    )
    (net (code "6678") (name "unconnected-(SV230-Pad24)") (class "Default")
      (node (ref "SV230") (pin "24") (pinfunction "24_24") (pintype "passive"))
    )
    (net (code "6679") (name "unconnected-(SV231-Pad1)") (class "Default")
      (node (ref "SV231") (pin "1") (pinfunction "1_1") (pintype "passive"))
    )
    (net (code "6680") (name "unconnected-(SV231-Pad2)") (class "Default")
      (node (ref "SV231") (pin "2") (pinfunction "2_2") (pintype "passive"))
    )
    (net (code "6681") (name "unconnected-(SV231-Pad3)") (class "Default")
      (node (ref "SV231") (pin "3") (pinfunction "3_3") (pintype "passive"))
    )
    (net (code "6682") (name "unconnected-(SV231-Pad4)") (class "Default")
      (node (ref "SV231") (pin "4") (pinfunction "4_4") (pintype "passive"))
    )
    (net (code "6683") (name "unconnected-(SV231-Pad5)") (class "Default")
      (node (ref "SV231") (pin "5") (pinfunction "5_5") (pintype "passive"))
    )
    (net (code "6684") (name "unconnected-(SV231-Pad6)") (class "Default")
      (node (ref "SV231") (pin "6") (pinfunction "6_6") (pintype "passive"))
    )
    (net (code "6685") (name "unconnected-(SV231-Pad7)") (class "Default")
      (node (ref "SV231") (pin "7") (pinfunction "7_7") (pintype "passive"))
    )
    (net (code "6686") (name "unconnected-(SV231-Pad8)") (class "Default")
      (node (ref "SV231") (pin "8") (pinfunction "8_8") (pintype "passive"))
    )
    (net (code "6687") (name "unconnected-(SV231-Pad9)") (class "Default")
      (node (ref "SV231") (pin "9") (pinfunction "9_9") (pintype "passive"))
    )
    (net (code "6688") (name "unconnected-(SV231-Pad10)") (class "Default")
      (node (ref "SV231") (pin "10") (pinfunction "10_10") (pintype "passive"))
    )
    (net (code "6689") (name "unconnected-(SV231-Pad11)") (class "Default")
      (node (ref "SV231") (pin "11") (pinfunction "11_11") (pintype "passive"))
    )
    (net (code "6690") (name "unconnected-(SV231-Pad12)") (class "Default")
      (node (ref "SV231") (pin "12") (pinfunction "12_12") (pintype "passive"))
    )
    (net (code "6691") (name "unconnected-(SV231-Pad13)") (class "Default")
      (node (ref "SV231") (pin "13") (pinfunction "13_13") (pintype "passive"))
    )
    (net (code "6692") (name "unconnected-(SV231-Pad14)") (class "Default")
      (node (ref "SV231") (pin "14") (pinfunction "14_14") (pintype "passive"))
    )
    (net (code "6693") (name "unconnected-(SV231-Pad15)") (class "Default")
      (node (ref "SV231") (pin "15") (pinfunction "15_15") (pintype "passive"))
    )
    (net (code "6694") (name "unconnected-(SV231-Pad16)") (class "Default")
      (node (ref "SV231") (pin "16") (pinfunction "16_16") (pintype "passive"))
    )
    (net (code "6695") (name "unconnected-(SV231-Pad17)") (class "Default")
      (node (ref "SV231") (pin "17") (pinfunction "17_17") (pintype "passive"))
    )
    (net (code "6696") (name "unconnected-(SV231-Pad18)") (class "Default")
      (node (ref "SV231") (pin "18") (pinfunction "18_18") (pintype "passive"))
    )
    (net (code "6697") (name "unconnected-(SV231-Pad19)") (class "Default")
      (node (ref "SV231") (pin "19") (pinfunction "19_19") (pintype "passive"))
    )
    (net (code "6698") (name "unconnected-(SV231-Pad20)") (class "Default")
      (node (ref "SV231") (pin "20") (pinfunction "20_20") (pintype "passive"))
    )
    (net (code "6699") (name "unconnected-(SV231-Pad21)") (class "Default")
      (node (ref "SV231") (pin "21") (pinfunction "21_21") (pintype "passive"))
    )
    (net (code "6700") (name "unconnected-(SV231-Pad22)") (class "Default")
      (node (ref "SV231") (pin "22") (pinfunction "22_22") (pintype "passive"))
    )
    (net (code "6701") (name "unconnected-(SV231-Pad23)") (class "Default")
      (node (ref "SV231") (pin "23") (pinfunction "23_23") (pintype "passive"))
    )
    (net (code "6702") (name "unconnected-(SV231-Pad24)") (class "Default")
      (node (ref "SV231") (pin "24") (pinfunction "24_24") (pintype "passive"))
    )
    (net (code "6703") (name "unconnected-(SV231-Pad25)") (class "Default")
      (node (ref "SV231") (pin "25") (pinfunction "25_25") (pintype "passive"))
    )
    (net (code "6704") (name "unconnected-(SV231-Pad26)") (class "Default")
      (node (ref "SV231") (pin "26") (pinfunction "26_26") (pintype "passive"))
    )
    (net (code "6705") (name "unconnected-(SV231-Pad27)") (class "Default")
      (node (ref "SV231") (pin "27") (pinfunction "27_27") (pintype "passive"))
    )
    (net (code "6706") (name "unconnected-(SV231-Pad28)") (class "Default")
      (node (ref "SV231") (pin "28") (pinfunction "28_28") (pintype "passive"))
    )
    (net (code "6707") (name "unconnected-(SV231-Pad29)") (class "Default")
      (node (ref "SV231") (pin "29") (pinfunction "29_29") (pintype "passive"))
    )
    (net (code "6708") (name "unconnected-(SV231-Pad30)") (class "Default")
      (node (ref "SV231") (pin "30") (pinfunction "30_30") (pintype "passive"))
    )
    (net (code "6709") (name "unconnected-(SV231-Pad31)") (class "Default")
      (node (ref "SV231") (pin "31") (pinfunction "31_31") (pintype "passive"))
    )
    (net (code "6710") (name "unconnected-(SV231-Pad32)") (class "Default")
      (node (ref "SV231") (pin "32") (pinfunction "32_32") (pintype "passive"))
    )
    (net (code "6711") (name "unconnected-(SV231-Pad33)") (class "Default")
      (node (ref "SV231") (pin "33") (pinfunction "33_33") (pintype "passive"))
    )
    (net (code "6712") (name "unconnected-(SV231-Pad34)") (class "Default")
      (node (ref "SV231") (pin "34") (pinfunction "34_34") (pintype "passive"))
    )
    (net (code "6713") (name "unconnected-(SV231-Pad35)") (class "Default")
      (node (ref "SV231") (pin "35") (pinfunction "35_35") (pintype "passive"))
    )
    (net (code "6714") (name "unconnected-(SV231-Pad36)") (class "Default")
      (node (ref "SV231") (pin "36") (pinfunction "36_36") (pintype "passive"))
    )
    (net (code "6715") (name "unconnected-(SV231-Pad37)") (class "Default")
      (node (ref "SV231") (pin "37") (pinfunction "37_37") (pintype "passive"))
    )
    (net (code "6716") (name "unconnected-(SV231-Pad38)") (class "Default")
      (node (ref "SV231") (pin "38") (pinfunction "38_38") (pintype "passive"))
    )
    (net (code "6717") (name "unconnected-(SV231-Pad39)") (class "Default")
      (node (ref "SV231") (pin "39") (pinfunction "39_39") (pintype "passive"))
    )
    (net (code "6718") (name "unconnected-(SV231-Pad40)") (class "Default")
      (node (ref "SV231") (pin "40") (pinfunction "40_40") (pintype "passive"))
    )
    (net (code "6719") (name "unconnected-(SV232-Pad1)") (class "Default")
      (node (ref "SV232") (pin "1") (pinfunction "1_1") (pintype "passive"))
    )
    (net (code "6720") (name "unconnected-(SV232-Pad2)") (class "Default")
      (node (ref "SV232") (pin "2") (pinfunction "2_2") (pintype "passive"))
    )
    (net (code "6721") (name "unconnected-(SV232-Pad3)") (class "Default")
      (node (ref "SV232") (pin "3") (pinfunction "3_3") (pintype "passive"))
    )
    (net (code "6722") (name "unconnected-(SV232-Pad4)") (class "Default")
      (node (ref "SV232") (pin "4") (pinfunction "4_4") (pintype "passive"))
    )
    (net (code "6723") (name "unconnected-(SV232-Pad5)") (class "Default")
      (node (ref "SV232") (pin "5") (pinfunction "5_5") (pintype "passive"))
    )
    (net (code "6724") (name "unconnected-(SV232-Pad6)") (class "Default")
      (node (ref "SV232") (pin "6") (pinfunction "6_6") (pintype "passive"))
    )
    (net (code "6725") (name "unconnected-(SV232-Pad7)") (class "Default")
      (node (ref "SV232") (pin "7") (pinfunction "7_7") (pintype "passive"))
    )
    (net (code "6726") (name "unconnected-(SV232-Pad8)") (class "Default")
      (node (ref "SV232") (pin "8") (pinfunction "8_8") (pintype "passive"))
    )
    (net (code "6727") (name "unconnected-(SV232-Pad9)") (class "Default")
      (node (ref "SV232") (pin "9") (pinfunction "9_9") (pintype "passive"))
    )
    (net (code "6728") (name "unconnected-(SV232-Pad10)") (class "Default")
      (node (ref "SV232") (pin "10") (pinfunction "10_10") (pintype "passive"))
    )
    (net (code "6729") (name "unconnected-(SV232-Pad11)") (class "Default")
      (node (ref "SV232") (pin "11") (pinfunction "11_11") (pintype "passive"))
    )
    (net (code "6730") (name "unconnected-(SV232-Pad12)") (class "Default")
      (node (ref "SV232") (pin "12") (pinfunction "12_12") (pintype "passive"))
    )
    (net (code "6731") (name "unconnected-(SV232-Pad13)") (class "Default")
      (node (ref "SV232") (pin "13") (pinfunction "13_13") (pintype "passive"))
    )
    (net (code "6732") (name "unconnected-(SV232-Pad14)") (class "Default")
      (node (ref "SV232") (pin "14") (pinfunction "14_14") (pintype "passive"))
    )
    (net (code "6733") (name "unconnected-(SV232-Pad15)") (class "Default")
      (node (ref "SV232") (pin "15") (pinfunction "15_15") (pintype "passive"))
    )
    (net (code "6734") (name "unconnected-(SV232-Pad16)") (class "Default")
      (node (ref "SV232") (pin "16") (pinfunction "16_16") (pintype "passive"))
    )
    (net (code "6735") (name "unconnected-(SV232-Pad17)") (class "Default")
      (node (ref "SV232") (pin "17") (pinfunction "17_17") (pintype "passive"))
    )
    (net (code "6736") (name "unconnected-(SV232-Pad18)") (class "Default")
      (node (ref "SV232") (pin "18") (pinfunction "18_18") (pintype "passive"))
    )
    (net (code "6737") (name "unconnected-(SV232-Pad19)") (class "Default")
      (node (ref "SV232") (pin "19") (pinfunction "19_19") (pintype "passive"))
    )
    (net (code "6738") (name "unconnected-(SV232-Pad20)") (class "Default")
      (node (ref "SV232") (pin "20") (pinfunction "20_20") (pintype "passive"))
    )
    (net (code "6739") (name "unconnected-(SV232-Pad21)") (class "Default")
      (node (ref "SV232") (pin "21") (pinfunction "21_21") (pintype "passive"))
    )
    (net (code "6740") (name "unconnected-(SV232-Pad22)") (class "Default")
      (node (ref "SV232") (pin "22") (pinfunction "22_22") (pintype "passive"))
    )
    (net (code "6741") (name "unconnected-(SV232-Pad23)") (class "Default")
      (node (ref "SV232") (pin "23") (pinfunction "23_23") (pintype "passive"))
    )
    (net (code "6742") (name "unconnected-(SV232-Pad24)") (class "Default")
      (node (ref "SV232") (pin "24") (pinfunction "24_24") (pintype "passive"))
    )
    (net (code "6743") (name "unconnected-(SV232-Pad25)") (class "Default")
      (node (ref "SV232") (pin "25") (pinfunction "25_25") (pintype "passive"))
    )
    (net (code "6744") (name "unconnected-(SV232-Pad26)") (class "Default")
      (node (ref "SV232") (pin "26") (pinfunction "26_26") (pintype "passive"))
    )
    (net (code "6745") (name "unconnected-(SV232-Pad27)") (class "Default")
      (node (ref "SV232") (pin "27") (pinfunction "27_27") (pintype "passive"))
    )
    (net (code "6746") (name "unconnected-(SV232-Pad28)") (class "Default")
      (node (ref "SV232") (pin "28") (pinfunction "28_28") (pintype "passive"))
    )
    (net (code "6747") (name "unconnected-(SV232-Pad29)") (class "Default")
      (node (ref "SV232") (pin "29") (pinfunction "29_29") (pintype "passive"))
    )
    (net (code "6748") (name "unconnected-(SV232-Pad30)") (class "Default")
      (node (ref "SV232") (pin "30") (pinfunction "30_30") (pintype "passive"))
    )
    (net (code "6749") (name "unconnected-(SV232-Pad31)") (class "Default")
      (node (ref "SV232") (pin "31") (pinfunction "31_31") (pintype "passive"))
    )
    (net (code "6750") (name "unconnected-(SV232-Pad32)") (class "Default")
      (node (ref "SV232") (pin "32") (pinfunction "32_32") (pintype "passive"))
    )
    (net (code "6751") (name "unconnected-(SV232-Pad33)") (class "Default")
      (node (ref "SV232") (pin "33") (pinfunction "33_33") (pintype "passive"))
    )
    (net (code "6752") (name "unconnected-(SV232-Pad34)") (class "Default")
      (node (ref "SV232") (pin "34") (pinfunction "34_34") (pintype "passive"))
    )
    (net (code "6753") (name "unconnected-(SV232-Pad35)") (class "Default")
      (node (ref "SV232") (pin "35") (pinfunction "35_35") (pintype "passive"))
    )
    (net (code "6754") (name "unconnected-(SV232-Pad36)") (class "Default")
      (node (ref "SV232") (pin "36") (pinfunction "36_36") (pintype "passive"))
    )
    (net (code "6755") (name "unconnected-(SV232-Pad37)") (class "Default")
      (node (ref "SV232") (pin "37") (pinfunction "37_37") (pintype "passive"))
    )
    (net (code "6756") (name "unconnected-(SV232-Pad38)") (class "Default")
      (node (ref "SV232") (pin "38") (pinfunction "38_38") (pintype "passive"))
    )
    (net (code "6757") (name "unconnected-(SV232-Pad39)") (class "Default")
      (node (ref "SV232") (pin "39") (pinfunction "39_39") (pintype "passive"))
    )
    (net (code "6758") (name "unconnected-(SV232-Pad40)") (class "Default")
      (node (ref "SV232") (pin "40") (pinfunction "40_40") (pintype "passive"))
    )
    (net (code "6759") (name "unconnected-(SV233-Pad1)") (class "Default")
      (node (ref "SV233") (pin "1") (pinfunction "1_1") (pintype "passive"))
    )
    (net (code "6760") (name "unconnected-(SV233-Pad2)") (class "Default")
      (node (ref "SV233") (pin "2") (pinfunction "2_2") (pintype "passive"))
    )
    (net (code "6761") (name "unconnected-(SV233-Pad3)") (class "Default")
      (node (ref "SV233") (pin "3") (pinfunction "3_3") (pintype "passive"))
    )
    (net (code "6762") (name "unconnected-(SV233-Pad4)") (class "Default")
      (node (ref "SV233") (pin "4") (pinfunction "4_4") (pintype "passive"))
    )
    (net (code "6763") (name "unconnected-(SV233-Pad5)") (class "Default")
      (node (ref "SV233") (pin "5") (pinfunction "5_5") (pintype "passive"))
    )
    (net (code "6764") (name "unconnected-(SV233-Pad6)") (class "Default")
      (node (ref "SV233") (pin "6") (pinfunction "6_6") (pintype "passive"))
    )
    (net (code "6765") (name "unconnected-(SV233-Pad7)") (class "Default")
      (node (ref "SV233") (pin "7") (pinfunction "7_7") (pintype "passive"))
    )
    (net (code "6766") (name "unconnected-(SV233-Pad8)") (class "Default")
      (node (ref "SV233") (pin "8") (pinfunction "8_8") (pintype "passive"))
    )
    (net (code "6767") (name "unconnected-(SV233-Pad9)") (class "Default")
      (node (ref "SV233") (pin "9") (pinfunction "9_9") (pintype "passive"))
    )
    (net (code "6768") (name "unconnected-(SV233-Pad10)") (class "Default")
      (node (ref "SV233") (pin "10") (pinfunction "10_10") (pintype "passive"))
    )
    (net (code "6769") (name "unconnected-(SV233-Pad11)") (class "Default")
      (node (ref "SV233") (pin "11") (pinfunction "11_11") (pintype "passive"))
    )
    (net (code "6770") (name "unconnected-(SV233-Pad12)") (class "Default")
      (node (ref "SV233") (pin "12") (pinfunction "12_12") (pintype "passive"))
    )
    (net (code "6771") (name "unconnected-(SV233-Pad13)") (class "Default")
      (node (ref "SV233") (pin "13") (pinfunction "13_13") (pintype "passive"))
    )
    (net (code "6772") (name "unconnected-(SV233-Pad14)") (class "Default")
      (node (ref "SV233") (pin "14") (pinfunction "14_14") (pintype "passive"))
    )
    (net (code "6773") (name "unconnected-(SV233-Pad15)") (class "Default")
      (node (ref "SV233") (pin "15") (pinfunction "15_15") (pintype "passive"))
    )
    (net (code "6774") (name "unconnected-(SV233-Pad16)") (class "Default")
      (node (ref "SV233") (pin "16") (pinfunction "16_16") (pintype "passive"))
    )
    (net (code "6775") (name "unconnected-(SV233-Pad17)") (class "Default")
      (node (ref "SV233") (pin "17") (pinfunction "17_17") (pintype "passive"))
    )
    (net (code "6776") (name "unconnected-(SV233-Pad18)") (class "Default")
      (node (ref "SV233") (pin "18") (pinfunction "18_18") (pintype "passive"))
    )
    (net (code "6777") (name "unconnected-(SV233-Pad19)") (class "Default")
      (node (ref "SV233") (pin "19") (pinfunction "19_19") (pintype "passive"))
    )
    (net (code "6778") (name "unconnected-(SV233-Pad20)") (class "Default")
      (node (ref "SV233") (pin "20") (pinfunction "20_20") (pintype "passive"))
    )
    (net (code "6779") (name "unconnected-(SV233-Pad21)") (class "Default")
      (node (ref "SV233") (pin "21") (pinfunction "21_21") (pintype "passive"))
    )
    (net (code "6780") (name "unconnected-(SV233-Pad22)") (class "Default")
      (node (ref "SV233") (pin "22") (pinfunction "22_22") (pintype "passive"))
    )
    (net (code "6781") (name "unconnected-(SV233-Pad23)") (class "Default")
      (node (ref "SV233") (pin "23") (pinfunction "23_23") (pintype "passive"))
    )
    (net (code "6782") (name "unconnected-(SV233-Pad24)") (class "Default")
      (node (ref "SV233") (pin "24") (pinfunction "24_24") (pintype "passive"))
    )
    (net (code "6783") (name "unconnected-(SV233-Pad25)") (class "Default")
      (node (ref "SV233") (pin "25") (pinfunction "25_25") (pintype "passive"))
    )
    (net (code "6784") (name "unconnected-(SV233-Pad26)") (class "Default")
      (node (ref "SV233") (pin "26") (pinfunction "26_26") (pintype "passive"))
    )
    (net (code "6785") (name "unconnected-(SV233-Pad27)") (class "Default")
      (node (ref "SV233") (pin "27") (pinfunction "27_27") (pintype "passive"))
    )
    (net (code "6786") (name "unconnected-(SV233-Pad28)") (class "Default")
      (node (ref "SV233") (pin "28") (pinfunction "28_28") (pintype "passive"))
    )
    (net (code "6787") (name "unconnected-(SV233-Pad29)") (class "Default")
      (node (ref "SV233") (pin "29") (pinfunction "29_29") (pintype "passive"))
    )
    (net (code "6788") (name "unconnected-(SV233-Pad30)") (class "Default")
      (node (ref "SV233") (pin "30") (pinfunction "30_30") (pintype "passive"))
    )
    (net (code "6789") (name "unconnected-(SV233-Pad31)") (class "Default")
      (node (ref "SV233") (pin "31") (pinfunction "31_31") (pintype "passive"))
    )
    (net (code "6790") (name "unconnected-(SV233-Pad32)") (class "Default")
      (node (ref "SV233") (pin "32") (pinfunction "32_32") (pintype "passive"))
    )
    (net (code "6791") (name "unconnected-(SV233-Pad33)") (class "Default")
      (node (ref "SV233") (pin "33") (pinfunction "33_33") (pintype "passive"))
    )
    (net (code "6792") (name "unconnected-(SV233-Pad34)") (class "Default")
      (node (ref "SV233") (pin "34") (pinfunction "34_34") (pintype "passive"))
    )
    (net (code "6793") (name "unconnected-(SV233-Pad35)") (class "Default")
      (node (ref "SV233") (pin "35") (pinfunction "35_35") (pintype "passive"))
    )
    (net (code "6794") (name "unconnected-(SV233-Pad36)") (class "Default")
      (node (ref "SV233") (pin "36") (pinfunction "36_36") (pintype "passive"))
    )
    (net (code "6795") (name "unconnected-(SV233-Pad37)") (class "Default")
      (node (ref "SV233") (pin "37") (pinfunction "37_37") (pintype "passive"))
    )
    (net (code "6796") (name "unconnected-(SV233-Pad38)") (class "Default")
      (node (ref "SV233") (pin "38") (pinfunction "38_38") (pintype "passive"))
    )
    (net (code "6797") (name "unconnected-(SV233-Pad39)") (class "Default")
      (node (ref "SV233") (pin "39") (pinfunction "39_39") (pintype "passive"))
    )
    (net (code "6798") (name "unconnected-(SV233-Pad40)") (class "Default")
      (node (ref "SV233") (pin "40") (pinfunction "40_40") (pintype "passive"))
    )
    (net (code "6799") (name "unconnected-(SV234-Pad1)") (class "Default")
      (node (ref "SV234") (pin "1") (pinfunction "1_1") (pintype "passive"))
    )
    (net (code "6800") (name "unconnected-(SV234-Pad2)") (class "Default")
      (node (ref "SV234") (pin "2") (pinfunction "2_2") (pintype "passive"))
    )
    (net (code "6801") (name "unconnected-(SV234-Pad3)") (class "Default")
      (node (ref "SV234") (pin "3") (pinfunction "3_3") (pintype "passive"))
    )
    (net (code "6802") (name "unconnected-(SV234-Pad4)") (class "Default")
      (node (ref "SV234") (pin "4") (pinfunction "4_4") (pintype "passive"))
    )
    (net (code "6803") (name "unconnected-(SV234-Pad5)") (class "Default")
      (node (ref "SV234") (pin "5") (pinfunction "5_5") (pintype "passive"))
    )
    (net (code "6804") (name "unconnected-(SV234-Pad6)") (class "Default")
      (node (ref "SV234") (pin "6") (pinfunction "6_6") (pintype "passive"))
    )
    (net (code "6805") (name "unconnected-(SV234-Pad7)") (class "Default")
      (node (ref "SV234") (pin "7") (pinfunction "7_7") (pintype "passive"))
    )
    (net (code "6806") (name "unconnected-(SV234-Pad8)") (class "Default")
      (node (ref "SV234") (pin "8") (pinfunction "8_8") (pintype "passive"))
    )
    (net (code "6807") (name "unconnected-(SV234-Pad9)") (class "Default")
      (node (ref "SV234") (pin "9") (pinfunction "9_9") (pintype "passive"))
    )
    (net (code "6808") (name "unconnected-(SV234-Pad10)") (class "Default")
      (node (ref "SV234") (pin "10") (pinfunction "10_10") (pintype "passive"))
    )
    (net (code "6809") (name "unconnected-(SV234-Pad11)") (class "Default")
      (node (ref "SV234") (pin "11") (pinfunction "11_11") (pintype "passive"))
    )
    (net (code "6810") (name "unconnected-(SV234-Pad12)") (class "Default")
      (node (ref "SV234") (pin "12") (pinfunction "12_12") (pintype "passive"))
    )
    (net (code "6811") (name "unconnected-(SV234-Pad13)") (class "Default")
      (node (ref "SV234") (pin "13") (pinfunction "13_13") (pintype "passive"))
    )
    (net (code "6812") (name "unconnected-(SV234-Pad14)") (class "Default")
      (node (ref "SV234") (pin "14") (pinfunction "14_14") (pintype "passive"))
    )
    (net (code "6813") (name "unconnected-(SV234-Pad15)") (class "Default")
      (node (ref "SV234") (pin "15") (pinfunction "15_15") (pintype "passive"))
    )
    (net (code "6814") (name "unconnected-(SV234-Pad16)") (class "Default")
      (node (ref "SV234") (pin "16") (pinfunction "16_16") (pintype "passive"))
    )
    (net (code "6815") (name "unconnected-(SV234-Pad17)") (class "Default")
      (node (ref "SV234") (pin "17") (pinfunction "17_17") (pintype "passive"))
    )
    (net (code "6816") (name "unconnected-(SV234-Pad18)") (class "Default")
      (node (ref "SV234") (pin "18") (pinfunction "18_18") (pintype "passive"))
    )
    (net (code "6817") (name "unconnected-(SV234-Pad19)") (class "Default")
      (node (ref "SV234") (pin "19") (pinfunction "19_19") (pintype "passive"))
    )
    (net (code "6818") (name "unconnected-(SV234-Pad20)") (class "Default")
      (node (ref "SV234") (pin "20") (pinfunction "20_20") (pintype "passive"))
    )
    (net (code "6819") (name "unconnected-(SV234-Pad21)") (class "Default")
      (node (ref "SV234") (pin "21") (pinfunction "21_21") (pintype "passive"))
    )
    (net (code "6820") (name "unconnected-(SV234-Pad22)") (class "Default")
      (node (ref "SV234") (pin "22") (pinfunction "22_22") (pintype "passive"))
    )
    (net (code "6821") (name "unconnected-(SV234-Pad23)") (class "Default")
      (node (ref "SV234") (pin "23") (pinfunction "23_23") (pintype "passive"))
    )
    (net (code "6822") (name "unconnected-(SV234-Pad24)") (class "Default")
      (node (ref "SV234") (pin "24") (pinfunction "24_24") (pintype "passive"))
    )
    (net (code "6823") (name "unconnected-(SV234-Pad25)") (class "Default")
      (node (ref "SV234") (pin "25") (pinfunction "25_25") (pintype "passive"))
    )
    (net (code "6824") (name "unconnected-(SV234-Pad26)") (class "Default")
      (node (ref "SV234") (pin "26") (pinfunction "26_26") (pintype "passive"))
    )
    (net (code "6825") (name "unconnected-(SV234-Pad27)") (class "Default")
      (node (ref "SV234") (pin "27") (pinfunction "27_27") (pintype "passive"))
    )
    (net (code "6826") (name "unconnected-(SV234-Pad28)") (class "Default")
      (node (ref "SV234") (pin "28") (pinfunction "28_28") (pintype "passive"))
    )
    (net (code "6827") (name "unconnected-(SV234-Pad29)") (class "Default")
      (node (ref "SV234") (pin "29") (pinfunction "29_29") (pintype "passive"))
    )
    (net (code "6828") (name "unconnected-(SV234-Pad30)") (class "Default")
      (node (ref "SV234") (pin "30") (pinfunction "30_30") (pintype "passive"))
    )
    (net (code "6829") (name "unconnected-(SV234-Pad31)") (class "Default")
      (node (ref "SV234") (pin "31") (pinfunction "31_31") (pintype "passive"))
    )
    (net (code "6830") (name "unconnected-(SV234-Pad32)") (class "Default")
      (node (ref "SV234") (pin "32") (pinfunction "32_32") (pintype "passive"))
    )
    (net (code "6831") (name "unconnected-(SV234-Pad33)") (class "Default")
      (node (ref "SV234") (pin "33") (pinfunction "33_33") (pintype "passive"))
    )
    (net (code "6832") (name "unconnected-(SV234-Pad34)") (class "Default")
      (node (ref "SV234") (pin "34") (pinfunction "34_34") (pintype "passive"))
    )
    (net (code "6833") (name "unconnected-(SV234-Pad35)") (class "Default")
      (node (ref "SV234") (pin "35") (pinfunction "35_35") (pintype "passive"))
    )
    (net (code "6834") (name "unconnected-(SV234-Pad36)") (class "Default")
      (node (ref "SV234") (pin "36") (pinfunction "36_36") (pintype "passive"))
    )
    (net (code "6835") (name "unconnected-(SV234-Pad37)") (class "Default")
      (node (ref "SV234") (pin "37") (pinfunction "37_37") (pintype "passive"))
    )
    (net (code "6836") (name "unconnected-(SV234-Pad38)") (class "Default")
      (node (ref "SV234") (pin "38") (pinfunction "38_38") (pintype "passive"))
    )
    (net (code "6837") (name "unconnected-(SV234-Pad39)") (class "Default")
      (node (ref "SV234") (pin "39") (pinfunction "39_39") (pintype "passive"))
    )
    (net (code "6838") (name "unconnected-(SV234-Pad40)") (class "Default")
      (node (ref "SV234") (pin "40") (pinfunction "40_40") (pintype "passive"))
    )
    (net (code "6839") (name "unconnected-(SV235-Pad1)") (class "Default")
      (node (ref "SV235") (pin "1") (pinfunction "1_1") (pintype "passive"))
    )
    (net (code "6840") (name "unconnected-(SV235-Pad2)") (class "Default")
      (node (ref "SV235") (pin "2") (pinfunction "2_2") (pintype "passive"))
    )
    (net (code "6841") (name "unconnected-(SV235-Pad3)") (class "Default")
      (node (ref "SV235") (pin "3") (pinfunction "3_3") (pintype "passive"))
    )
    (net (code "6842") (name "unconnected-(SV235-Pad4)") (class "Default")
      (node (ref "SV235") (pin "4") (pinfunction "4_4") (pintype "passive"))
    )
    (net (code "6843") (name "unconnected-(SV235-Pad5)") (class "Default")
      (node (ref "SV235") (pin "5") (pinfunction "5_5") (pintype "passive"))
    )
    (net (code "6844") (name "unconnected-(SV235-Pad6)") (class "Default")
      (node (ref "SV235") (pin "6") (pinfunction "6_6") (pintype "passive"))
    )
    (net (code "6845") (name "unconnected-(SV235-Pad7)") (class "Default")
      (node (ref "SV235") (pin "7") (pinfunction "7_7") (pintype "passive"))
    )
    (net (code "6846") (name "unconnected-(SV235-Pad8)") (class "Default")
      (node (ref "SV235") (pin "8") (pinfunction "8_8") (pintype "passive"))
    )
    (net (code "6847") (name "unconnected-(SV235-Pad9)") (class "Default")
      (node (ref "SV235") (pin "9") (pinfunction "9_9") (pintype "passive"))
    )
    (net (code "6848") (name "unconnected-(SV235-Pad10)") (class "Default")
      (node (ref "SV235") (pin "10") (pinfunction "10_10") (pintype "passive"))
    )
    (net (code "6849") (name "unconnected-(SV235-Pad11)") (class "Default")
      (node (ref "SV235") (pin "11") (pinfunction "11_11") (pintype "passive"))
    )
    (net (code "6850") (name "unconnected-(SV235-Pad12)") (class "Default")
      (node (ref "SV235") (pin "12") (pinfunction "12_12") (pintype "passive"))
    )
    (net (code "6851") (name "unconnected-(SV235-Pad13)") (class "Default")
      (node (ref "SV235") (pin "13") (pinfunction "13_13") (pintype "passive"))
    )
    (net (code "6852") (name "unconnected-(SV235-Pad14)") (class "Default")
      (node (ref "SV235") (pin "14") (pinfunction "14_14") (pintype "passive"))
    )
    (net (code "6853") (name "unconnected-(SV235-Pad15)") (class "Default")
      (node (ref "SV235") (pin "15") (pinfunction "15_15") (pintype "passive"))
    )
    (net (code "6854") (name "unconnected-(SV235-Pad16)") (class "Default")
      (node (ref "SV235") (pin "16") (pinfunction "16_16") (pintype "passive"))
    )
    (net (code "6855") (name "unconnected-(SV235-Pad17)") (class "Default")
      (node (ref "SV235") (pin "17") (pinfunction "17_17") (pintype "passive"))
    )
    (net (code "6856") (name "unconnected-(SV235-Pad18)") (class "Default")
      (node (ref "SV235") (pin "18") (pinfunction "18_18") (pintype "passive"))
    )
    (net (code "6857") (name "unconnected-(SV235-Pad19)") (class "Default")
      (node (ref "SV235") (pin "19") (pinfunction "19_19") (pintype "passive"))
    )
    (net (code "6858") (name "unconnected-(SV235-Pad20)") (class "Default")
      (node (ref "SV235") (pin "20") (pinfunction "20_20") (pintype "passive"))
    )
    (net (code "6859") (name "unconnected-(SV235-Pad21)") (class "Default")
      (node (ref "SV235") (pin "21") (pinfunction "21_21") (pintype "passive"))
    )
    (net (code "6860") (name "unconnected-(SV235-Pad22)") (class "Default")
      (node (ref "SV235") (pin "22") (pinfunction "22_22") (pintype "passive"))
    )
    (net (code "6861") (name "unconnected-(SV235-Pad23)") (class "Default")
      (node (ref "SV235") (pin "23") (pinfunction "23_23") (pintype "passive"))
    )
    (net (code "6862") (name "unconnected-(SV235-Pad24)") (class "Default")
      (node (ref "SV235") (pin "24") (pinfunction "24_24") (pintype "passive"))
    )
    (net (code "6863") (name "unconnected-(SV236-Pad1)") (class "Default")
      (node (ref "SV236") (pin "1") (pinfunction "1_1") (pintype "passive"))
    )
    (net (code "6864") (name "unconnected-(SV236-Pad2)") (class "Default")
      (node (ref "SV236") (pin "2") (pinfunction "2_2") (pintype "passive"))
    )
    (net (code "6865") (name "unconnected-(SV236-Pad3)") (class "Default")
      (node (ref "SV236") (pin "3") (pinfunction "3_3") (pintype "passive"))
    )
    (net (code "6866") (name "unconnected-(SV236-Pad4)") (class "Default")
      (node (ref "SV236") (pin "4") (pinfunction "4_4") (pintype "passive"))
    )
    (net (code "6867") (name "unconnected-(SV236-Pad5)") (class "Default")
      (node (ref "SV236") (pin "5") (pinfunction "5_5") (pintype "passive"))
    )
    (net (code "6868") (name "unconnected-(SV236-Pad6)") (class "Default")
      (node (ref "SV236") (pin "6") (pinfunction "6_6") (pintype "passive"))
    )
    (net (code "6869") (name "unconnected-(SV236-Pad7)") (class "Default")
      (node (ref "SV236") (pin "7") (pinfunction "7_7") (pintype "passive"))
    )
    (net (code "6870") (name "unconnected-(SV236-Pad8)") (class "Default")
      (node (ref "SV236") (pin "8") (pinfunction "8_8") (pintype "passive"))
    )
    (net (code "6871") (name "unconnected-(SV236-Pad9)") (class "Default")
      (node (ref "SV236") (pin "9") (pinfunction "9_9") (pintype "passive"))
    )
    (net (code "6872") (name "unconnected-(SV236-Pad10)") (class "Default")
      (node (ref "SV236") (pin "10") (pinfunction "10_10") (pintype "passive"))
    )
    (net (code "6873") (name "unconnected-(SV236-Pad11)") (class "Default")
      (node (ref "SV236") (pin "11") (pinfunction "11_11") (pintype "passive"))
    )
    (net (code "6874") (name "unconnected-(SV236-Pad12)") (class "Default")
      (node (ref "SV236") (pin "12") (pinfunction "12_12") (pintype "passive"))
    )
    (net (code "6875") (name "unconnected-(SV236-Pad13)") (class "Default")
      (node (ref "SV236") (pin "13") (pinfunction "13_13") (pintype "passive"))
    )
    (net (code "6876") (name "unconnected-(SV236-Pad14)") (class "Default")
      (node (ref "SV236") (pin "14") (pinfunction "14_14") (pintype "passive"))
    )
    (net (code "6877") (name "unconnected-(SV236-Pad15)") (class "Default")
      (node (ref "SV236") (pin "15") (pinfunction "15_15") (pintype "passive"))
    )
    (net (code "6878") (name "unconnected-(SV236-Pad16)") (class "Default")
      (node (ref "SV236") (pin "16") (pinfunction "16_16") (pintype "passive"))
    )
    (net (code "6879") (name "unconnected-(SV236-Pad17)") (class "Default")
      (node (ref "SV236") (pin "17") (pinfunction "17_17") (pintype "passive"))
    )
    (net (code "6880") (name "unconnected-(SV236-Pad18)") (class "Default")
      (node (ref "SV236") (pin "18") (pinfunction "18_18") (pintype "passive"))
    )
    (net (code "6881") (name "unconnected-(SV236-Pad19)") (class "Default")
      (node (ref "SV236") (pin "19") (pinfunction "19_19") (pintype "passive"))
    )
    (net (code "6882") (name "unconnected-(SV236-Pad20)") (class "Default")
      (node (ref "SV236") (pin "20") (pinfunction "20_20") (pintype "passive"))
    )
    (net (code "6883") (name "unconnected-(SV236-Pad21)") (class "Default")
      (node (ref "SV236") (pin "21") (pinfunction "21_21") (pintype "passive"))
    )
    (net (code "6884") (name "unconnected-(SV236-Pad22)") (class "Default")
      (node (ref "SV236") (pin "22") (pinfunction "22_22") (pintype "passive"))
    )
    (net (code "6885") (name "unconnected-(SV236-Pad23)") (class "Default")
      (node (ref "SV236") (pin "23") (pinfunction "23_23") (pintype "passive"))
    )
    (net (code "6886") (name "unconnected-(SV236-Pad24)") (class "Default")
      (node (ref "SV236") (pin "24") (pinfunction "24_24") (pintype "passive"))
    )
    (net (code "6887") (name "unconnected-(SV237-Pad1)") (class "Default")
      (node (ref "SV237") (pin "1") (pinfunction "1_1") (pintype "passive"))
    )
    (net (code "6888") (name "unconnected-(SV237-Pad2)") (class "Default")
      (node (ref "SV237") (pin "2") (pinfunction "2_2") (pintype "passive"))
    )
    (net (code "6889") (name "unconnected-(SV237-Pad3)") (class "Default")
      (node (ref "SV237") (pin "3") (pinfunction "3_3") (pintype "passive"))
    )
    (net (code "6890") (name "unconnected-(SV237-Pad4)") (class "Default")
      (node (ref "SV237") (pin "4") (pinfunction "4_4") (pintype "passive"))
    )
    (net (code "6891") (name "unconnected-(SV237-Pad5)") (class "Default")
      (node (ref "SV237") (pin "5") (pinfunction "5_5") (pintype "passive"))
    )
    (net (code "6892") (name "unconnected-(SV237-Pad6)") (class "Default")
      (node (ref "SV237") (pin "6") (pinfunction "6_6") (pintype "passive"))
    )
    (net (code "6893") (name "unconnected-(SV237-Pad7)") (class "Default")
      (node (ref "SV237") (pin "7") (pinfunction "7_7") (pintype "passive"))
    )
    (net (code "6894") (name "unconnected-(SV237-Pad8)") (class "Default")
      (node (ref "SV237") (pin "8") (pinfunction "8_8") (pintype "passive"))
    )
    (net (code "6895") (name "unconnected-(SV237-Pad9)") (class "Default")
      (node (ref "SV237") (pin "9") (pinfunction "9_9") (pintype "passive"))
    )
    (net (code "6896") (name "unconnected-(SV237-Pad10)") (class "Default")
      (node (ref "SV237") (pin "10") (pinfunction "10_10") (pintype "passive"))
    )
    (net (code "6897") (name "unconnected-(SV237-Pad11)") (class "Default")
      (node (ref "SV237") (pin "11") (pinfunction "11_11") (pintype "passive"))
    )
    (net (code "6898") (name "unconnected-(SV237-Pad12)") (class "Default")
      (node (ref "SV237") (pin "12") (pinfunction "12_12") (pintype "passive"))
    )
    (net (code "6899") (name "unconnected-(SV237-Pad13)") (class "Default")
      (node (ref "SV237") (pin "13") (pinfunction "13_13") (pintype "passive"))
    )
    (net (code "6900") (name "unconnected-(SV237-Pad14)") (class "Default")
      (node (ref "SV237") (pin "14") (pinfunction "14_14") (pintype "passive"))
    )
    (net (code "6901") (name "unconnected-(SV237-Pad15)") (class "Default")
      (node (ref "SV237") (pin "15") (pinfunction "15_15") (pintype "passive"))
    )
    (net (code "6902") (name "unconnected-(SV237-Pad16)") (class "Default")
      (node (ref "SV237") (pin "16") (pinfunction "16_16") (pintype "passive"))
    )
    (net (code "6903") (name "unconnected-(SV237-Pad17)") (class "Default")
      (node (ref "SV237") (pin "17") (pinfunction "17_17") (pintype "passive"))
    )
    (net (code "6904") (name "unconnected-(SV237-Pad18)") (class "Default")
      (node (ref "SV237") (pin "18") (pinfunction "18_18") (pintype "passive"))
    )
    (net (code "6905") (name "unconnected-(SV237-Pad19)") (class "Default")
      (node (ref "SV237") (pin "19") (pinfunction "19_19") (pintype "passive"))
    )
    (net (code "6906") (name "unconnected-(SV237-Pad20)") (class "Default")
      (node (ref "SV237") (pin "20") (pinfunction "20_20") (pintype "passive"))
    )
    (net (code "6907") (name "unconnected-(SV237-Pad21)") (class "Default")
      (node (ref "SV237") (pin "21") (pinfunction "21_21") (pintype "passive"))
    )
    (net (code "6908") (name "unconnected-(SV237-Pad22)") (class "Default")
      (node (ref "SV237") (pin "22") (pinfunction "22_22") (pintype "passive"))
    )
    (net (code "6909") (name "unconnected-(SV237-Pad23)") (class "Default")
      (node (ref "SV237") (pin "23") (pinfunction "23_23") (pintype "passive"))
    )
    (net (code "6910") (name "unconnected-(SV237-Pad24)") (class "Default")
      (node (ref "SV237") (pin "24") (pinfunction "24_24") (pintype "passive"))
    )
    (net (code "6911") (name "unconnected-(SV238-Pad1)") (class "Default")
      (node (ref "SV238") (pin "1") (pinfunction "1_1") (pintype "passive"))
    )
    (net (code "6912") (name "unconnected-(SV238-Pad2)") (class "Default")
      (node (ref "SV238") (pin "2") (pinfunction "2_2") (pintype "passive"))
    )
    (net (code "6913") (name "unconnected-(SV238-Pad3)") (class "Default")
      (node (ref "SV238") (pin "3") (pinfunction "3_3") (pintype "passive"))
    )
    (net (code "6914") (name "unconnected-(SV238-Pad4)") (class "Default")
      (node (ref "SV238") (pin "4") (pinfunction "4_4") (pintype "passive"))
    )
    (net (code "6915") (name "unconnected-(SV238-Pad5)") (class "Default")
      (node (ref "SV238") (pin "5") (pinfunction "5_5") (pintype "passive"))
    )
    (net (code "6916") (name "unconnected-(SV238-Pad6)") (class "Default")
      (node (ref "SV238") (pin "6") (pinfunction "6_6") (pintype "passive"))
    )
    (net (code "6917") (name "unconnected-(SV238-Pad7)") (class "Default")
      (node (ref "SV238") (pin "7") (pinfunction "7_7") (pintype "passive"))
    )
    (net (code "6918") (name "unconnected-(SV238-Pad8)") (class "Default")
      (node (ref "SV238") (pin "8") (pinfunction "8_8") (pintype "passive"))
    )
    (net (code "6919") (name "unconnected-(SV238-Pad9)") (class "Default")
      (node (ref "SV238") (pin "9") (pinfunction "9_9") (pintype "passive"))
    )
    (net (code "6920") (name "unconnected-(SV238-Pad10)") (class "Default")
      (node (ref "SV238") (pin "10") (pinfunction "10_10") (pintype "passive"))
    )
    (net (code "6921") (name "unconnected-(SV238-Pad11)") (class "Default")
      (node (ref "SV238") (pin "11") (pinfunction "11_11") (pintype "passive"))
    )
    (net (code "6922") (name "unconnected-(SV238-Pad12)") (class "Default")
      (node (ref "SV238") (pin "12") (pinfunction "12_12") (pintype "passive"))
    )
    (net (code "6923") (name "unconnected-(SV238-Pad13)") (class "Default")
      (node (ref "SV238") (pin "13") (pinfunction "13_13") (pintype "passive"))
    )
    (net (code "6924") (name "unconnected-(SV238-Pad14)") (class "Default")
      (node (ref "SV238") (pin "14") (pinfunction "14_14") (pintype "passive"))
    )
    (net (code "6925") (name "unconnected-(SV238-Pad15)") (class "Default")
      (node (ref "SV238") (pin "15") (pinfunction "15_15") (pintype "passive"))
    )
    (net (code "6926") (name "unconnected-(SV238-Pad16)") (class "Default")
      (node (ref "SV238") (pin "16") (pinfunction "16_16") (pintype "passive"))
    )
    (net (code "6927") (name "unconnected-(SV238-Pad17)") (class "Default")
      (node (ref "SV238") (pin "17") (pinfunction "17_17") (pintype "passive"))
    )
    (net (code "6928") (name "unconnected-(SV238-Pad18)") (class "Default")
      (node (ref "SV238") (pin "18") (pinfunction "18_18") (pintype "passive"))
    )
    (net (code "6929") (name "unconnected-(SV238-Pad19)") (class "Default")
      (node (ref "SV238") (pin "19") (pinfunction "19_19") (pintype "passive"))
    )
    (net (code "6930") (name "unconnected-(SV238-Pad20)") (class "Default")
      (node (ref "SV238") (pin "20") (pinfunction "20_20") (pintype "passive"))
    )
    (net (code "6931") (name "unconnected-(SV238-Pad21)") (class "Default")
      (node (ref "SV238") (pin "21") (pinfunction "21_21") (pintype "passive"))
    )
    (net (code "6932") (name "unconnected-(SV238-Pad22)") (class "Default")
      (node (ref "SV238") (pin "22") (pinfunction "22_22") (pintype "passive"))
    )
    (net (code "6933") (name "unconnected-(SV238-Pad23)") (class "Default")
      (node (ref "SV238") (pin "23") (pinfunction "23_23") (pintype "passive"))
    )
    (net (code "6934") (name "unconnected-(SV238-Pad24)") (class "Default")
      (node (ref "SV238") (pin "24") (pinfunction "24_24") (pintype "passive"))
    )
    (net (code "6935") (name "unconnected-(SV239-Pad1)") (class "Default")
      (node (ref "SV239") (pin "1") (pinfunction "1_1") (pintype "passive"))
    )
    (net (code "6936") (name "unconnected-(SV239-Pad2)") (class "Default")
      (node (ref "SV239") (pin "2") (pinfunction "2_2") (pintype "passive"))
    )
    (net (code "6937") (name "unconnected-(SV239-Pad3)") (class "Default")
      (node (ref "SV239") (pin "3") (pinfunction "3_3") (pintype "passive"))
    )
    (net (code "6938") (name "unconnected-(SV239-Pad4)") (class "Default")
      (node (ref "SV239") (pin "4") (pinfunction "4_4") (pintype "passive"))
    )
    (net (code "6939") (name "unconnected-(SV239-Pad5)") (class "Default")
      (node (ref "SV239") (pin "5") (pinfunction "5_5") (pintype "passive"))
    )
    (net (code "6940") (name "unconnected-(SV239-Pad6)") (class "Default")
      (node (ref "SV239") (pin "6") (pinfunction "6_6") (pintype "passive"))
    )
    (net (code "6941") (name "unconnected-(SV239-Pad7)") (class "Default")
      (node (ref "SV239") (pin "7") (pinfunction "7_7") (pintype "passive"))
    )
    (net (code "6942") (name "unconnected-(SV239-Pad8)") (class "Default")
      (node (ref "SV239") (pin "8") (pinfunction "8_8") (pintype "passive"))
    )
    (net (code "6943") (name "unconnected-(SV239-Pad9)") (class "Default")
      (node (ref "SV239") (pin "9") (pinfunction "9_9") (pintype "passive"))
    )
    (net (code "6944") (name "unconnected-(SV239-Pad10)") (class "Default")
      (node (ref "SV239") (pin "10") (pinfunction "10_10") (pintype "passive"))
    )
    (net (code "6945") (name "unconnected-(SV239-Pad11)") (class "Default")
      (node (ref "SV239") (pin "11") (pinfunction "11_11") (pintype "passive"))
    )
    (net (code "6946") (name "unconnected-(SV239-Pad12)") (class "Default")
      (node (ref "SV239") (pin "12") (pinfunction "12_12") (pintype "passive"))
    )
    (net (code "6947") (name "unconnected-(SV239-Pad13)") (class "Default")
      (node (ref "SV239") (pin "13") (pinfunction "13_13") (pintype "passive"))
    )
    (net (code "6948") (name "unconnected-(SV239-Pad14)") (class "Default")
      (node (ref "SV239") (pin "14") (pinfunction "14_14") (pintype "passive"))
    )
    (net (code "6949") (name "unconnected-(SV239-Pad15)") (class "Default")
      (node (ref "SV239") (pin "15") (pinfunction "15_15") (pintype "passive"))
    )
    (net (code "6950") (name "unconnected-(SV239-Pad16)") (class "Default")
      (node (ref "SV239") (pin "16") (pinfunction "16_16") (pintype "passive"))
    )
    (net (code "6951") (name "unconnected-(SV239-Pad17)") (class "Default")
      (node (ref "SV239") (pin "17") (pinfunction "17_17") (pintype "passive"))
    )
    (net (code "6952") (name "unconnected-(SV239-Pad18)") (class "Default")
      (node (ref "SV239") (pin "18") (pinfunction "18_18") (pintype "passive"))
    )
    (net (code "6953") (name "unconnected-(SV239-Pad19)") (class "Default")
      (node (ref "SV239") (pin "19") (pinfunction "19_19") (pintype "passive"))
    )
    (net (code "6954") (name "unconnected-(SV239-Pad20)") (class "Default")
      (node (ref "SV239") (pin "20") (pinfunction "20_20") (pintype "passive"))
    )
    (net (code "6955") (name "unconnected-(SV239-Pad21)") (class "Default")
      (node (ref "SV239") (pin "21") (pinfunction "21_21") (pintype "passive"))
    )
    (net (code "6956") (name "unconnected-(SV239-Pad22)") (class "Default")
      (node (ref "SV239") (pin "22") (pinfunction "22_22") (pintype "passive"))
    )
    (net (code "6957") (name "unconnected-(SV239-Pad23)") (class "Default")
      (node (ref "SV239") (pin "23") (pinfunction "23_23") (pintype "passive"))
    )
    (net (code "6958") (name "unconnected-(SV239-Pad24)") (class "Default")
      (node (ref "SV239") (pin "24") (pinfunction "24_24") (pintype "passive"))
    )
    (net (code "6959") (name "unconnected-(SV239-Pad25)") (class "Default")
      (node (ref "SV239") (pin "25") (pinfunction "25_25") (pintype "passive"))
    )
    (net (code "6960") (name "unconnected-(SV239-Pad26)") (class "Default")
      (node (ref "SV239") (pin "26") (pinfunction "26_26") (pintype "passive"))
    )
    (net (code "6961") (name "unconnected-(SV239-Pad27)") (class "Default")
      (node (ref "SV239") (pin "27") (pinfunction "27_27") (pintype "passive"))
    )
    (net (code "6962") (name "unconnected-(SV239-Pad28)") (class "Default")
      (node (ref "SV239") (pin "28") (pinfunction "28_28") (pintype "passive"))
    )
    (net (code "6963") (name "unconnected-(SV239-Pad29)") (class "Default")
      (node (ref "SV239") (pin "29") (pinfunction "29_29") (pintype "passive"))
    )
    (net (code "6964") (name "unconnected-(SV239-Pad30)") (class "Default")
      (node (ref "SV239") (pin "30") (pinfunction "30_30") (pintype "passive"))
    )
    (net (code "6965") (name "unconnected-(SV239-Pad31)") (class "Default")
      (node (ref "SV239") (pin "31") (pinfunction "31_31") (pintype "passive"))
    )
    (net (code "6966") (name "unconnected-(SV239-Pad32)") (class "Default")
      (node (ref "SV239") (pin "32") (pinfunction "32_32") (pintype "passive"))
    )
    (net (code "6967") (name "unconnected-(SV239-Pad33)") (class "Default")
      (node (ref "SV239") (pin "33") (pinfunction "33_33") (pintype "passive"))
    )
    (net (code "6968") (name "unconnected-(SV239-Pad34)") (class "Default")
      (node (ref "SV239") (pin "34") (pinfunction "34_34") (pintype "passive"))
    )
    (net (code "6969") (name "unconnected-(SV239-Pad35)") (class "Default")
      (node (ref "SV239") (pin "35") (pinfunction "35_35") (pintype "passive"))
    )
    (net (code "6970") (name "unconnected-(SV239-Pad36)") (class "Default")
      (node (ref "SV239") (pin "36") (pinfunction "36_36") (pintype "passive"))
    )
    (net (code "6971") (name "unconnected-(SV239-Pad37)") (class "Default")
      (node (ref "SV239") (pin "37") (pinfunction "37_37") (pintype "passive"))
    )
    (net (code "6972") (name "unconnected-(SV239-Pad38)") (class "Default")
      (node (ref "SV239") (pin "38") (pinfunction "38_38") (pintype "passive"))
    )
    (net (code "6973") (name "unconnected-(SV239-Pad39)") (class "Default")
      (node (ref "SV239") (pin "39") (pinfunction "39_39") (pintype "passive"))
    )
    (net (code "6974") (name "unconnected-(SV239-Pad40)") (class "Default")
      (node (ref "SV239") (pin "40") (pinfunction "40_40") (pintype "passive"))
    )
    (net (code "6975") (name "unconnected-(SV240-Pad1)") (class "Default")
      (node (ref "SV240") (pin "1") (pinfunction "1_1") (pintype "passive"))
    )
    (net (code "6976") (name "unconnected-(SV240-Pad2)") (class "Default")
      (node (ref "SV240") (pin "2") (pinfunction "2_2") (pintype "passive"))
    )
    (net (code "6977") (name "unconnected-(SV240-Pad3)") (class "Default")
      (node (ref "SV240") (pin "3") (pinfunction "3_3") (pintype "passive"))
    )
    (net (code "6978") (name "unconnected-(SV240-Pad4)") (class "Default")
      (node (ref "SV240") (pin "4") (pinfunction "4_4") (pintype "passive"))
    )
    (net (code "6979") (name "unconnected-(SV240-Pad5)") (class "Default")
      (node (ref "SV240") (pin "5") (pinfunction "5_5") (pintype "passive"))
    )
    (net (code "6980") (name "unconnected-(SV240-Pad6)") (class "Default")
      (node (ref "SV240") (pin "6") (pinfunction "6_6") (pintype "passive"))
    )
    (net (code "6981") (name "unconnected-(SV240-Pad7)") (class "Default")
      (node (ref "SV240") (pin "7") (pinfunction "7_7") (pintype "passive"))
    )
    (net (code "6982") (name "unconnected-(SV240-Pad8)") (class "Default")
      (node (ref "SV240") (pin "8") (pinfunction "8_8") (pintype "passive"))
    )
    (net (code "6983") (name "unconnected-(SV240-Pad9)") (class "Default")
      (node (ref "SV240") (pin "9") (pinfunction "9_9") (pintype "passive"))
    )
    (net (code "6984") (name "unconnected-(SV240-Pad10)") (class "Default")
      (node (ref "SV240") (pin "10") (pinfunction "10_10") (pintype "passive"))
    )
    (net (code "6985") (name "unconnected-(SV240-Pad11)") (class "Default")
      (node (ref "SV240") (pin "11") (pinfunction "11_11") (pintype "passive"))
    )
    (net (code "6986") (name "unconnected-(SV240-Pad12)") (class "Default")
      (node (ref "SV240") (pin "12") (pinfunction "12_12") (pintype "passive"))
    )
    (net (code "6987") (name "unconnected-(SV240-Pad13)") (class "Default")
      (node (ref "SV240") (pin "13") (pinfunction "13_13") (pintype "passive"))
    )
    (net (code "6988") (name "unconnected-(SV240-Pad14)") (class "Default")
      (node (ref "SV240") (pin "14") (pinfunction "14_14") (pintype "passive"))
    )
    (net (code "6989") (name "unconnected-(SV240-Pad15)") (class "Default")
      (node (ref "SV240") (pin "15") (pinfunction "15_15") (pintype "passive"))
    )
    (net (code "6990") (name "unconnected-(SV240-Pad16)") (class "Default")
      (node (ref "SV240") (pin "16") (pinfunction "16_16") (pintype "passive"))
    )
    (net (code "6991") (name "unconnected-(SV240-Pad17)") (class "Default")
      (node (ref "SV240") (pin "17") (pinfunction "17_17") (pintype "passive"))
    )
    (net (code "6992") (name "unconnected-(SV240-Pad18)") (class "Default")
      (node (ref "SV240") (pin "18") (pinfunction "18_18") (pintype "passive"))
    )
    (net (code "6993") (name "unconnected-(SV240-Pad19)") (class "Default")
      (node (ref "SV240") (pin "19") (pinfunction "19_19") (pintype "passive"))
    )
    (net (code "6994") (name "unconnected-(SV240-Pad20)") (class "Default")
      (node (ref "SV240") (pin "20") (pinfunction "20_20") (pintype "passive"))
    )
    (net (code "6995") (name "unconnected-(SV240-Pad21)") (class "Default")
      (node (ref "SV240") (pin "21") (pinfunction "21_21") (pintype "passive"))
    )
    (net (code "6996") (name "unconnected-(SV240-Pad22)") (class "Default")
      (node (ref "SV240") (pin "22") (pinfunction "22_22") (pintype "passive"))
    )
    (net (code "6997") (name "unconnected-(SV240-Pad23)") (class "Default")
      (node (ref "SV240") (pin "23") (pinfunction "23_23") (pintype "passive"))
    )
    (net (code "6998") (name "unconnected-(SV240-Pad24)") (class "Default")
      (node (ref "SV240") (pin "24") (pinfunction "24_24") (pintype "passive"))
    )
    (net (code "6999") (name "unconnected-(SV240-Pad25)") (class "Default")
      (node (ref "SV240") (pin "25") (pinfunction "25_25") (pintype "passive"))
    )
    (net (code "7000") (name "unconnected-(SV240-Pad26)") (class "Default")
      (node (ref "SV240") (pin "26") (pinfunction "26_26") (pintype "passive"))
    )
    (net (code "7001") (name "unconnected-(SV240-Pad27)") (class "Default")
      (node (ref "SV240") (pin "27") (pinfunction "27_27") (pintype "passive"))
    )
    (net (code "7002") (name "unconnected-(SV240-Pad28)") (class "Default")
      (node (ref "SV240") (pin "28") (pinfunction "28_28") (pintype "passive"))
    )
    (net (code "7003") (name "unconnected-(SV240-Pad29)") (class "Default")
      (node (ref "SV240") (pin "29") (pinfunction "29_29") (pintype "passive"))
    )
    (net (code "7004") (name "unconnected-(SV240-Pad30)") (class "Default")
      (node (ref "SV240") (pin "30") (pinfunction "30_30") (pintype "passive"))
    )
    (net (code "7005") (name "unconnected-(SV240-Pad31)") (class "Default")
      (node (ref "SV240") (pin "31") (pinfunction "31_31") (pintype "passive"))
    )
    (net (code "7006") (name "unconnected-(SV240-Pad32)") (class "Default")
      (node (ref "SV240") (pin "32") (pinfunction "32_32") (pintype "passive"))
    )
    (net (code "7007") (name "unconnected-(SV240-Pad33)") (class "Default")
      (node (ref "SV240") (pin "33") (pinfunction "33_33") (pintype "passive"))
    )
    (net (code "7008") (name "unconnected-(SV240-Pad34)") (class "Default")
      (node (ref "SV240") (pin "34") (pinfunction "34_34") (pintype "passive"))
    )
    (net (code "7009") (name "unconnected-(SV240-Pad35)") (class "Default")
      (node (ref "SV240") (pin "35") (pinfunction "35_35") (pintype "passive"))
    )
    (net (code "7010") (name "unconnected-(SV240-Pad36)") (class "Default")
      (node (ref "SV240") (pin "36") (pinfunction "36_36") (pintype "passive"))
    )
    (net (code "7011") (name "unconnected-(SV240-Pad37)") (class "Default")
      (node (ref "SV240") (pin "37") (pinfunction "37_37") (pintype "passive"))
    )
    (net (code "7012") (name "unconnected-(SV240-Pad38)") (class "Default")
      (node (ref "SV240") (pin "38") (pinfunction "38_38") (pintype "passive"))
    )
    (net (code "7013") (name "unconnected-(SV240-Pad39)") (class "Default")
      (node (ref "SV240") (pin "39") (pinfunction "39_39") (pintype "passive"))
    )
    (net (code "7014") (name "unconnected-(SV240-Pad40)") (class "Default")
      (node (ref "SV240") (pin "40") (pinfunction "40_40") (pintype "passive"))
    )
    (net (code "7015") (name "unconnected-(SV241-Pad1)") (class "Default")
      (node (ref "SV241") (pin "1") (pinfunction "1_1") (pintype "passive"))
    )
    (net (code "7016") (name "unconnected-(SV241-Pad2)") (class "Default")
      (node (ref "SV241") (pin "2") (pinfunction "2_2") (pintype "passive"))
    )
    (net (code "7017") (name "unconnected-(SV241-Pad3)") (class "Default")
      (node (ref "SV241") (pin "3") (pinfunction "3_3") (pintype "passive"))
    )
    (net (code "7018") (name "unconnected-(SV241-Pad4)") (class "Default")
      (node (ref "SV241") (pin "4") (pinfunction "4_4") (pintype "passive"))
    )
    (net (code "7019") (name "unconnected-(SV241-Pad5)") (class "Default")
      (node (ref "SV241") (pin "5") (pinfunction "5_5") (pintype "passive"))
    )
    (net (code "7020") (name "unconnected-(SV241-Pad6)") (class "Default")
      (node (ref "SV241") (pin "6") (pinfunction "6_6") (pintype "passive"))
    )
    (net (code "7021") (name "unconnected-(SV241-Pad7)") (class "Default")
      (node (ref "SV241") (pin "7") (pinfunction "7_7") (pintype "passive"))
    )
    (net (code "7022") (name "unconnected-(SV241-Pad8)") (class "Default")
      (node (ref "SV241") (pin "8") (pinfunction "8_8") (pintype "passive"))
    )
    (net (code "7023") (name "unconnected-(SV241-Pad9)") (class "Default")
      (node (ref "SV241") (pin "9") (pinfunction "9_9") (pintype "passive"))
    )
    (net (code "7024") (name "unconnected-(SV241-Pad10)") (class "Default")
      (node (ref "SV241") (pin "10") (pinfunction "10_10") (pintype "passive"))
    )
    (net (code "7025") (name "unconnected-(SV241-Pad11)") (class "Default")
      (node (ref "SV241") (pin "11") (pinfunction "11_11") (pintype "passive"))
    )
    (net (code "7026") (name "unconnected-(SV241-Pad12)") (class "Default")
      (node (ref "SV241") (pin "12") (pinfunction "12_12") (pintype "passive"))
    )
    (net (code "7027") (name "unconnected-(SV241-Pad13)") (class "Default")
      (node (ref "SV241") (pin "13") (pinfunction "13_13") (pintype "passive"))
    )
    (net (code "7028") (name "unconnected-(SV241-Pad14)") (class "Default")
      (node (ref "SV241") (pin "14") (pinfunction "14_14") (pintype "passive"))
    )
    (net (code "7029") (name "unconnected-(SV241-Pad15)") (class "Default")
      (node (ref "SV241") (pin "15") (pinfunction "15_15") (pintype "passive"))
    )
    (net (code "7030") (name "unconnected-(SV241-Pad16)") (class "Default")
      (node (ref "SV241") (pin "16") (pinfunction "16_16") (pintype "passive"))
    )
    (net (code "7031") (name "unconnected-(SV241-Pad17)") (class "Default")
      (node (ref "SV241") (pin "17") (pinfunction "17_17") (pintype "passive"))
    )
    (net (code "7032") (name "unconnected-(SV241-Pad18)") (class "Default")
      (node (ref "SV241") (pin "18") (pinfunction "18_18") (pintype "passive"))
    )
    (net (code "7033") (name "unconnected-(SV241-Pad19)") (class "Default")
      (node (ref "SV241") (pin "19") (pinfunction "19_19") (pintype "passive"))
    )
    (net (code "7034") (name "unconnected-(SV241-Pad20)") (class "Default")
      (node (ref "SV241") (pin "20") (pinfunction "20_20") (pintype "passive"))
    )
    (net (code "7035") (name "unconnected-(SV241-Pad21)") (class "Default")
      (node (ref "SV241") (pin "21") (pinfunction "21_21") (pintype "passive"))
    )
    (net (code "7036") (name "unconnected-(SV241-Pad22)") (class "Default")
      (node (ref "SV241") (pin "22") (pinfunction "22_22") (pintype "passive"))
    )
    (net (code "7037") (name "unconnected-(SV241-Pad23)") (class "Default")
      (node (ref "SV241") (pin "23") (pinfunction "23_23") (pintype "passive"))
    )
    (net (code "7038") (name "unconnected-(SV241-Pad24)") (class "Default")
      (node (ref "SV241") (pin "24") (pinfunction "24_24") (pintype "passive"))
    )
    (net (code "7039") (name "unconnected-(SV241-Pad25)") (class "Default")
      (node (ref "SV241") (pin "25") (pinfunction "25_25") (pintype "passive"))
    )
    (net (code "7040") (name "unconnected-(SV241-Pad26)") (class "Default")
      (node (ref "SV241") (pin "26") (pinfunction "26_26") (pintype "passive"))
    )
    (net (code "7041") (name "unconnected-(SV241-Pad27)") (class "Default")
      (node (ref "SV241") (pin "27") (pinfunction "27_27") (pintype "passive"))
    )
    (net (code "7042") (name "unconnected-(SV241-Pad28)") (class "Default")
      (node (ref "SV241") (pin "28") (pinfunction "28_28") (pintype "passive"))
    )
    (net (code "7043") (name "unconnected-(SV241-Pad29)") (class "Default")
      (node (ref "SV241") (pin "29") (pinfunction "29_29") (pintype "passive"))
    )
    (net (code "7044") (name "unconnected-(SV241-Pad30)") (class "Default")
      (node (ref "SV241") (pin "30") (pinfunction "30_30") (pintype "passive"))
    )
    (net (code "7045") (name "unconnected-(SV241-Pad31)") (class "Default")
      (node (ref "SV241") (pin "31") (pinfunction "31_31") (pintype "passive"))
    )
    (net (code "7046") (name "unconnected-(SV241-Pad32)") (class "Default")
      (node (ref "SV241") (pin "32") (pinfunction "32_32") (pintype "passive"))
    )
    (net (code "7047") (name "unconnected-(SV241-Pad33)") (class "Default")
      (node (ref "SV241") (pin "33") (pinfunction "33_33") (pintype "passive"))
    )
    (net (code "7048") (name "unconnected-(SV241-Pad34)") (class "Default")
      (node (ref "SV241") (pin "34") (pinfunction "34_34") (pintype "passive"))
    )
    (net (code "7049") (name "unconnected-(SV241-Pad35)") (class "Default")
      (node (ref "SV241") (pin "35") (pinfunction "35_35") (pintype "passive"))
    )
    (net (code "7050") (name "unconnected-(SV241-Pad36)") (class "Default")
      (node (ref "SV241") (pin "36") (pinfunction "36_36") (pintype "passive"))
    )
    (net (code "7051") (name "unconnected-(SV241-Pad37)") (class "Default")
      (node (ref "SV241") (pin "37") (pinfunction "37_37") (pintype "passive"))
    )
    (net (code "7052") (name "unconnected-(SV241-Pad38)") (class "Default")
      (node (ref "SV241") (pin "38") (pinfunction "38_38") (pintype "passive"))
    )
    (net (code "7053") (name "unconnected-(SV241-Pad39)") (class "Default")
      (node (ref "SV241") (pin "39") (pinfunction "39_39") (pintype "passive"))
    )
    (net (code "7054") (name "unconnected-(SV241-Pad40)") (class "Default")
      (node (ref "SV241") (pin "40") (pinfunction "40_40") (pintype "passive"))
    )
    (net (code "7055") (name "unconnected-(SV242-Pad1)") (class "Default")
      (node (ref "SV242") (pin "1") (pinfunction "1_1") (pintype "passive"))
    )
    (net (code "7056") (name "unconnected-(SV242-Pad2)") (class "Default")
      (node (ref "SV242") (pin "2") (pinfunction "2_2") (pintype "passive"))
    )
    (net (code "7057") (name "unconnected-(SV242-Pad3)") (class "Default")
      (node (ref "SV242") (pin "3") (pinfunction "3_3") (pintype "passive"))
    )
    (net (code "7058") (name "unconnected-(SV242-Pad4)") (class "Default")
      (node (ref "SV242") (pin "4") (pinfunction "4_4") (pintype "passive"))
    )
    (net (code "7059") (name "unconnected-(SV242-Pad5)") (class "Default")
      (node (ref "SV242") (pin "5") (pinfunction "5_5") (pintype "passive"))
    )
    (net (code "7060") (name "unconnected-(SV242-Pad6)") (class "Default")
      (node (ref "SV242") (pin "6") (pinfunction "6_6") (pintype "passive"))
    )
    (net (code "7061") (name "unconnected-(SV242-Pad7)") (class "Default")
      (node (ref "SV242") (pin "7") (pinfunction "7_7") (pintype "passive"))
    )
    (net (code "7062") (name "unconnected-(SV242-Pad8)") (class "Default")
      (node (ref "SV242") (pin "8") (pinfunction "8_8") (pintype "passive"))
    )
    (net (code "7063") (name "unconnected-(SV242-Pad9)") (class "Default")
      (node (ref "SV242") (pin "9") (pinfunction "9_9") (pintype "passive"))
    )
    (net (code "7064") (name "unconnected-(SV242-Pad10)") (class "Default")
      (node (ref "SV242") (pin "10") (pinfunction "10_10") (pintype "passive"))
    )
    (net (code "7065") (name "unconnected-(SV242-Pad11)") (class "Default")
      (node (ref "SV242") (pin "11") (pinfunction "11_11") (pintype "passive"))
    )
    (net (code "7066") (name "unconnected-(SV242-Pad12)") (class "Default")
      (node (ref "SV242") (pin "12") (pinfunction "12_12") (pintype "passive"))
    )
    (net (code "7067") (name "unconnected-(SV242-Pad13)") (class "Default")
      (node (ref "SV242") (pin "13") (pinfunction "13_13") (pintype "passive"))
    )
    (net (code "7068") (name "unconnected-(SV242-Pad14)") (class "Default")
      (node (ref "SV242") (pin "14") (pinfunction "14_14") (pintype "passive"))
    )
    (net (code "7069") (name "unconnected-(SV242-Pad15)") (class "Default")
      (node (ref "SV242") (pin "15") (pinfunction "15_15") (pintype "passive"))
    )
    (net (code "7070") (name "unconnected-(SV242-Pad16)") (class "Default")
      (node (ref "SV242") (pin "16") (pinfunction "16_16") (pintype "passive"))
    )
    (net (code "7071") (name "unconnected-(SV242-Pad17)") (class "Default")
      (node (ref "SV242") (pin "17") (pinfunction "17_17") (pintype "passive"))
    )
    (net (code "7072") (name "unconnected-(SV242-Pad18)") (class "Default")
      (node (ref "SV242") (pin "18") (pinfunction "18_18") (pintype "passive"))
    )
    (net (code "7073") (name "unconnected-(SV242-Pad19)") (class "Default")
      (node (ref "SV242") (pin "19") (pinfunction "19_19") (pintype "passive"))
    )
    (net (code "7074") (name "unconnected-(SV242-Pad20)") (class "Default")
      (node (ref "SV242") (pin "20") (pinfunction "20_20") (pintype "passive"))
    )
    (net (code "7075") (name "unconnected-(SV242-Pad21)") (class "Default")
      (node (ref "SV242") (pin "21") (pinfunction "21_21") (pintype "passive"))
    )
    (net (code "7076") (name "unconnected-(SV242-Pad22)") (class "Default")
      (node (ref "SV242") (pin "22") (pinfunction "22_22") (pintype "passive"))
    )
    (net (code "7077") (name "unconnected-(SV242-Pad23)") (class "Default")
      (node (ref "SV242") (pin "23") (pinfunction "23_23") (pintype "passive"))
    )
    (net (code "7078") (name "unconnected-(SV242-Pad24)") (class "Default")
      (node (ref "SV242") (pin "24") (pinfunction "24_24") (pintype "passive"))
    )
    (net (code "7079") (name "unconnected-(SV242-Pad25)") (class "Default")
      (node (ref "SV242") (pin "25") (pinfunction "25_25") (pintype "passive"))
    )
    (net (code "7080") (name "unconnected-(SV242-Pad26)") (class "Default")
      (node (ref "SV242") (pin "26") (pinfunction "26_26") (pintype "passive"))
    )
    (net (code "7081") (name "unconnected-(SV242-Pad27)") (class "Default")
      (node (ref "SV242") (pin "27") (pinfunction "27_27") (pintype "passive"))
    )
    (net (code "7082") (name "unconnected-(SV242-Pad28)") (class "Default")
      (node (ref "SV242") (pin "28") (pinfunction "28_28") (pintype "passive"))
    )
    (net (code "7083") (name "unconnected-(SV242-Pad29)") (class "Default")
      (node (ref "SV242") (pin "29") (pinfunction "29_29") (pintype "passive"))
    )
    (net (code "7084") (name "unconnected-(SV242-Pad30)") (class "Default")
      (node (ref "SV242") (pin "30") (pinfunction "30_30") (pintype "passive"))
    )
    (net (code "7085") (name "unconnected-(SV242-Pad31)") (class "Default")
      (node (ref "SV242") (pin "31") (pinfunction "31_31") (pintype "passive"))
    )
    (net (code "7086") (name "unconnected-(SV242-Pad32)") (class "Default")
      (node (ref "SV242") (pin "32") (pinfunction "32_32") (pintype "passive"))
    )
    (net (code "7087") (name "unconnected-(SV242-Pad33)") (class "Default")
      (node (ref "SV242") (pin "33") (pinfunction "33_33") (pintype "passive"))
    )
    (net (code "7088") (name "unconnected-(SV242-Pad34)") (class "Default")
      (node (ref "SV242") (pin "34") (pinfunction "34_34") (pintype "passive"))
    )
    (net (code "7089") (name "unconnected-(SV242-Pad35)") (class "Default")
      (node (ref "SV242") (pin "35") (pinfunction "35_35") (pintype "passive"))
    )
    (net (code "7090") (name "unconnected-(SV242-Pad36)") (class "Default")
      (node (ref "SV242") (pin "36") (pinfunction "36_36") (pintype "passive"))
    )
    (net (code "7091") (name "unconnected-(SV242-Pad37)") (class "Default")
      (node (ref "SV242") (pin "37") (pinfunction "37_37") (pintype "passive"))
    )
    (net (code "7092") (name "unconnected-(SV242-Pad38)") (class "Default")
      (node (ref "SV242") (pin "38") (pinfunction "38_38") (pintype "passive"))
    )
    (net (code "7093") (name "unconnected-(SV242-Pad39)") (class "Default")
      (node (ref "SV242") (pin "39") (pinfunction "39_39") (pintype "passive"))
    )
    (net (code "7094") (name "unconnected-(SV242-Pad40)") (class "Default")
      (node (ref "SV242") (pin "40") (pinfunction "40_40") (pintype "passive"))
    )
    (net (code "7095") (name "unconnected-(SV243-Pad1)") (class "Default")
      (node (ref "SV243") (pin "1") (pinfunction "1_1") (pintype "passive"))
    )
    (net (code "7096") (name "unconnected-(SV243-Pad2)") (class "Default")
      (node (ref "SV243") (pin "2") (pinfunction "2_2") (pintype "passive"))
    )
    (net (code "7097") (name "unconnected-(SV243-Pad3)") (class "Default")
      (node (ref "SV243") (pin "3") (pinfunction "3_3") (pintype "passive"))
    )
    (net (code "7098") (name "unconnected-(SV243-Pad4)") (class "Default")
      (node (ref "SV243") (pin "4") (pinfunction "4_4") (pintype "passive"))
    )
    (net (code "7099") (name "unconnected-(SV243-Pad5)") (class "Default")
      (node (ref "SV243") (pin "5") (pinfunction "5_5") (pintype "passive"))
    )
    (net (code "7100") (name "unconnected-(SV243-Pad6)") (class "Default")
      (node (ref "SV243") (pin "6") (pinfunction "6_6") (pintype "passive"))
    )
    (net (code "7101") (name "unconnected-(SV243-Pad7)") (class "Default")
      (node (ref "SV243") (pin "7") (pinfunction "7_7") (pintype "passive"))
    )
    (net (code "7102") (name "unconnected-(SV243-Pad8)") (class "Default")
      (node (ref "SV243") (pin "8") (pinfunction "8_8") (pintype "passive"))
    )
    (net (code "7103") (name "unconnected-(SV243-Pad9)") (class "Default")
      (node (ref "SV243") (pin "9") (pinfunction "9_9") (pintype "passive"))
    )
    (net (code "7104") (name "unconnected-(SV243-Pad10)") (class "Default")
      (node (ref "SV243") (pin "10") (pinfunction "10_10") (pintype "passive"))
    )
    (net (code "7105") (name "unconnected-(SV243-Pad11)") (class "Default")
      (node (ref "SV243") (pin "11") (pinfunction "11_11") (pintype "passive"))
    )
    (net (code "7106") (name "unconnected-(SV243-Pad12)") (class "Default")
      (node (ref "SV243") (pin "12") (pinfunction "12_12") (pintype "passive"))
    )
    (net (code "7107") (name "unconnected-(SV243-Pad13)") (class "Default")
      (node (ref "SV243") (pin "13") (pinfunction "13_13") (pintype "passive"))
    )
    (net (code "7108") (name "unconnected-(SV243-Pad14)") (class "Default")
      (node (ref "SV243") (pin "14") (pinfunction "14_14") (pintype "passive"))
    )
    (net (code "7109") (name "unconnected-(SV243-Pad15)") (class "Default")
      (node (ref "SV243") (pin "15") (pinfunction "15_15") (pintype "passive"))
    )
    (net (code "7110") (name "unconnected-(SV243-Pad16)") (class "Default")
      (node (ref "SV243") (pin "16") (pinfunction "16_16") (pintype "passive"))
    )
    (net (code "7111") (name "unconnected-(SV243-Pad17)") (class "Default")
      (node (ref "SV243") (pin "17") (pinfunction "17_17") (pintype "passive"))
    )
    (net (code "7112") (name "unconnected-(SV243-Pad18)") (class "Default")
      (node (ref "SV243") (pin "18") (pinfunction "18_18") (pintype "passive"))
    )
    (net (code "7113") (name "unconnected-(SV243-Pad19)") (class "Default")
      (node (ref "SV243") (pin "19") (pinfunction "19_19") (pintype "passive"))
    )
    (net (code "7114") (name "unconnected-(SV243-Pad20)") (class "Default")
      (node (ref "SV243") (pin "20") (pinfunction "20_20") (pintype "passive"))
    )
    (net (code "7115") (name "unconnected-(SV243-Pad21)") (class "Default")
      (node (ref "SV243") (pin "21") (pinfunction "21_21") (pintype "passive"))
    )
    (net (code "7116") (name "unconnected-(SV243-Pad22)") (class "Default")
      (node (ref "SV243") (pin "22") (pinfunction "22_22") (pintype "passive"))
    )
    (net (code "7117") (name "unconnected-(SV243-Pad23)") (class "Default")
      (node (ref "SV243") (pin "23") (pinfunction "23_23") (pintype "passive"))
    )
    (net (code "7118") (name "unconnected-(SV243-Pad24)") (class "Default")
      (node (ref "SV243") (pin "24") (pinfunction "24_24") (pintype "passive"))
    )
    (net (code "7119") (name "unconnected-(SV244-Pad1)") (class "Default")
      (node (ref "SV244") (pin "1") (pinfunction "1_1") (pintype "passive"))
    )
    (net (code "7120") (name "unconnected-(SV244-Pad2)") (class "Default")
      (node (ref "SV244") (pin "2") (pinfunction "2_2") (pintype "passive"))
    )
    (net (code "7121") (name "unconnected-(SV244-Pad3)") (class "Default")
      (node (ref "SV244") (pin "3") (pinfunction "3_3") (pintype "passive"))
    )
    (net (code "7122") (name "unconnected-(SV244-Pad4)") (class "Default")
      (node (ref "SV244") (pin "4") (pinfunction "4_4") (pintype "passive"))
    )
    (net (code "7123") (name "unconnected-(SV244-Pad5)") (class "Default")
      (node (ref "SV244") (pin "5") (pinfunction "5_5") (pintype "passive"))
    )
    (net (code "7124") (name "unconnected-(SV244-Pad6)") (class "Default")
      (node (ref "SV244") (pin "6") (pinfunction "6_6") (pintype "passive"))
    )
    (net (code "7125") (name "unconnected-(SV244-Pad7)") (class "Default")
      (node (ref "SV244") (pin "7") (pinfunction "7_7") (pintype "passive"))
    )
    (net (code "7126") (name "unconnected-(SV244-Pad8)") (class "Default")
      (node (ref "SV244") (pin "8") (pinfunction "8_8") (pintype "passive"))
    )
    (net (code "7127") (name "unconnected-(SV244-Pad9)") (class "Default")
      (node (ref "SV244") (pin "9") (pinfunction "9_9") (pintype "passive"))
    )
    (net (code "7128") (name "unconnected-(SV244-Pad10)") (class "Default")
      (node (ref "SV244") (pin "10") (pinfunction "10_10") (pintype "passive"))
    )
    (net (code "7129") (name "unconnected-(SV244-Pad11)") (class "Default")
      (node (ref "SV244") (pin "11") (pinfunction "11_11") (pintype "passive"))
    )
    (net (code "7130") (name "unconnected-(SV244-Pad12)") (class "Default")
      (node (ref "SV244") (pin "12") (pinfunction "12_12") (pintype "passive"))
    )
    (net (code "7131") (name "unconnected-(SV244-Pad13)") (class "Default")
      (node (ref "SV244") (pin "13") (pinfunction "13_13") (pintype "passive"))
    )
    (net (code "7132") (name "unconnected-(SV244-Pad14)") (class "Default")
      (node (ref "SV244") (pin "14") (pinfunction "14_14") (pintype "passive"))
    )
    (net (code "7133") (name "unconnected-(SV244-Pad15)") (class "Default")
      (node (ref "SV244") (pin "15") (pinfunction "15_15") (pintype "passive"))
    )
    (net (code "7134") (name "unconnected-(SV244-Pad16)") (class "Default")
      (node (ref "SV244") (pin "16") (pinfunction "16_16") (pintype "passive"))
    )
    (net (code "7135") (name "unconnected-(SV244-Pad17)") (class "Default")
      (node (ref "SV244") (pin "17") (pinfunction "17_17") (pintype "passive"))
    )
    (net (code "7136") (name "unconnected-(SV244-Pad18)") (class "Default")
      (node (ref "SV244") (pin "18") (pinfunction "18_18") (pintype "passive"))
    )
    (net (code "7137") (name "unconnected-(SV244-Pad19)") (class "Default")
      (node (ref "SV244") (pin "19") (pinfunction "19_19") (pintype "passive"))
    )
    (net (code "7138") (name "unconnected-(SV244-Pad20)") (class "Default")
      (node (ref "SV244") (pin "20") (pinfunction "20_20") (pintype "passive"))
    )
    (net (code "7139") (name "unconnected-(SV244-Pad21)") (class "Default")
      (node (ref "SV244") (pin "21") (pinfunction "21_21") (pintype "passive"))
    )
    (net (code "7140") (name "unconnected-(SV244-Pad22)") (class "Default")
      (node (ref "SV244") (pin "22") (pinfunction "22_22") (pintype "passive"))
    )
    (net (code "7141") (name "unconnected-(SV244-Pad23)") (class "Default")
      (node (ref "SV244") (pin "23") (pinfunction "23_23") (pintype "passive"))
    )
    (net (code "7142") (name "unconnected-(SV244-Pad24)") (class "Default")
      (node (ref "SV244") (pin "24") (pinfunction "24_24") (pintype "passive"))
    )
    (net (code "7143") (name "unconnected-(SV245-Pad1)") (class "Default")
      (node (ref "SV245") (pin "1") (pinfunction "1_1") (pintype "passive"))
    )
    (net (code "7144") (name "unconnected-(SV245-Pad2)") (class "Default")
      (node (ref "SV245") (pin "2") (pinfunction "2_2") (pintype "passive"))
    )
    (net (code "7145") (name "unconnected-(SV245-Pad3)") (class "Default")
      (node (ref "SV245") (pin "3") (pinfunction "3_3") (pintype "passive"))
    )
    (net (code "7146") (name "unconnected-(SV245-Pad4)") (class "Default")
      (node (ref "SV245") (pin "4") (pinfunction "4_4") (pintype "passive"))
    )
    (net (code "7147") (name "unconnected-(SV245-Pad5)") (class "Default")
      (node (ref "SV245") (pin "5") (pinfunction "5_5") (pintype "passive"))
    )
    (net (code "7148") (name "unconnected-(SV245-Pad6)") (class "Default")
      (node (ref "SV245") (pin "6") (pinfunction "6_6") (pintype "passive"))
    )
    (net (code "7149") (name "unconnected-(SV245-Pad7)") (class "Default")
      (node (ref "SV245") (pin "7") (pinfunction "7_7") (pintype "passive"))
    )
    (net (code "7150") (name "unconnected-(SV245-Pad8)") (class "Default")
      (node (ref "SV245") (pin "8") (pinfunction "8_8") (pintype "passive"))
    )
    (net (code "7151") (name "unconnected-(SV245-Pad9)") (class "Default")
      (node (ref "SV245") (pin "9") (pinfunction "9_9") (pintype "passive"))
    )
    (net (code "7152") (name "unconnected-(SV245-Pad10)") (class "Default")
      (node (ref "SV245") (pin "10") (pinfunction "10_10") (pintype "passive"))
    )
    (net (code "7153") (name "unconnected-(SV245-Pad11)") (class "Default")
      (node (ref "SV245") (pin "11") (pinfunction "11_11") (pintype "passive"))
    )
    (net (code "7154") (name "unconnected-(SV245-Pad12)") (class "Default")
      (node (ref "SV245") (pin "12") (pinfunction "12_12") (pintype "passive"))
    )
    (net (code "7155") (name "unconnected-(SV245-Pad13)") (class "Default")
      (node (ref "SV245") (pin "13") (pinfunction "13_13") (pintype "passive"))
    )
    (net (code "7156") (name "unconnected-(SV245-Pad14)") (class "Default")
      (node (ref "SV245") (pin "14") (pinfunction "14_14") (pintype "passive"))
    )
    (net (code "7157") (name "unconnected-(SV245-Pad15)") (class "Default")
      (node (ref "SV245") (pin "15") (pinfunction "15_15") (pintype "passive"))
    )
    (net (code "7158") (name "unconnected-(SV245-Pad16)") (class "Default")
      (node (ref "SV245") (pin "16") (pinfunction "16_16") (pintype "passive"))
    )
    (net (code "7159") (name "unconnected-(SV245-Pad17)") (class "Default")
      (node (ref "SV245") (pin "17") (pinfunction "17_17") (pintype "passive"))
    )
    (net (code "7160") (name "unconnected-(SV245-Pad18)") (class "Default")
      (node (ref "SV245") (pin "18") (pinfunction "18_18") (pintype "passive"))
    )
    (net (code "7161") (name "unconnected-(SV245-Pad19)") (class "Default")
      (node (ref "SV245") (pin "19") (pinfunction "19_19") (pintype "passive"))
    )
    (net (code "7162") (name "unconnected-(SV245-Pad20)") (class "Default")
      (node (ref "SV245") (pin "20") (pinfunction "20_20") (pintype "passive"))
    )
    (net (code "7163") (name "unconnected-(SV245-Pad21)") (class "Default")
      (node (ref "SV245") (pin "21") (pinfunction "21_21") (pintype "passive"))
    )
    (net (code "7164") (name "unconnected-(SV245-Pad22)") (class "Default")
      (node (ref "SV245") (pin "22") (pinfunction "22_22") (pintype "passive"))
    )
    (net (code "7165") (name "unconnected-(SV245-Pad23)") (class "Default")
      (node (ref "SV245") (pin "23") (pinfunction "23_23") (pintype "passive"))
    )
    (net (code "7166") (name "unconnected-(SV245-Pad24)") (class "Default")
      (node (ref "SV245") (pin "24") (pinfunction "24_24") (pintype "passive"))
    )
    (net (code "7167") (name "unconnected-(SV246-Pad1)") (class "Default")
      (node (ref "SV246") (pin "1") (pinfunction "1_1") (pintype "passive"))
    )
    (net (code "7168") (name "unconnected-(SV246-Pad2)") (class "Default")
      (node (ref "SV246") (pin "2") (pinfunction "2_2") (pintype "passive"))
    )
    (net (code "7169") (name "unconnected-(SV246-Pad3)") (class "Default")
      (node (ref "SV246") (pin "3") (pinfunction "3_3") (pintype "passive"))
    )
    (net (code "7170") (name "unconnected-(SV246-Pad4)") (class "Default")
      (node (ref "SV246") (pin "4") (pinfunction "4_4") (pintype "passive"))
    )
    (net (code "7171") (name "unconnected-(SV246-Pad5)") (class "Default")
      (node (ref "SV246") (pin "5") (pinfunction "5_5") (pintype "passive"))
    )
    (net (code "7172") (name "unconnected-(SV246-Pad6)") (class "Default")
      (node (ref "SV246") (pin "6") (pinfunction "6_6") (pintype "passive"))
    )
    (net (code "7173") (name "unconnected-(SV246-Pad7)") (class "Default")
      (node (ref "SV246") (pin "7") (pinfunction "7_7") (pintype "passive"))
    )
    (net (code "7174") (name "unconnected-(SV246-Pad8)") (class "Default")
      (node (ref "SV246") (pin "8") (pinfunction "8_8") (pintype "passive"))
    )
    (net (code "7175") (name "unconnected-(SV246-Pad9)") (class "Default")
      (node (ref "SV246") (pin "9") (pinfunction "9_9") (pintype "passive"))
    )
    (net (code "7176") (name "unconnected-(SV246-Pad10)") (class "Default")
      (node (ref "SV246") (pin "10") (pinfunction "10_10") (pintype "passive"))
    )
    (net (code "7177") (name "unconnected-(SV246-Pad11)") (class "Default")
      (node (ref "SV246") (pin "11") (pinfunction "11_11") (pintype "passive"))
    )
    (net (code "7178") (name "unconnected-(SV246-Pad12)") (class "Default")
      (node (ref "SV246") (pin "12") (pinfunction "12_12") (pintype "passive"))
    )
    (net (code "7179") (name "unconnected-(SV246-Pad13)") (class "Default")
      (node (ref "SV246") (pin "13") (pinfunction "13_13") (pintype "passive"))
    )
    (net (code "7180") (name "unconnected-(SV246-Pad14)") (class "Default")
      (node (ref "SV246") (pin "14") (pinfunction "14_14") (pintype "passive"))
    )
    (net (code "7181") (name "unconnected-(SV246-Pad15)") (class "Default")
      (node (ref "SV246") (pin "15") (pinfunction "15_15") (pintype "passive"))
    )
    (net (code "7182") (name "unconnected-(SV246-Pad16)") (class "Default")
      (node (ref "SV246") (pin "16") (pinfunction "16_16") (pintype "passive"))
    )
    (net (code "7183") (name "unconnected-(SV246-Pad17)") (class "Default")
      (node (ref "SV246") (pin "17") (pinfunction "17_17") (pintype "passive"))
    )
    (net (code "7184") (name "unconnected-(SV246-Pad18)") (class "Default")
      (node (ref "SV246") (pin "18") (pinfunction "18_18") (pintype "passive"))
    )
    (net (code "7185") (name "unconnected-(SV246-Pad19)") (class "Default")
      (node (ref "SV246") (pin "19") (pinfunction "19_19") (pintype "passive"))
    )
    (net (code "7186") (name "unconnected-(SV246-Pad20)") (class "Default")
      (node (ref "SV246") (pin "20") (pinfunction "20_20") (pintype "passive"))
    )
    (net (code "7187") (name "unconnected-(SV246-Pad21)") (class "Default")
      (node (ref "SV246") (pin "21") (pinfunction "21_21") (pintype "passive"))
    )
    (net (code "7188") (name "unconnected-(SV246-Pad22)") (class "Default")
      (node (ref "SV246") (pin "22") (pinfunction "22_22") (pintype "passive"))
    )
    (net (code "7189") (name "unconnected-(SV246-Pad23)") (class "Default")
      (node (ref "SV246") (pin "23") (pinfunction "23_23") (pintype "passive"))
    )
    (net (code "7190") (name "unconnected-(SV246-Pad24)") (class "Default")
      (node (ref "SV246") (pin "24") (pinfunction "24_24") (pintype "passive"))
    )
    (net (code "7191") (name "unconnected-(SV247-Pad1)") (class "Default")
      (node (ref "SV247") (pin "1") (pinfunction "1_1") (pintype "passive"))
    )
    (net (code "7192") (name "unconnected-(SV247-Pad2)") (class "Default")
      (node (ref "SV247") (pin "2") (pinfunction "2_2") (pintype "passive"))
    )
    (net (code "7193") (name "unconnected-(SV247-Pad3)") (class "Default")
      (node (ref "SV247") (pin "3") (pinfunction "3_3") (pintype "passive"))
    )
    (net (code "7194") (name "unconnected-(SV247-Pad4)") (class "Default")
      (node (ref "SV247") (pin "4") (pinfunction "4_4") (pintype "passive"))
    )
    (net (code "7195") (name "unconnected-(SV247-Pad5)") (class "Default")
      (node (ref "SV247") (pin "5") (pinfunction "5_5") (pintype "passive"))
    )
    (net (code "7196") (name "unconnected-(SV247-Pad6)") (class "Default")
      (node (ref "SV247") (pin "6") (pinfunction "6_6") (pintype "passive"))
    )
    (net (code "7197") (name "unconnected-(SV248-Pad1)") (class "Default")
      (node (ref "SV248") (pin "1") (pinfunction "1_1") (pintype "passive"))
    )
    (net (code "7198") (name "unconnected-(SV248-Pad2)") (class "Default")
      (node (ref "SV248") (pin "2") (pinfunction "2_2") (pintype "passive"))
    )
    (net (code "7199") (name "unconnected-(SV248-Pad3)") (class "Default")
      (node (ref "SV248") (pin "3") (pinfunction "3_3") (pintype "passive"))
    )
    (net (code "7200") (name "unconnected-(SV248-Pad4)") (class "Default")
      (node (ref "SV248") (pin "4") (pinfunction "4_4") (pintype "passive"))
    )
    (net (code "7201") (name "unconnected-(SV248-Pad5)") (class "Default")
      (node (ref "SV248") (pin "5") (pinfunction "5_5") (pintype "passive"))
    )
    (net (code "7202") (name "unconnected-(SV248-Pad6)") (class "Default")
      (node (ref "SV248") (pin "6") (pinfunction "6_6") (pintype "passive"))
    )
    (net (code "7203") (name "unconnected-(SV249-Pad1)") (class "Default")
      (node (ref "SV249") (pin "1") (pinfunction "1_1") (pintype "passive"))
    )
    (net (code "7204") (name "unconnected-(SV249-Pad2)") (class "Default")
      (node (ref "SV249") (pin "2") (pinfunction "2_2") (pintype "passive"))
    )
    (net (code "7205") (name "unconnected-(SV249-Pad3)") (class "Default")
      (node (ref "SV249") (pin "3") (pinfunction "3_3") (pintype "passive"))
    )
    (net (code "7206") (name "unconnected-(SV249-Pad4)") (class "Default")
      (node (ref "SV249") (pin "4") (pinfunction "4_4") (pintype "passive"))
    )
    (net (code "7207") (name "unconnected-(SV249-Pad5)") (class "Default")
      (node (ref "SV249") (pin "5") (pinfunction "5_5") (pintype "passive"))
    )
    (net (code "7208") (name "unconnected-(SV249-Pad6)") (class "Default")
      (node (ref "SV249") (pin "6") (pinfunction "6_6") (pintype "passive"))
    )
    (net (code "7209") (name "unconnected-(SV250-Pad1)") (class "Default")
      (node (ref "SV250") (pin "1") (pinfunction "1_1") (pintype "passive"))
    )
    (net (code "7210") (name "unconnected-(SV250-Pad2)") (class "Default")
      (node (ref "SV250") (pin "2") (pinfunction "2_2") (pintype "passive"))
    )
    (net (code "7211") (name "unconnected-(SV250-Pad3)") (class "Default")
      (node (ref "SV250") (pin "3") (pinfunction "3_3") (pintype "passive"))
    )
    (net (code "7212") (name "unconnected-(SV250-Pad4)") (class "Default")
      (node (ref "SV250") (pin "4") (pinfunction "4_4") (pintype "passive"))
    )
    (net (code "7213") (name "unconnected-(SV250-Pad5)") (class "Default")
      (node (ref "SV250") (pin "5") (pinfunction "5_5") (pintype "passive"))
    )
    (net (code "7214") (name "unconnected-(SV250-Pad6)") (class "Default")
      (node (ref "SV250") (pin "6") (pinfunction "6_6") (pintype "passive"))
    )
    (net (code "7215") (name "unconnected-(SV251-Pad1)") (class "Default")
      (node (ref "SV251") (pin "1") (pinfunction "1_1") (pintype "passive"))
    )
    (net (code "7216") (name "unconnected-(SV251-Pad2)") (class "Default")
      (node (ref "SV251") (pin "2") (pinfunction "2_2") (pintype "passive"))
    )
    (net (code "7217") (name "unconnected-(SV251-Pad3)") (class "Default")
      (node (ref "SV251") (pin "3") (pinfunction "3_3") (pintype "passive"))
    )
    (net (code "7218") (name "unconnected-(SV251-Pad4)") (class "Default")
      (node (ref "SV251") (pin "4") (pinfunction "4_4") (pintype "passive"))
    )
    (net (code "7219") (name "unconnected-(SV251-Pad5)") (class "Default")
      (node (ref "SV251") (pin "5") (pinfunction "5_5") (pintype "passive"))
    )
    (net (code "7220") (name "unconnected-(SV251-Pad6)") (class "Default")
      (node (ref "SV251") (pin "6") (pinfunction "6_6") (pintype "passive"))
    )
    (net (code "7221") (name "unconnected-(SV252-Pad1)") (class "Default")
      (node (ref "SV252") (pin "1") (pinfunction "1_1") (pintype "passive"))
    )
    (net (code "7222") (name "unconnected-(SV252-Pad2)") (class "Default")
      (node (ref "SV252") (pin "2") (pinfunction "2_2") (pintype "passive"))
    )
    (net (code "7223") (name "unconnected-(SV252-Pad3)") (class "Default")
      (node (ref "SV252") (pin "3") (pinfunction "3_3") (pintype "passive"))
    )
    (net (code "7224") (name "unconnected-(SV252-Pad4)") (class "Default")
      (node (ref "SV252") (pin "4") (pinfunction "4_4") (pintype "passive"))
    )
    (net (code "7225") (name "unconnected-(SV252-Pad5)") (class "Default")
      (node (ref "SV252") (pin "5") (pinfunction "5_5") (pintype "passive"))
    )
    (net (code "7226") (name "unconnected-(SV252-Pad6)") (class "Default")
      (node (ref "SV252") (pin "6") (pinfunction "6_6") (pintype "passive"))
    )
    (net (code "7227") (name "unconnected-(SV253-Pad1)") (class "Default")
      (node (ref "SV253") (pin "1") (pinfunction "1_1") (pintype "passive"))
    )
    (net (code "7228") (name "unconnected-(SV253-Pad2)") (class "Default")
      (node (ref "SV253") (pin "2") (pinfunction "2_2") (pintype "passive"))
    )
    (net (code "7229") (name "unconnected-(SV253-Pad3)") (class "Default")
      (node (ref "SV253") (pin "3") (pinfunction "3_3") (pintype "passive"))
    )
    (net (code "7230") (name "unconnected-(SV253-Pad4)") (class "Default")
      (node (ref "SV253") (pin "4") (pinfunction "4_4") (pintype "passive"))
    )
    (net (code "7231") (name "unconnected-(SV253-Pad5)") (class "Default")
      (node (ref "SV253") (pin "5") (pinfunction "5_5") (pintype "passive"))
    )
    (net (code "7232") (name "unconnected-(SV253-Pad6)") (class "Default")
      (node (ref "SV253") (pin "6") (pinfunction "6_6") (pintype "passive"))
    )
    (net (code "7233") (name "unconnected-(SV254-Pad1)") (class "Default")
      (node (ref "SV254") (pin "1") (pinfunction "1_1") (pintype "passive"))
    )
    (net (code "7234") (name "unconnected-(SV254-Pad2)") (class "Default")
      (node (ref "SV254") (pin "2") (pinfunction "2_2") (pintype "passive"))
    )
    (net (code "7235") (name "unconnected-(SV254-Pad3)") (class "Default")
      (node (ref "SV254") (pin "3") (pinfunction "3_3") (pintype "passive"))
    )
    (net (code "7236") (name "unconnected-(SV254-Pad4)") (class "Default")
      (node (ref "SV254") (pin "4") (pinfunction "4_4") (pintype "passive"))
    )
    (net (code "7237") (name "unconnected-(SV254-Pad5)") (class "Default")
      (node (ref "SV254") (pin "5") (pinfunction "5_5") (pintype "passive"))
    )
    (net (code "7238") (name "unconnected-(SV254-Pad6)") (class "Default")
      (node (ref "SV254") (pin "6") (pinfunction "6_6") (pintype "passive"))
    )
    (net (code "7239") (name "unconnected-(SV255-Pad1)") (class "Default")
      (node (ref "SV255") (pin "1") (pinfunction "1_1") (pintype "passive"))
    )
    (net (code "7240") (name "unconnected-(SV255-Pad2)") (class "Default")
      (node (ref "SV255") (pin "2") (pinfunction "2_2") (pintype "passive"))
    )
    (net (code "7241") (name "unconnected-(SV255-Pad3)") (class "Default")
      (node (ref "SV255") (pin "3") (pinfunction "3_3") (pintype "passive"))
    )
    (net (code "7242") (name "unconnected-(SV255-Pad4)") (class "Default")
      (node (ref "SV255") (pin "4") (pinfunction "4_4") (pintype "passive"))
    )
    (net (code "7243") (name "unconnected-(SV255-Pad5)") (class "Default")
      (node (ref "SV255") (pin "5") (pinfunction "5_5") (pintype "passive"))
    )
    (net (code "7244") (name "unconnected-(SV255-Pad6)") (class "Default")
      (node (ref "SV255") (pin "6") (pinfunction "6_6") (pintype "passive"))
    )
    (net (code "7245") (name "unconnected-(SV256-Pad1)") (class "Default")
      (node (ref "SV256") (pin "1") (pinfunction "1_1") (pintype "passive"))
    )
    (net (code "7246") (name "unconnected-(SV256-Pad2)") (class "Default")
      (node (ref "SV256") (pin "2") (pinfunction "2_2") (pintype "passive"))
    )
    (net (code "7247") (name "unconnected-(SV256-Pad3)") (class "Default")
      (node (ref "SV256") (pin "3") (pinfunction "3_3") (pintype "passive"))
    )
    (net (code "7248") (name "unconnected-(SV256-Pad4)") (class "Default")
      (node (ref "SV256") (pin "4") (pinfunction "4_4") (pintype "passive"))
    )
    (net (code "7249") (name "unconnected-(SV256-Pad5)") (class "Default")
      (node (ref "SV256") (pin "5") (pinfunction "5_5") (pintype "passive"))
    )
    (net (code "7250") (name "unconnected-(SV256-Pad6)") (class "Default")
      (node (ref "SV256") (pin "6") (pinfunction "6_6") (pintype "passive"))
    )
    (net (code "7251") (name "unconnected-(SV257-Pad1)") (class "Default")
      (node (ref "SV257") (pin "1") (pinfunction "1_1") (pintype "passive"))
    )
    (net (code "7252") (name "unconnected-(SV257-Pad2)") (class "Default")
      (node (ref "SV257") (pin "2") (pinfunction "2_2") (pintype "passive"))
    )
    (net (code "7253") (name "unconnected-(SV257-Pad3)") (class "Default")
      (node (ref "SV257") (pin "3") (pinfunction "3_3") (pintype "passive"))
    )
    (net (code "7254") (name "unconnected-(SV257-Pad4)") (class "Default")
      (node (ref "SV257") (pin "4") (pinfunction "4_4") (pintype "passive"))
    )
    (net (code "7255") (name "unconnected-(SV257-Pad5)") (class "Default")
      (node (ref "SV257") (pin "5") (pinfunction "5_5") (pintype "passive"))
    )
    (net (code "7256") (name "unconnected-(SV257-Pad6)") (class "Default")
      (node (ref "SV257") (pin "6") (pinfunction "6_6") (pintype "passive"))
    )
    (net (code "7257") (name "unconnected-(SV258-Pad1)") (class "Default")
      (node (ref "SV258") (pin "1") (pinfunction "1_1") (pintype "passive"))
    )
    (net (code "7258") (name "unconnected-(SV258-Pad2)") (class "Default")
      (node (ref "SV258") (pin "2") (pinfunction "2_2") (pintype "passive"))
    )
    (net (code "7259") (name "unconnected-(SV258-Pad3)") (class "Default")
      (node (ref "SV258") (pin "3") (pinfunction "3_3") (pintype "passive"))
    )
    (net (code "7260") (name "unconnected-(SV258-Pad4)") (class "Default")
      (node (ref "SV258") (pin "4") (pinfunction "4_4") (pintype "passive"))
    )
    (net (code "7261") (name "unconnected-(SV258-Pad5)") (class "Default")
      (node (ref "SV258") (pin "5") (pinfunction "5_5") (pintype "passive"))
    )
    (net (code "7262") (name "unconnected-(SV258-Pad6)") (class "Default")
      (node (ref "SV258") (pin "6") (pinfunction "6_6") (pintype "passive"))
    )
    (net (code "7263") (name "unconnected-(SV259-Pad1)") (class "Default")
      (node (ref "SV259") (pin "1") (pinfunction "1_1") (pintype "passive"))
    )
    (net (code "7264") (name "unconnected-(SV259-Pad2)") (class "Default")
      (node (ref "SV259") (pin "2") (pinfunction "2_2") (pintype "passive"))
    )
    (net (code "7265") (name "unconnected-(SV259-Pad3)") (class "Default")
      (node (ref "SV259") (pin "3") (pinfunction "3_3") (pintype "passive"))
    )
    (net (code "7266") (name "unconnected-(SV259-Pad4)") (class "Default")
      (node (ref "SV259") (pin "4") (pinfunction "4_4") (pintype "passive"))
    )
    (net (code "7267") (name "unconnected-(SV259-Pad5)") (class "Default")
      (node (ref "SV259") (pin "5") (pinfunction "5_5") (pintype "passive"))
    )
    (net (code "7268") (name "unconnected-(SV259-Pad6)") (class "Default")
      (node (ref "SV259") (pin "6") (pinfunction "6_6") (pintype "passive"))
    )
    (net (code "7269") (name "unconnected-(SV260-Pad1)") (class "Default")
      (node (ref "SV260") (pin "1") (pinfunction "1_1") (pintype "passive"))
    )
    (net (code "7270") (name "unconnected-(SV260-Pad2)") (class "Default")
      (node (ref "SV260") (pin "2") (pinfunction "2_2") (pintype "passive"))
    )
    (net (code "7271") (name "unconnected-(SV260-Pad3)") (class "Default")
      (node (ref "SV260") (pin "3") (pinfunction "3_3") (pintype "passive"))
    )
    (net (code "7272") (name "unconnected-(SV260-Pad4)") (class "Default")
      (node (ref "SV260") (pin "4") (pinfunction "4_4") (pintype "passive"))
    )
    (net (code "7273") (name "unconnected-(SV260-Pad5)") (class "Default")
      (node (ref "SV260") (pin "5") (pinfunction "5_5") (pintype "passive"))
    )
    (net (code "7274") (name "unconnected-(SV260-Pad6)") (class "Default")
      (node (ref "SV260") (pin "6") (pinfunction "6_6") (pintype "passive"))
    )
    (net (code "7275") (name "unconnected-(SV261-Pad1)") (class "Default")
      (node (ref "SV261") (pin "1") (pinfunction "1_1") (pintype "passive"))
    )
    (net (code "7276") (name "unconnected-(SV261-Pad2)") (class "Default")
      (node (ref "SV261") (pin "2") (pinfunction "2_2") (pintype "passive"))
    )
    (net (code "7277") (name "unconnected-(SV261-Pad3)") (class "Default")
      (node (ref "SV261") (pin "3") (pinfunction "3_3") (pintype "passive"))
    )
    (net (code "7278") (name "unconnected-(SV261-Pad4)") (class "Default")
      (node (ref "SV261") (pin "4") (pinfunction "4_4") (pintype "passive"))
    )
    (net (code "7279") (name "unconnected-(SV261-Pad5)") (class "Default")
      (node (ref "SV261") (pin "5") (pinfunction "5_5") (pintype "passive"))
    )
    (net (code "7280") (name "unconnected-(SV261-Pad6)") (class "Default")
      (node (ref "SV261") (pin "6") (pinfunction "6_6") (pintype "passive"))
    )
    (net (code "7281") (name "unconnected-(SV262-Pad1)") (class "Default")
      (node (ref "SV262") (pin "1") (pinfunction "1_1") (pintype "passive"))
    )
    (net (code "7282") (name "unconnected-(SV262-Pad2)") (class "Default")
      (node (ref "SV262") (pin "2") (pinfunction "2_2") (pintype "passive"))
    )
    (net (code "7283") (name "unconnected-(SV262-Pad3)") (class "Default")
      (node (ref "SV262") (pin "3") (pinfunction "3_3") (pintype "passive"))
    )
    (net (code "7284") (name "unconnected-(SV262-Pad4)") (class "Default")
      (node (ref "SV262") (pin "4") (pinfunction "4_4") (pintype "passive"))
    )
    (net (code "7285") (name "unconnected-(SV262-Pad5)") (class "Default")
      (node (ref "SV262") (pin "5") (pinfunction "5_5") (pintype "passive"))
    )
    (net (code "7286") (name "unconnected-(SV262-Pad6)") (class "Default")
      (node (ref "SV262") (pin "6") (pinfunction "6_6") (pintype "passive"))
    )
  )
)
